# hanover-7320-20-01.net
KiCad netlist of a schematic drawn in EAGLE
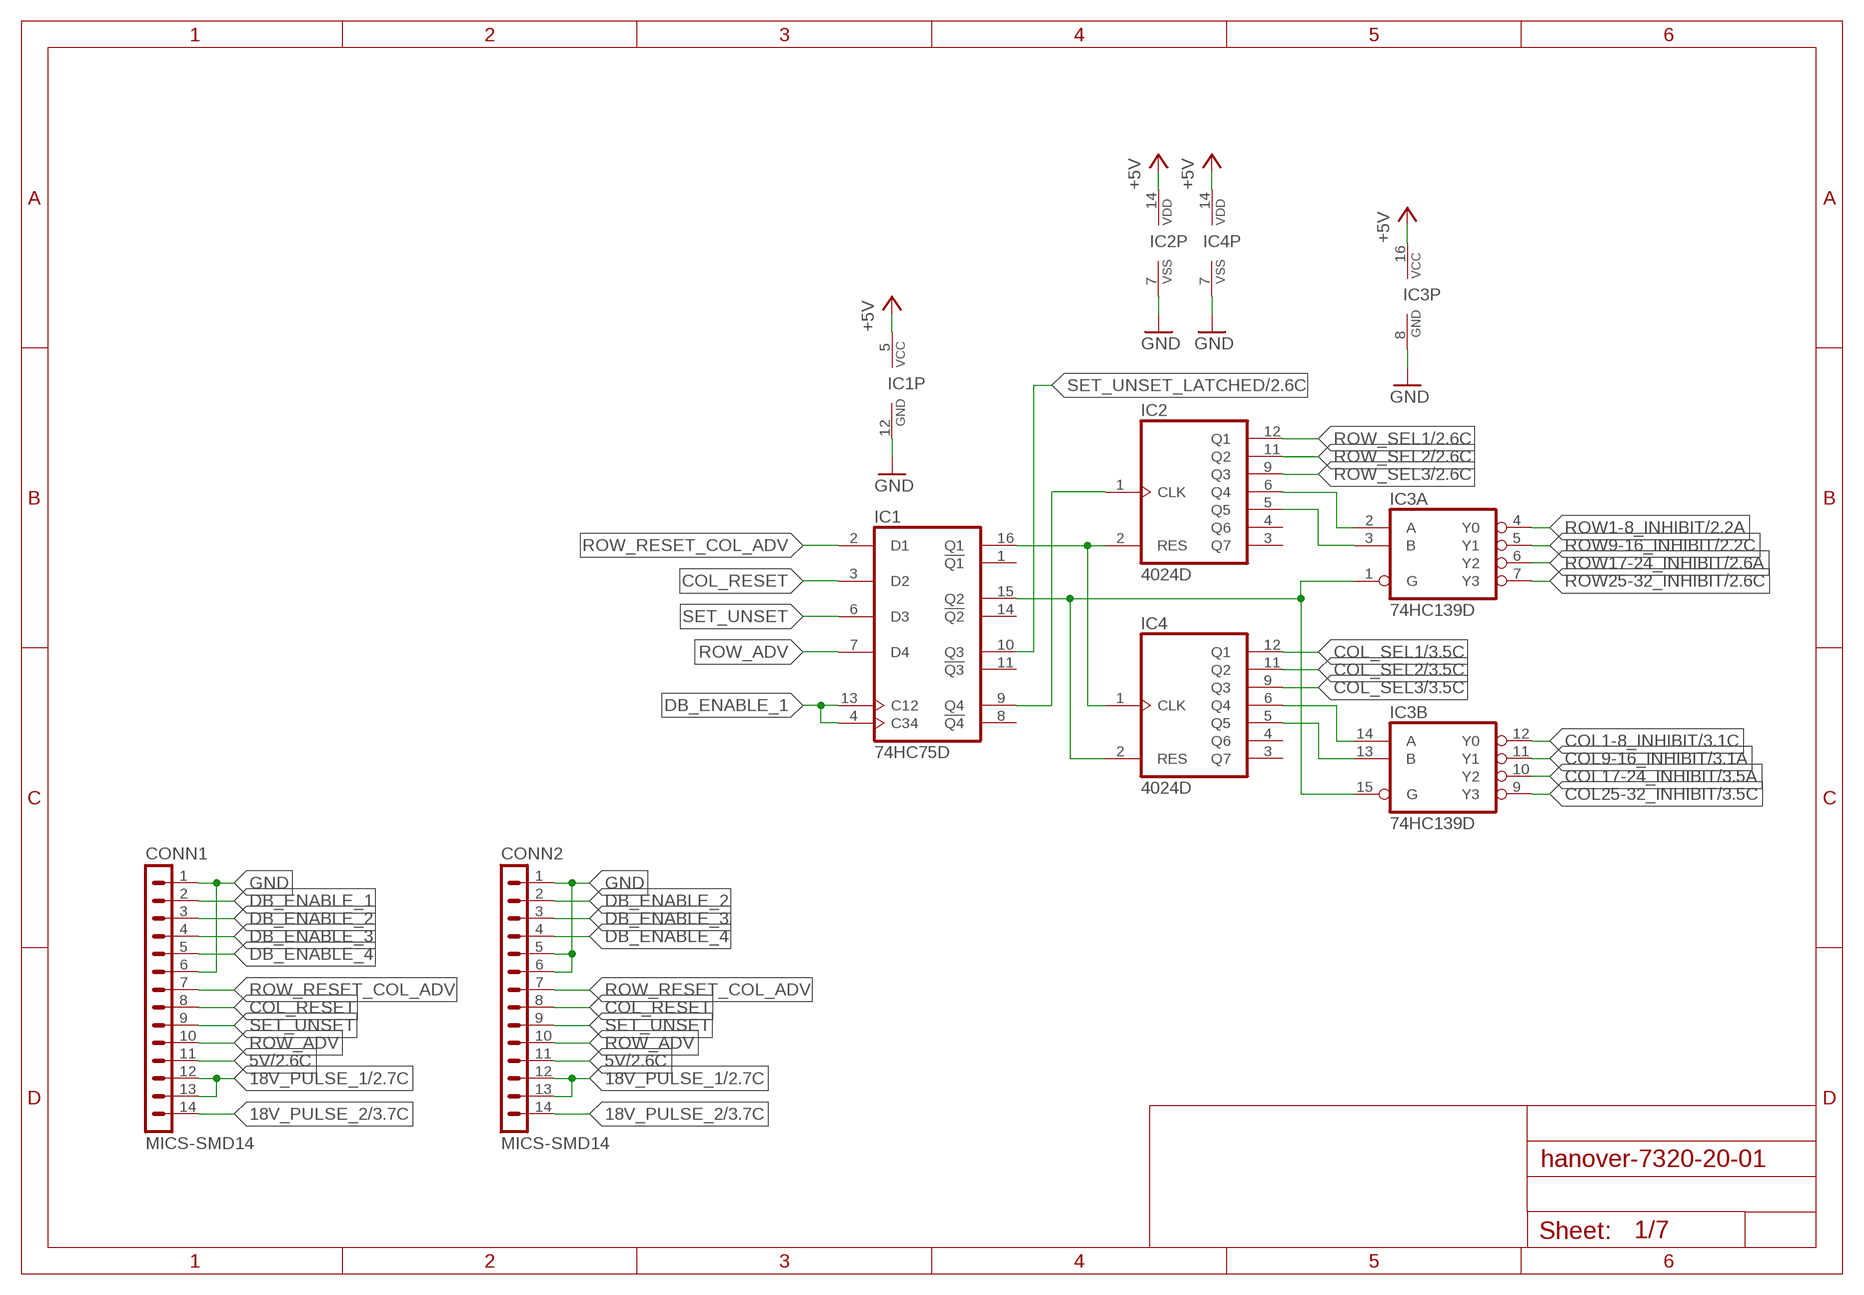
[diagram p0: schematic, sheet 1]
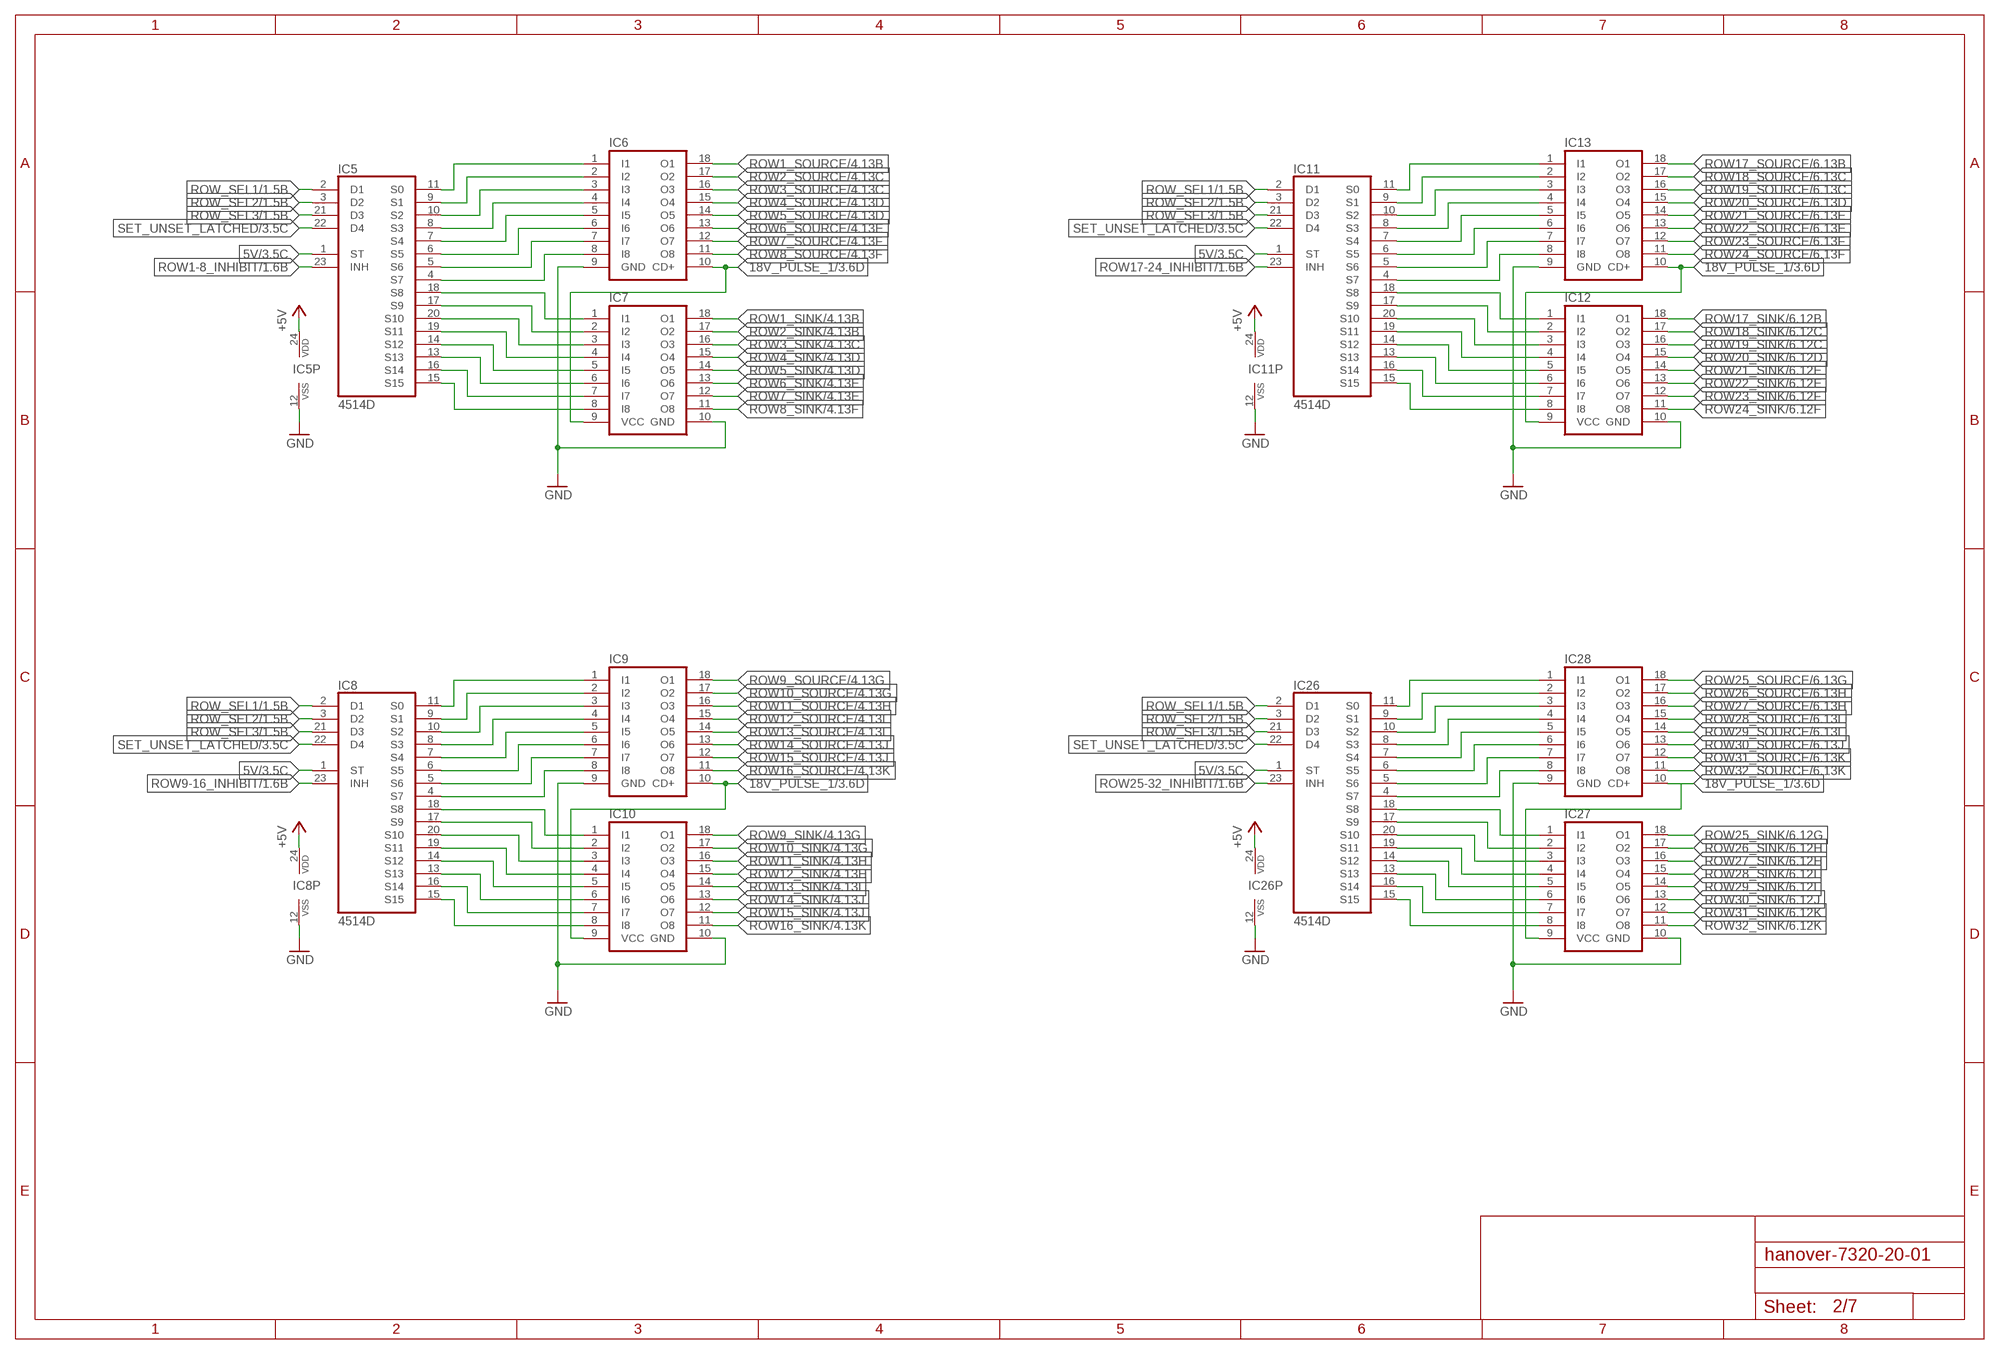
[diagram p1: schematic, sheet 2]
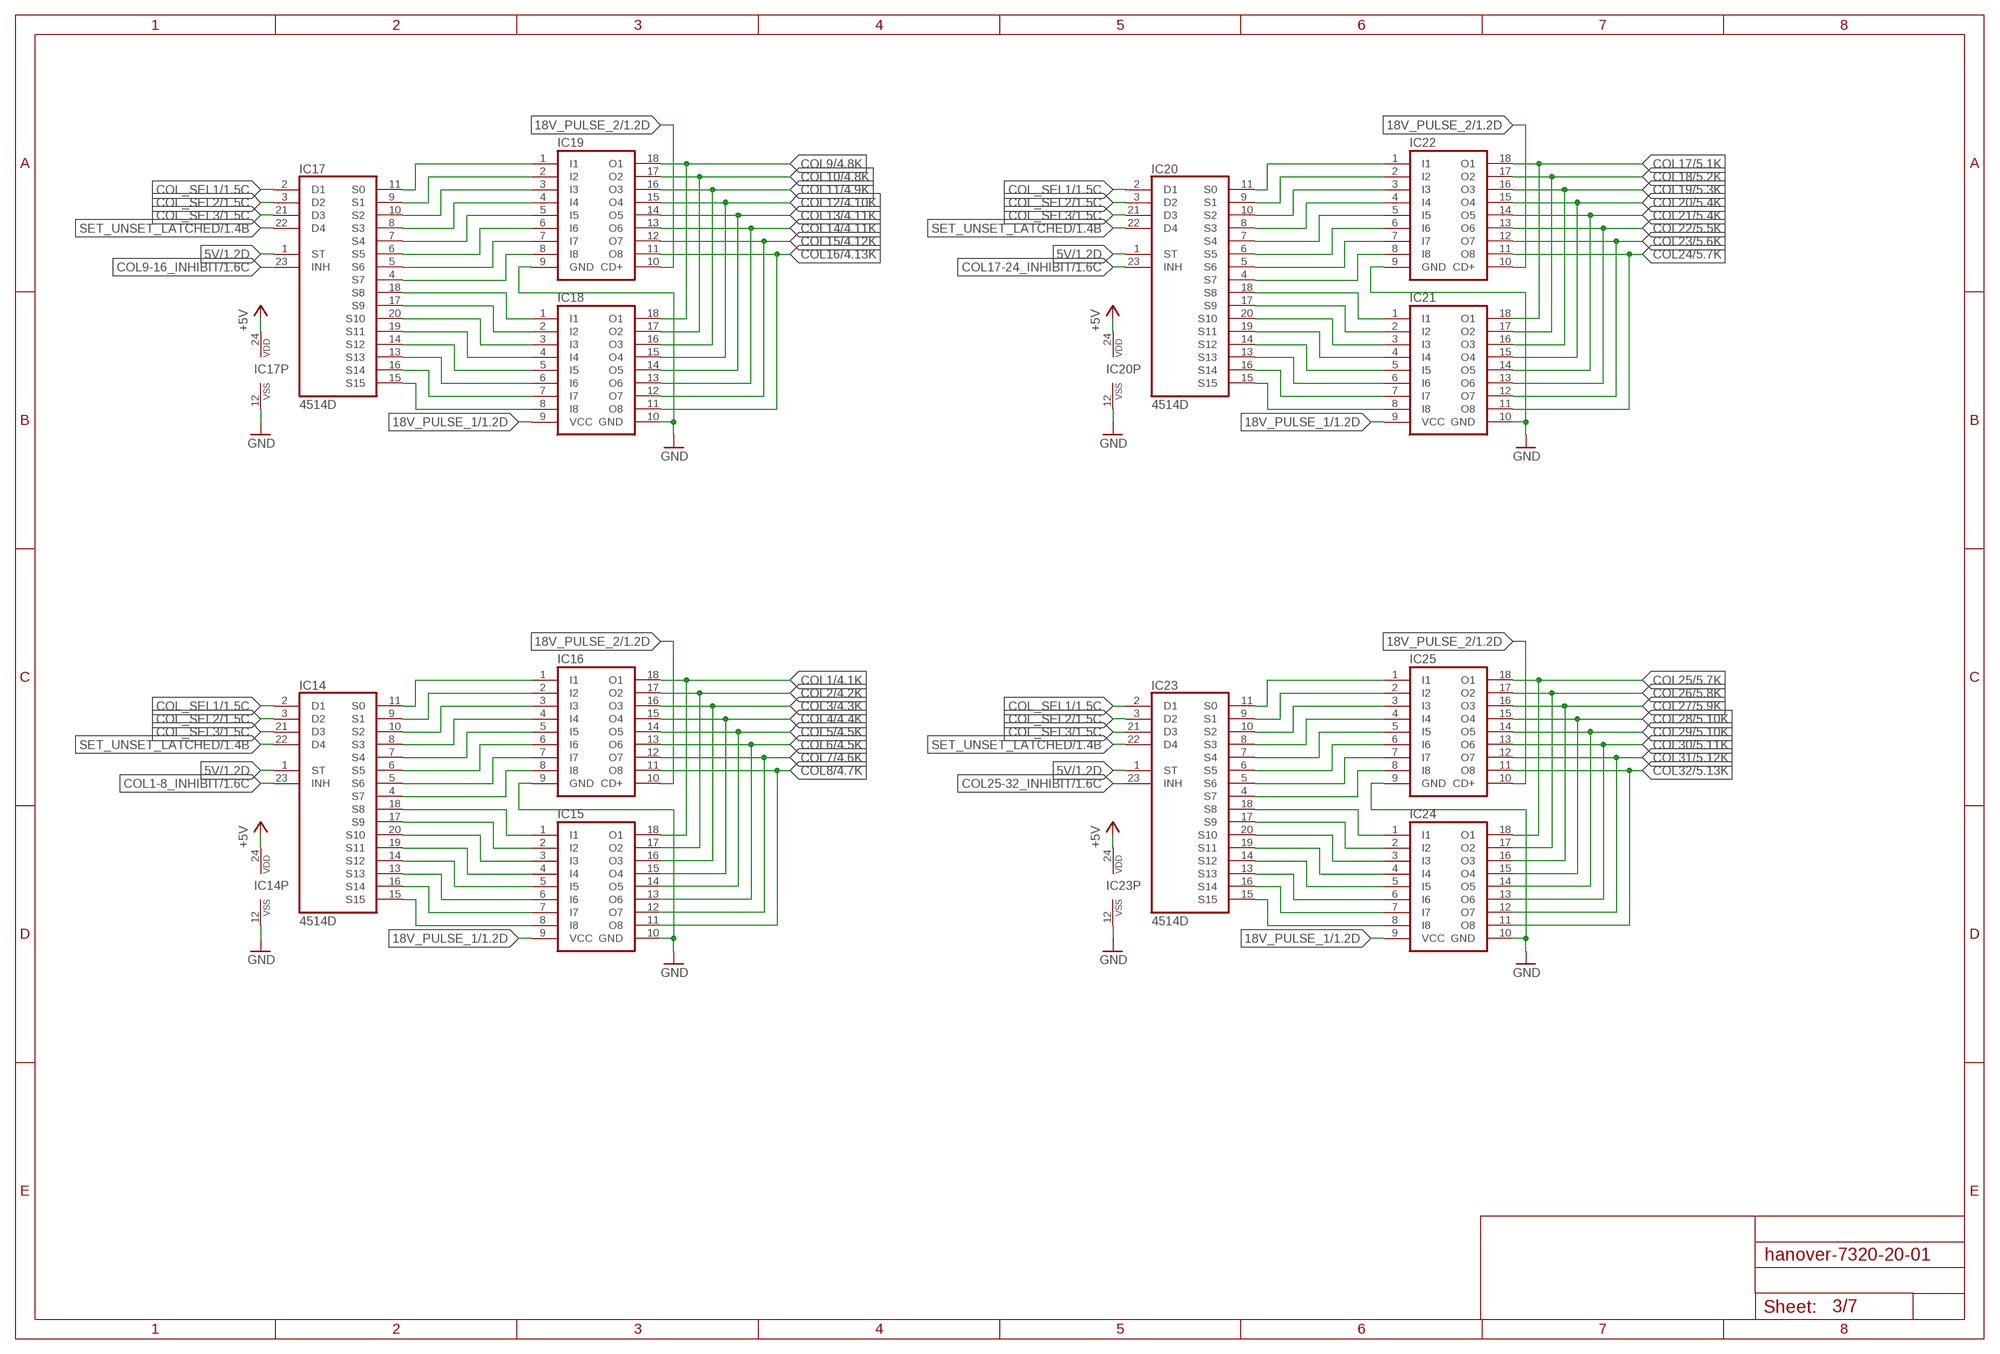
[diagram p2: schematic, sheet 3]
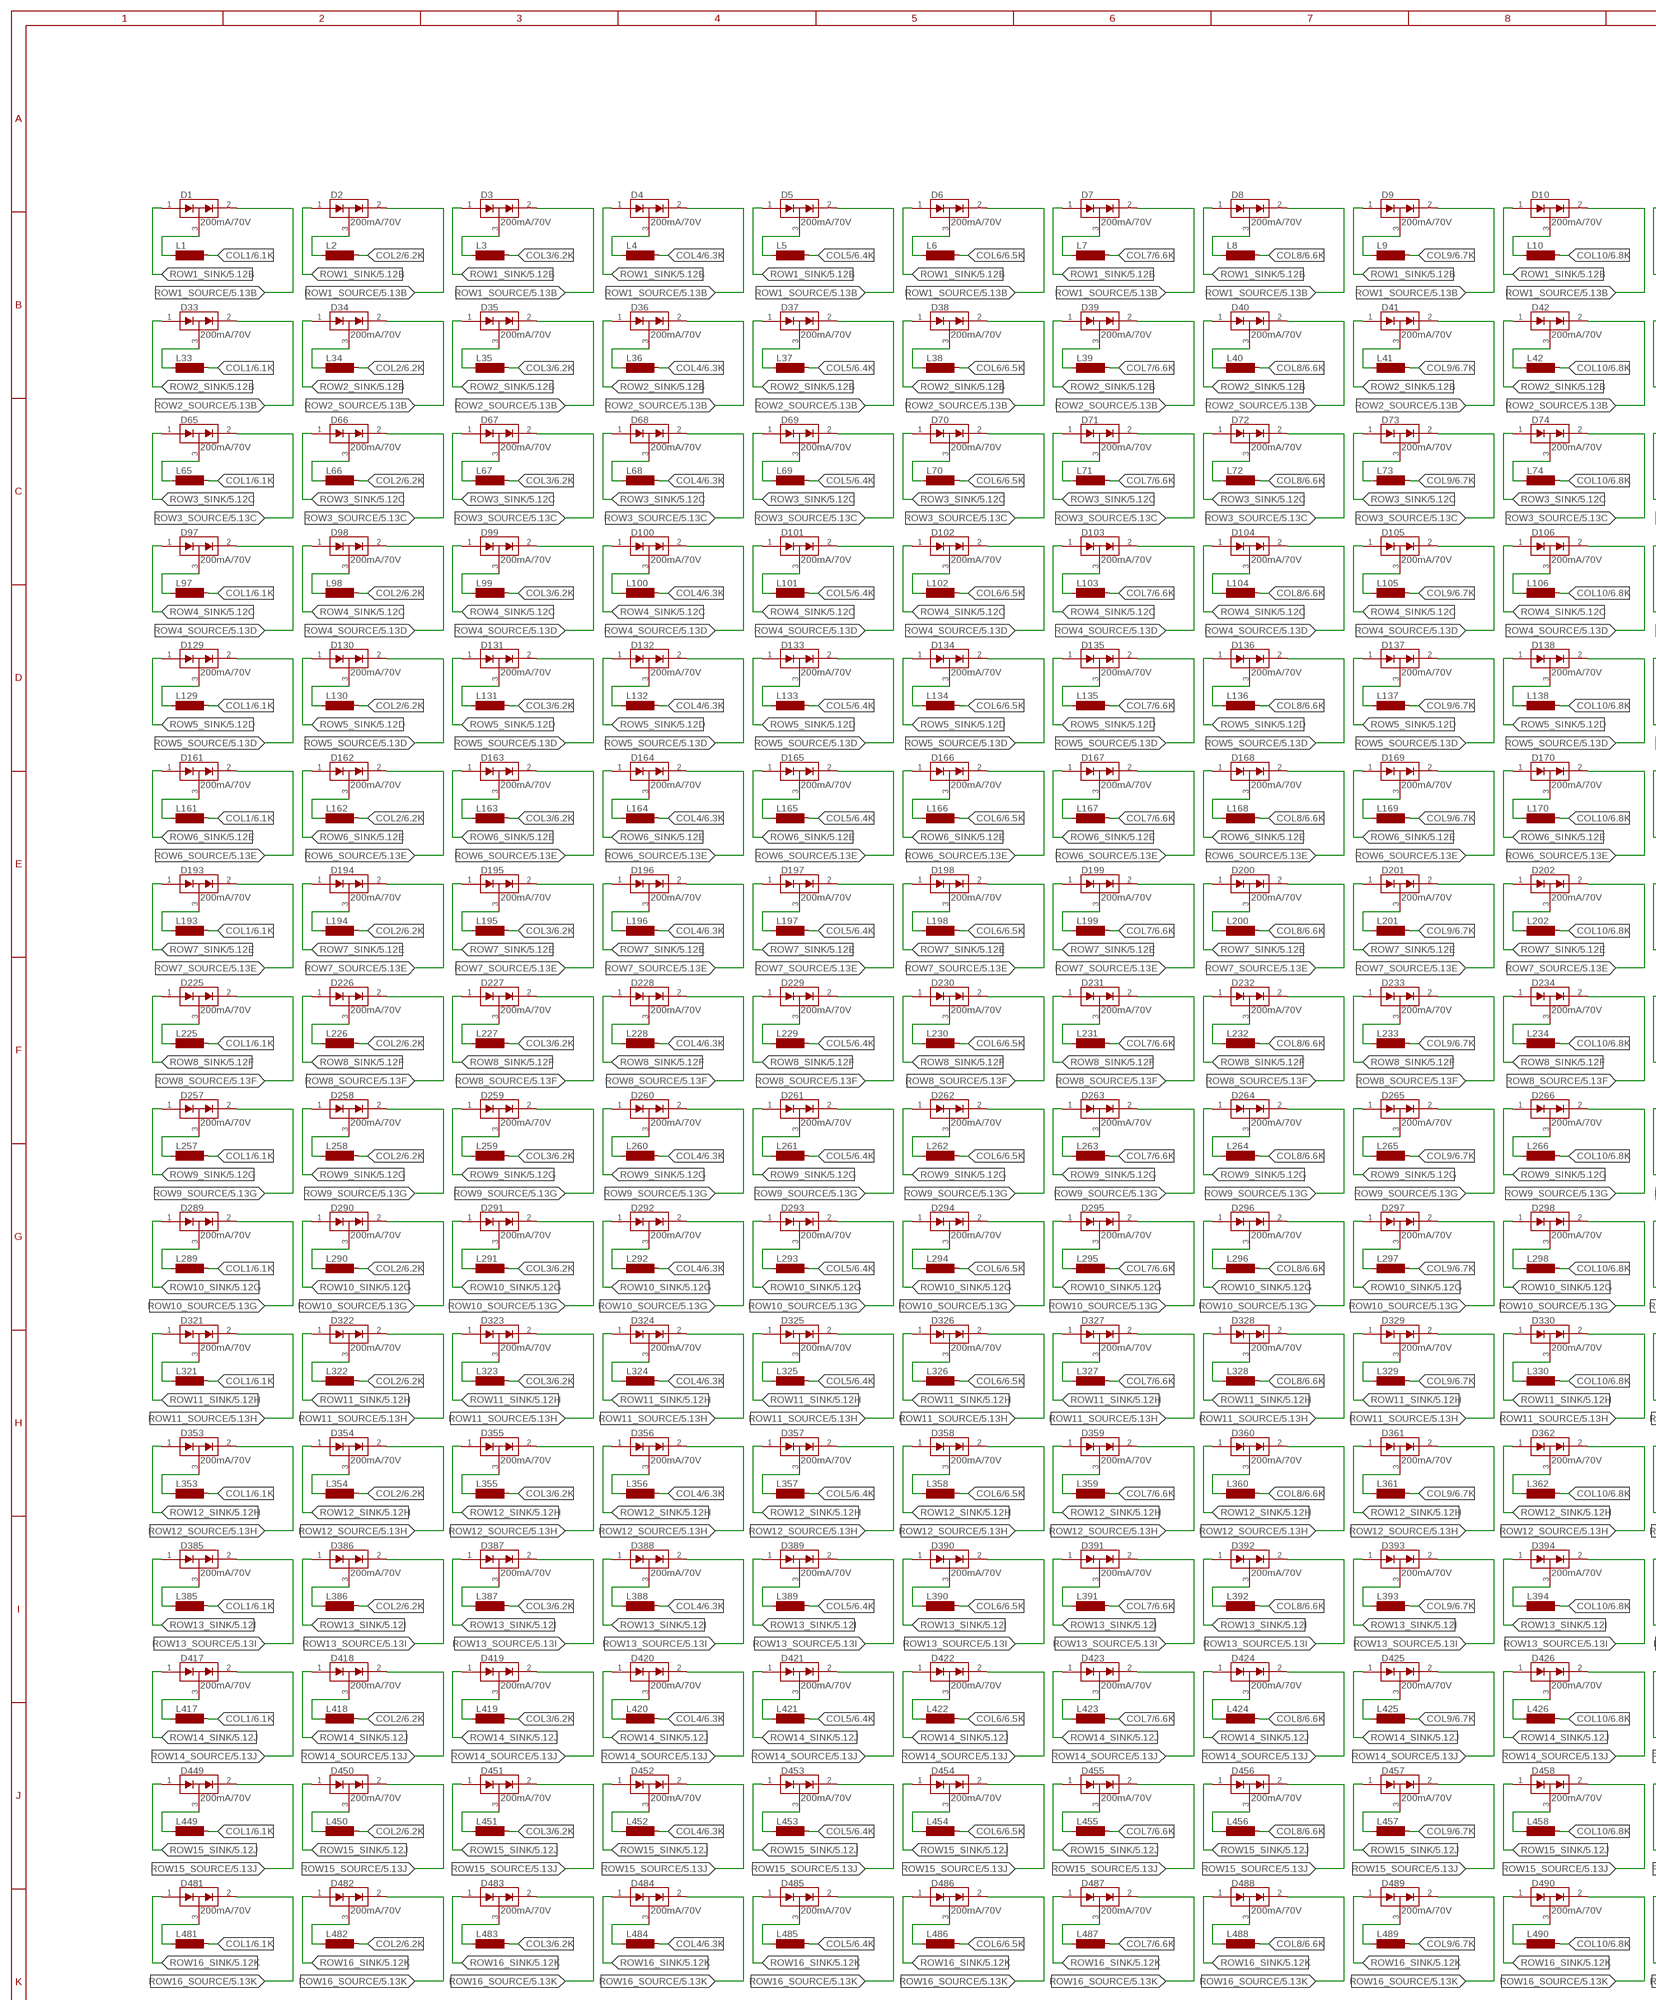
[diagram p3: schematic, sheet 4, part 1 of 3]
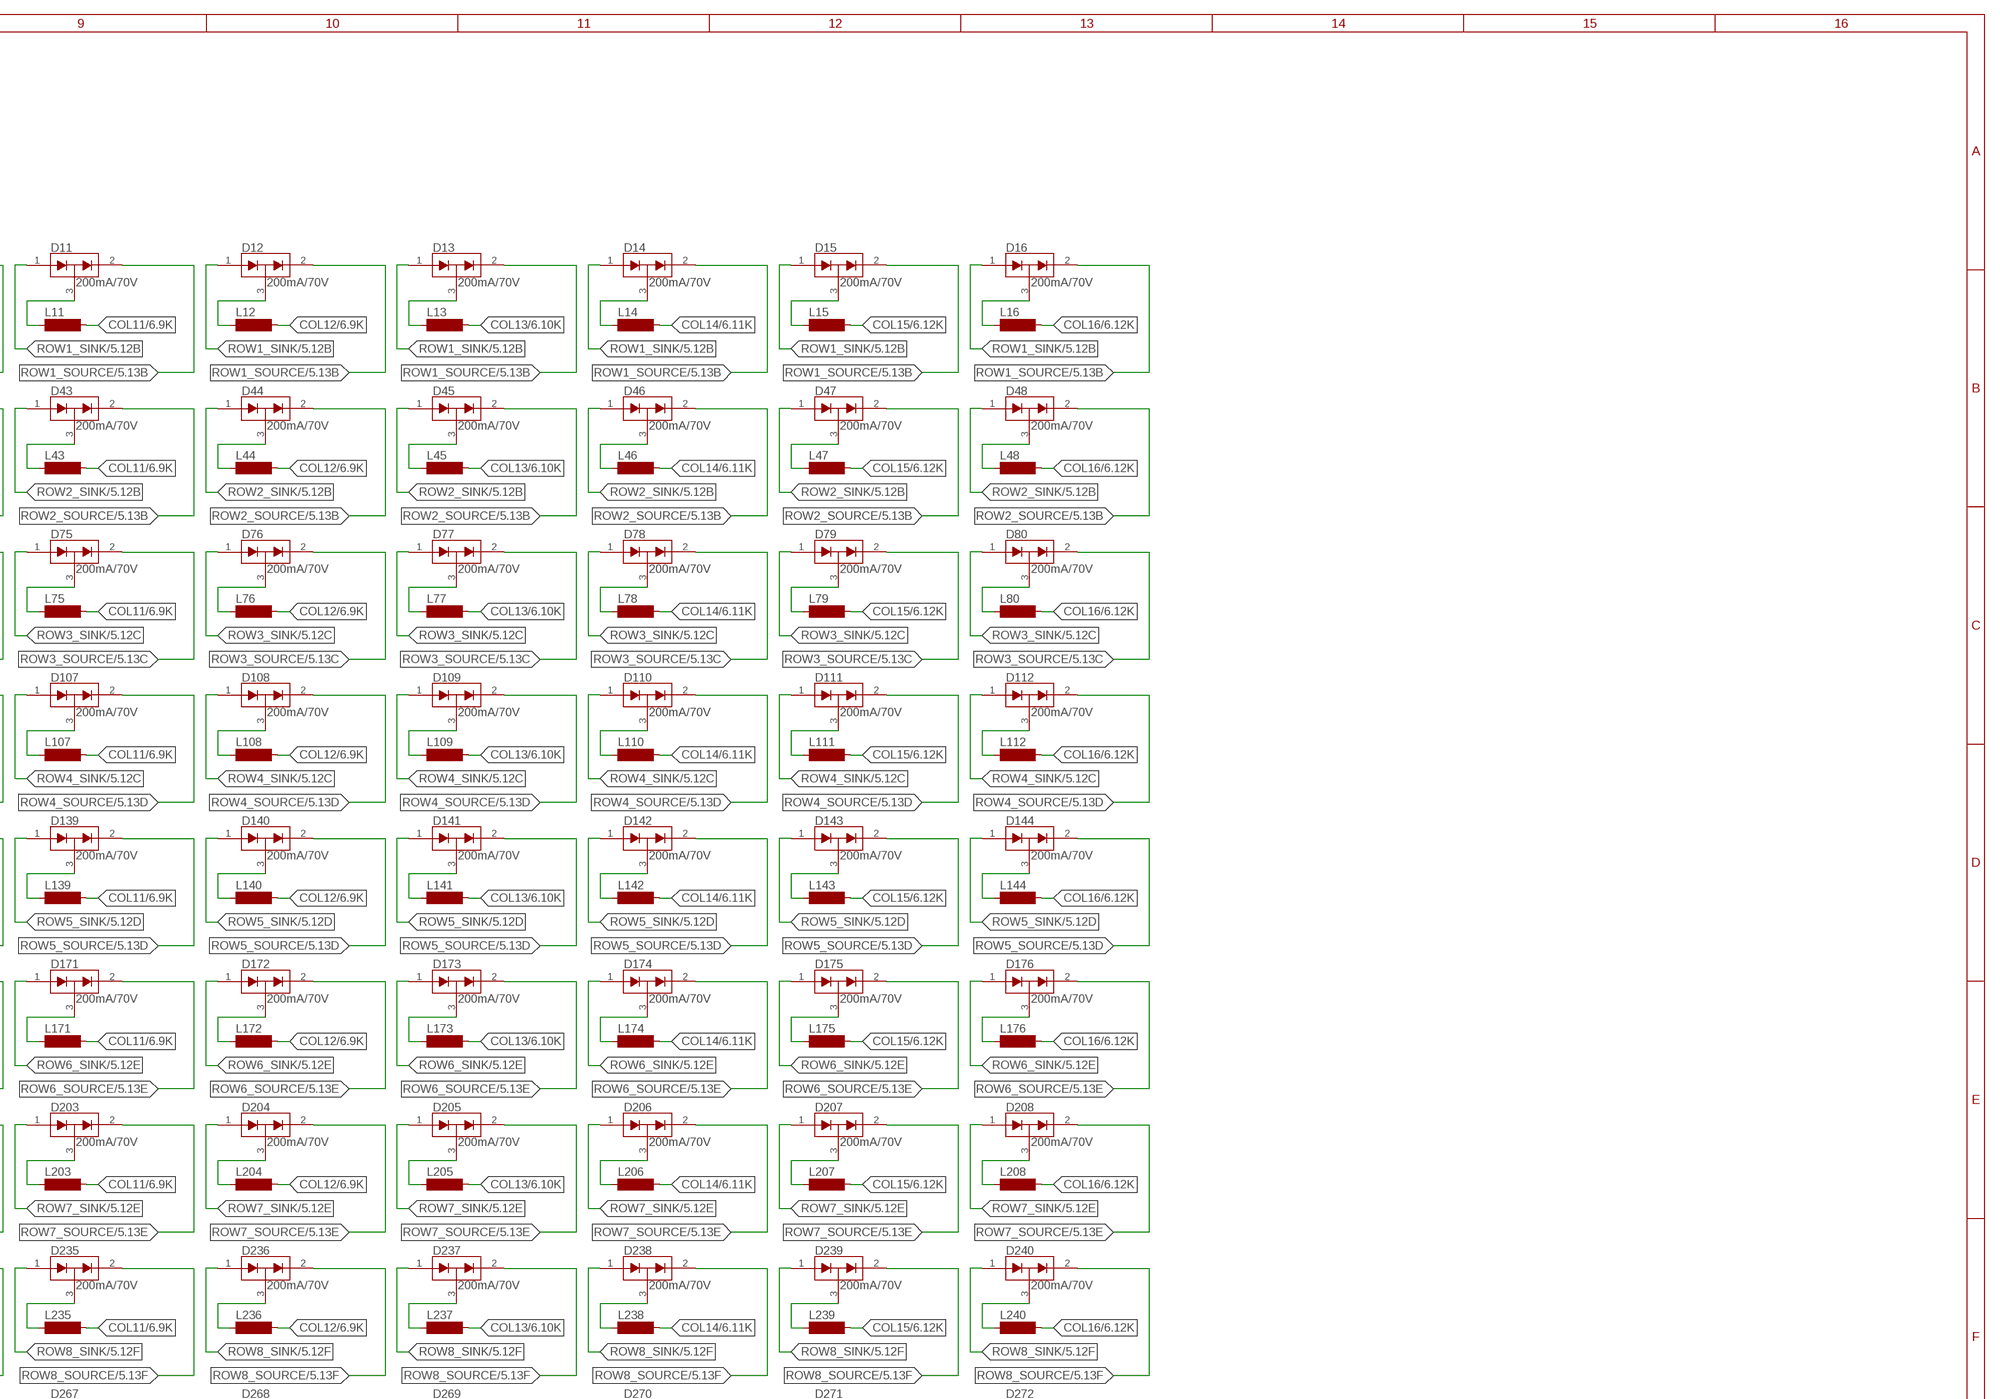
[diagram p4: schematic, sheet 4, part 2 of 3]
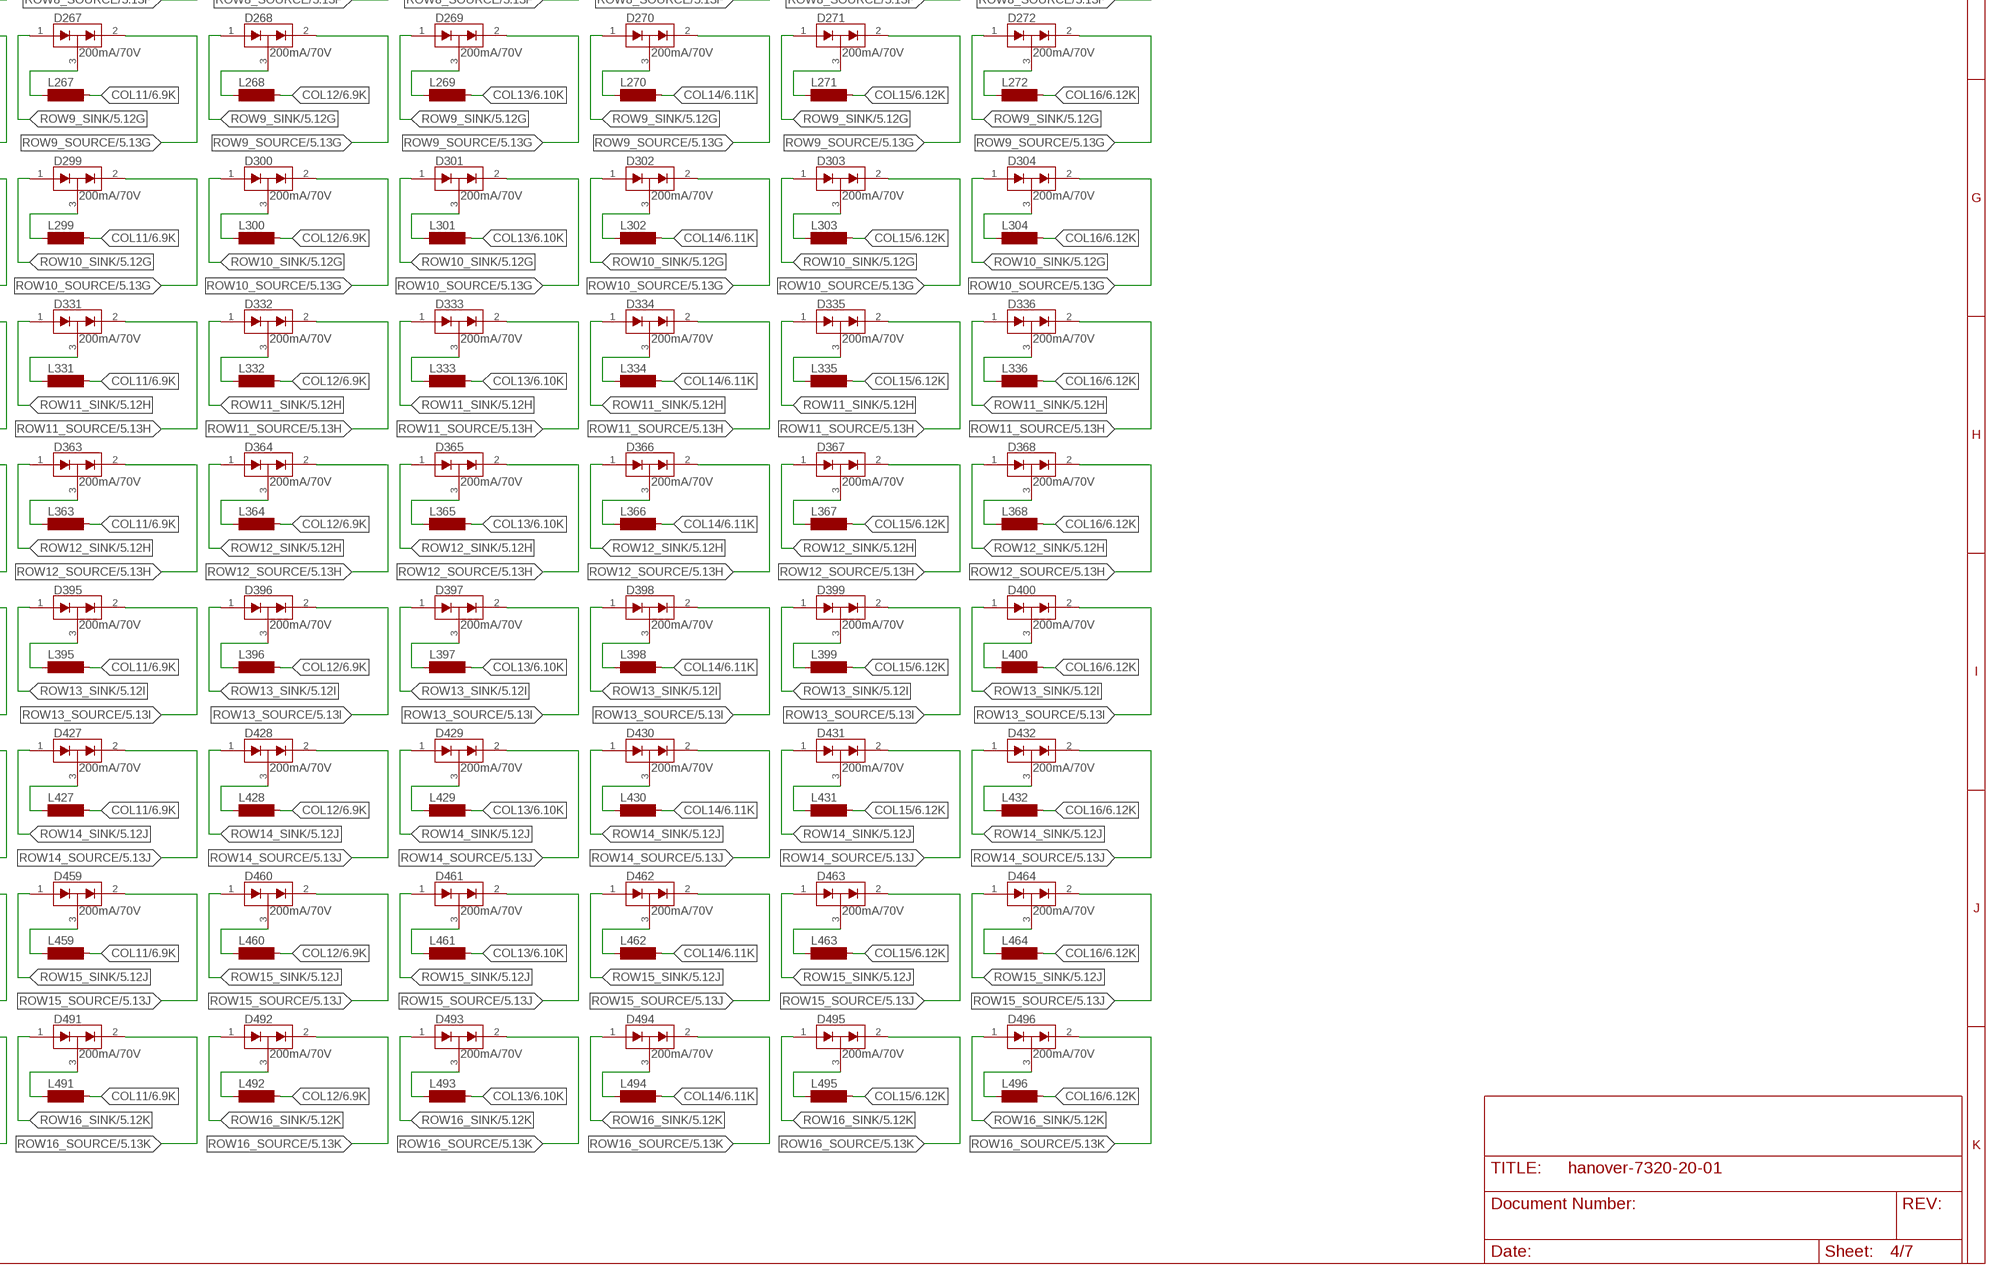
[diagram p5: schematic, sheet 4, part 3 of 3]
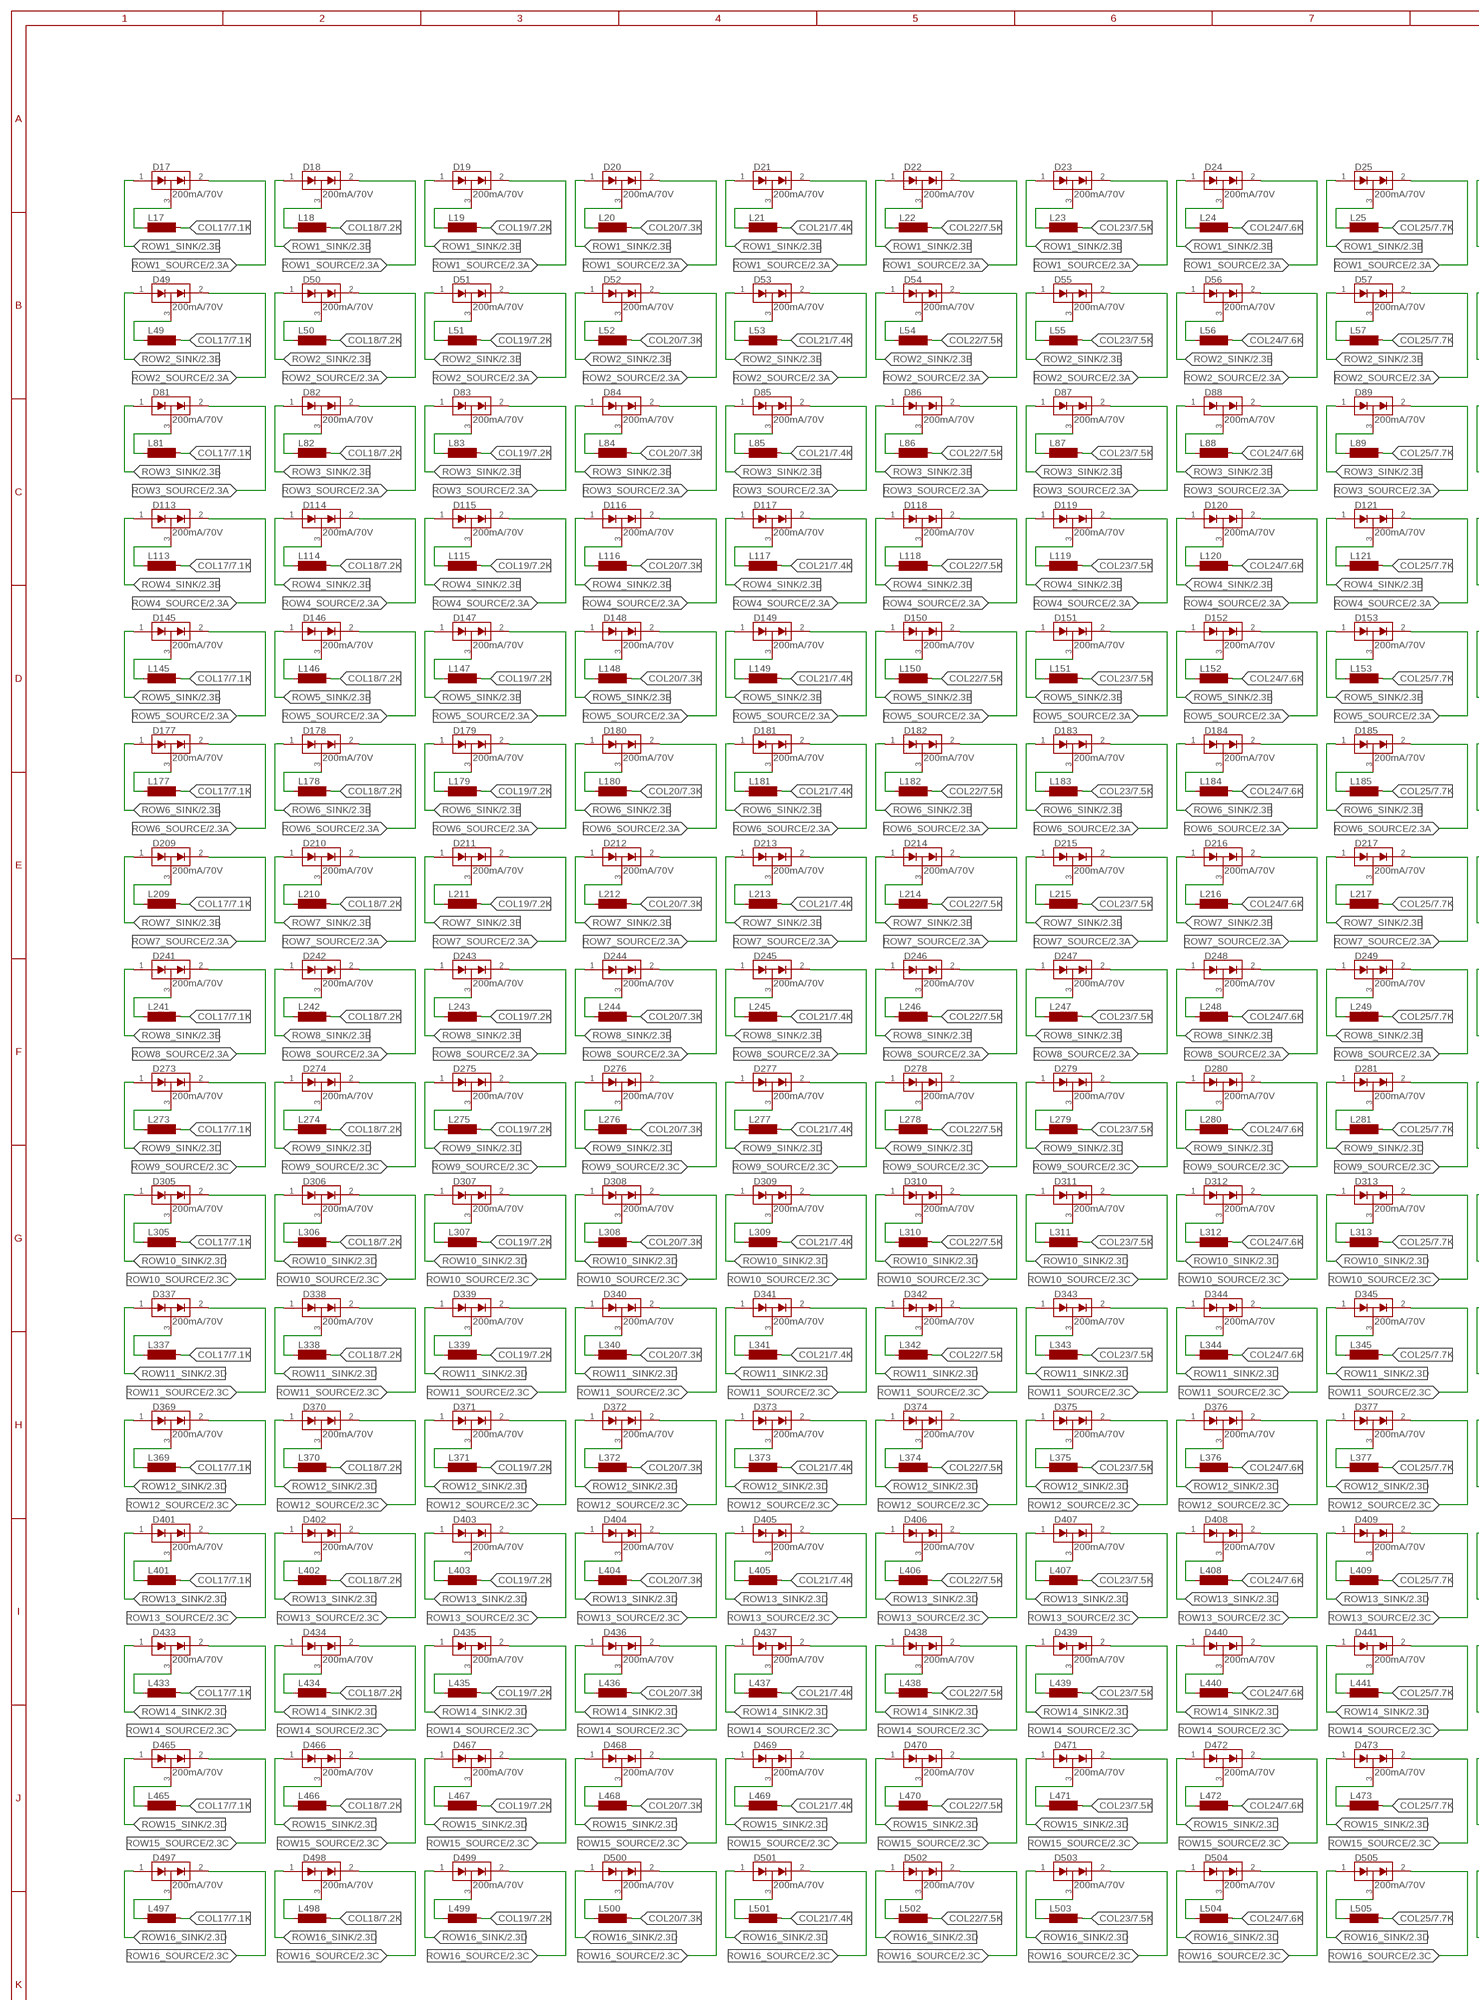
[diagram p6: schematic, sheet 5, part 1 of 3]
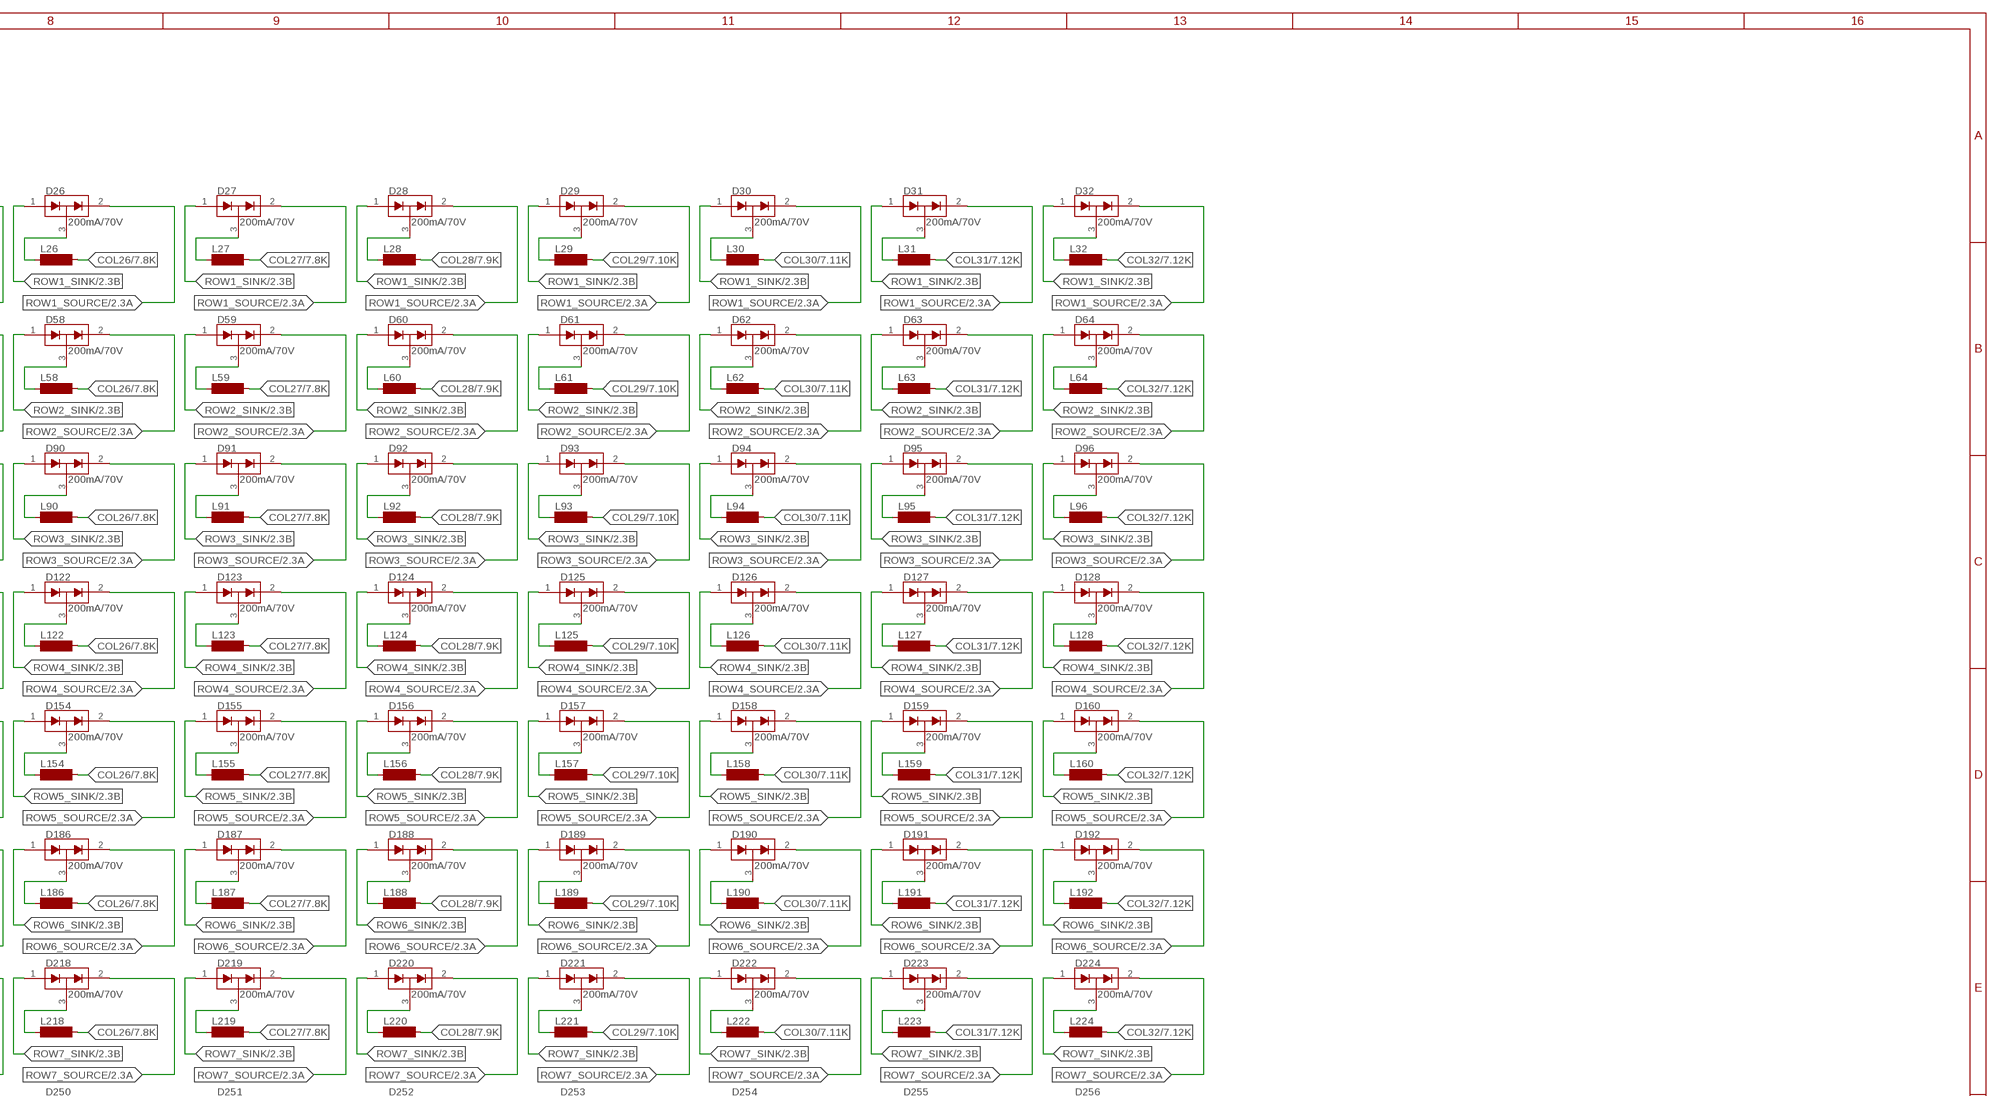
[diagram p7: schematic, sheet 5, part 2 of 3]
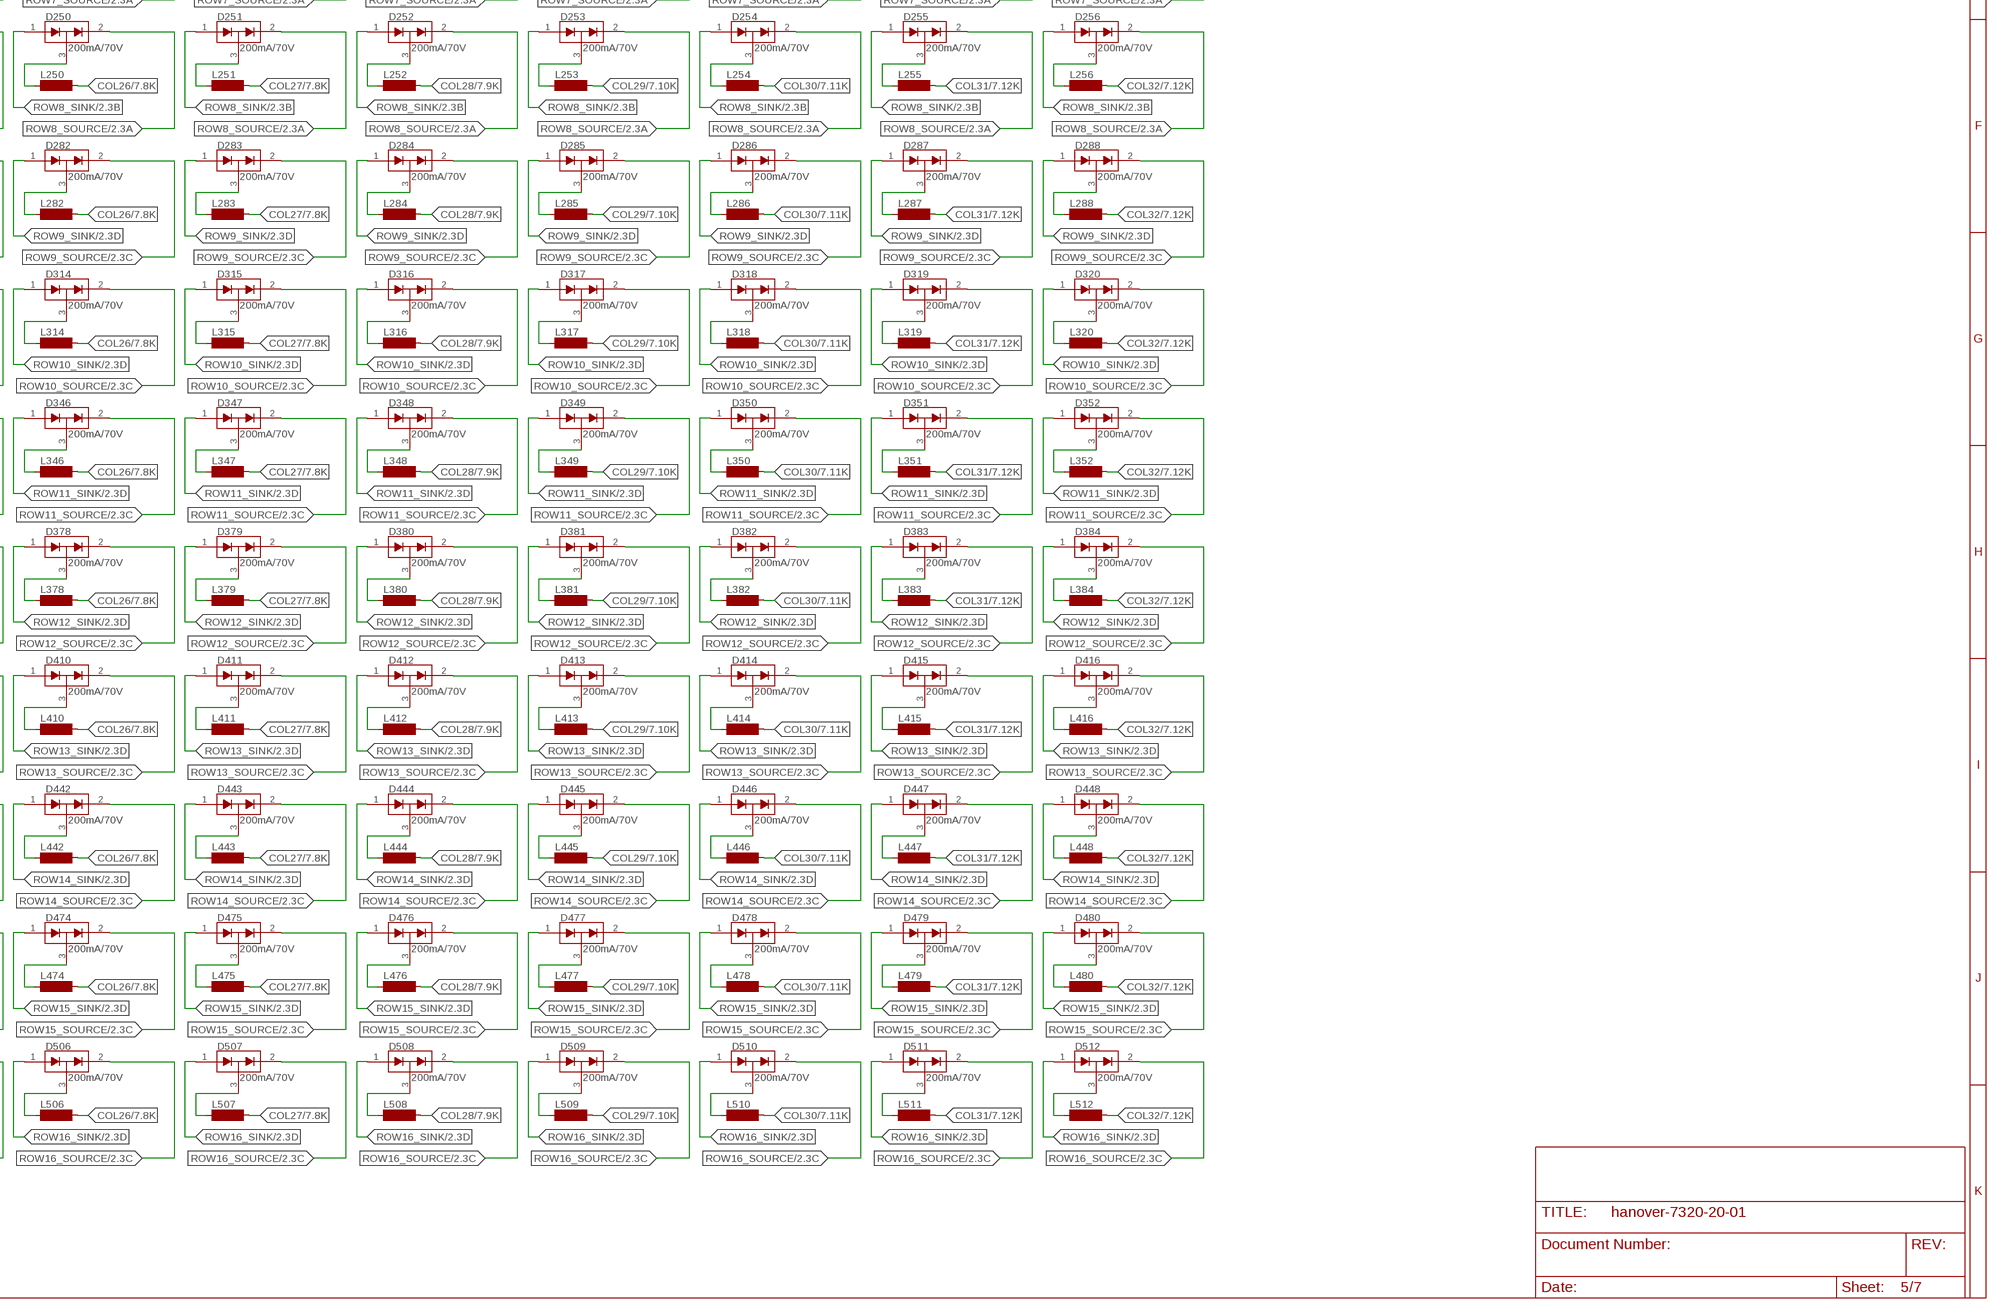
[diagram p8: schematic, sheet 5, part 3 of 3]
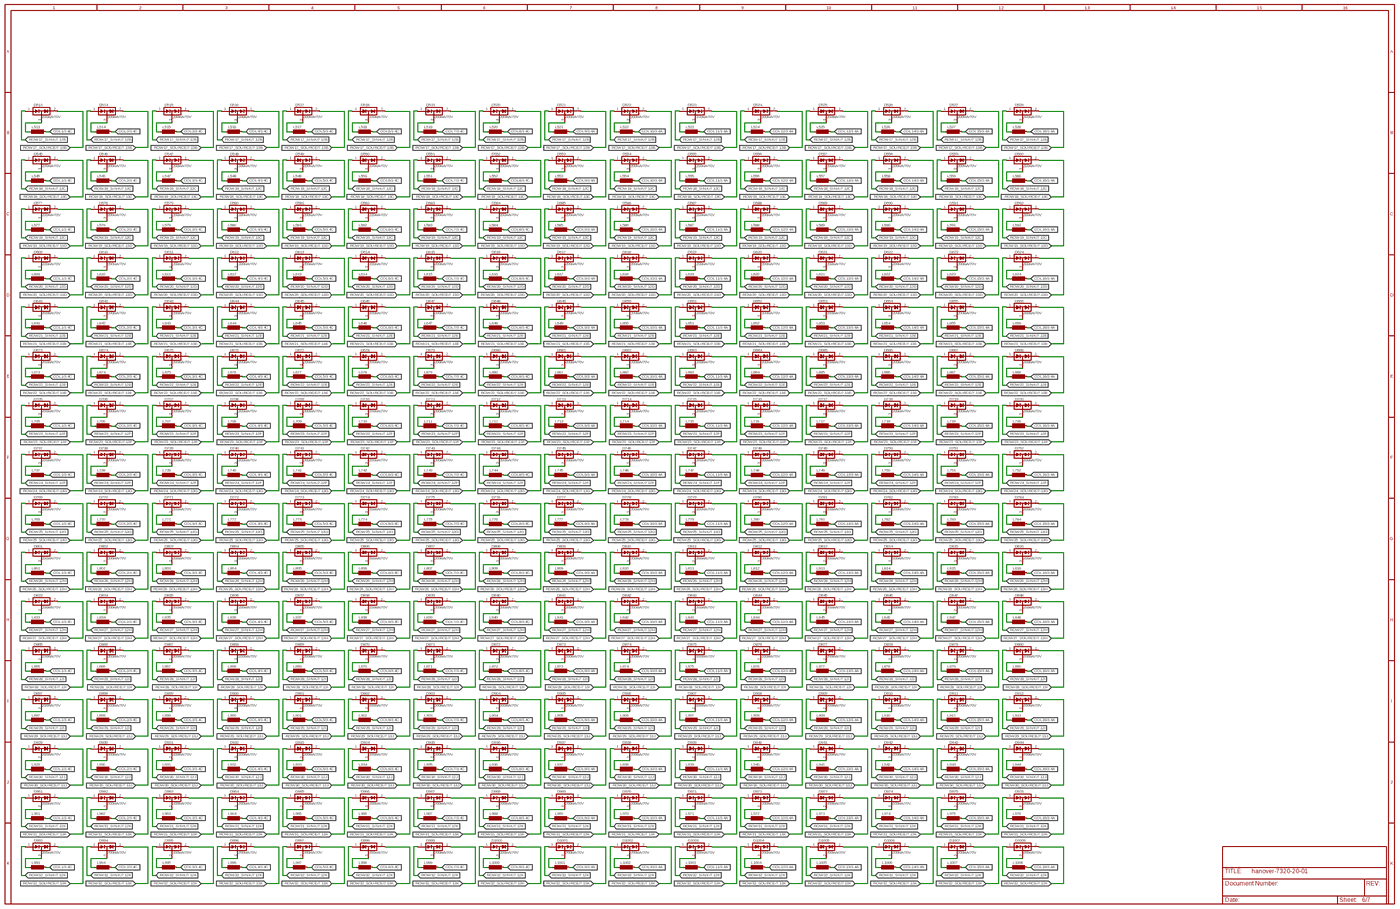
[diagram p9: schematic, sheet 6, overview]
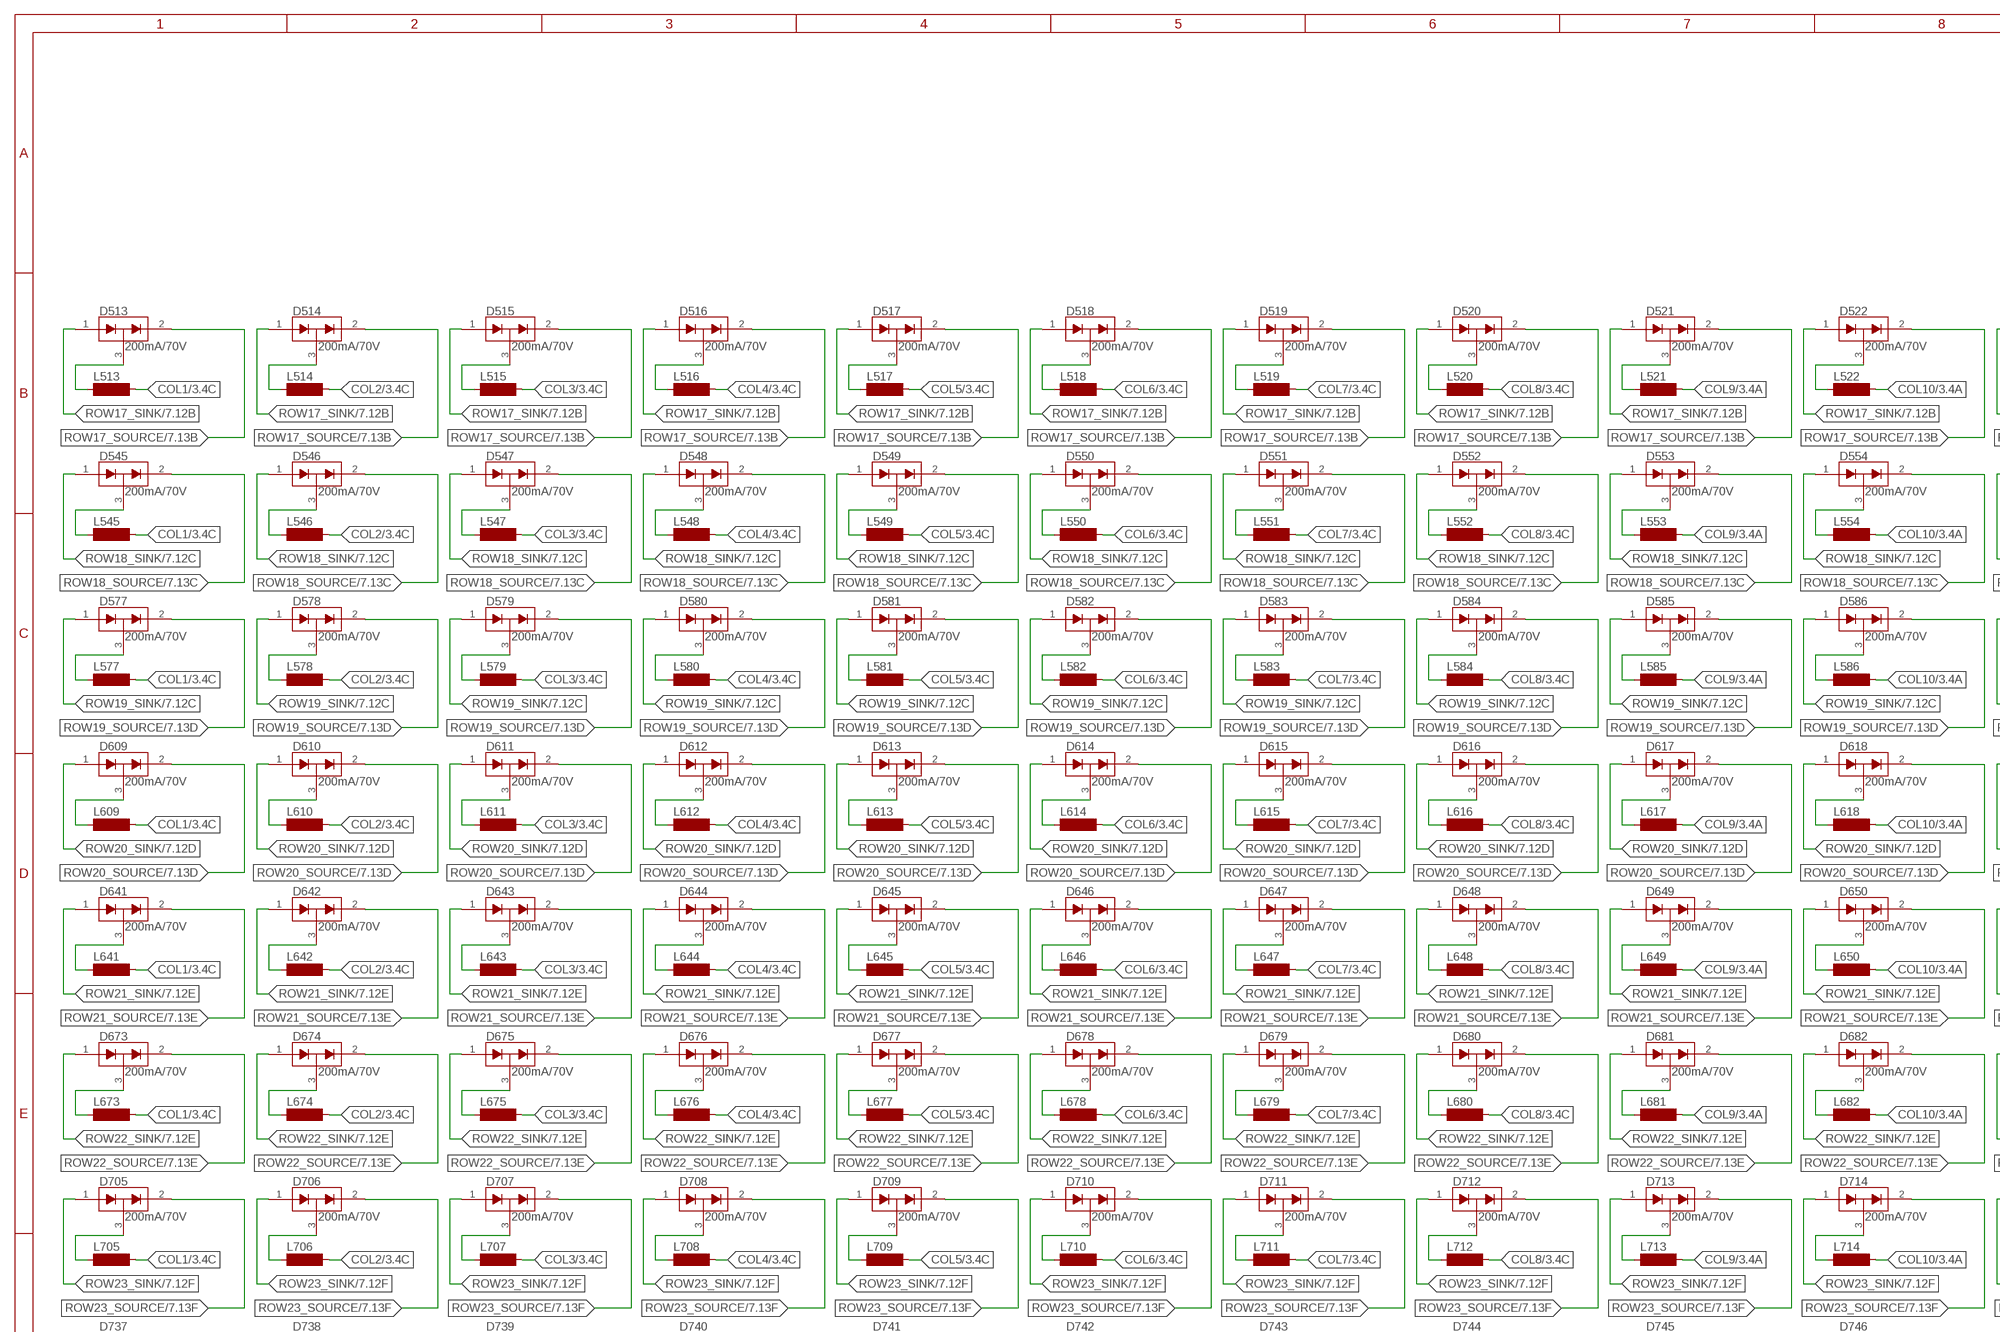
[diagram p10: schematic, sheet 6, part 1 of 4]
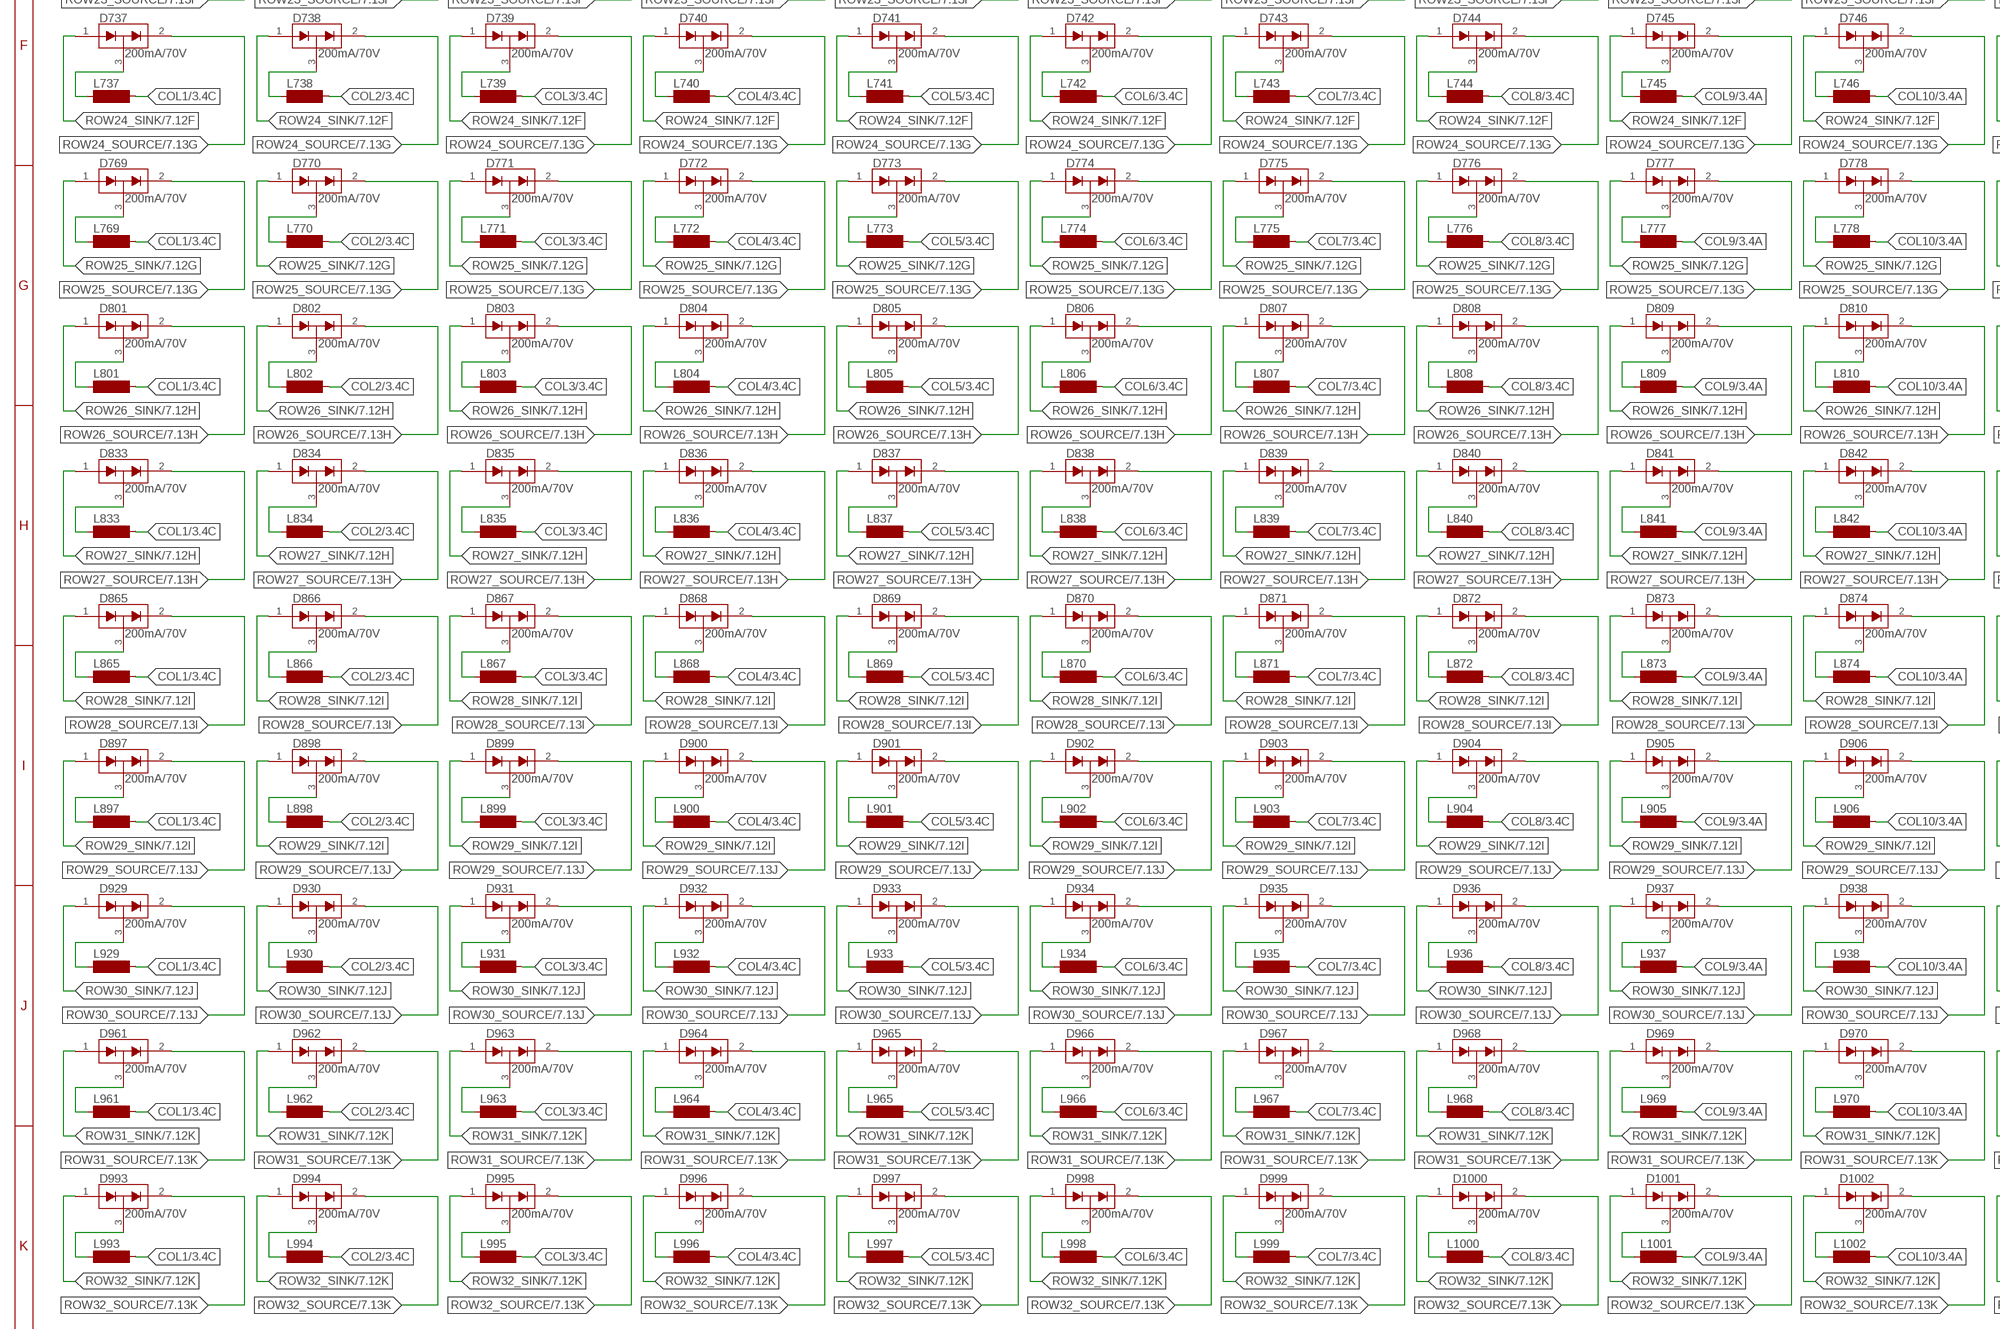
[diagram p11: schematic, sheet 6, part 2 of 4]
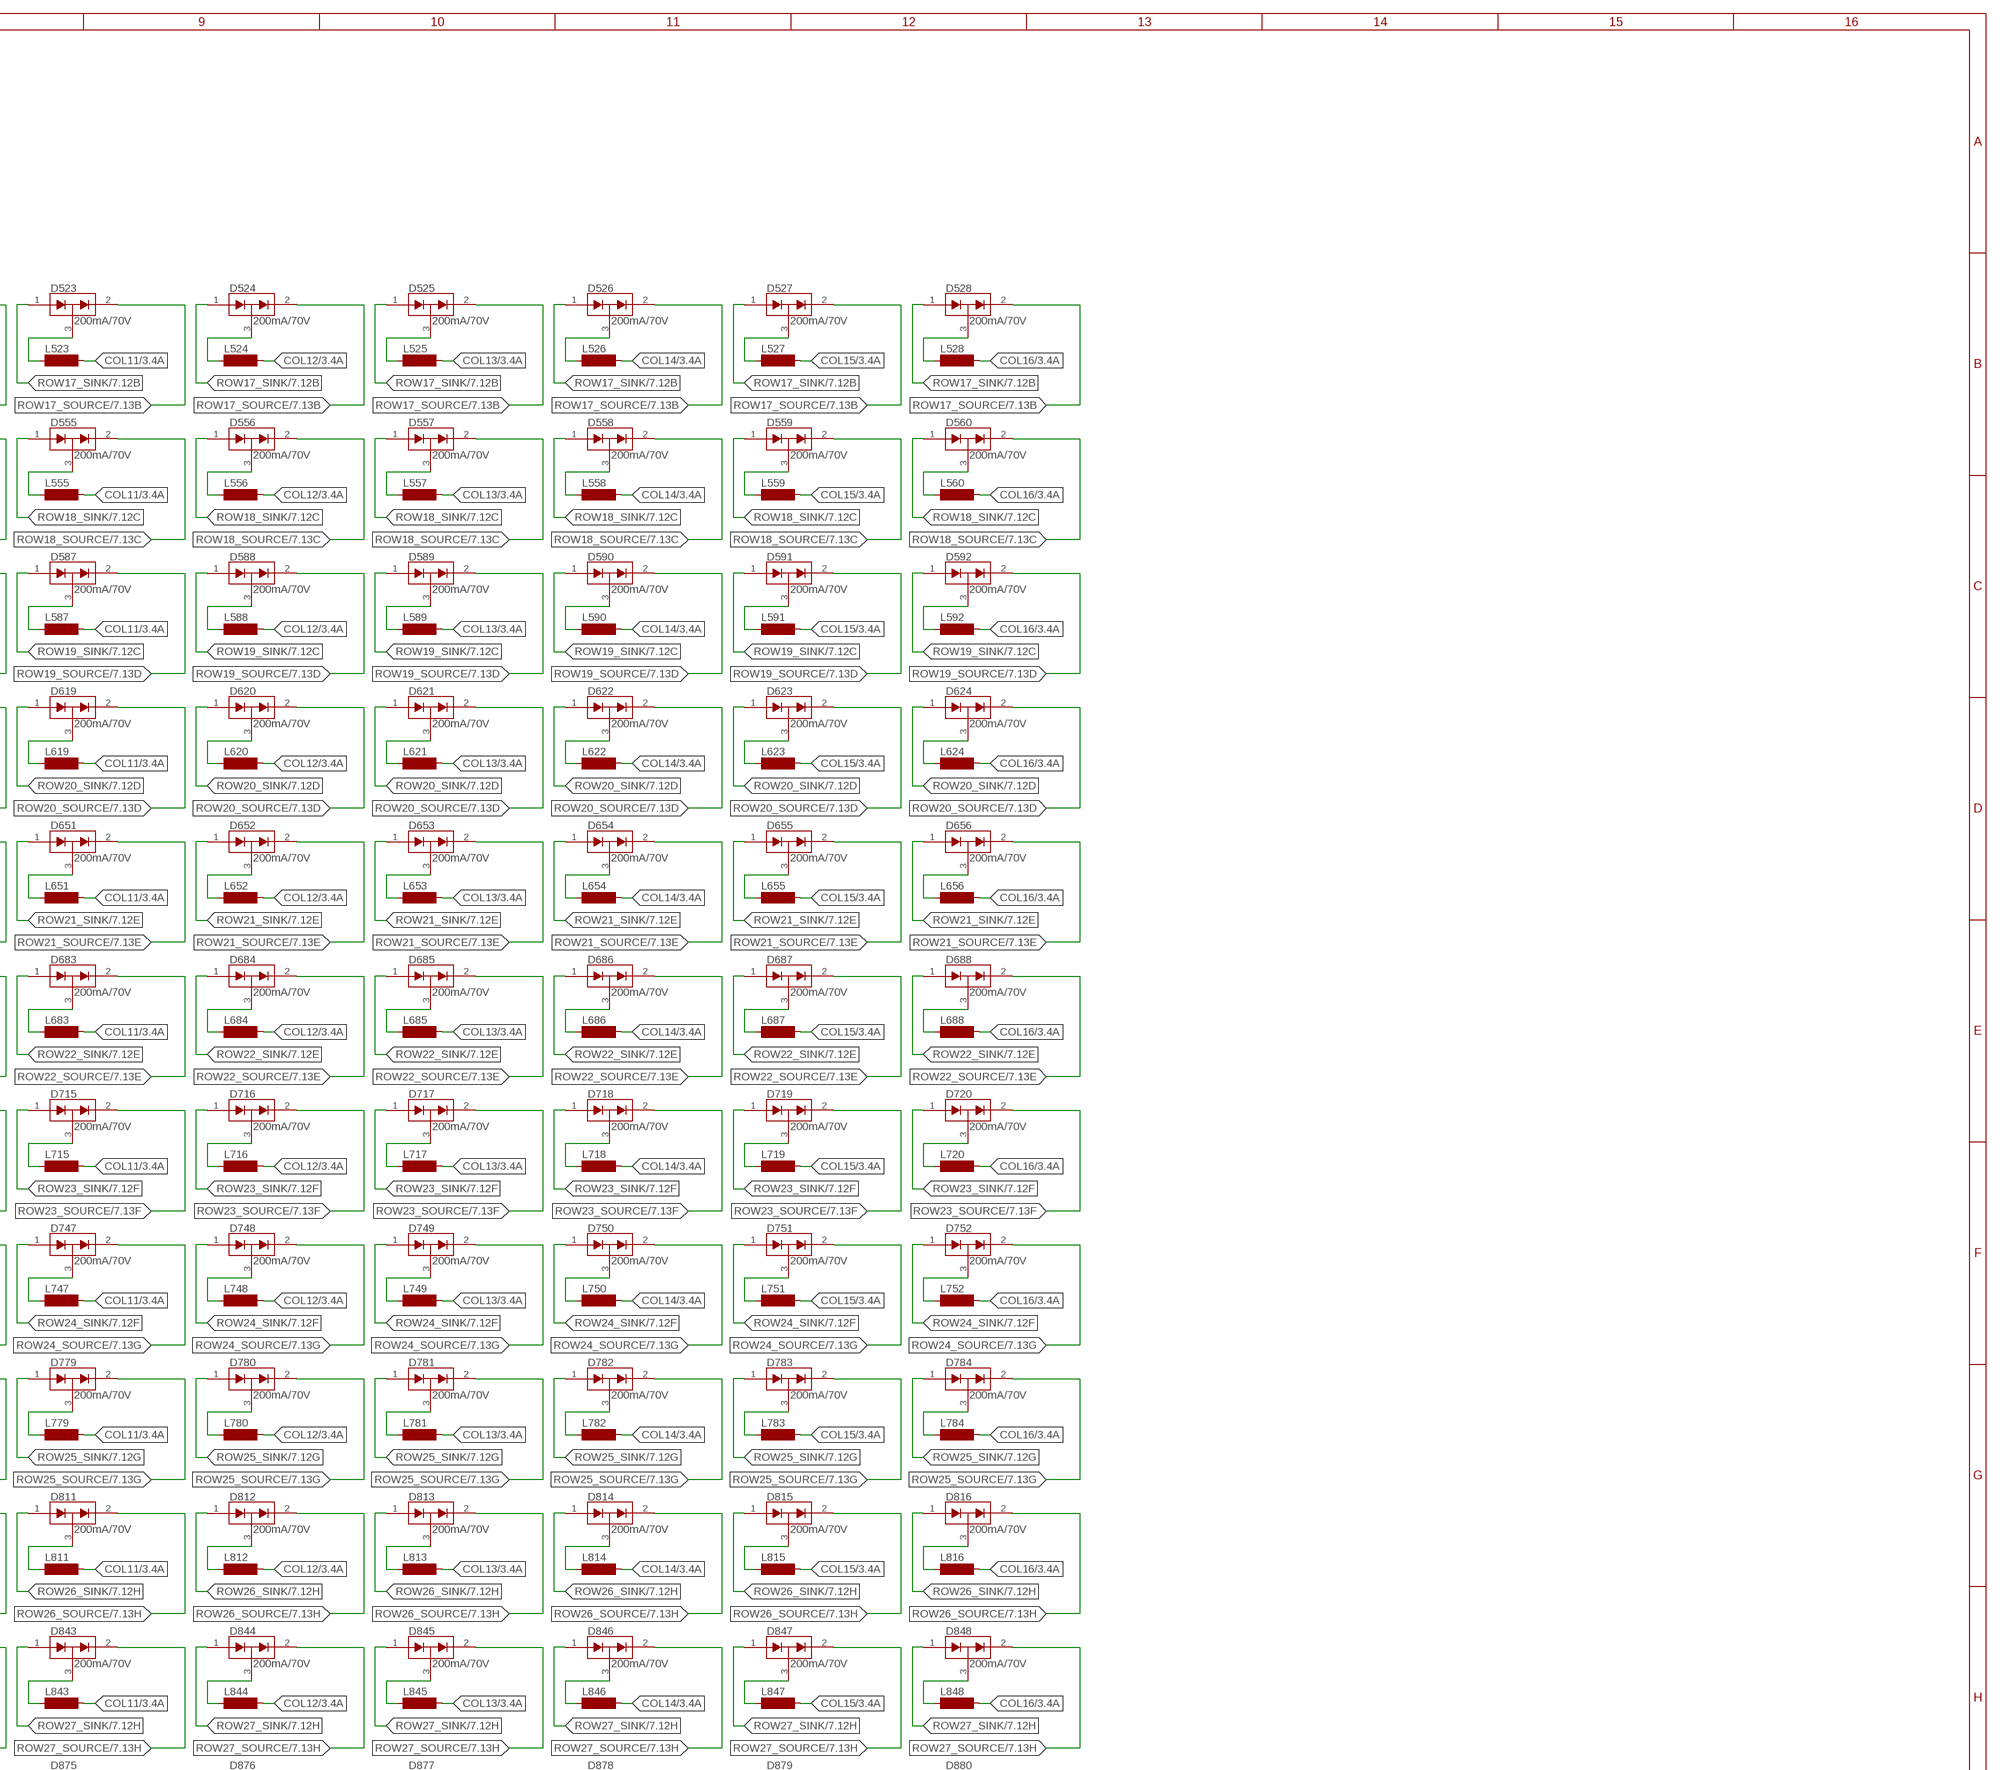
[diagram p12: schematic, sheet 6, part 3 of 4]
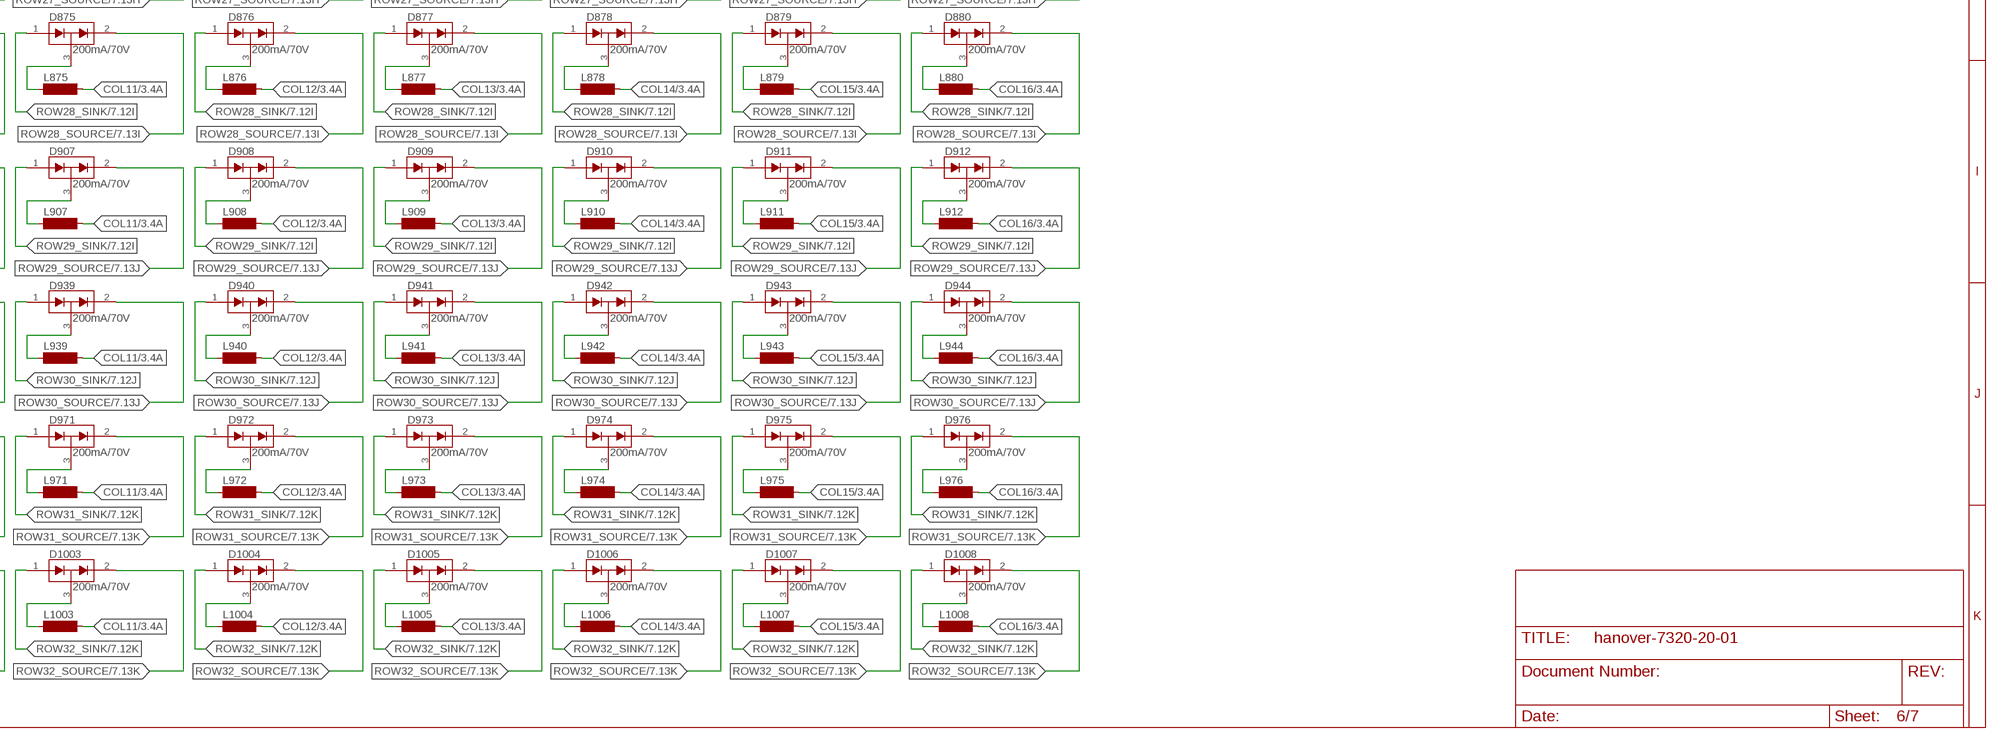
[diagram p13: schematic, sheet 6, part 4 of 4]
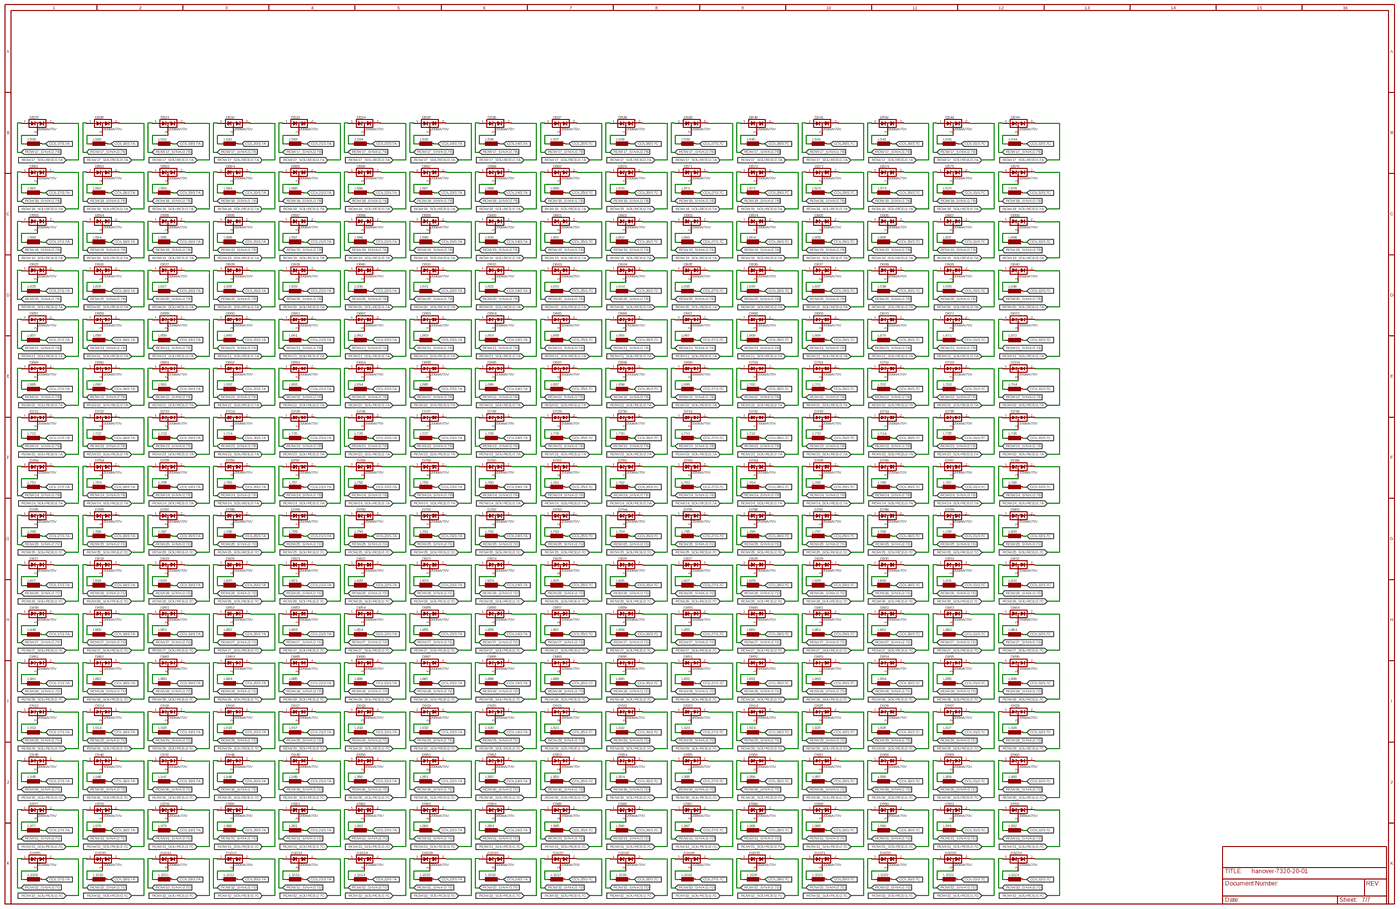
[diagram p14: schematic, sheet 7, overview]
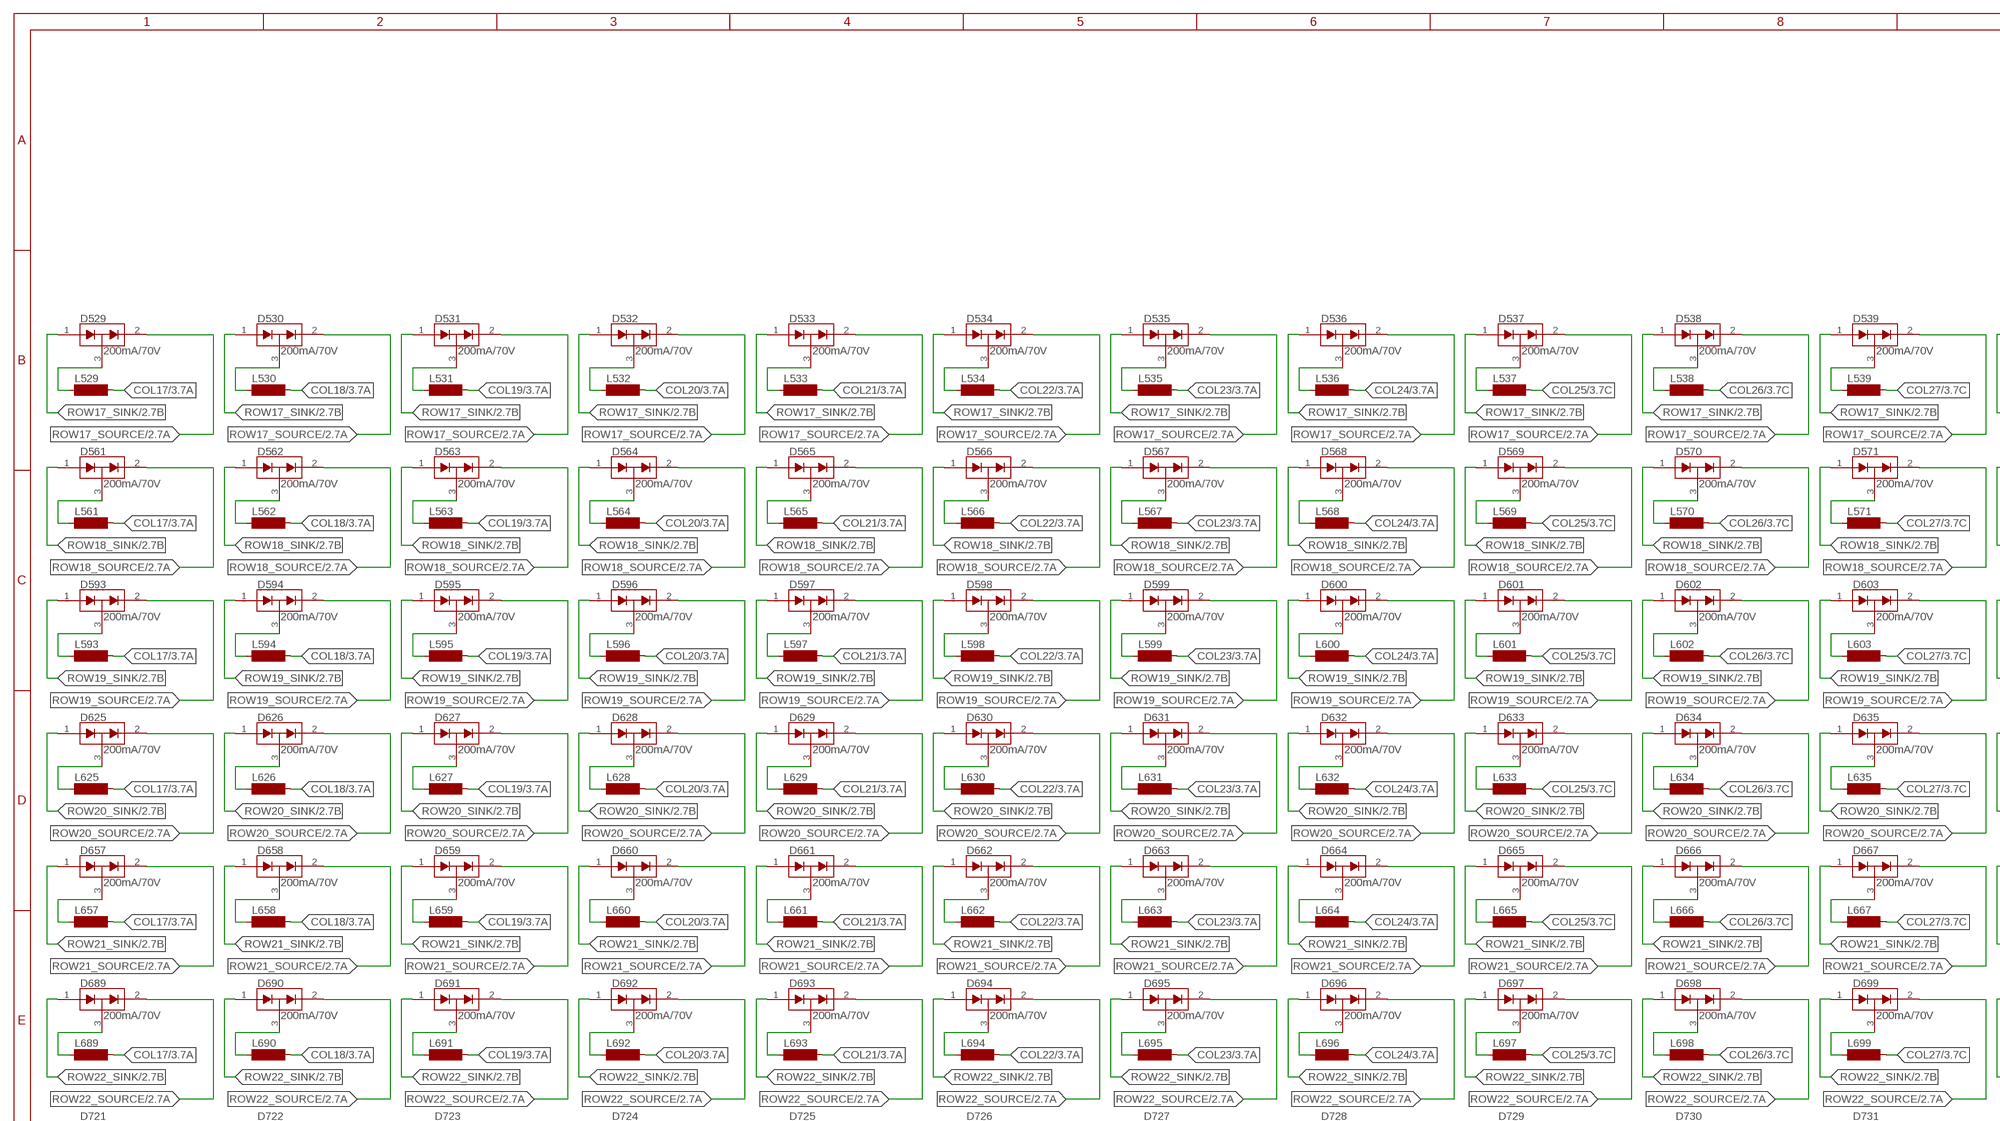
[diagram p15: schematic, sheet 7, part 1 of 4]
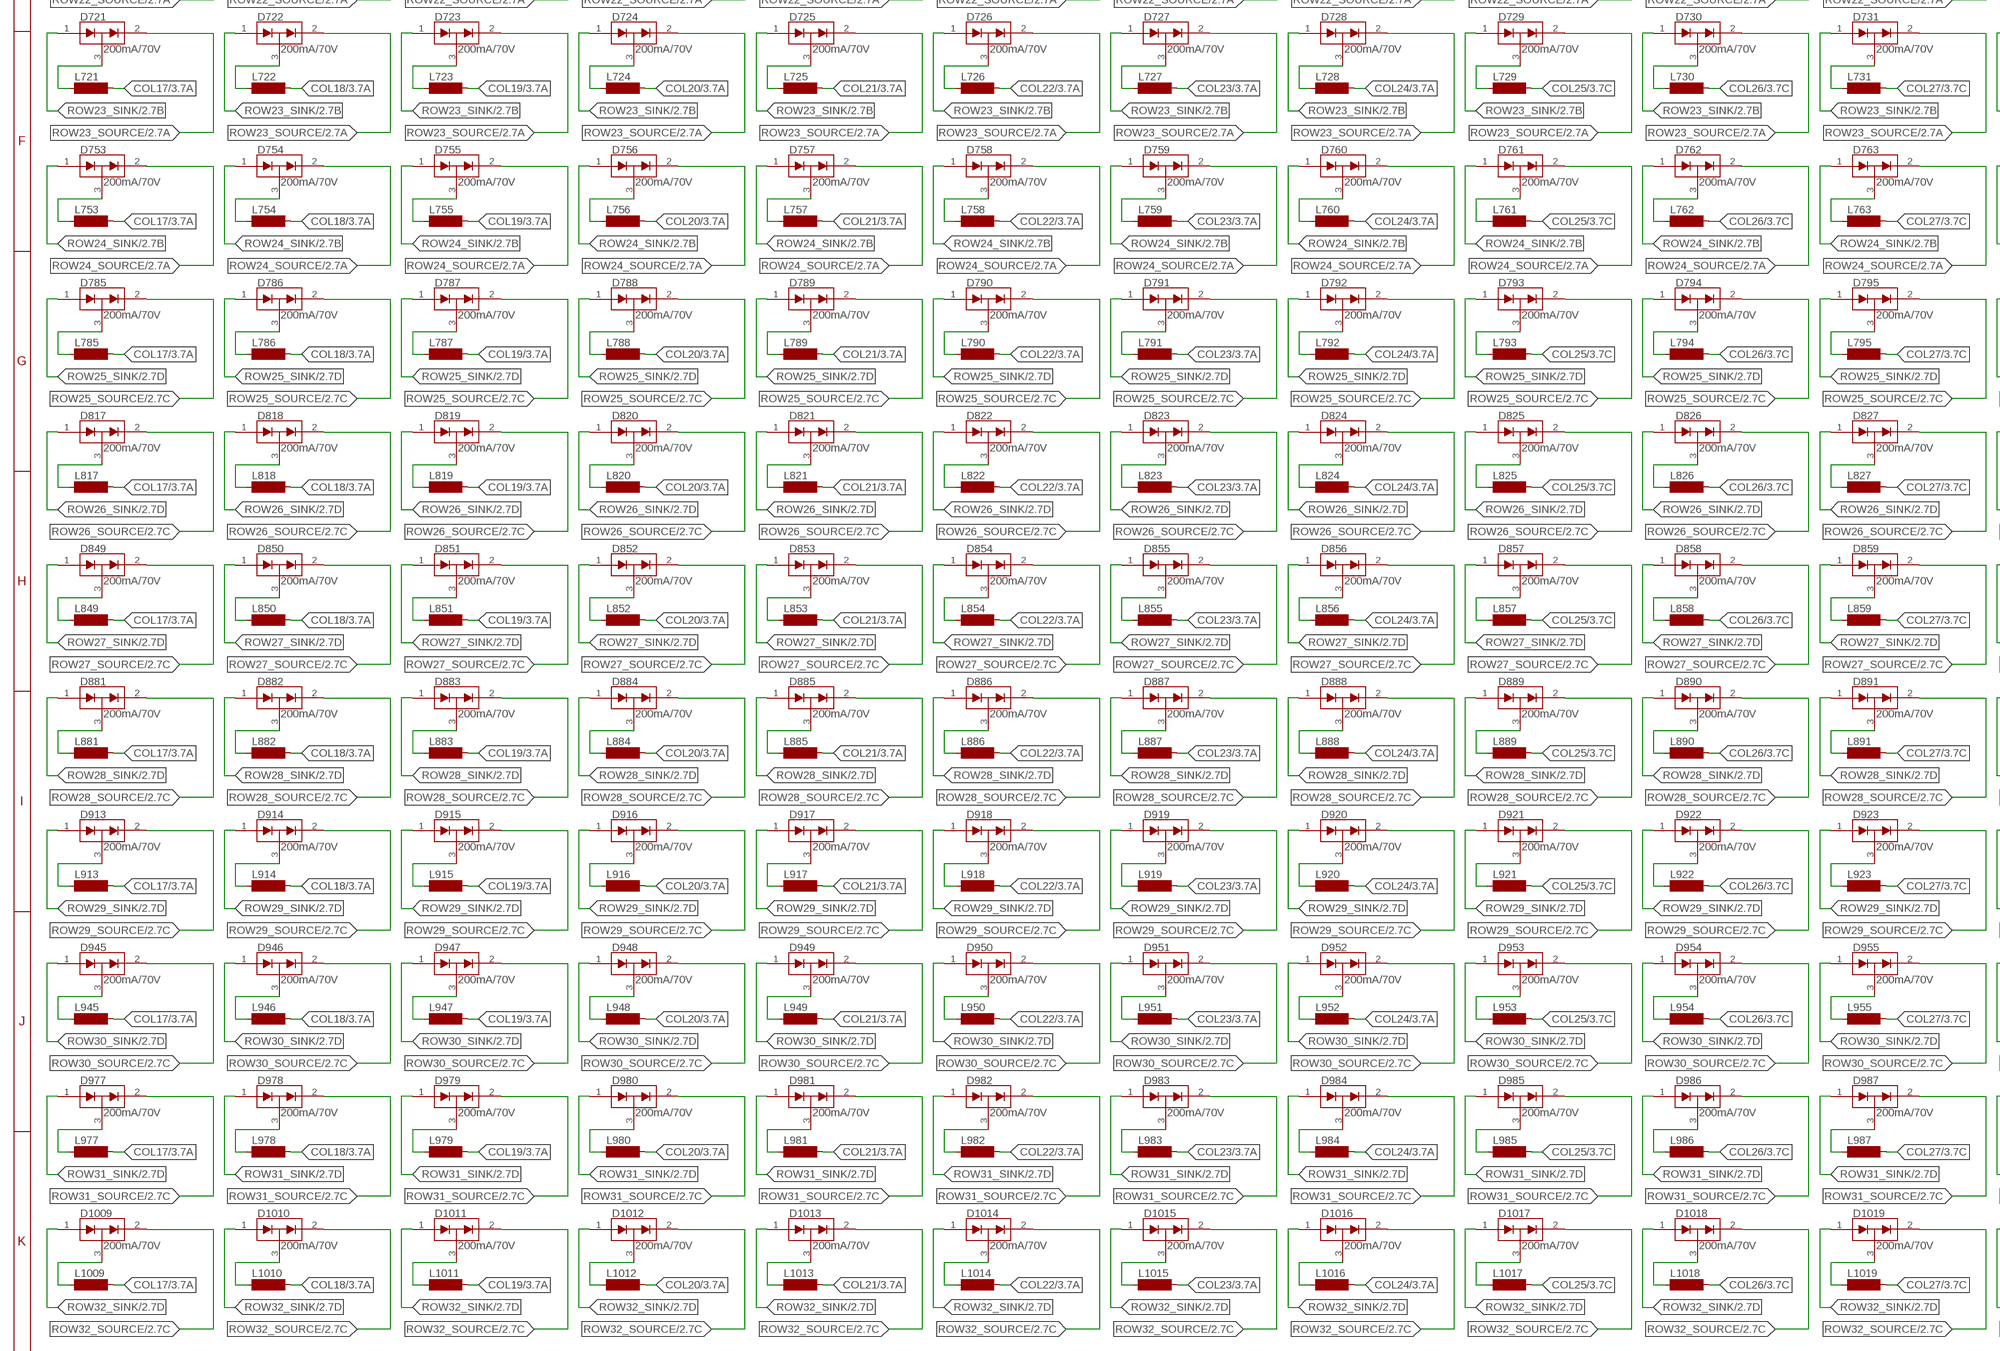
[diagram p16: schematic, sheet 7, part 2 of 4]
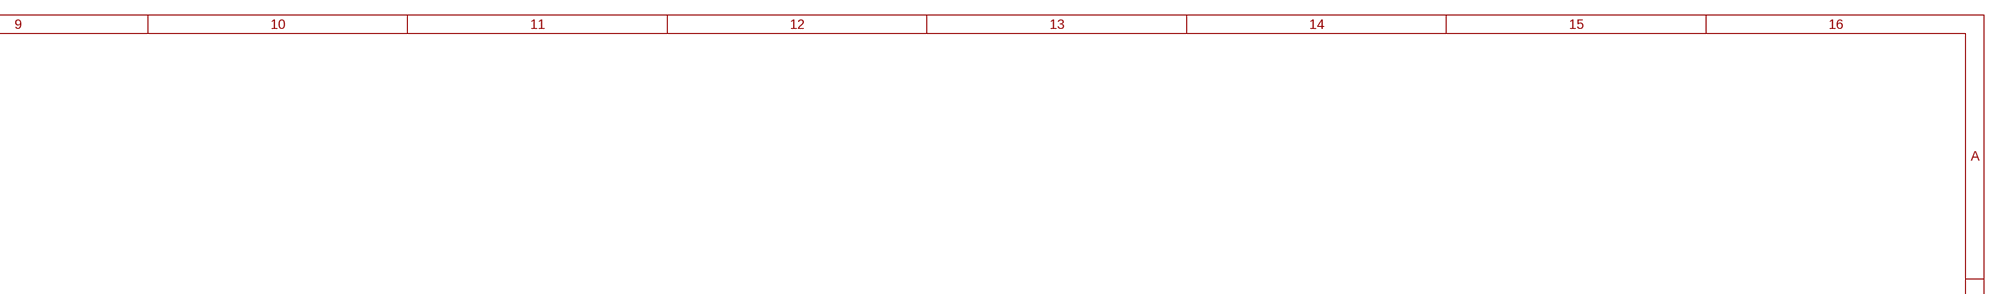
[diagram p17: schematic, sheet 7, part 3 of 4]
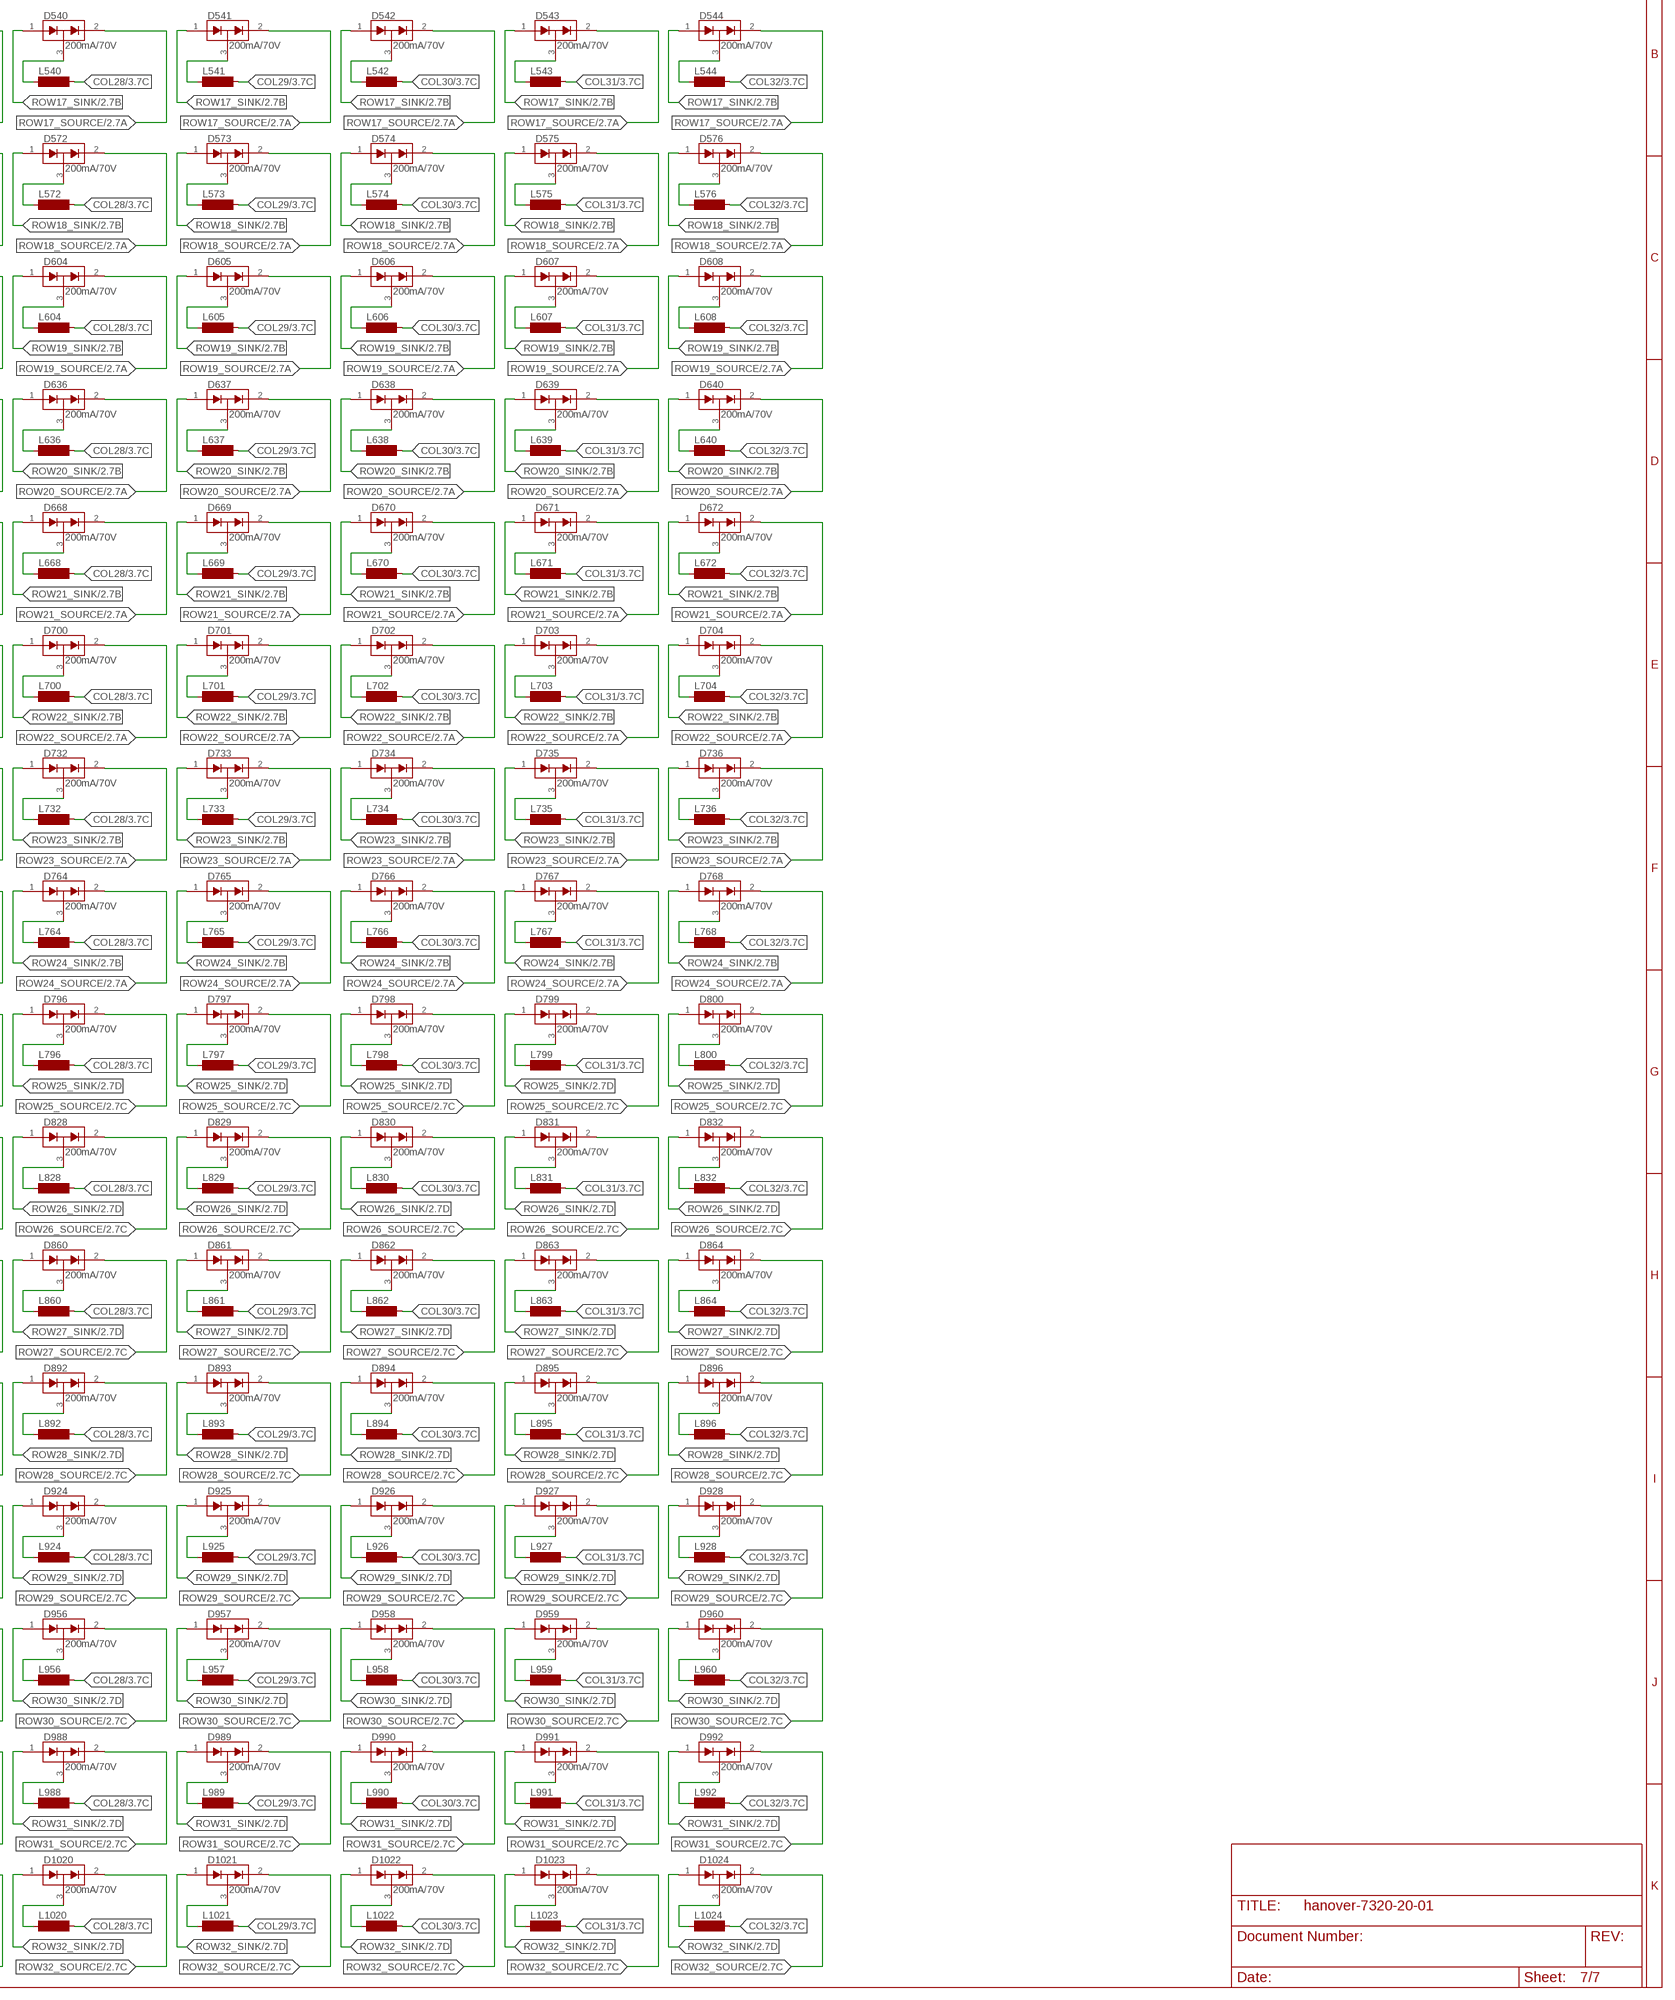
[diagram p18: schematic, sheet 7, part 4 of 4]

(export (version "E")
  (design (tool "Eeschema 10.0.6"))
  (components
    (comp (ref "D1")
      (value "200mA/70V")
      (footprint "eagle-import:SOT23-3")
      (libsource (lib "eagle-import") (part "BAV99"))
    )
    (comp (ref "D2")
      (value "200mA/70V")
      (footprint "eagle-import:SOT23-3")
      (libsource (lib "eagle-import") (part "BAV99"))
    )
    (comp (ref "D3")
      (value "200mA/70V")
      (footprint "eagle-import:SOT23-3")
      (libsource (lib "eagle-import") (part "BAV99"))
    )
    (comp (ref "D4")
      (value "200mA/70V")
      (footprint "eagle-import:SOT23-3")
      (libsource (lib "eagle-import") (part "BAV99"))
    )
    (comp (ref "D5")
      (value "200mA/70V")
      (footprint "eagle-import:SOT23-3")
      (libsource (lib "eagle-import") (part "BAV99"))
    )
    (comp (ref "D6")
      (value "200mA/70V")
      (footprint "eagle-import:SOT23-3")
      (libsource (lib "eagle-import") (part "BAV99"))
    )
    (comp (ref "D7")
      (value "200mA/70V")
      (footprint "eagle-import:SOT23-3")
      (libsource (lib "eagle-import") (part "BAV99"))
    )
    (comp (ref "D8")
      (value "200mA/70V")
      (footprint "eagle-import:SOT23-3")
      (libsource (lib "eagle-import") (part "BAV99"))
    )
    (comp (ref "D9")
      (value "200mA/70V")
      (footprint "eagle-import:SOT23-3")
      (libsource (lib "eagle-import") (part "BAV99"))
    )
    (comp (ref "D10")
      (value "200mA/70V")
      (footprint "eagle-import:SOT23-3")
      (libsource (lib "eagle-import") (part "BAV99"))
    )
    (comp (ref "D11")
      (value "200mA/70V")
      (footprint "eagle-import:SOT23-3")
      (libsource (lib "eagle-import") (part "BAV99"))
    )
    (comp (ref "D12")
      (value "200mA/70V")
      (footprint "eagle-import:SOT23-3")
      (libsource (lib "eagle-import") (part "BAV99"))
    )
    (comp (ref "D13")
      (value "200mA/70V")
      (footprint "eagle-import:SOT23-3")
      (libsource (lib "eagle-import") (part "BAV99"))
    )
    (comp (ref "D14")
      (value "200mA/70V")
      (footprint "eagle-import:SOT23-3")
      (libsource (lib "eagle-import") (part "BAV99"))
    )
    (comp (ref "D15")
      (value "200mA/70V")
      (footprint "eagle-import:SOT23-3")
      (libsource (lib "eagle-import") (part "BAV99"))
    )
    (comp (ref "D16")
      (value "200mA/70V")
      (footprint "eagle-import:SOT23-3")
      (libsource (lib "eagle-import") (part "BAV99"))
    )
    (comp (ref "D33")
      (value "200mA/70V")
      (footprint "eagle-import:SOT23-3")
      (libsource (lib "eagle-import") (part "BAV99"))
    )
    (comp (ref "D34")
      (value "200mA/70V")
      (footprint "eagle-import:SOT23-3")
      (libsource (lib "eagle-import") (part "BAV99"))
    )
    (comp (ref "D35")
      (value "200mA/70V")
      (footprint "eagle-import:SOT23-3")
      (libsource (lib "eagle-import") (part "BAV99"))
    )
    (comp (ref "D36")
      (value "200mA/70V")
      (footprint "eagle-import:SOT23-3")
      (libsource (lib "eagle-import") (part "BAV99"))
    )
    (comp (ref "D37")
      (value "200mA/70V")
      (footprint "eagle-import:SOT23-3")
      (libsource (lib "eagle-import") (part "BAV99"))
    )
    (comp (ref "D38")
      (value "200mA/70V")
      (footprint "eagle-import:SOT23-3")
      (libsource (lib "eagle-import") (part "BAV99"))
    )
    (comp (ref "D39")
      (value "200mA/70V")
      (footprint "eagle-import:SOT23-3")
      (libsource (lib "eagle-import") (part "BAV99"))
    )
    (comp (ref "D40")
      (value "200mA/70V")
      (footprint "eagle-import:SOT23-3")
      (libsource (lib "eagle-import") (part "BAV99"))
    )
    (comp (ref "D41")
      (value "200mA/70V")
      (footprint "eagle-import:SOT23-3")
      (libsource (lib "eagle-import") (part "BAV99"))
    )
    (comp (ref "D42")
      (value "200mA/70V")
      (footprint "eagle-import:SOT23-3")
      (libsource (lib "eagle-import") (part "BAV99"))
    )
    (comp (ref "D43")
      (value "200mA/70V")
      (footprint "eagle-import:SOT23-3")
      (libsource (lib "eagle-import") (part "BAV99"))
    )
    (comp (ref "D44")
      (value "200mA/70V")
      (footprint "eagle-import:SOT23-3")
      (libsource (lib "eagle-import") (part "BAV99"))
    )
    (comp (ref "D45")
      (value "200mA/70V")
      (footprint "eagle-import:SOT23-3")
      (libsource (lib "eagle-import") (part "BAV99"))
    )
    (comp (ref "D46")
      (value "200mA/70V")
      (footprint "eagle-import:SOT23-3")
      (libsource (lib "eagle-import") (part "BAV99"))
    )
    (comp (ref "D47")
      (value "200mA/70V")
      (footprint "eagle-import:SOT23-3")
      (libsource (lib "eagle-import") (part "BAV99"))
    )
    (comp (ref "D48")
      (value "200mA/70V")
      (footprint "eagle-import:SOT23-3")
      (libsource (lib "eagle-import") (part "BAV99"))
    )
    (comp (ref "D65")
      (value "200mA/70V")
      (footprint "eagle-import:SOT23-3")
      (libsource (lib "eagle-import") (part "BAV99"))
    )
    (comp (ref "D66")
      (value "200mA/70V")
      (footprint "eagle-import:SOT23-3")
      (libsource (lib "eagle-import") (part "BAV99"))
    )
    (comp (ref "D67")
      (value "200mA/70V")
      (footprint "eagle-import:SOT23-3")
      (libsource (lib "eagle-import") (part "BAV99"))
    )
    (comp (ref "D68")
      (value "200mA/70V")
      (footprint "eagle-import:SOT23-3")
      (libsource (lib "eagle-import") (part "BAV99"))
    )
    (comp (ref "D69")
      (value "200mA/70V")
      (footprint "eagle-import:SOT23-3")
      (libsource (lib "eagle-import") (part "BAV99"))
    )
    (comp (ref "D70")
      (value "200mA/70V")
      (footprint "eagle-import:SOT23-3")
      (libsource (lib "eagle-import") (part "BAV99"))
    )
    (comp (ref "D71")
      (value "200mA/70V")
      (footprint "eagle-import:SOT23-3")
      (libsource (lib "eagle-import") (part "BAV99"))
    )
    (comp (ref "D72")
      (value "200mA/70V")
      (footprint "eagle-import:SOT23-3")
      (libsource (lib "eagle-import") (part "BAV99"))
    )
    (comp (ref "D73")
      (value "200mA/70V")
      (footprint "eagle-import:SOT23-3")
      (libsource (lib "eagle-import") (part "BAV99"))
    )
    (comp (ref "D74")
      (value "200mA/70V")
      (footprint "eagle-import:SOT23-3")
      (libsource (lib "eagle-import") (part "BAV99"))
    )
    (comp (ref "D75")
      (value "200mA/70V")
      (footprint "eagle-import:SOT23-3")
      (libsource (lib "eagle-import") (part "BAV99"))
    )
    (comp (ref "D76")
      (value "200mA/70V")
      (footprint "eagle-import:SOT23-3")
      (libsource (lib "eagle-import") (part "BAV99"))
    )
    (comp (ref "D77")
      (value "200mA/70V")
      (footprint "eagle-import:SOT23-3")
      (libsource (lib "eagle-import") (part "BAV99"))
    )
    (comp (ref "D78")
      (value "200mA/70V")
      (footprint "eagle-import:SOT23-3")
      (libsource (lib "eagle-import") (part "BAV99"))
    )
    (comp (ref "D79")
      (value "200mA/70V")
      (footprint "eagle-import:SOT23-3")
      (libsource (lib "eagle-import") (part "BAV99"))
    )
    (comp (ref "D80")
      (value "200mA/70V")
      (footprint "eagle-import:SOT23-3")
      (libsource (lib "eagle-import") (part "BAV99"))
    )
    (comp (ref "D97")
      (value "200mA/70V")
      (footprint "eagle-import:SOT23-3")
      (libsource (lib "eagle-import") (part "BAV99"))
    )
    (comp (ref "D98")
      (value "200mA/70V")
      (footprint "eagle-import:SOT23-3")
      (libsource (lib "eagle-import") (part "BAV99"))
    )
    (comp (ref "D99")
      (value "200mA/70V")
      (footprint "eagle-import:SOT23-3")
      (libsource (lib "eagle-import") (part "BAV99"))
    )
    (comp (ref "D100")
      (value "200mA/70V")
      (footprint "eagle-import:SOT23-3")
      (libsource (lib "eagle-import") (part "BAV99"))
    )
    (comp (ref "D101")
      (value "200mA/70V")
      (footprint "eagle-import:SOT23-3")
      (libsource (lib "eagle-import") (part "BAV99"))
    )
    (comp (ref "D102")
      (value "200mA/70V")
      (footprint "eagle-import:SOT23-3")
      (libsource (lib "eagle-import") (part "BAV99"))
    )
    (comp (ref "D103")
      (value "200mA/70V")
      (footprint "eagle-import:SOT23-3")
      (libsource (lib "eagle-import") (part "BAV99"))
    )
    (comp (ref "D104")
      (value "200mA/70V")
      (footprint "eagle-import:SOT23-3")
      (libsource (lib "eagle-import") (part "BAV99"))
    )
    (comp (ref "D105")
      (value "200mA/70V")
      (footprint "eagle-import:SOT23-3")
      (libsource (lib "eagle-import") (part "BAV99"))
    )
    (comp (ref "D106")
      (value "200mA/70V")
      (footprint "eagle-import:SOT23-3")
      (libsource (lib "eagle-import") (part "BAV99"))
    )
    (comp (ref "D107")
      (value "200mA/70V")
      (footprint "eagle-import:SOT23-3")
      (libsource (lib "eagle-import") (part "BAV99"))
    )
    (comp (ref "D108")
      (value "200mA/70V")
      (footprint "eagle-import:SOT23-3")
      (libsource (lib "eagle-import") (part "BAV99"))
    )
    (comp (ref "D109")
      (value "200mA/70V")
      (footprint "eagle-import:SOT23-3")
      (libsource (lib "eagle-import") (part "BAV99"))
    )
    (comp (ref "D110")
      (value "200mA/70V")
      (footprint "eagle-import:SOT23-3")
      (libsource (lib "eagle-import") (part "BAV99"))
    )
    (comp (ref "D111")
      (value "200mA/70V")
      (footprint "eagle-import:SOT23-3")
      (libsource (lib "eagle-import") (part "BAV99"))
    )
    (comp (ref "D112")
      (value "200mA/70V")
      (footprint "eagle-import:SOT23-3")
      (libsource (lib "eagle-import") (part "BAV99"))
    )
    (comp (ref "D129")
      (value "200mA/70V")
      (footprint "eagle-import:SOT23-3")
      (libsource (lib "eagle-import") (part "BAV99"))
    )
    (comp (ref "D130")
      (value "200mA/70V")
      (footprint "eagle-import:SOT23-3")
      (libsource (lib "eagle-import") (part "BAV99"))
    )
    (comp (ref "D131")
      (value "200mA/70V")
      (footprint "eagle-import:SOT23-3")
      (libsource (lib "eagle-import") (part "BAV99"))
    )
    (comp (ref "D132")
      (value "200mA/70V")
      (footprint "eagle-import:SOT23-3")
      (libsource (lib "eagle-import") (part "BAV99"))
    )
    (comp (ref "D133")
      (value "200mA/70V")
      (footprint "eagle-import:SOT23-3")
      (libsource (lib "eagle-import") (part "BAV99"))
    )
    (comp (ref "D134")
      (value "200mA/70V")
      (footprint "eagle-import:SOT23-3")
      (libsource (lib "eagle-import") (part "BAV99"))
    )
    (comp (ref "D135")
      (value "200mA/70V")
      (footprint "eagle-import:SOT23-3")
      (libsource (lib "eagle-import") (part "BAV99"))
    )
    (comp (ref "D136")
      (value "200mA/70V")
      (footprint "eagle-import:SOT23-3")
      (libsource (lib "eagle-import") (part "BAV99"))
    )
    (comp (ref "D137")
      (value "200mA/70V")
      (footprint "eagle-import:SOT23-3")
      (libsource (lib "eagle-import") (part "BAV99"))
    )
    (comp (ref "D138")
      (value "200mA/70V")
      (footprint "eagle-import:SOT23-3")
      (libsource (lib "eagle-import") (part "BAV99"))
    )
    (comp (ref "D139")
      (value "200mA/70V")
      (footprint "eagle-import:SOT23-3")
      (libsource (lib "eagle-import") (part "BAV99"))
    )
    (comp (ref "D140")
      (value "200mA/70V")
      (footprint "eagle-import:SOT23-3")
      (libsource (lib "eagle-import") (part "BAV99"))
    )
    (comp (ref "D141")
      (value "200mA/70V")
      (footprint "eagle-import:SOT23-3")
      (libsource (lib "eagle-import") (part "BAV99"))
    )
    (comp (ref "D142")
      (value "200mA/70V")
      (footprint "eagle-import:SOT23-3")
      (libsource (lib "eagle-import") (part "BAV99"))
    )
    (comp (ref "D143")
      (value "200mA/70V")
      (footprint "eagle-import:SOT23-3")
      (libsource (lib "eagle-import") (part "BAV99"))
    )
    (comp (ref "D144")
      (value "200mA/70V")
      (footprint "eagle-import:SOT23-3")
      (libsource (lib "eagle-import") (part "BAV99"))
    )
    (comp (ref "D161")
      (value "200mA/70V")
      (footprint "eagle-import:SOT23-3")
      (libsource (lib "eagle-import") (part "BAV99"))
    )
    (comp (ref "D162")
      (value "200mA/70V")
      (footprint "eagle-import:SOT23-3")
      (libsource (lib "eagle-import") (part "BAV99"))
    )
    (comp (ref "D163")
      (value "200mA/70V")
      (footprint "eagle-import:SOT23-3")
      (libsource (lib "eagle-import") (part "BAV99"))
    )
    (comp (ref "D164")
      (value "200mA/70V")
      (footprint "eagle-import:SOT23-3")
      (libsource (lib "eagle-import") (part "BAV99"))
    )
    (comp (ref "D165")
      (value "200mA/70V")
      (footprint "eagle-import:SOT23-3")
      (libsource (lib "eagle-import") (part "BAV99"))
    )
    (comp (ref "D166")
      (value "200mA/70V")
      (footprint "eagle-import:SOT23-3")
      (libsource (lib "eagle-import") (part "BAV99"))
    )
    (comp (ref "D167")
      (value "200mA/70V")
      (footprint "eagle-import:SOT23-3")
      (libsource (lib "eagle-import") (part "BAV99"))
    )
    (comp (ref "D168")
      (value "200mA/70V")
      (footprint "eagle-import:SOT23-3")
      (libsource (lib "eagle-import") (part "BAV99"))
    )
    (comp (ref "D169")
      (value "200mA/70V")
      (footprint "eagle-import:SOT23-3")
      (libsource (lib "eagle-import") (part "BAV99"))
    )
    (comp (ref "D170")
      (value "200mA/70V")
      (footprint "eagle-import:SOT23-3")
      (libsource (lib "eagle-import") (part "BAV99"))
    )
    (comp (ref "D171")
      (value "200mA/70V")
      (footprint "eagle-import:SOT23-3")
      (libsource (lib "eagle-import") (part "BAV99"))
    )
    (comp (ref "D172")
      (value "200mA/70V")
      (footprint "eagle-import:SOT23-3")
      (libsource (lib "eagle-import") (part "BAV99"))
    )
    (comp (ref "D173")
      (value "200mA/70V")
      (footprint "eagle-import:SOT23-3")
      (libsource (lib "eagle-import") (part "BAV99"))
    )
    (comp (ref "D174")
      (value "200mA/70V")
      (footprint "eagle-import:SOT23-3")
      (libsource (lib "eagle-import") (part "BAV99"))
    )
    (comp (ref "D175")
      (value "200mA/70V")
      (footprint "eagle-import:SOT23-3")
      (libsource (lib "eagle-import") (part "BAV99"))
    )
    (comp (ref "D176")
      (value "200mA/70V")
      (footprint "eagle-import:SOT23-3")
      (libsource (lib "eagle-import") (part "BAV99"))
    )
    (comp (ref "D193")
      (value "200mA/70V")
      (footprint "eagle-import:SOT23-3")
      (libsource (lib "eagle-import") (part "BAV99"))
    )
    (comp (ref "D194")
      (value "200mA/70V")
      (footprint "eagle-import:SOT23-3")
      (libsource (lib "eagle-import") (part "BAV99"))
    )
    (comp (ref "D195")
      (value "200mA/70V")
      (footprint "eagle-import:SOT23-3")
      (libsource (lib "eagle-import") (part "BAV99"))
    )
    (comp (ref "D196")
      (value "200mA/70V")
      (footprint "eagle-import:SOT23-3")
      (libsource (lib "eagle-import") (part "BAV99"))
    )
    (comp (ref "D197")
      (value "200mA/70V")
      (footprint "eagle-import:SOT23-3")
      (libsource (lib "eagle-import") (part "BAV99"))
    )
    (comp (ref "D198")
      (value "200mA/70V")
      (footprint "eagle-import:SOT23-3")
      (libsource (lib "eagle-import") (part "BAV99"))
    )
    (comp (ref "D199")
      (value "200mA/70V")
      (footprint "eagle-import:SOT23-3")
      (libsource (lib "eagle-import") (part "BAV99"))
    )
    (comp (ref "D200")
      (value "200mA/70V")
      (footprint "eagle-import:SOT23-3")
      (libsource (lib "eagle-import") (part "BAV99"))
    )
    (comp (ref "D201")
      (value "200mA/70V")
      (footprint "eagle-import:SOT23-3")
      (libsource (lib "eagle-import") (part "BAV99"))
    )
    (comp (ref "D202")
      (value "200mA/70V")
      (footprint "eagle-import:SOT23-3")
      (libsource (lib "eagle-import") (part "BAV99"))
    )
    (comp (ref "D203")
      (value "200mA/70V")
      (footprint "eagle-import:SOT23-3")
      (libsource (lib "eagle-import") (part "BAV99"))
    )
    (comp (ref "D204")
      (value "200mA/70V")
      (footprint "eagle-import:SOT23-3")
      (libsource (lib "eagle-import") (part "BAV99"))
    )
    (comp (ref "D205")
      (value "200mA/70V")
      (footprint "eagle-import:SOT23-3")
      (libsource (lib "eagle-import") (part "BAV99"))
    )
    (comp (ref "D206")
      (value "200mA/70V")
      (footprint "eagle-import:SOT23-3")
      (libsource (lib "eagle-import") (part "BAV99"))
    )
    (comp (ref "D207")
      (value "200mA/70V")
      (footprint "eagle-import:SOT23-3")
      (libsource (lib "eagle-import") (part "BAV99"))
    )
    (comp (ref "D208")
      (value "200mA/70V")
      (footprint "eagle-import:SOT23-3")
      (libsource (lib "eagle-import") (part "BAV99"))
    )
    (comp (ref "D225")
      (value "200mA/70V")
      (footprint "eagle-import:SOT23-3")
      (libsource (lib "eagle-import") (part "BAV99"))
    )
    (comp (ref "D226")
      (value "200mA/70V")
      (footprint "eagle-import:SOT23-3")
      (libsource (lib "eagle-import") (part "BAV99"))
    )
    (comp (ref "D227")
      (value "200mA/70V")
      (footprint "eagle-import:SOT23-3")
      (libsource (lib "eagle-import") (part "BAV99"))
    )
    (comp (ref "D228")
      (value "200mA/70V")
      (footprint "eagle-import:SOT23-3")
      (libsource (lib "eagle-import") (part "BAV99"))
    )
    (comp (ref "D229")
      (value "200mA/70V")
      (footprint "eagle-import:SOT23-3")
      (libsource (lib "eagle-import") (part "BAV99"))
    )
    (comp (ref "D230")
      (value "200mA/70V")
      (footprint "eagle-import:SOT23-3")
      (libsource (lib "eagle-import") (part "BAV99"))
    )
    (comp (ref "D231")
      (value "200mA/70V")
      (footprint "eagle-import:SOT23-3")
      (libsource (lib "eagle-import") (part "BAV99"))
    )
    (comp (ref "D232")
      (value "200mA/70V")
      (footprint "eagle-import:SOT23-3")
      (libsource (lib "eagle-import") (part "BAV99"))
    )
    (comp (ref "D233")
      (value "200mA/70V")
      (footprint "eagle-import:SOT23-3")
      (libsource (lib "eagle-import") (part "BAV99"))
    )
    (comp (ref "D234")
      (value "200mA/70V")
      (footprint "eagle-import:SOT23-3")
      (libsource (lib "eagle-import") (part "BAV99"))
    )
    (comp (ref "D235")
      (value "200mA/70V")
      (footprint "eagle-import:SOT23-3")
      (libsource (lib "eagle-import") (part "BAV99"))
    )
    (comp (ref "D236")
      (value "200mA/70V")
      (footprint "eagle-import:SOT23-3")
      (libsource (lib "eagle-import") (part "BAV99"))
    )
    (comp (ref "D237")
      (value "200mA/70V")
      (footprint "eagle-import:SOT23-3")
      (libsource (lib "eagle-import") (part "BAV99"))
    )
    (comp (ref "D238")
      (value "200mA/70V")
      (footprint "eagle-import:SOT23-3")
      (libsource (lib "eagle-import") (part "BAV99"))
    )
    (comp (ref "D239")
      (value "200mA/70V")
      (footprint "eagle-import:SOT23-3")
      (libsource (lib "eagle-import") (part "BAV99"))
    )
    (comp (ref "D240")
      (value "200mA/70V")
      (footprint "eagle-import:SOT23-3")
      (libsource (lib "eagle-import") (part "BAV99"))
    )
    (comp (ref "D257")
      (value "200mA/70V")
      (footprint "eagle-import:SOT23-3")
      (libsource (lib "eagle-import") (part "BAV99"))
    )
    (comp (ref "D258")
      (value "200mA/70V")
      (footprint "eagle-import:SOT23-3")
      (libsource (lib "eagle-import") (part "BAV99"))
    )
    (comp (ref "D259")
      (value "200mA/70V")
      (footprint "eagle-import:SOT23-3")
      (libsource (lib "eagle-import") (part "BAV99"))
    )
    (comp (ref "D260")
      (value "200mA/70V")
      (footprint "eagle-import:SOT23-3")
      (libsource (lib "eagle-import") (part "BAV99"))
    )
    (comp (ref "D261")
      (value "200mA/70V")
      (footprint "eagle-import:SOT23-3")
      (libsource (lib "eagle-import") (part "BAV99"))
    )
    (comp (ref "D262")
      (value "200mA/70V")
      (footprint "eagle-import:SOT23-3")
      (libsource (lib "eagle-import") (part "BAV99"))
    )
    (comp (ref "D263")
      (value "200mA/70V")
      (footprint "eagle-import:SOT23-3")
      (libsource (lib "eagle-import") (part "BAV99"))
    )
    (comp (ref "D264")
      (value "200mA/70V")
      (footprint "eagle-import:SOT23-3")
      (libsource (lib "eagle-import") (part "BAV99"))
    )
    (comp (ref "D265")
      (value "200mA/70V")
      (footprint "eagle-import:SOT23-3")
      (libsource (lib "eagle-import") (part "BAV99"))
    )
    (comp (ref "D266")
      (value "200mA/70V")
      (footprint "eagle-import:SOT23-3")
      (libsource (lib "eagle-import") (part "BAV99"))
    )
    (comp (ref "D267")
      (value "200mA/70V")
      (footprint "eagle-import:SOT23-3")
      (libsource (lib "eagle-import") (part "BAV99"))
    )
    (comp (ref "D268")
      (value "200mA/70V")
      (footprint "eagle-import:SOT23-3")
      (libsource (lib "eagle-import") (part "BAV99"))
    )
    (comp (ref "D269")
      (value "200mA/70V")
      (footprint "eagle-import:SOT23-3")
      (libsource (lib "eagle-import") (part "BAV99"))
    )
    (comp (ref "D270")
      (value "200mA/70V")
      (footprint "eagle-import:SOT23-3")
      (libsource (lib "eagle-import") (part "BAV99"))
    )
    (comp (ref "D271")
      (value "200mA/70V")
      (footprint "eagle-import:SOT23-3")
      (libsource (lib "eagle-import") (part "BAV99"))
    )
    (comp (ref "D272")
      (value "200mA/70V")
      (footprint "eagle-import:SOT23-3")
      (libsource (lib "eagle-import") (part "BAV99"))
    )
    (comp (ref "D289")
      (value "200mA/70V")
      (footprint "eagle-import:SOT23-3")
      (libsource (lib "eagle-import") (part "BAV99"))
    )
    (comp (ref "D290")
      (value "200mA/70V")
      (footprint "eagle-import:SOT23-3")
      (libsource (lib "eagle-import") (part "BAV99"))
    )
    (comp (ref "D291")
      (value "200mA/70V")
      (footprint "eagle-import:SOT23-3")
      (libsource (lib "eagle-import") (part "BAV99"))
    )
    (comp (ref "D292")
      (value "200mA/70V")
      (footprint "eagle-import:SOT23-3")
      (libsource (lib "eagle-import") (part "BAV99"))
    )
    (comp (ref "D293")
      (value "200mA/70V")
      (footprint "eagle-import:SOT23-3")
      (libsource (lib "eagle-import") (part "BAV99"))
    )
    (comp (ref "D294")
      (value "200mA/70V")
      (footprint "eagle-import:SOT23-3")
      (libsource (lib "eagle-import") (part "BAV99"))
    )
    (comp (ref "D295")
      (value "200mA/70V")
      (footprint "eagle-import:SOT23-3")
      (libsource (lib "eagle-import") (part "BAV99"))
    )
    (comp (ref "D296")
      (value "200mA/70V")
      (footprint "eagle-import:SOT23-3")
      (libsource (lib "eagle-import") (part "BAV99"))
    )
    (comp (ref "D297")
      (value "200mA/70V")
      (footprint "eagle-import:SOT23-3")
      (libsource (lib "eagle-import") (part "BAV99"))
    )
    (comp (ref "D298")
      (value "200mA/70V")
      (footprint "eagle-import:SOT23-3")
      (libsource (lib "eagle-import") (part "BAV99"))
    )
    (comp (ref "D299")
      (value "200mA/70V")
      (footprint "eagle-import:SOT23-3")
      (libsource (lib "eagle-import") (part "BAV99"))
    )
    (comp (ref "D300")
      (value "200mA/70V")
      (footprint "eagle-import:SOT23-3")
      (libsource (lib "eagle-import") (part "BAV99"))
    )
    (comp (ref "D301")
      (value "200mA/70V")
      (footprint "eagle-import:SOT23-3")
      (libsource (lib "eagle-import") (part "BAV99"))
    )
    (comp (ref "D302")
      (value "200mA/70V")
      (footprint "eagle-import:SOT23-3")
      (libsource (lib "eagle-import") (part "BAV99"))
    )
    (comp (ref "D303")
      (value "200mA/70V")
      (footprint "eagle-import:SOT23-3")
      (libsource (lib "eagle-import") (part "BAV99"))
    )
    (comp (ref "D304")
      (value "200mA/70V")
      (footprint "eagle-import:SOT23-3")
      (libsource (lib "eagle-import") (part "BAV99"))
    )
    (comp (ref "D321")
      (value "200mA/70V")
      (footprint "eagle-import:SOT23-3")
      (libsource (lib "eagle-import") (part "BAV99"))
    )
    (comp (ref "D322")
      (value "200mA/70V")
      (footprint "eagle-import:SOT23-3")
      (libsource (lib "eagle-import") (part "BAV99"))
    )
    (comp (ref "D323")
      (value "200mA/70V")
      (footprint "eagle-import:SOT23-3")
      (libsource (lib "eagle-import") (part "BAV99"))
    )
    (comp (ref "D324")
      (value "200mA/70V")
      (footprint "eagle-import:SOT23-3")
      (libsource (lib "eagle-import") (part "BAV99"))
    )
    (comp (ref "D325")
      (value "200mA/70V")
      (footprint "eagle-import:SOT23-3")
      (libsource (lib "eagle-import") (part "BAV99"))
    )
    (comp (ref "D326")
      (value "200mA/70V")
      (footprint "eagle-import:SOT23-3")
      (libsource (lib "eagle-import") (part "BAV99"))
    )
    (comp (ref "D327")
      (value "200mA/70V")
      (footprint "eagle-import:SOT23-3")
      (libsource (lib "eagle-import") (part "BAV99"))
    )
    (comp (ref "D328")
      (value "200mA/70V")
      (footprint "eagle-import:SOT23-3")
      (libsource (lib "eagle-import") (part "BAV99"))
    )
    (comp (ref "D329")
      (value "200mA/70V")
      (footprint "eagle-import:SOT23-3")
      (libsource (lib "eagle-import") (part "BAV99"))
    )
    (comp (ref "D330")
      (value "200mA/70V")
      (footprint "eagle-import:SOT23-3")
      (libsource (lib "eagle-import") (part "BAV99"))
    )
    (comp (ref "D331")
      (value "200mA/70V")
      (footprint "eagle-import:SOT23-3")
      (libsource (lib "eagle-import") (part "BAV99"))
    )
    (comp (ref "D332")
      (value "200mA/70V")
      (footprint "eagle-import:SOT23-3")
      (libsource (lib "eagle-import") (part "BAV99"))
    )
    (comp (ref "D333")
      (value "200mA/70V")
      (footprint "eagle-import:SOT23-3")
      (libsource (lib "eagle-import") (part "BAV99"))
    )
    (comp (ref "D334")
      (value "200mA/70V")
      (footprint "eagle-import:SOT23-3")
      (libsource (lib "eagle-import") (part "BAV99"))
    )
    (comp (ref "D335")
      (value "200mA/70V")
      (footprint "eagle-import:SOT23-3")
      (libsource (lib "eagle-import") (part "BAV99"))
    )
    (comp (ref "D336")
      (value "200mA/70V")
      (footprint "eagle-import:SOT23-3")
      (libsource (lib "eagle-import") (part "BAV99"))
    )
    (comp (ref "D353")
      (value "200mA/70V")
      (footprint "eagle-import:SOT23-3")
      (libsource (lib "eagle-import") (part "BAV99"))
    )
    (comp (ref "D354")
      (value "200mA/70V")
      (footprint "eagle-import:SOT23-3")
      (libsource (lib "eagle-import") (part "BAV99"))
    )
    (comp (ref "D355")
      (value "200mA/70V")
      (footprint "eagle-import:SOT23-3")
      (libsource (lib "eagle-import") (part "BAV99"))
    )
    (comp (ref "D356")
      (value "200mA/70V")
      (footprint "eagle-import:SOT23-3")
      (libsource (lib "eagle-import") (part "BAV99"))
    )
    (comp (ref "D357")
      (value "200mA/70V")
      (footprint "eagle-import:SOT23-3")
      (libsource (lib "eagle-import") (part "BAV99"))
    )
    (comp (ref "D358")
      (value "200mA/70V")
      (footprint "eagle-import:SOT23-3")
      (libsource (lib "eagle-import") (part "BAV99"))
    )
    (comp (ref "D359")
      (value "200mA/70V")
      (footprint "eagle-import:SOT23-3")
      (libsource (lib "eagle-import") (part "BAV99"))
    )
    (comp (ref "D360")
      (value "200mA/70V")
      (footprint "eagle-import:SOT23-3")
      (libsource (lib "eagle-import") (part "BAV99"))
    )
    (comp (ref "D361")
      (value "200mA/70V")
      (footprint "eagle-import:SOT23-3")
      (libsource (lib "eagle-import") (part "BAV99"))
    )
    (comp (ref "D362")
      (value "200mA/70V")
      (footprint "eagle-import:SOT23-3")
      (libsource (lib "eagle-import") (part "BAV99"))
    )
    (comp (ref "D363")
      (value "200mA/70V")
      (footprint "eagle-import:SOT23-3")
      (libsource (lib "eagle-import") (part "BAV99"))
    )
    (comp (ref "D364")
      (value "200mA/70V")
      (footprint "eagle-import:SOT23-3")
      (libsource (lib "eagle-import") (part "BAV99"))
    )
    (comp (ref "D365")
      (value "200mA/70V")
      (footprint "eagle-import:SOT23-3")
      (libsource (lib "eagle-import") (part "BAV99"))
    )
    (comp (ref "D366")
      (value "200mA/70V")
      (footprint "eagle-import:SOT23-3")
      (libsource (lib "eagle-import") (part "BAV99"))
    )
    (comp (ref "D367")
      (value "200mA/70V")
      (footprint "eagle-import:SOT23-3")
      (libsource (lib "eagle-import") (part "BAV99"))
    )
    (comp (ref "D368")
      (value "200mA/70V")
      (footprint "eagle-import:SOT23-3")
      (libsource (lib "eagle-import") (part "BAV99"))
    )
    (comp (ref "D385")
      (value "200mA/70V")
      (footprint "eagle-import:SOT23-3")
      (libsource (lib "eagle-import") (part "BAV99"))
    )
    (comp (ref "D386")
      (value "200mA/70V")
      (footprint "eagle-import:SOT23-3")
      (libsource (lib "eagle-import") (part "BAV99"))
    )
    (comp (ref "D387")
      (value "200mA/70V")
      (footprint "eagle-import:SOT23-3")
      (libsource (lib "eagle-import") (part "BAV99"))
    )
    (comp (ref "D388")
      (value "200mA/70V")
      (footprint "eagle-import:SOT23-3")
      (libsource (lib "eagle-import") (part "BAV99"))
    )
    (comp (ref "D389")
      (value "200mA/70V")
      (footprint "eagle-import:SOT23-3")
      (libsource (lib "eagle-import") (part "BAV99"))
    )
    (comp (ref "D390")
      (value "200mA/70V")
      (footprint "eagle-import:SOT23-3")
      (libsource (lib "eagle-import") (part "BAV99"))
    )
    (comp (ref "D391")
      (value "200mA/70V")
      (footprint "eagle-import:SOT23-3")
      (libsource (lib "eagle-import") (part "BAV99"))
    )
    (comp (ref "D392")
      (value "200mA/70V")
      (footprint "eagle-import:SOT23-3")
      (libsource (lib "eagle-import") (part "BAV99"))
    )
    (comp (ref "D393")
      (value "200mA/70V")
      (footprint "eagle-import:SOT23-3")
      (libsource (lib "eagle-import") (part "BAV99"))
    )
    (comp (ref "D394")
      (value "200mA/70V")
      (footprint "eagle-import:SOT23-3")
      (libsource (lib "eagle-import") (part "BAV99"))
    )
    (comp (ref "D395")
      (value "200mA/70V")
      (footprint "eagle-import:SOT23-3")
      (libsource (lib "eagle-import") (part "BAV99"))
    )
    (comp (ref "D396")
      (value "200mA/70V")
      (footprint "eagle-import:SOT23-3")
      (libsource (lib "eagle-import") (part "BAV99"))
    )
    (comp (ref "D397")
      (value "200mA/70V")
      (footprint "eagle-import:SOT23-3")
      (libsource (lib "eagle-import") (part "BAV99"))
    )
    (comp (ref "D398")
      (value "200mA/70V")
      (footprint "eagle-import:SOT23-3")
      (libsource (lib "eagle-import") (part "BAV99"))
    )
    (comp (ref "D399")
      (value "200mA/70V")
      (footprint "eagle-import:SOT23-3")
      (libsource (lib "eagle-import") (part "BAV99"))
    )
    (comp (ref "D400")
      (value "200mA/70V")
      (footprint "eagle-import:SOT23-3")
      (libsource (lib "eagle-import") (part "BAV99"))
    )
    (comp (ref "D417")
      (value "200mA/70V")
      (footprint "eagle-import:SOT23-3")
      (libsource (lib "eagle-import") (part "BAV99"))
    )
    (comp (ref "D418")
      (value "200mA/70V")
      (footprint "eagle-import:SOT23-3")
      (libsource (lib "eagle-import") (part "BAV99"))
    )
    (comp (ref "D419")
      (value "200mA/70V")
      (footprint "eagle-import:SOT23-3")
      (libsource (lib "eagle-import") (part "BAV99"))
    )
    (comp (ref "D420")
      (value "200mA/70V")
      (footprint "eagle-import:SOT23-3")
      (libsource (lib "eagle-import") (part "BAV99"))
    )
    (comp (ref "D421")
      (value "200mA/70V")
      (footprint "eagle-import:SOT23-3")
      (libsource (lib "eagle-import") (part "BAV99"))
    )
    (comp (ref "D422")
      (value "200mA/70V")
      (footprint "eagle-import:SOT23-3")
      (libsource (lib "eagle-import") (part "BAV99"))
    )
    (comp (ref "D423")
      (value "200mA/70V")
      (footprint "eagle-import:SOT23-3")
      (libsource (lib "eagle-import") (part "BAV99"))
    )
    (comp (ref "D424")
      (value "200mA/70V")
      (footprint "eagle-import:SOT23-3")
      (libsource (lib "eagle-import") (part "BAV99"))
    )
    (comp (ref "D425")
      (value "200mA/70V")
      (footprint "eagle-import:SOT23-3")
      (libsource (lib "eagle-import") (part "BAV99"))
    )
    (comp (ref "D426")
      (value "200mA/70V")
      (footprint "eagle-import:SOT23-3")
      (libsource (lib "eagle-import") (part "BAV99"))
    )
    (comp (ref "D427")
      (value "200mA/70V")
      (footprint "eagle-import:SOT23-3")
      (libsource (lib "eagle-import") (part "BAV99"))
    )
    (comp (ref "D428")
      (value "200mA/70V")
      (footprint "eagle-import:SOT23-3")
      (libsource (lib "eagle-import") (part "BAV99"))
    )
    (comp (ref "D429")
      (value "200mA/70V")
      (footprint "eagle-import:SOT23-3")
      (libsource (lib "eagle-import") (part "BAV99"))
    )
    (comp (ref "D430")
      (value "200mA/70V")
      (footprint "eagle-import:SOT23-3")
      (libsource (lib "eagle-import") (part "BAV99"))
    )
    (comp (ref "D431")
      (value "200mA/70V")
      (footprint "eagle-import:SOT23-3")
      (libsource (lib "eagle-import") (part "BAV99"))
    )
    (comp (ref "D432")
      (value "200mA/70V")
      (footprint "eagle-import:SOT23-3")
      (libsource (lib "eagle-import") (part "BAV99"))
    )
    (comp (ref "D449")
      (value "200mA/70V")
      (footprint "eagle-import:SOT23-3")
      (libsource (lib "eagle-import") (part "BAV99"))
    )
    (comp (ref "D450")
      (value "200mA/70V")
      (footprint "eagle-import:SOT23-3")
      (libsource (lib "eagle-import") (part "BAV99"))
    )
    (comp (ref "D451")
      (value "200mA/70V")
      (footprint "eagle-import:SOT23-3")
      (libsource (lib "eagle-import") (part "BAV99"))
    )
    (comp (ref "D452")
      (value "200mA/70V")
      (footprint "eagle-import:SOT23-3")
      (libsource (lib "eagle-import") (part "BAV99"))
    )
    (comp (ref "D453")
      (value "200mA/70V")
      (footprint "eagle-import:SOT23-3")
      (libsource (lib "eagle-import") (part "BAV99"))
    )
    (comp (ref "D454")
      (value "200mA/70V")
      (footprint "eagle-import:SOT23-3")
      (libsource (lib "eagle-import") (part "BAV99"))
    )
    (comp (ref "D455")
      (value "200mA/70V")
      (footprint "eagle-import:SOT23-3")
      (libsource (lib "eagle-import") (part "BAV99"))
    )
    (comp (ref "D456")
      (value "200mA/70V")
      (footprint "eagle-import:SOT23-3")
      (libsource (lib "eagle-import") (part "BAV99"))
    )
    (comp (ref "D457")
      (value "200mA/70V")
      (footprint "eagle-import:SOT23-3")
      (libsource (lib "eagle-import") (part "BAV99"))
    )
    (comp (ref "D458")
      (value "200mA/70V")
      (footprint "eagle-import:SOT23-3")
      (libsource (lib "eagle-import") (part "BAV99"))
    )
    (comp (ref "D459")
      (value "200mA/70V")
      (footprint "eagle-import:SOT23-3")
      (libsource (lib "eagle-import") (part "BAV99"))
    )
    (comp (ref "D460")
      (value "200mA/70V")
      (footprint "eagle-import:SOT23-3")
      (libsource (lib "eagle-import") (part "BAV99"))
    )
    (comp (ref "D461")
      (value "200mA/70V")
      (footprint "eagle-import:SOT23-3")
      (libsource (lib "eagle-import") (part "BAV99"))
    )
    (comp (ref "D462")
      (value "200mA/70V")
      (footprint "eagle-import:SOT23-3")
      (libsource (lib "eagle-import") (part "BAV99"))
    )
    (comp (ref "D463")
      (value "200mA/70V")
      (footprint "eagle-import:SOT23-3")
      (libsource (lib "eagle-import") (part "BAV99"))
    )
    (comp (ref "D464")
      (value "200mA/70V")
      (footprint "eagle-import:SOT23-3")
      (libsource (lib "eagle-import") (part "BAV99"))
    )
    (comp (ref "D481")
      (value "200mA/70V")
      (footprint "eagle-import:SOT23-3")
      (libsource (lib "eagle-import") (part "BAV99"))
    )
    (comp (ref "D482")
      (value "200mA/70V")
      (footprint "eagle-import:SOT23-3")
      (libsource (lib "eagle-import") (part "BAV99"))
    )
    (comp (ref "D483")
      (value "200mA/70V")
      (footprint "eagle-import:SOT23-3")
      (libsource (lib "eagle-import") (part "BAV99"))
    )
    (comp (ref "D484")
      (value "200mA/70V")
      (footprint "eagle-import:SOT23-3")
      (libsource (lib "eagle-import") (part "BAV99"))
    )
    (comp (ref "D485")
      (value "200mA/70V")
      (footprint "eagle-import:SOT23-3")
      (libsource (lib "eagle-import") (part "BAV99"))
    )
    (comp (ref "D486")
      (value "200mA/70V")
      (footprint "eagle-import:SOT23-3")
      (libsource (lib "eagle-import") (part "BAV99"))
    )
    (comp (ref "D487")
      (value "200mA/70V")
      (footprint "eagle-import:SOT23-3")
      (libsource (lib "eagle-import") (part "BAV99"))
    )
    (comp (ref "D488")
      (value "200mA/70V")
      (footprint "eagle-import:SOT23-3")
      (libsource (lib "eagle-import") (part "BAV99"))
    )
    (comp (ref "D489")
      (value "200mA/70V")
      (footprint "eagle-import:SOT23-3")
      (libsource (lib "eagle-import") (part "BAV99"))
    )
    (comp (ref "D490")
      (value "200mA/70V")
      (footprint "eagle-import:SOT23-3")
      (libsource (lib "eagle-import") (part "BAV99"))
    )
    (comp (ref "D491")
      (value "200mA/70V")
      (footprint "eagle-import:SOT23-3")
      (libsource (lib "eagle-import") (part "BAV99"))
    )
    (comp (ref "D492")
      (value "200mA/70V")
      (footprint "eagle-import:SOT23-3")
      (libsource (lib "eagle-import") (part "BAV99"))
    )
    (comp (ref "D493")
      (value "200mA/70V")
      (footprint "eagle-import:SOT23-3")
      (libsource (lib "eagle-import") (part "BAV99"))
    )
    (comp (ref "D494")
      (value "200mA/70V")
      (footprint "eagle-import:SOT23-3")
      (libsource (lib "eagle-import") (part "BAV99"))
    )
    (comp (ref "D495")
      (value "200mA/70V")
      (footprint "eagle-import:SOT23-3")
      (libsource (lib "eagle-import") (part "BAV99"))
    )
    (comp (ref "D496")
      (value "200mA/70V")
      (footprint "eagle-import:SOT23-3")
      (libsource (lib "eagle-import") (part "BAV99"))
    )
    (comp (ref "L1")
      (value "SD8")
      (footprint "eagle-import:SD8")
      (libsource (lib "eagle-import") (part "SD8"))
    )
    (comp (ref "L2")
      (value "SD8")
      (footprint "eagle-import:SD8")
      (libsource (lib "eagle-import") (part "SD8"))
    )
    (comp (ref "L3")
      (value "SD8")
      (footprint "eagle-import:SD8")
      (libsource (lib "eagle-import") (part "SD8"))
    )
    (comp (ref "L4")
      (value "SD8")
      (footprint "eagle-import:SD8")
      (libsource (lib "eagle-import") (part "SD8"))
    )
    (comp (ref "L5")
      (value "SD8")
      (footprint "eagle-import:SD8")
      (libsource (lib "eagle-import") (part "SD8"))
    )
    (comp (ref "L6")
      (value "SD8")
      (footprint "eagle-import:SD8")
      (libsource (lib "eagle-import") (part "SD8"))
    )
    (comp (ref "L7")
      (value "SD8")
      (footprint "eagle-import:SD8")
      (libsource (lib "eagle-import") (part "SD8"))
    )
    (comp (ref "L8")
      (value "SD8")
      (footprint "eagle-import:SD8")
      (libsource (lib "eagle-import") (part "SD8"))
    )
    (comp (ref "L9")
      (value "SD8")
      (footprint "eagle-import:SD8")
      (libsource (lib "eagle-import") (part "SD8"))
    )
    (comp (ref "L10")
      (value "SD8")
      (footprint "eagle-import:SD8")
      (libsource (lib "eagle-import") (part "SD8"))
    )
    (comp (ref "L11")
      (value "SD8")
      (footprint "eagle-import:SD8")
      (libsource (lib "eagle-import") (part "SD8"))
    )
    (comp (ref "L12")
      (value "SD8")
      (footprint "eagle-import:SD8")
      (libsource (lib "eagle-import") (part "SD8"))
    )
    (comp (ref "L13")
      (value "SD8")
      (footprint "eagle-import:SD8")
      (libsource (lib "eagle-import") (part "SD8"))
    )
    (comp (ref "L14")
      (value "SD8")
      (footprint "eagle-import:SD8")
      (libsource (lib "eagle-import") (part "SD8"))
    )
    (comp (ref "L15")
      (value "SD8")
      (footprint "eagle-import:SD8")
      (libsource (lib "eagle-import") (part "SD8"))
    )
    (comp (ref "L16")
      (value "SD8")
      (footprint "eagle-import:SD8")
      (libsource (lib "eagle-import") (part "SD8"))
    )
    (comp (ref "L33")
      (value "SD8")
      (footprint "eagle-import:SD8")
      (libsource (lib "eagle-import") (part "SD8"))
    )
    (comp (ref "L34")
      (value "SD8")
      (footprint "eagle-import:SD8")
      (libsource (lib "eagle-import") (part "SD8"))
    )
    (comp (ref "L35")
      (value "SD8")
      (footprint "eagle-import:SD8")
      (libsource (lib "eagle-import") (part "SD8"))
    )
    (comp (ref "L36")
      (value "SD8")
      (footprint "eagle-import:SD8")
      (libsource (lib "eagle-import") (part "SD8"))
    )
    (comp (ref "L37")
      (value "SD8")
      (footprint "eagle-import:SD8")
      (libsource (lib "eagle-import") (part "SD8"))
    )
    (comp (ref "L38")
      (value "SD8")
      (footprint "eagle-import:SD8")
      (libsource (lib "eagle-import") (part "SD8"))
    )
    (comp (ref "L39")
      (value "SD8")
      (footprint "eagle-import:SD8")
      (libsource (lib "eagle-import") (part "SD8"))
    )
    (comp (ref "L40")
      (value "SD8")
      (footprint "eagle-import:SD8")
      (libsource (lib "eagle-import") (part "SD8"))
    )
    (comp (ref "L41")
      (value "SD8")
      (footprint "eagle-import:SD8")
      (libsource (lib "eagle-import") (part "SD8"))
    )
    (comp (ref "L42")
      (value "SD8")
      (footprint "eagle-import:SD8")
      (libsource (lib "eagle-import") (part "SD8"))
    )
    (comp (ref "L43")
      (value "SD8")
      (footprint "eagle-import:SD8")
      (libsource (lib "eagle-import") (part "SD8"))
    )
    (comp (ref "L44")
      (value "SD8")
      (footprint "eagle-import:SD8")
      (libsource (lib "eagle-import") (part "SD8"))
    )
    (comp (ref "L45")
      (value "SD8")
      (footprint "eagle-import:SD8")
      (libsource (lib "eagle-import") (part "SD8"))
    )
    (comp (ref "L46")
      (value "SD8")
      (footprint "eagle-import:SD8")
      (libsource (lib "eagle-import") (part "SD8"))
    )
    (comp (ref "L47")
      (value "SD8")
      (footprint "eagle-import:SD8")
      (libsource (lib "eagle-import") (part "SD8"))
    )
    (comp (ref "L48")
      (value "SD8")
      (footprint "eagle-import:SD8")
      (libsource (lib "eagle-import") (part "SD8"))
    )
    (comp (ref "L65")
      (value "SD8")
      (footprint "eagle-import:SD8")
      (libsource (lib "eagle-import") (part "SD8"))
    )
    (comp (ref "L66")
      (value "SD8")
      (footprint "eagle-import:SD8")
      (libsource (lib "eagle-import") (part "SD8"))
    )
    (comp (ref "L67")
      (value "SD8")
      (footprint "eagle-import:SD8")
      (libsource (lib "eagle-import") (part "SD8"))
    )
    (comp (ref "L68")
      (value "SD8")
      (footprint "eagle-import:SD8")
      (libsource (lib "eagle-import") (part "SD8"))
    )
    (comp (ref "L69")
      (value "SD8")
      (footprint "eagle-import:SD8")
      (libsource (lib "eagle-import") (part "SD8"))
    )
    (comp (ref "L70")
      (value "SD8")
      (footprint "eagle-import:SD8")
      (libsource (lib "eagle-import") (part "SD8"))
    )
    (comp (ref "L71")
      (value "SD8")
      (footprint "eagle-import:SD8")
      (libsource (lib "eagle-import") (part "SD8"))
    )
    (comp (ref "L72")
      (value "SD8")
      (footprint "eagle-import:SD8")
      (libsource (lib "eagle-import") (part "SD8"))
    )
    (comp (ref "L73")
      (value "SD8")
      (footprint "eagle-import:SD8")
      (libsource (lib "eagle-import") (part "SD8"))
    )
    (comp (ref "L74")
      (value "SD8")
      (footprint "eagle-import:SD8")
      (libsource (lib "eagle-import") (part "SD8"))
    )
    (comp (ref "L75")
      (value "SD8")
      (footprint "eagle-import:SD8")
      (libsource (lib "eagle-import") (part "SD8"))
    )
    (comp (ref "L76")
      (value "SD8")
      (footprint "eagle-import:SD8")
      (libsource (lib "eagle-import") (part "SD8"))
    )
    (comp (ref "L77")
      (value "SD8")
      (footprint "eagle-import:SD8")
      (libsource (lib "eagle-import") (part "SD8"))
    )
    (comp (ref "L78")
      (value "SD8")
      (footprint "eagle-import:SD8")
      (libsource (lib "eagle-import") (part "SD8"))
    )
    (comp (ref "L79")
      (value "SD8")
      (footprint "eagle-import:SD8")
      (libsource (lib "eagle-import") (part "SD8"))
    )
    (comp (ref "L80")
      (value "SD8")
      (footprint "eagle-import:SD8")
      (libsource (lib "eagle-import") (part "SD8"))
    )
    (comp (ref "L97")
      (value "SD8")
      (footprint "eagle-import:SD8")
      (libsource (lib "eagle-import") (part "SD8"))
    )
    (comp (ref "L98")
      (value "SD8")
      (footprint "eagle-import:SD8")
      (libsource (lib "eagle-import") (part "SD8"))
    )
    (comp (ref "L99")
      (value "SD8")
      (footprint "eagle-import:SD8")
      (libsource (lib "eagle-import") (part "SD8"))
    )
    (comp (ref "L100")
      (value "SD8")
      (footprint "eagle-import:SD8")
      (libsource (lib "eagle-import") (part "SD8"))
    )
    (comp (ref "L101")
      (value "SD8")
      (footprint "eagle-import:SD8")
      (libsource (lib "eagle-import") (part "SD8"))
    )
    (comp (ref "L102")
      (value "SD8")
      (footprint "eagle-import:SD8")
      (libsource (lib "eagle-import") (part "SD8"))
    )
    (comp (ref "L103")
      (value "SD8")
      (footprint "eagle-import:SD8")
      (libsource (lib "eagle-import") (part "SD8"))
    )
    (comp (ref "L104")
      (value "SD8")
      (footprint "eagle-import:SD8")
      (libsource (lib "eagle-import") (part "SD8"))
    )
    (comp (ref "L105")
      (value "SD8")
      (footprint "eagle-import:SD8")
      (libsource (lib "eagle-import") (part "SD8"))
    )
    (comp (ref "L106")
      (value "SD8")
      (footprint "eagle-import:SD8")
      (libsource (lib "eagle-import") (part "SD8"))
    )
    (comp (ref "L107")
      (value "SD8")
      (footprint "eagle-import:SD8")
      (libsource (lib "eagle-import") (part "SD8"))
    )
    (comp (ref "L108")
      (value "SD8")
      (footprint "eagle-import:SD8")
      (libsource (lib "eagle-import") (part "SD8"))
    )
    (comp (ref "L109")
      (value "SD8")
      (footprint "eagle-import:SD8")
      (libsource (lib "eagle-import") (part "SD8"))
    )
    (comp (ref "L110")
      (value "SD8")
      (footprint "eagle-import:SD8")
      (libsource (lib "eagle-import") (part "SD8"))
    )
    (comp (ref "L111")
      (value "SD8")
      (footprint "eagle-import:SD8")
      (libsource (lib "eagle-import") (part "SD8"))
    )
    (comp (ref "L112")
      (value "SD8")
      (footprint "eagle-import:SD8")
      (libsource (lib "eagle-import") (part "SD8"))
    )
    (comp (ref "L129")
      (value "SD8")
      (footprint "eagle-import:SD8")
      (libsource (lib "eagle-import") (part "SD8"))
    )
    (comp (ref "L130")
      (value "SD8")
      (footprint "eagle-import:SD8")
      (libsource (lib "eagle-import") (part "SD8"))
    )
    (comp (ref "L131")
      (value "SD8")
      (footprint "eagle-import:SD8")
      (libsource (lib "eagle-import") (part "SD8"))
    )
    (comp (ref "L132")
      (value "SD8")
      (footprint "eagle-import:SD8")
      (libsource (lib "eagle-import") (part "SD8"))
    )
    (comp (ref "L133")
      (value "SD8")
      (footprint "eagle-import:SD8")
      (libsource (lib "eagle-import") (part "SD8"))
    )
    (comp (ref "L134")
      (value "SD8")
      (footprint "eagle-import:SD8")
      (libsource (lib "eagle-import") (part "SD8"))
    )
    (comp (ref "L135")
      (value "SD8")
      (footprint "eagle-import:SD8")
      (libsource (lib "eagle-import") (part "SD8"))
    )
    (comp (ref "L136")
      (value "SD8")
      (footprint "eagle-import:SD8")
      (libsource (lib "eagle-import") (part "SD8"))
    )
    (comp (ref "L137")
      (value "SD8")
      (footprint "eagle-import:SD8")
      (libsource (lib "eagle-import") (part "SD8"))
    )
    (comp (ref "L138")
      (value "SD8")
      (footprint "eagle-import:SD8")
      (libsource (lib "eagle-import") (part "SD8"))
    )
    (comp (ref "L139")
      (value "SD8")
      (footprint "eagle-import:SD8")
      (libsource (lib "eagle-import") (part "SD8"))
    )
    (comp (ref "L140")
      (value "SD8")
      (footprint "eagle-import:SD8")
      (libsource (lib "eagle-import") (part "SD8"))
    )
    (comp (ref "L141")
      (value "SD8")
      (footprint "eagle-import:SD8")
      (libsource (lib "eagle-import") (part "SD8"))
    )
    (comp (ref "L142")
      (value "SD8")
      (footprint "eagle-import:SD8")
      (libsource (lib "eagle-import") (part "SD8"))
    )
    (comp (ref "L143")
      (value "SD8")
      (footprint "eagle-import:SD8")
      (libsource (lib "eagle-import") (part "SD8"))
    )
    (comp (ref "L144")
      (value "SD8")
      (footprint "eagle-import:SD8")
      (libsource (lib "eagle-import") (part "SD8"))
    )
    (comp (ref "L161")
      (value "SD8")
      (footprint "eagle-import:SD8")
      (libsource (lib "eagle-import") (part "SD8"))
    )
    (comp (ref "L162")
      (value "SD8")
      (footprint "eagle-import:SD8")
      (libsource (lib "eagle-import") (part "SD8"))
    )
    (comp (ref "L163")
      (value "SD8")
      (footprint "eagle-import:SD8")
      (libsource (lib "eagle-import") (part "SD8"))
    )
    (comp (ref "L164")
      (value "SD8")
      (footprint "eagle-import:SD8")
      (libsource (lib "eagle-import") (part "SD8"))
    )
    (comp (ref "L165")
      (value "SD8")
      (footprint "eagle-import:SD8")
      (libsource (lib "eagle-import") (part "SD8"))
    )
    (comp (ref "L166")
      (value "SD8")
      (footprint "eagle-import:SD8")
      (libsource (lib "eagle-import") (part "SD8"))
    )
    (comp (ref "L167")
      (value "SD8")
      (footprint "eagle-import:SD8")
      (libsource (lib "eagle-import") (part "SD8"))
    )
    (comp (ref "L168")
      (value "SD8")
      (footprint "eagle-import:SD8")
      (libsource (lib "eagle-import") (part "SD8"))
    )
    (comp (ref "L169")
      (value "SD8")
      (footprint "eagle-import:SD8")
      (libsource (lib "eagle-import") (part "SD8"))
    )
    (comp (ref "L170")
      (value "SD8")
      (footprint "eagle-import:SD8")
      (libsource (lib "eagle-import") (part "SD8"))
    )
    (comp (ref "L171")
      (value "SD8")
      (footprint "eagle-import:SD8")
      (libsource (lib "eagle-import") (part "SD8"))
    )
    (comp (ref "L172")
      (value "SD8")
      (footprint "eagle-import:SD8")
      (libsource (lib "eagle-import") (part "SD8"))
    )
    (comp (ref "L173")
      (value "SD8")
      (footprint "eagle-import:SD8")
      (libsource (lib "eagle-import") (part "SD8"))
    )
    (comp (ref "L174")
      (value "SD8")
      (footprint "eagle-import:SD8")
      (libsource (lib "eagle-import") (part "SD8"))
    )
    (comp (ref "L175")
      (value "SD8")
      (footprint "eagle-import:SD8")
      (libsource (lib "eagle-import") (part "SD8"))
    )
    (comp (ref "L176")
      (value "SD8")
      (footprint "eagle-import:SD8")
      (libsource (lib "eagle-import") (part "SD8"))
    )
    (comp (ref "L193")
      (value "SD8")
      (footprint "eagle-import:SD8")
      (libsource (lib "eagle-import") (part "SD8"))
    )
    (comp (ref "L194")
      (value "SD8")
      (footprint "eagle-import:SD8")
      (libsource (lib "eagle-import") (part "SD8"))
    )
    (comp (ref "L195")
      (value "SD8")
      (footprint "eagle-import:SD8")
      (libsource (lib "eagle-import") (part "SD8"))
    )
    (comp (ref "L196")
      (value "SD8")
      (footprint "eagle-import:SD8")
      (libsource (lib "eagle-import") (part "SD8"))
    )
    (comp (ref "L197")
      (value "SD8")
      (footprint "eagle-import:SD8")
      (libsource (lib "eagle-import") (part "SD8"))
    )
    (comp (ref "L198")
      (value "SD8")
      (footprint "eagle-import:SD8")
      (libsource (lib "eagle-import") (part "SD8"))
    )
    (comp (ref "L199")
      (value "SD8")
      (footprint "eagle-import:SD8")
      (libsource (lib "eagle-import") (part "SD8"))
    )
    (comp (ref "L200")
      (value "SD8")
      (footprint "eagle-import:SD8")
      (libsource (lib "eagle-import") (part "SD8"))
    )
    (comp (ref "L201")
      (value "SD8")
      (footprint "eagle-import:SD8")
      (libsource (lib "eagle-import") (part "SD8"))
    )
    (comp (ref "L202")
      (value "SD8")
      (footprint "eagle-import:SD8")
      (libsource (lib "eagle-import") (part "SD8"))
    )
    (comp (ref "L203")
      (value "SD8")
      (footprint "eagle-import:SD8")
      (libsource (lib "eagle-import") (part "SD8"))
    )
    (comp (ref "L204")
      (value "SD8")
      (footprint "eagle-import:SD8")
      (libsource (lib "eagle-import") (part "SD8"))
    )
    (comp (ref "L205")
      (value "SD8")
      (footprint "eagle-import:SD8")
      (libsource (lib "eagle-import") (part "SD8"))
    )
    (comp (ref "L206")
      (value "SD8")
      (footprint "eagle-import:SD8")
      (libsource (lib "eagle-import") (part "SD8"))
    )
    (comp (ref "L207")
      (value "SD8")
      (footprint "eagle-import:SD8")
      (libsource (lib "eagle-import") (part "SD8"))
    )
    (comp (ref "L208")
      (value "SD8")
      (footprint "eagle-import:SD8")
      (libsource (lib "eagle-import") (part "SD8"))
    )
    (comp (ref "L225")
      (value "SD8")
      (footprint "eagle-import:SD8")
      (libsource (lib "eagle-import") (part "SD8"))
    )
    (comp (ref "L226")
      (value "SD8")
      (footprint "eagle-import:SD8")
      (libsource (lib "eagle-import") (part "SD8"))
    )
    (comp (ref "L227")
      (value "SD8")
      (footprint "eagle-import:SD8")
      (libsource (lib "eagle-import") (part "SD8"))
    )
    (comp (ref "L228")
      (value "SD8")
      (footprint "eagle-import:SD8")
      (libsource (lib "eagle-import") (part "SD8"))
    )
    (comp (ref "L229")
      (value "SD8")
      (footprint "eagle-import:SD8")
      (libsource (lib "eagle-import") (part "SD8"))
    )
    (comp (ref "L230")
      (value "SD8")
      (footprint "eagle-import:SD8")
      (libsource (lib "eagle-import") (part "SD8"))
    )
    (comp (ref "L231")
      (value "SD8")
      (footprint "eagle-import:SD8")
      (libsource (lib "eagle-import") (part "SD8"))
    )
    (comp (ref "L232")
      (value "SD8")
      (footprint "eagle-import:SD8")
      (libsource (lib "eagle-import") (part "SD8"))
    )
    (comp (ref "L233")
      (value "SD8")
      (footprint "eagle-import:SD8")
      (libsource (lib "eagle-import") (part "SD8"))
    )
    (comp (ref "L234")
      (value "SD8")
      (footprint "eagle-import:SD8")
      (libsource (lib "eagle-import") (part "SD8"))
    )
    (comp (ref "L235")
      (value "SD8")
      (footprint "eagle-import:SD8")
      (libsource (lib "eagle-import") (part "SD8"))
    )
    (comp (ref "L236")
      (value "SD8")
      (footprint "eagle-import:SD8")
      (libsource (lib "eagle-import") (part "SD8"))
    )
    (comp (ref "L237")
      (value "SD8")
      (footprint "eagle-import:SD8")
      (libsource (lib "eagle-import") (part "SD8"))
    )
    (comp (ref "L238")
      (value "SD8")
      (footprint "eagle-import:SD8")
      (libsource (lib "eagle-import") (part "SD8"))
    )
    (comp (ref "L239")
      (value "SD8")
      (footprint "eagle-import:SD8")
      (libsource (lib "eagle-import") (part "SD8"))
    )
    (comp (ref "L240")
      (value "SD8")
      (footprint "eagle-import:SD8")
      (libsource (lib "eagle-import") (part "SD8"))
    )
    (comp (ref "L257")
      (value "SD8")
      (footprint "eagle-import:SD8")
      (libsource (lib "eagle-import") (part "SD8"))
    )
    (comp (ref "L258")
      (value "SD8")
      (footprint "eagle-import:SD8")
      (libsource (lib "eagle-import") (part "SD8"))
    )
    (comp (ref "L259")
      (value "SD8")
      (footprint "eagle-import:SD8")
      (libsource (lib "eagle-import") (part "SD8"))
    )
    (comp (ref "L260")
      (value "SD8")
      (footprint "eagle-import:SD8")
      (libsource (lib "eagle-import") (part "SD8"))
    )
    (comp (ref "L261")
      (value "SD8")
      (footprint "eagle-import:SD8")
      (libsource (lib "eagle-import") (part "SD8"))
    )
    (comp (ref "L262")
      (value "SD8")
      (footprint "eagle-import:SD8")
      (libsource (lib "eagle-import") (part "SD8"))
    )
    (comp (ref "L263")
      (value "SD8")
      (footprint "eagle-import:SD8")
      (libsource (lib "eagle-import") (part "SD8"))
    )
    (comp (ref "L264")
      (value "SD8")
      (footprint "eagle-import:SD8")
      (libsource (lib "eagle-import") (part "SD8"))
    )
    (comp (ref "L265")
      (value "SD8")
      (footprint "eagle-import:SD8")
      (libsource (lib "eagle-import") (part "SD8"))
    )
    (comp (ref "L266")
      (value "SD8")
      (footprint "eagle-import:SD8")
      (libsource (lib "eagle-import") (part "SD8"))
    )
    (comp (ref "L267")
      (value "SD8")
      (footprint "eagle-import:SD8")
      (libsource (lib "eagle-import") (part "SD8"))
    )
    (comp (ref "L268")
      (value "SD8")
      (footprint "eagle-import:SD8")
      (libsource (lib "eagle-import") (part "SD8"))
    )
    (comp (ref "L269")
      (value "SD8")
      (footprint "eagle-import:SD8")
      (libsource (lib "eagle-import") (part "SD8"))
    )
    (comp (ref "L270")
      (value "SD8")
      (footprint "eagle-import:SD8")
      (libsource (lib "eagle-import") (part "SD8"))
    )
    (comp (ref "L271")
      (value "SD8")
      (footprint "eagle-import:SD8")
      (libsource (lib "eagle-import") (part "SD8"))
    )
    (comp (ref "L272")
      (value "SD8")
      (footprint "eagle-import:SD8")
      (libsource (lib "eagle-import") (part "SD8"))
    )
    (comp (ref "L289")
      (value "SD8")
      (footprint "eagle-import:SD8")
      (libsource (lib "eagle-import") (part "SD8"))
    )
    (comp (ref "L290")
      (value "SD8")
      (footprint "eagle-import:SD8")
      (libsource (lib "eagle-import") (part "SD8"))
    )
    (comp (ref "L291")
      (value "SD8")
      (footprint "eagle-import:SD8")
      (libsource (lib "eagle-import") (part "SD8"))
    )
    (comp (ref "L292")
      (value "SD8")
      (footprint "eagle-import:SD8")
      (libsource (lib "eagle-import") (part "SD8"))
    )
    (comp (ref "L293")
      (value "SD8")
      (footprint "eagle-import:SD8")
      (libsource (lib "eagle-import") (part "SD8"))
    )
    (comp (ref "L294")
      (value "SD8")
      (footprint "eagle-import:SD8")
      (libsource (lib "eagle-import") (part "SD8"))
    )
    (comp (ref "L295")
      (value "SD8")
      (footprint "eagle-import:SD8")
      (libsource (lib "eagle-import") (part "SD8"))
    )
    (comp (ref "L296")
      (value "SD8")
      (footprint "eagle-import:SD8")
      (libsource (lib "eagle-import") (part "SD8"))
    )
    (comp (ref "L297")
      (value "SD8")
      (footprint "eagle-import:SD8")
      (libsource (lib "eagle-import") (part "SD8"))
    )
    (comp (ref "L298")
      (value "SD8")
      (footprint "eagle-import:SD8")
      (libsource (lib "eagle-import") (part "SD8"))
    )
    (comp (ref "L299")
      (value "SD8")
      (footprint "eagle-import:SD8")
      (libsource (lib "eagle-import") (part "SD8"))
    )
    (comp (ref "L300")
      (value "SD8")
      (footprint "eagle-import:SD8")
      (libsource (lib "eagle-import") (part "SD8"))
    )
    (comp (ref "L301")
      (value "SD8")
      (footprint "eagle-import:SD8")
      (libsource (lib "eagle-import") (part "SD8"))
    )
    (comp (ref "L302")
      (value "SD8")
      (footprint "eagle-import:SD8")
      (libsource (lib "eagle-import") (part "SD8"))
    )
    (comp (ref "L303")
      (value "SD8")
      (footprint "eagle-import:SD8")
      (libsource (lib "eagle-import") (part "SD8"))
    )
    (comp (ref "L304")
      (value "SD8")
      (footprint "eagle-import:SD8")
      (libsource (lib "eagle-import") (part "SD8"))
    )
    (comp (ref "L321")
      (value "SD8")
      (footprint "eagle-import:SD8")
      (libsource (lib "eagle-import") (part "SD8"))
    )
    (comp (ref "L322")
      (value "SD8")
      (footprint "eagle-import:SD8")
      (libsource (lib "eagle-import") (part "SD8"))
    )
    (comp (ref "L323")
      (value "SD8")
      (footprint "eagle-import:SD8")
      (libsource (lib "eagle-import") (part "SD8"))
    )
    (comp (ref "L324")
      (value "SD8")
      (footprint "eagle-import:SD8")
      (libsource (lib "eagle-import") (part "SD8"))
    )
    (comp (ref "L325")
      (value "SD8")
      (footprint "eagle-import:SD8")
      (libsource (lib "eagle-import") (part "SD8"))
    )
    (comp (ref "L326")
      (value "SD8")
      (footprint "eagle-import:SD8")
      (libsource (lib "eagle-import") (part "SD8"))
    )
    (comp (ref "L327")
      (value "SD8")
      (footprint "eagle-import:SD8")
      (libsource (lib "eagle-import") (part "SD8"))
    )
    (comp (ref "L328")
      (value "SD8")
      (footprint "eagle-import:SD8")
      (libsource (lib "eagle-import") (part "SD8"))
    )
    (comp (ref "L329")
      (value "SD8")
      (footprint "eagle-import:SD8")
      (libsource (lib "eagle-import") (part "SD8"))
    )
    (comp (ref "L330")
      (value "SD8")
      (footprint "eagle-import:SD8")
      (libsource (lib "eagle-import") (part "SD8"))
    )
    (comp (ref "L331")
      (value "SD8")
      (footprint "eagle-import:SD8")
      (libsource (lib "eagle-import") (part "SD8"))
    )
    (comp (ref "L332")
      (value "SD8")
      (footprint "eagle-import:SD8")
      (libsource (lib "eagle-import") (part "SD8"))
    )
    (comp (ref "L333")
      (value "SD8")
      (footprint "eagle-import:SD8")
      (libsource (lib "eagle-import") (part "SD8"))
    )
    (comp (ref "L334")
      (value "SD8")
      (footprint "eagle-import:SD8")
      (libsource (lib "eagle-import") (part "SD8"))
    )
    (comp (ref "L335")
      (value "SD8")
      (footprint "eagle-import:SD8")
      (libsource (lib "eagle-import") (part "SD8"))
    )
    (comp (ref "L336")
      (value "SD8")
      (footprint "eagle-import:SD8")
      (libsource (lib "eagle-import") (part "SD8"))
    )
    (comp (ref "L353")
      (value "SD8")
      (footprint "eagle-import:SD8")
      (libsource (lib "eagle-import") (part "SD8"))
    )
    (comp (ref "L354")
      (value "SD8")
      (footprint "eagle-import:SD8")
      (libsource (lib "eagle-import") (part "SD8"))
    )
    (comp (ref "L355")
      (value "SD8")
      (footprint "eagle-import:SD8")
      (libsource (lib "eagle-import") (part "SD8"))
    )
    (comp (ref "L356")
      (value "SD8")
      (footprint "eagle-import:SD8")
      (libsource (lib "eagle-import") (part "SD8"))
    )
    (comp (ref "L357")
      (value "SD8")
      (footprint "eagle-import:SD8")
      (libsource (lib "eagle-import") (part "SD8"))
    )
    (comp (ref "L358")
      (value "SD8")
      (footprint "eagle-import:SD8")
      (libsource (lib "eagle-import") (part "SD8"))
    )
    (comp (ref "L359")
      (value "SD8")
      (footprint "eagle-import:SD8")
      (libsource (lib "eagle-import") (part "SD8"))
    )
    (comp (ref "L360")
      (value "SD8")
      (footprint "eagle-import:SD8")
      (libsource (lib "eagle-import") (part "SD8"))
    )
    (comp (ref "L361")
      (value "SD8")
      (footprint "eagle-import:SD8")
      (libsource (lib "eagle-import") (part "SD8"))
    )
    (comp (ref "L362")
      (value "SD8")
      (footprint "eagle-import:SD8")
      (libsource (lib "eagle-import") (part "SD8"))
    )
    (comp (ref "L363")
      (value "SD8")
      (footprint "eagle-import:SD8")
      (libsource (lib "eagle-import") (part "SD8"))
    )
    (comp (ref "L364")
      (value "SD8")
      (footprint "eagle-import:SD8")
      (libsource (lib "eagle-import") (part "SD8"))
    )
    (comp (ref "L365")
      (value "SD8")
      (footprint "eagle-import:SD8")
      (libsource (lib "eagle-import") (part "SD8"))
    )
    (comp (ref "L366")
      (value "SD8")
      (footprint "eagle-import:SD8")
      (libsource (lib "eagle-import") (part "SD8"))
    )
    (comp (ref "L367")
      (value "SD8")
      (footprint "eagle-import:SD8")
      (libsource (lib "eagle-import") (part "SD8"))
    )
    (comp (ref "L368")
      (value "SD8")
      (footprint "eagle-import:SD8")
      (libsource (lib "eagle-import") (part "SD8"))
    )
    (comp (ref "L385")
      (value "SD8")
      (footprint "eagle-import:SD8")
      (libsource (lib "eagle-import") (part "SD8"))
    )
    (comp (ref "L386")
      (value "SD8")
      (footprint "eagle-import:SD8")
      (libsource (lib "eagle-import") (part "SD8"))
    )
    (comp (ref "L387")
      (value "SD8")
      (footprint "eagle-import:SD8")
      (libsource (lib "eagle-import") (part "SD8"))
    )
    (comp (ref "L388")
      (value "SD8")
      (footprint "eagle-import:SD8")
      (libsource (lib "eagle-import") (part "SD8"))
    )
    (comp (ref "L389")
      (value "SD8")
      (footprint "eagle-import:SD8")
      (libsource (lib "eagle-import") (part "SD8"))
    )
    (comp (ref "L390")
      (value "SD8")
      (footprint "eagle-import:SD8")
      (libsource (lib "eagle-import") (part "SD8"))
    )
    (comp (ref "L391")
      (value "SD8")
      (footprint "eagle-import:SD8")
      (libsource (lib "eagle-import") (part "SD8"))
    )
    (comp (ref "L392")
      (value "SD8")
      (footprint "eagle-import:SD8")
      (libsource (lib "eagle-import") (part "SD8"))
    )
    (comp (ref "L393")
      (value "SD8")
      (footprint "eagle-import:SD8")
      (libsource (lib "eagle-import") (part "SD8"))
    )
    (comp (ref "L394")
      (value "SD8")
      (footprint "eagle-import:SD8")
      (libsource (lib "eagle-import") (part "SD8"))
    )
    (comp (ref "L395")
      (value "SD8")
      (footprint "eagle-import:SD8")
      (libsource (lib "eagle-import") (part "SD8"))
    )
    (comp (ref "L396")
      (value "SD8")
      (footprint "eagle-import:SD8")
      (libsource (lib "eagle-import") (part "SD8"))
    )
    (comp (ref "L397")
      (value "SD8")
      (footprint "eagle-import:SD8")
      (libsource (lib "eagle-import") (part "SD8"))
    )
    (comp (ref "L398")
      (value "SD8")
      (footprint "eagle-import:SD8")
      (libsource (lib "eagle-import") (part "SD8"))
    )
    (comp (ref "L399")
      (value "SD8")
      (footprint "eagle-import:SD8")
      (libsource (lib "eagle-import") (part "SD8"))
    )
    (comp (ref "L400")
      (value "SD8")
      (footprint "eagle-import:SD8")
      (libsource (lib "eagle-import") (part "SD8"))
    )
    (comp (ref "L417")
      (value "SD8")
      (footprint "eagle-import:SD8")
      (libsource (lib "eagle-import") (part "SD8"))
    )
    (comp (ref "L418")
      (value "SD8")
      (footprint "eagle-import:SD8")
      (libsource (lib "eagle-import") (part "SD8"))
    )
    (comp (ref "L419")
      (value "SD8")
      (footprint "eagle-import:SD8")
      (libsource (lib "eagle-import") (part "SD8"))
    )
    (comp (ref "L420")
      (value "SD8")
      (footprint "eagle-import:SD8")
      (libsource (lib "eagle-import") (part "SD8"))
    )
    (comp (ref "L421")
      (value "SD8")
      (footprint "eagle-import:SD8")
      (libsource (lib "eagle-import") (part "SD8"))
    )
    (comp (ref "L422")
      (value "SD8")
      (footprint "eagle-import:SD8")
      (libsource (lib "eagle-import") (part "SD8"))
    )
    (comp (ref "L423")
      (value "SD8")
      (footprint "eagle-import:SD8")
      (libsource (lib "eagle-import") (part "SD8"))
    )
    (comp (ref "L424")
      (value "SD8")
      (footprint "eagle-import:SD8")
      (libsource (lib "eagle-import") (part "SD8"))
    )
    (comp (ref "L425")
      (value "SD8")
      (footprint "eagle-import:SD8")
      (libsource (lib "eagle-import") (part "SD8"))
    )
    (comp (ref "L426")
      (value "SD8")
      (footprint "eagle-import:SD8")
      (libsource (lib "eagle-import") (part "SD8"))
    )
    (comp (ref "L427")
      (value "SD8")
      (footprint "eagle-import:SD8")
      (libsource (lib "eagle-import") (part "SD8"))
    )
    (comp (ref "L428")
      (value "SD8")
      (footprint "eagle-import:SD8")
      (libsource (lib "eagle-import") (part "SD8"))
    )
    (comp (ref "L429")
      (value "SD8")
      (footprint "eagle-import:SD8")
      (libsource (lib "eagle-import") (part "SD8"))
    )
    (comp (ref "L430")
      (value "SD8")
      (footprint "eagle-import:SD8")
      (libsource (lib "eagle-import") (part "SD8"))
    )
    (comp (ref "L431")
      (value "SD8")
      (footprint "eagle-import:SD8")
      (libsource (lib "eagle-import") (part "SD8"))
    )
    (comp (ref "L432")
      (value "SD8")
      (footprint "eagle-import:SD8")
      (libsource (lib "eagle-import") (part "SD8"))
    )
    (comp (ref "L449")
      (value "SD8")
      (footprint "eagle-import:SD8")
      (libsource (lib "eagle-import") (part "SD8"))
    )
    (comp (ref "L450")
      (value "SD8")
      (footprint "eagle-import:SD8")
      (libsource (lib "eagle-import") (part "SD8"))
    )
    (comp (ref "L451")
      (value "SD8")
      (footprint "eagle-import:SD8")
      (libsource (lib "eagle-import") (part "SD8"))
    )
    (comp (ref "L452")
      (value "SD8")
      (footprint "eagle-import:SD8")
      (libsource (lib "eagle-import") (part "SD8"))
    )
    (comp (ref "L453")
      (value "SD8")
      (footprint "eagle-import:SD8")
      (libsource (lib "eagle-import") (part "SD8"))
    )
    (comp (ref "L454")
      (value "SD8")
      (footprint "eagle-import:SD8")
      (libsource (lib "eagle-import") (part "SD8"))
    )
    (comp (ref "L455")
      (value "SD8")
      (footprint "eagle-import:SD8")
      (libsource (lib "eagle-import") (part "SD8"))
    )
    (comp (ref "L456")
      (value "SD8")
      (footprint "eagle-import:SD8")
      (libsource (lib "eagle-import") (part "SD8"))
    )
    (comp (ref "L457")
      (value "SD8")
      (footprint "eagle-import:SD8")
      (libsource (lib "eagle-import") (part "SD8"))
    )
    (comp (ref "L458")
      (value "SD8")
      (footprint "eagle-import:SD8")
      (libsource (lib "eagle-import") (part "SD8"))
    )
    (comp (ref "L459")
      (value "SD8")
      (footprint "eagle-import:SD8")
      (libsource (lib "eagle-import") (part "SD8"))
    )
    (comp (ref "L460")
      (value "SD8")
      (footprint "eagle-import:SD8")
      (libsource (lib "eagle-import") (part "SD8"))
    )
    (comp (ref "L461")
      (value "SD8")
      (footprint "eagle-import:SD8")
      (libsource (lib "eagle-import") (part "SD8"))
    )
    (comp (ref "L462")
      (value "SD8")
      (footprint "eagle-import:SD8")
      (libsource (lib "eagle-import") (part "SD8"))
    )
    (comp (ref "L463")
      (value "SD8")
      (footprint "eagle-import:SD8")
      (libsource (lib "eagle-import") (part "SD8"))
    )
    (comp (ref "L464")
      (value "SD8")
      (footprint "eagle-import:SD8")
      (libsource (lib "eagle-import") (part "SD8"))
    )
    (comp (ref "L481")
      (value "SD8")
      (footprint "eagle-import:SD8")
      (libsource (lib "eagle-import") (part "SD8"))
    )
    (comp (ref "L482")
      (value "SD8")
      (footprint "eagle-import:SD8")
      (libsource (lib "eagle-import") (part "SD8"))
    )
    (comp (ref "L483")
      (value "SD8")
      (footprint "eagle-import:SD8")
      (libsource (lib "eagle-import") (part "SD8"))
    )
    (comp (ref "L484")
      (value "SD8")
      (footprint "eagle-import:SD8")
      (libsource (lib "eagle-import") (part "SD8"))
    )
    (comp (ref "L485")
      (value "SD8")
      (footprint "eagle-import:SD8")
      (libsource (lib "eagle-import") (part "SD8"))
    )
    (comp (ref "L486")
      (value "SD8")
      (footprint "eagle-import:SD8")
      (libsource (lib "eagle-import") (part "SD8"))
    )
    (comp (ref "L487")
      (value "SD8")
      (footprint "eagle-import:SD8")
      (libsource (lib "eagle-import") (part "SD8"))
    )
    (comp (ref "L488")
      (value "SD8")
      (footprint "eagle-import:SD8")
      (libsource (lib "eagle-import") (part "SD8"))
    )
    (comp (ref "L489")
      (value "SD8")
      (footprint "eagle-import:SD8")
      (libsource (lib "eagle-import") (part "SD8"))
    )
    (comp (ref "L490")
      (value "SD8")
      (footprint "eagle-import:SD8")
      (libsource (lib "eagle-import") (part "SD8"))
    )
    (comp (ref "L491")
      (value "SD8")
      (footprint "eagle-import:SD8")
      (libsource (lib "eagle-import") (part "SD8"))
    )
    (comp (ref "L492")
      (value "SD8")
      (footprint "eagle-import:SD8")
      (libsource (lib "eagle-import") (part "SD8"))
    )
    (comp (ref "L493")
      (value "SD8")
      (footprint "eagle-import:SD8")
      (libsource (lib "eagle-import") (part "SD8"))
    )
    (comp (ref "L494")
      (value "SD8")
      (footprint "eagle-import:SD8")
      (libsource (lib "eagle-import") (part "SD8"))
    )
    (comp (ref "L495")
      (value "SD8")
      (footprint "eagle-import:SD8")
      (libsource (lib "eagle-import") (part "SD8"))
    )
    (comp (ref "L496")
      (value "SD8")
      (footprint "eagle-import:SD8")
      (libsource (lib "eagle-import") (part "SD8"))
    )
    (comp (ref "CONN1")
      (value "MICS-SMD14")
      (footprint "eagle-import:MICSMD14")
      (libsource (lib "eagle-import") (part "MICS-SMD14"))
    )
    (comp (ref "CONN2")
      (value "MICS-SMD14")
      (footprint "eagle-import:MICSMD14")
      (libsource (lib "eagle-import") (part "MICS-SMD14"))
    )
    (comp (ref "IC1")
      (value "74HC75D")
      (footprint "eagle-import:SO16")
      (libsource (lib "eagle-import") (part "7475DHC"))
    )
    (comp (ref "IC2")
      (value "4024D")
      (footprint "eagle-import:SO14")
      (libsource (lib "eagle-import") (part "4024D"))
    )
    (comp (ref "IC3")
      (value "74HC139D")
      (footprint "eagle-import:SO16")
      (fields (field (name "SPICEPREFIX") "X"))
      (libsource (lib "eagle-import") (part "74139DHC"))
    )
    (comp (ref "IC4")
      (value "4024D")
      (footprint "eagle-import:SO14")
      (libsource (lib "eagle-import") (part "4024D"))
    )
    (comp (ref "D17")
      (value "200mA/70V")
      (footprint "eagle-import:SOT23-3")
      (libsource (lib "eagle-import") (part "BAV99"))
    )
    (comp (ref "D18")
      (value "200mA/70V")
      (footprint "eagle-import:SOT23-3")
      (libsource (lib "eagle-import") (part "BAV99"))
    )
    (comp (ref "D19")
      (value "200mA/70V")
      (footprint "eagle-import:SOT23-3")
      (libsource (lib "eagle-import") (part "BAV99"))
    )
    (comp (ref "D20")
      (value "200mA/70V")
      (footprint "eagle-import:SOT23-3")
      (libsource (lib "eagle-import") (part "BAV99"))
    )
    (comp (ref "D21")
      (value "200mA/70V")
      (footprint "eagle-import:SOT23-3")
      (libsource (lib "eagle-import") (part "BAV99"))
    )
    (comp (ref "D22")
      (value "200mA/70V")
      (footprint "eagle-import:SOT23-3")
      (libsource (lib "eagle-import") (part "BAV99"))
    )
    (comp (ref "D23")
      (value "200mA/70V")
      (footprint "eagle-import:SOT23-3")
      (libsource (lib "eagle-import") (part "BAV99"))
    )
    (comp (ref "D24")
      (value "200mA/70V")
      (footprint "eagle-import:SOT23-3")
      (libsource (lib "eagle-import") (part "BAV99"))
    )
    (comp (ref "D25")
      (value "200mA/70V")
      (footprint "eagle-import:SOT23-3")
      (libsource (lib "eagle-import") (part "BAV99"))
    )
    (comp (ref "D26")
      (value "200mA/70V")
      (footprint "eagle-import:SOT23-3")
      (libsource (lib "eagle-import") (part "BAV99"))
    )
    (comp (ref "D27")
      (value "200mA/70V")
      (footprint "eagle-import:SOT23-3")
      (libsource (lib "eagle-import") (part "BAV99"))
    )
    (comp (ref "D28")
      (value "200mA/70V")
      (footprint "eagle-import:SOT23-3")
      (libsource (lib "eagle-import") (part "BAV99"))
    )
    (comp (ref "D29")
      (value "200mA/70V")
      (footprint "eagle-import:SOT23-3")
      (libsource (lib "eagle-import") (part "BAV99"))
    )
    (comp (ref "D30")
      (value "200mA/70V")
      (footprint "eagle-import:SOT23-3")
      (libsource (lib "eagle-import") (part "BAV99"))
    )
    (comp (ref "D31")
      (value "200mA/70V")
      (footprint "eagle-import:SOT23-3")
      (libsource (lib "eagle-import") (part "BAV99"))
    )
    (comp (ref "D32")
      (value "200mA/70V")
      (footprint "eagle-import:SOT23-3")
      (libsource (lib "eagle-import") (part "BAV99"))
    )
    (comp (ref "D49")
      (value "200mA/70V")
      (footprint "eagle-import:SOT23-3")
      (libsource (lib "eagle-import") (part "BAV99"))
    )
    (comp (ref "D50")
      (value "200mA/70V")
      (footprint "eagle-import:SOT23-3")
      (libsource (lib "eagle-import") (part "BAV99"))
    )
    (comp (ref "D51")
      (value "200mA/70V")
      (footprint "eagle-import:SOT23-3")
      (libsource (lib "eagle-import") (part "BAV99"))
    )
    (comp (ref "D52")
      (value "200mA/70V")
      (footprint "eagle-import:SOT23-3")
      (libsource (lib "eagle-import") (part "BAV99"))
    )
    (comp (ref "D53")
      (value "200mA/70V")
      (footprint "eagle-import:SOT23-3")
      (libsource (lib "eagle-import") (part "BAV99"))
    )
    (comp (ref "D54")
      (value "200mA/70V")
      (footprint "eagle-import:SOT23-3")
      (libsource (lib "eagle-import") (part "BAV99"))
    )
    (comp (ref "D55")
      (value "200mA/70V")
      (footprint "eagle-import:SOT23-3")
      (libsource (lib "eagle-import") (part "BAV99"))
    )
    (comp (ref "D56")
      (value "200mA/70V")
      (footprint "eagle-import:SOT23-3")
      (libsource (lib "eagle-import") (part "BAV99"))
    )
    (comp (ref "D57")
      (value "200mA/70V")
      (footprint "eagle-import:SOT23-3")
      (libsource (lib "eagle-import") (part "BAV99"))
    )
    (comp (ref "D58")
      (value "200mA/70V")
      (footprint "eagle-import:SOT23-3")
      (libsource (lib "eagle-import") (part "BAV99"))
    )
    (comp (ref "D59")
      (value "200mA/70V")
      (footprint "eagle-import:SOT23-3")
      (libsource (lib "eagle-import") (part "BAV99"))
    )
    (comp (ref "D60")
      (value "200mA/70V")
      (footprint "eagle-import:SOT23-3")
      (libsource (lib "eagle-import") (part "BAV99"))
    )
    (comp (ref "D61")
      (value "200mA/70V")
      (footprint "eagle-import:SOT23-3")
      (libsource (lib "eagle-import") (part "BAV99"))
    )
    (comp (ref "D62")
      (value "200mA/70V")
      (footprint "eagle-import:SOT23-3")
      (libsource (lib "eagle-import") (part "BAV99"))
    )
    (comp (ref "D63")
      (value "200mA/70V")
      (footprint "eagle-import:SOT23-3")
      (libsource (lib "eagle-import") (part "BAV99"))
    )
    (comp (ref "D64")
      (value "200mA/70V")
      (footprint "eagle-import:SOT23-3")
      (libsource (lib "eagle-import") (part "BAV99"))
    )
    (comp (ref "D81")
      (value "200mA/70V")
      (footprint "eagle-import:SOT23-3")
      (libsource (lib "eagle-import") (part "BAV99"))
    )
    (comp (ref "D82")
      (value "200mA/70V")
      (footprint "eagle-import:SOT23-3")
      (libsource (lib "eagle-import") (part "BAV99"))
    )
    (comp (ref "D83")
      (value "200mA/70V")
      (footprint "eagle-import:SOT23-3")
      (libsource (lib "eagle-import") (part "BAV99"))
    )
    (comp (ref "D84")
      (value "200mA/70V")
      (footprint "eagle-import:SOT23-3")
      (libsource (lib "eagle-import") (part "BAV99"))
    )
    (comp (ref "D85")
      (value "200mA/70V")
      (footprint "eagle-import:SOT23-3")
      (libsource (lib "eagle-import") (part "BAV99"))
    )
    (comp (ref "D86")
      (value "200mA/70V")
      (footprint "eagle-import:SOT23-3")
      (libsource (lib "eagle-import") (part "BAV99"))
    )
    (comp (ref "D87")
      (value "200mA/70V")
      (footprint "eagle-import:SOT23-3")
      (libsource (lib "eagle-import") (part "BAV99"))
    )
    (comp (ref "D88")
      (value "200mA/70V")
      (footprint "eagle-import:SOT23-3")
      (libsource (lib "eagle-import") (part "BAV99"))
    )
    (comp (ref "D89")
      (value "200mA/70V")
      (footprint "eagle-import:SOT23-3")
      (libsource (lib "eagle-import") (part "BAV99"))
    )
    (comp (ref "D90")
      (value "200mA/70V")
      (footprint "eagle-import:SOT23-3")
      (libsource (lib "eagle-import") (part "BAV99"))
    )
    (comp (ref "D91")
      (value "200mA/70V")
      (footprint "eagle-import:SOT23-3")
      (libsource (lib "eagle-import") (part "BAV99"))
    )
    (comp (ref "D92")
      (value "200mA/70V")
      (footprint "eagle-import:SOT23-3")
      (libsource (lib "eagle-import") (part "BAV99"))
    )
    (comp (ref "D93")
      (value "200mA/70V")
      (footprint "eagle-import:SOT23-3")
      (libsource (lib "eagle-import") (part "BAV99"))
    )
    (comp (ref "D94")
      (value "200mA/70V")
      (footprint "eagle-import:SOT23-3")
      (libsource (lib "eagle-import") (part "BAV99"))
    )
    (comp (ref "D95")
      (value "200mA/70V")
      (footprint "eagle-import:SOT23-3")
      (libsource (lib "eagle-import") (part "BAV99"))
    )
    (comp (ref "D96")
      (value "200mA/70V")
      (footprint "eagle-import:SOT23-3")
      (libsource (lib "eagle-import") (part "BAV99"))
    )
    (comp (ref "D113")
      (value "200mA/70V")
      (footprint "eagle-import:SOT23-3")
      (libsource (lib "eagle-import") (part "BAV99"))
    )
    (comp (ref "D114")
      (value "200mA/70V")
      (footprint "eagle-import:SOT23-3")
      (libsource (lib "eagle-import") (part "BAV99"))
    )
    (comp (ref "D115")
      (value "200mA/70V")
      (footprint "eagle-import:SOT23-3")
      (libsource (lib "eagle-import") (part "BAV99"))
    )
    (comp (ref "D116")
      (value "200mA/70V")
      (footprint "eagle-import:SOT23-3")
      (libsource (lib "eagle-import") (part "BAV99"))
    )
    (comp (ref "D117")
      (value "200mA/70V")
      (footprint "eagle-import:SOT23-3")
      (libsource (lib "eagle-import") (part "BAV99"))
    )
    (comp (ref "D118")
      (value "200mA/70V")
      (footprint "eagle-import:SOT23-3")
      (libsource (lib "eagle-import") (part "BAV99"))
    )
    (comp (ref "D119")
      (value "200mA/70V")
      (footprint "eagle-import:SOT23-3")
      (libsource (lib "eagle-import") (part "BAV99"))
    )
    (comp (ref "D120")
      (value "200mA/70V")
      (footprint "eagle-import:SOT23-3")
      (libsource (lib "eagle-import") (part "BAV99"))
    )
    (comp (ref "D121")
      (value "200mA/70V")
      (footprint "eagle-import:SOT23-3")
      (libsource (lib "eagle-import") (part "BAV99"))
    )
    (comp (ref "D122")
      (value "200mA/70V")
      (footprint "eagle-import:SOT23-3")
      (libsource (lib "eagle-import") (part "BAV99"))
    )
    (comp (ref "D123")
      (value "200mA/70V")
      (footprint "eagle-import:SOT23-3")
      (libsource (lib "eagle-import") (part "BAV99"))
    )
    (comp (ref "D124")
      (value "200mA/70V")
      (footprint "eagle-import:SOT23-3")
      (libsource (lib "eagle-import") (part "BAV99"))
    )
    (comp (ref "D125")
      (value "200mA/70V")
      (footprint "eagle-import:SOT23-3")
      (libsource (lib "eagle-import") (part "BAV99"))
    )
    (comp (ref "D126")
      (value "200mA/70V")
      (footprint "eagle-import:SOT23-3")
      (libsource (lib "eagle-import") (part "BAV99"))
    )
    (comp (ref "D127")
      (value "200mA/70V")
      (footprint "eagle-import:SOT23-3")
      (libsource (lib "eagle-import") (part "BAV99"))
    )
    (comp (ref "D128")
      (value "200mA/70V")
      (footprint "eagle-import:SOT23-3")
      (libsource (lib "eagle-import") (part "BAV99"))
    )
    (comp (ref "D145")
      (value "200mA/70V")
      (footprint "eagle-import:SOT23-3")
      (libsource (lib "eagle-import") (part "BAV99"))
    )
    (comp (ref "D146")
      (value "200mA/70V")
      (footprint "eagle-import:SOT23-3")
      (libsource (lib "eagle-import") (part "BAV99"))
    )
    (comp (ref "D147")
      (value "200mA/70V")
      (footprint "eagle-import:SOT23-3")
      (libsource (lib "eagle-import") (part "BAV99"))
    )
    (comp (ref "D148")
      (value "200mA/70V")
      (footprint "eagle-import:SOT23-3")
      (libsource (lib "eagle-import") (part "BAV99"))
    )
    (comp (ref "D149")
      (value "200mA/70V")
      (footprint "eagle-import:SOT23-3")
      (libsource (lib "eagle-import") (part "BAV99"))
    )
    (comp (ref "D150")
      (value "200mA/70V")
      (footprint "eagle-import:SOT23-3")
      (libsource (lib "eagle-import") (part "BAV99"))
    )
    (comp (ref "D151")
      (value "200mA/70V")
      (footprint "eagle-import:SOT23-3")
      (libsource (lib "eagle-import") (part "BAV99"))
    )
    (comp (ref "D152")
      (value "200mA/70V")
      (footprint "eagle-import:SOT23-3")
      (libsource (lib "eagle-import") (part "BAV99"))
    )
    (comp (ref "D153")
      (value "200mA/70V")
      (footprint "eagle-import:SOT23-3")
      (libsource (lib "eagle-import") (part "BAV99"))
    )
    (comp (ref "D154")
      (value "200mA/70V")
      (footprint "eagle-import:SOT23-3")
      (libsource (lib "eagle-import") (part "BAV99"))
    )
    (comp (ref "D155")
      (value "200mA/70V")
      (footprint "eagle-import:SOT23-3")
      (libsource (lib "eagle-import") (part "BAV99"))
    )
    (comp (ref "D156")
      (value "200mA/70V")
      (footprint "eagle-import:SOT23-3")
      (libsource (lib "eagle-import") (part "BAV99"))
    )
    (comp (ref "D157")
      (value "200mA/70V")
      (footprint "eagle-import:SOT23-3")
      (libsource (lib "eagle-import") (part "BAV99"))
    )
    (comp (ref "D158")
      (value "200mA/70V")
      (footprint "eagle-import:SOT23-3")
      (libsource (lib "eagle-import") (part "BAV99"))
    )
    (comp (ref "D159")
      (value "200mA/70V")
      (footprint "eagle-import:SOT23-3")
      (libsource (lib "eagle-import") (part "BAV99"))
    )
    (comp (ref "D160")
      (value "200mA/70V")
      (footprint "eagle-import:SOT23-3")
      (libsource (lib "eagle-import") (part "BAV99"))
    )
    (comp (ref "D177")
      (value "200mA/70V")
      (footprint "eagle-import:SOT23-3")
      (libsource (lib "eagle-import") (part "BAV99"))
    )
    (comp (ref "D178")
      (value "200mA/70V")
      (footprint "eagle-import:SOT23-3")
      (libsource (lib "eagle-import") (part "BAV99"))
    )
    (comp (ref "D179")
      (value "200mA/70V")
      (footprint "eagle-import:SOT23-3")
      (libsource (lib "eagle-import") (part "BAV99"))
    )
    (comp (ref "D180")
      (value "200mA/70V")
      (footprint "eagle-import:SOT23-3")
      (libsource (lib "eagle-import") (part "BAV99"))
    )
    (comp (ref "D181")
      (value "200mA/70V")
      (footprint "eagle-import:SOT23-3")
      (libsource (lib "eagle-import") (part "BAV99"))
    )
    (comp (ref "D182")
      (value "200mA/70V")
      (footprint "eagle-import:SOT23-3")
      (libsource (lib "eagle-import") (part "BAV99"))
    )
    (comp (ref "D183")
      (value "200mA/70V")
      (footprint "eagle-import:SOT23-3")
      (libsource (lib "eagle-import") (part "BAV99"))
    )
    (comp (ref "D184")
      (value "200mA/70V")
      (footprint "eagle-import:SOT23-3")
      (libsource (lib "eagle-import") (part "BAV99"))
    )
    (comp (ref "D185")
      (value "200mA/70V")
      (footprint "eagle-import:SOT23-3")
      (libsource (lib "eagle-import") (part "BAV99"))
    )
    (comp (ref "D186")
      (value "200mA/70V")
      (footprint "eagle-import:SOT23-3")
      (libsource (lib "eagle-import") (part "BAV99"))
    )
    (comp (ref "D187")
      (value "200mA/70V")
      (footprint "eagle-import:SOT23-3")
      (libsource (lib "eagle-import") (part "BAV99"))
    )
    (comp (ref "D188")
      (value "200mA/70V")
      (footprint "eagle-import:SOT23-3")
      (libsource (lib "eagle-import") (part "BAV99"))
    )
    (comp (ref "D189")
      (value "200mA/70V")
      (footprint "eagle-import:SOT23-3")
      (libsource (lib "eagle-import") (part "BAV99"))
    )
    (comp (ref "D190")
      (value "200mA/70V")
      (footprint "eagle-import:SOT23-3")
      (libsource (lib "eagle-import") (part "BAV99"))
    )
    (comp (ref "D191")
      (value "200mA/70V")
      (footprint "eagle-import:SOT23-3")
      (libsource (lib "eagle-import") (part "BAV99"))
    )
    (comp (ref "D192")
      (value "200mA/70V")
      (footprint "eagle-import:SOT23-3")
      (libsource (lib "eagle-import") (part "BAV99"))
    )
    (comp (ref "D209")
      (value "200mA/70V")
      (footprint "eagle-import:SOT23-3")
      (libsource (lib "eagle-import") (part "BAV99"))
    )
    (comp (ref "D210")
      (value "200mA/70V")
      (footprint "eagle-import:SOT23-3")
      (libsource (lib "eagle-import") (part "BAV99"))
    )
    (comp (ref "D211")
      (value "200mA/70V")
      (footprint "eagle-import:SOT23-3")
      (libsource (lib "eagle-import") (part "BAV99"))
    )
    (comp (ref "D212")
      (value "200mA/70V")
      (footprint "eagle-import:SOT23-3")
      (libsource (lib "eagle-import") (part "BAV99"))
    )
    (comp (ref "D213")
      (value "200mA/70V")
      (footprint "eagle-import:SOT23-3")
      (libsource (lib "eagle-import") (part "BAV99"))
    )
    (comp (ref "D214")
      (value "200mA/70V")
      (footprint "eagle-import:SOT23-3")
      (libsource (lib "eagle-import") (part "BAV99"))
    )
    (comp (ref "D215")
      (value "200mA/70V")
      (footprint "eagle-import:SOT23-3")
      (libsource (lib "eagle-import") (part "BAV99"))
    )
    (comp (ref "D216")
      (value "200mA/70V")
      (footprint "eagle-import:SOT23-3")
      (libsource (lib "eagle-import") (part "BAV99"))
    )
    (comp (ref "D217")
      (value "200mA/70V")
      (footprint "eagle-import:SOT23-3")
      (libsource (lib "eagle-import") (part "BAV99"))
    )
    (comp (ref "D218")
      (value "200mA/70V")
      (footprint "eagle-import:SOT23-3")
      (libsource (lib "eagle-import") (part "BAV99"))
    )
    (comp (ref "D219")
      (value "200mA/70V")
      (footprint "eagle-import:SOT23-3")
      (libsource (lib "eagle-import") (part "BAV99"))
    )
    (comp (ref "D220")
      (value "200mA/70V")
      (footprint "eagle-import:SOT23-3")
      (libsource (lib "eagle-import") (part "BAV99"))
    )
    (comp (ref "D221")
      (value "200mA/70V")
      (footprint "eagle-import:SOT23-3")
      (libsource (lib "eagle-import") (part "BAV99"))
    )
    (comp (ref "D222")
      (value "200mA/70V")
      (footprint "eagle-import:SOT23-3")
      (libsource (lib "eagle-import") (part "BAV99"))
    )
    (comp (ref "D223")
      (value "200mA/70V")
      (footprint "eagle-import:SOT23-3")
      (libsource (lib "eagle-import") (part "BAV99"))
    )
    (comp (ref "D224")
      (value "200mA/70V")
      (footprint "eagle-import:SOT23-3")
      (libsource (lib "eagle-import") (part "BAV99"))
    )
    (comp (ref "D241")
      (value "200mA/70V")
      (footprint "eagle-import:SOT23-3")
      (libsource (lib "eagle-import") (part "BAV99"))
    )
    (comp (ref "D242")
      (value "200mA/70V")
      (footprint "eagle-import:SOT23-3")
      (libsource (lib "eagle-import") (part "BAV99"))
    )
    (comp (ref "D243")
      (value "200mA/70V")
      (footprint "eagle-import:SOT23-3")
      (libsource (lib "eagle-import") (part "BAV99"))
    )
    (comp (ref "D244")
      (value "200mA/70V")
      (footprint "eagle-import:SOT23-3")
      (libsource (lib "eagle-import") (part "BAV99"))
    )
    (comp (ref "D245")
      (value "200mA/70V")
      (footprint "eagle-import:SOT23-3")
      (libsource (lib "eagle-import") (part "BAV99"))
    )
    (comp (ref "D246")
      (value "200mA/70V")
      (footprint "eagle-import:SOT23-3")
      (libsource (lib "eagle-import") (part "BAV99"))
    )
    (comp (ref "D247")
      (value "200mA/70V")
      (footprint "eagle-import:SOT23-3")
      (libsource (lib "eagle-import") (part "BAV99"))
    )
    (comp (ref "D248")
      (value "200mA/70V")
      (footprint "eagle-import:SOT23-3")
      (libsource (lib "eagle-import") (part "BAV99"))
    )
    (comp (ref "D249")
      (value "200mA/70V")
      (footprint "eagle-import:SOT23-3")
      (libsource (lib "eagle-import") (part "BAV99"))
    )
    (comp (ref "D250")
      (value "200mA/70V")
      (footprint "eagle-import:SOT23-3")
      (libsource (lib "eagle-import") (part "BAV99"))
    )
    (comp (ref "D251")
      (value "200mA/70V")
      (footprint "eagle-import:SOT23-3")
      (libsource (lib "eagle-import") (part "BAV99"))
    )
    (comp (ref "D252")
      (value "200mA/70V")
      (footprint "eagle-import:SOT23-3")
      (libsource (lib "eagle-import") (part "BAV99"))
    )
    (comp (ref "D253")
      (value "200mA/70V")
      (footprint "eagle-import:SOT23-3")
      (libsource (lib "eagle-import") (part "BAV99"))
    )
    (comp (ref "D254")
      (value "200mA/70V")
      (footprint "eagle-import:SOT23-3")
      (libsource (lib "eagle-import") (part "BAV99"))
    )
    (comp (ref "D255")
      (value "200mA/70V")
      (footprint "eagle-import:SOT23-3")
      (libsource (lib "eagle-import") (part "BAV99"))
    )
    (comp (ref "D256")
      (value "200mA/70V")
      (footprint "eagle-import:SOT23-3")
      (libsource (lib "eagle-import") (part "BAV99"))
    )
    (comp (ref "D273")
      (value "200mA/70V")
      (footprint "eagle-import:SOT23-3")
      (libsource (lib "eagle-import") (part "BAV99"))
    )
    (comp (ref "D274")
      (value "200mA/70V")
      (footprint "eagle-import:SOT23-3")
      (libsource (lib "eagle-import") (part "BAV99"))
    )
    (comp (ref "D275")
      (value "200mA/70V")
      (footprint "eagle-import:SOT23-3")
      (libsource (lib "eagle-import") (part "BAV99"))
    )
    (comp (ref "D276")
      (value "200mA/70V")
      (footprint "eagle-import:SOT23-3")
      (libsource (lib "eagle-import") (part "BAV99"))
    )
    (comp (ref "D277")
      (value "200mA/70V")
      (footprint "eagle-import:SOT23-3")
      (libsource (lib "eagle-import") (part "BAV99"))
    )
    (comp (ref "D278")
      (value "200mA/70V")
      (footprint "eagle-import:SOT23-3")
      (libsource (lib "eagle-import") (part "BAV99"))
    )
    (comp (ref "D279")
      (value "200mA/70V")
      (footprint "eagle-import:SOT23-3")
      (libsource (lib "eagle-import") (part "BAV99"))
    )
    (comp (ref "D280")
      (value "200mA/70V")
      (footprint "eagle-import:SOT23-3")
      (libsource (lib "eagle-import") (part "BAV99"))
    )
    (comp (ref "D281")
      (value "200mA/70V")
      (footprint "eagle-import:SOT23-3")
      (libsource (lib "eagle-import") (part "BAV99"))
    )
    (comp (ref "D282")
      (value "200mA/70V")
      (footprint "eagle-import:SOT23-3")
      (libsource (lib "eagle-import") (part "BAV99"))
    )
    (comp (ref "D283")
      (value "200mA/70V")
      (footprint "eagle-import:SOT23-3")
      (libsource (lib "eagle-import") (part "BAV99"))
    )
    (comp (ref "D284")
      (value "200mA/70V")
      (footprint "eagle-import:SOT23-3")
      (libsource (lib "eagle-import") (part "BAV99"))
    )
    (comp (ref "D285")
      (value "200mA/70V")
      (footprint "eagle-import:SOT23-3")
      (libsource (lib "eagle-import") (part "BAV99"))
    )
    (comp (ref "D286")
      (value "200mA/70V")
      (footprint "eagle-import:SOT23-3")
      (libsource (lib "eagle-import") (part "BAV99"))
    )
    (comp (ref "D287")
      (value "200mA/70V")
      (footprint "eagle-import:SOT23-3")
      (libsource (lib "eagle-import") (part "BAV99"))
    )
    (comp (ref "D288")
      (value "200mA/70V")
      (footprint "eagle-import:SOT23-3")
      (libsource (lib "eagle-import") (part "BAV99"))
    )
    (comp (ref "D305")
      (value "200mA/70V")
      (footprint "eagle-import:SOT23-3")
      (libsource (lib "eagle-import") (part "BAV99"))
    )
    (comp (ref "D306")
      (value "200mA/70V")
      (footprint "eagle-import:SOT23-3")
      (libsource (lib "eagle-import") (part "BAV99"))
    )
    (comp (ref "D307")
      (value "200mA/70V")
      (footprint "eagle-import:SOT23-3")
      (libsource (lib "eagle-import") (part "BAV99"))
    )
    (comp (ref "D308")
      (value "200mA/70V")
      (footprint "eagle-import:SOT23-3")
      (libsource (lib "eagle-import") (part "BAV99"))
    )
    (comp (ref "D309")
      (value "200mA/70V")
      (footprint "eagle-import:SOT23-3")
      (libsource (lib "eagle-import") (part "BAV99"))
    )
    (comp (ref "D310")
      (value "200mA/70V")
      (footprint "eagle-import:SOT23-3")
      (libsource (lib "eagle-import") (part "BAV99"))
    )
    (comp (ref "D311")
      (value "200mA/70V")
      (footprint "eagle-import:SOT23-3")
      (libsource (lib "eagle-import") (part "BAV99"))
    )
    (comp (ref "D312")
      (value "200mA/70V")
      (footprint "eagle-import:SOT23-3")
      (libsource (lib "eagle-import") (part "BAV99"))
    )
    (comp (ref "D313")
      (value "200mA/70V")
      (footprint "eagle-import:SOT23-3")
      (libsource (lib "eagle-import") (part "BAV99"))
    )
    (comp (ref "D314")
      (value "200mA/70V")
      (footprint "eagle-import:SOT23-3")
      (libsource (lib "eagle-import") (part "BAV99"))
    )
    (comp (ref "D315")
      (value "200mA/70V")
      (footprint "eagle-import:SOT23-3")
      (libsource (lib "eagle-import") (part "BAV99"))
    )
    (comp (ref "D316")
      (value "200mA/70V")
      (footprint "eagle-import:SOT23-3")
      (libsource (lib "eagle-import") (part "BAV99"))
    )
    (comp (ref "D317")
      (value "200mA/70V")
      (footprint "eagle-import:SOT23-3")
      (libsource (lib "eagle-import") (part "BAV99"))
    )
    (comp (ref "D318")
      (value "200mA/70V")
      (footprint "eagle-import:SOT23-3")
      (libsource (lib "eagle-import") (part "BAV99"))
    )
    (comp (ref "D319")
      (value "200mA/70V")
      (footprint "eagle-import:SOT23-3")
      (libsource (lib "eagle-import") (part "BAV99"))
    )
    (comp (ref "D320")
      (value "200mA/70V")
      (footprint "eagle-import:SOT23-3")
      (libsource (lib "eagle-import") (part "BAV99"))
    )
    (comp (ref "D337")
      (value "200mA/70V")
      (footprint "eagle-import:SOT23-3")
      (libsource (lib "eagle-import") (part "BAV99"))
    )
    (comp (ref "D338")
      (value "200mA/70V")
      (footprint "eagle-import:SOT23-3")
      (libsource (lib "eagle-import") (part "BAV99"))
    )
    (comp (ref "D339")
      (value "200mA/70V")
      (footprint "eagle-import:SOT23-3")
      (libsource (lib "eagle-import") (part "BAV99"))
    )
    (comp (ref "D340")
      (value "200mA/70V")
      (footprint "eagle-import:SOT23-3")
      (libsource (lib "eagle-import") (part "BAV99"))
    )
    (comp (ref "D341")
      (value "200mA/70V")
      (footprint "eagle-import:SOT23-3")
      (libsource (lib "eagle-import") (part "BAV99"))
    )
    (comp (ref "D342")
      (value "200mA/70V")
      (footprint "eagle-import:SOT23-3")
      (libsource (lib "eagle-import") (part "BAV99"))
    )
    (comp (ref "D343")
      (value "200mA/70V")
      (footprint "eagle-import:SOT23-3")
      (libsource (lib "eagle-import") (part "BAV99"))
    )
    (comp (ref "D344")
      (value "200mA/70V")
      (footprint "eagle-import:SOT23-3")
      (libsource (lib "eagle-import") (part "BAV99"))
    )
    (comp (ref "D345")
      (value "200mA/70V")
      (footprint "eagle-import:SOT23-3")
      (libsource (lib "eagle-import") (part "BAV99"))
    )
    (comp (ref "D346")
      (value "200mA/70V")
      (footprint "eagle-import:SOT23-3")
      (libsource (lib "eagle-import") (part "BAV99"))
    )
    (comp (ref "D347")
      (value "200mA/70V")
      (footprint "eagle-import:SOT23-3")
      (libsource (lib "eagle-import") (part "BAV99"))
    )
    (comp (ref "D348")
      (value "200mA/70V")
      (footprint "eagle-import:SOT23-3")
      (libsource (lib "eagle-import") (part "BAV99"))
    )
    (comp (ref "D349")
      (value "200mA/70V")
      (footprint "eagle-import:SOT23-3")
      (libsource (lib "eagle-import") (part "BAV99"))
    )
    (comp (ref "D350")
      (value "200mA/70V")
      (footprint "eagle-import:SOT23-3")
      (libsource (lib "eagle-import") (part "BAV99"))
    )
    (comp (ref "D351")
      (value "200mA/70V")
      (footprint "eagle-import:SOT23-3")
      (libsource (lib "eagle-import") (part "BAV99"))
    )
    (comp (ref "D352")
      (value "200mA/70V")
      (footprint "eagle-import:SOT23-3")
      (libsource (lib "eagle-import") (part "BAV99"))
    )
    (comp (ref "D369")
      (value "200mA/70V")
      (footprint "eagle-import:SOT23-3")
      (libsource (lib "eagle-import") (part "BAV99"))
    )
    (comp (ref "D370")
      (value "200mA/70V")
      (footprint "eagle-import:SOT23-3")
      (libsource (lib "eagle-import") (part "BAV99"))
    )
    (comp (ref "D371")
      (value "200mA/70V")
      (footprint "eagle-import:SOT23-3")
      (libsource (lib "eagle-import") (part "BAV99"))
    )
    (comp (ref "D372")
      (value "200mA/70V")
      (footprint "eagle-import:SOT23-3")
      (libsource (lib "eagle-import") (part "BAV99"))
    )
    (comp (ref "D373")
      (value "200mA/70V")
      (footprint "eagle-import:SOT23-3")
      (libsource (lib "eagle-import") (part "BAV99"))
    )
    (comp (ref "D374")
      (value "200mA/70V")
      (footprint "eagle-import:SOT23-3")
      (libsource (lib "eagle-import") (part "BAV99"))
    )
    (comp (ref "D375")
      (value "200mA/70V")
      (footprint "eagle-import:SOT23-3")
      (libsource (lib "eagle-import") (part "BAV99"))
    )
    (comp (ref "D376")
      (value "200mA/70V")
      (footprint "eagle-import:SOT23-3")
      (libsource (lib "eagle-import") (part "BAV99"))
    )
    (comp (ref "D377")
      (value "200mA/70V")
      (footprint "eagle-import:SOT23-3")
      (libsource (lib "eagle-import") (part "BAV99"))
    )
    (comp (ref "D378")
      (value "200mA/70V")
      (footprint "eagle-import:SOT23-3")
      (libsource (lib "eagle-import") (part "BAV99"))
    )
    (comp (ref "D379")
      (value "200mA/70V")
      (footprint "eagle-import:SOT23-3")
      (libsource (lib "eagle-import") (part "BAV99"))
    )
    (comp (ref "D380")
      (value "200mA/70V")
      (footprint "eagle-import:SOT23-3")
      (libsource (lib "eagle-import") (part "BAV99"))
    )
    (comp (ref "D381")
      (value "200mA/70V")
      (footprint "eagle-import:SOT23-3")
      (libsource (lib "eagle-import") (part "BAV99"))
    )
    (comp (ref "D382")
      (value "200mA/70V")
      (footprint "eagle-import:SOT23-3")
      (libsource (lib "eagle-import") (part "BAV99"))
    )
    (comp (ref "D383")
      (value "200mA/70V")
      (footprint "eagle-import:SOT23-3")
      (libsource (lib "eagle-import") (part "BAV99"))
    )
    (comp (ref "D384")
      (value "200mA/70V")
      (footprint "eagle-import:SOT23-3")
      (libsource (lib "eagle-import") (part "BAV99"))
    )
    (comp (ref "D401")
      (value "200mA/70V")
      (footprint "eagle-import:SOT23-3")
      (libsource (lib "eagle-import") (part "BAV99"))
    )
    (comp (ref "D402")
      (value "200mA/70V")
      (footprint "eagle-import:SOT23-3")
      (libsource (lib "eagle-import") (part "BAV99"))
    )
    (comp (ref "D403")
      (value "200mA/70V")
      (footprint "eagle-import:SOT23-3")
      (libsource (lib "eagle-import") (part "BAV99"))
    )
    (comp (ref "D404")
      (value "200mA/70V")
      (footprint "eagle-import:SOT23-3")
      (libsource (lib "eagle-import") (part "BAV99"))
    )
    (comp (ref "D405")
      (value "200mA/70V")
      (footprint "eagle-import:SOT23-3")
      (libsource (lib "eagle-import") (part "BAV99"))
    )
    (comp (ref "D406")
      (value "200mA/70V")
      (footprint "eagle-import:SOT23-3")
      (libsource (lib "eagle-import") (part "BAV99"))
    )
    (comp (ref "D407")
      (value "200mA/70V")
      (footprint "eagle-import:SOT23-3")
      (libsource (lib "eagle-import") (part "BAV99"))
    )
    (comp (ref "D408")
      (value "200mA/70V")
      (footprint "eagle-import:SOT23-3")
      (libsource (lib "eagle-import") (part "BAV99"))
    )
    (comp (ref "D409")
      (value "200mA/70V")
      (footprint "eagle-import:SOT23-3")
      (libsource (lib "eagle-import") (part "BAV99"))
    )
    (comp (ref "D410")
      (value "200mA/70V")
      (footprint "eagle-import:SOT23-3")
      (libsource (lib "eagle-import") (part "BAV99"))
    )
    (comp (ref "D411")
      (value "200mA/70V")
      (footprint "eagle-import:SOT23-3")
      (libsource (lib "eagle-import") (part "BAV99"))
    )
    (comp (ref "D412")
      (value "200mA/70V")
      (footprint "eagle-import:SOT23-3")
      (libsource (lib "eagle-import") (part "BAV99"))
    )
    (comp (ref "D413")
      (value "200mA/70V")
      (footprint "eagle-import:SOT23-3")
      (libsource (lib "eagle-import") (part "BAV99"))
    )
    (comp (ref "D414")
      (value "200mA/70V")
      (footprint "eagle-import:SOT23-3")
      (libsource (lib "eagle-import") (part "BAV99"))
    )
    (comp (ref "D415")
      (value "200mA/70V")
      (footprint "eagle-import:SOT23-3")
      (libsource (lib "eagle-import") (part "BAV99"))
    )
    (comp (ref "D416")
      (value "200mA/70V")
      (footprint "eagle-import:SOT23-3")
      (libsource (lib "eagle-import") (part "BAV99"))
    )
    (comp (ref "D433")
      (value "200mA/70V")
      (footprint "eagle-import:SOT23-3")
      (libsource (lib "eagle-import") (part "BAV99"))
    )
    (comp (ref "D434")
      (value "200mA/70V")
      (footprint "eagle-import:SOT23-3")
      (libsource (lib "eagle-import") (part "BAV99"))
    )
    (comp (ref "D435")
      (value "200mA/70V")
      (footprint "eagle-import:SOT23-3")
      (libsource (lib "eagle-import") (part "BAV99"))
    )
    (comp (ref "D436")
      (value "200mA/70V")
      (footprint "eagle-import:SOT23-3")
      (libsource (lib "eagle-import") (part "BAV99"))
    )
    (comp (ref "D437")
      (value "200mA/70V")
      (footprint "eagle-import:SOT23-3")
      (libsource (lib "eagle-import") (part "BAV99"))
    )
    (comp (ref "D438")
      (value "200mA/70V")
      (footprint "eagle-import:SOT23-3")
      (libsource (lib "eagle-import") (part "BAV99"))
    )
    (comp (ref "D439")
      (value "200mA/70V")
      (footprint "eagle-import:SOT23-3")
      (libsource (lib "eagle-import") (part "BAV99"))
    )
    (comp (ref "D440")
      (value "200mA/70V")
      (footprint "eagle-import:SOT23-3")
      (libsource (lib "eagle-import") (part "BAV99"))
    )
    (comp (ref "D441")
      (value "200mA/70V")
      (footprint "eagle-import:SOT23-3")
      (libsource (lib "eagle-import") (part "BAV99"))
    )
    (comp (ref "D442")
      (value "200mA/70V")
      (footprint "eagle-import:SOT23-3")
      (libsource (lib "eagle-import") (part "BAV99"))
    )
    (comp (ref "D443")
      (value "200mA/70V")
      (footprint "eagle-import:SOT23-3")
      (libsource (lib "eagle-import") (part "BAV99"))
    )
    (comp (ref "D444")
      (value "200mA/70V")
      (footprint "eagle-import:SOT23-3")
      (libsource (lib "eagle-import") (part "BAV99"))
    )
    (comp (ref "D445")
      (value "200mA/70V")
      (footprint "eagle-import:SOT23-3")
      (libsource (lib "eagle-import") (part "BAV99"))
    )
    (comp (ref "D446")
      (value "200mA/70V")
      (footprint "eagle-import:SOT23-3")
      (libsource (lib "eagle-import") (part "BAV99"))
    )
    (comp (ref "D447")
      (value "200mA/70V")
      (footprint "eagle-import:SOT23-3")
      (libsource (lib "eagle-import") (part "BAV99"))
    )
    (comp (ref "D448")
      (value "200mA/70V")
      (footprint "eagle-import:SOT23-3")
      (libsource (lib "eagle-import") (part "BAV99"))
    )
    (comp (ref "D465")
      (value "200mA/70V")
      (footprint "eagle-import:SOT23-3")
      (libsource (lib "eagle-import") (part "BAV99"))
    )
    (comp (ref "D466")
      (value "200mA/70V")
      (footprint "eagle-import:SOT23-3")
      (libsource (lib "eagle-import") (part "BAV99"))
    )
    (comp (ref "D467")
      (value "200mA/70V")
      (footprint "eagle-import:SOT23-3")
      (libsource (lib "eagle-import") (part "BAV99"))
    )
    (comp (ref "D468")
      (value "200mA/70V")
      (footprint "eagle-import:SOT23-3")
      (libsource (lib "eagle-import") (part "BAV99"))
    )
    (comp (ref "D469")
      (value "200mA/70V")
      (footprint "eagle-import:SOT23-3")
      (libsource (lib "eagle-import") (part "BAV99"))
    )
    (comp (ref "D470")
      (value "200mA/70V")
      (footprint "eagle-import:SOT23-3")
      (libsource (lib "eagle-import") (part "BAV99"))
    )
    (comp (ref "D471")
      (value "200mA/70V")
      (footprint "eagle-import:SOT23-3")
      (libsource (lib "eagle-import") (part "BAV99"))
    )
    (comp (ref "D472")
      (value "200mA/70V")
      (footprint "eagle-import:SOT23-3")
      (libsource (lib "eagle-import") (part "BAV99"))
    )
    (comp (ref "D473")
      (value "200mA/70V")
      (footprint "eagle-import:SOT23-3")
      (libsource (lib "eagle-import") (part "BAV99"))
    )
    (comp (ref "D474")
      (value "200mA/70V")
      (footprint "eagle-import:SOT23-3")
      (libsource (lib "eagle-import") (part "BAV99"))
    )
    (comp (ref "D475")
      (value "200mA/70V")
      (footprint "eagle-import:SOT23-3")
      (libsource (lib "eagle-import") (part "BAV99"))
    )
    (comp (ref "D476")
      (value "200mA/70V")
      (footprint "eagle-import:SOT23-3")
      (libsource (lib "eagle-import") (part "BAV99"))
    )
    (comp (ref "D477")
      (value "200mA/70V")
      (footprint "eagle-import:SOT23-3")
      (libsource (lib "eagle-import") (part "BAV99"))
    )
    (comp (ref "D478")
      (value "200mA/70V")
      (footprint "eagle-import:SOT23-3")
      (libsource (lib "eagle-import") (part "BAV99"))
    )
    (comp (ref "D479")
      (value "200mA/70V")
      (footprint "eagle-import:SOT23-3")
      (libsource (lib "eagle-import") (part "BAV99"))
    )
    (comp (ref "D480")
      (value "200mA/70V")
      (footprint "eagle-import:SOT23-3")
      (libsource (lib "eagle-import") (part "BAV99"))
    )
    (comp (ref "D497")
      (value "200mA/70V")
      (footprint "eagle-import:SOT23-3")
      (libsource (lib "eagle-import") (part "BAV99"))
    )
    (comp (ref "D498")
      (value "200mA/70V")
      (footprint "eagle-import:SOT23-3")
      (libsource (lib "eagle-import") (part "BAV99"))
    )
    (comp (ref "D499")
      (value "200mA/70V")
      (footprint "eagle-import:SOT23-3")
      (libsource (lib "eagle-import") (part "BAV99"))
    )
    (comp (ref "D500")
      (value "200mA/70V")
      (footprint "eagle-import:SOT23-3")
      (libsource (lib "eagle-import") (part "BAV99"))
    )
    (comp (ref "D501")
      (value "200mA/70V")
      (footprint "eagle-import:SOT23-3")
      (libsource (lib "eagle-import") (part "BAV99"))
    )
    (comp (ref "D502")
      (value "200mA/70V")
      (footprint "eagle-import:SOT23-3")
      (libsource (lib "eagle-import") (part "BAV99"))
    )
    (comp (ref "D503")
      (value "200mA/70V")
      (footprint "eagle-import:SOT23-3")
      (libsource (lib "eagle-import") (part "BAV99"))
    )
    (comp (ref "D504")
      (value "200mA/70V")
      (footprint "eagle-import:SOT23-3")
      (libsource (lib "eagle-import") (part "BAV99"))
    )
    (comp (ref "D505")
      (value "200mA/70V")
      (footprint "eagle-import:SOT23-3")
      (libsource (lib "eagle-import") (part "BAV99"))
    )
    (comp (ref "D506")
      (value "200mA/70V")
      (footprint "eagle-import:SOT23-3")
      (libsource (lib "eagle-import") (part "BAV99"))
    )
    (comp (ref "D507")
      (value "200mA/70V")
      (footprint "eagle-import:SOT23-3")
      (libsource (lib "eagle-import") (part "BAV99"))
    )
    (comp (ref "D508")
      (value "200mA/70V")
      (footprint "eagle-import:SOT23-3")
      (libsource (lib "eagle-import") (part "BAV99"))
    )
    (comp (ref "D509")
      (value "200mA/70V")
      (footprint "eagle-import:SOT23-3")
      (libsource (lib "eagle-import") (part "BAV99"))
    )
    (comp (ref "D510")
      (value "200mA/70V")
      (footprint "eagle-import:SOT23-3")
      (libsource (lib "eagle-import") (part "BAV99"))
    )
    (comp (ref "D511")
      (value "200mA/70V")
      (footprint "eagle-import:SOT23-3")
      (libsource (lib "eagle-import") (part "BAV99"))
    )
    (comp (ref "D512")
      (value "200mA/70V")
      (footprint "eagle-import:SOT23-3")
      (libsource (lib "eagle-import") (part "BAV99"))
    )
    (comp (ref "L17")
      (value "SD8")
      (footprint "eagle-import:SD8")
      (libsource (lib "eagle-import") (part "SD8"))
    )
    (comp (ref "L18")
      (value "SD8")
      (footprint "eagle-import:SD8")
      (libsource (lib "eagle-import") (part "SD8"))
    )
    (comp (ref "L19")
      (value "SD8")
      (footprint "eagle-import:SD8")
      (libsource (lib "eagle-import") (part "SD8"))
    )
    (comp (ref "L20")
      (value "SD8")
      (footprint "eagle-import:SD8")
      (libsource (lib "eagle-import") (part "SD8"))
    )
    (comp (ref "L21")
      (value "SD8")
      (footprint "eagle-import:SD8")
      (libsource (lib "eagle-import") (part "SD8"))
    )
    (comp (ref "L22")
      (value "SD8")
      (footprint "eagle-import:SD8")
      (libsource (lib "eagle-import") (part "SD8"))
    )
    (comp (ref "L23")
      (value "SD8")
      (footprint "eagle-import:SD8")
      (libsource (lib "eagle-import") (part "SD8"))
    )
    (comp (ref "L24")
      (value "SD8")
      (footprint "eagle-import:SD8")
      (libsource (lib "eagle-import") (part "SD8"))
    )
    (comp (ref "L25")
      (value "SD8")
      (footprint "eagle-import:SD8")
      (libsource (lib "eagle-import") (part "SD8"))
    )
    (comp (ref "L26")
      (value "SD8")
      (footprint "eagle-import:SD8")
      (libsource (lib "eagle-import") (part "SD8"))
    )
    (comp (ref "L27")
      (value "SD8")
      (footprint "eagle-import:SD8")
      (libsource (lib "eagle-import") (part "SD8"))
    )
    (comp (ref "L28")
      (value "SD8")
      (footprint "eagle-import:SD8")
      (libsource (lib "eagle-import") (part "SD8"))
    )
    (comp (ref "L29")
      (value "SD8")
      (footprint "eagle-import:SD8")
      (libsource (lib "eagle-import") (part "SD8"))
    )
    (comp (ref "L30")
      (value "SD8")
      (footprint "eagle-import:SD8")
      (libsource (lib "eagle-import") (part "SD8"))
    )
    (comp (ref "L31")
      (value "SD8")
      (footprint "eagle-import:SD8")
      (libsource (lib "eagle-import") (part "SD8"))
    )
    (comp (ref "L32")
      (value "SD8")
      (footprint "eagle-import:SD8")
      (libsource (lib "eagle-import") (part "SD8"))
    )
    (comp (ref "L49")
      (value "SD8")
      (footprint "eagle-import:SD8")
      (libsource (lib "eagle-import") (part "SD8"))
    )
    (comp (ref "L50")
      (value "SD8")
      (footprint "eagle-import:SD8")
      (libsource (lib "eagle-import") (part "SD8"))
    )
    (comp (ref "L51")
      (value "SD8")
      (footprint "eagle-import:SD8")
      (libsource (lib "eagle-import") (part "SD8"))
    )
    (comp (ref "L52")
      (value "SD8")
      (footprint "eagle-import:SD8")
      (libsource (lib "eagle-import") (part "SD8"))
    )
    (comp (ref "L53")
      (value "SD8")
      (footprint "eagle-import:SD8")
      (libsource (lib "eagle-import") (part "SD8"))
    )
    (comp (ref "L54")
      (value "SD8")
      (footprint "eagle-import:SD8")
      (libsource (lib "eagle-import") (part "SD8"))
    )
    (comp (ref "L55")
      (value "SD8")
      (footprint "eagle-import:SD8")
      (libsource (lib "eagle-import") (part "SD8"))
    )
    (comp (ref "L56")
      (value "SD8")
      (footprint "eagle-import:SD8")
      (libsource (lib "eagle-import") (part "SD8"))
    )
    (comp (ref "L57")
      (value "SD8")
      (footprint "eagle-import:SD8")
      (libsource (lib "eagle-import") (part "SD8"))
    )
    (comp (ref "L58")
      (value "SD8")
      (footprint "eagle-import:SD8")
      (libsource (lib "eagle-import") (part "SD8"))
    )
    (comp (ref "L59")
      (value "SD8")
      (footprint "eagle-import:SD8")
      (libsource (lib "eagle-import") (part "SD8"))
    )
    (comp (ref "L60")
      (value "SD8")
      (footprint "eagle-import:SD8")
      (libsource (lib "eagle-import") (part "SD8"))
    )
    (comp (ref "L61")
      (value "SD8")
      (footprint "eagle-import:SD8")
      (libsource (lib "eagle-import") (part "SD8"))
    )
    (comp (ref "L62")
      (value "SD8")
      (footprint "eagle-import:SD8")
      (libsource (lib "eagle-import") (part "SD8"))
    )
    (comp (ref "L63")
      (value "SD8")
      (footprint "eagle-import:SD8")
      (libsource (lib "eagle-import") (part "SD8"))
    )
    (comp (ref "L64")
      (value "SD8")
      (footprint "eagle-import:SD8")
      (libsource (lib "eagle-import") (part "SD8"))
    )
    (comp (ref "L81")
      (value "SD8")
      (footprint "eagle-import:SD8")
      (libsource (lib "eagle-import") (part "SD8"))
    )
    (comp (ref "L82")
      (value "SD8")
      (footprint "eagle-import:SD8")
      (libsource (lib "eagle-import") (part "SD8"))
    )
    (comp (ref "L83")
      (value "SD8")
      (footprint "eagle-import:SD8")
      (libsource (lib "eagle-import") (part "SD8"))
    )
    (comp (ref "L84")
      (value "SD8")
      (footprint "eagle-import:SD8")
      (libsource (lib "eagle-import") (part "SD8"))
    )
    (comp (ref "L85")
      (value "SD8")
      (footprint "eagle-import:SD8")
      (libsource (lib "eagle-import") (part "SD8"))
    )
    (comp (ref "L86")
      (value "SD8")
      (footprint "eagle-import:SD8")
      (libsource (lib "eagle-import") (part "SD8"))
    )
    (comp (ref "L87")
      (value "SD8")
      (footprint "eagle-import:SD8")
      (libsource (lib "eagle-import") (part "SD8"))
    )
    (comp (ref "L88")
      (value "SD8")
      (footprint "eagle-import:SD8")
      (libsource (lib "eagle-import") (part "SD8"))
    )
    (comp (ref "L89")
      (value "SD8")
      (footprint "eagle-import:SD8")
      (libsource (lib "eagle-import") (part "SD8"))
    )
    (comp (ref "L90")
      (value "SD8")
      (footprint "eagle-import:SD8")
      (libsource (lib "eagle-import") (part "SD8"))
    )
    (comp (ref "L91")
      (value "SD8")
      (footprint "eagle-import:SD8")
      (libsource (lib "eagle-import") (part "SD8"))
    )
    (comp (ref "L92")
      (value "SD8")
      (footprint "eagle-import:SD8")
      (libsource (lib "eagle-import") (part "SD8"))
    )
    (comp (ref "L93")
      (value "SD8")
      (footprint "eagle-import:SD8")
      (libsource (lib "eagle-import") (part "SD8"))
    )
    (comp (ref "L94")
      (value "SD8")
      (footprint "eagle-import:SD8")
      (libsource (lib "eagle-import") (part "SD8"))
    )
    (comp (ref "L95")
      (value "SD8")
      (footprint "eagle-import:SD8")
      (libsource (lib "eagle-import") (part "SD8"))
    )
    (comp (ref "L96")
      (value "SD8")
      (footprint "eagle-import:SD8")
      (libsource (lib "eagle-import") (part "SD8"))
    )
    (comp (ref "L113")
      (value "SD8")
      (footprint "eagle-import:SD8")
      (libsource (lib "eagle-import") (part "SD8"))
    )
    (comp (ref "L114")
      (value "SD8")
      (footprint "eagle-import:SD8")
      (libsource (lib "eagle-import") (part "SD8"))
    )
    (comp (ref "L115")
      (value "SD8")
      (footprint "eagle-import:SD8")
      (libsource (lib "eagle-import") (part "SD8"))
    )
    (comp (ref "L116")
      (value "SD8")
      (footprint "eagle-import:SD8")
      (libsource (lib "eagle-import") (part "SD8"))
    )
    (comp (ref "L117")
      (value "SD8")
      (footprint "eagle-import:SD8")
      (libsource (lib "eagle-import") (part "SD8"))
    )
    (comp (ref "L118")
      (value "SD8")
      (footprint "eagle-import:SD8")
      (libsource (lib "eagle-import") (part "SD8"))
    )
    (comp (ref "L119")
      (value "SD8")
      (footprint "eagle-import:SD8")
      (libsource (lib "eagle-import") (part "SD8"))
    )
    (comp (ref "L120")
      (value "SD8")
      (footprint "eagle-import:SD8")
      (libsource (lib "eagle-import") (part "SD8"))
    )
    (comp (ref "L121")
      (value "SD8")
      (footprint "eagle-import:SD8")
      (libsource (lib "eagle-import") (part "SD8"))
    )
    (comp (ref "L122")
      (value "SD8")
      (footprint "eagle-import:SD8")
      (libsource (lib "eagle-import") (part "SD8"))
    )
    (comp (ref "L123")
      (value "SD8")
      (footprint "eagle-import:SD8")
      (libsource (lib "eagle-import") (part "SD8"))
    )
    (comp (ref "L124")
      (value "SD8")
      (footprint "eagle-import:SD8")
      (libsource (lib "eagle-import") (part "SD8"))
    )
    (comp (ref "L125")
      (value "SD8")
      (footprint "eagle-import:SD8")
      (libsource (lib "eagle-import") (part "SD8"))
    )
    (comp (ref "L126")
      (value "SD8")
      (footprint "eagle-import:SD8")
      (libsource (lib "eagle-import") (part "SD8"))
    )
    (comp (ref "L127")
      (value "SD8")
      (footprint "eagle-import:SD8")
      (libsource (lib "eagle-import") (part "SD8"))
    )
    (comp (ref "L128")
      (value "SD8")
      (footprint "eagle-import:SD8")
      (libsource (lib "eagle-import") (part "SD8"))
    )
    (comp (ref "L145")
      (value "SD8")
      (footprint "eagle-import:SD8")
      (libsource (lib "eagle-import") (part "SD8"))
    )
    (comp (ref "L146")
      (value "SD8")
      (footprint "eagle-import:SD8")
      (libsource (lib "eagle-import") (part "SD8"))
    )
    (comp (ref "L147")
      (value "SD8")
      (footprint "eagle-import:SD8")
      (libsource (lib "eagle-import") (part "SD8"))
    )
    (comp (ref "L148")
      (value "SD8")
      (footprint "eagle-import:SD8")
      (libsource (lib "eagle-import") (part "SD8"))
    )
    (comp (ref "L149")
      (value "SD8")
      (footprint "eagle-import:SD8")
      (libsource (lib "eagle-import") (part "SD8"))
    )
    (comp (ref "L150")
      (value "SD8")
      (footprint "eagle-import:SD8")
      (libsource (lib "eagle-import") (part "SD8"))
    )
    (comp (ref "L151")
      (value "SD8")
      (footprint "eagle-import:SD8")
      (libsource (lib "eagle-import") (part "SD8"))
    )
    (comp (ref "L152")
      (value "SD8")
      (footprint "eagle-import:SD8")
      (libsource (lib "eagle-import") (part "SD8"))
    )
    (comp (ref "L153")
      (value "SD8")
      (footprint "eagle-import:SD8")
      (libsource (lib "eagle-import") (part "SD8"))
    )
    (comp (ref "L154")
      (value "SD8")
      (footprint "eagle-import:SD8")
      (libsource (lib "eagle-import") (part "SD8"))
    )
    (comp (ref "L155")
      (value "SD8")
      (footprint "eagle-import:SD8")
      (libsource (lib "eagle-import") (part "SD8"))
    )
    (comp (ref "L156")
      (value "SD8")
      (footprint "eagle-import:SD8")
      (libsource (lib "eagle-import") (part "SD8"))
    )
    (comp (ref "L157")
      (value "SD8")
      (footprint "eagle-import:SD8")
      (libsource (lib "eagle-import") (part "SD8"))
    )
    (comp (ref "L158")
      (value "SD8")
      (footprint "eagle-import:SD8")
      (libsource (lib "eagle-import") (part "SD8"))
    )
    (comp (ref "L159")
      (value "SD8")
      (footprint "eagle-import:SD8")
      (libsource (lib "eagle-import") (part "SD8"))
    )
    (comp (ref "L160")
      (value "SD8")
      (footprint "eagle-import:SD8")
      (libsource (lib "eagle-import") (part "SD8"))
    )
    (comp (ref "L177")
      (value "SD8")
      (footprint "eagle-import:SD8")
      (libsource (lib "eagle-import") (part "SD8"))
    )
    (comp (ref "L178")
      (value "SD8")
      (footprint "eagle-import:SD8")
      (libsource (lib "eagle-import") (part "SD8"))
    )
    (comp (ref "L179")
      (value "SD8")
      (footprint "eagle-import:SD8")
      (libsource (lib "eagle-import") (part "SD8"))
    )
    (comp (ref "L180")
      (value "SD8")
      (footprint "eagle-import:SD8")
      (libsource (lib "eagle-import") (part "SD8"))
    )
    (comp (ref "L181")
      (value "SD8")
      (footprint "eagle-import:SD8")
      (libsource (lib "eagle-import") (part "SD8"))
    )
    (comp (ref "L182")
      (value "SD8")
      (footprint "eagle-import:SD8")
      (libsource (lib "eagle-import") (part "SD8"))
    )
    (comp (ref "L183")
      (value "SD8")
      (footprint "eagle-import:SD8")
      (libsource (lib "eagle-import") (part "SD8"))
    )
    (comp (ref "L184")
      (value "SD8")
      (footprint "eagle-import:SD8")
      (libsource (lib "eagle-import") (part "SD8"))
    )
    (comp (ref "L185")
      (value "SD8")
      (footprint "eagle-import:SD8")
      (libsource (lib "eagle-import") (part "SD8"))
    )
    (comp (ref "L186")
      (value "SD8")
      (footprint "eagle-import:SD8")
      (libsource (lib "eagle-import") (part "SD8"))
    )
    (comp (ref "L187")
      (value "SD8")
      (footprint "eagle-import:SD8")
      (libsource (lib "eagle-import") (part "SD8"))
    )
    (comp (ref "L188")
      (value "SD8")
      (footprint "eagle-import:SD8")
      (libsource (lib "eagle-import") (part "SD8"))
    )
    (comp (ref "L189")
      (value "SD8")
      (footprint "eagle-import:SD8")
      (libsource (lib "eagle-import") (part "SD8"))
    )
    (comp (ref "L190")
      (value "SD8")
      (footprint "eagle-import:SD8")
      (libsource (lib "eagle-import") (part "SD8"))
    )
    (comp (ref "L191")
      (value "SD8")
      (footprint "eagle-import:SD8")
      (libsource (lib "eagle-import") (part "SD8"))
    )
    (comp (ref "L192")
      (value "SD8")
      (footprint "eagle-import:SD8")
      (libsource (lib "eagle-import") (part "SD8"))
    )
    (comp (ref "L209")
      (value "SD8")
      (footprint "eagle-import:SD8")
      (libsource (lib "eagle-import") (part "SD8"))
    )
    (comp (ref "L210")
      (value "SD8")
      (footprint "eagle-import:SD8")
      (libsource (lib "eagle-import") (part "SD8"))
    )
    (comp (ref "L211")
      (value "SD8")
      (footprint "eagle-import:SD8")
      (libsource (lib "eagle-import") (part "SD8"))
    )
    (comp (ref "L212")
      (value "SD8")
      (footprint "eagle-import:SD8")
      (libsource (lib "eagle-import") (part "SD8"))
    )
    (comp (ref "L213")
      (value "SD8")
      (footprint "eagle-import:SD8")
      (libsource (lib "eagle-import") (part "SD8"))
    )
    (comp (ref "L214")
      (value "SD8")
      (footprint "eagle-import:SD8")
      (libsource (lib "eagle-import") (part "SD8"))
    )
    (comp (ref "L215")
      (value "SD8")
      (footprint "eagle-import:SD8")
      (libsource (lib "eagle-import") (part "SD8"))
    )
    (comp (ref "L216")
      (value "SD8")
      (footprint "eagle-import:SD8")
      (libsource (lib "eagle-import") (part "SD8"))
    )
    (comp (ref "L217")
      (value "SD8")
      (footprint "eagle-import:SD8")
      (libsource (lib "eagle-import") (part "SD8"))
    )
    (comp (ref "L218")
      (value "SD8")
      (footprint "eagle-import:SD8")
      (libsource (lib "eagle-import") (part "SD8"))
    )
    (comp (ref "L219")
      (value "SD8")
      (footprint "eagle-import:SD8")
      (libsource (lib "eagle-import") (part "SD8"))
    )
    (comp (ref "L220")
      (value "SD8")
      (footprint "eagle-import:SD8")
      (libsource (lib "eagle-import") (part "SD8"))
    )
    (comp (ref "L221")
      (value "SD8")
      (footprint "eagle-import:SD8")
      (libsource (lib "eagle-import") (part "SD8"))
    )
    (comp (ref "L222")
      (value "SD8")
      (footprint "eagle-import:SD8")
      (libsource (lib "eagle-import") (part "SD8"))
    )
    (comp (ref "L223")
      (value "SD8")
      (footprint "eagle-import:SD8")
      (libsource (lib "eagle-import") (part "SD8"))
    )
    (comp (ref "L224")
      (value "SD8")
      (footprint "eagle-import:SD8")
      (libsource (lib "eagle-import") (part "SD8"))
    )
    (comp (ref "L241")
      (value "SD8")
      (footprint "eagle-import:SD8")
      (libsource (lib "eagle-import") (part "SD8"))
    )
    (comp (ref "L242")
      (value "SD8")
      (footprint "eagle-import:SD8")
      (libsource (lib "eagle-import") (part "SD8"))
    )
    (comp (ref "L243")
      (value "SD8")
      (footprint "eagle-import:SD8")
      (libsource (lib "eagle-import") (part "SD8"))
    )
    (comp (ref "L244")
      (value "SD8")
      (footprint "eagle-import:SD8")
      (libsource (lib "eagle-import") (part "SD8"))
    )
    (comp (ref "L245")
      (value "SD8")
      (footprint "eagle-import:SD8")
      (libsource (lib "eagle-import") (part "SD8"))
    )
    (comp (ref "L246")
      (value "SD8")
      (footprint "eagle-import:SD8")
      (libsource (lib "eagle-import") (part "SD8"))
    )
    (comp (ref "L247")
      (value "SD8")
      (footprint "eagle-import:SD8")
      (libsource (lib "eagle-import") (part "SD8"))
    )
    (comp (ref "L248")
      (value "SD8")
      (footprint "eagle-import:SD8")
      (libsource (lib "eagle-import") (part "SD8"))
    )
    (comp (ref "L249")
      (value "SD8")
      (footprint "eagle-import:SD8")
      (libsource (lib "eagle-import") (part "SD8"))
    )
    (comp (ref "L250")
      (value "SD8")
      (footprint "eagle-import:SD8")
      (libsource (lib "eagle-import") (part "SD8"))
    )
    (comp (ref "L251")
      (value "SD8")
      (footprint "eagle-import:SD8")
      (libsource (lib "eagle-import") (part "SD8"))
    )
    (comp (ref "L252")
      (value "SD8")
      (footprint "eagle-import:SD8")
      (libsource (lib "eagle-import") (part "SD8"))
    )
    (comp (ref "L253")
      (value "SD8")
      (footprint "eagle-import:SD8")
      (libsource (lib "eagle-import") (part "SD8"))
    )
    (comp (ref "L254")
      (value "SD8")
      (footprint "eagle-import:SD8")
      (libsource (lib "eagle-import") (part "SD8"))
    )
    (comp (ref "L255")
      (value "SD8")
      (footprint "eagle-import:SD8")
      (libsource (lib "eagle-import") (part "SD8"))
    )
    (comp (ref "L256")
      (value "SD8")
      (footprint "eagle-import:SD8")
      (libsource (lib "eagle-import") (part "SD8"))
    )
    (comp (ref "L273")
      (value "SD8")
      (footprint "eagle-import:SD8")
      (libsource (lib "eagle-import") (part "SD8"))
    )
    (comp (ref "L274")
      (value "SD8")
      (footprint "eagle-import:SD8")
      (libsource (lib "eagle-import") (part "SD8"))
    )
    (comp (ref "L275")
      (value "SD8")
      (footprint "eagle-import:SD8")
      (libsource (lib "eagle-import") (part "SD8"))
    )
    (comp (ref "L276")
      (value "SD8")
      (footprint "eagle-import:SD8")
      (libsource (lib "eagle-import") (part "SD8"))
    )
    (comp (ref "L277")
      (value "SD8")
      (footprint "eagle-import:SD8")
      (libsource (lib "eagle-import") (part "SD8"))
    )
    (comp (ref "L278")
      (value "SD8")
      (footprint "eagle-import:SD8")
      (libsource (lib "eagle-import") (part "SD8"))
    )
    (comp (ref "L279")
      (value "SD8")
      (footprint "eagle-import:SD8")
      (libsource (lib "eagle-import") (part "SD8"))
    )
    (comp (ref "L280")
      (value "SD8")
      (footprint "eagle-import:SD8")
      (libsource (lib "eagle-import") (part "SD8"))
    )
    (comp (ref "L281")
      (value "SD8")
      (footprint "eagle-import:SD8")
      (libsource (lib "eagle-import") (part "SD8"))
    )
    (comp (ref "L282")
      (value "SD8")
      (footprint "eagle-import:SD8")
      (libsource (lib "eagle-import") (part "SD8"))
    )
    (comp (ref "L283")
      (value "SD8")
      (footprint "eagle-import:SD8")
      (libsource (lib "eagle-import") (part "SD8"))
    )
    (comp (ref "L284")
      (value "SD8")
      (footprint "eagle-import:SD8")
      (libsource (lib "eagle-import") (part "SD8"))
    )
    (comp (ref "L285")
      (value "SD8")
      (footprint "eagle-import:SD8")
      (libsource (lib "eagle-import") (part "SD8"))
    )
    (comp (ref "L286")
      (value "SD8")
      (footprint "eagle-import:SD8")
      (libsource (lib "eagle-import") (part "SD8"))
    )
    (comp (ref "L287")
      (value "SD8")
      (footprint "eagle-import:SD8")
      (libsource (lib "eagle-import") (part "SD8"))
    )
    (comp (ref "L288")
      (value "SD8")
      (footprint "eagle-import:SD8")
      (libsource (lib "eagle-import") (part "SD8"))
    )
    (comp (ref "L305")
      (value "SD8")
      (footprint "eagle-import:SD8")
      (libsource (lib "eagle-import") (part "SD8"))
    )
    (comp (ref "L306")
      (value "SD8")
      (footprint "eagle-import:SD8")
      (libsource (lib "eagle-import") (part "SD8"))
    )
    (comp (ref "L307")
      (value "SD8")
      (footprint "eagle-import:SD8")
      (libsource (lib "eagle-import") (part "SD8"))
    )
    (comp (ref "L308")
      (value "SD8")
      (footprint "eagle-import:SD8")
      (libsource (lib "eagle-import") (part "SD8"))
    )
    (comp (ref "L309")
      (value "SD8")
      (footprint "eagle-import:SD8")
      (libsource (lib "eagle-import") (part "SD8"))
    )
    (comp (ref "L310")
      (value "SD8")
      (footprint "eagle-import:SD8")
      (libsource (lib "eagle-import") (part "SD8"))
    )
    (comp (ref "L311")
      (value "SD8")
      (footprint "eagle-import:SD8")
      (libsource (lib "eagle-import") (part "SD8"))
    )
    (comp (ref "L312")
      (value "SD8")
      (footprint "eagle-import:SD8")
      (libsource (lib "eagle-import") (part "SD8"))
    )
    (comp (ref "L313")
      (value "SD8")
      (footprint "eagle-import:SD8")
      (libsource (lib "eagle-import") (part "SD8"))
    )
    (comp (ref "L314")
      (value "SD8")
      (footprint "eagle-import:SD8")
      (libsource (lib "eagle-import") (part "SD8"))
    )
    (comp (ref "L315")
      (value "SD8")
      (footprint "eagle-import:SD8")
      (libsource (lib "eagle-import") (part "SD8"))
    )
    (comp (ref "L316")
      (value "SD8")
      (footprint "eagle-import:SD8")
      (libsource (lib "eagle-import") (part "SD8"))
    )
    (comp (ref "L317")
      (value "SD8")
      (footprint "eagle-import:SD8")
      (libsource (lib "eagle-import") (part "SD8"))
    )
    (comp (ref "L318")
      (value "SD8")
      (footprint "eagle-import:SD8")
      (libsource (lib "eagle-import") (part "SD8"))
    )
    (comp (ref "L319")
      (value "SD8")
      (footprint "eagle-import:SD8")
      (libsource (lib "eagle-import") (part "SD8"))
    )
    (comp (ref "L320")
      (value "SD8")
      (footprint "eagle-import:SD8")
      (libsource (lib "eagle-import") (part "SD8"))
    )
    (comp (ref "L337")
      (value "SD8")
      (footprint "eagle-import:SD8")
      (libsource (lib "eagle-import") (part "SD8"))
    )
    (comp (ref "L338")
      (value "SD8")
      (footprint "eagle-import:SD8")
      (libsource (lib "eagle-import") (part "SD8"))
    )
    (comp (ref "L339")
      (value "SD8")
      (footprint "eagle-import:SD8")
      (libsource (lib "eagle-import") (part "SD8"))
    )
    (comp (ref "L340")
      (value "SD8")
      (footprint "eagle-import:SD8")
      (libsource (lib "eagle-import") (part "SD8"))
    )
    (comp (ref "L341")
      (value "SD8")
      (footprint "eagle-import:SD8")
      (libsource (lib "eagle-import") (part "SD8"))
    )
    (comp (ref "L342")
      (value "SD8")
      (footprint "eagle-import:SD8")
      (libsource (lib "eagle-import") (part "SD8"))
    )
    (comp (ref "L343")
      (value "SD8")
      (footprint "eagle-import:SD8")
      (libsource (lib "eagle-import") (part "SD8"))
    )
    (comp (ref "L344")
      (value "SD8")
      (footprint "eagle-import:SD8")
      (libsource (lib "eagle-import") (part "SD8"))
    )
    (comp (ref "L345")
      (value "SD8")
      (footprint "eagle-import:SD8")
      (libsource (lib "eagle-import") (part "SD8"))
    )
    (comp (ref "L346")
      (value "SD8")
      (footprint "eagle-import:SD8")
      (libsource (lib "eagle-import") (part "SD8"))
    )
    (comp (ref "L347")
      (value "SD8")
      (footprint "eagle-import:SD8")
      (libsource (lib "eagle-import") (part "SD8"))
    )
    (comp (ref "L348")
      (value "SD8")
      (footprint "eagle-import:SD8")
      (libsource (lib "eagle-import") (part "SD8"))
    )
    (comp (ref "L349")
      (value "SD8")
      (footprint "eagle-import:SD8")
      (libsource (lib "eagle-import") (part "SD8"))
    )
    (comp (ref "L350")
      (value "SD8")
      (footprint "eagle-import:SD8")
      (libsource (lib "eagle-import") (part "SD8"))
    )
    (comp (ref "L351")
      (value "SD8")
      (footprint "eagle-import:SD8")
      (libsource (lib "eagle-import") (part "SD8"))
    )
    (comp (ref "L352")
      (value "SD8")
      (footprint "eagle-import:SD8")
      (libsource (lib "eagle-import") (part "SD8"))
    )
    (comp (ref "L369")
      (value "SD8")
      (footprint "eagle-import:SD8")
      (libsource (lib "eagle-import") (part "SD8"))
    )
    (comp (ref "L370")
      (value "SD8")
      (footprint "eagle-import:SD8")
      (libsource (lib "eagle-import") (part "SD8"))
    )
    (comp (ref "L371")
      (value "SD8")
      (footprint "eagle-import:SD8")
      (libsource (lib "eagle-import") (part "SD8"))
    )
    (comp (ref "L372")
      (value "SD8")
      (footprint "eagle-import:SD8")
      (libsource (lib "eagle-import") (part "SD8"))
    )
    (comp (ref "L373")
      (value "SD8")
      (footprint "eagle-import:SD8")
      (libsource (lib "eagle-import") (part "SD8"))
    )
    (comp (ref "L374")
      (value "SD8")
      (footprint "eagle-import:SD8")
      (libsource (lib "eagle-import") (part "SD8"))
    )
    (comp (ref "L375")
      (value "SD8")
      (footprint "eagle-import:SD8")
      (libsource (lib "eagle-import") (part "SD8"))
    )
    (comp (ref "L376")
      (value "SD8")
      (footprint "eagle-import:SD8")
      (libsource (lib "eagle-import") (part "SD8"))
    )
    (comp (ref "L377")
      (value "SD8")
      (footprint "eagle-import:SD8")
      (libsource (lib "eagle-import") (part "SD8"))
    )
    (comp (ref "L378")
      (value "SD8")
      (footprint "eagle-import:SD8")
      (libsource (lib "eagle-import") (part "SD8"))
    )
    (comp (ref "L379")
      (value "SD8")
      (footprint "eagle-import:SD8")
      (libsource (lib "eagle-import") (part "SD8"))
    )
    (comp (ref "L380")
      (value "SD8")
      (footprint "eagle-import:SD8")
      (libsource (lib "eagle-import") (part "SD8"))
    )
    (comp (ref "L381")
      (value "SD8")
      (footprint "eagle-import:SD8")
      (libsource (lib "eagle-import") (part "SD8"))
    )
    (comp (ref "L382")
      (value "SD8")
      (footprint "eagle-import:SD8")
      (libsource (lib "eagle-import") (part "SD8"))
    )
    (comp (ref "L383")
      (value "SD8")
      (footprint "eagle-import:SD8")
      (libsource (lib "eagle-import") (part "SD8"))
    )
    (comp (ref "L384")
      (value "SD8")
      (footprint "eagle-import:SD8")
      (libsource (lib "eagle-import") (part "SD8"))
    )
    (comp (ref "L401")
      (value "SD8")
      (footprint "eagle-import:SD8")
      (libsource (lib "eagle-import") (part "SD8"))
    )
    (comp (ref "L402")
      (value "SD8")
      (footprint "eagle-import:SD8")
      (libsource (lib "eagle-import") (part "SD8"))
    )
    (comp (ref "L403")
      (value "SD8")
      (footprint "eagle-import:SD8")
      (libsource (lib "eagle-import") (part "SD8"))
    )
    (comp (ref "L404")
      (value "SD8")
      (footprint "eagle-import:SD8")
      (libsource (lib "eagle-import") (part "SD8"))
    )
    (comp (ref "L405")
      (value "SD8")
      (footprint "eagle-import:SD8")
      (libsource (lib "eagle-import") (part "SD8"))
    )
    (comp (ref "L406")
      (value "SD8")
      (footprint "eagle-import:SD8")
      (libsource (lib "eagle-import") (part "SD8"))
    )
    (comp (ref "L407")
      (value "SD8")
      (footprint "eagle-import:SD8")
      (libsource (lib "eagle-import") (part "SD8"))
    )
    (comp (ref "L408")
      (value "SD8")
      (footprint "eagle-import:SD8")
      (libsource (lib "eagle-import") (part "SD8"))
    )
    (comp (ref "L409")
      (value "SD8")
      (footprint "eagle-import:SD8")
      (libsource (lib "eagle-import") (part "SD8"))
    )
    (comp (ref "L410")
      (value "SD8")
      (footprint "eagle-import:SD8")
      (libsource (lib "eagle-import") (part "SD8"))
    )
    (comp (ref "L411")
      (value "SD8")
      (footprint "eagle-import:SD8")
      (libsource (lib "eagle-import") (part "SD8"))
    )
    (comp (ref "L412")
      (value "SD8")
      (footprint "eagle-import:SD8")
      (libsource (lib "eagle-import") (part "SD8"))
    )
    (comp (ref "L413")
      (value "SD8")
      (footprint "eagle-import:SD8")
      (libsource (lib "eagle-import") (part "SD8"))
    )
    (comp (ref "L414")
      (value "SD8")
      (footprint "eagle-import:SD8")
      (libsource (lib "eagle-import") (part "SD8"))
    )
    (comp (ref "L415")
      (value "SD8")
      (footprint "eagle-import:SD8")
      (libsource (lib "eagle-import") (part "SD8"))
    )
    (comp (ref "L416")
      (value "SD8")
      (footprint "eagle-import:SD8")
      (libsource (lib "eagle-import") (part "SD8"))
    )
    (comp (ref "L433")
      (value "SD8")
      (footprint "eagle-import:SD8")
      (libsource (lib "eagle-import") (part "SD8"))
    )
    (comp (ref "L434")
      (value "SD8")
      (footprint "eagle-import:SD8")
      (libsource (lib "eagle-import") (part "SD8"))
    )
    (comp (ref "L435")
      (value "SD8")
      (footprint "eagle-import:SD8")
      (libsource (lib "eagle-import") (part "SD8"))
    )
    (comp (ref "L436")
      (value "SD8")
      (footprint "eagle-import:SD8")
      (libsource (lib "eagle-import") (part "SD8"))
    )
    (comp (ref "L437")
      (value "SD8")
      (footprint "eagle-import:SD8")
      (libsource (lib "eagle-import") (part "SD8"))
    )
    (comp (ref "L438")
      (value "SD8")
      (footprint "eagle-import:SD8")
      (libsource (lib "eagle-import") (part "SD8"))
    )
    (comp (ref "L439")
      (value "SD8")
      (footprint "eagle-import:SD8")
      (libsource (lib "eagle-import") (part "SD8"))
    )
    (comp (ref "L440")
      (value "SD8")
      (footprint "eagle-import:SD8")
      (libsource (lib "eagle-import") (part "SD8"))
    )
    (comp (ref "L441")
      (value "SD8")
      (footprint "eagle-import:SD8")
      (libsource (lib "eagle-import") (part "SD8"))
    )
    (comp (ref "L442")
      (value "SD8")
      (footprint "eagle-import:SD8")
      (libsource (lib "eagle-import") (part "SD8"))
    )
    (comp (ref "L443")
      (value "SD8")
      (footprint "eagle-import:SD8")
      (libsource (lib "eagle-import") (part "SD8"))
    )
    (comp (ref "L444")
      (value "SD8")
      (footprint "eagle-import:SD8")
      (libsource (lib "eagle-import") (part "SD8"))
    )
    (comp (ref "L445")
      (value "SD8")
      (footprint "eagle-import:SD8")
      (libsource (lib "eagle-import") (part "SD8"))
    )
    (comp (ref "L446")
      (value "SD8")
      (footprint "eagle-import:SD8")
      (libsource (lib "eagle-import") (part "SD8"))
    )
    (comp (ref "L447")
      (value "SD8")
      (footprint "eagle-import:SD8")
      (libsource (lib "eagle-import") (part "SD8"))
    )
    (comp (ref "L448")
      (value "SD8")
      (footprint "eagle-import:SD8")
      (libsource (lib "eagle-import") (part "SD8"))
    )
    (comp (ref "L465")
      (value "SD8")
      (footprint "eagle-import:SD8")
      (libsource (lib "eagle-import") (part "SD8"))
    )
    (comp (ref "L466")
      (value "SD8")
      (footprint "eagle-import:SD8")
      (libsource (lib "eagle-import") (part "SD8"))
    )
    (comp (ref "L467")
      (value "SD8")
      (footprint "eagle-import:SD8")
      (libsource (lib "eagle-import") (part "SD8"))
    )
    (comp (ref "L468")
      (value "SD8")
      (footprint "eagle-import:SD8")
      (libsource (lib "eagle-import") (part "SD8"))
    )
    (comp (ref "L469")
      (value "SD8")
      (footprint "eagle-import:SD8")
      (libsource (lib "eagle-import") (part "SD8"))
    )
    (comp (ref "L470")
      (value "SD8")
      (footprint "eagle-import:SD8")
      (libsource (lib "eagle-import") (part "SD8"))
    )
    (comp (ref "L471")
      (value "SD8")
      (footprint "eagle-import:SD8")
      (libsource (lib "eagle-import") (part "SD8"))
    )
    (comp (ref "L472")
      (value "SD8")
      (footprint "eagle-import:SD8")
      (libsource (lib "eagle-import") (part "SD8"))
    )
    (comp (ref "L473")
      (value "SD8")
      (footprint "eagle-import:SD8")
      (libsource (lib "eagle-import") (part "SD8"))
    )
    (comp (ref "L474")
      (value "SD8")
      (footprint "eagle-import:SD8")
      (libsource (lib "eagle-import") (part "SD8"))
    )
    (comp (ref "L475")
      (value "SD8")
      (footprint "eagle-import:SD8")
      (libsource (lib "eagle-import") (part "SD8"))
    )
    (comp (ref "L476")
      (value "SD8")
      (footprint "eagle-import:SD8")
      (libsource (lib "eagle-import") (part "SD8"))
    )
    (comp (ref "L477")
      (value "SD8")
      (footprint "eagle-import:SD8")
      (libsource (lib "eagle-import") (part "SD8"))
    )
    (comp (ref "L478")
      (value "SD8")
      (footprint "eagle-import:SD8")
      (libsource (lib "eagle-import") (part "SD8"))
    )
    (comp (ref "L479")
      (value "SD8")
      (footprint "eagle-import:SD8")
      (libsource (lib "eagle-import") (part "SD8"))
    )
    (comp (ref "L480")
      (value "SD8")
      (footprint "eagle-import:SD8")
      (libsource (lib "eagle-import") (part "SD8"))
    )
    (comp (ref "L497")
      (value "SD8")
      (footprint "eagle-import:SD8")
      (libsource (lib "eagle-import") (part "SD8"))
    )
    (comp (ref "L498")
      (value "SD8")
      (footprint "eagle-import:SD8")
      (libsource (lib "eagle-import") (part "SD8"))
    )
    (comp (ref "L499")
      (value "SD8")
      (footprint "eagle-import:SD8")
      (libsource (lib "eagle-import") (part "SD8"))
    )
    (comp (ref "L500")
      (value "SD8")
      (footprint "eagle-import:SD8")
      (libsource (lib "eagle-import") (part "SD8"))
    )
    (comp (ref "L501")
      (value "SD8")
      (footprint "eagle-import:SD8")
      (libsource (lib "eagle-import") (part "SD8"))
    )
    (comp (ref "L502")
      (value "SD8")
      (footprint "eagle-import:SD8")
      (libsource (lib "eagle-import") (part "SD8"))
    )
    (comp (ref "L503")
      (value "SD8")
      (footprint "eagle-import:SD8")
      (libsource (lib "eagle-import") (part "SD8"))
    )
    (comp (ref "L504")
      (value "SD8")
      (footprint "eagle-import:SD8")
      (libsource (lib "eagle-import") (part "SD8"))
    )
    (comp (ref "L505")
      (value "SD8")
      (footprint "eagle-import:SD8")
      (libsource (lib "eagle-import") (part "SD8"))
    )
    (comp (ref "L506")
      (value "SD8")
      (footprint "eagle-import:SD8")
      (libsource (lib "eagle-import") (part "SD8"))
    )
    (comp (ref "L507")
      (value "SD8")
      (footprint "eagle-import:SD8")
      (libsource (lib "eagle-import") (part "SD8"))
    )
    (comp (ref "L508")
      (value "SD8")
      (footprint "eagle-import:SD8")
      (libsource (lib "eagle-import") (part "SD8"))
    )
    (comp (ref "L509")
      (value "SD8")
      (footprint "eagle-import:SD8")
      (libsource (lib "eagle-import") (part "SD8"))
    )
    (comp (ref "L510")
      (value "SD8")
      (footprint "eagle-import:SD8")
      (libsource (lib "eagle-import") (part "SD8"))
    )
    (comp (ref "L511")
      (value "SD8")
      (footprint "eagle-import:SD8")
      (libsource (lib "eagle-import") (part "SD8"))
    )
    (comp (ref "L512")
      (value "SD8")
      (footprint "eagle-import:SD8")
      (libsource (lib "eagle-import") (part "SD8"))
    )
    (comp (ref "D529")
      (value "200mA/70V")
      (footprint "eagle-import:SOT23-3")
      (libsource (lib "eagle-import") (part "BAV99"))
    )
    (comp (ref "D530")
      (value "200mA/70V")
      (footprint "eagle-import:SOT23-3")
      (libsource (lib "eagle-import") (part "BAV99"))
    )
    (comp (ref "D531")
      (value "200mA/70V")
      (footprint "eagle-import:SOT23-3")
      (libsource (lib "eagle-import") (part "BAV99"))
    )
    (comp (ref "D532")
      (value "200mA/70V")
      (footprint "eagle-import:SOT23-3")
      (libsource (lib "eagle-import") (part "BAV99"))
    )
    (comp (ref "D533")
      (value "200mA/70V")
      (footprint "eagle-import:SOT23-3")
      (libsource (lib "eagle-import") (part "BAV99"))
    )
    (comp (ref "D534")
      (value "200mA/70V")
      (footprint "eagle-import:SOT23-3")
      (libsource (lib "eagle-import") (part "BAV99"))
    )
    (comp (ref "D535")
      (value "200mA/70V")
      (footprint "eagle-import:SOT23-3")
      (libsource (lib "eagle-import") (part "BAV99"))
    )
    (comp (ref "D536")
      (value "200mA/70V")
      (footprint "eagle-import:SOT23-3")
      (libsource (lib "eagle-import") (part "BAV99"))
    )
    (comp (ref "D537")
      (value "200mA/70V")
      (footprint "eagle-import:SOT23-3")
      (libsource (lib "eagle-import") (part "BAV99"))
    )
    (comp (ref "D538")
      (value "200mA/70V")
      (footprint "eagle-import:SOT23-3")
      (libsource (lib "eagle-import") (part "BAV99"))
    )
    (comp (ref "D539")
      (value "200mA/70V")
      (footprint "eagle-import:SOT23-3")
      (libsource (lib "eagle-import") (part "BAV99"))
    )
    (comp (ref "D540")
      (value "200mA/70V")
      (footprint "eagle-import:SOT23-3")
      (libsource (lib "eagle-import") (part "BAV99"))
    )
    (comp (ref "D541")
      (value "200mA/70V")
      (footprint "eagle-import:SOT23-3")
      (libsource (lib "eagle-import") (part "BAV99"))
    )
    (comp (ref "D542")
      (value "200mA/70V")
      (footprint "eagle-import:SOT23-3")
      (libsource (lib "eagle-import") (part "BAV99"))
    )
    (comp (ref "D543")
      (value "200mA/70V")
      (footprint "eagle-import:SOT23-3")
      (libsource (lib "eagle-import") (part "BAV99"))
    )
    (comp (ref "D544")
      (value "200mA/70V")
      (footprint "eagle-import:SOT23-3")
      (libsource (lib "eagle-import") (part "BAV99"))
    )
    (comp (ref "D561")
      (value "200mA/70V")
      (footprint "eagle-import:SOT23-3")
      (libsource (lib "eagle-import") (part "BAV99"))
    )
    (comp (ref "D562")
      (value "200mA/70V")
      (footprint "eagle-import:SOT23-3")
      (libsource (lib "eagle-import") (part "BAV99"))
    )
    (comp (ref "D563")
      (value "200mA/70V")
      (footprint "eagle-import:SOT23-3")
      (libsource (lib "eagle-import") (part "BAV99"))
    )
    (comp (ref "D564")
      (value "200mA/70V")
      (footprint "eagle-import:SOT23-3")
      (libsource (lib "eagle-import") (part "BAV99"))
    )
    (comp (ref "D565")
      (value "200mA/70V")
      (footprint "eagle-import:SOT23-3")
      (libsource (lib "eagle-import") (part "BAV99"))
    )
    (comp (ref "D566")
      (value "200mA/70V")
      (footprint "eagle-import:SOT23-3")
      (libsource (lib "eagle-import") (part "BAV99"))
    )
    (comp (ref "D567")
      (value "200mA/70V")
      (footprint "eagle-import:SOT23-3")
      (libsource (lib "eagle-import") (part "BAV99"))
    )
    (comp (ref "D568")
      (value "200mA/70V")
      (footprint "eagle-import:SOT23-3")
      (libsource (lib "eagle-import") (part "BAV99"))
    )
    (comp (ref "D569")
      (value "200mA/70V")
      (footprint "eagle-import:SOT23-3")
      (libsource (lib "eagle-import") (part "BAV99"))
    )
    (comp (ref "D570")
      (value "200mA/70V")
      (footprint "eagle-import:SOT23-3")
      (libsource (lib "eagle-import") (part "BAV99"))
    )
    (comp (ref "D571")
      (value "200mA/70V")
      (footprint "eagle-import:SOT23-3")
      (libsource (lib "eagle-import") (part "BAV99"))
    )
    (comp (ref "D572")
      (value "200mA/70V")
      (footprint "eagle-import:SOT23-3")
      (libsource (lib "eagle-import") (part "BAV99"))
    )
    (comp (ref "D573")
      (value "200mA/70V")
      (footprint "eagle-import:SOT23-3")
      (libsource (lib "eagle-import") (part "BAV99"))
    )
    (comp (ref "D574")
      (value "200mA/70V")
      (footprint "eagle-import:SOT23-3")
      (libsource (lib "eagle-import") (part "BAV99"))
    )
    (comp (ref "D575")
      (value "200mA/70V")
      (footprint "eagle-import:SOT23-3")
      (libsource (lib "eagle-import") (part "BAV99"))
    )
    (comp (ref "D576")
      (value "200mA/70V")
      (footprint "eagle-import:SOT23-3")
      (libsource (lib "eagle-import") (part "BAV99"))
    )
    (comp (ref "D593")
      (value "200mA/70V")
      (footprint "eagle-import:SOT23-3")
      (libsource (lib "eagle-import") (part "BAV99"))
    )
    (comp (ref "D594")
      (value "200mA/70V")
      (footprint "eagle-import:SOT23-3")
      (libsource (lib "eagle-import") (part "BAV99"))
    )
    (comp (ref "D595")
      (value "200mA/70V")
      (footprint "eagle-import:SOT23-3")
      (libsource (lib "eagle-import") (part "BAV99"))
    )
    (comp (ref "D596")
      (value "200mA/70V")
      (footprint "eagle-import:SOT23-3")
      (libsource (lib "eagle-import") (part "BAV99"))
    )
    (comp (ref "D597")
      (value "200mA/70V")
      (footprint "eagle-import:SOT23-3")
      (libsource (lib "eagle-import") (part "BAV99"))
    )
    (comp (ref "D598")
      (value "200mA/70V")
      (footprint "eagle-import:SOT23-3")
      (libsource (lib "eagle-import") (part "BAV99"))
    )
    (comp (ref "D599")
      (value "200mA/70V")
      (footprint "eagle-import:SOT23-3")
      (libsource (lib "eagle-import") (part "BAV99"))
    )
    (comp (ref "D600")
      (value "200mA/70V")
      (footprint "eagle-import:SOT23-3")
      (libsource (lib "eagle-import") (part "BAV99"))
    )
    (comp (ref "D601")
      (value "200mA/70V")
      (footprint "eagle-import:SOT23-3")
      (libsource (lib "eagle-import") (part "BAV99"))
    )
    (comp (ref "D602")
      (value "200mA/70V")
      (footprint "eagle-import:SOT23-3")
      (libsource (lib "eagle-import") (part "BAV99"))
    )
    (comp (ref "D603")
      (value "200mA/70V")
      (footprint "eagle-import:SOT23-3")
      (libsource (lib "eagle-import") (part "BAV99"))
    )
    (comp (ref "D604")
      (value "200mA/70V")
      (footprint "eagle-import:SOT23-3")
      (libsource (lib "eagle-import") (part "BAV99"))
    )
    (comp (ref "D605")
      (value "200mA/70V")
      (footprint "eagle-import:SOT23-3")
      (libsource (lib "eagle-import") (part "BAV99"))
    )
    (comp (ref "D606")
      (value "200mA/70V")
      (footprint "eagle-import:SOT23-3")
      (libsource (lib "eagle-import") (part "BAV99"))
    )
    (comp (ref "D607")
      (value "200mA/70V")
      (footprint "eagle-import:SOT23-3")
      (libsource (lib "eagle-import") (part "BAV99"))
    )
    (comp (ref "D608")
      (value "200mA/70V")
      (footprint "eagle-import:SOT23-3")
      (libsource (lib "eagle-import") (part "BAV99"))
    )
    (comp (ref "D625")
      (value "200mA/70V")
      (footprint "eagle-import:SOT23-3")
      (libsource (lib "eagle-import") (part "BAV99"))
    )
    (comp (ref "D626")
      (value "200mA/70V")
      (footprint "eagle-import:SOT23-3")
      (libsource (lib "eagle-import") (part "BAV99"))
    )
    (comp (ref "D627")
      (value "200mA/70V")
      (footprint "eagle-import:SOT23-3")
      (libsource (lib "eagle-import") (part "BAV99"))
    )
    (comp (ref "D628")
      (value "200mA/70V")
      (footprint "eagle-import:SOT23-3")
      (libsource (lib "eagle-import") (part "BAV99"))
    )
    (comp (ref "D629")
      (value "200mA/70V")
      (footprint "eagle-import:SOT23-3")
      (libsource (lib "eagle-import") (part "BAV99"))
    )
    (comp (ref "D630")
      (value "200mA/70V")
      (footprint "eagle-import:SOT23-3")
      (libsource (lib "eagle-import") (part "BAV99"))
    )
    (comp (ref "D631")
      (value "200mA/70V")
      (footprint "eagle-import:SOT23-3")
      (libsource (lib "eagle-import") (part "BAV99"))
    )
    (comp (ref "D632")
      (value "200mA/70V")
      (footprint "eagle-import:SOT23-3")
      (libsource (lib "eagle-import") (part "BAV99"))
    )
    (comp (ref "D633")
      (value "200mA/70V")
      (footprint "eagle-import:SOT23-3")
      (libsource (lib "eagle-import") (part "BAV99"))
    )
    (comp (ref "D634")
      (value "200mA/70V")
      (footprint "eagle-import:SOT23-3")
      (libsource (lib "eagle-import") (part "BAV99"))
    )
    (comp (ref "D635")
      (value "200mA/70V")
      (footprint "eagle-import:SOT23-3")
      (libsource (lib "eagle-import") (part "BAV99"))
    )
    (comp (ref "D636")
      (value "200mA/70V")
      (footprint "eagle-import:SOT23-3")
      (libsource (lib "eagle-import") (part "BAV99"))
    )
    (comp (ref "D637")
      (value "200mA/70V")
      (footprint "eagle-import:SOT23-3")
      (libsource (lib "eagle-import") (part "BAV99"))
    )
    (comp (ref "D638")
      (value "200mA/70V")
      (footprint "eagle-import:SOT23-3")
      (libsource (lib "eagle-import") (part "BAV99"))
    )
    (comp (ref "D639")
      (value "200mA/70V")
      (footprint "eagle-import:SOT23-3")
      (libsource (lib "eagle-import") (part "BAV99"))
    )
    (comp (ref "D640")
      (value "200mA/70V")
      (footprint "eagle-import:SOT23-3")
      (libsource (lib "eagle-import") (part "BAV99"))
    )
    (comp (ref "D657")
      (value "200mA/70V")
      (footprint "eagle-import:SOT23-3")
      (libsource (lib "eagle-import") (part "BAV99"))
    )
    (comp (ref "D658")
      (value "200mA/70V")
      (footprint "eagle-import:SOT23-3")
      (libsource (lib "eagle-import") (part "BAV99"))
    )
    (comp (ref "D659")
      (value "200mA/70V")
      (footprint "eagle-import:SOT23-3")
      (libsource (lib "eagle-import") (part "BAV99"))
    )
    (comp (ref "D660")
      (value "200mA/70V")
      (footprint "eagle-import:SOT23-3")
      (libsource (lib "eagle-import") (part "BAV99"))
    )
    (comp (ref "D661")
      (value "200mA/70V")
      (footprint "eagle-import:SOT23-3")
      (libsource (lib "eagle-import") (part "BAV99"))
    )
    (comp (ref "D662")
      (value "200mA/70V")
      (footprint "eagle-import:SOT23-3")
      (libsource (lib "eagle-import") (part "BAV99"))
    )
    (comp (ref "D663")
      (value "200mA/70V")
      (footprint "eagle-import:SOT23-3")
      (libsource (lib "eagle-import") (part "BAV99"))
    )
    (comp (ref "D664")
      (value "200mA/70V")
      (footprint "eagle-import:SOT23-3")
      (libsource (lib "eagle-import") (part "BAV99"))
    )
    (comp (ref "D665")
      (value "200mA/70V")
      (footprint "eagle-import:SOT23-3")
      (libsource (lib "eagle-import") (part "BAV99"))
    )
    (comp (ref "D666")
      (value "200mA/70V")
      (footprint "eagle-import:SOT23-3")
      (libsource (lib "eagle-import") (part "BAV99"))
    )
    (comp (ref "D667")
      (value "200mA/70V")
      (footprint "eagle-import:SOT23-3")
      (libsource (lib "eagle-import") (part "BAV99"))
    )
    (comp (ref "D668")
      (value "200mA/70V")
      (footprint "eagle-import:SOT23-3")
      (libsource (lib "eagle-import") (part "BAV99"))
    )
    (comp (ref "D669")
      (value "200mA/70V")
      (footprint "eagle-import:SOT23-3")
      (libsource (lib "eagle-import") (part "BAV99"))
    )
    (comp (ref "D670")
      (value "200mA/70V")
      (footprint "eagle-import:SOT23-3")
      (libsource (lib "eagle-import") (part "BAV99"))
    )
    (comp (ref "D671")
      (value "200mA/70V")
      (footprint "eagle-import:SOT23-3")
      (libsource (lib "eagle-import") (part "BAV99"))
    )
    (comp (ref "D672")
      (value "200mA/70V")
      (footprint "eagle-import:SOT23-3")
      (libsource (lib "eagle-import") (part "BAV99"))
    )
    (comp (ref "D689")
      (value "200mA/70V")
      (footprint "eagle-import:SOT23-3")
      (libsource (lib "eagle-import") (part "BAV99"))
    )
    (comp (ref "D690")
      (value "200mA/70V")
      (footprint "eagle-import:SOT23-3")
      (libsource (lib "eagle-import") (part "BAV99"))
    )
    (comp (ref "D691")
      (value "200mA/70V")
      (footprint "eagle-import:SOT23-3")
      (libsource (lib "eagle-import") (part "BAV99"))
    )
    (comp (ref "D692")
      (value "200mA/70V")
      (footprint "eagle-import:SOT23-3")
      (libsource (lib "eagle-import") (part "BAV99"))
    )
    (comp (ref "D693")
      (value "200mA/70V")
      (footprint "eagle-import:SOT23-3")
      (libsource (lib "eagle-import") (part "BAV99"))
    )
    (comp (ref "D694")
      (value "200mA/70V")
      (footprint "eagle-import:SOT23-3")
      (libsource (lib "eagle-import") (part "BAV99"))
    )
    (comp (ref "D695")
      (value "200mA/70V")
      (footprint "eagle-import:SOT23-3")
      (libsource (lib "eagle-import") (part "BAV99"))
    )
    (comp (ref "D696")
      (value "200mA/70V")
      (footprint "eagle-import:SOT23-3")
      (libsource (lib "eagle-import") (part "BAV99"))
    )
    (comp (ref "D697")
      (value "200mA/70V")
      (footprint "eagle-import:SOT23-3")
      (libsource (lib "eagle-import") (part "BAV99"))
    )
    (comp (ref "D698")
      (value "200mA/70V")
      (footprint "eagle-import:SOT23-3")
      (libsource (lib "eagle-import") (part "BAV99"))
    )
    (comp (ref "D699")
      (value "200mA/70V")
      (footprint "eagle-import:SOT23-3")
      (libsource (lib "eagle-import") (part "BAV99"))
    )
    (comp (ref "D700")
      (value "200mA/70V")
      (footprint "eagle-import:SOT23-3")
      (libsource (lib "eagle-import") (part "BAV99"))
    )
    (comp (ref "D701")
      (value "200mA/70V")
      (footprint "eagle-import:SOT23-3")
      (libsource (lib "eagle-import") (part "BAV99"))
    )
    (comp (ref "D702")
      (value "200mA/70V")
      (footprint "eagle-import:SOT23-3")
      (libsource (lib "eagle-import") (part "BAV99"))
    )
    (comp (ref "D703")
      (value "200mA/70V")
      (footprint "eagle-import:SOT23-3")
      (libsource (lib "eagle-import") (part "BAV99"))
    )
    (comp (ref "D704")
      (value "200mA/70V")
      (footprint "eagle-import:SOT23-3")
      (libsource (lib "eagle-import") (part "BAV99"))
    )
    (comp (ref "D721")
      (value "200mA/70V")
      (footprint "eagle-import:SOT23-3")
      (libsource (lib "eagle-import") (part "BAV99"))
    )
    (comp (ref "D722")
      (value "200mA/70V")
      (footprint "eagle-import:SOT23-3")
      (libsource (lib "eagle-import") (part "BAV99"))
    )
    (comp (ref "D723")
      (value "200mA/70V")
      (footprint "eagle-import:SOT23-3")
      (libsource (lib "eagle-import") (part "BAV99"))
    )
    (comp (ref "D724")
      (value "200mA/70V")
      (footprint "eagle-import:SOT23-3")
      (libsource (lib "eagle-import") (part "BAV99"))
    )
    (comp (ref "D725")
      (value "200mA/70V")
      (footprint "eagle-import:SOT23-3")
      (libsource (lib "eagle-import") (part "BAV99"))
    )
    (comp (ref "D726")
      (value "200mA/70V")
      (footprint "eagle-import:SOT23-3")
      (libsource (lib "eagle-import") (part "BAV99"))
    )
    (comp (ref "D727")
      (value "200mA/70V")
      (footprint "eagle-import:SOT23-3")
      (libsource (lib "eagle-import") (part "BAV99"))
    )
    (comp (ref "D728")
      (value "200mA/70V")
      (footprint "eagle-import:SOT23-3")
      (libsource (lib "eagle-import") (part "BAV99"))
    )
    (comp (ref "D729")
      (value "200mA/70V")
      (footprint "eagle-import:SOT23-3")
      (libsource (lib "eagle-import") (part "BAV99"))
    )
    (comp (ref "D730")
      (value "200mA/70V")
      (footprint "eagle-import:SOT23-3")
      (libsource (lib "eagle-import") (part "BAV99"))
    )
    (comp (ref "D731")
      (value "200mA/70V")
      (footprint "eagle-import:SOT23-3")
      (libsource (lib "eagle-import") (part "BAV99"))
    )
    (comp (ref "D732")
      (value "200mA/70V")
      (footprint "eagle-import:SOT23-3")
      (libsource (lib "eagle-import") (part "BAV99"))
    )
    (comp (ref "D733")
      (value "200mA/70V")
      (footprint "eagle-import:SOT23-3")
      (libsource (lib "eagle-import") (part "BAV99"))
    )
    (comp (ref "D734")
      (value "200mA/70V")
      (footprint "eagle-import:SOT23-3")
      (libsource (lib "eagle-import") (part "BAV99"))
    )
    (comp (ref "D735")
      (value "200mA/70V")
      (footprint "eagle-import:SOT23-3")
      (libsource (lib "eagle-import") (part "BAV99"))
    )
    (comp (ref "D736")
      (value "200mA/70V")
      (footprint "eagle-import:SOT23-3")
      (libsource (lib "eagle-import") (part "BAV99"))
    )
    (comp (ref "D753")
      (value "200mA/70V")
      (footprint "eagle-import:SOT23-3")
      (libsource (lib "eagle-import") (part "BAV99"))
    )
    (comp (ref "D754")
      (value "200mA/70V")
      (footprint "eagle-import:SOT23-3")
      (libsource (lib "eagle-import") (part "BAV99"))
    )
    (comp (ref "D755")
      (value "200mA/70V")
      (footprint "eagle-import:SOT23-3")
      (libsource (lib "eagle-import") (part "BAV99"))
    )
    (comp (ref "D756")
      (value "200mA/70V")
      (footprint "eagle-import:SOT23-3")
      (libsource (lib "eagle-import") (part "BAV99"))
    )
    (comp (ref "D757")
      (value "200mA/70V")
      (footprint "eagle-import:SOT23-3")
      (libsource (lib "eagle-import") (part "BAV99"))
    )
    (comp (ref "D758")
      (value "200mA/70V")
      (footprint "eagle-import:SOT23-3")
      (libsource (lib "eagle-import") (part "BAV99"))
    )
    (comp (ref "D759")
      (value "200mA/70V")
      (footprint "eagle-import:SOT23-3")
      (libsource (lib "eagle-import") (part "BAV99"))
    )
    (comp (ref "D760")
      (value "200mA/70V")
      (footprint "eagle-import:SOT23-3")
      (libsource (lib "eagle-import") (part "BAV99"))
    )
    (comp (ref "D761")
      (value "200mA/70V")
      (footprint "eagle-import:SOT23-3")
      (libsource (lib "eagle-import") (part "BAV99"))
    )
    (comp (ref "D762")
      (value "200mA/70V")
      (footprint "eagle-import:SOT23-3")
      (libsource (lib "eagle-import") (part "BAV99"))
    )
    (comp (ref "D763")
      (value "200mA/70V")
      (footprint "eagle-import:SOT23-3")
      (libsource (lib "eagle-import") (part "BAV99"))
    )
    (comp (ref "D764")
      (value "200mA/70V")
      (footprint "eagle-import:SOT23-3")
      (libsource (lib "eagle-import") (part "BAV99"))
    )
    (comp (ref "D765")
      (value "200mA/70V")
      (footprint "eagle-import:SOT23-3")
      (libsource (lib "eagle-import") (part "BAV99"))
    )
    (comp (ref "D766")
      (value "200mA/70V")
      (footprint "eagle-import:SOT23-3")
      (libsource (lib "eagle-import") (part "BAV99"))
    )
    (comp (ref "D767")
      (value "200mA/70V")
      (footprint "eagle-import:SOT23-3")
      (libsource (lib "eagle-import") (part "BAV99"))
    )
    (comp (ref "D768")
      (value "200mA/70V")
      (footprint "eagle-import:SOT23-3")
      (libsource (lib "eagle-import") (part "BAV99"))
    )
    (comp (ref "D785")
      (value "200mA/70V")
      (footprint "eagle-import:SOT23-3")
      (libsource (lib "eagle-import") (part "BAV99"))
    )
    (comp (ref "D786")
      (value "200mA/70V")
      (footprint "eagle-import:SOT23-3")
      (libsource (lib "eagle-import") (part "BAV99"))
    )
    (comp (ref "D787")
      (value "200mA/70V")
      (footprint "eagle-import:SOT23-3")
      (libsource (lib "eagle-import") (part "BAV99"))
    )
    (comp (ref "D788")
      (value "200mA/70V")
      (footprint "eagle-import:SOT23-3")
      (libsource (lib "eagle-import") (part "BAV99"))
    )
    (comp (ref "D789")
      (value "200mA/70V")
      (footprint "eagle-import:SOT23-3")
      (libsource (lib "eagle-import") (part "BAV99"))
    )
    (comp (ref "D790")
      (value "200mA/70V")
      (footprint "eagle-import:SOT23-3")
      (libsource (lib "eagle-import") (part "BAV99"))
    )
    (comp (ref "D791")
      (value "200mA/70V")
      (footprint "eagle-import:SOT23-3")
      (libsource (lib "eagle-import") (part "BAV99"))
    )
    (comp (ref "D792")
      (value "200mA/70V")
      (footprint "eagle-import:SOT23-3")
      (libsource (lib "eagle-import") (part "BAV99"))
    )
    (comp (ref "D793")
      (value "200mA/70V")
      (footprint "eagle-import:SOT23-3")
      (libsource (lib "eagle-import") (part "BAV99"))
    )
    (comp (ref "D794")
      (value "200mA/70V")
      (footprint "eagle-import:SOT23-3")
      (libsource (lib "eagle-import") (part "BAV99"))
    )
    (comp (ref "D795")
      (value "200mA/70V")
      (footprint "eagle-import:SOT23-3")
      (libsource (lib "eagle-import") (part "BAV99"))
    )
    (comp (ref "D796")
      (value "200mA/70V")
      (footprint "eagle-import:SOT23-3")
      (libsource (lib "eagle-import") (part "BAV99"))
    )
    (comp (ref "D797")
      (value "200mA/70V")
      (footprint "eagle-import:SOT23-3")
      (libsource (lib "eagle-import") (part "BAV99"))
    )
    (comp (ref "D798")
      (value "200mA/70V")
      (footprint "eagle-import:SOT23-3")
      (libsource (lib "eagle-import") (part "BAV99"))
    )
    (comp (ref "D799")
      (value "200mA/70V")
      (footprint "eagle-import:SOT23-3")
      (libsource (lib "eagle-import") (part "BAV99"))
    )
    (comp (ref "D800")
      (value "200mA/70V")
      (footprint "eagle-import:SOT23-3")
      (libsource (lib "eagle-import") (part "BAV99"))
    )
    (comp (ref "D817")
      (value "200mA/70V")
      (footprint "eagle-import:SOT23-3")
      (libsource (lib "eagle-import") (part "BAV99"))
    )
    (comp (ref "D818")
      (value "200mA/70V")
      (footprint "eagle-import:SOT23-3")
      (libsource (lib "eagle-import") (part "BAV99"))
    )
    (comp (ref "D819")
      (value "200mA/70V")
      (footprint "eagle-import:SOT23-3")
      (libsource (lib "eagle-import") (part "BAV99"))
    )
    (comp (ref "D820")
      (value "200mA/70V")
      (footprint "eagle-import:SOT23-3")
      (libsource (lib "eagle-import") (part "BAV99"))
    )
    (comp (ref "D821")
      (value "200mA/70V")
      (footprint "eagle-import:SOT23-3")
      (libsource (lib "eagle-import") (part "BAV99"))
    )
    (comp (ref "D822")
      (value "200mA/70V")
      (footprint "eagle-import:SOT23-3")
      (libsource (lib "eagle-import") (part "BAV99"))
    )
    (comp (ref "D823")
      (value "200mA/70V")
      (footprint "eagle-import:SOT23-3")
      (libsource (lib "eagle-import") (part "BAV99"))
    )
    (comp (ref "D824")
      (value "200mA/70V")
      (footprint "eagle-import:SOT23-3")
      (libsource (lib "eagle-import") (part "BAV99"))
    )
    (comp (ref "D825")
      (value "200mA/70V")
      (footprint "eagle-import:SOT23-3")
      (libsource (lib "eagle-import") (part "BAV99"))
    )
    (comp (ref "D826")
      (value "200mA/70V")
      (footprint "eagle-import:SOT23-3")
      (libsource (lib "eagle-import") (part "BAV99"))
    )
    (comp (ref "D827")
      (value "200mA/70V")
      (footprint "eagle-import:SOT23-3")
      (libsource (lib "eagle-import") (part "BAV99"))
    )
    (comp (ref "D828")
      (value "200mA/70V")
      (footprint "eagle-import:SOT23-3")
      (libsource (lib "eagle-import") (part "BAV99"))
    )
    (comp (ref "D829")
      (value "200mA/70V")
      (footprint "eagle-import:SOT23-3")
      (libsource (lib "eagle-import") (part "BAV99"))
    )
    (comp (ref "D830")
      (value "200mA/70V")
      (footprint "eagle-import:SOT23-3")
      (libsource (lib "eagle-import") (part "BAV99"))
    )
    (comp (ref "D831")
      (value "200mA/70V")
      (footprint "eagle-import:SOT23-3")
      (libsource (lib "eagle-import") (part "BAV99"))
    )
    (comp (ref "D832")
      (value "200mA/70V")
      (footprint "eagle-import:SOT23-3")
      (libsource (lib "eagle-import") (part "BAV99"))
    )
    (comp (ref "D849")
      (value "200mA/70V")
      (footprint "eagle-import:SOT23-3")
      (libsource (lib "eagle-import") (part "BAV99"))
    )
    (comp (ref "D850")
      (value "200mA/70V")
      (footprint "eagle-import:SOT23-3")
      (libsource (lib "eagle-import") (part "BAV99"))
    )
    (comp (ref "D851")
      (value "200mA/70V")
      (footprint "eagle-import:SOT23-3")
      (libsource (lib "eagle-import") (part "BAV99"))
    )
    (comp (ref "D852")
      (value "200mA/70V")
      (footprint "eagle-import:SOT23-3")
      (libsource (lib "eagle-import") (part "BAV99"))
    )
    (comp (ref "D853")
      (value "200mA/70V")
      (footprint "eagle-import:SOT23-3")
      (libsource (lib "eagle-import") (part "BAV99"))
    )
    (comp (ref "D854")
      (value "200mA/70V")
      (footprint "eagle-import:SOT23-3")
      (libsource (lib "eagle-import") (part "BAV99"))
    )
    (comp (ref "D855")
      (value "200mA/70V")
      (footprint "eagle-import:SOT23-3")
      (libsource (lib "eagle-import") (part "BAV99"))
    )
    (comp (ref "D856")
      (value "200mA/70V")
      (footprint "eagle-import:SOT23-3")
      (libsource (lib "eagle-import") (part "BAV99"))
    )
    (comp (ref "D857")
      (value "200mA/70V")
      (footprint "eagle-import:SOT23-3")
      (libsource (lib "eagle-import") (part "BAV99"))
    )
    (comp (ref "D858")
      (value "200mA/70V")
      (footprint "eagle-import:SOT23-3")
      (libsource (lib "eagle-import") (part "BAV99"))
    )
    (comp (ref "D859")
      (value "200mA/70V")
      (footprint "eagle-import:SOT23-3")
      (libsource (lib "eagle-import") (part "BAV99"))
    )
    (comp (ref "D860")
      (value "200mA/70V")
      (footprint "eagle-import:SOT23-3")
      (libsource (lib "eagle-import") (part "BAV99"))
    )
    (comp (ref "D861")
      (value "200mA/70V")
      (footprint "eagle-import:SOT23-3")
      (libsource (lib "eagle-import") (part "BAV99"))
    )
    (comp (ref "D862")
      (value "200mA/70V")
      (footprint "eagle-import:SOT23-3")
      (libsource (lib "eagle-import") (part "BAV99"))
    )
    (comp (ref "D863")
      (value "200mA/70V")
      (footprint "eagle-import:SOT23-3")
      (libsource (lib "eagle-import") (part "BAV99"))
    )
    (comp (ref "D864")
      (value "200mA/70V")
      (footprint "eagle-import:SOT23-3")
      (libsource (lib "eagle-import") (part "BAV99"))
    )
    (comp (ref "D881")
      (value "200mA/70V")
      (footprint "eagle-import:SOT23-3")
      (libsource (lib "eagle-import") (part "BAV99"))
    )
    (comp (ref "D882")
      (value "200mA/70V")
      (footprint "eagle-import:SOT23-3")
      (libsource (lib "eagle-import") (part "BAV99"))
    )
    (comp (ref "D883")
      (value "200mA/70V")
      (footprint "eagle-import:SOT23-3")
      (libsource (lib "eagle-import") (part "BAV99"))
    )
    (comp (ref "D884")
      (value "200mA/70V")
      (footprint "eagle-import:SOT23-3")
      (libsource (lib "eagle-import") (part "BAV99"))
    )
    (comp (ref "D885")
      (value "200mA/70V")
      (footprint "eagle-import:SOT23-3")
      (libsource (lib "eagle-import") (part "BAV99"))
    )
    (comp (ref "D886")
      (value "200mA/70V")
      (footprint "eagle-import:SOT23-3")
      (libsource (lib "eagle-import") (part "BAV99"))
    )
    (comp (ref "D887")
      (value "200mA/70V")
      (footprint "eagle-import:SOT23-3")
      (libsource (lib "eagle-import") (part "BAV99"))
    )
    (comp (ref "D888")
      (value "200mA/70V")
      (footprint "eagle-import:SOT23-3")
      (libsource (lib "eagle-import") (part "BAV99"))
    )
    (comp (ref "D889")
      (value "200mA/70V")
      (footprint "eagle-import:SOT23-3")
      (libsource (lib "eagle-import") (part "BAV99"))
    )
    (comp (ref "D890")
      (value "200mA/70V")
      (footprint "eagle-import:SOT23-3")
      (libsource (lib "eagle-import") (part "BAV99"))
    )
    (comp (ref "D891")
      (value "200mA/70V")
      (footprint "eagle-import:SOT23-3")
      (libsource (lib "eagle-import") (part "BAV99"))
    )
    (comp (ref "D892")
      (value "200mA/70V")
      (footprint "eagle-import:SOT23-3")
      (libsource (lib "eagle-import") (part "BAV99"))
    )
    (comp (ref "D893")
      (value "200mA/70V")
      (footprint "eagle-import:SOT23-3")
      (libsource (lib "eagle-import") (part "BAV99"))
    )
    (comp (ref "D894")
      (value "200mA/70V")
      (footprint "eagle-import:SOT23-3")
      (libsource (lib "eagle-import") (part "BAV99"))
    )
    (comp (ref "D895")
      (value "200mA/70V")
      (footprint "eagle-import:SOT23-3")
      (libsource (lib "eagle-import") (part "BAV99"))
    )
    (comp (ref "D896")
      (value "200mA/70V")
      (footprint "eagle-import:SOT23-3")
      (libsource (lib "eagle-import") (part "BAV99"))
    )
    (comp (ref "D913")
      (value "200mA/70V")
      (footprint "eagle-import:SOT23-3")
      (libsource (lib "eagle-import") (part "BAV99"))
    )
    (comp (ref "D914")
      (value "200mA/70V")
      (footprint "eagle-import:SOT23-3")
      (libsource (lib "eagle-import") (part "BAV99"))
    )
    (comp (ref "D915")
      (value "200mA/70V")
      (footprint "eagle-import:SOT23-3")
      (libsource (lib "eagle-import") (part "BAV99"))
    )
    (comp (ref "D916")
      (value "200mA/70V")
      (footprint "eagle-import:SOT23-3")
      (libsource (lib "eagle-import") (part "BAV99"))
    )
    (comp (ref "D917")
      (value "200mA/70V")
      (footprint "eagle-import:SOT23-3")
      (libsource (lib "eagle-import") (part "BAV99"))
    )
    (comp (ref "D918")
      (value "200mA/70V")
      (footprint "eagle-import:SOT23-3")
      (libsource (lib "eagle-import") (part "BAV99"))
    )
    (comp (ref "D919")
      (value "200mA/70V")
      (footprint "eagle-import:SOT23-3")
      (libsource (lib "eagle-import") (part "BAV99"))
    )
    (comp (ref "D920")
      (value "200mA/70V")
      (footprint "eagle-import:SOT23-3")
      (libsource (lib "eagle-import") (part "BAV99"))
    )
    (comp (ref "D921")
      (value "200mA/70V")
      (footprint "eagle-import:SOT23-3")
      (libsource (lib "eagle-import") (part "BAV99"))
    )
    (comp (ref "D922")
      (value "200mA/70V")
      (footprint "eagle-import:SOT23-3")
      (libsource (lib "eagle-import") (part "BAV99"))
    )
    (comp (ref "D923")
      (value "200mA/70V")
      (footprint "eagle-import:SOT23-3")
      (libsource (lib "eagle-import") (part "BAV99"))
    )
    (comp (ref "D924")
      (value "200mA/70V")
      (footprint "eagle-import:SOT23-3")
      (libsource (lib "eagle-import") (part "BAV99"))
    )
    (comp (ref "D925")
      (value "200mA/70V")
      (footprint "eagle-import:SOT23-3")
      (libsource (lib "eagle-import") (part "BAV99"))
    )
    (comp (ref "D926")
      (value "200mA/70V")
      (footprint "eagle-import:SOT23-3")
      (libsource (lib "eagle-import") (part "BAV99"))
    )
    (comp (ref "D927")
      (value "200mA/70V")
      (footprint "eagle-import:SOT23-3")
      (libsource (lib "eagle-import") (part "BAV99"))
    )
    (comp (ref "D928")
      (value "200mA/70V")
      (footprint "eagle-import:SOT23-3")
      (libsource (lib "eagle-import") (part "BAV99"))
    )
    (comp (ref "D945")
      (value "200mA/70V")
      (footprint "eagle-import:SOT23-3")
      (libsource (lib "eagle-import") (part "BAV99"))
    )
    (comp (ref "D946")
      (value "200mA/70V")
      (footprint "eagle-import:SOT23-3")
      (libsource (lib "eagle-import") (part "BAV99"))
    )
    (comp (ref "D947")
      (value "200mA/70V")
      (footprint "eagle-import:SOT23-3")
      (libsource (lib "eagle-import") (part "BAV99"))
    )
    (comp (ref "D948")
      (value "200mA/70V")
      (footprint "eagle-import:SOT23-3")
      (libsource (lib "eagle-import") (part "BAV99"))
    )
    (comp (ref "D949")
      (value "200mA/70V")
      (footprint "eagle-import:SOT23-3")
      (libsource (lib "eagle-import") (part "BAV99"))
    )
    (comp (ref "D950")
      (value "200mA/70V")
      (footprint "eagle-import:SOT23-3")
      (libsource (lib "eagle-import") (part "BAV99"))
    )
    (comp (ref "D951")
      (value "200mA/70V")
      (footprint "eagle-import:SOT23-3")
      (libsource (lib "eagle-import") (part "BAV99"))
    )
    (comp (ref "D952")
      (value "200mA/70V")
      (footprint "eagle-import:SOT23-3")
      (libsource (lib "eagle-import") (part "BAV99"))
    )
    (comp (ref "D953")
      (value "200mA/70V")
      (footprint "eagle-import:SOT23-3")
      (libsource (lib "eagle-import") (part "BAV99"))
    )
    (comp (ref "D954")
      (value "200mA/70V")
      (footprint "eagle-import:SOT23-3")
      (libsource (lib "eagle-import") (part "BAV99"))
    )
    (comp (ref "D955")
      (value "200mA/70V")
      (footprint "eagle-import:SOT23-3")
      (libsource (lib "eagle-import") (part "BAV99"))
    )
    (comp (ref "D956")
      (value "200mA/70V")
      (footprint "eagle-import:SOT23-3")
      (libsource (lib "eagle-import") (part "BAV99"))
    )
    (comp (ref "D957")
      (value "200mA/70V")
      (footprint "eagle-import:SOT23-3")
      (libsource (lib "eagle-import") (part "BAV99"))
    )
    (comp (ref "D958")
      (value "200mA/70V")
      (footprint "eagle-import:SOT23-3")
      (libsource (lib "eagle-import") (part "BAV99"))
    )
    (comp (ref "D959")
      (value "200mA/70V")
      (footprint "eagle-import:SOT23-3")
      (libsource (lib "eagle-import") (part "BAV99"))
    )
    (comp (ref "D960")
      (value "200mA/70V")
      (footprint "eagle-import:SOT23-3")
      (libsource (lib "eagle-import") (part "BAV99"))
    )
    (comp (ref "D977")
      (value "200mA/70V")
      (footprint "eagle-import:SOT23-3")
      (libsource (lib "eagle-import") (part "BAV99"))
    )
    (comp (ref "D978")
      (value "200mA/70V")
      (footprint "eagle-import:SOT23-3")
      (libsource (lib "eagle-import") (part "BAV99"))
    )
    (comp (ref "D979")
      (value "200mA/70V")
      (footprint "eagle-import:SOT23-3")
      (libsource (lib "eagle-import") (part "BAV99"))
    )
    (comp (ref "D980")
      (value "200mA/70V")
      (footprint "eagle-import:SOT23-3")
      (libsource (lib "eagle-import") (part "BAV99"))
    )
    (comp (ref "D981")
      (value "200mA/70V")
      (footprint "eagle-import:SOT23-3")
      (libsource (lib "eagle-import") (part "BAV99"))
    )
    (comp (ref "D982")
      (value "200mA/70V")
      (footprint "eagle-import:SOT23-3")
      (libsource (lib "eagle-import") (part "BAV99"))
    )
    (comp (ref "D983")
      (value "200mA/70V")
      (footprint "eagle-import:SOT23-3")
      (libsource (lib "eagle-import") (part "BAV99"))
    )
    (comp (ref "D984")
      (value "200mA/70V")
      (footprint "eagle-import:SOT23-3")
      (libsource (lib "eagle-import") (part "BAV99"))
    )
    (comp (ref "D985")
      (value "200mA/70V")
      (footprint "eagle-import:SOT23-3")
      (libsource (lib "eagle-import") (part "BAV99"))
    )
    (comp (ref "D986")
      (value "200mA/70V")
      (footprint "eagle-import:SOT23-3")
      (libsource (lib "eagle-import") (part "BAV99"))
    )
    (comp (ref "D987")
      (value "200mA/70V")
      (footprint "eagle-import:SOT23-3")
      (libsource (lib "eagle-import") (part "BAV99"))
    )
    (comp (ref "D988")
      (value "200mA/70V")
      (footprint "eagle-import:SOT23-3")
      (libsource (lib "eagle-import") (part "BAV99"))
    )
    (comp (ref "D989")
      (value "200mA/70V")
      (footprint "eagle-import:SOT23-3")
      (libsource (lib "eagle-import") (part "BAV99"))
    )
    (comp (ref "D990")
      (value "200mA/70V")
      (footprint "eagle-import:SOT23-3")
      (libsource (lib "eagle-import") (part "BAV99"))
    )
    (comp (ref "D991")
      (value "200mA/70V")
      (footprint "eagle-import:SOT23-3")
      (libsource (lib "eagle-import") (part "BAV99"))
    )
    (comp (ref "D992")
      (value "200mA/70V")
      (footprint "eagle-import:SOT23-3")
      (libsource (lib "eagle-import") (part "BAV99"))
    )
    (comp (ref "D1009")
      (value "200mA/70V")
      (footprint "eagle-import:SOT23-3")
      (libsource (lib "eagle-import") (part "BAV99"))
    )
    (comp (ref "D1010")
      (value "200mA/70V")
      (footprint "eagle-import:SOT23-3")
      (libsource (lib "eagle-import") (part "BAV99"))
    )
    (comp (ref "D1011")
      (value "200mA/70V")
      (footprint "eagle-import:SOT23-3")
      (libsource (lib "eagle-import") (part "BAV99"))
    )
    (comp (ref "D1012")
      (value "200mA/70V")
      (footprint "eagle-import:SOT23-3")
      (libsource (lib "eagle-import") (part "BAV99"))
    )
    (comp (ref "D1013")
      (value "200mA/70V")
      (footprint "eagle-import:SOT23-3")
      (libsource (lib "eagle-import") (part "BAV99"))
    )
    (comp (ref "D1014")
      (value "200mA/70V")
      (footprint "eagle-import:SOT23-3")
      (libsource (lib "eagle-import") (part "BAV99"))
    )
    (comp (ref "D1015")
      (value "200mA/70V")
      (footprint "eagle-import:SOT23-3")
      (libsource (lib "eagle-import") (part "BAV99"))
    )
    (comp (ref "D1016")
      (value "200mA/70V")
      (footprint "eagle-import:SOT23-3")
      (libsource (lib "eagle-import") (part "BAV99"))
    )
    (comp (ref "D1017")
      (value "200mA/70V")
      (footprint "eagle-import:SOT23-3")
      (libsource (lib "eagle-import") (part "BAV99"))
    )
    (comp (ref "D1018")
      (value "200mA/70V")
      (footprint "eagle-import:SOT23-3")
      (libsource (lib "eagle-import") (part "BAV99"))
    )
    (comp (ref "D1019")
      (value "200mA/70V")
      (footprint "eagle-import:SOT23-3")
      (libsource (lib "eagle-import") (part "BAV99"))
    )
    (comp (ref "D1020")
      (value "200mA/70V")
      (footprint "eagle-import:SOT23-3")
      (libsource (lib "eagle-import") (part "BAV99"))
    )
    (comp (ref "D1021")
      (value "200mA/70V")
      (footprint "eagle-import:SOT23-3")
      (libsource (lib "eagle-import") (part "BAV99"))
    )
    (comp (ref "D1022")
      (value "200mA/70V")
      (footprint "eagle-import:SOT23-3")
      (libsource (lib "eagle-import") (part "BAV99"))
    )
    (comp (ref "D1023")
      (value "200mA/70V")
      (footprint "eagle-import:SOT23-3")
      (libsource (lib "eagle-import") (part "BAV99"))
    )
    (comp (ref "D1024")
      (value "200mA/70V")
      (footprint "eagle-import:SOT23-3")
      (libsource (lib "eagle-import") (part "BAV99"))
    )
    (comp (ref "L529")
      (value "SD8")
      (footprint "eagle-import:SD8")
      (libsource (lib "eagle-import") (part "SD8"))
    )
    (comp (ref "L530")
      (value "SD8")
      (footprint "eagle-import:SD8")
      (libsource (lib "eagle-import") (part "SD8"))
    )
    (comp (ref "L531")
      (value "SD8")
      (footprint "eagle-import:SD8")
      (libsource (lib "eagle-import") (part "SD8"))
    )
    (comp (ref "L532")
      (value "SD8")
      (footprint "eagle-import:SD8")
      (libsource (lib "eagle-import") (part "SD8"))
    )
    (comp (ref "L533")
      (value "SD8")
      (footprint "eagle-import:SD8")
      (libsource (lib "eagle-import") (part "SD8"))
    )
    (comp (ref "L534")
      (value "SD8")
      (footprint "eagle-import:SD8")
      (libsource (lib "eagle-import") (part "SD8"))
    )
    (comp (ref "L535")
      (value "SD8")
      (footprint "eagle-import:SD8")
      (libsource (lib "eagle-import") (part "SD8"))
    )
    (comp (ref "L536")
      (value "SD8")
      (footprint "eagle-import:SD8")
      (libsource (lib "eagle-import") (part "SD8"))
    )
    (comp (ref "L537")
      (value "SD8")
      (footprint "eagle-import:SD8")
      (libsource (lib "eagle-import") (part "SD8"))
    )
    (comp (ref "L538")
      (value "SD8")
      (footprint "eagle-import:SD8")
      (libsource (lib "eagle-import") (part "SD8"))
    )
    (comp (ref "L539")
      (value "SD8")
      (footprint "eagle-import:SD8")
      (libsource (lib "eagle-import") (part "SD8"))
    )
    (comp (ref "L540")
      (value "SD8")
      (footprint "eagle-import:SD8")
      (libsource (lib "eagle-import") (part "SD8"))
    )
    (comp (ref "L541")
      (value "SD8")
      (footprint "eagle-import:SD8")
      (libsource (lib "eagle-import") (part "SD8"))
    )
    (comp (ref "L542")
      (value "SD8")
      (footprint "eagle-import:SD8")
      (libsource (lib "eagle-import") (part "SD8"))
    )
    (comp (ref "L543")
      (value "SD8")
      (footprint "eagle-import:SD8")
      (libsource (lib "eagle-import") (part "SD8"))
    )
    (comp (ref "L544")
      (value "SD8")
      (footprint "eagle-import:SD8")
      (libsource (lib "eagle-import") (part "SD8"))
    )
    (comp (ref "L561")
      (value "SD8")
      (footprint "eagle-import:SD8")
      (libsource (lib "eagle-import") (part "SD8"))
    )
    (comp (ref "L562")
      (value "SD8")
      (footprint "eagle-import:SD8")
      (libsource (lib "eagle-import") (part "SD8"))
    )
    (comp (ref "L563")
      (value "SD8")
      (footprint "eagle-import:SD8")
      (libsource (lib "eagle-import") (part "SD8"))
    )
    (comp (ref "L564")
      (value "SD8")
      (footprint "eagle-import:SD8")
      (libsource (lib "eagle-import") (part "SD8"))
    )
    (comp (ref "L565")
      (value "SD8")
      (footprint "eagle-import:SD8")
      (libsource (lib "eagle-import") (part "SD8"))
    )
    (comp (ref "L566")
      (value "SD8")
      (footprint "eagle-import:SD8")
      (libsource (lib "eagle-import") (part "SD8"))
    )
    (comp (ref "L567")
      (value "SD8")
      (footprint "eagle-import:SD8")
      (libsource (lib "eagle-import") (part "SD8"))
    )
    (comp (ref "L568")
      (value "SD8")
      (footprint "eagle-import:SD8")
      (libsource (lib "eagle-import") (part "SD8"))
    )
    (comp (ref "L569")
      (value "SD8")
      (footprint "eagle-import:SD8")
      (libsource (lib "eagle-import") (part "SD8"))
    )
    (comp (ref "L570")
      (value "SD8")
      (footprint "eagle-import:SD8")
      (libsource (lib "eagle-import") (part "SD8"))
    )
    (comp (ref "L571")
      (value "SD8")
      (footprint "eagle-import:SD8")
      (libsource (lib "eagle-import") (part "SD8"))
    )
    (comp (ref "L572")
      (value "SD8")
      (footprint "eagle-import:SD8")
      (libsource (lib "eagle-import") (part "SD8"))
    )
    (comp (ref "L573")
      (value "SD8")
      (footprint "eagle-import:SD8")
      (libsource (lib "eagle-import") (part "SD8"))
    )
    (comp (ref "L574")
      (value "SD8")
      (footprint "eagle-import:SD8")
      (libsource (lib "eagle-import") (part "SD8"))
    )
    (comp (ref "L575")
      (value "SD8")
      (footprint "eagle-import:SD8")
      (libsource (lib "eagle-import") (part "SD8"))
    )
    (comp (ref "L576")
      (value "SD8")
      (footprint "eagle-import:SD8")
      (libsource (lib "eagle-import") (part "SD8"))
    )
    (comp (ref "L593")
      (value "SD8")
      (footprint "eagle-import:SD8")
      (libsource (lib "eagle-import") (part "SD8"))
    )
    (comp (ref "L594")
      (value "SD8")
      (footprint "eagle-import:SD8")
      (libsource (lib "eagle-import") (part "SD8"))
    )
    (comp (ref "L595")
      (value "SD8")
      (footprint "eagle-import:SD8")
      (libsource (lib "eagle-import") (part "SD8"))
    )
    (comp (ref "L596")
      (value "SD8")
      (footprint "eagle-import:SD8")
      (libsource (lib "eagle-import") (part "SD8"))
    )
    (comp (ref "L597")
      (value "SD8")
      (footprint "eagle-import:SD8")
      (libsource (lib "eagle-import") (part "SD8"))
    )
    (comp (ref "L598")
      (value "SD8")
      (footprint "eagle-import:SD8")
      (libsource (lib "eagle-import") (part "SD8"))
    )
    (comp (ref "L599")
      (value "SD8")
      (footprint "eagle-import:SD8")
      (libsource (lib "eagle-import") (part "SD8"))
    )
    (comp (ref "L600")
      (value "SD8")
      (footprint "eagle-import:SD8")
      (libsource (lib "eagle-import") (part "SD8"))
    )
    (comp (ref "L601")
      (value "SD8")
      (footprint "eagle-import:SD8")
      (libsource (lib "eagle-import") (part "SD8"))
    )
    (comp (ref "L602")
      (value "SD8")
      (footprint "eagle-import:SD8")
      (libsource (lib "eagle-import") (part "SD8"))
    )
    (comp (ref "L603")
      (value "SD8")
      (footprint "eagle-import:SD8")
      (libsource (lib "eagle-import") (part "SD8"))
    )
    (comp (ref "L604")
      (value "SD8")
      (footprint "eagle-import:SD8")
      (libsource (lib "eagle-import") (part "SD8"))
    )
    (comp (ref "L605")
      (value "SD8")
      (footprint "eagle-import:SD8")
      (libsource (lib "eagle-import") (part "SD8"))
    )
    (comp (ref "L606")
      (value "SD8")
      (footprint "eagle-import:SD8")
      (libsource (lib "eagle-import") (part "SD8"))
    )
    (comp (ref "L607")
      (value "SD8")
      (footprint "eagle-import:SD8")
      (libsource (lib "eagle-import") (part "SD8"))
    )
    (comp (ref "L608")
      (value "SD8")
      (footprint "eagle-import:SD8")
      (libsource (lib "eagle-import") (part "SD8"))
    )
    (comp (ref "L625")
      (value "SD8")
      (footprint "eagle-import:SD8")
      (libsource (lib "eagle-import") (part "SD8"))
    )
    (comp (ref "L626")
      (value "SD8")
      (footprint "eagle-import:SD8")
      (libsource (lib "eagle-import") (part "SD8"))
    )
    (comp (ref "L627")
      (value "SD8")
      (footprint "eagle-import:SD8")
      (libsource (lib "eagle-import") (part "SD8"))
    )
    (comp (ref "L628")
      (value "SD8")
      (footprint "eagle-import:SD8")
      (libsource (lib "eagle-import") (part "SD8"))
    )
    (comp (ref "L629")
      (value "SD8")
      (footprint "eagle-import:SD8")
      (libsource (lib "eagle-import") (part "SD8"))
    )
    (comp (ref "L630")
      (value "SD8")
      (footprint "eagle-import:SD8")
      (libsource (lib "eagle-import") (part "SD8"))
    )
    (comp (ref "L631")
      (value "SD8")
      (footprint "eagle-import:SD8")
      (libsource (lib "eagle-import") (part "SD8"))
    )
    (comp (ref "L632")
      (value "SD8")
      (footprint "eagle-import:SD8")
      (libsource (lib "eagle-import") (part "SD8"))
    )
    (comp (ref "L633")
      (value "SD8")
      (footprint "eagle-import:SD8")
      (libsource (lib "eagle-import") (part "SD8"))
    )
    (comp (ref "L634")
      (value "SD8")
      (footprint "eagle-import:SD8")
      (libsource (lib "eagle-import") (part "SD8"))
    )
    (comp (ref "L635")
      (value "SD8")
      (footprint "eagle-import:SD8")
      (libsource (lib "eagle-import") (part "SD8"))
    )
    (comp (ref "L636")
      (value "SD8")
      (footprint "eagle-import:SD8")
      (libsource (lib "eagle-import") (part "SD8"))
    )
    (comp (ref "L637")
      (value "SD8")
      (footprint "eagle-import:SD8")
      (libsource (lib "eagle-import") (part "SD8"))
    )
    (comp (ref "L638")
      (value "SD8")
      (footprint "eagle-import:SD8")
      (libsource (lib "eagle-import") (part "SD8"))
    )
    (comp (ref "L639")
      (value "SD8")
      (footprint "eagle-import:SD8")
      (libsource (lib "eagle-import") (part "SD8"))
    )
    (comp (ref "L640")
      (value "SD8")
      (footprint "eagle-import:SD8")
      (libsource (lib "eagle-import") (part "SD8"))
    )
    (comp (ref "L657")
      (value "SD8")
      (footprint "eagle-import:SD8")
      (libsource (lib "eagle-import") (part "SD8"))
    )
    (comp (ref "L658")
      (value "SD8")
      (footprint "eagle-import:SD8")
      (libsource (lib "eagle-import") (part "SD8"))
    )
    (comp (ref "L659")
      (value "SD8")
      (footprint "eagle-import:SD8")
      (libsource (lib "eagle-import") (part "SD8"))
    )
    (comp (ref "L660")
      (value "SD8")
      (footprint "eagle-import:SD8")
      (libsource (lib "eagle-import") (part "SD8"))
    )
    (comp (ref "L661")
      (value "SD8")
      (footprint "eagle-import:SD8")
      (libsource (lib "eagle-import") (part "SD8"))
    )
    (comp (ref "L662")
      (value "SD8")
      (footprint "eagle-import:SD8")
      (libsource (lib "eagle-import") (part "SD8"))
    )
    (comp (ref "L663")
      (value "SD8")
      (footprint "eagle-import:SD8")
      (libsource (lib "eagle-import") (part "SD8"))
    )
    (comp (ref "L664")
      (value "SD8")
      (footprint "eagle-import:SD8")
      (libsource (lib "eagle-import") (part "SD8"))
    )
    (comp (ref "L665")
      (value "SD8")
      (footprint "eagle-import:SD8")
      (libsource (lib "eagle-import") (part "SD8"))
    )
    (comp (ref "L666")
      (value "SD8")
      (footprint "eagle-import:SD8")
      (libsource (lib "eagle-import") (part "SD8"))
    )
    (comp (ref "L667")
      (value "SD8")
      (footprint "eagle-import:SD8")
      (libsource (lib "eagle-import") (part "SD8"))
    )
    (comp (ref "L668")
      (value "SD8")
      (footprint "eagle-import:SD8")
      (libsource (lib "eagle-import") (part "SD8"))
    )
    (comp (ref "L669")
      (value "SD8")
      (footprint "eagle-import:SD8")
      (libsource (lib "eagle-import") (part "SD8"))
    )
    (comp (ref "L670")
      (value "SD8")
      (footprint "eagle-import:SD8")
      (libsource (lib "eagle-import") (part "SD8"))
    )
    (comp (ref "L671")
      (value "SD8")
      (footprint "eagle-import:SD8")
      (libsource (lib "eagle-import") (part "SD8"))
    )
    (comp (ref "L672")
      (value "SD8")
      (footprint "eagle-import:SD8")
      (libsource (lib "eagle-import") (part "SD8"))
    )
    (comp (ref "L689")
      (value "SD8")
      (footprint "eagle-import:SD8")
      (libsource (lib "eagle-import") (part "SD8"))
    )
    (comp (ref "L690")
      (value "SD8")
      (footprint "eagle-import:SD8")
      (libsource (lib "eagle-import") (part "SD8"))
    )
    (comp (ref "L691")
      (value "SD8")
      (footprint "eagle-import:SD8")
      (libsource (lib "eagle-import") (part "SD8"))
    )
    (comp (ref "L692")
      (value "SD8")
      (footprint "eagle-import:SD8")
      (libsource (lib "eagle-import") (part "SD8"))
    )
    (comp (ref "L693")
      (value "SD8")
      (footprint "eagle-import:SD8")
      (libsource (lib "eagle-import") (part "SD8"))
    )
    (comp (ref "L694")
      (value "SD8")
      (footprint "eagle-import:SD8")
      (libsource (lib "eagle-import") (part "SD8"))
    )
    (comp (ref "L695")
      (value "SD8")
      (footprint "eagle-import:SD8")
      (libsource (lib "eagle-import") (part "SD8"))
    )
    (comp (ref "L696")
      (value "SD8")
      (footprint "eagle-import:SD8")
      (libsource (lib "eagle-import") (part "SD8"))
    )
    (comp (ref "L697")
      (value "SD8")
      (footprint "eagle-import:SD8")
      (libsource (lib "eagle-import") (part "SD8"))
    )
    (comp (ref "L698")
      (value "SD8")
      (footprint "eagle-import:SD8")
      (libsource (lib "eagle-import") (part "SD8"))
    )
    (comp (ref "L699")
      (value "SD8")
      (footprint "eagle-import:SD8")
      (libsource (lib "eagle-import") (part "SD8"))
    )
    (comp (ref "L700")
      (value "SD8")
      (footprint "eagle-import:SD8")
      (libsource (lib "eagle-import") (part "SD8"))
    )
    (comp (ref "L701")
      (value "SD8")
      (footprint "eagle-import:SD8")
      (libsource (lib "eagle-import") (part "SD8"))
    )
    (comp (ref "L702")
      (value "SD8")
      (footprint "eagle-import:SD8")
      (libsource (lib "eagle-import") (part "SD8"))
    )
    (comp (ref "L703")
      (value "SD8")
      (footprint "eagle-import:SD8")
      (libsource (lib "eagle-import") (part "SD8"))
    )
    (comp (ref "L704")
      (value "SD8")
      (footprint "eagle-import:SD8")
      (libsource (lib "eagle-import") (part "SD8"))
    )
    (comp (ref "L721")
      (value "SD8")
      (footprint "eagle-import:SD8")
      (libsource (lib "eagle-import") (part "SD8"))
    )
    (comp (ref "L722")
      (value "SD8")
      (footprint "eagle-import:SD8")
      (libsource (lib "eagle-import") (part "SD8"))
    )
    (comp (ref "L723")
      (value "SD8")
      (footprint "eagle-import:SD8")
      (libsource (lib "eagle-import") (part "SD8"))
    )
    (comp (ref "L724")
      (value "SD8")
      (footprint "eagle-import:SD8")
      (libsource (lib "eagle-import") (part "SD8"))
    )
    (comp (ref "L725")
      (value "SD8")
      (footprint "eagle-import:SD8")
      (libsource (lib "eagle-import") (part "SD8"))
    )
    (comp (ref "L726")
      (value "SD8")
      (footprint "eagle-import:SD8")
      (libsource (lib "eagle-import") (part "SD8"))
    )
    (comp (ref "L727")
      (value "SD8")
      (footprint "eagle-import:SD8")
      (libsource (lib "eagle-import") (part "SD8"))
    )
    (comp (ref "L728")
      (value "SD8")
      (footprint "eagle-import:SD8")
      (libsource (lib "eagle-import") (part "SD8"))
    )
    (comp (ref "L729")
      (value "SD8")
      (footprint "eagle-import:SD8")
      (libsource (lib "eagle-import") (part "SD8"))
    )
    (comp (ref "L730")
      (value "SD8")
      (footprint "eagle-import:SD8")
      (libsource (lib "eagle-import") (part "SD8"))
    )
    (comp (ref "L731")
      (value "SD8")
      (footprint "eagle-import:SD8")
      (libsource (lib "eagle-import") (part "SD8"))
    )
    (comp (ref "L732")
      (value "SD8")
      (footprint "eagle-import:SD8")
      (libsource (lib "eagle-import") (part "SD8"))
    )
    (comp (ref "L733")
      (value "SD8")
      (footprint "eagle-import:SD8")
      (libsource (lib "eagle-import") (part "SD8"))
    )
    (comp (ref "L734")
      (value "SD8")
      (footprint "eagle-import:SD8")
      (libsource (lib "eagle-import") (part "SD8"))
    )
    (comp (ref "L735")
      (value "SD8")
      (footprint "eagle-import:SD8")
      (libsource (lib "eagle-import") (part "SD8"))
    )
    (comp (ref "L736")
      (value "SD8")
      (footprint "eagle-import:SD8")
      (libsource (lib "eagle-import") (part "SD8"))
    )
    (comp (ref "L753")
      (value "SD8")
      (footprint "eagle-import:SD8")
      (libsource (lib "eagle-import") (part "SD8"))
    )
    (comp (ref "L754")
      (value "SD8")
      (footprint "eagle-import:SD8")
      (libsource (lib "eagle-import") (part "SD8"))
    )
    (comp (ref "L755")
      (value "SD8")
      (footprint "eagle-import:SD8")
      (libsource (lib "eagle-import") (part "SD8"))
    )
    (comp (ref "L756")
      (value "SD8")
      (footprint "eagle-import:SD8")
      (libsource (lib "eagle-import") (part "SD8"))
    )
    (comp (ref "L757")
      (value "SD8")
      (footprint "eagle-import:SD8")
      (libsource (lib "eagle-import") (part "SD8"))
    )
    (comp (ref "L758")
      (value "SD8")
      (footprint "eagle-import:SD8")
      (libsource (lib "eagle-import") (part "SD8"))
    )
    (comp (ref "L759")
      (value "SD8")
      (footprint "eagle-import:SD8")
      (libsource (lib "eagle-import") (part "SD8"))
    )
    (comp (ref "L760")
      (value "SD8")
      (footprint "eagle-import:SD8")
      (libsource (lib "eagle-import") (part "SD8"))
    )
    (comp (ref "L761")
      (value "SD8")
      (footprint "eagle-import:SD8")
      (libsource (lib "eagle-import") (part "SD8"))
    )
    (comp (ref "L762")
      (value "SD8")
      (footprint "eagle-import:SD8")
      (libsource (lib "eagle-import") (part "SD8"))
    )
    (comp (ref "L763")
      (value "SD8")
      (footprint "eagle-import:SD8")
      (libsource (lib "eagle-import") (part "SD8"))
    )
    (comp (ref "L764")
      (value "SD8")
      (footprint "eagle-import:SD8")
      (libsource (lib "eagle-import") (part "SD8"))
    )
    (comp (ref "L765")
      (value "SD8")
      (footprint "eagle-import:SD8")
      (libsource (lib "eagle-import") (part "SD8"))
    )
    (comp (ref "L766")
      (value "SD8")
      (footprint "eagle-import:SD8")
      (libsource (lib "eagle-import") (part "SD8"))
    )
    (comp (ref "L767")
      (value "SD8")
      (footprint "eagle-import:SD8")
      (libsource (lib "eagle-import") (part "SD8"))
    )
    (comp (ref "L768")
      (value "SD8")
      (footprint "eagle-import:SD8")
      (libsource (lib "eagle-import") (part "SD8"))
    )
    (comp (ref "L785")
      (value "SD8")
      (footprint "eagle-import:SD8")
      (libsource (lib "eagle-import") (part "SD8"))
    )
    (comp (ref "L786")
      (value "SD8")
      (footprint "eagle-import:SD8")
      (libsource (lib "eagle-import") (part "SD8"))
    )
    (comp (ref "L787")
      (value "SD8")
      (footprint "eagle-import:SD8")
      (libsource (lib "eagle-import") (part "SD8"))
    )
    (comp (ref "L788")
      (value "SD8")
      (footprint "eagle-import:SD8")
      (libsource (lib "eagle-import") (part "SD8"))
    )
    (comp (ref "L789")
      (value "SD8")
      (footprint "eagle-import:SD8")
      (libsource (lib "eagle-import") (part "SD8"))
    )
    (comp (ref "L790")
      (value "SD8")
      (footprint "eagle-import:SD8")
      (libsource (lib "eagle-import") (part "SD8"))
    )
    (comp (ref "L791")
      (value "SD8")
      (footprint "eagle-import:SD8")
      (libsource (lib "eagle-import") (part "SD8"))
    )
    (comp (ref "L792")
      (value "SD8")
      (footprint "eagle-import:SD8")
      (libsource (lib "eagle-import") (part "SD8"))
    )
    (comp (ref "L793")
      (value "SD8")
      (footprint "eagle-import:SD8")
      (libsource (lib "eagle-import") (part "SD8"))
    )
    (comp (ref "L794")
      (value "SD8")
      (footprint "eagle-import:SD8")
      (libsource (lib "eagle-import") (part "SD8"))
    )
    (comp (ref "L795")
      (value "SD8")
      (footprint "eagle-import:SD8")
      (libsource (lib "eagle-import") (part "SD8"))
    )
    (comp (ref "L796")
      (value "SD8")
      (footprint "eagle-import:SD8")
      (libsource (lib "eagle-import") (part "SD8"))
    )
    (comp (ref "L797")
      (value "SD8")
      (footprint "eagle-import:SD8")
      (libsource (lib "eagle-import") (part "SD8"))
    )
    (comp (ref "L798")
      (value "SD8")
      (footprint "eagle-import:SD8")
      (libsource (lib "eagle-import") (part "SD8"))
    )
    (comp (ref "L799")
      (value "SD8")
      (footprint "eagle-import:SD8")
      (libsource (lib "eagle-import") (part "SD8"))
    )
    (comp (ref "L800")
      (value "SD8")
      (footprint "eagle-import:SD8")
      (libsource (lib "eagle-import") (part "SD8"))
    )
    (comp (ref "L817")
      (value "SD8")
      (footprint "eagle-import:SD8")
      (libsource (lib "eagle-import") (part "SD8"))
    )
    (comp (ref "L818")
      (value "SD8")
      (footprint "eagle-import:SD8")
      (libsource (lib "eagle-import") (part "SD8"))
    )
    (comp (ref "L819")
      (value "SD8")
      (footprint "eagle-import:SD8")
      (libsource (lib "eagle-import") (part "SD8"))
    )
    (comp (ref "L820")
      (value "SD8")
      (footprint "eagle-import:SD8")
      (libsource (lib "eagle-import") (part "SD8"))
    )
    (comp (ref "L821")
      (value "SD8")
      (footprint "eagle-import:SD8")
      (libsource (lib "eagle-import") (part "SD8"))
    )
    (comp (ref "L822")
      (value "SD8")
      (footprint "eagle-import:SD8")
      (libsource (lib "eagle-import") (part "SD8"))
    )
    (comp (ref "L823")
      (value "SD8")
      (footprint "eagle-import:SD8")
      (libsource (lib "eagle-import") (part "SD8"))
    )
    (comp (ref "L824")
      (value "SD8")
      (footprint "eagle-import:SD8")
      (libsource (lib "eagle-import") (part "SD8"))
    )
    (comp (ref "L825")
      (value "SD8")
      (footprint "eagle-import:SD8")
      (libsource (lib "eagle-import") (part "SD8"))
    )
    (comp (ref "L826")
      (value "SD8")
      (footprint "eagle-import:SD8")
      (libsource (lib "eagle-import") (part "SD8"))
    )
    (comp (ref "L827")
      (value "SD8")
      (footprint "eagle-import:SD8")
      (libsource (lib "eagle-import") (part "SD8"))
    )
    (comp (ref "L828")
      (value "SD8")
      (footprint "eagle-import:SD8")
      (libsource (lib "eagle-import") (part "SD8"))
    )
    (comp (ref "L829")
      (value "SD8")
      (footprint "eagle-import:SD8")
      (libsource (lib "eagle-import") (part "SD8"))
    )
    (comp (ref "L830")
      (value "SD8")
      (footprint "eagle-import:SD8")
      (libsource (lib "eagle-import") (part "SD8"))
    )
    (comp (ref "L831")
      (value "SD8")
      (footprint "eagle-import:SD8")
      (libsource (lib "eagle-import") (part "SD8"))
    )
    (comp (ref "L832")
      (value "SD8")
      (footprint "eagle-import:SD8")
      (libsource (lib "eagle-import") (part "SD8"))
    )
    (comp (ref "L849")
      (value "SD8")
      (footprint "eagle-import:SD8")
      (libsource (lib "eagle-import") (part "SD8"))
    )
    (comp (ref "L850")
      (value "SD8")
      (footprint "eagle-import:SD8")
      (libsource (lib "eagle-import") (part "SD8"))
    )
    (comp (ref "L851")
      (value "SD8")
      (footprint "eagle-import:SD8")
      (libsource (lib "eagle-import") (part "SD8"))
    )
    (comp (ref "L852")
      (value "SD8")
      (footprint "eagle-import:SD8")
      (libsource (lib "eagle-import") (part "SD8"))
    )
    (comp (ref "L853")
      (value "SD8")
      (footprint "eagle-import:SD8")
      (libsource (lib "eagle-import") (part "SD8"))
    )
    (comp (ref "L854")
      (value "SD8")
      (footprint "eagle-import:SD8")
      (libsource (lib "eagle-import") (part "SD8"))
    )
    (comp (ref "L855")
      (value "SD8")
      (footprint "eagle-import:SD8")
      (libsource (lib "eagle-import") (part "SD8"))
    )
    (comp (ref "L856")
      (value "SD8")
      (footprint "eagle-import:SD8")
      (libsource (lib "eagle-import") (part "SD8"))
    )
    (comp (ref "L857")
      (value "SD8")
      (footprint "eagle-import:SD8")
      (libsource (lib "eagle-import") (part "SD8"))
    )
    (comp (ref "L858")
      (value "SD8")
      (footprint "eagle-import:SD8")
      (libsource (lib "eagle-import") (part "SD8"))
    )
    (comp (ref "L859")
      (value "SD8")
      (footprint "eagle-import:SD8")
      (libsource (lib "eagle-import") (part "SD8"))
    )
    (comp (ref "L860")
      (value "SD8")
      (footprint "eagle-import:SD8")
      (libsource (lib "eagle-import") (part "SD8"))
    )
    (comp (ref "L861")
      (value "SD8")
      (footprint "eagle-import:SD8")
      (libsource (lib "eagle-import") (part "SD8"))
    )
    (comp (ref "L862")
      (value "SD8")
      (footprint "eagle-import:SD8")
      (libsource (lib "eagle-import") (part "SD8"))
    )
    (comp (ref "L863")
      (value "SD8")
      (footprint "eagle-import:SD8")
      (libsource (lib "eagle-import") (part "SD8"))
    )
    (comp (ref "L864")
      (value "SD8")
      (footprint "eagle-import:SD8")
      (libsource (lib "eagle-import") (part "SD8"))
    )
    (comp (ref "L881")
      (value "SD8")
      (footprint "eagle-import:SD8")
      (libsource (lib "eagle-import") (part "SD8"))
    )
    (comp (ref "L882")
      (value "SD8")
      (footprint "eagle-import:SD8")
      (libsource (lib "eagle-import") (part "SD8"))
    )
    (comp (ref "L883")
      (value "SD8")
      (footprint "eagle-import:SD8")
      (libsource (lib "eagle-import") (part "SD8"))
    )
    (comp (ref "L884")
      (value "SD8")
      (footprint "eagle-import:SD8")
      (libsource (lib "eagle-import") (part "SD8"))
    )
    (comp (ref "L885")
      (value "SD8")
      (footprint "eagle-import:SD8")
      (libsource (lib "eagle-import") (part "SD8"))
    )
    (comp (ref "L886")
      (value "SD8")
      (footprint "eagle-import:SD8")
      (libsource (lib "eagle-import") (part "SD8"))
    )
    (comp (ref "L887")
      (value "SD8")
      (footprint "eagle-import:SD8")
      (libsource (lib "eagle-import") (part "SD8"))
    )
    (comp (ref "L888")
      (value "SD8")
      (footprint "eagle-import:SD8")
      (libsource (lib "eagle-import") (part "SD8"))
    )
    (comp (ref "L889")
      (value "SD8")
      (footprint "eagle-import:SD8")
      (libsource (lib "eagle-import") (part "SD8"))
    )
    (comp (ref "L890")
      (value "SD8")
      (footprint "eagle-import:SD8")
      (libsource (lib "eagle-import") (part "SD8"))
    )
    (comp (ref "L891")
      (value "SD8")
      (footprint "eagle-import:SD8")
      (libsource (lib "eagle-import") (part "SD8"))
    )
    (comp (ref "L892")
      (value "SD8")
      (footprint "eagle-import:SD8")
      (libsource (lib "eagle-import") (part "SD8"))
    )
    (comp (ref "L893")
      (value "SD8")
      (footprint "eagle-import:SD8")
      (libsource (lib "eagle-import") (part "SD8"))
    )
    (comp (ref "L894")
      (value "SD8")
      (footprint "eagle-import:SD8")
      (libsource (lib "eagle-import") (part "SD8"))
    )
    (comp (ref "L895")
      (value "SD8")
      (footprint "eagle-import:SD8")
      (libsource (lib "eagle-import") (part "SD8"))
    )
    (comp (ref "L896")
      (value "SD8")
      (footprint "eagle-import:SD8")
      (libsource (lib "eagle-import") (part "SD8"))
    )
    (comp (ref "L913")
      (value "SD8")
      (footprint "eagle-import:SD8")
      (libsource (lib "eagle-import") (part "SD8"))
    )
    (comp (ref "L914")
      (value "SD8")
      (footprint "eagle-import:SD8")
      (libsource (lib "eagle-import") (part "SD8"))
    )
    (comp (ref "L915")
      (value "SD8")
      (footprint "eagle-import:SD8")
      (libsource (lib "eagle-import") (part "SD8"))
    )
    (comp (ref "L916")
      (value "SD8")
      (footprint "eagle-import:SD8")
      (libsource (lib "eagle-import") (part "SD8"))
    )
    (comp (ref "L917")
      (value "SD8")
      (footprint "eagle-import:SD8")
      (libsource (lib "eagle-import") (part "SD8"))
    )
    (comp (ref "L918")
      (value "SD8")
      (footprint "eagle-import:SD8")
      (libsource (lib "eagle-import") (part "SD8"))
    )
    (comp (ref "L919")
      (value "SD8")
      (footprint "eagle-import:SD8")
      (libsource (lib "eagle-import") (part "SD8"))
    )
    (comp (ref "L920")
      (value "SD8")
      (footprint "eagle-import:SD8")
      (libsource (lib "eagle-import") (part "SD8"))
    )
    (comp (ref "L921")
      (value "SD8")
      (footprint "eagle-import:SD8")
      (libsource (lib "eagle-import") (part "SD8"))
    )
    (comp (ref "L922")
      (value "SD8")
      (footprint "eagle-import:SD8")
      (libsource (lib "eagle-import") (part "SD8"))
    )
    (comp (ref "L923")
      (value "SD8")
      (footprint "eagle-import:SD8")
      (libsource (lib "eagle-import") (part "SD8"))
    )
    (comp (ref "L924")
      (value "SD8")
      (footprint "eagle-import:SD8")
      (libsource (lib "eagle-import") (part "SD8"))
    )
    (comp (ref "L925")
      (value "SD8")
      (footprint "eagle-import:SD8")
      (libsource (lib "eagle-import") (part "SD8"))
    )
    (comp (ref "L926")
      (value "SD8")
      (footprint "eagle-import:SD8")
      (libsource (lib "eagle-import") (part "SD8"))
    )
    (comp (ref "L927")
      (value "SD8")
      (footprint "eagle-import:SD8")
      (libsource (lib "eagle-import") (part "SD8"))
    )
    (comp (ref "L928")
      (value "SD8")
      (footprint "eagle-import:SD8")
      (libsource (lib "eagle-import") (part "SD8"))
    )
    (comp (ref "L945")
      (value "SD8")
      (footprint "eagle-import:SD8")
      (libsource (lib "eagle-import") (part "SD8"))
    )
    (comp (ref "L946")
      (value "SD8")
      (footprint "eagle-import:SD8")
      (libsource (lib "eagle-import") (part "SD8"))
    )
    (comp (ref "L947")
      (value "SD8")
      (footprint "eagle-import:SD8")
      (libsource (lib "eagle-import") (part "SD8"))
    )
    (comp (ref "L948")
      (value "SD8")
      (footprint "eagle-import:SD8")
      (libsource (lib "eagle-import") (part "SD8"))
    )
    (comp (ref "L949")
      (value "SD8")
      (footprint "eagle-import:SD8")
      (libsource (lib "eagle-import") (part "SD8"))
    )
    (comp (ref "L950")
      (value "SD8")
      (footprint "eagle-import:SD8")
      (libsource (lib "eagle-import") (part "SD8"))
    )
    (comp (ref "L951")
      (value "SD8")
      (footprint "eagle-import:SD8")
      (libsource (lib "eagle-import") (part "SD8"))
    )
    (comp (ref "L952")
      (value "SD8")
      (footprint "eagle-import:SD8")
      (libsource (lib "eagle-import") (part "SD8"))
    )
    (comp (ref "L953")
      (value "SD8")
      (footprint "eagle-import:SD8")
      (libsource (lib "eagle-import") (part "SD8"))
    )
    (comp (ref "L954")
      (value "SD8")
      (footprint "eagle-import:SD8")
      (libsource (lib "eagle-import") (part "SD8"))
    )
    (comp (ref "L955")
      (value "SD8")
      (footprint "eagle-import:SD8")
      (libsource (lib "eagle-import") (part "SD8"))
    )
    (comp (ref "L956")
      (value "SD8")
      (footprint "eagle-import:SD8")
      (libsource (lib "eagle-import") (part "SD8"))
    )
    (comp (ref "L957")
      (value "SD8")
      (footprint "eagle-import:SD8")
      (libsource (lib "eagle-import") (part "SD8"))
    )
    (comp (ref "L958")
      (value "SD8")
      (footprint "eagle-import:SD8")
      (libsource (lib "eagle-import") (part "SD8"))
    )
    (comp (ref "L959")
      (value "SD8")
      (footprint "eagle-import:SD8")
      (libsource (lib "eagle-import") (part "SD8"))
    )
    (comp (ref "L960")
      (value "SD8")
      (footprint "eagle-import:SD8")
      (libsource (lib "eagle-import") (part "SD8"))
    )
    (comp (ref "L977")
      (value "SD8")
      (footprint "eagle-import:SD8")
      (libsource (lib "eagle-import") (part "SD8"))
    )
    (comp (ref "L978")
      (value "SD8")
      (footprint "eagle-import:SD8")
      (libsource (lib "eagle-import") (part "SD8"))
    )
    (comp (ref "L979")
      (value "SD8")
      (footprint "eagle-import:SD8")
      (libsource (lib "eagle-import") (part "SD8"))
    )
    (comp (ref "L980")
      (value "SD8")
      (footprint "eagle-import:SD8")
      (libsource (lib "eagle-import") (part "SD8"))
    )
    (comp (ref "L981")
      (value "SD8")
      (footprint "eagle-import:SD8")
      (libsource (lib "eagle-import") (part "SD8"))
    )
    (comp (ref "L982")
      (value "SD8")
      (footprint "eagle-import:SD8")
      (libsource (lib "eagle-import") (part "SD8"))
    )
    (comp (ref "L983")
      (value "SD8")
      (footprint "eagle-import:SD8")
      (libsource (lib "eagle-import") (part "SD8"))
    )
    (comp (ref "L984")
      (value "SD8")
      (footprint "eagle-import:SD8")
      (libsource (lib "eagle-import") (part "SD8"))
    )
    (comp (ref "L985")
      (value "SD8")
      (footprint "eagle-import:SD8")
      (libsource (lib "eagle-import") (part "SD8"))
    )
    (comp (ref "L986")
      (value "SD8")
      (footprint "eagle-import:SD8")
      (libsource (lib "eagle-import") (part "SD8"))
    )
    (comp (ref "L987")
      (value "SD8")
      (footprint "eagle-import:SD8")
      (libsource (lib "eagle-import") (part "SD8"))
    )
    (comp (ref "L988")
      (value "SD8")
      (footprint "eagle-import:SD8")
      (libsource (lib "eagle-import") (part "SD8"))
    )
    (comp (ref "L989")
      (value "SD8")
      (footprint "eagle-import:SD8")
      (libsource (lib "eagle-import") (part "SD8"))
    )
    (comp (ref "L990")
      (value "SD8")
      (footprint "eagle-import:SD8")
      (libsource (lib "eagle-import") (part "SD8"))
    )
    (comp (ref "L991")
      (value "SD8")
      (footprint "eagle-import:SD8")
      (libsource (lib "eagle-import") (part "SD8"))
    )
    (comp (ref "L992")
      (value "SD8")
      (footprint "eagle-import:SD8")
      (libsource (lib "eagle-import") (part "SD8"))
    )
    (comp (ref "L1009")
      (value "SD8")
      (footprint "eagle-import:SD8")
      (libsource (lib "eagle-import") (part "SD8"))
    )
    (comp (ref "L1010")
      (value "SD8")
      (footprint "eagle-import:SD8")
      (libsource (lib "eagle-import") (part "SD8"))
    )
    (comp (ref "L1011")
      (value "SD8")
      (footprint "eagle-import:SD8")
      (libsource (lib "eagle-import") (part "SD8"))
    )
    (comp (ref "L1012")
      (value "SD8")
      (footprint "eagle-import:SD8")
      (libsource (lib "eagle-import") (part "SD8"))
    )
    (comp (ref "L1013")
      (value "SD8")
      (footprint "eagle-import:SD8")
      (libsource (lib "eagle-import") (part "SD8"))
    )
    (comp (ref "L1014")
      (value "SD8")
      (footprint "eagle-import:SD8")
      (libsource (lib "eagle-import") (part "SD8"))
    )
    (comp (ref "L1015")
      (value "SD8")
      (footprint "eagle-import:SD8")
      (libsource (lib "eagle-import") (part "SD8"))
    )
    (comp (ref "L1016")
      (value "SD8")
      (footprint "eagle-import:SD8")
      (libsource (lib "eagle-import") (part "SD8"))
    )
    (comp (ref "L1017")
      (value "SD8")
      (footprint "eagle-import:SD8")
      (libsource (lib "eagle-import") (part "SD8"))
    )
    (comp (ref "L1018")
      (value "SD8")
      (footprint "eagle-import:SD8")
      (libsource (lib "eagle-import") (part "SD8"))
    )
    (comp (ref "L1019")
      (value "SD8")
      (footprint "eagle-import:SD8")
      (libsource (lib "eagle-import") (part "SD8"))
    )
    (comp (ref "L1020")
      (value "SD8")
      (footprint "eagle-import:SD8")
      (libsource (lib "eagle-import") (part "SD8"))
    )
    (comp (ref "L1021")
      (value "SD8")
      (footprint "eagle-import:SD8")
      (libsource (lib "eagle-import") (part "SD8"))
    )
    (comp (ref "L1022")
      (value "SD8")
      (footprint "eagle-import:SD8")
      (libsource (lib "eagle-import") (part "SD8"))
    )
    (comp (ref "L1023")
      (value "SD8")
      (footprint "eagle-import:SD8")
      (libsource (lib "eagle-import") (part "SD8"))
    )
    (comp (ref "L1024")
      (value "SD8")
      (footprint "eagle-import:SD8")
      (libsource (lib "eagle-import") (part "SD8"))
    )
    (comp (ref "D513")
      (value "200mA/70V")
      (footprint "eagle-import:SOT23-3")
      (libsource (lib "eagle-import") (part "BAV99"))
    )
    (comp (ref "D514")
      (value "200mA/70V")
      (footprint "eagle-import:SOT23-3")
      (libsource (lib "eagle-import") (part "BAV99"))
    )
    (comp (ref "D515")
      (value "200mA/70V")
      (footprint "eagle-import:SOT23-3")
      (libsource (lib "eagle-import") (part "BAV99"))
    )
    (comp (ref "D516")
      (value "200mA/70V")
      (footprint "eagle-import:SOT23-3")
      (libsource (lib "eagle-import") (part "BAV99"))
    )
    (comp (ref "D517")
      (value "200mA/70V")
      (footprint "eagle-import:SOT23-3")
      (libsource (lib "eagle-import") (part "BAV99"))
    )
    (comp (ref "D518")
      (value "200mA/70V")
      (footprint "eagle-import:SOT23-3")
      (libsource (lib "eagle-import") (part "BAV99"))
    )
    (comp (ref "D519")
      (value "200mA/70V")
      (footprint "eagle-import:SOT23-3")
      (libsource (lib "eagle-import") (part "BAV99"))
    )
    (comp (ref "D520")
      (value "200mA/70V")
      (footprint "eagle-import:SOT23-3")
      (libsource (lib "eagle-import") (part "BAV99"))
    )
    (comp (ref "D521")
      (value "200mA/70V")
      (footprint "eagle-import:SOT23-3")
      (libsource (lib "eagle-import") (part "BAV99"))
    )
    (comp (ref "D522")
      (value "200mA/70V")
      (footprint "eagle-import:SOT23-3")
      (libsource (lib "eagle-import") (part "BAV99"))
    )
    (comp (ref "D523")
      (value "200mA/70V")
      (footprint "eagle-import:SOT23-3")
      (libsource (lib "eagle-import") (part "BAV99"))
    )
    (comp (ref "D524")
      (value "200mA/70V")
      (footprint "eagle-import:SOT23-3")
      (libsource (lib "eagle-import") (part "BAV99"))
    )
    (comp (ref "D525")
      (value "200mA/70V")
      (footprint "eagle-import:SOT23-3")
      (libsource (lib "eagle-import") (part "BAV99"))
    )
    (comp (ref "D526")
      (value "200mA/70V")
      (footprint "eagle-import:SOT23-3")
      (libsource (lib "eagle-import") (part "BAV99"))
    )
    (comp (ref "D527")
      (value "200mA/70V")
      (footprint "eagle-import:SOT23-3")
      (libsource (lib "eagle-import") (part "BAV99"))
    )
    (comp (ref "D528")
      (value "200mA/70V")
      (footprint "eagle-import:SOT23-3")
      (libsource (lib "eagle-import") (part "BAV99"))
    )
    (comp (ref "D545")
      (value "200mA/70V")
      (footprint "eagle-import:SOT23-3")
      (libsource (lib "eagle-import") (part "BAV99"))
    )
    (comp (ref "D546")
      (value "200mA/70V")
      (footprint "eagle-import:SOT23-3")
      (libsource (lib "eagle-import") (part "BAV99"))
    )
    (comp (ref "D547")
      (value "200mA/70V")
      (footprint "eagle-import:SOT23-3")
      (libsource (lib "eagle-import") (part "BAV99"))
    )
    (comp (ref "D548")
      (value "200mA/70V")
      (footprint "eagle-import:SOT23-3")
      (libsource (lib "eagle-import") (part "BAV99"))
    )
    (comp (ref "D549")
      (value "200mA/70V")
      (footprint "eagle-import:SOT23-3")
      (libsource (lib "eagle-import") (part "BAV99"))
    )
    (comp (ref "D550")
      (value "200mA/70V")
      (footprint "eagle-import:SOT23-3")
      (libsource (lib "eagle-import") (part "BAV99"))
    )
    (comp (ref "D551")
      (value "200mA/70V")
      (footprint "eagle-import:SOT23-3")
      (libsource (lib "eagle-import") (part "BAV99"))
    )
    (comp (ref "D552")
      (value "200mA/70V")
      (footprint "eagle-import:SOT23-3")
      (libsource (lib "eagle-import") (part "BAV99"))
    )
    (comp (ref "D553")
      (value "200mA/70V")
      (footprint "eagle-import:SOT23-3")
      (libsource (lib "eagle-import") (part "BAV99"))
    )
    (comp (ref "D554")
      (value "200mA/70V")
      (footprint "eagle-import:SOT23-3")
      (libsource (lib "eagle-import") (part "BAV99"))
    )
    (comp (ref "D555")
      (value "200mA/70V")
      (footprint "eagle-import:SOT23-3")
      (libsource (lib "eagle-import") (part "BAV99"))
    )
    (comp (ref "D556")
      (value "200mA/70V")
      (footprint "eagle-import:SOT23-3")
      (libsource (lib "eagle-import") (part "BAV99"))
    )
    (comp (ref "D557")
      (value "200mA/70V")
      (footprint "eagle-import:SOT23-3")
      (libsource (lib "eagle-import") (part "BAV99"))
    )
    (comp (ref "D558")
      (value "200mA/70V")
      (footprint "eagle-import:SOT23-3")
      (libsource (lib "eagle-import") (part "BAV99"))
    )
    (comp (ref "D559")
      (value "200mA/70V")
      (footprint "eagle-import:SOT23-3")
      (libsource (lib "eagle-import") (part "BAV99"))
    )
    (comp (ref "D560")
      (value "200mA/70V")
      (footprint "eagle-import:SOT23-3")
      (libsource (lib "eagle-import") (part "BAV99"))
    )
    (comp (ref "D577")
      (value "200mA/70V")
      (footprint "eagle-import:SOT23-3")
      (libsource (lib "eagle-import") (part "BAV99"))
    )
    (comp (ref "D578")
      (value "200mA/70V")
      (footprint "eagle-import:SOT23-3")
      (libsource (lib "eagle-import") (part "BAV99"))
    )
    (comp (ref "D579")
      (value "200mA/70V")
      (footprint "eagle-import:SOT23-3")
      (libsource (lib "eagle-import") (part "BAV99"))
    )
    (comp (ref "D580")
      (value "200mA/70V")
      (footprint "eagle-import:SOT23-3")
      (libsource (lib "eagle-import") (part "BAV99"))
    )
    (comp (ref "D581")
      (value "200mA/70V")
      (footprint "eagle-import:SOT23-3")
      (libsource (lib "eagle-import") (part "BAV99"))
    )
    (comp (ref "D582")
      (value "200mA/70V")
      (footprint "eagle-import:SOT23-3")
      (libsource (lib "eagle-import") (part "BAV99"))
    )
    (comp (ref "D583")
      (value "200mA/70V")
      (footprint "eagle-import:SOT23-3")
      (libsource (lib "eagle-import") (part "BAV99"))
    )
    (comp (ref "D584")
      (value "200mA/70V")
      (footprint "eagle-import:SOT23-3")
      (libsource (lib "eagle-import") (part "BAV99"))
    )
    (comp (ref "D585")
      (value "200mA/70V")
      (footprint "eagle-import:SOT23-3")
      (libsource (lib "eagle-import") (part "BAV99"))
    )
    (comp (ref "D586")
      (value "200mA/70V")
      (footprint "eagle-import:SOT23-3")
      (libsource (lib "eagle-import") (part "BAV99"))
    )
    (comp (ref "D587")
      (value "200mA/70V")
      (footprint "eagle-import:SOT23-3")
      (libsource (lib "eagle-import") (part "BAV99"))
    )
    (comp (ref "D588")
      (value "200mA/70V")
      (footprint "eagle-import:SOT23-3")
      (libsource (lib "eagle-import") (part "BAV99"))
    )
    (comp (ref "D589")
      (value "200mA/70V")
      (footprint "eagle-import:SOT23-3")
      (libsource (lib "eagle-import") (part "BAV99"))
    )
    (comp (ref "D590")
      (value "200mA/70V")
      (footprint "eagle-import:SOT23-3")
      (libsource (lib "eagle-import") (part "BAV99"))
    )
    (comp (ref "D591")
      (value "200mA/70V")
      (footprint "eagle-import:SOT23-3")
      (libsource (lib "eagle-import") (part "BAV99"))
    )
    (comp (ref "D592")
      (value "200mA/70V")
      (footprint "eagle-import:SOT23-3")
      (libsource (lib "eagle-import") (part "BAV99"))
    )
    (comp (ref "D609")
      (value "200mA/70V")
      (footprint "eagle-import:SOT23-3")
      (libsource (lib "eagle-import") (part "BAV99"))
    )
    (comp (ref "D610")
      (value "200mA/70V")
      (footprint "eagle-import:SOT23-3")
      (libsource (lib "eagle-import") (part "BAV99"))
    )
    (comp (ref "D611")
      (value "200mA/70V")
      (footprint "eagle-import:SOT23-3")
      (libsource (lib "eagle-import") (part "BAV99"))
    )
    (comp (ref "D612")
      (value "200mA/70V")
      (footprint "eagle-import:SOT23-3")
      (libsource (lib "eagle-import") (part "BAV99"))
    )
    (comp (ref "D613")
      (value "200mA/70V")
      (footprint "eagle-import:SOT23-3")
      (libsource (lib "eagle-import") (part "BAV99"))
    )
    (comp (ref "D614")
      (value "200mA/70V")
      (footprint "eagle-import:SOT23-3")
      (libsource (lib "eagle-import") (part "BAV99"))
    )
    (comp (ref "D615")
      (value "200mA/70V")
      (footprint "eagle-import:SOT23-3")
      (libsource (lib "eagle-import") (part "BAV99"))
    )
    (comp (ref "D616")
      (value "200mA/70V")
      (footprint "eagle-import:SOT23-3")
      (libsource (lib "eagle-import") (part "BAV99"))
    )
    (comp (ref "D617")
      (value "200mA/70V")
      (footprint "eagle-import:SOT23-3")
      (libsource (lib "eagle-import") (part "BAV99"))
    )
    (comp (ref "D618")
      (value "200mA/70V")
      (footprint "eagle-import:SOT23-3")
      (libsource (lib "eagle-import") (part "BAV99"))
    )
    (comp (ref "D619")
      (value "200mA/70V")
      (footprint "eagle-import:SOT23-3")
      (libsource (lib "eagle-import") (part "BAV99"))
    )
    (comp (ref "D620")
      (value "200mA/70V")
      (footprint "eagle-import:SOT23-3")
      (libsource (lib "eagle-import") (part "BAV99"))
    )
    (comp (ref "D621")
      (value "200mA/70V")
      (footprint "eagle-import:SOT23-3")
      (libsource (lib "eagle-import") (part "BAV99"))
    )
    (comp (ref "D622")
      (value "200mA/70V")
      (footprint "eagle-import:SOT23-3")
      (libsource (lib "eagle-import") (part "BAV99"))
    )
    (comp (ref "D623")
      (value "200mA/70V")
      (footprint "eagle-import:SOT23-3")
      (libsource (lib "eagle-import") (part "BAV99"))
    )
    (comp (ref "D624")
      (value "200mA/70V")
      (footprint "eagle-import:SOT23-3")
      (libsource (lib "eagle-import") (part "BAV99"))
    )
    (comp (ref "D641")
      (value "200mA/70V")
      (footprint "eagle-import:SOT23-3")
      (libsource (lib "eagle-import") (part "BAV99"))
    )
    (comp (ref "D642")
      (value "200mA/70V")
      (footprint "eagle-import:SOT23-3")
      (libsource (lib "eagle-import") (part "BAV99"))
    )
    (comp (ref "D643")
      (value "200mA/70V")
      (footprint "eagle-import:SOT23-3")
      (libsource (lib "eagle-import") (part "BAV99"))
    )
    (comp (ref "D644")
      (value "200mA/70V")
      (footprint "eagle-import:SOT23-3")
      (libsource (lib "eagle-import") (part "BAV99"))
    )
    (comp (ref "D645")
      (value "200mA/70V")
      (footprint "eagle-import:SOT23-3")
      (libsource (lib "eagle-import") (part "BAV99"))
    )
    (comp (ref "D646")
      (value "200mA/70V")
      (footprint "eagle-import:SOT23-3")
      (libsource (lib "eagle-import") (part "BAV99"))
    )
    (comp (ref "D647")
      (value "200mA/70V")
      (footprint "eagle-import:SOT23-3")
      (libsource (lib "eagle-import") (part "BAV99"))
    )
    (comp (ref "D648")
      (value "200mA/70V")
      (footprint "eagle-import:SOT23-3")
      (libsource (lib "eagle-import") (part "BAV99"))
    )
    (comp (ref "D649")
      (value "200mA/70V")
      (footprint "eagle-import:SOT23-3")
      (libsource (lib "eagle-import") (part "BAV99"))
    )
    (comp (ref "D650")
      (value "200mA/70V")
      (footprint "eagle-import:SOT23-3")
      (libsource (lib "eagle-import") (part "BAV99"))
    )
    (comp (ref "D651")
      (value "200mA/70V")
      (footprint "eagle-import:SOT23-3")
      (libsource (lib "eagle-import") (part "BAV99"))
    )
    (comp (ref "D652")
      (value "200mA/70V")
      (footprint "eagle-import:SOT23-3")
      (libsource (lib "eagle-import") (part "BAV99"))
    )
    (comp (ref "D653")
      (value "200mA/70V")
      (footprint "eagle-import:SOT23-3")
      (libsource (lib "eagle-import") (part "BAV99"))
    )
    (comp (ref "D654")
      (value "200mA/70V")
      (footprint "eagle-import:SOT23-3")
      (libsource (lib "eagle-import") (part "BAV99"))
    )
    (comp (ref "D655")
      (value "200mA/70V")
      (footprint "eagle-import:SOT23-3")
      (libsource (lib "eagle-import") (part "BAV99"))
    )
    (comp (ref "D656")
      (value "200mA/70V")
      (footprint "eagle-import:SOT23-3")
      (libsource (lib "eagle-import") (part "BAV99"))
    )
    (comp (ref "D673")
      (value "200mA/70V")
      (footprint "eagle-import:SOT23-3")
      (libsource (lib "eagle-import") (part "BAV99"))
    )
    (comp (ref "D674")
      (value "200mA/70V")
      (footprint "eagle-import:SOT23-3")
      (libsource (lib "eagle-import") (part "BAV99"))
    )
    (comp (ref "D675")
      (value "200mA/70V")
      (footprint "eagle-import:SOT23-3")
      (libsource (lib "eagle-import") (part "BAV99"))
    )
    (comp (ref "D676")
      (value "200mA/70V")
      (footprint "eagle-import:SOT23-3")
      (libsource (lib "eagle-import") (part "BAV99"))
    )
    (comp (ref "D677")
      (value "200mA/70V")
      (footprint "eagle-import:SOT23-3")
      (libsource (lib "eagle-import") (part "BAV99"))
    )
    (comp (ref "D678")
      (value "200mA/70V")
      (footprint "eagle-import:SOT23-3")
      (libsource (lib "eagle-import") (part "BAV99"))
    )
    (comp (ref "D679")
      (value "200mA/70V")
      (footprint "eagle-import:SOT23-3")
      (libsource (lib "eagle-import") (part "BAV99"))
    )
    (comp (ref "D680")
      (value "200mA/70V")
      (footprint "eagle-import:SOT23-3")
      (libsource (lib "eagle-import") (part "BAV99"))
    )
    (comp (ref "D681")
      (value "200mA/70V")
      (footprint "eagle-import:SOT23-3")
      (libsource (lib "eagle-import") (part "BAV99"))
    )
    (comp (ref "D682")
      (value "200mA/70V")
      (footprint "eagle-import:SOT23-3")
      (libsource (lib "eagle-import") (part "BAV99"))
    )
    (comp (ref "D683")
      (value "200mA/70V")
      (footprint "eagle-import:SOT23-3")
      (libsource (lib "eagle-import") (part "BAV99"))
    )
    (comp (ref "D684")
      (value "200mA/70V")
      (footprint "eagle-import:SOT23-3")
      (libsource (lib "eagle-import") (part "BAV99"))
    )
    (comp (ref "D685")
      (value "200mA/70V")
      (footprint "eagle-import:SOT23-3")
      (libsource (lib "eagle-import") (part "BAV99"))
    )
    (comp (ref "D686")
      (value "200mA/70V")
      (footprint "eagle-import:SOT23-3")
      (libsource (lib "eagle-import") (part "BAV99"))
    )
    (comp (ref "D687")
      (value "200mA/70V")
      (footprint "eagle-import:SOT23-3")
      (libsource (lib "eagle-import") (part "BAV99"))
    )
    (comp (ref "D688")
      (value "200mA/70V")
      (footprint "eagle-import:SOT23-3")
      (libsource (lib "eagle-import") (part "BAV99"))
    )
    (comp (ref "D705")
      (value "200mA/70V")
      (footprint "eagle-import:SOT23-3")
      (libsource (lib "eagle-import") (part "BAV99"))
    )
    (comp (ref "D706")
      (value "200mA/70V")
      (footprint "eagle-import:SOT23-3")
      (libsource (lib "eagle-import") (part "BAV99"))
    )
    (comp (ref "D707")
      (value "200mA/70V")
      (footprint "eagle-import:SOT23-3")
      (libsource (lib "eagle-import") (part "BAV99"))
    )
    (comp (ref "D708")
      (value "200mA/70V")
      (footprint "eagle-import:SOT23-3")
      (libsource (lib "eagle-import") (part "BAV99"))
    )
    (comp (ref "D709")
      (value "200mA/70V")
      (footprint "eagle-import:SOT23-3")
      (libsource (lib "eagle-import") (part "BAV99"))
    )
    (comp (ref "D710")
      (value "200mA/70V")
      (footprint "eagle-import:SOT23-3")
      (libsource (lib "eagle-import") (part "BAV99"))
    )
    (comp (ref "D711")
      (value "200mA/70V")
      (footprint "eagle-import:SOT23-3")
      (libsource (lib "eagle-import") (part "BAV99"))
    )
    (comp (ref "D712")
      (value "200mA/70V")
      (footprint "eagle-import:SOT23-3")
      (libsource (lib "eagle-import") (part "BAV99"))
    )
    (comp (ref "D713")
      (value "200mA/70V")
      (footprint "eagle-import:SOT23-3")
      (libsource (lib "eagle-import") (part "BAV99"))
    )
    (comp (ref "D714")
      (value "200mA/70V")
      (footprint "eagle-import:SOT23-3")
      (libsource (lib "eagle-import") (part "BAV99"))
    )
    (comp (ref "D715")
      (value "200mA/70V")
      (footprint "eagle-import:SOT23-3")
      (libsource (lib "eagle-import") (part "BAV99"))
    )
    (comp (ref "D716")
      (value "200mA/70V")
      (footprint "eagle-import:SOT23-3")
      (libsource (lib "eagle-import") (part "BAV99"))
    )
    (comp (ref "D717")
      (value "200mA/70V")
      (footprint "eagle-import:SOT23-3")
      (libsource (lib "eagle-import") (part "BAV99"))
    )
    (comp (ref "D718")
      (value "200mA/70V")
      (footprint "eagle-import:SOT23-3")
      (libsource (lib "eagle-import") (part "BAV99"))
    )
    (comp (ref "D719")
      (value "200mA/70V")
      (footprint "eagle-import:SOT23-3")
      (libsource (lib "eagle-import") (part "BAV99"))
    )
    (comp (ref "D720")
      (value "200mA/70V")
      (footprint "eagle-import:SOT23-3")
      (libsource (lib "eagle-import") (part "BAV99"))
    )
    (comp (ref "D737")
      (value "200mA/70V")
      (footprint "eagle-import:SOT23-3")
      (libsource (lib "eagle-import") (part "BAV99"))
    )
    (comp (ref "D738")
      (value "200mA/70V")
      (footprint "eagle-import:SOT23-3")
      (libsource (lib "eagle-import") (part "BAV99"))
    )
    (comp (ref "D739")
      (value "200mA/70V")
      (footprint "eagle-import:SOT23-3")
      (libsource (lib "eagle-import") (part "BAV99"))
    )
    (comp (ref "D740")
      (value "200mA/70V")
      (footprint "eagle-import:SOT23-3")
      (libsource (lib "eagle-import") (part "BAV99"))
    )
    (comp (ref "D741")
      (value "200mA/70V")
      (footprint "eagle-import:SOT23-3")
      (libsource (lib "eagle-import") (part "BAV99"))
    )
    (comp (ref "D742")
      (value "200mA/70V")
      (footprint "eagle-import:SOT23-3")
      (libsource (lib "eagle-import") (part "BAV99"))
    )
    (comp (ref "D743")
      (value "200mA/70V")
      (footprint "eagle-import:SOT23-3")
      (libsource (lib "eagle-import") (part "BAV99"))
    )
    (comp (ref "D744")
      (value "200mA/70V")
      (footprint "eagle-import:SOT23-3")
      (libsource (lib "eagle-import") (part "BAV99"))
    )
    (comp (ref "D745")
      (value "200mA/70V")
      (footprint "eagle-import:SOT23-3")
      (libsource (lib "eagle-import") (part "BAV99"))
    )
    (comp (ref "D746")
      (value "200mA/70V")
      (footprint "eagle-import:SOT23-3")
      (libsource (lib "eagle-import") (part "BAV99"))
    )
    (comp (ref "D747")
      (value "200mA/70V")
      (footprint "eagle-import:SOT23-3")
      (libsource (lib "eagle-import") (part "BAV99"))
    )
    (comp (ref "D748")
      (value "200mA/70V")
      (footprint "eagle-import:SOT23-3")
      (libsource (lib "eagle-import") (part "BAV99"))
    )
    (comp (ref "D749")
      (value "200mA/70V")
      (footprint "eagle-import:SOT23-3")
      (libsource (lib "eagle-import") (part "BAV99"))
    )
    (comp (ref "D750")
      (value "200mA/70V")
      (footprint "eagle-import:SOT23-3")
      (libsource (lib "eagle-import") (part "BAV99"))
    )
    (comp (ref "D751")
      (value "200mA/70V")
      (footprint "eagle-import:SOT23-3")
      (libsource (lib "eagle-import") (part "BAV99"))
    )
    (comp (ref "D752")
      (value "200mA/70V")
      (footprint "eagle-import:SOT23-3")
      (libsource (lib "eagle-import") (part "BAV99"))
    )
    (comp (ref "D769")
      (value "200mA/70V")
      (footprint "eagle-import:SOT23-3")
      (libsource (lib "eagle-import") (part "BAV99"))
    )
    (comp (ref "D770")
      (value "200mA/70V")
      (footprint "eagle-import:SOT23-3")
      (libsource (lib "eagle-import") (part "BAV99"))
    )
    (comp (ref "D771")
      (value "200mA/70V")
      (footprint "eagle-import:SOT23-3")
      (libsource (lib "eagle-import") (part "BAV99"))
    )
    (comp (ref "D772")
      (value "200mA/70V")
      (footprint "eagle-import:SOT23-3")
      (libsource (lib "eagle-import") (part "BAV99"))
    )
    (comp (ref "D773")
      (value "200mA/70V")
      (footprint "eagle-import:SOT23-3")
      (libsource (lib "eagle-import") (part "BAV99"))
    )
    (comp (ref "D774")
      (value "200mA/70V")
      (footprint "eagle-import:SOT23-3")
      (libsource (lib "eagle-import") (part "BAV99"))
    )
    (comp (ref "D775")
      (value "200mA/70V")
      (footprint "eagle-import:SOT23-3")
      (libsource (lib "eagle-import") (part "BAV99"))
    )
    (comp (ref "D776")
      (value "200mA/70V")
      (footprint "eagle-import:SOT23-3")
      (libsource (lib "eagle-import") (part "BAV99"))
    )
    (comp (ref "D777")
      (value "200mA/70V")
      (footprint "eagle-import:SOT23-3")
      (libsource (lib "eagle-import") (part "BAV99"))
    )
    (comp (ref "D778")
      (value "200mA/70V")
      (footprint "eagle-import:SOT23-3")
      (libsource (lib "eagle-import") (part "BAV99"))
    )
    (comp (ref "D779")
      (value "200mA/70V")
      (footprint "eagle-import:SOT23-3")
      (libsource (lib "eagle-import") (part "BAV99"))
    )
    (comp (ref "D780")
      (value "200mA/70V")
      (footprint "eagle-import:SOT23-3")
      (libsource (lib "eagle-import") (part "BAV99"))
    )
    (comp (ref "D781")
      (value "200mA/70V")
      (footprint "eagle-import:SOT23-3")
      (libsource (lib "eagle-import") (part "BAV99"))
    )
    (comp (ref "D782")
      (value "200mA/70V")
      (footprint "eagle-import:SOT23-3")
      (libsource (lib "eagle-import") (part "BAV99"))
    )
    (comp (ref "D783")
      (value "200mA/70V")
      (footprint "eagle-import:SOT23-3")
      (libsource (lib "eagle-import") (part "BAV99"))
    )
    (comp (ref "D784")
      (value "200mA/70V")
      (footprint "eagle-import:SOT23-3")
      (libsource (lib "eagle-import") (part "BAV99"))
    )
    (comp (ref "D801")
      (value "200mA/70V")
      (footprint "eagle-import:SOT23-3")
      (libsource (lib "eagle-import") (part "BAV99"))
    )
    (comp (ref "D802")
      (value "200mA/70V")
      (footprint "eagle-import:SOT23-3")
      (libsource (lib "eagle-import") (part "BAV99"))
    )
    (comp (ref "D803")
      (value "200mA/70V")
      (footprint "eagle-import:SOT23-3")
      (libsource (lib "eagle-import") (part "BAV99"))
    )
    (comp (ref "D804")
      (value "200mA/70V")
      (footprint "eagle-import:SOT23-3")
      (libsource (lib "eagle-import") (part "BAV99"))
    )
    (comp (ref "D805")
      (value "200mA/70V")
      (footprint "eagle-import:SOT23-3")
      (libsource (lib "eagle-import") (part "BAV99"))
    )
    (comp (ref "D806")
      (value "200mA/70V")
      (footprint "eagle-import:SOT23-3")
      (libsource (lib "eagle-import") (part "BAV99"))
    )
    (comp (ref "D807")
      (value "200mA/70V")
      (footprint "eagle-import:SOT23-3")
      (libsource (lib "eagle-import") (part "BAV99"))
    )
    (comp (ref "D808")
      (value "200mA/70V")
      (footprint "eagle-import:SOT23-3")
      (libsource (lib "eagle-import") (part "BAV99"))
    )
    (comp (ref "D809")
      (value "200mA/70V")
      (footprint "eagle-import:SOT23-3")
      (libsource (lib "eagle-import") (part "BAV99"))
    )
    (comp (ref "D810")
      (value "200mA/70V")
      (footprint "eagle-import:SOT23-3")
      (libsource (lib "eagle-import") (part "BAV99"))
    )
    (comp (ref "D811")
      (value "200mA/70V")
      (footprint "eagle-import:SOT23-3")
      (libsource (lib "eagle-import") (part "BAV99"))
    )
    (comp (ref "D812")
      (value "200mA/70V")
      (footprint "eagle-import:SOT23-3")
      (libsource (lib "eagle-import") (part "BAV99"))
    )
    (comp (ref "D813")
      (value "200mA/70V")
      (footprint "eagle-import:SOT23-3")
      (libsource (lib "eagle-import") (part "BAV99"))
    )
    (comp (ref "D814")
      (value "200mA/70V")
      (footprint "eagle-import:SOT23-3")
      (libsource (lib "eagle-import") (part "BAV99"))
    )
    (comp (ref "D815")
      (value "200mA/70V")
      (footprint "eagle-import:SOT23-3")
      (libsource (lib "eagle-import") (part "BAV99"))
    )
    (comp (ref "D816")
      (value "200mA/70V")
      (footprint "eagle-import:SOT23-3")
      (libsource (lib "eagle-import") (part "BAV99"))
    )
    (comp (ref "D833")
      (value "200mA/70V")
      (footprint "eagle-import:SOT23-3")
      (libsource (lib "eagle-import") (part "BAV99"))
    )
    (comp (ref "D834")
      (value "200mA/70V")
      (footprint "eagle-import:SOT23-3")
      (libsource (lib "eagle-import") (part "BAV99"))
    )
    (comp (ref "D835")
      (value "200mA/70V")
      (footprint "eagle-import:SOT23-3")
      (libsource (lib "eagle-import") (part "BAV99"))
    )
    (comp (ref "D836")
      (value "200mA/70V")
      (footprint "eagle-import:SOT23-3")
      (libsource (lib "eagle-import") (part "BAV99"))
    )
    (comp (ref "D837")
      (value "200mA/70V")
      (footprint "eagle-import:SOT23-3")
      (libsource (lib "eagle-import") (part "BAV99"))
    )
    (comp (ref "D838")
      (value "200mA/70V")
      (footprint "eagle-import:SOT23-3")
      (libsource (lib "eagle-import") (part "BAV99"))
    )
    (comp (ref "D839")
      (value "200mA/70V")
      (footprint "eagle-import:SOT23-3")
      (libsource (lib "eagle-import") (part "BAV99"))
    )
    (comp (ref "D840")
      (value "200mA/70V")
      (footprint "eagle-import:SOT23-3")
      (libsource (lib "eagle-import") (part "BAV99"))
    )
    (comp (ref "D841")
      (value "200mA/70V")
      (footprint "eagle-import:SOT23-3")
      (libsource (lib "eagle-import") (part "BAV99"))
    )
    (comp (ref "D842")
      (value "200mA/70V")
      (footprint "eagle-import:SOT23-3")
      (libsource (lib "eagle-import") (part "BAV99"))
    )
    (comp (ref "D843")
      (value "200mA/70V")
      (footprint "eagle-import:SOT23-3")
      (libsource (lib "eagle-import") (part "BAV99"))
    )
    (comp (ref "D844")
      (value "200mA/70V")
      (footprint "eagle-import:SOT23-3")
      (libsource (lib "eagle-import") (part "BAV99"))
    )
    (comp (ref "D845")
      (value "200mA/70V")
      (footprint "eagle-import:SOT23-3")
      (libsource (lib "eagle-import") (part "BAV99"))
    )
    (comp (ref "D846")
      (value "200mA/70V")
      (footprint "eagle-import:SOT23-3")
      (libsource (lib "eagle-import") (part "BAV99"))
    )
    (comp (ref "D847")
      (value "200mA/70V")
      (footprint "eagle-import:SOT23-3")
      (libsource (lib "eagle-import") (part "BAV99"))
    )
    (comp (ref "D848")
      (value "200mA/70V")
      (footprint "eagle-import:SOT23-3")
      (libsource (lib "eagle-import") (part "BAV99"))
    )
    (comp (ref "D865")
      (value "200mA/70V")
      (footprint "eagle-import:SOT23-3")
      (libsource (lib "eagle-import") (part "BAV99"))
    )
    (comp (ref "D866")
      (value "200mA/70V")
      (footprint "eagle-import:SOT23-3")
      (libsource (lib "eagle-import") (part "BAV99"))
    )
    (comp (ref "D867")
      (value "200mA/70V")
      (footprint "eagle-import:SOT23-3")
      (libsource (lib "eagle-import") (part "BAV99"))
    )
    (comp (ref "D868")
      (value "200mA/70V")
      (footprint "eagle-import:SOT23-3")
      (libsource (lib "eagle-import") (part "BAV99"))
    )
    (comp (ref "D869")
      (value "200mA/70V")
      (footprint "eagle-import:SOT23-3")
      (libsource (lib "eagle-import") (part "BAV99"))
    )
    (comp (ref "D870")
      (value "200mA/70V")
      (footprint "eagle-import:SOT23-3")
      (libsource (lib "eagle-import") (part "BAV99"))
    )
    (comp (ref "D871")
      (value "200mA/70V")
      (footprint "eagle-import:SOT23-3")
      (libsource (lib "eagle-import") (part "BAV99"))
    )
    (comp (ref "D872")
      (value "200mA/70V")
      (footprint "eagle-import:SOT23-3")
      (libsource (lib "eagle-import") (part "BAV99"))
    )
    (comp (ref "D873")
      (value "200mA/70V")
      (footprint "eagle-import:SOT23-3")
      (libsource (lib "eagle-import") (part "BAV99"))
    )
    (comp (ref "D874")
      (value "200mA/70V")
      (footprint "eagle-import:SOT23-3")
      (libsource (lib "eagle-import") (part "BAV99"))
    )
    (comp (ref "D875")
      (value "200mA/70V")
      (footprint "eagle-import:SOT23-3")
      (libsource (lib "eagle-import") (part "BAV99"))
    )
    (comp (ref "D876")
      (value "200mA/70V")
      (footprint "eagle-import:SOT23-3")
      (libsource (lib "eagle-import") (part "BAV99"))
    )
    (comp (ref "D877")
      (value "200mA/70V")
      (footprint "eagle-import:SOT23-3")
      (libsource (lib "eagle-import") (part "BAV99"))
    )
    (comp (ref "D878")
      (value "200mA/70V")
      (footprint "eagle-import:SOT23-3")
      (libsource (lib "eagle-import") (part "BAV99"))
    )
    (comp (ref "D879")
      (value "200mA/70V")
      (footprint "eagle-import:SOT23-3")
      (libsource (lib "eagle-import") (part "BAV99"))
    )
    (comp (ref "D880")
      (value "200mA/70V")
      (footprint "eagle-import:SOT23-3")
      (libsource (lib "eagle-import") (part "BAV99"))
    )
    (comp (ref "D897")
      (value "200mA/70V")
      (footprint "eagle-import:SOT23-3")
      (libsource (lib "eagle-import") (part "BAV99"))
    )
    (comp (ref "D898")
      (value "200mA/70V")
      (footprint "eagle-import:SOT23-3")
      (libsource (lib "eagle-import") (part "BAV99"))
    )
    (comp (ref "D899")
      (value "200mA/70V")
      (footprint "eagle-import:SOT23-3")
      (libsource (lib "eagle-import") (part "BAV99"))
    )
    (comp (ref "D900")
      (value "200mA/70V")
      (footprint "eagle-import:SOT23-3")
      (libsource (lib "eagle-import") (part "BAV99"))
    )
    (comp (ref "D901")
      (value "200mA/70V")
      (footprint "eagle-import:SOT23-3")
      (libsource (lib "eagle-import") (part "BAV99"))
    )
    (comp (ref "D902")
      (value "200mA/70V")
      (footprint "eagle-import:SOT23-3")
      (libsource (lib "eagle-import") (part "BAV99"))
    )
    (comp (ref "D903")
      (value "200mA/70V")
      (footprint "eagle-import:SOT23-3")
      (libsource (lib "eagle-import") (part "BAV99"))
    )
    (comp (ref "D904")
      (value "200mA/70V")
      (footprint "eagle-import:SOT23-3")
      (libsource (lib "eagle-import") (part "BAV99"))
    )
    (comp (ref "D905")
      (value "200mA/70V")
      (footprint "eagle-import:SOT23-3")
      (libsource (lib "eagle-import") (part "BAV99"))
    )
    (comp (ref "D906")
      (value "200mA/70V")
      (footprint "eagle-import:SOT23-3")
      (libsource (lib "eagle-import") (part "BAV99"))
    )
    (comp (ref "D907")
      (value "200mA/70V")
      (footprint "eagle-import:SOT23-3")
      (libsource (lib "eagle-import") (part "BAV99"))
    )
    (comp (ref "D908")
      (value "200mA/70V")
      (footprint "eagle-import:SOT23-3")
      (libsource (lib "eagle-import") (part "BAV99"))
    )
    (comp (ref "D909")
      (value "200mA/70V")
      (footprint "eagle-import:SOT23-3")
      (libsource (lib "eagle-import") (part "BAV99"))
    )
    (comp (ref "D910")
      (value "200mA/70V")
      (footprint "eagle-import:SOT23-3")
      (libsource (lib "eagle-import") (part "BAV99"))
    )
    (comp (ref "D911")
      (value "200mA/70V")
      (footprint "eagle-import:SOT23-3")
      (libsource (lib "eagle-import") (part "BAV99"))
    )
    (comp (ref "D912")
      (value "200mA/70V")
      (footprint "eagle-import:SOT23-3")
      (libsource (lib "eagle-import") (part "BAV99"))
    )
    (comp (ref "D929")
      (value "200mA/70V")
      (footprint "eagle-import:SOT23-3")
      (libsource (lib "eagle-import") (part "BAV99"))
    )
    (comp (ref "D930")
      (value "200mA/70V")
      (footprint "eagle-import:SOT23-3")
      (libsource (lib "eagle-import") (part "BAV99"))
    )
    (comp (ref "D931")
      (value "200mA/70V")
      (footprint "eagle-import:SOT23-3")
      (libsource (lib "eagle-import") (part "BAV99"))
    )
    (comp (ref "D932")
      (value "200mA/70V")
      (footprint "eagle-import:SOT23-3")
      (libsource (lib "eagle-import") (part "BAV99"))
    )
    (comp (ref "D933")
      (value "200mA/70V")
      (footprint "eagle-import:SOT23-3")
      (libsource (lib "eagle-import") (part "BAV99"))
    )
    (comp (ref "D934")
      (value "200mA/70V")
      (footprint "eagle-import:SOT23-3")
      (libsource (lib "eagle-import") (part "BAV99"))
    )
    (comp (ref "D935")
      (value "200mA/70V")
      (footprint "eagle-import:SOT23-3")
      (libsource (lib "eagle-import") (part "BAV99"))
    )
    (comp (ref "D936")
      (value "200mA/70V")
      (footprint "eagle-import:SOT23-3")
      (libsource (lib "eagle-import") (part "BAV99"))
    )
    (comp (ref "D937")
      (value "200mA/70V")
      (footprint "eagle-import:SOT23-3")
      (libsource (lib "eagle-import") (part "BAV99"))
    )
    (comp (ref "D938")
      (value "200mA/70V")
      (footprint "eagle-import:SOT23-3")
      (libsource (lib "eagle-import") (part "BAV99"))
    )
    (comp (ref "D939")
      (value "200mA/70V")
      (footprint "eagle-import:SOT23-3")
      (libsource (lib "eagle-import") (part "BAV99"))
    )
    (comp (ref "D940")
      (value "200mA/70V")
      (footprint "eagle-import:SOT23-3")
      (libsource (lib "eagle-import") (part "BAV99"))
    )
    (comp (ref "D941")
      (value "200mA/70V")
      (footprint "eagle-import:SOT23-3")
      (libsource (lib "eagle-import") (part "BAV99"))
    )
    (comp (ref "D942")
      (value "200mA/70V")
      (footprint "eagle-import:SOT23-3")
      (libsource (lib "eagle-import") (part "BAV99"))
    )
    (comp (ref "D943")
      (value "200mA/70V")
      (footprint "eagle-import:SOT23-3")
      (libsource (lib "eagle-import") (part "BAV99"))
    )
    (comp (ref "D944")
      (value "200mA/70V")
      (footprint "eagle-import:SOT23-3")
      (libsource (lib "eagle-import") (part "BAV99"))
    )
    (comp (ref "D961")
      (value "200mA/70V")
      (footprint "eagle-import:SOT23-3")
      (libsource (lib "eagle-import") (part "BAV99"))
    )
    (comp (ref "D962")
      (value "200mA/70V")
      (footprint "eagle-import:SOT23-3")
      (libsource (lib "eagle-import") (part "BAV99"))
    )
    (comp (ref "D963")
      (value "200mA/70V")
      (footprint "eagle-import:SOT23-3")
      (libsource (lib "eagle-import") (part "BAV99"))
    )
    (comp (ref "D964")
      (value "200mA/70V")
      (footprint "eagle-import:SOT23-3")
      (libsource (lib "eagle-import") (part "BAV99"))
    )
    (comp (ref "D965")
      (value "200mA/70V")
      (footprint "eagle-import:SOT23-3")
      (libsource (lib "eagle-import") (part "BAV99"))
    )
    (comp (ref "D966")
      (value "200mA/70V")
      (footprint "eagle-import:SOT23-3")
      (libsource (lib "eagle-import") (part "BAV99"))
    )
    (comp (ref "D967")
      (value "200mA/70V")
      (footprint "eagle-import:SOT23-3")
      (libsource (lib "eagle-import") (part "BAV99"))
    )
    (comp (ref "D968")
      (value "200mA/70V")
      (footprint "eagle-import:SOT23-3")
      (libsource (lib "eagle-import") (part "BAV99"))
    )
    (comp (ref "D969")
      (value "200mA/70V")
      (footprint "eagle-import:SOT23-3")
      (libsource (lib "eagle-import") (part "BAV99"))
    )
    (comp (ref "D970")
      (value "200mA/70V")
      (footprint "eagle-import:SOT23-3")
      (libsource (lib "eagle-import") (part "BAV99"))
    )
    (comp (ref "D971")
      (value "200mA/70V")
      (footprint "eagle-import:SOT23-3")
      (libsource (lib "eagle-import") (part "BAV99"))
    )
    (comp (ref "D972")
      (value "200mA/70V")
      (footprint "eagle-import:SOT23-3")
      (libsource (lib "eagle-import") (part "BAV99"))
    )
    (comp (ref "D973")
      (value "200mA/70V")
      (footprint "eagle-import:SOT23-3")
      (libsource (lib "eagle-import") (part "BAV99"))
    )
    (comp (ref "D974")
      (value "200mA/70V")
      (footprint "eagle-import:SOT23-3")
      (libsource (lib "eagle-import") (part "BAV99"))
    )
    (comp (ref "D975")
      (value "200mA/70V")
      (footprint "eagle-import:SOT23-3")
      (libsource (lib "eagle-import") (part "BAV99"))
    )
    (comp (ref "D976")
      (value "200mA/70V")
      (footprint "eagle-import:SOT23-3")
      (libsource (lib "eagle-import") (part "BAV99"))
    )
    (comp (ref "D993")
      (value "200mA/70V")
      (footprint "eagle-import:SOT23-3")
      (libsource (lib "eagle-import") (part "BAV99"))
    )
    (comp (ref "D994")
      (value "200mA/70V")
      (footprint "eagle-import:SOT23-3")
      (libsource (lib "eagle-import") (part "BAV99"))
    )
    (comp (ref "D995")
      (value "200mA/70V")
      (footprint "eagle-import:SOT23-3")
      (libsource (lib "eagle-import") (part "BAV99"))
    )
    (comp (ref "D996")
      (value "200mA/70V")
      (footprint "eagle-import:SOT23-3")
      (libsource (lib "eagle-import") (part "BAV99"))
    )
    (comp (ref "D997")
      (value "200mA/70V")
      (footprint "eagle-import:SOT23-3")
      (libsource (lib "eagle-import") (part "BAV99"))
    )
    (comp (ref "D998")
      (value "200mA/70V")
      (footprint "eagle-import:SOT23-3")
      (libsource (lib "eagle-import") (part "BAV99"))
    )
    (comp (ref "D999")
      (value "200mA/70V")
      (footprint "eagle-import:SOT23-3")
      (libsource (lib "eagle-import") (part "BAV99"))
    )
    (comp (ref "D1000")
      (value "200mA/70V")
      (footprint "eagle-import:SOT23-3")
      (libsource (lib "eagle-import") (part "BAV99"))
    )
    (comp (ref "D1001")
      (value "200mA/70V")
      (footprint "eagle-import:SOT23-3")
      (libsource (lib "eagle-import") (part "BAV99"))
    )
    (comp (ref "D1002")
      (value "200mA/70V")
      (footprint "eagle-import:SOT23-3")
      (libsource (lib "eagle-import") (part "BAV99"))
    )
    (comp (ref "D1003")
      (value "200mA/70V")
      (footprint "eagle-import:SOT23-3")
      (libsource (lib "eagle-import") (part "BAV99"))
    )
    (comp (ref "D1004")
      (value "200mA/70V")
      (footprint "eagle-import:SOT23-3")
      (libsource (lib "eagle-import") (part "BAV99"))
    )
    (comp (ref "D1005")
      (value "200mA/70V")
      (footprint "eagle-import:SOT23-3")
      (libsource (lib "eagle-import") (part "BAV99"))
    )
    (comp (ref "D1006")
      (value "200mA/70V")
      (footprint "eagle-import:SOT23-3")
      (libsource (lib "eagle-import") (part "BAV99"))
    )
    (comp (ref "D1007")
      (value "200mA/70V")
      (footprint "eagle-import:SOT23-3")
      (libsource (lib "eagle-import") (part "BAV99"))
    )
    (comp (ref "D1008")
      (value "200mA/70V")
      (footprint "eagle-import:SOT23-3")
      (libsource (lib "eagle-import") (part "BAV99"))
    )
    (comp (ref "L513")
      (value "SD8")
      (footprint "eagle-import:SD8")
      (libsource (lib "eagle-import") (part "SD8"))
    )
    (comp (ref "L514")
      (value "SD8")
      (footprint "eagle-import:SD8")
      (libsource (lib "eagle-import") (part "SD8"))
    )
    (comp (ref "L515")
      (value "SD8")
      (footprint "eagle-import:SD8")
      (libsource (lib "eagle-import") (part "SD8"))
    )
    (comp (ref "L516")
      (value "SD8")
      (footprint "eagle-import:SD8")
      (libsource (lib "eagle-import") (part "SD8"))
    )
    (comp (ref "L517")
      (value "SD8")
      (footprint "eagle-import:SD8")
      (libsource (lib "eagle-import") (part "SD8"))
    )
    (comp (ref "L518")
      (value "SD8")
      (footprint "eagle-import:SD8")
      (libsource (lib "eagle-import") (part "SD8"))
    )
    (comp (ref "L519")
      (value "SD8")
      (footprint "eagle-import:SD8")
      (libsource (lib "eagle-import") (part "SD8"))
    )
    (comp (ref "L520")
      (value "SD8")
      (footprint "eagle-import:SD8")
      (libsource (lib "eagle-import") (part "SD8"))
    )
    (comp (ref "L521")
      (value "SD8")
      (footprint "eagle-import:SD8")
      (libsource (lib "eagle-import") (part "SD8"))
    )
    (comp (ref "L522")
      (value "SD8")
      (footprint "eagle-import:SD8")
      (libsource (lib "eagle-import") (part "SD8"))
    )
    (comp (ref "L523")
      (value "SD8")
      (footprint "eagle-import:SD8")
      (libsource (lib "eagle-import") (part "SD8"))
    )
    (comp (ref "L524")
      (value "SD8")
      (footprint "eagle-import:SD8")
      (libsource (lib "eagle-import") (part "SD8"))
    )
    (comp (ref "L525")
      (value "SD8")
      (footprint "eagle-import:SD8")
      (libsource (lib "eagle-import") (part "SD8"))
    )
    (comp (ref "L526")
      (value "SD8")
      (footprint "eagle-import:SD8")
      (libsource (lib "eagle-import") (part "SD8"))
    )
    (comp (ref "L527")
      (value "SD8")
      (footprint "eagle-import:SD8")
      (libsource (lib "eagle-import") (part "SD8"))
    )
    (comp (ref "L528")
      (value "SD8")
      (footprint "eagle-import:SD8")
      (libsource (lib "eagle-import") (part "SD8"))
    )
    (comp (ref "L545")
      (value "SD8")
      (footprint "eagle-import:SD8")
      (libsource (lib "eagle-import") (part "SD8"))
    )
    (comp (ref "L546")
      (value "SD8")
      (footprint "eagle-import:SD8")
      (libsource (lib "eagle-import") (part "SD8"))
    )
    (comp (ref "L547")
      (value "SD8")
      (footprint "eagle-import:SD8")
      (libsource (lib "eagle-import") (part "SD8"))
    )
    (comp (ref "L548")
      (value "SD8")
      (footprint "eagle-import:SD8")
      (libsource (lib "eagle-import") (part "SD8"))
    )
    (comp (ref "L549")
      (value "SD8")
      (footprint "eagle-import:SD8")
      (libsource (lib "eagle-import") (part "SD8"))
    )
    (comp (ref "L550")
      (value "SD8")
      (footprint "eagle-import:SD8")
      (libsource (lib "eagle-import") (part "SD8"))
    )
    (comp (ref "L551")
      (value "SD8")
      (footprint "eagle-import:SD8")
      (libsource (lib "eagle-import") (part "SD8"))
    )
    (comp (ref "L552")
      (value "SD8")
      (footprint "eagle-import:SD8")
      (libsource (lib "eagle-import") (part "SD8"))
    )
    (comp (ref "L553")
      (value "SD8")
      (footprint "eagle-import:SD8")
      (libsource (lib "eagle-import") (part "SD8"))
    )
    (comp (ref "L554")
      (value "SD8")
      (footprint "eagle-import:SD8")
      (libsource (lib "eagle-import") (part "SD8"))
    )
    (comp (ref "L555")
      (value "SD8")
      (footprint "eagle-import:SD8")
      (libsource (lib "eagle-import") (part "SD8"))
    )
    (comp (ref "L556")
      (value "SD8")
      (footprint "eagle-import:SD8")
      (libsource (lib "eagle-import") (part "SD8"))
    )
    (comp (ref "L557")
      (value "SD8")
      (footprint "eagle-import:SD8")
      (libsource (lib "eagle-import") (part "SD8"))
    )
    (comp (ref "L558")
      (value "SD8")
      (footprint "eagle-import:SD8")
      (libsource (lib "eagle-import") (part "SD8"))
    )
    (comp (ref "L559")
      (value "SD8")
      (footprint "eagle-import:SD8")
      (libsource (lib "eagle-import") (part "SD8"))
    )
    (comp (ref "L560")
      (value "SD8")
      (footprint "eagle-import:SD8")
      (libsource (lib "eagle-import") (part "SD8"))
    )
    (comp (ref "L577")
      (value "SD8")
      (footprint "eagle-import:SD8")
      (libsource (lib "eagle-import") (part "SD8"))
    )
    (comp (ref "L578")
      (value "SD8")
      (footprint "eagle-import:SD8")
      (libsource (lib "eagle-import") (part "SD8"))
    )
    (comp (ref "L579")
      (value "SD8")
      (footprint "eagle-import:SD8")
      (libsource (lib "eagle-import") (part "SD8"))
    )
    (comp (ref "L580")
      (value "SD8")
      (footprint "eagle-import:SD8")
      (libsource (lib "eagle-import") (part "SD8"))
    )
    (comp (ref "L581")
      (value "SD8")
      (footprint "eagle-import:SD8")
      (libsource (lib "eagle-import") (part "SD8"))
    )
    (comp (ref "L582")
      (value "SD8")
      (footprint "eagle-import:SD8")
      (libsource (lib "eagle-import") (part "SD8"))
    )
    (comp (ref "L583")
      (value "SD8")
      (footprint "eagle-import:SD8")
      (libsource (lib "eagle-import") (part "SD8"))
    )
    (comp (ref "L584")
      (value "SD8")
      (footprint "eagle-import:SD8")
      (libsource (lib "eagle-import") (part "SD8"))
    )
    (comp (ref "L585")
      (value "SD8")
      (footprint "eagle-import:SD8")
      (libsource (lib "eagle-import") (part "SD8"))
    )
    (comp (ref "L586")
      (value "SD8")
      (footprint "eagle-import:SD8")
      (libsource (lib "eagle-import") (part "SD8"))
    )
    (comp (ref "L587")
      (value "SD8")
      (footprint "eagle-import:SD8")
      (libsource (lib "eagle-import") (part "SD8"))
    )
    (comp (ref "L588")
      (value "SD8")
      (footprint "eagle-import:SD8")
      (libsource (lib "eagle-import") (part "SD8"))
    )
    (comp (ref "L589")
      (value "SD8")
      (footprint "eagle-import:SD8")
      (libsource (lib "eagle-import") (part "SD8"))
    )
    (comp (ref "L590")
      (value "SD8")
      (footprint "eagle-import:SD8")
      (libsource (lib "eagle-import") (part "SD8"))
    )
    (comp (ref "L591")
      (value "SD8")
      (footprint "eagle-import:SD8")
      (libsource (lib "eagle-import") (part "SD8"))
    )
    (comp (ref "L592")
      (value "SD8")
      (footprint "eagle-import:SD8")
      (libsource (lib "eagle-import") (part "SD8"))
    )
    (comp (ref "L609")
      (value "SD8")
      (footprint "eagle-import:SD8")
      (libsource (lib "eagle-import") (part "SD8"))
    )
    (comp (ref "L610")
      (value "SD8")
      (footprint "eagle-import:SD8")
      (libsource (lib "eagle-import") (part "SD8"))
    )
    (comp (ref "L611")
      (value "SD8")
      (footprint "eagle-import:SD8")
      (libsource (lib "eagle-import") (part "SD8"))
    )
    (comp (ref "L612")
      (value "SD8")
      (footprint "eagle-import:SD8")
      (libsource (lib "eagle-import") (part "SD8"))
    )
    (comp (ref "L613")
      (value "SD8")
      (footprint "eagle-import:SD8")
      (libsource (lib "eagle-import") (part "SD8"))
    )
    (comp (ref "L614")
      (value "SD8")
      (footprint "eagle-import:SD8")
      (libsource (lib "eagle-import") (part "SD8"))
    )
    (comp (ref "L615")
      (value "SD8")
      (footprint "eagle-import:SD8")
      (libsource (lib "eagle-import") (part "SD8"))
    )
    (comp (ref "L616")
      (value "SD8")
      (footprint "eagle-import:SD8")
      (libsource (lib "eagle-import") (part "SD8"))
    )
    (comp (ref "L617")
      (value "SD8")
      (footprint "eagle-import:SD8")
      (libsource (lib "eagle-import") (part "SD8"))
    )
    (comp (ref "L618")
      (value "SD8")
      (footprint "eagle-import:SD8")
      (libsource (lib "eagle-import") (part "SD8"))
    )
    (comp (ref "L619")
      (value "SD8")
      (footprint "eagle-import:SD8")
      (libsource (lib "eagle-import") (part "SD8"))
    )
    (comp (ref "L620")
      (value "SD8")
      (footprint "eagle-import:SD8")
      (libsource (lib "eagle-import") (part "SD8"))
    )
    (comp (ref "L621")
      (value "SD8")
      (footprint "eagle-import:SD8")
      (libsource (lib "eagle-import") (part "SD8"))
    )
    (comp (ref "L622")
      (value "SD8")
      (footprint "eagle-import:SD8")
      (libsource (lib "eagle-import") (part "SD8"))
    )
    (comp (ref "L623")
      (value "SD8")
      (footprint "eagle-import:SD8")
      (libsource (lib "eagle-import") (part "SD8"))
    )
    (comp (ref "L624")
      (value "SD8")
      (footprint "eagle-import:SD8")
      (libsource (lib "eagle-import") (part "SD8"))
    )
    (comp (ref "L641")
      (value "SD8")
      (footprint "eagle-import:SD8")
      (libsource (lib "eagle-import") (part "SD8"))
    )
    (comp (ref "L642")
      (value "SD8")
      (footprint "eagle-import:SD8")
      (libsource (lib "eagle-import") (part "SD8"))
    )
    (comp (ref "L643")
      (value "SD8")
      (footprint "eagle-import:SD8")
      (libsource (lib "eagle-import") (part "SD8"))
    )
    (comp (ref "L644")
      (value "SD8")
      (footprint "eagle-import:SD8")
      (libsource (lib "eagle-import") (part "SD8"))
    )
    (comp (ref "L645")
      (value "SD8")
      (footprint "eagle-import:SD8")
      (libsource (lib "eagle-import") (part "SD8"))
    )
    (comp (ref "L646")
      (value "SD8")
      (footprint "eagle-import:SD8")
      (libsource (lib "eagle-import") (part "SD8"))
    )
    (comp (ref "L647")
      (value "SD8")
      (footprint "eagle-import:SD8")
      (libsource (lib "eagle-import") (part "SD8"))
    )
    (comp (ref "L648")
      (value "SD8")
      (footprint "eagle-import:SD8")
      (libsource (lib "eagle-import") (part "SD8"))
    )
    (comp (ref "L649")
      (value "SD8")
      (footprint "eagle-import:SD8")
      (libsource (lib "eagle-import") (part "SD8"))
    )
    (comp (ref "L650")
      (value "SD8")
      (footprint "eagle-import:SD8")
      (libsource (lib "eagle-import") (part "SD8"))
    )
    (comp (ref "L651")
      (value "SD8")
      (footprint "eagle-import:SD8")
      (libsource (lib "eagle-import") (part "SD8"))
    )
    (comp (ref "L652")
      (value "SD8")
      (footprint "eagle-import:SD8")
      (libsource (lib "eagle-import") (part "SD8"))
    )
    (comp (ref "L653")
      (value "SD8")
      (footprint "eagle-import:SD8")
      (libsource (lib "eagle-import") (part "SD8"))
    )
    (comp (ref "L654")
      (value "SD8")
      (footprint "eagle-import:SD8")
      (libsource (lib "eagle-import") (part "SD8"))
    )
    (comp (ref "L655")
      (value "SD8")
      (footprint "eagle-import:SD8")
      (libsource (lib "eagle-import") (part "SD8"))
    )
    (comp (ref "L656")
      (value "SD8")
      (footprint "eagle-import:SD8")
      (libsource (lib "eagle-import") (part "SD8"))
    )
    (comp (ref "L673")
      (value "SD8")
      (footprint "eagle-import:SD8")
      (libsource (lib "eagle-import") (part "SD8"))
    )
    (comp (ref "L674")
      (value "SD8")
      (footprint "eagle-import:SD8")
      (libsource (lib "eagle-import") (part "SD8"))
    )
    (comp (ref "L675")
      (value "SD8")
      (footprint "eagle-import:SD8")
      (libsource (lib "eagle-import") (part "SD8"))
    )
    (comp (ref "L676")
      (value "SD8")
      (footprint "eagle-import:SD8")
      (libsource (lib "eagle-import") (part "SD8"))
    )
    (comp (ref "L677")
      (value "SD8")
      (footprint "eagle-import:SD8")
      (libsource (lib "eagle-import") (part "SD8"))
    )
    (comp (ref "L678")
      (value "SD8")
      (footprint "eagle-import:SD8")
      (libsource (lib "eagle-import") (part "SD8"))
    )
    (comp (ref "L679")
      (value "SD8")
      (footprint "eagle-import:SD8")
      (libsource (lib "eagle-import") (part "SD8"))
    )
    (comp (ref "L680")
      (value "SD8")
      (footprint "eagle-import:SD8")
      (libsource (lib "eagle-import") (part "SD8"))
    )
    (comp (ref "L681")
      (value "SD8")
      (footprint "eagle-import:SD8")
      (libsource (lib "eagle-import") (part "SD8"))
    )
    (comp (ref "L682")
      (value "SD8")
      (footprint "eagle-import:SD8")
      (libsource (lib "eagle-import") (part "SD8"))
    )
    (comp (ref "L683")
      (value "SD8")
      (footprint "eagle-import:SD8")
      (libsource (lib "eagle-import") (part "SD8"))
    )
    (comp (ref "L684")
      (value "SD8")
      (footprint "eagle-import:SD8")
      (libsource (lib "eagle-import") (part "SD8"))
    )
    (comp (ref "L685")
      (value "SD8")
      (footprint "eagle-import:SD8")
      (libsource (lib "eagle-import") (part "SD8"))
    )
    (comp (ref "L686")
      (value "SD8")
      (footprint "eagle-import:SD8")
      (libsource (lib "eagle-import") (part "SD8"))
    )
    (comp (ref "L687")
      (value "SD8")
      (footprint "eagle-import:SD8")
      (libsource (lib "eagle-import") (part "SD8"))
    )
    (comp (ref "L688")
      (value "SD8")
      (footprint "eagle-import:SD8")
      (libsource (lib "eagle-import") (part "SD8"))
    )
    (comp (ref "L705")
      (value "SD8")
      (footprint "eagle-import:SD8")
      (libsource (lib "eagle-import") (part "SD8"))
    )
    (comp (ref "L706")
      (value "SD8")
      (footprint "eagle-import:SD8")
      (libsource (lib "eagle-import") (part "SD8"))
    )
    (comp (ref "L707")
      (value "SD8")
      (footprint "eagle-import:SD8")
      (libsource (lib "eagle-import") (part "SD8"))
    )
    (comp (ref "L708")
      (value "SD8")
      (footprint "eagle-import:SD8")
      (libsource (lib "eagle-import") (part "SD8"))
    )
    (comp (ref "L709")
      (value "SD8")
      (footprint "eagle-import:SD8")
      (libsource (lib "eagle-import") (part "SD8"))
    )
    (comp (ref "L710")
      (value "SD8")
      (footprint "eagle-import:SD8")
      (libsource (lib "eagle-import") (part "SD8"))
    )
    (comp (ref "L711")
      (value "SD8")
      (footprint "eagle-import:SD8")
      (libsource (lib "eagle-import") (part "SD8"))
    )
    (comp (ref "L712")
      (value "SD8")
      (footprint "eagle-import:SD8")
      (libsource (lib "eagle-import") (part "SD8"))
    )
    (comp (ref "L713")
      (value "SD8")
      (footprint "eagle-import:SD8")
      (libsource (lib "eagle-import") (part "SD8"))
    )
    (comp (ref "L714")
      (value "SD8")
      (footprint "eagle-import:SD8")
      (libsource (lib "eagle-import") (part "SD8"))
    )
    (comp (ref "L715")
      (value "SD8")
      (footprint "eagle-import:SD8")
      (libsource (lib "eagle-import") (part "SD8"))
    )
    (comp (ref "L716")
      (value "SD8")
      (footprint "eagle-import:SD8")
      (libsource (lib "eagle-import") (part "SD8"))
    )
    (comp (ref "L717")
      (value "SD8")
      (footprint "eagle-import:SD8")
      (libsource (lib "eagle-import") (part "SD8"))
    )
    (comp (ref "L718")
      (value "SD8")
      (footprint "eagle-import:SD8")
      (libsource (lib "eagle-import") (part "SD8"))
    )
    (comp (ref "L719")
      (value "SD8")
      (footprint "eagle-import:SD8")
      (libsource (lib "eagle-import") (part "SD8"))
    )
    (comp (ref "L720")
      (value "SD8")
      (footprint "eagle-import:SD8")
      (libsource (lib "eagle-import") (part "SD8"))
    )
    (comp (ref "L737")
      (value "SD8")
      (footprint "eagle-import:SD8")
      (libsource (lib "eagle-import") (part "SD8"))
    )
    (comp (ref "L738")
      (value "SD8")
      (footprint "eagle-import:SD8")
      (libsource (lib "eagle-import") (part "SD8"))
    )
    (comp (ref "L739")
      (value "SD8")
      (footprint "eagle-import:SD8")
      (libsource (lib "eagle-import") (part "SD8"))
    )
    (comp (ref "L740")
      (value "SD8")
      (footprint "eagle-import:SD8")
      (libsource (lib "eagle-import") (part "SD8"))
    )
    (comp (ref "L741")
      (value "SD8")
      (footprint "eagle-import:SD8")
      (libsource (lib "eagle-import") (part "SD8"))
    )
    (comp (ref "L742")
      (value "SD8")
      (footprint "eagle-import:SD8")
      (libsource (lib "eagle-import") (part "SD8"))
    )
    (comp (ref "L743")
      (value "SD8")
      (footprint "eagle-import:SD8")
      (libsource (lib "eagle-import") (part "SD8"))
    )
    (comp (ref "L744")
      (value "SD8")
      (footprint "eagle-import:SD8")
      (libsource (lib "eagle-import") (part "SD8"))
    )
    (comp (ref "L745")
      (value "SD8")
      (footprint "eagle-import:SD8")
      (libsource (lib "eagle-import") (part "SD8"))
    )
    (comp (ref "L746")
      (value "SD8")
      (footprint "eagle-import:SD8")
      (libsource (lib "eagle-import") (part "SD8"))
    )
    (comp (ref "L747")
      (value "SD8")
      (footprint "eagle-import:SD8")
      (libsource (lib "eagle-import") (part "SD8"))
    )
    (comp (ref "L748")
      (value "SD8")
      (footprint "eagle-import:SD8")
      (libsource (lib "eagle-import") (part "SD8"))
    )
    (comp (ref "L749")
      (value "SD8")
      (footprint "eagle-import:SD8")
      (libsource (lib "eagle-import") (part "SD8"))
    )
    (comp (ref "L750")
      (value "SD8")
      (footprint "eagle-import:SD8")
      (libsource (lib "eagle-import") (part "SD8"))
    )
    (comp (ref "L751")
      (value "SD8")
      (footprint "eagle-import:SD8")
      (libsource (lib "eagle-import") (part "SD8"))
    )
    (comp (ref "L752")
      (value "SD8")
      (footprint "eagle-import:SD8")
      (libsource (lib "eagle-import") (part "SD8"))
    )
    (comp (ref "L769")
      (value "SD8")
      (footprint "eagle-import:SD8")
      (libsource (lib "eagle-import") (part "SD8"))
    )
    (comp (ref "L770")
      (value "SD8")
      (footprint "eagle-import:SD8")
      (libsource (lib "eagle-import") (part "SD8"))
    )
    (comp (ref "L771")
      (value "SD8")
      (footprint "eagle-import:SD8")
      (libsource (lib "eagle-import") (part "SD8"))
    )
    (comp (ref "L772")
      (value "SD8")
      (footprint "eagle-import:SD8")
      (libsource (lib "eagle-import") (part "SD8"))
    )
    (comp (ref "L773")
      (value "SD8")
      (footprint "eagle-import:SD8")
      (libsource (lib "eagle-import") (part "SD8"))
    )
    (comp (ref "L774")
      (value "SD8")
      (footprint "eagle-import:SD8")
      (libsource (lib "eagle-import") (part "SD8"))
    )
    (comp (ref "L775")
      (value "SD8")
      (footprint "eagle-import:SD8")
      (libsource (lib "eagle-import") (part "SD8"))
    )
    (comp (ref "L776")
      (value "SD8")
      (footprint "eagle-import:SD8")
      (libsource (lib "eagle-import") (part "SD8"))
    )
    (comp (ref "L777")
      (value "SD8")
      (footprint "eagle-import:SD8")
      (libsource (lib "eagle-import") (part "SD8"))
    )
    (comp (ref "L778")
      (value "SD8")
      (footprint "eagle-import:SD8")
      (libsource (lib "eagle-import") (part "SD8"))
    )
    (comp (ref "L779")
      (value "SD8")
      (footprint "eagle-import:SD8")
      (libsource (lib "eagle-import") (part "SD8"))
    )
    (comp (ref "L780")
      (value "SD8")
      (footprint "eagle-import:SD8")
      (libsource (lib "eagle-import") (part "SD8"))
    )
    (comp (ref "L781")
      (value "SD8")
      (footprint "eagle-import:SD8")
      (libsource (lib "eagle-import") (part "SD8"))
    )
    (comp (ref "L782")
      (value "SD8")
      (footprint "eagle-import:SD8")
      (libsource (lib "eagle-import") (part "SD8"))
    )
    (comp (ref "L783")
      (value "SD8")
      (footprint "eagle-import:SD8")
      (libsource (lib "eagle-import") (part "SD8"))
    )
    (comp (ref "L784")
      (value "SD8")
      (footprint "eagle-import:SD8")
      (libsource (lib "eagle-import") (part "SD8"))
    )
    (comp (ref "L801")
      (value "SD8")
      (footprint "eagle-import:SD8")
      (libsource (lib "eagle-import") (part "SD8"))
    )
    (comp (ref "L802")
      (value "SD8")
      (footprint "eagle-import:SD8")
      (libsource (lib "eagle-import") (part "SD8"))
    )
    (comp (ref "L803")
      (value "SD8")
      (footprint "eagle-import:SD8")
      (libsource (lib "eagle-import") (part "SD8"))
    )
    (comp (ref "L804")
      (value "SD8")
      (footprint "eagle-import:SD8")
      (libsource (lib "eagle-import") (part "SD8"))
    )
    (comp (ref "L805")
      (value "SD8")
      (footprint "eagle-import:SD8")
      (libsource (lib "eagle-import") (part "SD8"))
    )
    (comp (ref "L806")
      (value "SD8")
      (footprint "eagle-import:SD8")
      (libsource (lib "eagle-import") (part "SD8"))
    )
    (comp (ref "L807")
      (value "SD8")
      (footprint "eagle-import:SD8")
      (libsource (lib "eagle-import") (part "SD8"))
    )
    (comp (ref "L808")
      (value "SD8")
      (footprint "eagle-import:SD8")
      (libsource (lib "eagle-import") (part "SD8"))
    )
    (comp (ref "L809")
      (value "SD8")
      (footprint "eagle-import:SD8")
      (libsource (lib "eagle-import") (part "SD8"))
    )
    (comp (ref "L810")
      (value "SD8")
      (footprint "eagle-import:SD8")
      (libsource (lib "eagle-import") (part "SD8"))
    )
    (comp (ref "L811")
      (value "SD8")
      (footprint "eagle-import:SD8")
      (libsource (lib "eagle-import") (part "SD8"))
    )
    (comp (ref "L812")
      (value "SD8")
      (footprint "eagle-import:SD8")
      (libsource (lib "eagle-import") (part "SD8"))
    )
    (comp (ref "L813")
      (value "SD8")
      (footprint "eagle-import:SD8")
      (libsource (lib "eagle-import") (part "SD8"))
    )
    (comp (ref "L814")
      (value "SD8")
      (footprint "eagle-import:SD8")
      (libsource (lib "eagle-import") (part "SD8"))
    )
    (comp (ref "L815")
      (value "SD8")
      (footprint "eagle-import:SD8")
      (libsource (lib "eagle-import") (part "SD8"))
    )
    (comp (ref "L816")
      (value "SD8")
      (footprint "eagle-import:SD8")
      (libsource (lib "eagle-import") (part "SD8"))
    )
    (comp (ref "L833")
      (value "SD8")
      (footprint "eagle-import:SD8")
      (libsource (lib "eagle-import") (part "SD8"))
    )
    (comp (ref "L834")
      (value "SD8")
      (footprint "eagle-import:SD8")
      (libsource (lib "eagle-import") (part "SD8"))
    )
    (comp (ref "L835")
      (value "SD8")
      (footprint "eagle-import:SD8")
      (libsource (lib "eagle-import") (part "SD8"))
    )
    (comp (ref "L836")
      (value "SD8")
      (footprint "eagle-import:SD8")
      (libsource (lib "eagle-import") (part "SD8"))
    )
    (comp (ref "L837")
      (value "SD8")
      (footprint "eagle-import:SD8")
      (libsource (lib "eagle-import") (part "SD8"))
    )
    (comp (ref "L838")
      (value "SD8")
      (footprint "eagle-import:SD8")
      (libsource (lib "eagle-import") (part "SD8"))
    )
    (comp (ref "L839")
      (value "SD8")
      (footprint "eagle-import:SD8")
      (libsource (lib "eagle-import") (part "SD8"))
    )
    (comp (ref "L840")
      (value "SD8")
      (footprint "eagle-import:SD8")
      (libsource (lib "eagle-import") (part "SD8"))
    )
    (comp (ref "L841")
      (value "SD8")
      (footprint "eagle-import:SD8")
      (libsource (lib "eagle-import") (part "SD8"))
    )
    (comp (ref "L842")
      (value "SD8")
      (footprint "eagle-import:SD8")
      (libsource (lib "eagle-import") (part "SD8"))
    )
    (comp (ref "L843")
      (value "SD8")
      (footprint "eagle-import:SD8")
      (libsource (lib "eagle-import") (part "SD8"))
    )
    (comp (ref "L844")
      (value "SD8")
      (footprint "eagle-import:SD8")
      (libsource (lib "eagle-import") (part "SD8"))
    )
    (comp (ref "L845")
      (value "SD8")
      (footprint "eagle-import:SD8")
      (libsource (lib "eagle-import") (part "SD8"))
    )
    (comp (ref "L846")
      (value "SD8")
      (footprint "eagle-import:SD8")
      (libsource (lib "eagle-import") (part "SD8"))
    )
    (comp (ref "L847")
      (value "SD8")
      (footprint "eagle-import:SD8")
      (libsource (lib "eagle-import") (part "SD8"))
    )
    (comp (ref "L848")
      (value "SD8")
      (footprint "eagle-import:SD8")
      (libsource (lib "eagle-import") (part "SD8"))
    )
    (comp (ref "L865")
      (value "SD8")
      (footprint "eagle-import:SD8")
      (libsource (lib "eagle-import") (part "SD8"))
    )
    (comp (ref "L866")
      (value "SD8")
      (footprint "eagle-import:SD8")
      (libsource (lib "eagle-import") (part "SD8"))
    )
    (comp (ref "L867")
      (value "SD8")
      (footprint "eagle-import:SD8")
      (libsource (lib "eagle-import") (part "SD8"))
    )
    (comp (ref "L868")
      (value "SD8")
      (footprint "eagle-import:SD8")
      (libsource (lib "eagle-import") (part "SD8"))
    )
    (comp (ref "L869")
      (value "SD8")
      (footprint "eagle-import:SD8")
      (libsource (lib "eagle-import") (part "SD8"))
    )
    (comp (ref "L870")
      (value "SD8")
      (footprint "eagle-import:SD8")
      (libsource (lib "eagle-import") (part "SD8"))
    )
    (comp (ref "L871")
      (value "SD8")
      (footprint "eagle-import:SD8")
      (libsource (lib "eagle-import") (part "SD8"))
    )
    (comp (ref "L872")
      (value "SD8")
      (footprint "eagle-import:SD8")
      (libsource (lib "eagle-import") (part "SD8"))
    )
    (comp (ref "L873")
      (value "SD8")
      (footprint "eagle-import:SD8")
      (libsource (lib "eagle-import") (part "SD8"))
    )
    (comp (ref "L874")
      (value "SD8")
      (footprint "eagle-import:SD8")
      (libsource (lib "eagle-import") (part "SD8"))
    )
    (comp (ref "L875")
      (value "SD8")
      (footprint "eagle-import:SD8")
      (libsource (lib "eagle-import") (part "SD8"))
    )
    (comp (ref "L876")
      (value "SD8")
      (footprint "eagle-import:SD8")
      (libsource (lib "eagle-import") (part "SD8"))
    )
    (comp (ref "L877")
      (value "SD8")
      (footprint "eagle-import:SD8")
      (libsource (lib "eagle-import") (part "SD8"))
    )
    (comp (ref "L878")
      (value "SD8")
      (footprint "eagle-import:SD8")
      (libsource (lib "eagle-import") (part "SD8"))
    )
    (comp (ref "L879")
      (value "SD8")
      (footprint "eagle-import:SD8")
      (libsource (lib "eagle-import") (part "SD8"))
    )
    (comp (ref "L880")
      (value "SD8")
      (footprint "eagle-import:SD8")
      (libsource (lib "eagle-import") (part "SD8"))
    )
    (comp (ref "L897")
      (value "SD8")
      (footprint "eagle-import:SD8")
      (libsource (lib "eagle-import") (part "SD8"))
    )
    (comp (ref "L898")
      (value "SD8")
      (footprint "eagle-import:SD8")
      (libsource (lib "eagle-import") (part "SD8"))
    )
    (comp (ref "L899")
      (value "SD8")
      (footprint "eagle-import:SD8")
      (libsource (lib "eagle-import") (part "SD8"))
    )
    (comp (ref "L900")
      (value "SD8")
      (footprint "eagle-import:SD8")
      (libsource (lib "eagle-import") (part "SD8"))
    )
    (comp (ref "L901")
      (value "SD8")
      (footprint "eagle-import:SD8")
      (libsource (lib "eagle-import") (part "SD8"))
    )
    (comp (ref "L902")
      (value "SD8")
      (footprint "eagle-import:SD8")
      (libsource (lib "eagle-import") (part "SD8"))
    )
    (comp (ref "L903")
      (value "SD8")
      (footprint "eagle-import:SD8")
      (libsource (lib "eagle-import") (part "SD8"))
    )
    (comp (ref "L904")
      (value "SD8")
      (footprint "eagle-import:SD8")
      (libsource (lib "eagle-import") (part "SD8"))
    )
    (comp (ref "L905")
      (value "SD8")
      (footprint "eagle-import:SD8")
      (libsource (lib "eagle-import") (part "SD8"))
    )
    (comp (ref "L906")
      (value "SD8")
      (footprint "eagle-import:SD8")
      (libsource (lib "eagle-import") (part "SD8"))
    )
    (comp (ref "L907")
      (value "SD8")
      (footprint "eagle-import:SD8")
      (libsource (lib "eagle-import") (part "SD8"))
    )
    (comp (ref "L908")
      (value "SD8")
      (footprint "eagle-import:SD8")
      (libsource (lib "eagle-import") (part "SD8"))
    )
    (comp (ref "L909")
      (value "SD8")
      (footprint "eagle-import:SD8")
      (libsource (lib "eagle-import") (part "SD8"))
    )
    (comp (ref "L910")
      (value "SD8")
      (footprint "eagle-import:SD8")
      (libsource (lib "eagle-import") (part "SD8"))
    )
    (comp (ref "L911")
      (value "SD8")
      (footprint "eagle-import:SD8")
      (libsource (lib "eagle-import") (part "SD8"))
    )
    (comp (ref "L912")
      (value "SD8")
      (footprint "eagle-import:SD8")
      (libsource (lib "eagle-import") (part "SD8"))
    )
    (comp (ref "L929")
      (value "SD8")
      (footprint "eagle-import:SD8")
      (libsource (lib "eagle-import") (part "SD8"))
    )
    (comp (ref "L930")
      (value "SD8")
      (footprint "eagle-import:SD8")
      (libsource (lib "eagle-import") (part "SD8"))
    )
    (comp (ref "L931")
      (value "SD8")
      (footprint "eagle-import:SD8")
      (libsource (lib "eagle-import") (part "SD8"))
    )
    (comp (ref "L932")
      (value "SD8")
      (footprint "eagle-import:SD8")
      (libsource (lib "eagle-import") (part "SD8"))
    )
    (comp (ref "L933")
      (value "SD8")
      (footprint "eagle-import:SD8")
      (libsource (lib "eagle-import") (part "SD8"))
    )
    (comp (ref "L934")
      (value "SD8")
      (footprint "eagle-import:SD8")
      (libsource (lib "eagle-import") (part "SD8"))
    )
    (comp (ref "L935")
      (value "SD8")
      (footprint "eagle-import:SD8")
      (libsource (lib "eagle-import") (part "SD8"))
    )
    (comp (ref "L936")
      (value "SD8")
      (footprint "eagle-import:SD8")
      (libsource (lib "eagle-import") (part "SD8"))
    )
    (comp (ref "L937")
      (value "SD8")
      (footprint "eagle-import:SD8")
      (libsource (lib "eagle-import") (part "SD8"))
    )
    (comp (ref "L938")
      (value "SD8")
      (footprint "eagle-import:SD8")
      (libsource (lib "eagle-import") (part "SD8"))
    )
    (comp (ref "L939")
      (value "SD8")
      (footprint "eagle-import:SD8")
      (libsource (lib "eagle-import") (part "SD8"))
    )
    (comp (ref "L940")
      (value "SD8")
      (footprint "eagle-import:SD8")
      (libsource (lib "eagle-import") (part "SD8"))
    )
    (comp (ref "L941")
      (value "SD8")
      (footprint "eagle-import:SD8")
      (libsource (lib "eagle-import") (part "SD8"))
    )
    (comp (ref "L942")
      (value "SD8")
      (footprint "eagle-import:SD8")
      (libsource (lib "eagle-import") (part "SD8"))
    )
    (comp (ref "L943")
      (value "SD8")
      (footprint "eagle-import:SD8")
      (libsource (lib "eagle-import") (part "SD8"))
    )
    (comp (ref "L944")
      (value "SD8")
      (footprint "eagle-import:SD8")
      (libsource (lib "eagle-import") (part "SD8"))
    )
    (comp (ref "L961")
      (value "SD8")
      (footprint "eagle-import:SD8")
      (libsource (lib "eagle-import") (part "SD8"))
    )
    (comp (ref "L962")
      (value "SD8")
      (footprint "eagle-import:SD8")
      (libsource (lib "eagle-import") (part "SD8"))
    )
    (comp (ref "L963")
      (value "SD8")
      (footprint "eagle-import:SD8")
      (libsource (lib "eagle-import") (part "SD8"))
    )
    (comp (ref "L964")
      (value "SD8")
      (footprint "eagle-import:SD8")
      (libsource (lib "eagle-import") (part "SD8"))
    )
    (comp (ref "L965")
      (value "SD8")
      (footprint "eagle-import:SD8")
      (libsource (lib "eagle-import") (part "SD8"))
    )
    (comp (ref "L966")
      (value "SD8")
      (footprint "eagle-import:SD8")
      (libsource (lib "eagle-import") (part "SD8"))
    )
    (comp (ref "L967")
      (value "SD8")
      (footprint "eagle-import:SD8")
      (libsource (lib "eagle-import") (part "SD8"))
    )
    (comp (ref "L968")
      (value "SD8")
      (footprint "eagle-import:SD8")
      (libsource (lib "eagle-import") (part "SD8"))
    )
    (comp (ref "L969")
      (value "SD8")
      (footprint "eagle-import:SD8")
      (libsource (lib "eagle-import") (part "SD8"))
    )
    (comp (ref "L970")
      (value "SD8")
      (footprint "eagle-import:SD8")
      (libsource (lib "eagle-import") (part "SD8"))
    )
    (comp (ref "L971")
      (value "SD8")
      (footprint "eagle-import:SD8")
      (libsource (lib "eagle-import") (part "SD8"))
    )
    (comp (ref "L972")
      (value "SD8")
      (footprint "eagle-import:SD8")
      (libsource (lib "eagle-import") (part "SD8"))
    )
    (comp (ref "L973")
      (value "SD8")
      (footprint "eagle-import:SD8")
      (libsource (lib "eagle-import") (part "SD8"))
    )
    (comp (ref "L974")
      (value "SD8")
      (footprint "eagle-import:SD8")
      (libsource (lib "eagle-import") (part "SD8"))
    )
    (comp (ref "L975")
      (value "SD8")
      (footprint "eagle-import:SD8")
      (libsource (lib "eagle-import") (part "SD8"))
    )
    (comp (ref "L976")
      (value "SD8")
      (footprint "eagle-import:SD8")
      (libsource (lib "eagle-import") (part "SD8"))
    )
    (comp (ref "L993")
      (value "SD8")
      (footprint "eagle-import:SD8")
      (libsource (lib "eagle-import") (part "SD8"))
    )
    (comp (ref "L994")
      (value "SD8")
      (footprint "eagle-import:SD8")
      (libsource (lib "eagle-import") (part "SD8"))
    )
    (comp (ref "L995")
      (value "SD8")
      (footprint "eagle-import:SD8")
      (libsource (lib "eagle-import") (part "SD8"))
    )
    (comp (ref "L996")
      (value "SD8")
      (footprint "eagle-import:SD8")
      (libsource (lib "eagle-import") (part "SD8"))
    )
    (comp (ref "L997")
      (value "SD8")
      (footprint "eagle-import:SD8")
      (libsource (lib "eagle-import") (part "SD8"))
    )
    (comp (ref "L998")
      (value "SD8")
      (footprint "eagle-import:SD8")
      (libsource (lib "eagle-import") (part "SD8"))
    )
    (comp (ref "L999")
      (value "SD8")
      (footprint "eagle-import:SD8")
      (libsource (lib "eagle-import") (part "SD8"))
    )
    (comp (ref "L1000")
      (value "SD8")
      (footprint "eagle-import:SD8")
      (libsource (lib "eagle-import") (part "SD8"))
    )
    (comp (ref "L1001")
      (value "SD8")
      (footprint "eagle-import:SD8")
      (libsource (lib "eagle-import") (part "SD8"))
    )
    (comp (ref "L1002")
      (value "SD8")
      (footprint "eagle-import:SD8")
      (libsource (lib "eagle-import") (part "SD8"))
    )
    (comp (ref "L1003")
      (value "SD8")
      (footprint "eagle-import:SD8")
      (libsource (lib "eagle-import") (part "SD8"))
    )
    (comp (ref "L1004")
      (value "SD8")
      (footprint "eagle-import:SD8")
      (libsource (lib "eagle-import") (part "SD8"))
    )
    (comp (ref "L1005")
      (value "SD8")
      (footprint "eagle-import:SD8")
      (libsource (lib "eagle-import") (part "SD8"))
    )
    (comp (ref "L1006")
      (value "SD8")
      (footprint "eagle-import:SD8")
      (libsource (lib "eagle-import") (part "SD8"))
    )
    (comp (ref "L1007")
      (value "SD8")
      (footprint "eagle-import:SD8")
      (libsource (lib "eagle-import") (part "SD8"))
    )
    (comp (ref "L1008")
      (value "SD8")
      (footprint "eagle-import:SD8")
      (libsource (lib "eagle-import") (part "SD8"))
    )
    (comp (ref "IC14")
      (value "4514D")
      (footprint "eagle-import:SO24W")
      (libsource (lib "eagle-import") (part "4514D"))
    )
    (comp (ref "IC15")
      (value "TBD62783AFG")
      (footprint "eagle-import:SOIC127P1030X245-18N")
      (libsource (lib "eagle-import") (part "TBD62783AFG"))
    )
    (comp (ref "IC16")
      (value "TBD62083AFG")
      (footprint "eagle-import:SOIC127P1030X245-18N")
      (libsource (lib "eagle-import") (part "TBD62083AFG"))
    )
    (comp (ref "IC17")
      (value "4514D")
      (footprint "eagle-import:SO24W")
      (libsource (lib "eagle-import") (part "4514D"))
    )
    (comp (ref "IC18")
      (value "TBD62783AFG")
      (footprint "eagle-import:SOIC127P1030X245-18N")
      (libsource (lib "eagle-import") (part "TBD62783AFG"))
    )
    (comp (ref "IC19")
      (value "TBD62083AFG")
      (footprint "eagle-import:SOIC127P1030X245-18N")
      (libsource (lib "eagle-import") (part "TBD62083AFG"))
    )
    (comp (ref "IC20")
      (value "4514D")
      (footprint "eagle-import:SO24W")
      (libsource (lib "eagle-import") (part "4514D"))
    )
    (comp (ref "IC21")
      (value "TBD62783AFG")
      (footprint "eagle-import:SOIC127P1030X245-18N")
      (libsource (lib "eagle-import") (part "TBD62783AFG"))
    )
    (comp (ref "IC22")
      (value "TBD62083AFG")
      (footprint "eagle-import:SOIC127P1030X245-18N")
      (libsource (lib "eagle-import") (part "TBD62083AFG"))
    )
    (comp (ref "IC23")
      (value "4514D")
      (footprint "eagle-import:SO24W")
      (libsource (lib "eagle-import") (part "4514D"))
    )
    (comp (ref "IC24")
      (value "TBD62783AFG")
      (footprint "eagle-import:SOIC127P1030X245-18N")
      (libsource (lib "eagle-import") (part "TBD62783AFG"))
    )
    (comp (ref "IC25")
      (value "TBD62083AFG")
      (footprint "eagle-import:SOIC127P1030X245-18N")
      (libsource (lib "eagle-import") (part "TBD62083AFG"))
    )
    (comp (ref "IC5")
      (value "4514D")
      (footprint "eagle-import:SO24W")
      (libsource (lib "eagle-import") (part "4514D"))
    )
    (comp (ref "IC6")
      (value "TBD62083AFG")
      (footprint "eagle-import:SOIC127P1030X245-18N")
      (libsource (lib "eagle-import") (part "TBD62083AFG"))
    )
    (comp (ref "IC7")
      (value "TBD62783AFG")
      (footprint "eagle-import:SOIC127P1030X245-18N")
      (libsource (lib "eagle-import") (part "TBD62783AFG"))
    )
    (comp (ref "IC8")
      (value "4514D")
      (footprint "eagle-import:SO24W")
      (libsource (lib "eagle-import") (part "4514D"))
    )
    (comp (ref "IC9")
      (value "TBD62083AFG")
      (footprint "eagle-import:SOIC127P1030X245-18N")
      (libsource (lib "eagle-import") (part "TBD62083AFG"))
    )
    (comp (ref "IC10")
      (value "TBD62783AFG")
      (footprint "eagle-import:SOIC127P1030X245-18N")
      (libsource (lib "eagle-import") (part "TBD62783AFG"))
    )
    (comp (ref "IC11")
      (value "4514D")
      (footprint "eagle-import:SO24W")
      (libsource (lib "eagle-import") (part "4514D"))
    )
    (comp (ref "IC12")
      (value "TBD62783AFG")
      (footprint "eagle-import:SOIC127P1030X245-18N")
      (libsource (lib "eagle-import") (part "TBD62783AFG"))
    )
    (comp (ref "IC13")
      (value "TBD62083AFG")
      (footprint "eagle-import:SOIC127P1030X245-18N")
      (libsource (lib "eagle-import") (part "TBD62083AFG"))
    )
    (comp (ref "IC26")
      (value "4514D")
      (footprint "eagle-import:SO24W")
      (libsource (lib "eagle-import") (part "4514D"))
    )
    (comp (ref "IC27")
      (value "TBD62783AFG")
      (footprint "eagle-import:SOIC127P1030X245-18N")
      (libsource (lib "eagle-import") (part "TBD62783AFG"))
    )
    (comp (ref "IC28")
      (value "TBD62083AFG")
      (footprint "eagle-import:SOIC127P1030X245-18N")
      (libsource (lib "eagle-import") (part "TBD62083AFG"))
    )
  )
  (nets
    (net (code "1") (name "+5V") (class "Default")
      (node (ref "IC1") (pin "5") (pinfunction "VCC_5") (pintype "power_in"))
      (node (ref "IC11") (pin "24") (pinfunction "VDD_24") (pintype "power_in"))
      (node (ref "IC14") (pin "24") (pinfunction "VDD_24") (pintype "power_in"))
      (node (ref "IC17") (pin "24") (pinfunction "VDD_24") (pintype "power_in"))
      (node (ref "IC2") (pin "14") (pinfunction "VDD_14") (pintype "power_in"))
      (node (ref "IC20") (pin "24") (pinfunction "VDD_24") (pintype "power_in"))
      (node (ref "IC23") (pin "24") (pinfunction "VDD_24") (pintype "power_in"))
      (node (ref "IC26") (pin "24") (pinfunction "VDD_24") (pintype "power_in"))
      (node (ref "IC3") (pin "16") (pinfunction "VCC_16") (pintype "power_in"))
      (node (ref "IC4") (pin "14") (pinfunction "VDD_14") (pintype "power_in"))
      (node (ref "IC5") (pin "24") (pinfunction "VDD_24") (pintype "power_in"))
      (node (ref "IC8") (pin "24") (pinfunction "VDD_24") (pintype "power_in"))
    )
    (net (code "2") (name "5V") (class "Default")
      (node (ref "CONN1") (pin "11") (pinfunction "11_11") (pintype "passive"))
      (node (ref "CONN2") (pin "11") (pinfunction "11_11") (pintype "passive"))
      (node (ref "IC11") (pin "1") (pinfunction "ST_1") (pintype "input"))
      (node (ref "IC14") (pin "1") (pinfunction "ST_1") (pintype "input"))
      (node (ref "IC17") (pin "1") (pinfunction "ST_1") (pintype "input"))
      (node (ref "IC20") (pin "1") (pinfunction "ST_1") (pintype "input"))
      (node (ref "IC23") (pin "1") (pinfunction "ST_1") (pintype "input"))
      (node (ref "IC26") (pin "1") (pinfunction "ST_1") (pintype "input"))
      (node (ref "IC5") (pin "1") (pinfunction "ST_1") (pintype "input"))
      (node (ref "IC8") (pin "1") (pinfunction "ST_1") (pintype "input"))
    )
    (net (code "3") (name "18V_PULSE_1") (class "Default")
      (node (ref "CONN1") (pin "12") (pinfunction "12_12") (pintype "passive"))
      (node (ref "CONN1") (pin "13") (pinfunction "13_13") (pintype "passive"))
      (node (ref "CONN2") (pin "12") (pinfunction "12_12") (pintype "passive"))
      (node (ref "CONN2") (pin "13") (pinfunction "13_13") (pintype "passive"))
      (node (ref "IC10") (pin "9") (pinfunction "VCC_9") (pintype "power_in"))
      (node (ref "IC12") (pin "9") (pinfunction "VCC_9") (pintype "power_in"))
      (node (ref "IC13") (pin "10") (pinfunction "CD+_10") (pintype "passive"))
      (node (ref "IC15") (pin "9") (pinfunction "VCC_9") (pintype "power_in"))
      (node (ref "IC18") (pin "9") (pinfunction "VCC_9") (pintype "power_in"))
      (node (ref "IC21") (pin "9") (pinfunction "VCC_9") (pintype "power_in"))
      (node (ref "IC24") (pin "9") (pinfunction "VCC_9") (pintype "power_in"))
      (node (ref "IC27") (pin "9") (pinfunction "VCC_9") (pintype "power_in"))
      (node (ref "IC28") (pin "10") (pinfunction "CD+_10") (pintype "passive"))
      (node (ref "IC6") (pin "10") (pinfunction "CD+_10") (pintype "passive"))
      (node (ref "IC7") (pin "9") (pinfunction "VCC_9") (pintype "power_in"))
      (node (ref "IC9") (pin "10") (pinfunction "CD+_10") (pintype "passive"))
    )
    (net (code "4") (name "18V_PULSE_2") (class "Default")
      (node (ref "CONN1") (pin "14") (pinfunction "14_14") (pintype "passive"))
      (node (ref "CONN2") (pin "14") (pinfunction "14_14") (pintype "passive"))
      (node (ref "IC16") (pin "10") (pinfunction "CD+_10") (pintype "passive"))
      (node (ref "IC19") (pin "10") (pinfunction "CD+_10") (pintype "passive"))
      (node (ref "IC22") (pin "10") (pinfunction "CD+_10") (pintype "passive"))
      (node (ref "IC25") (pin "10") (pinfunction "CD+_10") (pintype "passive"))
    )
    (net (code "5") (name "COL1") (class "Default")
      (node (ref "IC15") (pin "18") (pinfunction "O1_18") (pintype "open_collector"))
      (node (ref "IC16") (pin "18") (pinfunction "O1_18") (pintype "open_collector"))
      (node (ref "L1") (pin "2") (pinfunction "2_2") (pintype "passive"))
      (node (ref "L129") (pin "2") (pinfunction "2_2") (pintype "passive"))
      (node (ref "L161") (pin "2") (pinfunction "2_2") (pintype "passive"))
      (node (ref "L193") (pin "2") (pinfunction "2_2") (pintype "passive"))
      (node (ref "L225") (pin "2") (pinfunction "2_2") (pintype "passive"))
      (node (ref "L257") (pin "2") (pinfunction "2_2") (pintype "passive"))
      (node (ref "L289") (pin "2") (pinfunction "2_2") (pintype "passive"))
      (node (ref "L321") (pin "2") (pinfunction "2_2") (pintype "passive"))
      (node (ref "L33") (pin "2") (pinfunction "2_2") (pintype "passive"))
      (node (ref "L353") (pin "2") (pinfunction "2_2") (pintype "passive"))
      (node (ref "L385") (pin "2") (pinfunction "2_2") (pintype "passive"))
      (node (ref "L417") (pin "2") (pinfunction "2_2") (pintype "passive"))
      (node (ref "L449") (pin "2") (pinfunction "2_2") (pintype "passive"))
      (node (ref "L481") (pin "2") (pinfunction "2_2") (pintype "passive"))
      (node (ref "L513") (pin "2") (pinfunction "2_2") (pintype "passive"))
      (node (ref "L545") (pin "2") (pinfunction "2_2") (pintype "passive"))
      (node (ref "L577") (pin "2") (pinfunction "2_2") (pintype "passive"))
      (node (ref "L609") (pin "2") (pinfunction "2_2") (pintype "passive"))
      (node (ref "L641") (pin "2") (pinfunction "2_2") (pintype "passive"))
      (node (ref "L65") (pin "2") (pinfunction "2_2") (pintype "passive"))
      (node (ref "L673") (pin "2") (pinfunction "2_2") (pintype "passive"))
      (node (ref "L705") (pin "2") (pinfunction "2_2") (pintype "passive"))
      (node (ref "L737") (pin "2") (pinfunction "2_2") (pintype "passive"))
      (node (ref "L769") (pin "2") (pinfunction "2_2") (pintype "passive"))
      (node (ref "L801") (pin "2") (pinfunction "2_2") (pintype "passive"))
      (node (ref "L833") (pin "2") (pinfunction "2_2") (pintype "passive"))
      (node (ref "L865") (pin "2") (pinfunction "2_2") (pintype "passive"))
      (node (ref "L897") (pin "2") (pinfunction "2_2") (pintype "passive"))
      (node (ref "L929") (pin "2") (pinfunction "2_2") (pintype "passive"))
      (node (ref "L961") (pin "2") (pinfunction "2_2") (pintype "passive"))
      (node (ref "L97") (pin "2") (pinfunction "2_2") (pintype "passive"))
      (node (ref "L993") (pin "2") (pinfunction "2_2") (pintype "passive"))
    )
    (net (code "6") (name "COL1-8_INHIBIT") (class "Default")
      (node (ref "IC14") (pin "23") (pinfunction "INH_23") (pintype "input"))
      (node (ref "IC3") (pin "12") (pinfunction "Y0_12") (pintype "output"))
    )
    (net (code "7") (name "COL2") (class "Default")
      (node (ref "IC15") (pin "17") (pinfunction "O2_17") (pintype "open_collector"))
      (node (ref "IC16") (pin "17") (pinfunction "O2_17") (pintype "open_collector"))
      (node (ref "L130") (pin "2") (pinfunction "2_2") (pintype "passive"))
      (node (ref "L162") (pin "2") (pinfunction "2_2") (pintype "passive"))
      (node (ref "L194") (pin "2") (pinfunction "2_2") (pintype "passive"))
      (node (ref "L2") (pin "2") (pinfunction "2_2") (pintype "passive"))
      (node (ref "L226") (pin "2") (pinfunction "2_2") (pintype "passive"))
      (node (ref "L258") (pin "2") (pinfunction "2_2") (pintype "passive"))
      (node (ref "L290") (pin "2") (pinfunction "2_2") (pintype "passive"))
      (node (ref "L322") (pin "2") (pinfunction "2_2") (pintype "passive"))
      (node (ref "L34") (pin "2") (pinfunction "2_2") (pintype "passive"))
      (node (ref "L354") (pin "2") (pinfunction "2_2") (pintype "passive"))
      (node (ref "L386") (pin "2") (pinfunction "2_2") (pintype "passive"))
      (node (ref "L418") (pin "2") (pinfunction "2_2") (pintype "passive"))
      (node (ref "L450") (pin "2") (pinfunction "2_2") (pintype "passive"))
      (node (ref "L482") (pin "2") (pinfunction "2_2") (pintype "passive"))
      (node (ref "L514") (pin "2") (pinfunction "2_2") (pintype "passive"))
      (node (ref "L546") (pin "2") (pinfunction "2_2") (pintype "passive"))
      (node (ref "L578") (pin "2") (pinfunction "2_2") (pintype "passive"))
      (node (ref "L610") (pin "2") (pinfunction "2_2") (pintype "passive"))
      (node (ref "L642") (pin "2") (pinfunction "2_2") (pintype "passive"))
      (node (ref "L66") (pin "2") (pinfunction "2_2") (pintype "passive"))
      (node (ref "L674") (pin "2") (pinfunction "2_2") (pintype "passive"))
      (node (ref "L706") (pin "2") (pinfunction "2_2") (pintype "passive"))
      (node (ref "L738") (pin "2") (pinfunction "2_2") (pintype "passive"))
      (node (ref "L770") (pin "2") (pinfunction "2_2") (pintype "passive"))
      (node (ref "L802") (pin "2") (pinfunction "2_2") (pintype "passive"))
      (node (ref "L834") (pin "2") (pinfunction "2_2") (pintype "passive"))
      (node (ref "L866") (pin "2") (pinfunction "2_2") (pintype "passive"))
      (node (ref "L898") (pin "2") (pinfunction "2_2") (pintype "passive"))
      (node (ref "L930") (pin "2") (pinfunction "2_2") (pintype "passive"))
      (node (ref "L962") (pin "2") (pinfunction "2_2") (pintype "passive"))
      (node (ref "L98") (pin "2") (pinfunction "2_2") (pintype "passive"))
      (node (ref "L994") (pin "2") (pinfunction "2_2") (pintype "passive"))
    )
    (net (code "8") (name "COL3") (class "Default")
      (node (ref "IC15") (pin "16") (pinfunction "O3_16") (pintype "open_collector"))
      (node (ref "IC16") (pin "16") (pinfunction "O3_16") (pintype "open_collector"))
      (node (ref "L131") (pin "2") (pinfunction "2_2") (pintype "passive"))
      (node (ref "L163") (pin "2") (pinfunction "2_2") (pintype "passive"))
      (node (ref "L195") (pin "2") (pinfunction "2_2") (pintype "passive"))
      (node (ref "L227") (pin "2") (pinfunction "2_2") (pintype "passive"))
      (node (ref "L259") (pin "2") (pinfunction "2_2") (pintype "passive"))
      (node (ref "L291") (pin "2") (pinfunction "2_2") (pintype "passive"))
      (node (ref "L3") (pin "2") (pinfunction "2_2") (pintype "passive"))
      (node (ref "L323") (pin "2") (pinfunction "2_2") (pintype "passive"))
      (node (ref "L35") (pin "2") (pinfunction "2_2") (pintype "passive"))
      (node (ref "L355") (pin "2") (pinfunction "2_2") (pintype "passive"))
      (node (ref "L387") (pin "2") (pinfunction "2_2") (pintype "passive"))
      (node (ref "L419") (pin "2") (pinfunction "2_2") (pintype "passive"))
      (node (ref "L451") (pin "2") (pinfunction "2_2") (pintype "passive"))
      (node (ref "L483") (pin "2") (pinfunction "2_2") (pintype "passive"))
      (node (ref "L515") (pin "2") (pinfunction "2_2") (pintype "passive"))
      (node (ref "L547") (pin "2") (pinfunction "2_2") (pintype "passive"))
      (node (ref "L579") (pin "2") (pinfunction "2_2") (pintype "passive"))
      (node (ref "L611") (pin "2") (pinfunction "2_2") (pintype "passive"))
      (node (ref "L643") (pin "2") (pinfunction "2_2") (pintype "passive"))
      (node (ref "L67") (pin "2") (pinfunction "2_2") (pintype "passive"))
      (node (ref "L675") (pin "2") (pinfunction "2_2") (pintype "passive"))
      (node (ref "L707") (pin "2") (pinfunction "2_2") (pintype "passive"))
      (node (ref "L739") (pin "2") (pinfunction "2_2") (pintype "passive"))
      (node (ref "L771") (pin "2") (pinfunction "2_2") (pintype "passive"))
      (node (ref "L803") (pin "2") (pinfunction "2_2") (pintype "passive"))
      (node (ref "L835") (pin "2") (pinfunction "2_2") (pintype "passive"))
      (node (ref "L867") (pin "2") (pinfunction "2_2") (pintype "passive"))
      (node (ref "L899") (pin "2") (pinfunction "2_2") (pintype "passive"))
      (node (ref "L931") (pin "2") (pinfunction "2_2") (pintype "passive"))
      (node (ref "L963") (pin "2") (pinfunction "2_2") (pintype "passive"))
      (node (ref "L99") (pin "2") (pinfunction "2_2") (pintype "passive"))
      (node (ref "L995") (pin "2") (pinfunction "2_2") (pintype "passive"))
    )
    (net (code "9") (name "COL4") (class "Default")
      (node (ref "IC15") (pin "15") (pinfunction "O4_15") (pintype "open_collector"))
      (node (ref "IC16") (pin "15") (pinfunction "O4_15") (pintype "open_collector"))
      (node (ref "L100") (pin "2") (pinfunction "2_2") (pintype "passive"))
      (node (ref "L132") (pin "2") (pinfunction "2_2") (pintype "passive"))
      (node (ref "L164") (pin "2") (pinfunction "2_2") (pintype "passive"))
      (node (ref "L196") (pin "2") (pinfunction "2_2") (pintype "passive"))
      (node (ref "L228") (pin "2") (pinfunction "2_2") (pintype "passive"))
      (node (ref "L260") (pin "2") (pinfunction "2_2") (pintype "passive"))
      (node (ref "L292") (pin "2") (pinfunction "2_2") (pintype "passive"))
      (node (ref "L324") (pin "2") (pinfunction "2_2") (pintype "passive"))
      (node (ref "L356") (pin "2") (pinfunction "2_2") (pintype "passive"))
      (node (ref "L36") (pin "2") (pinfunction "2_2") (pintype "passive"))
      (node (ref "L388") (pin "2") (pinfunction "2_2") (pintype "passive"))
      (node (ref "L4") (pin "2") (pinfunction "2_2") (pintype "passive"))
      (node (ref "L420") (pin "2") (pinfunction "2_2") (pintype "passive"))
      (node (ref "L452") (pin "2") (pinfunction "2_2") (pintype "passive"))
      (node (ref "L484") (pin "2") (pinfunction "2_2") (pintype "passive"))
      (node (ref "L516") (pin "2") (pinfunction "2_2") (pintype "passive"))
      (node (ref "L548") (pin "2") (pinfunction "2_2") (pintype "passive"))
      (node (ref "L580") (pin "2") (pinfunction "2_2") (pintype "passive"))
      (node (ref "L612") (pin "2") (pinfunction "2_2") (pintype "passive"))
      (node (ref "L644") (pin "2") (pinfunction "2_2") (pintype "passive"))
      (node (ref "L676") (pin "2") (pinfunction "2_2") (pintype "passive"))
      (node (ref "L68") (pin "2") (pinfunction "2_2") (pintype "passive"))
      (node (ref "L708") (pin "2") (pinfunction "2_2") (pintype "passive"))
      (node (ref "L740") (pin "2") (pinfunction "2_2") (pintype "passive"))
      (node (ref "L772") (pin "2") (pinfunction "2_2") (pintype "passive"))
      (node (ref "L804") (pin "2") (pinfunction "2_2") (pintype "passive"))
      (node (ref "L836") (pin "2") (pinfunction "2_2") (pintype "passive"))
      (node (ref "L868") (pin "2") (pinfunction "2_2") (pintype "passive"))
      (node (ref "L900") (pin "2") (pinfunction "2_2") (pintype "passive"))
      (node (ref "L932") (pin "2") (pinfunction "2_2") (pintype "passive"))
      (node (ref "L964") (pin "2") (pinfunction "2_2") (pintype "passive"))
      (node (ref "L996") (pin "2") (pinfunction "2_2") (pintype "passive"))
    )
    (net (code "10") (name "COL5") (class "Default")
      (node (ref "IC15") (pin "14") (pinfunction "O5_14") (pintype "open_collector"))
      (node (ref "IC16") (pin "14") (pinfunction "O5_14") (pintype "open_collector"))
      (node (ref "L101") (pin "2") (pinfunction "2_2") (pintype "passive"))
      (node (ref "L133") (pin "2") (pinfunction "2_2") (pintype "passive"))
      (node (ref "L165") (pin "2") (pinfunction "2_2") (pintype "passive"))
      (node (ref "L197") (pin "2") (pinfunction "2_2") (pintype "passive"))
      (node (ref "L229") (pin "2") (pinfunction "2_2") (pintype "passive"))
      (node (ref "L261") (pin "2") (pinfunction "2_2") (pintype "passive"))
      (node (ref "L293") (pin "2") (pinfunction "2_2") (pintype "passive"))
      (node (ref "L325") (pin "2") (pinfunction "2_2") (pintype "passive"))
      (node (ref "L357") (pin "2") (pinfunction "2_2") (pintype "passive"))
      (node (ref "L37") (pin "2") (pinfunction "2_2") (pintype "passive"))
      (node (ref "L389") (pin "2") (pinfunction "2_2") (pintype "passive"))
      (node (ref "L421") (pin "2") (pinfunction "2_2") (pintype "passive"))
      (node (ref "L453") (pin "2") (pinfunction "2_2") (pintype "passive"))
      (node (ref "L485") (pin "2") (pinfunction "2_2") (pintype "passive"))
      (node (ref "L5") (pin "2") (pinfunction "2_2") (pintype "passive"))
      (node (ref "L517") (pin "2") (pinfunction "2_2") (pintype "passive"))
      (node (ref "L549") (pin "2") (pinfunction "2_2") (pintype "passive"))
      (node (ref "L581") (pin "2") (pinfunction "2_2") (pintype "passive"))
      (node (ref "L613") (pin "2") (pinfunction "2_2") (pintype "passive"))
      (node (ref "L645") (pin "2") (pinfunction "2_2") (pintype "passive"))
      (node (ref "L677") (pin "2") (pinfunction "2_2") (pintype "passive"))
      (node (ref "L69") (pin "2") (pinfunction "2_2") (pintype "passive"))
      (node (ref "L709") (pin "2") (pinfunction "2_2") (pintype "passive"))
      (node (ref "L741") (pin "2") (pinfunction "2_2") (pintype "passive"))
      (node (ref "L773") (pin "2") (pinfunction "2_2") (pintype "passive"))
      (node (ref "L805") (pin "2") (pinfunction "2_2") (pintype "passive"))
      (node (ref "L837") (pin "2") (pinfunction "2_2") (pintype "passive"))
      (node (ref "L869") (pin "2") (pinfunction "2_2") (pintype "passive"))
      (node (ref "L901") (pin "2") (pinfunction "2_2") (pintype "passive"))
      (node (ref "L933") (pin "2") (pinfunction "2_2") (pintype "passive"))
      (node (ref "L965") (pin "2") (pinfunction "2_2") (pintype "passive"))
      (node (ref "L997") (pin "2") (pinfunction "2_2") (pintype "passive"))
    )
    (net (code "11") (name "COL6") (class "Default")
      (node (ref "IC15") (pin "13") (pinfunction "O6_13") (pintype "open_collector"))
      (node (ref "IC16") (pin "13") (pinfunction "O6_13") (pintype "open_collector"))
      (node (ref "L102") (pin "2") (pinfunction "2_2") (pintype "passive"))
      (node (ref "L134") (pin "2") (pinfunction "2_2") (pintype "passive"))
      (node (ref "L166") (pin "2") (pinfunction "2_2") (pintype "passive"))
      (node (ref "L198") (pin "2") (pinfunction "2_2") (pintype "passive"))
      (node (ref "L230") (pin "2") (pinfunction "2_2") (pintype "passive"))
      (node (ref "L262") (pin "2") (pinfunction "2_2") (pintype "passive"))
      (node (ref "L294") (pin "2") (pinfunction "2_2") (pintype "passive"))
      (node (ref "L326") (pin "2") (pinfunction "2_2") (pintype "passive"))
      (node (ref "L358") (pin "2") (pinfunction "2_2") (pintype "passive"))
      (node (ref "L38") (pin "2") (pinfunction "2_2") (pintype "passive"))
      (node (ref "L390") (pin "2") (pinfunction "2_2") (pintype "passive"))
      (node (ref "L422") (pin "2") (pinfunction "2_2") (pintype "passive"))
      (node (ref "L454") (pin "2") (pinfunction "2_2") (pintype "passive"))
      (node (ref "L486") (pin "2") (pinfunction "2_2") (pintype "passive"))
      (node (ref "L518") (pin "2") (pinfunction "2_2") (pintype "passive"))
      (node (ref "L550") (pin "2") (pinfunction "2_2") (pintype "passive"))
      (node (ref "L582") (pin "2") (pinfunction "2_2") (pintype "passive"))
      (node (ref "L6") (pin "2") (pinfunction "2_2") (pintype "passive"))
      (node (ref "L614") (pin "2") (pinfunction "2_2") (pintype "passive"))
      (node (ref "L646") (pin "2") (pinfunction "2_2") (pintype "passive"))
      (node (ref "L678") (pin "2") (pinfunction "2_2") (pintype "passive"))
      (node (ref "L70") (pin "2") (pinfunction "2_2") (pintype "passive"))
      (node (ref "L710") (pin "2") (pinfunction "2_2") (pintype "passive"))
      (node (ref "L742") (pin "2") (pinfunction "2_2") (pintype "passive"))
      (node (ref "L774") (pin "2") (pinfunction "2_2") (pintype "passive"))
      (node (ref "L806") (pin "2") (pinfunction "2_2") (pintype "passive"))
      (node (ref "L838") (pin "2") (pinfunction "2_2") (pintype "passive"))
      (node (ref "L870") (pin "2") (pinfunction "2_2") (pintype "passive"))
      (node (ref "L902") (pin "2") (pinfunction "2_2") (pintype "passive"))
      (node (ref "L934") (pin "2") (pinfunction "2_2") (pintype "passive"))
      (node (ref "L966") (pin "2") (pinfunction "2_2") (pintype "passive"))
      (node (ref "L998") (pin "2") (pinfunction "2_2") (pintype "passive"))
    )
    (net (code "12") (name "COL7") (class "Default")
      (node (ref "IC15") (pin "12") (pinfunction "O7_12") (pintype "open_collector"))
      (node (ref "IC16") (pin "12") (pinfunction "O7_12") (pintype "open_collector"))
      (node (ref "L103") (pin "2") (pinfunction "2_2") (pintype "passive"))
      (node (ref "L135") (pin "2") (pinfunction "2_2") (pintype "passive"))
      (node (ref "L167") (pin "2") (pinfunction "2_2") (pintype "passive"))
      (node (ref "L199") (pin "2") (pinfunction "2_2") (pintype "passive"))
      (node (ref "L231") (pin "2") (pinfunction "2_2") (pintype "passive"))
      (node (ref "L263") (pin "2") (pinfunction "2_2") (pintype "passive"))
      (node (ref "L295") (pin "2") (pinfunction "2_2") (pintype "passive"))
      (node (ref "L327") (pin "2") (pinfunction "2_2") (pintype "passive"))
      (node (ref "L359") (pin "2") (pinfunction "2_2") (pintype "passive"))
      (node (ref "L39") (pin "2") (pinfunction "2_2") (pintype "passive"))
      (node (ref "L391") (pin "2") (pinfunction "2_2") (pintype "passive"))
      (node (ref "L423") (pin "2") (pinfunction "2_2") (pintype "passive"))
      (node (ref "L455") (pin "2") (pinfunction "2_2") (pintype "passive"))
      (node (ref "L487") (pin "2") (pinfunction "2_2") (pintype "passive"))
      (node (ref "L519") (pin "2") (pinfunction "2_2") (pintype "passive"))
      (node (ref "L551") (pin "2") (pinfunction "2_2") (pintype "passive"))
      (node (ref "L583") (pin "2") (pinfunction "2_2") (pintype "passive"))
      (node (ref "L615") (pin "2") (pinfunction "2_2") (pintype "passive"))
      (node (ref "L647") (pin "2") (pinfunction "2_2") (pintype "passive"))
      (node (ref "L679") (pin "2") (pinfunction "2_2") (pintype "passive"))
      (node (ref "L7") (pin "2") (pinfunction "2_2") (pintype "passive"))
      (node (ref "L71") (pin "2") (pinfunction "2_2") (pintype "passive"))
      (node (ref "L711") (pin "2") (pinfunction "2_2") (pintype "passive"))
      (node (ref "L743") (pin "2") (pinfunction "2_2") (pintype "passive"))
      (node (ref "L775") (pin "2") (pinfunction "2_2") (pintype "passive"))
      (node (ref "L807") (pin "2") (pinfunction "2_2") (pintype "passive"))
      (node (ref "L839") (pin "2") (pinfunction "2_2") (pintype "passive"))
      (node (ref "L871") (pin "2") (pinfunction "2_2") (pintype "passive"))
      (node (ref "L903") (pin "2") (pinfunction "2_2") (pintype "passive"))
      (node (ref "L935") (pin "2") (pinfunction "2_2") (pintype "passive"))
      (node (ref "L967") (pin "2") (pinfunction "2_2") (pintype "passive"))
      (node (ref "L999") (pin "2") (pinfunction "2_2") (pintype "passive"))
    )
    (net (code "13") (name "COL8") (class "Default")
      (node (ref "IC15") (pin "11") (pinfunction "O8_11") (pintype "open_collector"))
      (node (ref "IC16") (pin "11") (pinfunction "O8_11") (pintype "open_collector"))
      (node (ref "L1000") (pin "2") (pinfunction "2_2") (pintype "passive"))
      (node (ref "L104") (pin "2") (pinfunction "2_2") (pintype "passive"))
      (node (ref "L136") (pin "2") (pinfunction "2_2") (pintype "passive"))
      (node (ref "L168") (pin "2") (pinfunction "2_2") (pintype "passive"))
      (node (ref "L200") (pin "2") (pinfunction "2_2") (pintype "passive"))
      (node (ref "L232") (pin "2") (pinfunction "2_2") (pintype "passive"))
      (node (ref "L264") (pin "2") (pinfunction "2_2") (pintype "passive"))
      (node (ref "L296") (pin "2") (pinfunction "2_2") (pintype "passive"))
      (node (ref "L328") (pin "2") (pinfunction "2_2") (pintype "passive"))
      (node (ref "L360") (pin "2") (pinfunction "2_2") (pintype "passive"))
      (node (ref "L392") (pin "2") (pinfunction "2_2") (pintype "passive"))
      (node (ref "L40") (pin "2") (pinfunction "2_2") (pintype "passive"))
      (node (ref "L424") (pin "2") (pinfunction "2_2") (pintype "passive"))
      (node (ref "L456") (pin "2") (pinfunction "2_2") (pintype "passive"))
      (node (ref "L488") (pin "2") (pinfunction "2_2") (pintype "passive"))
      (node (ref "L520") (pin "2") (pinfunction "2_2") (pintype "passive"))
      (node (ref "L552") (pin "2") (pinfunction "2_2") (pintype "passive"))
      (node (ref "L584") (pin "2") (pinfunction "2_2") (pintype "passive"))
      (node (ref "L616") (pin "2") (pinfunction "2_2") (pintype "passive"))
      (node (ref "L648") (pin "2") (pinfunction "2_2") (pintype "passive"))
      (node (ref "L680") (pin "2") (pinfunction "2_2") (pintype "passive"))
      (node (ref "L712") (pin "2") (pinfunction "2_2") (pintype "passive"))
      (node (ref "L72") (pin "2") (pinfunction "2_2") (pintype "passive"))
      (node (ref "L744") (pin "2") (pinfunction "2_2") (pintype "passive"))
      (node (ref "L776") (pin "2") (pinfunction "2_2") (pintype "passive"))
      (node (ref "L8") (pin "2") (pinfunction "2_2") (pintype "passive"))
      (node (ref "L808") (pin "2") (pinfunction "2_2") (pintype "passive"))
      (node (ref "L840") (pin "2") (pinfunction "2_2") (pintype "passive"))
      (node (ref "L872") (pin "2") (pinfunction "2_2") (pintype "passive"))
      (node (ref "L904") (pin "2") (pinfunction "2_2") (pintype "passive"))
      (node (ref "L936") (pin "2") (pinfunction "2_2") (pintype "passive"))
      (node (ref "L968") (pin "2") (pinfunction "2_2") (pintype "passive"))
    )
    (net (code "14") (name "COL9") (class "Default")
      (node (ref "IC18") (pin "18") (pinfunction "O1_18") (pintype "open_collector"))
      (node (ref "IC19") (pin "18") (pinfunction "O1_18") (pintype "open_collector"))
      (node (ref "L1001") (pin "2") (pinfunction "2_2") (pintype "passive"))
      (node (ref "L105") (pin "2") (pinfunction "2_2") (pintype "passive"))
      (node (ref "L137") (pin "2") (pinfunction "2_2") (pintype "passive"))
      (node (ref "L169") (pin "2") (pinfunction "2_2") (pintype "passive"))
      (node (ref "L201") (pin "2") (pinfunction "2_2") (pintype "passive"))
      (node (ref "L233") (pin "2") (pinfunction "2_2") (pintype "passive"))
      (node (ref "L265") (pin "2") (pinfunction "2_2") (pintype "passive"))
      (node (ref "L297") (pin "2") (pinfunction "2_2") (pintype "passive"))
      (node (ref "L329") (pin "2") (pinfunction "2_2") (pintype "passive"))
      (node (ref "L361") (pin "2") (pinfunction "2_2") (pintype "passive"))
      (node (ref "L393") (pin "2") (pinfunction "2_2") (pintype "passive"))
      (node (ref "L41") (pin "2") (pinfunction "2_2") (pintype "passive"))
      (node (ref "L425") (pin "2") (pinfunction "2_2") (pintype "passive"))
      (node (ref "L457") (pin "2") (pinfunction "2_2") (pintype "passive"))
      (node (ref "L489") (pin "2") (pinfunction "2_2") (pintype "passive"))
      (node (ref "L521") (pin "2") (pinfunction "2_2") (pintype "passive"))
      (node (ref "L553") (pin "2") (pinfunction "2_2") (pintype "passive"))
      (node (ref "L585") (pin "2") (pinfunction "2_2") (pintype "passive"))
      (node (ref "L617") (pin "2") (pinfunction "2_2") (pintype "passive"))
      (node (ref "L649") (pin "2") (pinfunction "2_2") (pintype "passive"))
      (node (ref "L681") (pin "2") (pinfunction "2_2") (pintype "passive"))
      (node (ref "L713") (pin "2") (pinfunction "2_2") (pintype "passive"))
      (node (ref "L73") (pin "2") (pinfunction "2_2") (pintype "passive"))
      (node (ref "L745") (pin "2") (pinfunction "2_2") (pintype "passive"))
      (node (ref "L777") (pin "2") (pinfunction "2_2") (pintype "passive"))
      (node (ref "L809") (pin "2") (pinfunction "2_2") (pintype "passive"))
      (node (ref "L841") (pin "2") (pinfunction "2_2") (pintype "passive"))
      (node (ref "L873") (pin "2") (pinfunction "2_2") (pintype "passive"))
      (node (ref "L9") (pin "2") (pinfunction "2_2") (pintype "passive"))
      (node (ref "L905") (pin "2") (pinfunction "2_2") (pintype "passive"))
      (node (ref "L937") (pin "2") (pinfunction "2_2") (pintype "passive"))
      (node (ref "L969") (pin "2") (pinfunction "2_2") (pintype "passive"))
    )
    (net (code "15") (name "COL9-16_INHIBIT") (class "Default")
      (node (ref "IC17") (pin "23") (pinfunction "INH_23") (pintype "input"))
      (node (ref "IC3") (pin "11") (pinfunction "Y1_11") (pintype "output"))
    )
    (net (code "16") (name "COL10") (class "Default")
      (node (ref "IC18") (pin "17") (pinfunction "O2_17") (pintype "open_collector"))
      (node (ref "IC19") (pin "17") (pinfunction "O2_17") (pintype "open_collector"))
      (node (ref "L10") (pin "2") (pinfunction "2_2") (pintype "passive"))
      (node (ref "L1002") (pin "2") (pinfunction "2_2") (pintype "passive"))
      (node (ref "L106") (pin "2") (pinfunction "2_2") (pintype "passive"))
      (node (ref "L138") (pin "2") (pinfunction "2_2") (pintype "passive"))
      (node (ref "L170") (pin "2") (pinfunction "2_2") (pintype "passive"))
      (node (ref "L202") (pin "2") (pinfunction "2_2") (pintype "passive"))
      (node (ref "L234") (pin "2") (pinfunction "2_2") (pintype "passive"))
      (node (ref "L266") (pin "2") (pinfunction "2_2") (pintype "passive"))
      (node (ref "L298") (pin "2") (pinfunction "2_2") (pintype "passive"))
      (node (ref "L330") (pin "2") (pinfunction "2_2") (pintype "passive"))
      (node (ref "L362") (pin "2") (pinfunction "2_2") (pintype "passive"))
      (node (ref "L394") (pin "2") (pinfunction "2_2") (pintype "passive"))
      (node (ref "L42") (pin "2") (pinfunction "2_2") (pintype "passive"))
      (node (ref "L426") (pin "2") (pinfunction "2_2") (pintype "passive"))
      (node (ref "L458") (pin "2") (pinfunction "2_2") (pintype "passive"))
      (node (ref "L490") (pin "2") (pinfunction "2_2") (pintype "passive"))
      (node (ref "L522") (pin "2") (pinfunction "2_2") (pintype "passive"))
      (node (ref "L554") (pin "2") (pinfunction "2_2") (pintype "passive"))
      (node (ref "L586") (pin "2") (pinfunction "2_2") (pintype "passive"))
      (node (ref "L618") (pin "2") (pinfunction "2_2") (pintype "passive"))
      (node (ref "L650") (pin "2") (pinfunction "2_2") (pintype "passive"))
      (node (ref "L682") (pin "2") (pinfunction "2_2") (pintype "passive"))
      (node (ref "L714") (pin "2") (pinfunction "2_2") (pintype "passive"))
      (node (ref "L74") (pin "2") (pinfunction "2_2") (pintype "passive"))
      (node (ref "L746") (pin "2") (pinfunction "2_2") (pintype "passive"))
      (node (ref "L778") (pin "2") (pinfunction "2_2") (pintype "passive"))
      (node (ref "L810") (pin "2") (pinfunction "2_2") (pintype "passive"))
      (node (ref "L842") (pin "2") (pinfunction "2_2") (pintype "passive"))
      (node (ref "L874") (pin "2") (pinfunction "2_2") (pintype "passive"))
      (node (ref "L906") (pin "2") (pinfunction "2_2") (pintype "passive"))
      (node (ref "L938") (pin "2") (pinfunction "2_2") (pintype "passive"))
      (node (ref "L970") (pin "2") (pinfunction "2_2") (pintype "passive"))
    )
    (net (code "17") (name "COL11") (class "Default")
      (node (ref "IC18") (pin "16") (pinfunction "O3_16") (pintype "open_collector"))
      (node (ref "IC19") (pin "16") (pinfunction "O3_16") (pintype "open_collector"))
      (node (ref "L1003") (pin "2") (pinfunction "2_2") (pintype "passive"))
      (node (ref "L107") (pin "2") (pinfunction "2_2") (pintype "passive"))
      (node (ref "L11") (pin "2") (pinfunction "2_2") (pintype "passive"))
      (node (ref "L139") (pin "2") (pinfunction "2_2") (pintype "passive"))
      (node (ref "L171") (pin "2") (pinfunction "2_2") (pintype "passive"))
      (node (ref "L203") (pin "2") (pinfunction "2_2") (pintype "passive"))
      (node (ref "L235") (pin "2") (pinfunction "2_2") (pintype "passive"))
      (node (ref "L267") (pin "2") (pinfunction "2_2") (pintype "passive"))
      (node (ref "L299") (pin "2") (pinfunction "2_2") (pintype "passive"))
      (node (ref "L331") (pin "2") (pinfunction "2_2") (pintype "passive"))
      (node (ref "L363") (pin "2") (pinfunction "2_2") (pintype "passive"))
      (node (ref "L395") (pin "2") (pinfunction "2_2") (pintype "passive"))
      (node (ref "L427") (pin "2") (pinfunction "2_2") (pintype "passive"))
      (node (ref "L43") (pin "2") (pinfunction "2_2") (pintype "passive"))
      (node (ref "L459") (pin "2") (pinfunction "2_2") (pintype "passive"))
      (node (ref "L491") (pin "2") (pinfunction "2_2") (pintype "passive"))
      (node (ref "L523") (pin "2") (pinfunction "2_2") (pintype "passive"))
      (node (ref "L555") (pin "2") (pinfunction "2_2") (pintype "passive"))
      (node (ref "L587") (pin "2") (pinfunction "2_2") (pintype "passive"))
      (node (ref "L619") (pin "2") (pinfunction "2_2") (pintype "passive"))
      (node (ref "L651") (pin "2") (pinfunction "2_2") (pintype "passive"))
      (node (ref "L683") (pin "2") (pinfunction "2_2") (pintype "passive"))
      (node (ref "L715") (pin "2") (pinfunction "2_2") (pintype "passive"))
      (node (ref "L747") (pin "2") (pinfunction "2_2") (pintype "passive"))
      (node (ref "L75") (pin "2") (pinfunction "2_2") (pintype "passive"))
      (node (ref "L779") (pin "2") (pinfunction "2_2") (pintype "passive"))
      (node (ref "L811") (pin "2") (pinfunction "2_2") (pintype "passive"))
      (node (ref "L843") (pin "2") (pinfunction "2_2") (pintype "passive"))
      (node (ref "L875") (pin "2") (pinfunction "2_2") (pintype "passive"))
      (node (ref "L907") (pin "2") (pinfunction "2_2") (pintype "passive"))
      (node (ref "L939") (pin "2") (pinfunction "2_2") (pintype "passive"))
      (node (ref "L971") (pin "2") (pinfunction "2_2") (pintype "passive"))
    )
    (net (code "18") (name "COL12") (class "Default")
      (node (ref "IC18") (pin "15") (pinfunction "O4_15") (pintype "open_collector"))
      (node (ref "IC19") (pin "15") (pinfunction "O4_15") (pintype "open_collector"))
      (node (ref "L1004") (pin "2") (pinfunction "2_2") (pintype "passive"))
      (node (ref "L108") (pin "2") (pinfunction "2_2") (pintype "passive"))
      (node (ref "L12") (pin "2") (pinfunction "2_2") (pintype "passive"))
      (node (ref "L140") (pin "2") (pinfunction "2_2") (pintype "passive"))
      (node (ref "L172") (pin "2") (pinfunction "2_2") (pintype "passive"))
      (node (ref "L204") (pin "2") (pinfunction "2_2") (pintype "passive"))
      (node (ref "L236") (pin "2") (pinfunction "2_2") (pintype "passive"))
      (node (ref "L268") (pin "2") (pinfunction "2_2") (pintype "passive"))
      (node (ref "L300") (pin "2") (pinfunction "2_2") (pintype "passive"))
      (node (ref "L332") (pin "2") (pinfunction "2_2") (pintype "passive"))
      (node (ref "L364") (pin "2") (pinfunction "2_2") (pintype "passive"))
      (node (ref "L396") (pin "2") (pinfunction "2_2") (pintype "passive"))
      (node (ref "L428") (pin "2") (pinfunction "2_2") (pintype "passive"))
      (node (ref "L44") (pin "2") (pinfunction "2_2") (pintype "passive"))
      (node (ref "L460") (pin "2") (pinfunction "2_2") (pintype "passive"))
      (node (ref "L492") (pin "2") (pinfunction "2_2") (pintype "passive"))
      (node (ref "L524") (pin "2") (pinfunction "2_2") (pintype "passive"))
      (node (ref "L556") (pin "2") (pinfunction "2_2") (pintype "passive"))
      (node (ref "L588") (pin "2") (pinfunction "2_2") (pintype "passive"))
      (node (ref "L620") (pin "2") (pinfunction "2_2") (pintype "passive"))
      (node (ref "L652") (pin "2") (pinfunction "2_2") (pintype "passive"))
      (node (ref "L684") (pin "2") (pinfunction "2_2") (pintype "passive"))
      (node (ref "L716") (pin "2") (pinfunction "2_2") (pintype "passive"))
      (node (ref "L748") (pin "2") (pinfunction "2_2") (pintype "passive"))
      (node (ref "L76") (pin "2") (pinfunction "2_2") (pintype "passive"))
      (node (ref "L780") (pin "2") (pinfunction "2_2") (pintype "passive"))
      (node (ref "L812") (pin "2") (pinfunction "2_2") (pintype "passive"))
      (node (ref "L844") (pin "2") (pinfunction "2_2") (pintype "passive"))
      (node (ref "L876") (pin "2") (pinfunction "2_2") (pintype "passive"))
      (node (ref "L908") (pin "2") (pinfunction "2_2") (pintype "passive"))
      (node (ref "L940") (pin "2") (pinfunction "2_2") (pintype "passive"))
      (node (ref "L972") (pin "2") (pinfunction "2_2") (pintype "passive"))
    )
    (net (code "19") (name "COL13") (class "Default")
      (node (ref "IC18") (pin "14") (pinfunction "O5_14") (pintype "open_collector"))
      (node (ref "IC19") (pin "14") (pinfunction "O5_14") (pintype "open_collector"))
      (node (ref "L1005") (pin "2") (pinfunction "2_2") (pintype "passive"))
      (node (ref "L109") (pin "2") (pinfunction "2_2") (pintype "passive"))
      (node (ref "L13") (pin "2") (pinfunction "2_2") (pintype "passive"))
      (node (ref "L141") (pin "2") (pinfunction "2_2") (pintype "passive"))
      (node (ref "L173") (pin "2") (pinfunction "2_2") (pintype "passive"))
      (node (ref "L205") (pin "2") (pinfunction "2_2") (pintype "passive"))
      (node (ref "L237") (pin "2") (pinfunction "2_2") (pintype "passive"))
      (node (ref "L269") (pin "2") (pinfunction "2_2") (pintype "passive"))
      (node (ref "L301") (pin "2") (pinfunction "2_2") (pintype "passive"))
      (node (ref "L333") (pin "2") (pinfunction "2_2") (pintype "passive"))
      (node (ref "L365") (pin "2") (pinfunction "2_2") (pintype "passive"))
      (node (ref "L397") (pin "2") (pinfunction "2_2") (pintype "passive"))
      (node (ref "L429") (pin "2") (pinfunction "2_2") (pintype "passive"))
      (node (ref "L45") (pin "2") (pinfunction "2_2") (pintype "passive"))
      (node (ref "L461") (pin "2") (pinfunction "2_2") (pintype "passive"))
      (node (ref "L493") (pin "2") (pinfunction "2_2") (pintype "passive"))
      (node (ref "L525") (pin "2") (pinfunction "2_2") (pintype "passive"))
      (node (ref "L557") (pin "2") (pinfunction "2_2") (pintype "passive"))
      (node (ref "L589") (pin "2") (pinfunction "2_2") (pintype "passive"))
      (node (ref "L621") (pin "2") (pinfunction "2_2") (pintype "passive"))
      (node (ref "L653") (pin "2") (pinfunction "2_2") (pintype "passive"))
      (node (ref "L685") (pin "2") (pinfunction "2_2") (pintype "passive"))
      (node (ref "L717") (pin "2") (pinfunction "2_2") (pintype "passive"))
      (node (ref "L749") (pin "2") (pinfunction "2_2") (pintype "passive"))
      (node (ref "L77") (pin "2") (pinfunction "2_2") (pintype "passive"))
      (node (ref "L781") (pin "2") (pinfunction "2_2") (pintype "passive"))
      (node (ref "L813") (pin "2") (pinfunction "2_2") (pintype "passive"))
      (node (ref "L845") (pin "2") (pinfunction "2_2") (pintype "passive"))
      (node (ref "L877") (pin "2") (pinfunction "2_2") (pintype "passive"))
      (node (ref "L909") (pin "2") (pinfunction "2_2") (pintype "passive"))
      (node (ref "L941") (pin "2") (pinfunction "2_2") (pintype "passive"))
      (node (ref "L973") (pin "2") (pinfunction "2_2") (pintype "passive"))
    )
    (net (code "20") (name "COL14") (class "Default")
      (node (ref "IC18") (pin "13") (pinfunction "O6_13") (pintype "open_collector"))
      (node (ref "IC19") (pin "13") (pinfunction "O6_13") (pintype "open_collector"))
      (node (ref "L1006") (pin "2") (pinfunction "2_2") (pintype "passive"))
      (node (ref "L110") (pin "2") (pinfunction "2_2") (pintype "passive"))
      (node (ref "L14") (pin "2") (pinfunction "2_2") (pintype "passive"))
      (node (ref "L142") (pin "2") (pinfunction "2_2") (pintype "passive"))
      (node (ref "L174") (pin "2") (pinfunction "2_2") (pintype "passive"))
      (node (ref "L206") (pin "2") (pinfunction "2_2") (pintype "passive"))
      (node (ref "L238") (pin "2") (pinfunction "2_2") (pintype "passive"))
      (node (ref "L270") (pin "2") (pinfunction "2_2") (pintype "passive"))
      (node (ref "L302") (pin "2") (pinfunction "2_2") (pintype "passive"))
      (node (ref "L334") (pin "2") (pinfunction "2_2") (pintype "passive"))
      (node (ref "L366") (pin "2") (pinfunction "2_2") (pintype "passive"))
      (node (ref "L398") (pin "2") (pinfunction "2_2") (pintype "passive"))
      (node (ref "L430") (pin "2") (pinfunction "2_2") (pintype "passive"))
      (node (ref "L46") (pin "2") (pinfunction "2_2") (pintype "passive"))
      (node (ref "L462") (pin "2") (pinfunction "2_2") (pintype "passive"))
      (node (ref "L494") (pin "2") (pinfunction "2_2") (pintype "passive"))
      (node (ref "L526") (pin "2") (pinfunction "2_2") (pintype "passive"))
      (node (ref "L558") (pin "2") (pinfunction "2_2") (pintype "passive"))
      (node (ref "L590") (pin "2") (pinfunction "2_2") (pintype "passive"))
      (node (ref "L622") (pin "2") (pinfunction "2_2") (pintype "passive"))
      (node (ref "L654") (pin "2") (pinfunction "2_2") (pintype "passive"))
      (node (ref "L686") (pin "2") (pinfunction "2_2") (pintype "passive"))
      (node (ref "L718") (pin "2") (pinfunction "2_2") (pintype "passive"))
      (node (ref "L750") (pin "2") (pinfunction "2_2") (pintype "passive"))
      (node (ref "L78") (pin "2") (pinfunction "2_2") (pintype "passive"))
      (node (ref "L782") (pin "2") (pinfunction "2_2") (pintype "passive"))
      (node (ref "L814") (pin "2") (pinfunction "2_2") (pintype "passive"))
      (node (ref "L846") (pin "2") (pinfunction "2_2") (pintype "passive"))
      (node (ref "L878") (pin "2") (pinfunction "2_2") (pintype "passive"))
      (node (ref "L910") (pin "2") (pinfunction "2_2") (pintype "passive"))
      (node (ref "L942") (pin "2") (pinfunction "2_2") (pintype "passive"))
      (node (ref "L974") (pin "2") (pinfunction "2_2") (pintype "passive"))
    )
    (net (code "21") (name "COL15") (class "Default")
      (node (ref "IC18") (pin "12") (pinfunction "O7_12") (pintype "open_collector"))
      (node (ref "IC19") (pin "12") (pinfunction "O7_12") (pintype "open_collector"))
      (node (ref "L1007") (pin "2") (pinfunction "2_2") (pintype "passive"))
      (node (ref "L111") (pin "2") (pinfunction "2_2") (pintype "passive"))
      (node (ref "L143") (pin "2") (pinfunction "2_2") (pintype "passive"))
      (node (ref "L15") (pin "2") (pinfunction "2_2") (pintype "passive"))
      (node (ref "L175") (pin "2") (pinfunction "2_2") (pintype "passive"))
      (node (ref "L207") (pin "2") (pinfunction "2_2") (pintype "passive"))
      (node (ref "L239") (pin "2") (pinfunction "2_2") (pintype "passive"))
      (node (ref "L271") (pin "2") (pinfunction "2_2") (pintype "passive"))
      (node (ref "L303") (pin "2") (pinfunction "2_2") (pintype "passive"))
      (node (ref "L335") (pin "2") (pinfunction "2_2") (pintype "passive"))
      (node (ref "L367") (pin "2") (pinfunction "2_2") (pintype "passive"))
      (node (ref "L399") (pin "2") (pinfunction "2_2") (pintype "passive"))
      (node (ref "L431") (pin "2") (pinfunction "2_2") (pintype "passive"))
      (node (ref "L463") (pin "2") (pinfunction "2_2") (pintype "passive"))
      (node (ref "L47") (pin "2") (pinfunction "2_2") (pintype "passive"))
      (node (ref "L495") (pin "2") (pinfunction "2_2") (pintype "passive"))
      (node (ref "L527") (pin "2") (pinfunction "2_2") (pintype "passive"))
      (node (ref "L559") (pin "2") (pinfunction "2_2") (pintype "passive"))
      (node (ref "L591") (pin "2") (pinfunction "2_2") (pintype "passive"))
      (node (ref "L623") (pin "2") (pinfunction "2_2") (pintype "passive"))
      (node (ref "L655") (pin "2") (pinfunction "2_2") (pintype "passive"))
      (node (ref "L687") (pin "2") (pinfunction "2_2") (pintype "passive"))
      (node (ref "L719") (pin "2") (pinfunction "2_2") (pintype "passive"))
      (node (ref "L751") (pin "2") (pinfunction "2_2") (pintype "passive"))
      (node (ref "L783") (pin "2") (pinfunction "2_2") (pintype "passive"))
      (node (ref "L79") (pin "2") (pinfunction "2_2") (pintype "passive"))
      (node (ref "L815") (pin "2") (pinfunction "2_2") (pintype "passive"))
      (node (ref "L847") (pin "2") (pinfunction "2_2") (pintype "passive"))
      (node (ref "L879") (pin "2") (pinfunction "2_2") (pintype "passive"))
      (node (ref "L911") (pin "2") (pinfunction "2_2") (pintype "passive"))
      (node (ref "L943") (pin "2") (pinfunction "2_2") (pintype "passive"))
      (node (ref "L975") (pin "2") (pinfunction "2_2") (pintype "passive"))
    )
    (net (code "22") (name "COL16") (class "Default")
      (node (ref "IC18") (pin "11") (pinfunction "O8_11") (pintype "open_collector"))
      (node (ref "IC19") (pin "11") (pinfunction "O8_11") (pintype "open_collector"))
      (node (ref "L1008") (pin "2") (pinfunction "2_2") (pintype "passive"))
      (node (ref "L112") (pin "2") (pinfunction "2_2") (pintype "passive"))
      (node (ref "L144") (pin "2") (pinfunction "2_2") (pintype "passive"))
      (node (ref "L16") (pin "2") (pinfunction "2_2") (pintype "passive"))
      (node (ref "L176") (pin "2") (pinfunction "2_2") (pintype "passive"))
      (node (ref "L208") (pin "2") (pinfunction "2_2") (pintype "passive"))
      (node (ref "L240") (pin "2") (pinfunction "2_2") (pintype "passive"))
      (node (ref "L272") (pin "2") (pinfunction "2_2") (pintype "passive"))
      (node (ref "L304") (pin "2") (pinfunction "2_2") (pintype "passive"))
      (node (ref "L336") (pin "2") (pinfunction "2_2") (pintype "passive"))
      (node (ref "L368") (pin "2") (pinfunction "2_2") (pintype "passive"))
      (node (ref "L400") (pin "2") (pinfunction "2_2") (pintype "passive"))
      (node (ref "L432") (pin "2") (pinfunction "2_2") (pintype "passive"))
      (node (ref "L464") (pin "2") (pinfunction "2_2") (pintype "passive"))
      (node (ref "L48") (pin "2") (pinfunction "2_2") (pintype "passive"))
      (node (ref "L496") (pin "2") (pinfunction "2_2") (pintype "passive"))
      (node (ref "L528") (pin "2") (pinfunction "2_2") (pintype "passive"))
      (node (ref "L560") (pin "2") (pinfunction "2_2") (pintype "passive"))
      (node (ref "L592") (pin "2") (pinfunction "2_2") (pintype "passive"))
      (node (ref "L624") (pin "2") (pinfunction "2_2") (pintype "passive"))
      (node (ref "L656") (pin "2") (pinfunction "2_2") (pintype "passive"))
      (node (ref "L688") (pin "2") (pinfunction "2_2") (pintype "passive"))
      (node (ref "L720") (pin "2") (pinfunction "2_2") (pintype "passive"))
      (node (ref "L752") (pin "2") (pinfunction "2_2") (pintype "passive"))
      (node (ref "L784") (pin "2") (pinfunction "2_2") (pintype "passive"))
      (node (ref "L80") (pin "2") (pinfunction "2_2") (pintype "passive"))
      (node (ref "L816") (pin "2") (pinfunction "2_2") (pintype "passive"))
      (node (ref "L848") (pin "2") (pinfunction "2_2") (pintype "passive"))
      (node (ref "L880") (pin "2") (pinfunction "2_2") (pintype "passive"))
      (node (ref "L912") (pin "2") (pinfunction "2_2") (pintype "passive"))
      (node (ref "L944") (pin "2") (pinfunction "2_2") (pintype "passive"))
      (node (ref "L976") (pin "2") (pinfunction "2_2") (pintype "passive"))
    )
    (net (code "23") (name "COL17") (class "Default")
      (node (ref "IC21") (pin "18") (pinfunction "O1_18") (pintype "open_collector"))
      (node (ref "IC22") (pin "18") (pinfunction "O1_18") (pintype "open_collector"))
      (node (ref "L1009") (pin "2") (pinfunction "2_2") (pintype "passive"))
      (node (ref "L113") (pin "2") (pinfunction "2_2") (pintype "passive"))
      (node (ref "L145") (pin "2") (pinfunction "2_2") (pintype "passive"))
      (node (ref "L17") (pin "2") (pinfunction "2_2") (pintype "passive"))
      (node (ref "L177") (pin "2") (pinfunction "2_2") (pintype "passive"))
      (node (ref "L209") (pin "2") (pinfunction "2_2") (pintype "passive"))
      (node (ref "L241") (pin "2") (pinfunction "2_2") (pintype "passive"))
      (node (ref "L273") (pin "2") (pinfunction "2_2") (pintype "passive"))
      (node (ref "L305") (pin "2") (pinfunction "2_2") (pintype "passive"))
      (node (ref "L337") (pin "2") (pinfunction "2_2") (pintype "passive"))
      (node (ref "L369") (pin "2") (pinfunction "2_2") (pintype "passive"))
      (node (ref "L401") (pin "2") (pinfunction "2_2") (pintype "passive"))
      (node (ref "L433") (pin "2") (pinfunction "2_2") (pintype "passive"))
      (node (ref "L465") (pin "2") (pinfunction "2_2") (pintype "passive"))
      (node (ref "L49") (pin "2") (pinfunction "2_2") (pintype "passive"))
      (node (ref "L497") (pin "2") (pinfunction "2_2") (pintype "passive"))
      (node (ref "L529") (pin "2") (pinfunction "2_2") (pintype "passive"))
      (node (ref "L561") (pin "2") (pinfunction "2_2") (pintype "passive"))
      (node (ref "L593") (pin "2") (pinfunction "2_2") (pintype "passive"))
      (node (ref "L625") (pin "2") (pinfunction "2_2") (pintype "passive"))
      (node (ref "L657") (pin "2") (pinfunction "2_2") (pintype "passive"))
      (node (ref "L689") (pin "2") (pinfunction "2_2") (pintype "passive"))
      (node (ref "L721") (pin "2") (pinfunction "2_2") (pintype "passive"))
      (node (ref "L753") (pin "2") (pinfunction "2_2") (pintype "passive"))
      (node (ref "L785") (pin "2") (pinfunction "2_2") (pintype "passive"))
      (node (ref "L81") (pin "2") (pinfunction "2_2") (pintype "passive"))
      (node (ref "L817") (pin "2") (pinfunction "2_2") (pintype "passive"))
      (node (ref "L849") (pin "2") (pinfunction "2_2") (pintype "passive"))
      (node (ref "L881") (pin "2") (pinfunction "2_2") (pintype "passive"))
      (node (ref "L913") (pin "2") (pinfunction "2_2") (pintype "passive"))
      (node (ref "L945") (pin "2") (pinfunction "2_2") (pintype "passive"))
      (node (ref "L977") (pin "2") (pinfunction "2_2") (pintype "passive"))
    )
    (net (code "24") (name "COL17-24_INHIBIT") (class "Default")
      (node (ref "IC20") (pin "23") (pinfunction "INH_23") (pintype "input"))
      (node (ref "IC3") (pin "10") (pinfunction "Y2_10") (pintype "output"))
    )
    (net (code "25") (name "COL18") (class "Default")
      (node (ref "IC21") (pin "17") (pinfunction "O2_17") (pintype "open_collector"))
      (node (ref "IC22") (pin "17") (pinfunction "O2_17") (pintype "open_collector"))
      (node (ref "L1010") (pin "2") (pinfunction "2_2") (pintype "passive"))
      (node (ref "L114") (pin "2") (pinfunction "2_2") (pintype "passive"))
      (node (ref "L146") (pin "2") (pinfunction "2_2") (pintype "passive"))
      (node (ref "L178") (pin "2") (pinfunction "2_2") (pintype "passive"))
      (node (ref "L18") (pin "2") (pinfunction "2_2") (pintype "passive"))
      (node (ref "L210") (pin "2") (pinfunction "2_2") (pintype "passive"))
      (node (ref "L242") (pin "2") (pinfunction "2_2") (pintype "passive"))
      (node (ref "L274") (pin "2") (pinfunction "2_2") (pintype "passive"))
      (node (ref "L306") (pin "2") (pinfunction "2_2") (pintype "passive"))
      (node (ref "L338") (pin "2") (pinfunction "2_2") (pintype "passive"))
      (node (ref "L370") (pin "2") (pinfunction "2_2") (pintype "passive"))
      (node (ref "L402") (pin "2") (pinfunction "2_2") (pintype "passive"))
      (node (ref "L434") (pin "2") (pinfunction "2_2") (pintype "passive"))
      (node (ref "L466") (pin "2") (pinfunction "2_2") (pintype "passive"))
      (node (ref "L498") (pin "2") (pinfunction "2_2") (pintype "passive"))
      (node (ref "L50") (pin "2") (pinfunction "2_2") (pintype "passive"))
      (node (ref "L530") (pin "2") (pinfunction "2_2") (pintype "passive"))
      (node (ref "L562") (pin "2") (pinfunction "2_2") (pintype "passive"))
      (node (ref "L594") (pin "2") (pinfunction "2_2") (pintype "passive"))
      (node (ref "L626") (pin "2") (pinfunction "2_2") (pintype "passive"))
      (node (ref "L658") (pin "2") (pinfunction "2_2") (pintype "passive"))
      (node (ref "L690") (pin "2") (pinfunction "2_2") (pintype "passive"))
      (node (ref "L722") (pin "2") (pinfunction "2_2") (pintype "passive"))
      (node (ref "L754") (pin "2") (pinfunction "2_2") (pintype "passive"))
      (node (ref "L786") (pin "2") (pinfunction "2_2") (pintype "passive"))
      (node (ref "L818") (pin "2") (pinfunction "2_2") (pintype "passive"))
      (node (ref "L82") (pin "2") (pinfunction "2_2") (pintype "passive"))
      (node (ref "L850") (pin "2") (pinfunction "2_2") (pintype "passive"))
      (node (ref "L882") (pin "2") (pinfunction "2_2") (pintype "passive"))
      (node (ref "L914") (pin "2") (pinfunction "2_2") (pintype "passive"))
      (node (ref "L946") (pin "2") (pinfunction "2_2") (pintype "passive"))
      (node (ref "L978") (pin "2") (pinfunction "2_2") (pintype "passive"))
    )
    (net (code "26") (name "COL19") (class "Default")
      (node (ref "IC21") (pin "16") (pinfunction "O3_16") (pintype "open_collector"))
      (node (ref "IC22") (pin "16") (pinfunction "O3_16") (pintype "open_collector"))
      (node (ref "L1011") (pin "2") (pinfunction "2_2") (pintype "passive"))
      (node (ref "L115") (pin "2") (pinfunction "2_2") (pintype "passive"))
      (node (ref "L147") (pin "2") (pinfunction "2_2") (pintype "passive"))
      (node (ref "L179") (pin "2") (pinfunction "2_2") (pintype "passive"))
      (node (ref "L19") (pin "2") (pinfunction "2_2") (pintype "passive"))
      (node (ref "L211") (pin "2") (pinfunction "2_2") (pintype "passive"))
      (node (ref "L243") (pin "2") (pinfunction "2_2") (pintype "passive"))
      (node (ref "L275") (pin "2") (pinfunction "2_2") (pintype "passive"))
      (node (ref "L307") (pin "2") (pinfunction "2_2") (pintype "passive"))
      (node (ref "L339") (pin "2") (pinfunction "2_2") (pintype "passive"))
      (node (ref "L371") (pin "2") (pinfunction "2_2") (pintype "passive"))
      (node (ref "L403") (pin "2") (pinfunction "2_2") (pintype "passive"))
      (node (ref "L435") (pin "2") (pinfunction "2_2") (pintype "passive"))
      (node (ref "L467") (pin "2") (pinfunction "2_2") (pintype "passive"))
      (node (ref "L499") (pin "2") (pinfunction "2_2") (pintype "passive"))
      (node (ref "L51") (pin "2") (pinfunction "2_2") (pintype "passive"))
      (node (ref "L531") (pin "2") (pinfunction "2_2") (pintype "passive"))
      (node (ref "L563") (pin "2") (pinfunction "2_2") (pintype "passive"))
      (node (ref "L595") (pin "2") (pinfunction "2_2") (pintype "passive"))
      (node (ref "L627") (pin "2") (pinfunction "2_2") (pintype "passive"))
      (node (ref "L659") (pin "2") (pinfunction "2_2") (pintype "passive"))
      (node (ref "L691") (pin "2") (pinfunction "2_2") (pintype "passive"))
      (node (ref "L723") (pin "2") (pinfunction "2_2") (pintype "passive"))
      (node (ref "L755") (pin "2") (pinfunction "2_2") (pintype "passive"))
      (node (ref "L787") (pin "2") (pinfunction "2_2") (pintype "passive"))
      (node (ref "L819") (pin "2") (pinfunction "2_2") (pintype "passive"))
      (node (ref "L83") (pin "2") (pinfunction "2_2") (pintype "passive"))
      (node (ref "L851") (pin "2") (pinfunction "2_2") (pintype "passive"))
      (node (ref "L883") (pin "2") (pinfunction "2_2") (pintype "passive"))
      (node (ref "L915") (pin "2") (pinfunction "2_2") (pintype "passive"))
      (node (ref "L947") (pin "2") (pinfunction "2_2") (pintype "passive"))
      (node (ref "L979") (pin "2") (pinfunction "2_2") (pintype "passive"))
    )
    (net (code "27") (name "COL20") (class "Default")
      (node (ref "IC21") (pin "15") (pinfunction "O4_15") (pintype "open_collector"))
      (node (ref "IC22") (pin "15") (pinfunction "O4_15") (pintype "open_collector"))
      (node (ref "L1012") (pin "2") (pinfunction "2_2") (pintype "passive"))
      (node (ref "L116") (pin "2") (pinfunction "2_2") (pintype "passive"))
      (node (ref "L148") (pin "2") (pinfunction "2_2") (pintype "passive"))
      (node (ref "L180") (pin "2") (pinfunction "2_2") (pintype "passive"))
      (node (ref "L20") (pin "2") (pinfunction "2_2") (pintype "passive"))
      (node (ref "L212") (pin "2") (pinfunction "2_2") (pintype "passive"))
      (node (ref "L244") (pin "2") (pinfunction "2_2") (pintype "passive"))
      (node (ref "L276") (pin "2") (pinfunction "2_2") (pintype "passive"))
      (node (ref "L308") (pin "2") (pinfunction "2_2") (pintype "passive"))
      (node (ref "L340") (pin "2") (pinfunction "2_2") (pintype "passive"))
      (node (ref "L372") (pin "2") (pinfunction "2_2") (pintype "passive"))
      (node (ref "L404") (pin "2") (pinfunction "2_2") (pintype "passive"))
      (node (ref "L436") (pin "2") (pinfunction "2_2") (pintype "passive"))
      (node (ref "L468") (pin "2") (pinfunction "2_2") (pintype "passive"))
      (node (ref "L500") (pin "2") (pinfunction "2_2") (pintype "passive"))
      (node (ref "L52") (pin "2") (pinfunction "2_2") (pintype "passive"))
      (node (ref "L532") (pin "2") (pinfunction "2_2") (pintype "passive"))
      (node (ref "L564") (pin "2") (pinfunction "2_2") (pintype "passive"))
      (node (ref "L596") (pin "2") (pinfunction "2_2") (pintype "passive"))
      (node (ref "L628") (pin "2") (pinfunction "2_2") (pintype "passive"))
      (node (ref "L660") (pin "2") (pinfunction "2_2") (pintype "passive"))
      (node (ref "L692") (pin "2") (pinfunction "2_2") (pintype "passive"))
      (node (ref "L724") (pin "2") (pinfunction "2_2") (pintype "passive"))
      (node (ref "L756") (pin "2") (pinfunction "2_2") (pintype "passive"))
      (node (ref "L788") (pin "2") (pinfunction "2_2") (pintype "passive"))
      (node (ref "L820") (pin "2") (pinfunction "2_2") (pintype "passive"))
      (node (ref "L84") (pin "2") (pinfunction "2_2") (pintype "passive"))
      (node (ref "L852") (pin "2") (pinfunction "2_2") (pintype "passive"))
      (node (ref "L884") (pin "2") (pinfunction "2_2") (pintype "passive"))
      (node (ref "L916") (pin "2") (pinfunction "2_2") (pintype "passive"))
      (node (ref "L948") (pin "2") (pinfunction "2_2") (pintype "passive"))
      (node (ref "L980") (pin "2") (pinfunction "2_2") (pintype "passive"))
    )
    (net (code "28") (name "COL21") (class "Default")
      (node (ref "IC21") (pin "14") (pinfunction "O5_14") (pintype "open_collector"))
      (node (ref "IC22") (pin "14") (pinfunction "O5_14") (pintype "open_collector"))
      (node (ref "L1013") (pin "2") (pinfunction "2_2") (pintype "passive"))
      (node (ref "L117") (pin "2") (pinfunction "2_2") (pintype "passive"))
      (node (ref "L149") (pin "2") (pinfunction "2_2") (pintype "passive"))
      (node (ref "L181") (pin "2") (pinfunction "2_2") (pintype "passive"))
      (node (ref "L21") (pin "2") (pinfunction "2_2") (pintype "passive"))
      (node (ref "L213") (pin "2") (pinfunction "2_2") (pintype "passive"))
      (node (ref "L245") (pin "2") (pinfunction "2_2") (pintype "passive"))
      (node (ref "L277") (pin "2") (pinfunction "2_2") (pintype "passive"))
      (node (ref "L309") (pin "2") (pinfunction "2_2") (pintype "passive"))
      (node (ref "L341") (pin "2") (pinfunction "2_2") (pintype "passive"))
      (node (ref "L373") (pin "2") (pinfunction "2_2") (pintype "passive"))
      (node (ref "L405") (pin "2") (pinfunction "2_2") (pintype "passive"))
      (node (ref "L437") (pin "2") (pinfunction "2_2") (pintype "passive"))
      (node (ref "L469") (pin "2") (pinfunction "2_2") (pintype "passive"))
      (node (ref "L501") (pin "2") (pinfunction "2_2") (pintype "passive"))
      (node (ref "L53") (pin "2") (pinfunction "2_2") (pintype "passive"))
      (node (ref "L533") (pin "2") (pinfunction "2_2") (pintype "passive"))
      (node (ref "L565") (pin "2") (pinfunction "2_2") (pintype "passive"))
      (node (ref "L597") (pin "2") (pinfunction "2_2") (pintype "passive"))
      (node (ref "L629") (pin "2") (pinfunction "2_2") (pintype "passive"))
      (node (ref "L661") (pin "2") (pinfunction "2_2") (pintype "passive"))
      (node (ref "L693") (pin "2") (pinfunction "2_2") (pintype "passive"))
      (node (ref "L725") (pin "2") (pinfunction "2_2") (pintype "passive"))
      (node (ref "L757") (pin "2") (pinfunction "2_2") (pintype "passive"))
      (node (ref "L789") (pin "2") (pinfunction "2_2") (pintype "passive"))
      (node (ref "L821") (pin "2") (pinfunction "2_2") (pintype "passive"))
      (node (ref "L85") (pin "2") (pinfunction "2_2") (pintype "passive"))
      (node (ref "L853") (pin "2") (pinfunction "2_2") (pintype "passive"))
      (node (ref "L885") (pin "2") (pinfunction "2_2") (pintype "passive"))
      (node (ref "L917") (pin "2") (pinfunction "2_2") (pintype "passive"))
      (node (ref "L949") (pin "2") (pinfunction "2_2") (pintype "passive"))
      (node (ref "L981") (pin "2") (pinfunction "2_2") (pintype "passive"))
    )
    (net (code "29") (name "COL22") (class "Default")
      (node (ref "IC21") (pin "13") (pinfunction "O6_13") (pintype "open_collector"))
      (node (ref "IC22") (pin "13") (pinfunction "O6_13") (pintype "open_collector"))
      (node (ref "L1014") (pin "2") (pinfunction "2_2") (pintype "passive"))
      (node (ref "L118") (pin "2") (pinfunction "2_2") (pintype "passive"))
      (node (ref "L150") (pin "2") (pinfunction "2_2") (pintype "passive"))
      (node (ref "L182") (pin "2") (pinfunction "2_2") (pintype "passive"))
      (node (ref "L214") (pin "2") (pinfunction "2_2") (pintype "passive"))
      (node (ref "L22") (pin "2") (pinfunction "2_2") (pintype "passive"))
      (node (ref "L246") (pin "2") (pinfunction "2_2") (pintype "passive"))
      (node (ref "L278") (pin "2") (pinfunction "2_2") (pintype "passive"))
      (node (ref "L310") (pin "2") (pinfunction "2_2") (pintype "passive"))
      (node (ref "L342") (pin "2") (pinfunction "2_2") (pintype "passive"))
      (node (ref "L374") (pin "2") (pinfunction "2_2") (pintype "passive"))
      (node (ref "L406") (pin "2") (pinfunction "2_2") (pintype "passive"))
      (node (ref "L438") (pin "2") (pinfunction "2_2") (pintype "passive"))
      (node (ref "L470") (pin "2") (pinfunction "2_2") (pintype "passive"))
      (node (ref "L502") (pin "2") (pinfunction "2_2") (pintype "passive"))
      (node (ref "L534") (pin "2") (pinfunction "2_2") (pintype "passive"))
      (node (ref "L54") (pin "2") (pinfunction "2_2") (pintype "passive"))
      (node (ref "L566") (pin "2") (pinfunction "2_2") (pintype "passive"))
      (node (ref "L598") (pin "2") (pinfunction "2_2") (pintype "passive"))
      (node (ref "L630") (pin "2") (pinfunction "2_2") (pintype "passive"))
      (node (ref "L662") (pin "2") (pinfunction "2_2") (pintype "passive"))
      (node (ref "L694") (pin "2") (pinfunction "2_2") (pintype "passive"))
      (node (ref "L726") (pin "2") (pinfunction "2_2") (pintype "passive"))
      (node (ref "L758") (pin "2") (pinfunction "2_2") (pintype "passive"))
      (node (ref "L790") (pin "2") (pinfunction "2_2") (pintype "passive"))
      (node (ref "L822") (pin "2") (pinfunction "2_2") (pintype "passive"))
      (node (ref "L854") (pin "2") (pinfunction "2_2") (pintype "passive"))
      (node (ref "L86") (pin "2") (pinfunction "2_2") (pintype "passive"))
      (node (ref "L886") (pin "2") (pinfunction "2_2") (pintype "passive"))
      (node (ref "L918") (pin "2") (pinfunction "2_2") (pintype "passive"))
      (node (ref "L950") (pin "2") (pinfunction "2_2") (pintype "passive"))
      (node (ref "L982") (pin "2") (pinfunction "2_2") (pintype "passive"))
    )
    (net (code "30") (name "COL23") (class "Default")
      (node (ref "IC21") (pin "12") (pinfunction "O7_12") (pintype "open_collector"))
      (node (ref "IC22") (pin "12") (pinfunction "O7_12") (pintype "open_collector"))
      (node (ref "L1015") (pin "2") (pinfunction "2_2") (pintype "passive"))
      (node (ref "L119") (pin "2") (pinfunction "2_2") (pintype "passive"))
      (node (ref "L151") (pin "2") (pinfunction "2_2") (pintype "passive"))
      (node (ref "L183") (pin "2") (pinfunction "2_2") (pintype "passive"))
      (node (ref "L215") (pin "2") (pinfunction "2_2") (pintype "passive"))
      (node (ref "L23") (pin "2") (pinfunction "2_2") (pintype "passive"))
      (node (ref "L247") (pin "2") (pinfunction "2_2") (pintype "passive"))
      (node (ref "L279") (pin "2") (pinfunction "2_2") (pintype "passive"))
      (node (ref "L311") (pin "2") (pinfunction "2_2") (pintype "passive"))
      (node (ref "L343") (pin "2") (pinfunction "2_2") (pintype "passive"))
      (node (ref "L375") (pin "2") (pinfunction "2_2") (pintype "passive"))
      (node (ref "L407") (pin "2") (pinfunction "2_2") (pintype "passive"))
      (node (ref "L439") (pin "2") (pinfunction "2_2") (pintype "passive"))
      (node (ref "L471") (pin "2") (pinfunction "2_2") (pintype "passive"))
      (node (ref "L503") (pin "2") (pinfunction "2_2") (pintype "passive"))
      (node (ref "L535") (pin "2") (pinfunction "2_2") (pintype "passive"))
      (node (ref "L55") (pin "2") (pinfunction "2_2") (pintype "passive"))
      (node (ref "L567") (pin "2") (pinfunction "2_2") (pintype "passive"))
      (node (ref "L599") (pin "2") (pinfunction "2_2") (pintype "passive"))
      (node (ref "L631") (pin "2") (pinfunction "2_2") (pintype "passive"))
      (node (ref "L663") (pin "2") (pinfunction "2_2") (pintype "passive"))
      (node (ref "L695") (pin "2") (pinfunction "2_2") (pintype "passive"))
      (node (ref "L727") (pin "2") (pinfunction "2_2") (pintype "passive"))
      (node (ref "L759") (pin "2") (pinfunction "2_2") (pintype "passive"))
      (node (ref "L791") (pin "2") (pinfunction "2_2") (pintype "passive"))
      (node (ref "L823") (pin "2") (pinfunction "2_2") (pintype "passive"))
      (node (ref "L855") (pin "2") (pinfunction "2_2") (pintype "passive"))
      (node (ref "L87") (pin "2") (pinfunction "2_2") (pintype "passive"))
      (node (ref "L887") (pin "2") (pinfunction "2_2") (pintype "passive"))
      (node (ref "L919") (pin "2") (pinfunction "2_2") (pintype "passive"))
      (node (ref "L951") (pin "2") (pinfunction "2_2") (pintype "passive"))
      (node (ref "L983") (pin "2") (pinfunction "2_2") (pintype "passive"))
    )
    (net (code "31") (name "COL24") (class "Default")
      (node (ref "IC21") (pin "11") (pinfunction "O8_11") (pintype "open_collector"))
      (node (ref "IC22") (pin "11") (pinfunction "O8_11") (pintype "open_collector"))
      (node (ref "L1016") (pin "2") (pinfunction "2_2") (pintype "passive"))
      (node (ref "L120") (pin "2") (pinfunction "2_2") (pintype "passive"))
      (node (ref "L152") (pin "2") (pinfunction "2_2") (pintype "passive"))
      (node (ref "L184") (pin "2") (pinfunction "2_2") (pintype "passive"))
      (node (ref "L216") (pin "2") (pinfunction "2_2") (pintype "passive"))
      (node (ref "L24") (pin "2") (pinfunction "2_2") (pintype "passive"))
      (node (ref "L248") (pin "2") (pinfunction "2_2") (pintype "passive"))
      (node (ref "L280") (pin "2") (pinfunction "2_2") (pintype "passive"))
      (node (ref "L312") (pin "2") (pinfunction "2_2") (pintype "passive"))
      (node (ref "L344") (pin "2") (pinfunction "2_2") (pintype "passive"))
      (node (ref "L376") (pin "2") (pinfunction "2_2") (pintype "passive"))
      (node (ref "L408") (pin "2") (pinfunction "2_2") (pintype "passive"))
      (node (ref "L440") (pin "2") (pinfunction "2_2") (pintype "passive"))
      (node (ref "L472") (pin "2") (pinfunction "2_2") (pintype "passive"))
      (node (ref "L504") (pin "2") (pinfunction "2_2") (pintype "passive"))
      (node (ref "L536") (pin "2") (pinfunction "2_2") (pintype "passive"))
      (node (ref "L56") (pin "2") (pinfunction "2_2") (pintype "passive"))
      (node (ref "L568") (pin "2") (pinfunction "2_2") (pintype "passive"))
      (node (ref "L600") (pin "2") (pinfunction "2_2") (pintype "passive"))
      (node (ref "L632") (pin "2") (pinfunction "2_2") (pintype "passive"))
      (node (ref "L664") (pin "2") (pinfunction "2_2") (pintype "passive"))
      (node (ref "L696") (pin "2") (pinfunction "2_2") (pintype "passive"))
      (node (ref "L728") (pin "2") (pinfunction "2_2") (pintype "passive"))
      (node (ref "L760") (pin "2") (pinfunction "2_2") (pintype "passive"))
      (node (ref "L792") (pin "2") (pinfunction "2_2") (pintype "passive"))
      (node (ref "L824") (pin "2") (pinfunction "2_2") (pintype "passive"))
      (node (ref "L856") (pin "2") (pinfunction "2_2") (pintype "passive"))
      (node (ref "L88") (pin "2") (pinfunction "2_2") (pintype "passive"))
      (node (ref "L888") (pin "2") (pinfunction "2_2") (pintype "passive"))
      (node (ref "L920") (pin "2") (pinfunction "2_2") (pintype "passive"))
      (node (ref "L952") (pin "2") (pinfunction "2_2") (pintype "passive"))
      (node (ref "L984") (pin "2") (pinfunction "2_2") (pintype "passive"))
    )
    (net (code "32") (name "COL25") (class "Default")
      (node (ref "IC24") (pin "18") (pinfunction "O1_18") (pintype "open_collector"))
      (node (ref "IC25") (pin "18") (pinfunction "O1_18") (pintype "open_collector"))
      (node (ref "L1017") (pin "2") (pinfunction "2_2") (pintype "passive"))
      (node (ref "L121") (pin "2") (pinfunction "2_2") (pintype "passive"))
      (node (ref "L153") (pin "2") (pinfunction "2_2") (pintype "passive"))
      (node (ref "L185") (pin "2") (pinfunction "2_2") (pintype "passive"))
      (node (ref "L217") (pin "2") (pinfunction "2_2") (pintype "passive"))
      (node (ref "L249") (pin "2") (pinfunction "2_2") (pintype "passive"))
      (node (ref "L25") (pin "2") (pinfunction "2_2") (pintype "passive"))
      (node (ref "L281") (pin "2") (pinfunction "2_2") (pintype "passive"))
      (node (ref "L313") (pin "2") (pinfunction "2_2") (pintype "passive"))
      (node (ref "L345") (pin "2") (pinfunction "2_2") (pintype "passive"))
      (node (ref "L377") (pin "2") (pinfunction "2_2") (pintype "passive"))
      (node (ref "L409") (pin "2") (pinfunction "2_2") (pintype "passive"))
      (node (ref "L441") (pin "2") (pinfunction "2_2") (pintype "passive"))
      (node (ref "L473") (pin "2") (pinfunction "2_2") (pintype "passive"))
      (node (ref "L505") (pin "2") (pinfunction "2_2") (pintype "passive"))
      (node (ref "L537") (pin "2") (pinfunction "2_2") (pintype "passive"))
      (node (ref "L569") (pin "2") (pinfunction "2_2") (pintype "passive"))
      (node (ref "L57") (pin "2") (pinfunction "2_2") (pintype "passive"))
      (node (ref "L601") (pin "2") (pinfunction "2_2") (pintype "passive"))
      (node (ref "L633") (pin "2") (pinfunction "2_2") (pintype "passive"))
      (node (ref "L665") (pin "2") (pinfunction "2_2") (pintype "passive"))
      (node (ref "L697") (pin "2") (pinfunction "2_2") (pintype "passive"))
      (node (ref "L729") (pin "2") (pinfunction "2_2") (pintype "passive"))
      (node (ref "L761") (pin "2") (pinfunction "2_2") (pintype "passive"))
      (node (ref "L793") (pin "2") (pinfunction "2_2") (pintype "passive"))
      (node (ref "L825") (pin "2") (pinfunction "2_2") (pintype "passive"))
      (node (ref "L857") (pin "2") (pinfunction "2_2") (pintype "passive"))
      (node (ref "L889") (pin "2") (pinfunction "2_2") (pintype "passive"))
      (node (ref "L89") (pin "2") (pinfunction "2_2") (pintype "passive"))
      (node (ref "L921") (pin "2") (pinfunction "2_2") (pintype "passive"))
      (node (ref "L953") (pin "2") (pinfunction "2_2") (pintype "passive"))
      (node (ref "L985") (pin "2") (pinfunction "2_2") (pintype "passive"))
    )
    (net (code "33") (name "COL25-32_INHIBIT") (class "Default")
      (node (ref "IC23") (pin "23") (pinfunction "INH_23") (pintype "input"))
      (node (ref "IC3") (pin "9") (pinfunction "Y3_9") (pintype "output"))
    )
    (net (code "34") (name "COL26") (class "Default")
      (node (ref "IC24") (pin "17") (pinfunction "O2_17") (pintype "open_collector"))
      (node (ref "IC25") (pin "17") (pinfunction "O2_17") (pintype "open_collector"))
      (node (ref "L1018") (pin "2") (pinfunction "2_2") (pintype "passive"))
      (node (ref "L122") (pin "2") (pinfunction "2_2") (pintype "passive"))
      (node (ref "L154") (pin "2") (pinfunction "2_2") (pintype "passive"))
      (node (ref "L186") (pin "2") (pinfunction "2_2") (pintype "passive"))
      (node (ref "L218") (pin "2") (pinfunction "2_2") (pintype "passive"))
      (node (ref "L250") (pin "2") (pinfunction "2_2") (pintype "passive"))
      (node (ref "L26") (pin "2") (pinfunction "2_2") (pintype "passive"))
      (node (ref "L282") (pin "2") (pinfunction "2_2") (pintype "passive"))
      (node (ref "L314") (pin "2") (pinfunction "2_2") (pintype "passive"))
      (node (ref "L346") (pin "2") (pinfunction "2_2") (pintype "passive"))
      (node (ref "L378") (pin "2") (pinfunction "2_2") (pintype "passive"))
      (node (ref "L410") (pin "2") (pinfunction "2_2") (pintype "passive"))
      (node (ref "L442") (pin "2") (pinfunction "2_2") (pintype "passive"))
      (node (ref "L474") (pin "2") (pinfunction "2_2") (pintype "passive"))
      (node (ref "L506") (pin "2") (pinfunction "2_2") (pintype "passive"))
      (node (ref "L538") (pin "2") (pinfunction "2_2") (pintype "passive"))
      (node (ref "L570") (pin "2") (pinfunction "2_2") (pintype "passive"))
      (node (ref "L58") (pin "2") (pinfunction "2_2") (pintype "passive"))
      (node (ref "L602") (pin "2") (pinfunction "2_2") (pintype "passive"))
      (node (ref "L634") (pin "2") (pinfunction "2_2") (pintype "passive"))
      (node (ref "L666") (pin "2") (pinfunction "2_2") (pintype "passive"))
      (node (ref "L698") (pin "2") (pinfunction "2_2") (pintype "passive"))
      (node (ref "L730") (pin "2") (pinfunction "2_2") (pintype "passive"))
      (node (ref "L762") (pin "2") (pinfunction "2_2") (pintype "passive"))
      (node (ref "L794") (pin "2") (pinfunction "2_2") (pintype "passive"))
      (node (ref "L826") (pin "2") (pinfunction "2_2") (pintype "passive"))
      (node (ref "L858") (pin "2") (pinfunction "2_2") (pintype "passive"))
      (node (ref "L890") (pin "2") (pinfunction "2_2") (pintype "passive"))
      (node (ref "L90") (pin "2") (pinfunction "2_2") (pintype "passive"))
      (node (ref "L922") (pin "2") (pinfunction "2_2") (pintype "passive"))
      (node (ref "L954") (pin "2") (pinfunction "2_2") (pintype "passive"))
      (node (ref "L986") (pin "2") (pinfunction "2_2") (pintype "passive"))
    )
    (net (code "35") (name "COL27") (class "Default")
      (node (ref "IC24") (pin "16") (pinfunction "O3_16") (pintype "open_collector"))
      (node (ref "IC25") (pin "16") (pinfunction "O3_16") (pintype "open_collector"))
      (node (ref "L1019") (pin "2") (pinfunction "2_2") (pintype "passive"))
      (node (ref "L123") (pin "2") (pinfunction "2_2") (pintype "passive"))
      (node (ref "L155") (pin "2") (pinfunction "2_2") (pintype "passive"))
      (node (ref "L187") (pin "2") (pinfunction "2_2") (pintype "passive"))
      (node (ref "L219") (pin "2") (pinfunction "2_2") (pintype "passive"))
      (node (ref "L251") (pin "2") (pinfunction "2_2") (pintype "passive"))
      (node (ref "L27") (pin "2") (pinfunction "2_2") (pintype "passive"))
      (node (ref "L283") (pin "2") (pinfunction "2_2") (pintype "passive"))
      (node (ref "L315") (pin "2") (pinfunction "2_2") (pintype "passive"))
      (node (ref "L347") (pin "2") (pinfunction "2_2") (pintype "passive"))
      (node (ref "L379") (pin "2") (pinfunction "2_2") (pintype "passive"))
      (node (ref "L411") (pin "2") (pinfunction "2_2") (pintype "passive"))
      (node (ref "L443") (pin "2") (pinfunction "2_2") (pintype "passive"))
      (node (ref "L475") (pin "2") (pinfunction "2_2") (pintype "passive"))
      (node (ref "L507") (pin "2") (pinfunction "2_2") (pintype "passive"))
      (node (ref "L539") (pin "2") (pinfunction "2_2") (pintype "passive"))
      (node (ref "L571") (pin "2") (pinfunction "2_2") (pintype "passive"))
      (node (ref "L59") (pin "2") (pinfunction "2_2") (pintype "passive"))
      (node (ref "L603") (pin "2") (pinfunction "2_2") (pintype "passive"))
      (node (ref "L635") (pin "2") (pinfunction "2_2") (pintype "passive"))
      (node (ref "L667") (pin "2") (pinfunction "2_2") (pintype "passive"))
      (node (ref "L699") (pin "2") (pinfunction "2_2") (pintype "passive"))
      (node (ref "L731") (pin "2") (pinfunction "2_2") (pintype "passive"))
      (node (ref "L763") (pin "2") (pinfunction "2_2") (pintype "passive"))
      (node (ref "L795") (pin "2") (pinfunction "2_2") (pintype "passive"))
      (node (ref "L827") (pin "2") (pinfunction "2_2") (pintype "passive"))
      (node (ref "L859") (pin "2") (pinfunction "2_2") (pintype "passive"))
      (node (ref "L891") (pin "2") (pinfunction "2_2") (pintype "passive"))
      (node (ref "L91") (pin "2") (pinfunction "2_2") (pintype "passive"))
      (node (ref "L923") (pin "2") (pinfunction "2_2") (pintype "passive"))
      (node (ref "L955") (pin "2") (pinfunction "2_2") (pintype "passive"))
      (node (ref "L987") (pin "2") (pinfunction "2_2") (pintype "passive"))
    )
    (net (code "36") (name "COL28") (class "Default")
      (node (ref "IC24") (pin "15") (pinfunction "O4_15") (pintype "open_collector"))
      (node (ref "IC25") (pin "15") (pinfunction "O4_15") (pintype "open_collector"))
      (node (ref "L1020") (pin "2") (pinfunction "2_2") (pintype "passive"))
      (node (ref "L124") (pin "2") (pinfunction "2_2") (pintype "passive"))
      (node (ref "L156") (pin "2") (pinfunction "2_2") (pintype "passive"))
      (node (ref "L188") (pin "2") (pinfunction "2_2") (pintype "passive"))
      (node (ref "L220") (pin "2") (pinfunction "2_2") (pintype "passive"))
      (node (ref "L252") (pin "2") (pinfunction "2_2") (pintype "passive"))
      (node (ref "L28") (pin "2") (pinfunction "2_2") (pintype "passive"))
      (node (ref "L284") (pin "2") (pinfunction "2_2") (pintype "passive"))
      (node (ref "L316") (pin "2") (pinfunction "2_2") (pintype "passive"))
      (node (ref "L348") (pin "2") (pinfunction "2_2") (pintype "passive"))
      (node (ref "L380") (pin "2") (pinfunction "2_2") (pintype "passive"))
      (node (ref "L412") (pin "2") (pinfunction "2_2") (pintype "passive"))
      (node (ref "L444") (pin "2") (pinfunction "2_2") (pintype "passive"))
      (node (ref "L476") (pin "2") (pinfunction "2_2") (pintype "passive"))
      (node (ref "L508") (pin "2") (pinfunction "2_2") (pintype "passive"))
      (node (ref "L540") (pin "2") (pinfunction "2_2") (pintype "passive"))
      (node (ref "L572") (pin "2") (pinfunction "2_2") (pintype "passive"))
      (node (ref "L60") (pin "2") (pinfunction "2_2") (pintype "passive"))
      (node (ref "L604") (pin "2") (pinfunction "2_2") (pintype "passive"))
      (node (ref "L636") (pin "2") (pinfunction "2_2") (pintype "passive"))
      (node (ref "L668") (pin "2") (pinfunction "2_2") (pintype "passive"))
      (node (ref "L700") (pin "2") (pinfunction "2_2") (pintype "passive"))
      (node (ref "L732") (pin "2") (pinfunction "2_2") (pintype "passive"))
      (node (ref "L764") (pin "2") (pinfunction "2_2") (pintype "passive"))
      (node (ref "L796") (pin "2") (pinfunction "2_2") (pintype "passive"))
      (node (ref "L828") (pin "2") (pinfunction "2_2") (pintype "passive"))
      (node (ref "L860") (pin "2") (pinfunction "2_2") (pintype "passive"))
      (node (ref "L892") (pin "2") (pinfunction "2_2") (pintype "passive"))
      (node (ref "L92") (pin "2") (pinfunction "2_2") (pintype "passive"))
      (node (ref "L924") (pin "2") (pinfunction "2_2") (pintype "passive"))
      (node (ref "L956") (pin "2") (pinfunction "2_2") (pintype "passive"))
      (node (ref "L988") (pin "2") (pinfunction "2_2") (pintype "passive"))
    )
    (net (code "37") (name "COL29") (class "Default")
      (node (ref "IC24") (pin "14") (pinfunction "O5_14") (pintype "open_collector"))
      (node (ref "IC25") (pin "14") (pinfunction "O5_14") (pintype "open_collector"))
      (node (ref "L1021") (pin "2") (pinfunction "2_2") (pintype "passive"))
      (node (ref "L125") (pin "2") (pinfunction "2_2") (pintype "passive"))
      (node (ref "L157") (pin "2") (pinfunction "2_2") (pintype "passive"))
      (node (ref "L189") (pin "2") (pinfunction "2_2") (pintype "passive"))
      (node (ref "L221") (pin "2") (pinfunction "2_2") (pintype "passive"))
      (node (ref "L253") (pin "2") (pinfunction "2_2") (pintype "passive"))
      (node (ref "L285") (pin "2") (pinfunction "2_2") (pintype "passive"))
      (node (ref "L29") (pin "2") (pinfunction "2_2") (pintype "passive"))
      (node (ref "L317") (pin "2") (pinfunction "2_2") (pintype "passive"))
      (node (ref "L349") (pin "2") (pinfunction "2_2") (pintype "passive"))
      (node (ref "L381") (pin "2") (pinfunction "2_2") (pintype "passive"))
      (node (ref "L413") (pin "2") (pinfunction "2_2") (pintype "passive"))
      (node (ref "L445") (pin "2") (pinfunction "2_2") (pintype "passive"))
      (node (ref "L477") (pin "2") (pinfunction "2_2") (pintype "passive"))
      (node (ref "L509") (pin "2") (pinfunction "2_2") (pintype "passive"))
      (node (ref "L541") (pin "2") (pinfunction "2_2") (pintype "passive"))
      (node (ref "L573") (pin "2") (pinfunction "2_2") (pintype "passive"))
      (node (ref "L605") (pin "2") (pinfunction "2_2") (pintype "passive"))
      (node (ref "L61") (pin "2") (pinfunction "2_2") (pintype "passive"))
      (node (ref "L637") (pin "2") (pinfunction "2_2") (pintype "passive"))
      (node (ref "L669") (pin "2") (pinfunction "2_2") (pintype "passive"))
      (node (ref "L701") (pin "2") (pinfunction "2_2") (pintype "passive"))
      (node (ref "L733") (pin "2") (pinfunction "2_2") (pintype "passive"))
      (node (ref "L765") (pin "2") (pinfunction "2_2") (pintype "passive"))
      (node (ref "L797") (pin "2") (pinfunction "2_2") (pintype "passive"))
      (node (ref "L829") (pin "2") (pinfunction "2_2") (pintype "passive"))
      (node (ref "L861") (pin "2") (pinfunction "2_2") (pintype "passive"))
      (node (ref "L893") (pin "2") (pinfunction "2_2") (pintype "passive"))
      (node (ref "L925") (pin "2") (pinfunction "2_2") (pintype "passive"))
      (node (ref "L93") (pin "2") (pinfunction "2_2") (pintype "passive"))
      (node (ref "L957") (pin "2") (pinfunction "2_2") (pintype "passive"))
      (node (ref "L989") (pin "2") (pinfunction "2_2") (pintype "passive"))
    )
    (net (code "38") (name "COL30") (class "Default")
      (node (ref "IC24") (pin "13") (pinfunction "O6_13") (pintype "open_collector"))
      (node (ref "IC25") (pin "13") (pinfunction "O6_13") (pintype "open_collector"))
      (node (ref "L1022") (pin "2") (pinfunction "2_2") (pintype "passive"))
      (node (ref "L126") (pin "2") (pinfunction "2_2") (pintype "passive"))
      (node (ref "L158") (pin "2") (pinfunction "2_2") (pintype "passive"))
      (node (ref "L190") (pin "2") (pinfunction "2_2") (pintype "passive"))
      (node (ref "L222") (pin "2") (pinfunction "2_2") (pintype "passive"))
      (node (ref "L254") (pin "2") (pinfunction "2_2") (pintype "passive"))
      (node (ref "L286") (pin "2") (pinfunction "2_2") (pintype "passive"))
      (node (ref "L30") (pin "2") (pinfunction "2_2") (pintype "passive"))
      (node (ref "L318") (pin "2") (pinfunction "2_2") (pintype "passive"))
      (node (ref "L350") (pin "2") (pinfunction "2_2") (pintype "passive"))
      (node (ref "L382") (pin "2") (pinfunction "2_2") (pintype "passive"))
      (node (ref "L414") (pin "2") (pinfunction "2_2") (pintype "passive"))
      (node (ref "L446") (pin "2") (pinfunction "2_2") (pintype "passive"))
      (node (ref "L478") (pin "2") (pinfunction "2_2") (pintype "passive"))
      (node (ref "L510") (pin "2") (pinfunction "2_2") (pintype "passive"))
      (node (ref "L542") (pin "2") (pinfunction "2_2") (pintype "passive"))
      (node (ref "L574") (pin "2") (pinfunction "2_2") (pintype "passive"))
      (node (ref "L606") (pin "2") (pinfunction "2_2") (pintype "passive"))
      (node (ref "L62") (pin "2") (pinfunction "2_2") (pintype "passive"))
      (node (ref "L638") (pin "2") (pinfunction "2_2") (pintype "passive"))
      (node (ref "L670") (pin "2") (pinfunction "2_2") (pintype "passive"))
      (node (ref "L702") (pin "2") (pinfunction "2_2") (pintype "passive"))
      (node (ref "L734") (pin "2") (pinfunction "2_2") (pintype "passive"))
      (node (ref "L766") (pin "2") (pinfunction "2_2") (pintype "passive"))
      (node (ref "L798") (pin "2") (pinfunction "2_2") (pintype "passive"))
      (node (ref "L830") (pin "2") (pinfunction "2_2") (pintype "passive"))
      (node (ref "L862") (pin "2") (pinfunction "2_2") (pintype "passive"))
      (node (ref "L894") (pin "2") (pinfunction "2_2") (pintype "passive"))
      (node (ref "L926") (pin "2") (pinfunction "2_2") (pintype "passive"))
      (node (ref "L94") (pin "2") (pinfunction "2_2") (pintype "passive"))
      (node (ref "L958") (pin "2") (pinfunction "2_2") (pintype "passive"))
      (node (ref "L990") (pin "2") (pinfunction "2_2") (pintype "passive"))
    )
    (net (code "39") (name "COL31") (class "Default")
      (node (ref "IC24") (pin "12") (pinfunction "O7_12") (pintype "open_collector"))
      (node (ref "IC25") (pin "12") (pinfunction "O7_12") (pintype "open_collector"))
      (node (ref "L1023") (pin "2") (pinfunction "2_2") (pintype "passive"))
      (node (ref "L127") (pin "2") (pinfunction "2_2") (pintype "passive"))
      (node (ref "L159") (pin "2") (pinfunction "2_2") (pintype "passive"))
      (node (ref "L191") (pin "2") (pinfunction "2_2") (pintype "passive"))
      (node (ref "L223") (pin "2") (pinfunction "2_2") (pintype "passive"))
      (node (ref "L255") (pin "2") (pinfunction "2_2") (pintype "passive"))
      (node (ref "L287") (pin "2") (pinfunction "2_2") (pintype "passive"))
      (node (ref "L31") (pin "2") (pinfunction "2_2") (pintype "passive"))
      (node (ref "L319") (pin "2") (pinfunction "2_2") (pintype "passive"))
      (node (ref "L351") (pin "2") (pinfunction "2_2") (pintype "passive"))
      (node (ref "L383") (pin "2") (pinfunction "2_2") (pintype "passive"))
      (node (ref "L415") (pin "2") (pinfunction "2_2") (pintype "passive"))
      (node (ref "L447") (pin "2") (pinfunction "2_2") (pintype "passive"))
      (node (ref "L479") (pin "2") (pinfunction "2_2") (pintype "passive"))
      (node (ref "L511") (pin "2") (pinfunction "2_2") (pintype "passive"))
      (node (ref "L543") (pin "2") (pinfunction "2_2") (pintype "passive"))
      (node (ref "L575") (pin "2") (pinfunction "2_2") (pintype "passive"))
      (node (ref "L607") (pin "2") (pinfunction "2_2") (pintype "passive"))
      (node (ref "L63") (pin "2") (pinfunction "2_2") (pintype "passive"))
      (node (ref "L639") (pin "2") (pinfunction "2_2") (pintype "passive"))
      (node (ref "L671") (pin "2") (pinfunction "2_2") (pintype "passive"))
      (node (ref "L703") (pin "2") (pinfunction "2_2") (pintype "passive"))
      (node (ref "L735") (pin "2") (pinfunction "2_2") (pintype "passive"))
      (node (ref "L767") (pin "2") (pinfunction "2_2") (pintype "passive"))
      (node (ref "L799") (pin "2") (pinfunction "2_2") (pintype "passive"))
      (node (ref "L831") (pin "2") (pinfunction "2_2") (pintype "passive"))
      (node (ref "L863") (pin "2") (pinfunction "2_2") (pintype "passive"))
      (node (ref "L895") (pin "2") (pinfunction "2_2") (pintype "passive"))
      (node (ref "L927") (pin "2") (pinfunction "2_2") (pintype "passive"))
      (node (ref "L95") (pin "2") (pinfunction "2_2") (pintype "passive"))
      (node (ref "L959") (pin "2") (pinfunction "2_2") (pintype "passive"))
      (node (ref "L991") (pin "2") (pinfunction "2_2") (pintype "passive"))
    )
    (net (code "40") (name "COL32") (class "Default")
      (node (ref "IC24") (pin "11") (pinfunction "O8_11") (pintype "open_collector"))
      (node (ref "IC25") (pin "11") (pinfunction "O8_11") (pintype "open_collector"))
      (node (ref "L1024") (pin "2") (pinfunction "2_2") (pintype "passive"))
      (node (ref "L128") (pin "2") (pinfunction "2_2") (pintype "passive"))
      (node (ref "L160") (pin "2") (pinfunction "2_2") (pintype "passive"))
      (node (ref "L192") (pin "2") (pinfunction "2_2") (pintype "passive"))
      (node (ref "L224") (pin "2") (pinfunction "2_2") (pintype "passive"))
      (node (ref "L256") (pin "2") (pinfunction "2_2") (pintype "passive"))
      (node (ref "L288") (pin "2") (pinfunction "2_2") (pintype "passive"))
      (node (ref "L32") (pin "2") (pinfunction "2_2") (pintype "passive"))
      (node (ref "L320") (pin "2") (pinfunction "2_2") (pintype "passive"))
      (node (ref "L352") (pin "2") (pinfunction "2_2") (pintype "passive"))
      (node (ref "L384") (pin "2") (pinfunction "2_2") (pintype "passive"))
      (node (ref "L416") (pin "2") (pinfunction "2_2") (pintype "passive"))
      (node (ref "L448") (pin "2") (pinfunction "2_2") (pintype "passive"))
      (node (ref "L480") (pin "2") (pinfunction "2_2") (pintype "passive"))
      (node (ref "L512") (pin "2") (pinfunction "2_2") (pintype "passive"))
      (node (ref "L544") (pin "2") (pinfunction "2_2") (pintype "passive"))
      (node (ref "L576") (pin "2") (pinfunction "2_2") (pintype "passive"))
      (node (ref "L608") (pin "2") (pinfunction "2_2") (pintype "passive"))
      (node (ref "L64") (pin "2") (pinfunction "2_2") (pintype "passive"))
      (node (ref "L640") (pin "2") (pinfunction "2_2") (pintype "passive"))
      (node (ref "L672") (pin "2") (pinfunction "2_2") (pintype "passive"))
      (node (ref "L704") (pin "2") (pinfunction "2_2") (pintype "passive"))
      (node (ref "L736") (pin "2") (pinfunction "2_2") (pintype "passive"))
      (node (ref "L768") (pin "2") (pinfunction "2_2") (pintype "passive"))
      (node (ref "L800") (pin "2") (pinfunction "2_2") (pintype "passive"))
      (node (ref "L832") (pin "2") (pinfunction "2_2") (pintype "passive"))
      (node (ref "L864") (pin "2") (pinfunction "2_2") (pintype "passive"))
      (node (ref "L896") (pin "2") (pinfunction "2_2") (pintype "passive"))
      (node (ref "L928") (pin "2") (pinfunction "2_2") (pintype "passive"))
      (node (ref "L96") (pin "2") (pinfunction "2_2") (pintype "passive"))
      (node (ref "L960") (pin "2") (pinfunction "2_2") (pintype "passive"))
      (node (ref "L992") (pin "2") (pinfunction "2_2") (pintype "passive"))
    )
    (net (code "41") (name "COL_RESET") (class "Default")
      (node (ref "CONN1") (pin "8") (pinfunction "8_8") (pintype "passive"))
      (node (ref "CONN2") (pin "8") (pinfunction "8_8") (pintype "passive"))
      (node (ref "IC1") (pin "3") (pinfunction "D2_3") (pintype "input"))
    )
    (net (code "42") (name "COL_SEL1") (class "Default")
      (node (ref "IC14") (pin "2") (pinfunction "D1_2") (pintype "input"))
      (node (ref "IC17") (pin "2") (pinfunction "D1_2") (pintype "input"))
      (node (ref "IC20") (pin "2") (pinfunction "D1_2") (pintype "input"))
      (node (ref "IC23") (pin "2") (pinfunction "D1_2") (pintype "input"))
      (node (ref "IC4") (pin "12") (pinfunction "Q1_12") (pintype "output"))
    )
    (net (code "43") (name "COL_SEL2") (class "Default")
      (node (ref "IC14") (pin "3") (pinfunction "D2_3") (pintype "input"))
      (node (ref "IC17") (pin "3") (pinfunction "D2_3") (pintype "input"))
      (node (ref "IC20") (pin "3") (pinfunction "D2_3") (pintype "input"))
      (node (ref "IC23") (pin "3") (pinfunction "D2_3") (pintype "input"))
      (node (ref "IC4") (pin "11") (pinfunction "Q2_11") (pintype "output"))
    )
    (net (code "44") (name "COL_SEL3") (class "Default")
      (node (ref "IC14") (pin "21") (pinfunction "D3_21") (pintype "input"))
      (node (ref "IC17") (pin "21") (pinfunction "D3_21") (pintype "input"))
      (node (ref "IC20") (pin "21") (pinfunction "D3_21") (pintype "input"))
      (node (ref "IC23") (pin "21") (pinfunction "D3_21") (pintype "input"))
      (node (ref "IC4") (pin "9") (pinfunction "Q3_9") (pintype "output"))
    )
    (net (code "45") (name "DB_ENABLE_1") (class "Default")
      (node (ref "CONN1") (pin "2") (pinfunction "2_2") (pintype "passive"))
      (node (ref "IC1") (pin "13") (pinfunction "C12_13") (pintype "input"))
      (node (ref "IC1") (pin "4") (pinfunction "C34_4") (pintype "input"))
    )
    (net (code "46") (name "DB_ENABLE_2") (class "Default")
      (node (ref "CONN1") (pin "3") (pinfunction "3_3") (pintype "passive"))
      (node (ref "CONN2") (pin "2") (pinfunction "2_2") (pintype "passive"))
    )
    (net (code "47") (name "DB_ENABLE_3") (class "Default")
      (node (ref "CONN1") (pin "4") (pinfunction "4_4") (pintype "passive"))
      (node (ref "CONN2") (pin "3") (pinfunction "3_3") (pintype "passive"))
    )
    (net (code "48") (name "DB_ENABLE_4") (class "Default")
      (node (ref "CONN1") (pin "5") (pinfunction "5_5") (pintype "passive"))
      (node (ref "CONN2") (pin "4") (pinfunction "4_4") (pintype "passive"))
    )
    (net (code "49") (name "GND") (class "Default")
      (node (ref "CONN1") (pin "1") (pinfunction "1_1") (pintype "passive"))
      (node (ref "CONN1") (pin "6") (pinfunction "6_6") (pintype "passive"))
      (node (ref "CONN2") (pin "1") (pinfunction "1_1") (pintype "passive"))
      (node (ref "CONN2") (pin "5") (pinfunction "5_5") (pintype "passive"))
      (node (ref "CONN2") (pin "6") (pinfunction "6_6") (pintype "passive"))
      (node (ref "IC1") (pin "12") (pinfunction "GND_12") (pintype "power_in"))
      (node (ref "IC10") (pin "10") (pinfunction "GND_10") (pintype "passive"))
      (node (ref "IC11") (pin "12") (pinfunction "VSS_12") (pintype "power_in"))
      (node (ref "IC12") (pin "10") (pinfunction "GND_10") (pintype "passive"))
      (node (ref "IC13") (pin "9") (pinfunction "GND_9") (pintype "power_in"))
      (node (ref "IC14") (pin "12") (pinfunction "VSS_12") (pintype "power_in"))
      (node (ref "IC15") (pin "10") (pinfunction "GND_10") (pintype "passive"))
      (node (ref "IC16") (pin "9") (pinfunction "GND_9") (pintype "power_in"))
      (node (ref "IC17") (pin "12") (pinfunction "VSS_12") (pintype "power_in"))
      (node (ref "IC18") (pin "10") (pinfunction "GND_10") (pintype "passive"))
      (node (ref "IC19") (pin "9") (pinfunction "GND_9") (pintype "power_in"))
      (node (ref "IC2") (pin "7") (pinfunction "VSS_7") (pintype "power_in"))
      (node (ref "IC20") (pin "12") (pinfunction "VSS_12") (pintype "power_in"))
      (node (ref "IC21") (pin "10") (pinfunction "GND_10") (pintype "passive"))
      (node (ref "IC22") (pin "9") (pinfunction "GND_9") (pintype "power_in"))
      (node (ref "IC23") (pin "12") (pinfunction "VSS_12") (pintype "power_in"))
      (node (ref "IC24") (pin "10") (pinfunction "GND_10") (pintype "passive"))
      (node (ref "IC25") (pin "9") (pinfunction "GND_9") (pintype "power_in"))
      (node (ref "IC26") (pin "12") (pinfunction "VSS_12") (pintype "power_in"))
      (node (ref "IC27") (pin "10") (pinfunction "GND_10") (pintype "passive"))
      (node (ref "IC28") (pin "9") (pinfunction "GND_9") (pintype "power_in"))
      (node (ref "IC3") (pin "8") (pinfunction "GND_8") (pintype "power_in"))
      (node (ref "IC4") (pin "7") (pinfunction "VSS_7") (pintype "power_in"))
      (node (ref "IC5") (pin "12") (pinfunction "VSS_12") (pintype "power_in"))
      (node (ref "IC6") (pin "9") (pinfunction "GND_9") (pintype "power_in"))
      (node (ref "IC7") (pin "10") (pinfunction "GND_10") (pintype "passive"))
      (node (ref "IC8") (pin "12") (pinfunction "VSS_12") (pintype "power_in"))
      (node (ref "IC9") (pin "9") (pinfunction "GND_9") (pintype "power_in"))
    )
    (net (code "50") (name "Net-(D1-COM)") (class "Default")
      (node (ref "D1") (pin "3") (pinfunction "COM_3") (pintype "bidirectional"))
      (node (ref "L1") (pin "1") (pinfunction "1_1") (pintype "passive"))
    )
    (net (code "51") (name "Net-(D2-COM)") (class "Default")
      (node (ref "D2") (pin "3") (pinfunction "COM_3") (pintype "bidirectional"))
      (node (ref "L2") (pin "1") (pinfunction "1_1") (pintype "passive"))
    )
    (net (code "52") (name "Net-(D3-COM)") (class "Default")
      (node (ref "D3") (pin "3") (pinfunction "COM_3") (pintype "bidirectional"))
      (node (ref "L3") (pin "1") (pinfunction "1_1") (pintype "passive"))
    )
    (net (code "53") (name "Net-(D4-COM)") (class "Default")
      (node (ref "D4") (pin "3") (pinfunction "COM_3") (pintype "bidirectional"))
      (node (ref "L4") (pin "1") (pinfunction "1_1") (pintype "passive"))
    )
    (net (code "54") (name "Net-(D5-COM)") (class "Default")
      (node (ref "D5") (pin "3") (pinfunction "COM_3") (pintype "bidirectional"))
      (node (ref "L5") (pin "1") (pinfunction "1_1") (pintype "passive"))
    )
    (net (code "55") (name "Net-(D6-COM)") (class "Default")
      (node (ref "D6") (pin "3") (pinfunction "COM_3") (pintype "bidirectional"))
      (node (ref "L6") (pin "1") (pinfunction "1_1") (pintype "passive"))
    )
    (net (code "56") (name "Net-(D7-COM)") (class "Default")
      (node (ref "D7") (pin "3") (pinfunction "COM_3") (pintype "bidirectional"))
      (node (ref "L7") (pin "1") (pinfunction "1_1") (pintype "passive"))
    )
    (net (code "57") (name "Net-(D8-COM)") (class "Default")
      (node (ref "D8") (pin "3") (pinfunction "COM_3") (pintype "bidirectional"))
      (node (ref "L8") (pin "1") (pinfunction "1_1") (pintype "passive"))
    )
    (net (code "58") (name "Net-(D9-COM)") (class "Default")
      (node (ref "D9") (pin "3") (pinfunction "COM_3") (pintype "bidirectional"))
      (node (ref "L9") (pin "1") (pinfunction "1_1") (pintype "passive"))
    )
    (net (code "59") (name "Net-(D10-COM)") (class "Default")
      (node (ref "D10") (pin "3") (pinfunction "COM_3") (pintype "bidirectional"))
      (node (ref "L10") (pin "1") (pinfunction "1_1") (pintype "passive"))
    )
    (net (code "60") (name "Net-(D11-COM)") (class "Default")
      (node (ref "D11") (pin "3") (pinfunction "COM_3") (pintype "bidirectional"))
      (node (ref "L11") (pin "1") (pinfunction "1_1") (pintype "passive"))
    )
    (net (code "61") (name "Net-(D12-COM)") (class "Default")
      (node (ref "D12") (pin "3") (pinfunction "COM_3") (pintype "bidirectional"))
      (node (ref "L12") (pin "1") (pinfunction "1_1") (pintype "passive"))
    )
    (net (code "62") (name "Net-(D13-COM)") (class "Default")
      (node (ref "D13") (pin "3") (pinfunction "COM_3") (pintype "bidirectional"))
      (node (ref "L13") (pin "1") (pinfunction "1_1") (pintype "passive"))
    )
    (net (code "63") (name "Net-(D14-COM)") (class "Default")
      (node (ref "D14") (pin "3") (pinfunction "COM_3") (pintype "bidirectional"))
      (node (ref "L14") (pin "1") (pinfunction "1_1") (pintype "passive"))
    )
    (net (code "64") (name "Net-(D15-COM)") (class "Default")
      (node (ref "D15") (pin "3") (pinfunction "COM_3") (pintype "bidirectional"))
      (node (ref "L15") (pin "1") (pinfunction "1_1") (pintype "passive"))
    )
    (net (code "65") (name "Net-(D16-COM)") (class "Default")
      (node (ref "D16") (pin "3") (pinfunction "COM_3") (pintype "bidirectional"))
      (node (ref "L16") (pin "1") (pinfunction "1_1") (pintype "passive"))
    )
    (net (code "66") (name "Net-(D17-COM)") (class "Default")
      (node (ref "D17") (pin "3") (pinfunction "COM_3") (pintype "bidirectional"))
      (node (ref "L17") (pin "1") (pinfunction "1_1") (pintype "passive"))
    )
    (net (code "67") (name "Net-(D18-COM)") (class "Default")
      (node (ref "D18") (pin "3") (pinfunction "COM_3") (pintype "bidirectional"))
      (node (ref "L18") (pin "1") (pinfunction "1_1") (pintype "passive"))
    )
    (net (code "68") (name "Net-(D19-COM)") (class "Default")
      (node (ref "D19") (pin "3") (pinfunction "COM_3") (pintype "bidirectional"))
      (node (ref "L19") (pin "1") (pinfunction "1_1") (pintype "passive"))
    )
    (net (code "69") (name "Net-(D20-COM)") (class "Default")
      (node (ref "D20") (pin "3") (pinfunction "COM_3") (pintype "bidirectional"))
      (node (ref "L20") (pin "1") (pinfunction "1_1") (pintype "passive"))
    )
    (net (code "70") (name "Net-(D21-COM)") (class "Default")
      (node (ref "D21") (pin "3") (pinfunction "COM_3") (pintype "bidirectional"))
      (node (ref "L21") (pin "1") (pinfunction "1_1") (pintype "passive"))
    )
    (net (code "71") (name "Net-(D22-COM)") (class "Default")
      (node (ref "D22") (pin "3") (pinfunction "COM_3") (pintype "bidirectional"))
      (node (ref "L22") (pin "1") (pinfunction "1_1") (pintype "passive"))
    )
    (net (code "72") (name "Net-(D23-COM)") (class "Default")
      (node (ref "D23") (pin "3") (pinfunction "COM_3") (pintype "bidirectional"))
      (node (ref "L23") (pin "1") (pinfunction "1_1") (pintype "passive"))
    )
    (net (code "73") (name "Net-(D24-COM)") (class "Default")
      (node (ref "D24") (pin "3") (pinfunction "COM_3") (pintype "bidirectional"))
      (node (ref "L24") (pin "1") (pinfunction "1_1") (pintype "passive"))
    )
    (net (code "74") (name "Net-(D25-COM)") (class "Default")
      (node (ref "D25") (pin "3") (pinfunction "COM_3") (pintype "bidirectional"))
      (node (ref "L25") (pin "1") (pinfunction "1_1") (pintype "passive"))
    )
    (net (code "75") (name "Net-(D26-COM)") (class "Default")
      (node (ref "D26") (pin "3") (pinfunction "COM_3") (pintype "bidirectional"))
      (node (ref "L26") (pin "1") (pinfunction "1_1") (pintype "passive"))
    )
    (net (code "76") (name "Net-(D27-COM)") (class "Default")
      (node (ref "D27") (pin "3") (pinfunction "COM_3") (pintype "bidirectional"))
      (node (ref "L27") (pin "1") (pinfunction "1_1") (pintype "passive"))
    )
    (net (code "77") (name "Net-(D28-COM)") (class "Default")
      (node (ref "D28") (pin "3") (pinfunction "COM_3") (pintype "bidirectional"))
      (node (ref "L28") (pin "1") (pinfunction "1_1") (pintype "passive"))
    )
    (net (code "78") (name "Net-(D29-COM)") (class "Default")
      (node (ref "D29") (pin "3") (pinfunction "COM_3") (pintype "bidirectional"))
      (node (ref "L29") (pin "1") (pinfunction "1_1") (pintype "passive"))
    )
    (net (code "79") (name "Net-(D30-COM)") (class "Default")
      (node (ref "D30") (pin "3") (pinfunction "COM_3") (pintype "bidirectional"))
      (node (ref "L30") (pin "1") (pinfunction "1_1") (pintype "passive"))
    )
    (net (code "80") (name "Net-(D31-COM)") (class "Default")
      (node (ref "D31") (pin "3") (pinfunction "COM_3") (pintype "bidirectional"))
      (node (ref "L31") (pin "1") (pinfunction "1_1") (pintype "passive"))
    )
    (net (code "81") (name "Net-(D32-COM)") (class "Default")
      (node (ref "D32") (pin "3") (pinfunction "COM_3") (pintype "bidirectional"))
      (node (ref "L32") (pin "1") (pinfunction "1_1") (pintype "passive"))
    )
    (net (code "82") (name "Net-(D33-COM)") (class "Default")
      (node (ref "D33") (pin "3") (pinfunction "COM_3") (pintype "bidirectional"))
      (node (ref "L33") (pin "1") (pinfunction "1_1") (pintype "passive"))
    )
    (net (code "83") (name "Net-(D34-COM)") (class "Default")
      (node (ref "D34") (pin "3") (pinfunction "COM_3") (pintype "bidirectional"))
      (node (ref "L34") (pin "1") (pinfunction "1_1") (pintype "passive"))
    )
    (net (code "84") (name "Net-(D35-COM)") (class "Default")
      (node (ref "D35") (pin "3") (pinfunction "COM_3") (pintype "bidirectional"))
      (node (ref "L35") (pin "1") (pinfunction "1_1") (pintype "passive"))
    )
    (net (code "85") (name "Net-(D36-COM)") (class "Default")
      (node (ref "D36") (pin "3") (pinfunction "COM_3") (pintype "bidirectional"))
      (node (ref "L36") (pin "1") (pinfunction "1_1") (pintype "passive"))
    )
    (net (code "86") (name "Net-(D37-COM)") (class "Default")
      (node (ref "D37") (pin "3") (pinfunction "COM_3") (pintype "bidirectional"))
      (node (ref "L37") (pin "1") (pinfunction "1_1") (pintype "passive"))
    )
    (net (code "87") (name "Net-(D38-COM)") (class "Default")
      (node (ref "D38") (pin "3") (pinfunction "COM_3") (pintype "bidirectional"))
      (node (ref "L38") (pin "1") (pinfunction "1_1") (pintype "passive"))
    )
    (net (code "88") (name "Net-(D39-COM)") (class "Default")
      (node (ref "D39") (pin "3") (pinfunction "COM_3") (pintype "bidirectional"))
      (node (ref "L39") (pin "1") (pinfunction "1_1") (pintype "passive"))
    )
    (net (code "89") (name "Net-(D40-COM)") (class "Default")
      (node (ref "D40") (pin "3") (pinfunction "COM_3") (pintype "bidirectional"))
      (node (ref "L40") (pin "1") (pinfunction "1_1") (pintype "passive"))
    )
    (net (code "90") (name "Net-(D41-COM)") (class "Default")
      (node (ref "D41") (pin "3") (pinfunction "COM_3") (pintype "bidirectional"))
      (node (ref "L41") (pin "1") (pinfunction "1_1") (pintype "passive"))
    )
    (net (code "91") (name "Net-(D42-COM)") (class "Default")
      (node (ref "D42") (pin "3") (pinfunction "COM_3") (pintype "bidirectional"))
      (node (ref "L42") (pin "1") (pinfunction "1_1") (pintype "passive"))
    )
    (net (code "92") (name "Net-(D43-COM)") (class "Default")
      (node (ref "D43") (pin "3") (pinfunction "COM_3") (pintype "bidirectional"))
      (node (ref "L43") (pin "1") (pinfunction "1_1") (pintype "passive"))
    )
    (net (code "93") (name "Net-(D44-COM)") (class "Default")
      (node (ref "D44") (pin "3") (pinfunction "COM_3") (pintype "bidirectional"))
      (node (ref "L44") (pin "1") (pinfunction "1_1") (pintype "passive"))
    )
    (net (code "94") (name "Net-(D45-COM)") (class "Default")
      (node (ref "D45") (pin "3") (pinfunction "COM_3") (pintype "bidirectional"))
      (node (ref "L45") (pin "1") (pinfunction "1_1") (pintype "passive"))
    )
    (net (code "95") (name "Net-(D46-COM)") (class "Default")
      (node (ref "D46") (pin "3") (pinfunction "COM_3") (pintype "bidirectional"))
      (node (ref "L46") (pin "1") (pinfunction "1_1") (pintype "passive"))
    )
    (net (code "96") (name "Net-(D47-COM)") (class "Default")
      (node (ref "D47") (pin "3") (pinfunction "COM_3") (pintype "bidirectional"))
      (node (ref "L47") (pin "1") (pinfunction "1_1") (pintype "passive"))
    )
    (net (code "97") (name "Net-(D48-COM)") (class "Default")
      (node (ref "D48") (pin "3") (pinfunction "COM_3") (pintype "bidirectional"))
      (node (ref "L48") (pin "1") (pinfunction "1_1") (pintype "passive"))
    )
    (net (code "98") (name "Net-(D49-COM)") (class "Default")
      (node (ref "D49") (pin "3") (pinfunction "COM_3") (pintype "bidirectional"))
      (node (ref "L49") (pin "1") (pinfunction "1_1") (pintype "passive"))
    )
    (net (code "99") (name "Net-(D50-COM)") (class "Default")
      (node (ref "D50") (pin "3") (pinfunction "COM_3") (pintype "bidirectional"))
      (node (ref "L50") (pin "1") (pinfunction "1_1") (pintype "passive"))
    )
    (net (code "100") (name "Net-(D51-COM)") (class "Default")
      (node (ref "D51") (pin "3") (pinfunction "COM_3") (pintype "bidirectional"))
      (node (ref "L51") (pin "1") (pinfunction "1_1") (pintype "passive"))
    )
    (net (code "101") (name "Net-(D52-COM)") (class "Default")
      (node (ref "D52") (pin "3") (pinfunction "COM_3") (pintype "bidirectional"))
      (node (ref "L52") (pin "1") (pinfunction "1_1") (pintype "passive"))
    )
    (net (code "102") (name "Net-(D53-COM)") (class "Default")
      (node (ref "D53") (pin "3") (pinfunction "COM_3") (pintype "bidirectional"))
      (node (ref "L53") (pin "1") (pinfunction "1_1") (pintype "passive"))
    )
    (net (code "103") (name "Net-(D54-COM)") (class "Default")
      (node (ref "D54") (pin "3") (pinfunction "COM_3") (pintype "bidirectional"))
      (node (ref "L54") (pin "1") (pinfunction "1_1") (pintype "passive"))
    )
    (net (code "104") (name "Net-(D55-COM)") (class "Default")
      (node (ref "D55") (pin "3") (pinfunction "COM_3") (pintype "bidirectional"))
      (node (ref "L55") (pin "1") (pinfunction "1_1") (pintype "passive"))
    )
    (net (code "105") (name "Net-(D56-COM)") (class "Default")
      (node (ref "D56") (pin "3") (pinfunction "COM_3") (pintype "bidirectional"))
      (node (ref "L56") (pin "1") (pinfunction "1_1") (pintype "passive"))
    )
    (net (code "106") (name "Net-(D57-COM)") (class "Default")
      (node (ref "D57") (pin "3") (pinfunction "COM_3") (pintype "bidirectional"))
      (node (ref "L57") (pin "1") (pinfunction "1_1") (pintype "passive"))
    )
    (net (code "107") (name "Net-(D58-COM)") (class "Default")
      (node (ref "D58") (pin "3") (pinfunction "COM_3") (pintype "bidirectional"))
      (node (ref "L58") (pin "1") (pinfunction "1_1") (pintype "passive"))
    )
    (net (code "108") (name "Net-(D59-COM)") (class "Default")
      (node (ref "D59") (pin "3") (pinfunction "COM_3") (pintype "bidirectional"))
      (node (ref "L59") (pin "1") (pinfunction "1_1") (pintype "passive"))
    )
    (net (code "109") (name "Net-(D60-COM)") (class "Default")
      (node (ref "D60") (pin "3") (pinfunction "COM_3") (pintype "bidirectional"))
      (node (ref "L60") (pin "1") (pinfunction "1_1") (pintype "passive"))
    )
    (net (code "110") (name "Net-(D61-COM)") (class "Default")
      (node (ref "D61") (pin "3") (pinfunction "COM_3") (pintype "bidirectional"))
      (node (ref "L61") (pin "1") (pinfunction "1_1") (pintype "passive"))
    )
    (net (code "111") (name "Net-(D62-COM)") (class "Default")
      (node (ref "D62") (pin "3") (pinfunction "COM_3") (pintype "bidirectional"))
      (node (ref "L62") (pin "1") (pinfunction "1_1") (pintype "passive"))
    )
    (net (code "112") (name "Net-(D63-COM)") (class "Default")
      (node (ref "D63") (pin "3") (pinfunction "COM_3") (pintype "bidirectional"))
      (node (ref "L63") (pin "1") (pinfunction "1_1") (pintype "passive"))
    )
    (net (code "113") (name "Net-(D64-COM)") (class "Default")
      (node (ref "D64") (pin "3") (pinfunction "COM_3") (pintype "bidirectional"))
      (node (ref "L64") (pin "1") (pinfunction "1_1") (pintype "passive"))
    )
    (net (code "114") (name "Net-(D65-COM)") (class "Default")
      (node (ref "D65") (pin "3") (pinfunction "COM_3") (pintype "bidirectional"))
      (node (ref "L65") (pin "1") (pinfunction "1_1") (pintype "passive"))
    )
    (net (code "115") (name "Net-(D66-COM)") (class "Default")
      (node (ref "D66") (pin "3") (pinfunction "COM_3") (pintype "bidirectional"))
      (node (ref "L66") (pin "1") (pinfunction "1_1") (pintype "passive"))
    )
    (net (code "116") (name "Net-(D67-COM)") (class "Default")
      (node (ref "D67") (pin "3") (pinfunction "COM_3") (pintype "bidirectional"))
      (node (ref "L67") (pin "1") (pinfunction "1_1") (pintype "passive"))
    )
    (net (code "117") (name "Net-(D68-COM)") (class "Default")
      (node (ref "D68") (pin "3") (pinfunction "COM_3") (pintype "bidirectional"))
      (node (ref "L68") (pin "1") (pinfunction "1_1") (pintype "passive"))
    )
    (net (code "118") (name "Net-(D69-COM)") (class "Default")
      (node (ref "D69") (pin "3") (pinfunction "COM_3") (pintype "bidirectional"))
      (node (ref "L69") (pin "1") (pinfunction "1_1") (pintype "passive"))
    )
    (net (code "119") (name "Net-(D70-COM)") (class "Default")
      (node (ref "D70") (pin "3") (pinfunction "COM_3") (pintype "bidirectional"))
      (node (ref "L70") (pin "1") (pinfunction "1_1") (pintype "passive"))
    )
    (net (code "120") (name "Net-(D71-COM)") (class "Default")
      (node (ref "D71") (pin "3") (pinfunction "COM_3") (pintype "bidirectional"))
      (node (ref "L71") (pin "1") (pinfunction "1_1") (pintype "passive"))
    )
    (net (code "121") (name "Net-(D72-COM)") (class "Default")
      (node (ref "D72") (pin "3") (pinfunction "COM_3") (pintype "bidirectional"))
      (node (ref "L72") (pin "1") (pinfunction "1_1") (pintype "passive"))
    )
    (net (code "122") (name "Net-(D73-COM)") (class "Default")
      (node (ref "D73") (pin "3") (pinfunction "COM_3") (pintype "bidirectional"))
      (node (ref "L73") (pin "1") (pinfunction "1_1") (pintype "passive"))
    )
    (net (code "123") (name "Net-(D74-COM)") (class "Default")
      (node (ref "D74") (pin "3") (pinfunction "COM_3") (pintype "bidirectional"))
      (node (ref "L74") (pin "1") (pinfunction "1_1") (pintype "passive"))
    )
    (net (code "124") (name "Net-(D75-COM)") (class "Default")
      (node (ref "D75") (pin "3") (pinfunction "COM_3") (pintype "bidirectional"))
      (node (ref "L75") (pin "1") (pinfunction "1_1") (pintype "passive"))
    )
    (net (code "125") (name "Net-(D76-COM)") (class "Default")
      (node (ref "D76") (pin "3") (pinfunction "COM_3") (pintype "bidirectional"))
      (node (ref "L76") (pin "1") (pinfunction "1_1") (pintype "passive"))
    )
    (net (code "126") (name "Net-(D77-COM)") (class "Default")
      (node (ref "D77") (pin "3") (pinfunction "COM_3") (pintype "bidirectional"))
      (node (ref "L77") (pin "1") (pinfunction "1_1") (pintype "passive"))
    )
    (net (code "127") (name "Net-(D78-COM)") (class "Default")
      (node (ref "D78") (pin "3") (pinfunction "COM_3") (pintype "bidirectional"))
      (node (ref "L78") (pin "1") (pinfunction "1_1") (pintype "passive"))
    )
    (net (code "128") (name "Net-(D79-COM)") (class "Default")
      (node (ref "D79") (pin "3") (pinfunction "COM_3") (pintype "bidirectional"))
      (node (ref "L79") (pin "1") (pinfunction "1_1") (pintype "passive"))
    )
    (net (code "129") (name "Net-(D80-COM)") (class "Default")
      (node (ref "D80") (pin "3") (pinfunction "COM_3") (pintype "bidirectional"))
      (node (ref "L80") (pin "1") (pinfunction "1_1") (pintype "passive"))
    )
    (net (code "130") (name "Net-(D81-COM)") (class "Default")
      (node (ref "D81") (pin "3") (pinfunction "COM_3") (pintype "bidirectional"))
      (node (ref "L81") (pin "1") (pinfunction "1_1") (pintype "passive"))
    )
    (net (code "131") (name "Net-(D82-COM)") (class "Default")
      (node (ref "D82") (pin "3") (pinfunction "COM_3") (pintype "bidirectional"))
      (node (ref "L82") (pin "1") (pinfunction "1_1") (pintype "passive"))
    )
    (net (code "132") (name "Net-(D83-COM)") (class "Default")
      (node (ref "D83") (pin "3") (pinfunction "COM_3") (pintype "bidirectional"))
      (node (ref "L83") (pin "1") (pinfunction "1_1") (pintype "passive"))
    )
    (net (code "133") (name "Net-(D84-COM)") (class "Default")
      (node (ref "D84") (pin "3") (pinfunction "COM_3") (pintype "bidirectional"))
      (node (ref "L84") (pin "1") (pinfunction "1_1") (pintype "passive"))
    )
    (net (code "134") (name "Net-(D85-COM)") (class "Default")
      (node (ref "D85") (pin "3") (pinfunction "COM_3") (pintype "bidirectional"))
      (node (ref "L85") (pin "1") (pinfunction "1_1") (pintype "passive"))
    )
    (net (code "135") (name "Net-(D86-COM)") (class "Default")
      (node (ref "D86") (pin "3") (pinfunction "COM_3") (pintype "bidirectional"))
      (node (ref "L86") (pin "1") (pinfunction "1_1") (pintype "passive"))
    )
    (net (code "136") (name "Net-(D87-COM)") (class "Default")
      (node (ref "D87") (pin "3") (pinfunction "COM_3") (pintype "bidirectional"))
      (node (ref "L87") (pin "1") (pinfunction "1_1") (pintype "passive"))
    )
    (net (code "137") (name "Net-(D88-COM)") (class "Default")
      (node (ref "D88") (pin "3") (pinfunction "COM_3") (pintype "bidirectional"))
      (node (ref "L88") (pin "1") (pinfunction "1_1") (pintype "passive"))
    )
    (net (code "138") (name "Net-(D89-COM)") (class "Default")
      (node (ref "D89") (pin "3") (pinfunction "COM_3") (pintype "bidirectional"))
      (node (ref "L89") (pin "1") (pinfunction "1_1") (pintype "passive"))
    )
    (net (code "139") (name "Net-(D90-COM)") (class "Default")
      (node (ref "D90") (pin "3") (pinfunction "COM_3") (pintype "bidirectional"))
      (node (ref "L90") (pin "1") (pinfunction "1_1") (pintype "passive"))
    )
    (net (code "140") (name "Net-(D91-COM)") (class "Default")
      (node (ref "D91") (pin "3") (pinfunction "COM_3") (pintype "bidirectional"))
      (node (ref "L91") (pin "1") (pinfunction "1_1") (pintype "passive"))
    )
    (net (code "141") (name "Net-(D92-COM)") (class "Default")
      (node (ref "D92") (pin "3") (pinfunction "COM_3") (pintype "bidirectional"))
      (node (ref "L92") (pin "1") (pinfunction "1_1") (pintype "passive"))
    )
    (net (code "142") (name "Net-(D93-COM)") (class "Default")
      (node (ref "D93") (pin "3") (pinfunction "COM_3") (pintype "bidirectional"))
      (node (ref "L93") (pin "1") (pinfunction "1_1") (pintype "passive"))
    )
    (net (code "143") (name "Net-(D94-COM)") (class "Default")
      (node (ref "D94") (pin "3") (pinfunction "COM_3") (pintype "bidirectional"))
      (node (ref "L94") (pin "1") (pinfunction "1_1") (pintype "passive"))
    )
    (net (code "144") (name "Net-(D95-COM)") (class "Default")
      (node (ref "D95") (pin "3") (pinfunction "COM_3") (pintype "bidirectional"))
      (node (ref "L95") (pin "1") (pinfunction "1_1") (pintype "passive"))
    )
    (net (code "145") (name "Net-(D96-COM)") (class "Default")
      (node (ref "D96") (pin "3") (pinfunction "COM_3") (pintype "bidirectional"))
      (node (ref "L96") (pin "1") (pinfunction "1_1") (pintype "passive"))
    )
    (net (code "146") (name "Net-(D97-COM)") (class "Default")
      (node (ref "D97") (pin "3") (pinfunction "COM_3") (pintype "bidirectional"))
      (node (ref "L97") (pin "1") (pinfunction "1_1") (pintype "passive"))
    )
    (net (code "147") (name "Net-(D98-COM)") (class "Default")
      (node (ref "D98") (pin "3") (pinfunction "COM_3") (pintype "bidirectional"))
      (node (ref "L98") (pin "1") (pinfunction "1_1") (pintype "passive"))
    )
    (net (code "148") (name "Net-(D99-COM)") (class "Default")
      (node (ref "D99") (pin "3") (pinfunction "COM_3") (pintype "bidirectional"))
      (node (ref "L99") (pin "1") (pinfunction "1_1") (pintype "passive"))
    )
    (net (code "149") (name "Net-(D100-COM)") (class "Default")
      (node (ref "D100") (pin "3") (pinfunction "COM_3") (pintype "bidirectional"))
      (node (ref "L100") (pin "1") (pinfunction "1_1") (pintype "passive"))
    )
    (net (code "150") (name "Net-(D101-COM)") (class "Default")
      (node (ref "D101") (pin "3") (pinfunction "COM_3") (pintype "bidirectional"))
      (node (ref "L101") (pin "1") (pinfunction "1_1") (pintype "passive"))
    )
    (net (code "151") (name "Net-(D102-COM)") (class "Default")
      (node (ref "D102") (pin "3") (pinfunction "COM_3") (pintype "bidirectional"))
      (node (ref "L102") (pin "1") (pinfunction "1_1") (pintype "passive"))
    )
    (net (code "152") (name "Net-(D103-COM)") (class "Default")
      (node (ref "D103") (pin "3") (pinfunction "COM_3") (pintype "bidirectional"))
      (node (ref "L103") (pin "1") (pinfunction "1_1") (pintype "passive"))
    )
    (net (code "153") (name "Net-(D104-COM)") (class "Default")
      (node (ref "D104") (pin "3") (pinfunction "COM_3") (pintype "bidirectional"))
      (node (ref "L104") (pin "1") (pinfunction "1_1") (pintype "passive"))
    )
    (net (code "154") (name "Net-(D105-COM)") (class "Default")
      (node (ref "D105") (pin "3") (pinfunction "COM_3") (pintype "bidirectional"))
      (node (ref "L105") (pin "1") (pinfunction "1_1") (pintype "passive"))
    )
    (net (code "155") (name "Net-(D106-COM)") (class "Default")
      (node (ref "D106") (pin "3") (pinfunction "COM_3") (pintype "bidirectional"))
      (node (ref "L106") (pin "1") (pinfunction "1_1") (pintype "passive"))
    )
    (net (code "156") (name "Net-(D107-COM)") (class "Default")
      (node (ref "D107") (pin "3") (pinfunction "COM_3") (pintype "bidirectional"))
      (node (ref "L107") (pin "1") (pinfunction "1_1") (pintype "passive"))
    )
    (net (code "157") (name "Net-(D108-COM)") (class "Default")
      (node (ref "D108") (pin "3") (pinfunction "COM_3") (pintype "bidirectional"))
      (node (ref "L108") (pin "1") (pinfunction "1_1") (pintype "passive"))
    )
    (net (code "158") (name "Net-(D109-COM)") (class "Default")
      (node (ref "D109") (pin "3") (pinfunction "COM_3") (pintype "bidirectional"))
      (node (ref "L109") (pin "1") (pinfunction "1_1") (pintype "passive"))
    )
    (net (code "159") (name "Net-(D110-COM)") (class "Default")
      (node (ref "D110") (pin "3") (pinfunction "COM_3") (pintype "bidirectional"))
      (node (ref "L110") (pin "1") (pinfunction "1_1") (pintype "passive"))
    )
    (net (code "160") (name "Net-(D111-COM)") (class "Default")
      (node (ref "D111") (pin "3") (pinfunction "COM_3") (pintype "bidirectional"))
      (node (ref "L111") (pin "1") (pinfunction "1_1") (pintype "passive"))
    )
    (net (code "161") (name "Net-(D112-COM)") (class "Default")
      (node (ref "D112") (pin "3") (pinfunction "COM_3") (pintype "bidirectional"))
      (node (ref "L112") (pin "1") (pinfunction "1_1") (pintype "passive"))
    )
    (net (code "162") (name "Net-(D113-COM)") (class "Default")
      (node (ref "D113") (pin "3") (pinfunction "COM_3") (pintype "bidirectional"))
      (node (ref "L113") (pin "1") (pinfunction "1_1") (pintype "passive"))
    )
    (net (code "163") (name "Net-(D114-COM)") (class "Default")
      (node (ref "D114") (pin "3") (pinfunction "COM_3") (pintype "bidirectional"))
      (node (ref "L114") (pin "1") (pinfunction "1_1") (pintype "passive"))
    )
    (net (code "164") (name "Net-(D115-COM)") (class "Default")
      (node (ref "D115") (pin "3") (pinfunction "COM_3") (pintype "bidirectional"))
      (node (ref "L115") (pin "1") (pinfunction "1_1") (pintype "passive"))
    )
    (net (code "165") (name "Net-(D116-COM)") (class "Default")
      (node (ref "D116") (pin "3") (pinfunction "COM_3") (pintype "bidirectional"))
      (node (ref "L116") (pin "1") (pinfunction "1_1") (pintype "passive"))
    )
    (net (code "166") (name "Net-(D117-COM)") (class "Default")
      (node (ref "D117") (pin "3") (pinfunction "COM_3") (pintype "bidirectional"))
      (node (ref "L117") (pin "1") (pinfunction "1_1") (pintype "passive"))
    )
    (net (code "167") (name "Net-(D118-COM)") (class "Default")
      (node (ref "D118") (pin "3") (pinfunction "COM_3") (pintype "bidirectional"))
      (node (ref "L118") (pin "1") (pinfunction "1_1") (pintype "passive"))
    )
    (net (code "168") (name "Net-(D119-COM)") (class "Default")
      (node (ref "D119") (pin "3") (pinfunction "COM_3") (pintype "bidirectional"))
      (node (ref "L119") (pin "1") (pinfunction "1_1") (pintype "passive"))
    )
    (net (code "169") (name "Net-(D120-COM)") (class "Default")
      (node (ref "D120") (pin "3") (pinfunction "COM_3") (pintype "bidirectional"))
      (node (ref "L120") (pin "1") (pinfunction "1_1") (pintype "passive"))
    )
    (net (code "170") (name "Net-(D121-COM)") (class "Default")
      (node (ref "D121") (pin "3") (pinfunction "COM_3") (pintype "bidirectional"))
      (node (ref "L121") (pin "1") (pinfunction "1_1") (pintype "passive"))
    )
    (net (code "171") (name "Net-(D122-COM)") (class "Default")
      (node (ref "D122") (pin "3") (pinfunction "COM_3") (pintype "bidirectional"))
      (node (ref "L122") (pin "1") (pinfunction "1_1") (pintype "passive"))
    )
    (net (code "172") (name "Net-(D123-COM)") (class "Default")
      (node (ref "D123") (pin "3") (pinfunction "COM_3") (pintype "bidirectional"))
      (node (ref "L123") (pin "1") (pinfunction "1_1") (pintype "passive"))
    )
    (net (code "173") (name "Net-(D124-COM)") (class "Default")
      (node (ref "D124") (pin "3") (pinfunction "COM_3") (pintype "bidirectional"))
      (node (ref "L124") (pin "1") (pinfunction "1_1") (pintype "passive"))
    )
    (net (code "174") (name "Net-(D125-COM)") (class "Default")
      (node (ref "D125") (pin "3") (pinfunction "COM_3") (pintype "bidirectional"))
      (node (ref "L125") (pin "1") (pinfunction "1_1") (pintype "passive"))
    )
    (net (code "175") (name "Net-(D126-COM)") (class "Default")
      (node (ref "D126") (pin "3") (pinfunction "COM_3") (pintype "bidirectional"))
      (node (ref "L126") (pin "1") (pinfunction "1_1") (pintype "passive"))
    )
    (net (code "176") (name "Net-(D127-COM)") (class "Default")
      (node (ref "D127") (pin "3") (pinfunction "COM_3") (pintype "bidirectional"))
      (node (ref "L127") (pin "1") (pinfunction "1_1") (pintype "passive"))
    )
    (net (code "177") (name "Net-(D128-COM)") (class "Default")
      (node (ref "D128") (pin "3") (pinfunction "COM_3") (pintype "bidirectional"))
      (node (ref "L128") (pin "1") (pinfunction "1_1") (pintype "passive"))
    )
    (net (code "178") (name "Net-(D129-COM)") (class "Default")
      (node (ref "D129") (pin "3") (pinfunction "COM_3") (pintype "bidirectional"))
      (node (ref "L129") (pin "1") (pinfunction "1_1") (pintype "passive"))
    )
    (net (code "179") (name "Net-(D130-COM)") (class "Default")
      (node (ref "D130") (pin "3") (pinfunction "COM_3") (pintype "bidirectional"))
      (node (ref "L130") (pin "1") (pinfunction "1_1") (pintype "passive"))
    )
    (net (code "180") (name "Net-(D131-COM)") (class "Default")
      (node (ref "D131") (pin "3") (pinfunction "COM_3") (pintype "bidirectional"))
      (node (ref "L131") (pin "1") (pinfunction "1_1") (pintype "passive"))
    )
    (net (code "181") (name "Net-(D132-COM)") (class "Default")
      (node (ref "D132") (pin "3") (pinfunction "COM_3") (pintype "bidirectional"))
      (node (ref "L132") (pin "1") (pinfunction "1_1") (pintype "passive"))
    )
    (net (code "182") (name "Net-(D133-COM)") (class "Default")
      (node (ref "D133") (pin "3") (pinfunction "COM_3") (pintype "bidirectional"))
      (node (ref "L133") (pin "1") (pinfunction "1_1") (pintype "passive"))
    )
    (net (code "183") (name "Net-(D134-COM)") (class "Default")
      (node (ref "D134") (pin "3") (pinfunction "COM_3") (pintype "bidirectional"))
      (node (ref "L134") (pin "1") (pinfunction "1_1") (pintype "passive"))
    )
    (net (code "184") (name "Net-(D135-COM)") (class "Default")
      (node (ref "D135") (pin "3") (pinfunction "COM_3") (pintype "bidirectional"))
      (node (ref "L135") (pin "1") (pinfunction "1_1") (pintype "passive"))
    )
    (net (code "185") (name "Net-(D136-COM)") (class "Default")
      (node (ref "D136") (pin "3") (pinfunction "COM_3") (pintype "bidirectional"))
      (node (ref "L136") (pin "1") (pinfunction "1_1") (pintype "passive"))
    )
    (net (code "186") (name "Net-(D137-COM)") (class "Default")
      (node (ref "D137") (pin "3") (pinfunction "COM_3") (pintype "bidirectional"))
      (node (ref "L137") (pin "1") (pinfunction "1_1") (pintype "passive"))
    )
    (net (code "187") (name "Net-(D138-COM)") (class "Default")
      (node (ref "D138") (pin "3") (pinfunction "COM_3") (pintype "bidirectional"))
      (node (ref "L138") (pin "1") (pinfunction "1_1") (pintype "passive"))
    )
    (net (code "188") (name "Net-(D139-COM)") (class "Default")
      (node (ref "D139") (pin "3") (pinfunction "COM_3") (pintype "bidirectional"))
      (node (ref "L139") (pin "1") (pinfunction "1_1") (pintype "passive"))
    )
    (net (code "189") (name "Net-(D140-COM)") (class "Default")
      (node (ref "D140") (pin "3") (pinfunction "COM_3") (pintype "bidirectional"))
      (node (ref "L140") (pin "1") (pinfunction "1_1") (pintype "passive"))
    )
    (net (code "190") (name "Net-(D141-COM)") (class "Default")
      (node (ref "D141") (pin "3") (pinfunction "COM_3") (pintype "bidirectional"))
      (node (ref "L141") (pin "1") (pinfunction "1_1") (pintype "passive"))
    )
    (net (code "191") (name "Net-(D142-COM)") (class "Default")
      (node (ref "D142") (pin "3") (pinfunction "COM_3") (pintype "bidirectional"))
      (node (ref "L142") (pin "1") (pinfunction "1_1") (pintype "passive"))
    )
    (net (code "192") (name "Net-(D143-COM)") (class "Default")
      (node (ref "D143") (pin "3") (pinfunction "COM_3") (pintype "bidirectional"))
      (node (ref "L143") (pin "1") (pinfunction "1_1") (pintype "passive"))
    )
    (net (code "193") (name "Net-(D144-COM)") (class "Default")
      (node (ref "D144") (pin "3") (pinfunction "COM_3") (pintype "bidirectional"))
      (node (ref "L144") (pin "1") (pinfunction "1_1") (pintype "passive"))
    )
    (net (code "194") (name "Net-(D145-COM)") (class "Default")
      (node (ref "D145") (pin "3") (pinfunction "COM_3") (pintype "bidirectional"))
      (node (ref "L145") (pin "1") (pinfunction "1_1") (pintype "passive"))
    )
    (net (code "195") (name "Net-(D146-COM)") (class "Default")
      (node (ref "D146") (pin "3") (pinfunction "COM_3") (pintype "bidirectional"))
      (node (ref "L146") (pin "1") (pinfunction "1_1") (pintype "passive"))
    )
    (net (code "196") (name "Net-(D147-COM)") (class "Default")
      (node (ref "D147") (pin "3") (pinfunction "COM_3") (pintype "bidirectional"))
      (node (ref "L147") (pin "1") (pinfunction "1_1") (pintype "passive"))
    )
    (net (code "197") (name "Net-(D148-COM)") (class "Default")
      (node (ref "D148") (pin "3") (pinfunction "COM_3") (pintype "bidirectional"))
      (node (ref "L148") (pin "1") (pinfunction "1_1") (pintype "passive"))
    )
    (net (code "198") (name "Net-(D149-COM)") (class "Default")
      (node (ref "D149") (pin "3") (pinfunction "COM_3") (pintype "bidirectional"))
      (node (ref "L149") (pin "1") (pinfunction "1_1") (pintype "passive"))
    )
    (net (code "199") (name "Net-(D150-COM)") (class "Default")
      (node (ref "D150") (pin "3") (pinfunction "COM_3") (pintype "bidirectional"))
      (node (ref "L150") (pin "1") (pinfunction "1_1") (pintype "passive"))
    )
    (net (code "200") (name "Net-(D151-COM)") (class "Default")
      (node (ref "D151") (pin "3") (pinfunction "COM_3") (pintype "bidirectional"))
      (node (ref "L151") (pin "1") (pinfunction "1_1") (pintype "passive"))
    )
    (net (code "201") (name "Net-(D152-COM)") (class "Default")
      (node (ref "D152") (pin "3") (pinfunction "COM_3") (pintype "bidirectional"))
      (node (ref "L152") (pin "1") (pinfunction "1_1") (pintype "passive"))
    )
    (net (code "202") (name "Net-(D153-COM)") (class "Default")
      (node (ref "D153") (pin "3") (pinfunction "COM_3") (pintype "bidirectional"))
      (node (ref "L153") (pin "1") (pinfunction "1_1") (pintype "passive"))
    )
    (net (code "203") (name "Net-(D154-COM)") (class "Default")
      (node (ref "D154") (pin "3") (pinfunction "COM_3") (pintype "bidirectional"))
      (node (ref "L154") (pin "1") (pinfunction "1_1") (pintype "passive"))
    )
    (net (code "204") (name "Net-(D155-COM)") (class "Default")
      (node (ref "D155") (pin "3") (pinfunction "COM_3") (pintype "bidirectional"))
      (node (ref "L155") (pin "1") (pinfunction "1_1") (pintype "passive"))
    )
    (net (code "205") (name "Net-(D156-COM)") (class "Default")
      (node (ref "D156") (pin "3") (pinfunction "COM_3") (pintype "bidirectional"))
      (node (ref "L156") (pin "1") (pinfunction "1_1") (pintype "passive"))
    )
    (net (code "206") (name "Net-(D157-COM)") (class "Default")
      (node (ref "D157") (pin "3") (pinfunction "COM_3") (pintype "bidirectional"))
      (node (ref "L157") (pin "1") (pinfunction "1_1") (pintype "passive"))
    )
    (net (code "207") (name "Net-(D158-COM)") (class "Default")
      (node (ref "D158") (pin "3") (pinfunction "COM_3") (pintype "bidirectional"))
      (node (ref "L158") (pin "1") (pinfunction "1_1") (pintype "passive"))
    )
    (net (code "208") (name "Net-(D159-COM)") (class "Default")
      (node (ref "D159") (pin "3") (pinfunction "COM_3") (pintype "bidirectional"))
      (node (ref "L159") (pin "1") (pinfunction "1_1") (pintype "passive"))
    )
    (net (code "209") (name "Net-(D160-COM)") (class "Default")
      (node (ref "D160") (pin "3") (pinfunction "COM_3") (pintype "bidirectional"))
      (node (ref "L160") (pin "1") (pinfunction "1_1") (pintype "passive"))
    )
    (net (code "210") (name "Net-(D161-COM)") (class "Default")
      (node (ref "D161") (pin "3") (pinfunction "COM_3") (pintype "bidirectional"))
      (node (ref "L161") (pin "1") (pinfunction "1_1") (pintype "passive"))
    )
    (net (code "211") (name "Net-(D162-COM)") (class "Default")
      (node (ref "D162") (pin "3") (pinfunction "COM_3") (pintype "bidirectional"))
      (node (ref "L162") (pin "1") (pinfunction "1_1") (pintype "passive"))
    )
    (net (code "212") (name "Net-(D163-COM)") (class "Default")
      (node (ref "D163") (pin "3") (pinfunction "COM_3") (pintype "bidirectional"))
      (node (ref "L163") (pin "1") (pinfunction "1_1") (pintype "passive"))
    )
    (net (code "213") (name "Net-(D164-COM)") (class "Default")
      (node (ref "D164") (pin "3") (pinfunction "COM_3") (pintype "bidirectional"))
      (node (ref "L164") (pin "1") (pinfunction "1_1") (pintype "passive"))
    )
    (net (code "214") (name "Net-(D165-COM)") (class "Default")
      (node (ref "D165") (pin "3") (pinfunction "COM_3") (pintype "bidirectional"))
      (node (ref "L165") (pin "1") (pinfunction "1_1") (pintype "passive"))
    )
    (net (code "215") (name "Net-(D166-COM)") (class "Default")
      (node (ref "D166") (pin "3") (pinfunction "COM_3") (pintype "bidirectional"))
      (node (ref "L166") (pin "1") (pinfunction "1_1") (pintype "passive"))
    )
    (net (code "216") (name "Net-(D167-COM)") (class "Default")
      (node (ref "D167") (pin "3") (pinfunction "COM_3") (pintype "bidirectional"))
      (node (ref "L167") (pin "1") (pinfunction "1_1") (pintype "passive"))
    )
    (net (code "217") (name "Net-(D168-COM)") (class "Default")
      (node (ref "D168") (pin "3") (pinfunction "COM_3") (pintype "bidirectional"))
      (node (ref "L168") (pin "1") (pinfunction "1_1") (pintype "passive"))
    )
    (net (code "218") (name "Net-(D169-COM)") (class "Default")
      (node (ref "D169") (pin "3") (pinfunction "COM_3") (pintype "bidirectional"))
      (node (ref "L169") (pin "1") (pinfunction "1_1") (pintype "passive"))
    )
    (net (code "219") (name "Net-(D170-COM)") (class "Default")
      (node (ref "D170") (pin "3") (pinfunction "COM_3") (pintype "bidirectional"))
      (node (ref "L170") (pin "1") (pinfunction "1_1") (pintype "passive"))
    )
    (net (code "220") (name "Net-(D171-COM)") (class "Default")
      (node (ref "D171") (pin "3") (pinfunction "COM_3") (pintype "bidirectional"))
      (node (ref "L171") (pin "1") (pinfunction "1_1") (pintype "passive"))
    )
    (net (code "221") (name "Net-(D172-COM)") (class "Default")
      (node (ref "D172") (pin "3") (pinfunction "COM_3") (pintype "bidirectional"))
      (node (ref "L172") (pin "1") (pinfunction "1_1") (pintype "passive"))
    )
    (net (code "222") (name "Net-(D173-COM)") (class "Default")
      (node (ref "D173") (pin "3") (pinfunction "COM_3") (pintype "bidirectional"))
      (node (ref "L173") (pin "1") (pinfunction "1_1") (pintype "passive"))
    )
    (net (code "223") (name "Net-(D174-COM)") (class "Default")
      (node (ref "D174") (pin "3") (pinfunction "COM_3") (pintype "bidirectional"))
      (node (ref "L174") (pin "1") (pinfunction "1_1") (pintype "passive"))
    )
    (net (code "224") (name "Net-(D175-COM)") (class "Default")
      (node (ref "D175") (pin "3") (pinfunction "COM_3") (pintype "bidirectional"))
      (node (ref "L175") (pin "1") (pinfunction "1_1") (pintype "passive"))
    )
    (net (code "225") (name "Net-(D176-COM)") (class "Default")
      (node (ref "D176") (pin "3") (pinfunction "COM_3") (pintype "bidirectional"))
      (node (ref "L176") (pin "1") (pinfunction "1_1") (pintype "passive"))
    )
    (net (code "226") (name "Net-(D177-COM)") (class "Default")
      (node (ref "D177") (pin "3") (pinfunction "COM_3") (pintype "bidirectional"))
      (node (ref "L177") (pin "1") (pinfunction "1_1") (pintype "passive"))
    )
    (net (code "227") (name "Net-(D178-COM)") (class "Default")
      (node (ref "D178") (pin "3") (pinfunction "COM_3") (pintype "bidirectional"))
      (node (ref "L178") (pin "1") (pinfunction "1_1") (pintype "passive"))
    )
    (net (code "228") (name "Net-(D179-COM)") (class "Default")
      (node (ref "D179") (pin "3") (pinfunction "COM_3") (pintype "bidirectional"))
      (node (ref "L179") (pin "1") (pinfunction "1_1") (pintype "passive"))
    )
    (net (code "229") (name "Net-(D180-COM)") (class "Default")
      (node (ref "D180") (pin "3") (pinfunction "COM_3") (pintype "bidirectional"))
      (node (ref "L180") (pin "1") (pinfunction "1_1") (pintype "passive"))
    )
    (net (code "230") (name "Net-(D181-COM)") (class "Default")
      (node (ref "D181") (pin "3") (pinfunction "COM_3") (pintype "bidirectional"))
      (node (ref "L181") (pin "1") (pinfunction "1_1") (pintype "passive"))
    )
    (net (code "231") (name "Net-(D182-COM)") (class "Default")
      (node (ref "D182") (pin "3") (pinfunction "COM_3") (pintype "bidirectional"))
      (node (ref "L182") (pin "1") (pinfunction "1_1") (pintype "passive"))
    )
    (net (code "232") (name "Net-(D183-COM)") (class "Default")
      (node (ref "D183") (pin "3") (pinfunction "COM_3") (pintype "bidirectional"))
      (node (ref "L183") (pin "1") (pinfunction "1_1") (pintype "passive"))
    )
    (net (code "233") (name "Net-(D184-COM)") (class "Default")
      (node (ref "D184") (pin "3") (pinfunction "COM_3") (pintype "bidirectional"))
      (node (ref "L184") (pin "1") (pinfunction "1_1") (pintype "passive"))
    )
    (net (code "234") (name "Net-(D185-COM)") (class "Default")
      (node (ref "D185") (pin "3") (pinfunction "COM_3") (pintype "bidirectional"))
      (node (ref "L185") (pin "1") (pinfunction "1_1") (pintype "passive"))
    )
    (net (code "235") (name "Net-(D186-COM)") (class "Default")
      (node (ref "D186") (pin "3") (pinfunction "COM_3") (pintype "bidirectional"))
      (node (ref "L186") (pin "1") (pinfunction "1_1") (pintype "passive"))
    )
    (net (code "236") (name "Net-(D187-COM)") (class "Default")
      (node (ref "D187") (pin "3") (pinfunction "COM_3") (pintype "bidirectional"))
      (node (ref "L187") (pin "1") (pinfunction "1_1") (pintype "passive"))
    )
    (net (code "237") (name "Net-(D188-COM)") (class "Default")
      (node (ref "D188") (pin "3") (pinfunction "COM_3") (pintype "bidirectional"))
      (node (ref "L188") (pin "1") (pinfunction "1_1") (pintype "passive"))
    )
    (net (code "238") (name "Net-(D189-COM)") (class "Default")
      (node (ref "D189") (pin "3") (pinfunction "COM_3") (pintype "bidirectional"))
      (node (ref "L189") (pin "1") (pinfunction "1_1") (pintype "passive"))
    )
    (net (code "239") (name "Net-(D190-COM)") (class "Default")
      (node (ref "D190") (pin "3") (pinfunction "COM_3") (pintype "bidirectional"))
      (node (ref "L190") (pin "1") (pinfunction "1_1") (pintype "passive"))
    )
    (net (code "240") (name "Net-(D191-COM)") (class "Default")
      (node (ref "D191") (pin "3") (pinfunction "COM_3") (pintype "bidirectional"))
      (node (ref "L191") (pin "1") (pinfunction "1_1") (pintype "passive"))
    )
    (net (code "241") (name "Net-(D192-COM)") (class "Default")
      (node (ref "D192") (pin "3") (pinfunction "COM_3") (pintype "bidirectional"))
      (node (ref "L192") (pin "1") (pinfunction "1_1") (pintype "passive"))
    )
    (net (code "242") (name "Net-(D193-COM)") (class "Default")
      (node (ref "D193") (pin "3") (pinfunction "COM_3") (pintype "bidirectional"))
      (node (ref "L193") (pin "1") (pinfunction "1_1") (pintype "passive"))
    )
    (net (code "243") (name "Net-(D194-COM)") (class "Default")
      (node (ref "D194") (pin "3") (pinfunction "COM_3") (pintype "bidirectional"))
      (node (ref "L194") (pin "1") (pinfunction "1_1") (pintype "passive"))
    )
    (net (code "244") (name "Net-(D195-COM)") (class "Default")
      (node (ref "D195") (pin "3") (pinfunction "COM_3") (pintype "bidirectional"))
      (node (ref "L195") (pin "1") (pinfunction "1_1") (pintype "passive"))
    )
    (net (code "245") (name "Net-(D196-COM)") (class "Default")
      (node (ref "D196") (pin "3") (pinfunction "COM_3") (pintype "bidirectional"))
      (node (ref "L196") (pin "1") (pinfunction "1_1") (pintype "passive"))
    )
    (net (code "246") (name "Net-(D197-COM)") (class "Default")
      (node (ref "D197") (pin "3") (pinfunction "COM_3") (pintype "bidirectional"))
      (node (ref "L197") (pin "1") (pinfunction "1_1") (pintype "passive"))
    )
    (net (code "247") (name "Net-(D198-COM)") (class "Default")
      (node (ref "D198") (pin "3") (pinfunction "COM_3") (pintype "bidirectional"))
      (node (ref "L198") (pin "1") (pinfunction "1_1") (pintype "passive"))
    )
    (net (code "248") (name "Net-(D199-COM)") (class "Default")
      (node (ref "D199") (pin "3") (pinfunction "COM_3") (pintype "bidirectional"))
      (node (ref "L199") (pin "1") (pinfunction "1_1") (pintype "passive"))
    )
    (net (code "249") (name "Net-(D200-COM)") (class "Default")
      (node (ref "D200") (pin "3") (pinfunction "COM_3") (pintype "bidirectional"))
      (node (ref "L200") (pin "1") (pinfunction "1_1") (pintype "passive"))
    )
    (net (code "250") (name "Net-(D201-COM)") (class "Default")
      (node (ref "D201") (pin "3") (pinfunction "COM_3") (pintype "bidirectional"))
      (node (ref "L201") (pin "1") (pinfunction "1_1") (pintype "passive"))
    )
    (net (code "251") (name "Net-(D202-COM)") (class "Default")
      (node (ref "D202") (pin "3") (pinfunction "COM_3") (pintype "bidirectional"))
      (node (ref "L202") (pin "1") (pinfunction "1_1") (pintype "passive"))
    )
    (net (code "252") (name "Net-(D203-COM)") (class "Default")
      (node (ref "D203") (pin "3") (pinfunction "COM_3") (pintype "bidirectional"))
      (node (ref "L203") (pin "1") (pinfunction "1_1") (pintype "passive"))
    )
    (net (code "253") (name "Net-(D204-COM)") (class "Default")
      (node (ref "D204") (pin "3") (pinfunction "COM_3") (pintype "bidirectional"))
      (node (ref "L204") (pin "1") (pinfunction "1_1") (pintype "passive"))
    )
    (net (code "254") (name "Net-(D205-COM)") (class "Default")
      (node (ref "D205") (pin "3") (pinfunction "COM_3") (pintype "bidirectional"))
      (node (ref "L205") (pin "1") (pinfunction "1_1") (pintype "passive"))
    )
    (net (code "255") (name "Net-(D206-COM)") (class "Default")
      (node (ref "D206") (pin "3") (pinfunction "COM_3") (pintype "bidirectional"))
      (node (ref "L206") (pin "1") (pinfunction "1_1") (pintype "passive"))
    )
    (net (code "256") (name "Net-(D207-COM)") (class "Default")
      (node (ref "D207") (pin "3") (pinfunction "COM_3") (pintype "bidirectional"))
      (node (ref "L207") (pin "1") (pinfunction "1_1") (pintype "passive"))
    )
    (net (code "257") (name "Net-(D208-COM)") (class "Default")
      (node (ref "D208") (pin "3") (pinfunction "COM_3") (pintype "bidirectional"))
      (node (ref "L208") (pin "1") (pinfunction "1_1") (pintype "passive"))
    )
    (net (code "258") (name "Net-(D209-COM)") (class "Default")
      (node (ref "D209") (pin "3") (pinfunction "COM_3") (pintype "bidirectional"))
      (node (ref "L209") (pin "1") (pinfunction "1_1") (pintype "passive"))
    )
    (net (code "259") (name "Net-(D210-COM)") (class "Default")
      (node (ref "D210") (pin "3") (pinfunction "COM_3") (pintype "bidirectional"))
      (node (ref "L210") (pin "1") (pinfunction "1_1") (pintype "passive"))
    )
    (net (code "260") (name "Net-(D211-COM)") (class "Default")
      (node (ref "D211") (pin "3") (pinfunction "COM_3") (pintype "bidirectional"))
      (node (ref "L211") (pin "1") (pinfunction "1_1") (pintype "passive"))
    )
    (net (code "261") (name "Net-(D212-COM)") (class "Default")
      (node (ref "D212") (pin "3") (pinfunction "COM_3") (pintype "bidirectional"))
      (node (ref "L212") (pin "1") (pinfunction "1_1") (pintype "passive"))
    )
    (net (code "262") (name "Net-(D213-COM)") (class "Default")
      (node (ref "D213") (pin "3") (pinfunction "COM_3") (pintype "bidirectional"))
      (node (ref "L213") (pin "1") (pinfunction "1_1") (pintype "passive"))
    )
    (net (code "263") (name "Net-(D214-COM)") (class "Default")
      (node (ref "D214") (pin "3") (pinfunction "COM_3") (pintype "bidirectional"))
      (node (ref "L214") (pin "1") (pinfunction "1_1") (pintype "passive"))
    )
    (net (code "264") (name "Net-(D215-COM)") (class "Default")
      (node (ref "D215") (pin "3") (pinfunction "COM_3") (pintype "bidirectional"))
      (node (ref "L215") (pin "1") (pinfunction "1_1") (pintype "passive"))
    )
    (net (code "265") (name "Net-(D216-COM)") (class "Default")
      (node (ref "D216") (pin "3") (pinfunction "COM_3") (pintype "bidirectional"))
      (node (ref "L216") (pin "1") (pinfunction "1_1") (pintype "passive"))
    )
    (net (code "266") (name "Net-(D217-COM)") (class "Default")
      (node (ref "D217") (pin "3") (pinfunction "COM_3") (pintype "bidirectional"))
      (node (ref "L217") (pin "1") (pinfunction "1_1") (pintype "passive"))
    )
    (net (code "267") (name "Net-(D218-COM)") (class "Default")
      (node (ref "D218") (pin "3") (pinfunction "COM_3") (pintype "bidirectional"))
      (node (ref "L218") (pin "1") (pinfunction "1_1") (pintype "passive"))
    )
    (net (code "268") (name "Net-(D219-COM)") (class "Default")
      (node (ref "D219") (pin "3") (pinfunction "COM_3") (pintype "bidirectional"))
      (node (ref "L219") (pin "1") (pinfunction "1_1") (pintype "passive"))
    )
    (net (code "269") (name "Net-(D220-COM)") (class "Default")
      (node (ref "D220") (pin "3") (pinfunction "COM_3") (pintype "bidirectional"))
      (node (ref "L220") (pin "1") (pinfunction "1_1") (pintype "passive"))
    )
    (net (code "270") (name "Net-(D221-COM)") (class "Default")
      (node (ref "D221") (pin "3") (pinfunction "COM_3") (pintype "bidirectional"))
      (node (ref "L221") (pin "1") (pinfunction "1_1") (pintype "passive"))
    )
    (net (code "271") (name "Net-(D222-COM)") (class "Default")
      (node (ref "D222") (pin "3") (pinfunction "COM_3") (pintype "bidirectional"))
      (node (ref "L222") (pin "1") (pinfunction "1_1") (pintype "passive"))
    )
    (net (code "272") (name "Net-(D223-COM)") (class "Default")
      (node (ref "D223") (pin "3") (pinfunction "COM_3") (pintype "bidirectional"))
      (node (ref "L223") (pin "1") (pinfunction "1_1") (pintype "passive"))
    )
    (net (code "273") (name "Net-(D224-COM)") (class "Default")
      (node (ref "D224") (pin "3") (pinfunction "COM_3") (pintype "bidirectional"))
      (node (ref "L224") (pin "1") (pinfunction "1_1") (pintype "passive"))
    )
    (net (code "274") (name "Net-(D225-COM)") (class "Default")
      (node (ref "D225") (pin "3") (pinfunction "COM_3") (pintype "bidirectional"))
      (node (ref "L225") (pin "1") (pinfunction "1_1") (pintype "passive"))
    )
    (net (code "275") (name "Net-(D226-COM)") (class "Default")
      (node (ref "D226") (pin "3") (pinfunction "COM_3") (pintype "bidirectional"))
      (node (ref "L226") (pin "1") (pinfunction "1_1") (pintype "passive"))
    )
    (net (code "276") (name "Net-(D227-COM)") (class "Default")
      (node (ref "D227") (pin "3") (pinfunction "COM_3") (pintype "bidirectional"))
      (node (ref "L227") (pin "1") (pinfunction "1_1") (pintype "passive"))
    )
    (net (code "277") (name "Net-(D228-COM)") (class "Default")
      (node (ref "D228") (pin "3") (pinfunction "COM_3") (pintype "bidirectional"))
      (node (ref "L228") (pin "1") (pinfunction "1_1") (pintype "passive"))
    )
    (net (code "278") (name "Net-(D229-COM)") (class "Default")
      (node (ref "D229") (pin "3") (pinfunction "COM_3") (pintype "bidirectional"))
      (node (ref "L229") (pin "1") (pinfunction "1_1") (pintype "passive"))
    )
    (net (code "279") (name "Net-(D230-COM)") (class "Default")
      (node (ref "D230") (pin "3") (pinfunction "COM_3") (pintype "bidirectional"))
      (node (ref "L230") (pin "1") (pinfunction "1_1") (pintype "passive"))
    )
    (net (code "280") (name "Net-(D231-COM)") (class "Default")
      (node (ref "D231") (pin "3") (pinfunction "COM_3") (pintype "bidirectional"))
      (node (ref "L231") (pin "1") (pinfunction "1_1") (pintype "passive"))
    )
    (net (code "281") (name "Net-(D232-COM)") (class "Default")
      (node (ref "D232") (pin "3") (pinfunction "COM_3") (pintype "bidirectional"))
      (node (ref "L232") (pin "1") (pinfunction "1_1") (pintype "passive"))
    )
    (net (code "282") (name "Net-(D233-COM)") (class "Default")
      (node (ref "D233") (pin "3") (pinfunction "COM_3") (pintype "bidirectional"))
      (node (ref "L233") (pin "1") (pinfunction "1_1") (pintype "passive"))
    )
    (net (code "283") (name "Net-(D234-COM)") (class "Default")
      (node (ref "D234") (pin "3") (pinfunction "COM_3") (pintype "bidirectional"))
      (node (ref "L234") (pin "1") (pinfunction "1_1") (pintype "passive"))
    )
    (net (code "284") (name "Net-(D235-COM)") (class "Default")
      (node (ref "D235") (pin "3") (pinfunction "COM_3") (pintype "bidirectional"))
      (node (ref "L235") (pin "1") (pinfunction "1_1") (pintype "passive"))
    )
    (net (code "285") (name "Net-(D236-COM)") (class "Default")
      (node (ref "D236") (pin "3") (pinfunction "COM_3") (pintype "bidirectional"))
      (node (ref "L236") (pin "1") (pinfunction "1_1") (pintype "passive"))
    )
    (net (code "286") (name "Net-(D237-COM)") (class "Default")
      (node (ref "D237") (pin "3") (pinfunction "COM_3") (pintype "bidirectional"))
      (node (ref "L237") (pin "1") (pinfunction "1_1") (pintype "passive"))
    )
    (net (code "287") (name "Net-(D238-COM)") (class "Default")
      (node (ref "D238") (pin "3") (pinfunction "COM_3") (pintype "bidirectional"))
      (node (ref "L238") (pin "1") (pinfunction "1_1") (pintype "passive"))
    )
    (net (code "288") (name "Net-(D239-COM)") (class "Default")
      (node (ref "D239") (pin "3") (pinfunction "COM_3") (pintype "bidirectional"))
      (node (ref "L239") (pin "1") (pinfunction "1_1") (pintype "passive"))
    )
    (net (code "289") (name "Net-(D240-COM)") (class "Default")
      (node (ref "D240") (pin "3") (pinfunction "COM_3") (pintype "bidirectional"))
      (node (ref "L240") (pin "1") (pinfunction "1_1") (pintype "passive"))
    )
    (net (code "290") (name "Net-(D241-COM)") (class "Default")
      (node (ref "D241") (pin "3") (pinfunction "COM_3") (pintype "bidirectional"))
      (node (ref "L241") (pin "1") (pinfunction "1_1") (pintype "passive"))
    )
    (net (code "291") (name "Net-(D242-COM)") (class "Default")
      (node (ref "D242") (pin "3") (pinfunction "COM_3") (pintype "bidirectional"))
      (node (ref "L242") (pin "1") (pinfunction "1_1") (pintype "passive"))
    )
    (net (code "292") (name "Net-(D243-COM)") (class "Default")
      (node (ref "D243") (pin "3") (pinfunction "COM_3") (pintype "bidirectional"))
      (node (ref "L243") (pin "1") (pinfunction "1_1") (pintype "passive"))
    )
    (net (code "293") (name "Net-(D244-COM)") (class "Default")
      (node (ref "D244") (pin "3") (pinfunction "COM_3") (pintype "bidirectional"))
      (node (ref "L244") (pin "1") (pinfunction "1_1") (pintype "passive"))
    )
    (net (code "294") (name "Net-(D245-COM)") (class "Default")
      (node (ref "D245") (pin "3") (pinfunction "COM_3") (pintype "bidirectional"))
      (node (ref "L245") (pin "1") (pinfunction "1_1") (pintype "passive"))
    )
    (net (code "295") (name "Net-(D246-COM)") (class "Default")
      (node (ref "D246") (pin "3") (pinfunction "COM_3") (pintype "bidirectional"))
      (node (ref "L246") (pin "1") (pinfunction "1_1") (pintype "passive"))
    )
    (net (code "296") (name "Net-(D247-COM)") (class "Default")
      (node (ref "D247") (pin "3") (pinfunction "COM_3") (pintype "bidirectional"))
      (node (ref "L247") (pin "1") (pinfunction "1_1") (pintype "passive"))
    )
    (net (code "297") (name "Net-(D248-COM)") (class "Default")
      (node (ref "D248") (pin "3") (pinfunction "COM_3") (pintype "bidirectional"))
      (node (ref "L248") (pin "1") (pinfunction "1_1") (pintype "passive"))
    )
    (net (code "298") (name "Net-(D249-COM)") (class "Default")
      (node (ref "D249") (pin "3") (pinfunction "COM_3") (pintype "bidirectional"))
      (node (ref "L249") (pin "1") (pinfunction "1_1") (pintype "passive"))
    )
    (net (code "299") (name "Net-(D250-COM)") (class "Default")
      (node (ref "D250") (pin "3") (pinfunction "COM_3") (pintype "bidirectional"))
      (node (ref "L250") (pin "1") (pinfunction "1_1") (pintype "passive"))
    )
    (net (code "300") (name "Net-(D251-COM)") (class "Default")
      (node (ref "D251") (pin "3") (pinfunction "COM_3") (pintype "bidirectional"))
      (node (ref "L251") (pin "1") (pinfunction "1_1") (pintype "passive"))
    )
    (net (code "301") (name "Net-(D252-COM)") (class "Default")
      (node (ref "D252") (pin "3") (pinfunction "COM_3") (pintype "bidirectional"))
      (node (ref "L252") (pin "1") (pinfunction "1_1") (pintype "passive"))
    )
    (net (code "302") (name "Net-(D253-COM)") (class "Default")
      (node (ref "D253") (pin "3") (pinfunction "COM_3") (pintype "bidirectional"))
      (node (ref "L253") (pin "1") (pinfunction "1_1") (pintype "passive"))
    )
    (net (code "303") (name "Net-(D254-COM)") (class "Default")
      (node (ref "D254") (pin "3") (pinfunction "COM_3") (pintype "bidirectional"))
      (node (ref "L254") (pin "1") (pinfunction "1_1") (pintype "passive"))
    )
    (net (code "304") (name "Net-(D255-COM)") (class "Default")
      (node (ref "D255") (pin "3") (pinfunction "COM_3") (pintype "bidirectional"))
      (node (ref "L255") (pin "1") (pinfunction "1_1") (pintype "passive"))
    )
    (net (code "305") (name "Net-(D256-COM)") (class "Default")
      (node (ref "D256") (pin "3") (pinfunction "COM_3") (pintype "bidirectional"))
      (node (ref "L256") (pin "1") (pinfunction "1_1") (pintype "passive"))
    )
    (net (code "306") (name "Net-(D257-COM)") (class "Default")
      (node (ref "D257") (pin "3") (pinfunction "COM_3") (pintype "bidirectional"))
      (node (ref "L257") (pin "1") (pinfunction "1_1") (pintype "passive"))
    )
    (net (code "307") (name "Net-(D258-COM)") (class "Default")
      (node (ref "D258") (pin "3") (pinfunction "COM_3") (pintype "bidirectional"))
      (node (ref "L258") (pin "1") (pinfunction "1_1") (pintype "passive"))
    )
    (net (code "308") (name "Net-(D259-COM)") (class "Default")
      (node (ref "D259") (pin "3") (pinfunction "COM_3") (pintype "bidirectional"))
      (node (ref "L259") (pin "1") (pinfunction "1_1") (pintype "passive"))
    )
    (net (code "309") (name "Net-(D260-COM)") (class "Default")
      (node (ref "D260") (pin "3") (pinfunction "COM_3") (pintype "bidirectional"))
      (node (ref "L260") (pin "1") (pinfunction "1_1") (pintype "passive"))
    )
    (net (code "310") (name "Net-(D261-COM)") (class "Default")
      (node (ref "D261") (pin "3") (pinfunction "COM_3") (pintype "bidirectional"))
      (node (ref "L261") (pin "1") (pinfunction "1_1") (pintype "passive"))
    )
    (net (code "311") (name "Net-(D262-COM)") (class "Default")
      (node (ref "D262") (pin "3") (pinfunction "COM_3") (pintype "bidirectional"))
      (node (ref "L262") (pin "1") (pinfunction "1_1") (pintype "passive"))
    )
    (net (code "312") (name "Net-(D263-COM)") (class "Default")
      (node (ref "D263") (pin "3") (pinfunction "COM_3") (pintype "bidirectional"))
      (node (ref "L263") (pin "1") (pinfunction "1_1") (pintype "passive"))
    )
    (net (code "313") (name "Net-(D264-COM)") (class "Default")
      (node (ref "D264") (pin "3") (pinfunction "COM_3") (pintype "bidirectional"))
      (node (ref "L264") (pin "1") (pinfunction "1_1") (pintype "passive"))
    )
    (net (code "314") (name "Net-(D265-COM)") (class "Default")
      (node (ref "D265") (pin "3") (pinfunction "COM_3") (pintype "bidirectional"))
      (node (ref "L265") (pin "1") (pinfunction "1_1") (pintype "passive"))
    )
    (net (code "315") (name "Net-(D266-COM)") (class "Default")
      (node (ref "D266") (pin "3") (pinfunction "COM_3") (pintype "bidirectional"))
      (node (ref "L266") (pin "1") (pinfunction "1_1") (pintype "passive"))
    )
    (net (code "316") (name "Net-(D267-COM)") (class "Default")
      (node (ref "D267") (pin "3") (pinfunction "COM_3") (pintype "bidirectional"))
      (node (ref "L267") (pin "1") (pinfunction "1_1") (pintype "passive"))
    )
    (net (code "317") (name "Net-(D268-COM)") (class "Default")
      (node (ref "D268") (pin "3") (pinfunction "COM_3") (pintype "bidirectional"))
      (node (ref "L268") (pin "1") (pinfunction "1_1") (pintype "passive"))
    )
    (net (code "318") (name "Net-(D269-COM)") (class "Default")
      (node (ref "D269") (pin "3") (pinfunction "COM_3") (pintype "bidirectional"))
      (node (ref "L269") (pin "1") (pinfunction "1_1") (pintype "passive"))
    )
    (net (code "319") (name "Net-(D270-COM)") (class "Default")
      (node (ref "D270") (pin "3") (pinfunction "COM_3") (pintype "bidirectional"))
      (node (ref "L270") (pin "1") (pinfunction "1_1") (pintype "passive"))
    )
    (net (code "320") (name "Net-(D271-COM)") (class "Default")
      (node (ref "D271") (pin "3") (pinfunction "COM_3") (pintype "bidirectional"))
      (node (ref "L271") (pin "1") (pinfunction "1_1") (pintype "passive"))
    )
    (net (code "321") (name "Net-(D272-COM)") (class "Default")
      (node (ref "D272") (pin "3") (pinfunction "COM_3") (pintype "bidirectional"))
      (node (ref "L272") (pin "1") (pinfunction "1_1") (pintype "passive"))
    )
    (net (code "322") (name "Net-(D273-COM)") (class "Default")
      (node (ref "D273") (pin "3") (pinfunction "COM_3") (pintype "bidirectional"))
      (node (ref "L273") (pin "1") (pinfunction "1_1") (pintype "passive"))
    )
    (net (code "323") (name "Net-(D274-COM)") (class "Default")
      (node (ref "D274") (pin "3") (pinfunction "COM_3") (pintype "bidirectional"))
      (node (ref "L274") (pin "1") (pinfunction "1_1") (pintype "passive"))
    )
    (net (code "324") (name "Net-(D275-COM)") (class "Default")
      (node (ref "D275") (pin "3") (pinfunction "COM_3") (pintype "bidirectional"))
      (node (ref "L275") (pin "1") (pinfunction "1_1") (pintype "passive"))
    )
    (net (code "325") (name "Net-(D276-COM)") (class "Default")
      (node (ref "D276") (pin "3") (pinfunction "COM_3") (pintype "bidirectional"))
      (node (ref "L276") (pin "1") (pinfunction "1_1") (pintype "passive"))
    )
    (net (code "326") (name "Net-(D277-COM)") (class "Default")
      (node (ref "D277") (pin "3") (pinfunction "COM_3") (pintype "bidirectional"))
      (node (ref "L277") (pin "1") (pinfunction "1_1") (pintype "passive"))
    )
    (net (code "327") (name "Net-(D278-COM)") (class "Default")
      (node (ref "D278") (pin "3") (pinfunction "COM_3") (pintype "bidirectional"))
      (node (ref "L278") (pin "1") (pinfunction "1_1") (pintype "passive"))
    )
    (net (code "328") (name "Net-(D279-COM)") (class "Default")
      (node (ref "D279") (pin "3") (pinfunction "COM_3") (pintype "bidirectional"))
      (node (ref "L279") (pin "1") (pinfunction "1_1") (pintype "passive"))
    )
    (net (code "329") (name "Net-(D280-COM)") (class "Default")
      (node (ref "D280") (pin "3") (pinfunction "COM_3") (pintype "bidirectional"))
      (node (ref "L280") (pin "1") (pinfunction "1_1") (pintype "passive"))
    )
    (net (code "330") (name "Net-(D281-COM)") (class "Default")
      (node (ref "D281") (pin "3") (pinfunction "COM_3") (pintype "bidirectional"))
      (node (ref "L281") (pin "1") (pinfunction "1_1") (pintype "passive"))
    )
    (net (code "331") (name "Net-(D282-COM)") (class "Default")
      (node (ref "D282") (pin "3") (pinfunction "COM_3") (pintype "bidirectional"))
      (node (ref "L282") (pin "1") (pinfunction "1_1") (pintype "passive"))
    )
    (net (code "332") (name "Net-(D283-COM)") (class "Default")
      (node (ref "D283") (pin "3") (pinfunction "COM_3") (pintype "bidirectional"))
      (node (ref "L283") (pin "1") (pinfunction "1_1") (pintype "passive"))
    )
    (net (code "333") (name "Net-(D284-COM)") (class "Default")
      (node (ref "D284") (pin "3") (pinfunction "COM_3") (pintype "bidirectional"))
      (node (ref "L284") (pin "1") (pinfunction "1_1") (pintype "passive"))
    )
    (net (code "334") (name "Net-(D285-COM)") (class "Default")
      (node (ref "D285") (pin "3") (pinfunction "COM_3") (pintype "bidirectional"))
      (node (ref "L285") (pin "1") (pinfunction "1_1") (pintype "passive"))
    )
    (net (code "335") (name "Net-(D286-COM)") (class "Default")
      (node (ref "D286") (pin "3") (pinfunction "COM_3") (pintype "bidirectional"))
      (node (ref "L286") (pin "1") (pinfunction "1_1") (pintype "passive"))
    )
    (net (code "336") (name "Net-(D287-COM)") (class "Default")
      (node (ref "D287") (pin "3") (pinfunction "COM_3") (pintype "bidirectional"))
      (node (ref "L287") (pin "1") (pinfunction "1_1") (pintype "passive"))
    )
    (net (code "337") (name "Net-(D288-COM)") (class "Default")
      (node (ref "D288") (pin "3") (pinfunction "COM_3") (pintype "bidirectional"))
      (node (ref "L288") (pin "1") (pinfunction "1_1") (pintype "passive"))
    )
    (net (code "338") (name "Net-(D289-COM)") (class "Default")
      (node (ref "D289") (pin "3") (pinfunction "COM_3") (pintype "bidirectional"))
      (node (ref "L289") (pin "1") (pinfunction "1_1") (pintype "passive"))
    )
    (net (code "339") (name "Net-(D290-COM)") (class "Default")
      (node (ref "D290") (pin "3") (pinfunction "COM_3") (pintype "bidirectional"))
      (node (ref "L290") (pin "1") (pinfunction "1_1") (pintype "passive"))
    )
    (net (code "340") (name "Net-(D291-COM)") (class "Default")
      (node (ref "D291") (pin "3") (pinfunction "COM_3") (pintype "bidirectional"))
      (node (ref "L291") (pin "1") (pinfunction "1_1") (pintype "passive"))
    )
    (net (code "341") (name "Net-(D292-COM)") (class "Default")
      (node (ref "D292") (pin "3") (pinfunction "COM_3") (pintype "bidirectional"))
      (node (ref "L292") (pin "1") (pinfunction "1_1") (pintype "passive"))
    )
    (net (code "342") (name "Net-(D293-COM)") (class "Default")
      (node (ref "D293") (pin "3") (pinfunction "COM_3") (pintype "bidirectional"))
      (node (ref "L293") (pin "1") (pinfunction "1_1") (pintype "passive"))
    )
    (net (code "343") (name "Net-(D294-COM)") (class "Default")
      (node (ref "D294") (pin "3") (pinfunction "COM_3") (pintype "bidirectional"))
      (node (ref "L294") (pin "1") (pinfunction "1_1") (pintype "passive"))
    )
    (net (code "344") (name "Net-(D295-COM)") (class "Default")
      (node (ref "D295") (pin "3") (pinfunction "COM_3") (pintype "bidirectional"))
      (node (ref "L295") (pin "1") (pinfunction "1_1") (pintype "passive"))
    )
    (net (code "345") (name "Net-(D296-COM)") (class "Default")
      (node (ref "D296") (pin "3") (pinfunction "COM_3") (pintype "bidirectional"))
      (node (ref "L296") (pin "1") (pinfunction "1_1") (pintype "passive"))
    )
    (net (code "346") (name "Net-(D297-COM)") (class "Default")
      (node (ref "D297") (pin "3") (pinfunction "COM_3") (pintype "bidirectional"))
      (node (ref "L297") (pin "1") (pinfunction "1_1") (pintype "passive"))
    )
    (net (code "347") (name "Net-(D298-COM)") (class "Default")
      (node (ref "D298") (pin "3") (pinfunction "COM_3") (pintype "bidirectional"))
      (node (ref "L298") (pin "1") (pinfunction "1_1") (pintype "passive"))
    )
    (net (code "348") (name "Net-(D299-COM)") (class "Default")
      (node (ref "D299") (pin "3") (pinfunction "COM_3") (pintype "bidirectional"))
      (node (ref "L299") (pin "1") (pinfunction "1_1") (pintype "passive"))
    )
    (net (code "349") (name "Net-(D300-COM)") (class "Default")
      (node (ref "D300") (pin "3") (pinfunction "COM_3") (pintype "bidirectional"))
      (node (ref "L300") (pin "1") (pinfunction "1_1") (pintype "passive"))
    )
    (net (code "350") (name "Net-(D301-COM)") (class "Default")
      (node (ref "D301") (pin "3") (pinfunction "COM_3") (pintype "bidirectional"))
      (node (ref "L301") (pin "1") (pinfunction "1_1") (pintype "passive"))
    )
    (net (code "351") (name "Net-(D302-COM)") (class "Default")
      (node (ref "D302") (pin "3") (pinfunction "COM_3") (pintype "bidirectional"))
      (node (ref "L302") (pin "1") (pinfunction "1_1") (pintype "passive"))
    )
    (net (code "352") (name "Net-(D303-COM)") (class "Default")
      (node (ref "D303") (pin "3") (pinfunction "COM_3") (pintype "bidirectional"))
      (node (ref "L303") (pin "1") (pinfunction "1_1") (pintype "passive"))
    )
    (net (code "353") (name "Net-(D304-COM)") (class "Default")
      (node (ref "D304") (pin "3") (pinfunction "COM_3") (pintype "bidirectional"))
      (node (ref "L304") (pin "1") (pinfunction "1_1") (pintype "passive"))
    )
    (net (code "354") (name "Net-(D305-COM)") (class "Default")
      (node (ref "D305") (pin "3") (pinfunction "COM_3") (pintype "bidirectional"))
      (node (ref "L305") (pin "1") (pinfunction "1_1") (pintype "passive"))
    )
    (net (code "355") (name "Net-(D306-COM)") (class "Default")
      (node (ref "D306") (pin "3") (pinfunction "COM_3") (pintype "bidirectional"))
      (node (ref "L306") (pin "1") (pinfunction "1_1") (pintype "passive"))
    )
    (net (code "356") (name "Net-(D307-COM)") (class "Default")
      (node (ref "D307") (pin "3") (pinfunction "COM_3") (pintype "bidirectional"))
      (node (ref "L307") (pin "1") (pinfunction "1_1") (pintype "passive"))
    )
    (net (code "357") (name "Net-(D308-COM)") (class "Default")
      (node (ref "D308") (pin "3") (pinfunction "COM_3") (pintype "bidirectional"))
      (node (ref "L308") (pin "1") (pinfunction "1_1") (pintype "passive"))
    )
    (net (code "358") (name "Net-(D309-COM)") (class "Default")
      (node (ref "D309") (pin "3") (pinfunction "COM_3") (pintype "bidirectional"))
      (node (ref "L309") (pin "1") (pinfunction "1_1") (pintype "passive"))
    )
    (net (code "359") (name "Net-(D310-COM)") (class "Default")
      (node (ref "D310") (pin "3") (pinfunction "COM_3") (pintype "bidirectional"))
      (node (ref "L310") (pin "1") (pinfunction "1_1") (pintype "passive"))
    )
    (net (code "360") (name "Net-(D311-COM)") (class "Default")
      (node (ref "D311") (pin "3") (pinfunction "COM_3") (pintype "bidirectional"))
      (node (ref "L311") (pin "1") (pinfunction "1_1") (pintype "passive"))
    )
    (net (code "361") (name "Net-(D312-COM)") (class "Default")
      (node (ref "D312") (pin "3") (pinfunction "COM_3") (pintype "bidirectional"))
      (node (ref "L312") (pin "1") (pinfunction "1_1") (pintype "passive"))
    )
    (net (code "362") (name "Net-(D313-COM)") (class "Default")
      (node (ref "D313") (pin "3") (pinfunction "COM_3") (pintype "bidirectional"))
      (node (ref "L313") (pin "1") (pinfunction "1_1") (pintype "passive"))
    )
    (net (code "363") (name "Net-(D314-COM)") (class "Default")
      (node (ref "D314") (pin "3") (pinfunction "COM_3") (pintype "bidirectional"))
      (node (ref "L314") (pin "1") (pinfunction "1_1") (pintype "passive"))
    )
    (net (code "364") (name "Net-(D315-COM)") (class "Default")
      (node (ref "D315") (pin "3") (pinfunction "COM_3") (pintype "bidirectional"))
      (node (ref "L315") (pin "1") (pinfunction "1_1") (pintype "passive"))
    )
    (net (code "365") (name "Net-(D316-COM)") (class "Default")
      (node (ref "D316") (pin "3") (pinfunction "COM_3") (pintype "bidirectional"))
      (node (ref "L316") (pin "1") (pinfunction "1_1") (pintype "passive"))
    )
    (net (code "366") (name "Net-(D317-COM)") (class "Default")
      (node (ref "D317") (pin "3") (pinfunction "COM_3") (pintype "bidirectional"))
      (node (ref "L317") (pin "1") (pinfunction "1_1") (pintype "passive"))
    )
    (net (code "367") (name "Net-(D318-COM)") (class "Default")
      (node (ref "D318") (pin "3") (pinfunction "COM_3") (pintype "bidirectional"))
      (node (ref "L318") (pin "1") (pinfunction "1_1") (pintype "passive"))
    )
    (net (code "368") (name "Net-(D319-COM)") (class "Default")
      (node (ref "D319") (pin "3") (pinfunction "COM_3") (pintype "bidirectional"))
      (node (ref "L319") (pin "1") (pinfunction "1_1") (pintype "passive"))
    )
    (net (code "369") (name "Net-(D320-COM)") (class "Default")
      (node (ref "D320") (pin "3") (pinfunction "COM_3") (pintype "bidirectional"))
      (node (ref "L320") (pin "1") (pinfunction "1_1") (pintype "passive"))
    )
    (net (code "370") (name "Net-(D321-COM)") (class "Default")
      (node (ref "D321") (pin "3") (pinfunction "COM_3") (pintype "bidirectional"))
      (node (ref "L321") (pin "1") (pinfunction "1_1") (pintype "passive"))
    )
    (net (code "371") (name "Net-(D322-COM)") (class "Default")
      (node (ref "D322") (pin "3") (pinfunction "COM_3") (pintype "bidirectional"))
      (node (ref "L322") (pin "1") (pinfunction "1_1") (pintype "passive"))
    )
    (net (code "372") (name "Net-(D323-COM)") (class "Default")
      (node (ref "D323") (pin "3") (pinfunction "COM_3") (pintype "bidirectional"))
      (node (ref "L323") (pin "1") (pinfunction "1_1") (pintype "passive"))
    )
    (net (code "373") (name "Net-(D324-COM)") (class "Default")
      (node (ref "D324") (pin "3") (pinfunction "COM_3") (pintype "bidirectional"))
      (node (ref "L324") (pin "1") (pinfunction "1_1") (pintype "passive"))
    )
    (net (code "374") (name "Net-(D325-COM)") (class "Default")
      (node (ref "D325") (pin "3") (pinfunction "COM_3") (pintype "bidirectional"))
      (node (ref "L325") (pin "1") (pinfunction "1_1") (pintype "passive"))
    )
    (net (code "375") (name "Net-(D326-COM)") (class "Default")
      (node (ref "D326") (pin "3") (pinfunction "COM_3") (pintype "bidirectional"))
      (node (ref "L326") (pin "1") (pinfunction "1_1") (pintype "passive"))
    )
    (net (code "376") (name "Net-(D327-COM)") (class "Default")
      (node (ref "D327") (pin "3") (pinfunction "COM_3") (pintype "bidirectional"))
      (node (ref "L327") (pin "1") (pinfunction "1_1") (pintype "passive"))
    )
    (net (code "377") (name "Net-(D328-COM)") (class "Default")
      (node (ref "D328") (pin "3") (pinfunction "COM_3") (pintype "bidirectional"))
      (node (ref "L328") (pin "1") (pinfunction "1_1") (pintype "passive"))
    )
    (net (code "378") (name "Net-(D329-COM)") (class "Default")
      (node (ref "D329") (pin "3") (pinfunction "COM_3") (pintype "bidirectional"))
      (node (ref "L329") (pin "1") (pinfunction "1_1") (pintype "passive"))
    )
    (net (code "379") (name "Net-(D330-COM)") (class "Default")
      (node (ref "D330") (pin "3") (pinfunction "COM_3") (pintype "bidirectional"))
      (node (ref "L330") (pin "1") (pinfunction "1_1") (pintype "passive"))
    )
    (net (code "380") (name "Net-(D331-COM)") (class "Default")
      (node (ref "D331") (pin "3") (pinfunction "COM_3") (pintype "bidirectional"))
      (node (ref "L331") (pin "1") (pinfunction "1_1") (pintype "passive"))
    )
    (net (code "381") (name "Net-(D332-COM)") (class "Default")
      (node (ref "D332") (pin "3") (pinfunction "COM_3") (pintype "bidirectional"))
      (node (ref "L332") (pin "1") (pinfunction "1_1") (pintype "passive"))
    )
    (net (code "382") (name "Net-(D333-COM)") (class "Default")
      (node (ref "D333") (pin "3") (pinfunction "COM_3") (pintype "bidirectional"))
      (node (ref "L333") (pin "1") (pinfunction "1_1") (pintype "passive"))
    )
    (net (code "383") (name "Net-(D334-COM)") (class "Default")
      (node (ref "D334") (pin "3") (pinfunction "COM_3") (pintype "bidirectional"))
      (node (ref "L334") (pin "1") (pinfunction "1_1") (pintype "passive"))
    )
    (net (code "384") (name "Net-(D335-COM)") (class "Default")
      (node (ref "D335") (pin "3") (pinfunction "COM_3") (pintype "bidirectional"))
      (node (ref "L335") (pin "1") (pinfunction "1_1") (pintype "passive"))
    )
    (net (code "385") (name "Net-(D336-COM)") (class "Default")
      (node (ref "D336") (pin "3") (pinfunction "COM_3") (pintype "bidirectional"))
      (node (ref "L336") (pin "1") (pinfunction "1_1") (pintype "passive"))
    )
    (net (code "386") (name "Net-(D337-COM)") (class "Default")
      (node (ref "D337") (pin "3") (pinfunction "COM_3") (pintype "bidirectional"))
      (node (ref "L337") (pin "1") (pinfunction "1_1") (pintype "passive"))
    )
    (net (code "387") (name "Net-(D338-COM)") (class "Default")
      (node (ref "D338") (pin "3") (pinfunction "COM_3") (pintype "bidirectional"))
      (node (ref "L338") (pin "1") (pinfunction "1_1") (pintype "passive"))
    )
    (net (code "388") (name "Net-(D339-COM)") (class "Default")
      (node (ref "D339") (pin "3") (pinfunction "COM_3") (pintype "bidirectional"))
      (node (ref "L339") (pin "1") (pinfunction "1_1") (pintype "passive"))
    )
    (net (code "389") (name "Net-(D340-COM)") (class "Default")
      (node (ref "D340") (pin "3") (pinfunction "COM_3") (pintype "bidirectional"))
      (node (ref "L340") (pin "1") (pinfunction "1_1") (pintype "passive"))
    )
    (net (code "390") (name "Net-(D341-COM)") (class "Default")
      (node (ref "D341") (pin "3") (pinfunction "COM_3") (pintype "bidirectional"))
      (node (ref "L341") (pin "1") (pinfunction "1_1") (pintype "passive"))
    )
    (net (code "391") (name "Net-(D342-COM)") (class "Default")
      (node (ref "D342") (pin "3") (pinfunction "COM_3") (pintype "bidirectional"))
      (node (ref "L342") (pin "1") (pinfunction "1_1") (pintype "passive"))
    )
    (net (code "392") (name "Net-(D343-COM)") (class "Default")
      (node (ref "D343") (pin "3") (pinfunction "COM_3") (pintype "bidirectional"))
      (node (ref "L343") (pin "1") (pinfunction "1_1") (pintype "passive"))
    )
    (net (code "393") (name "Net-(D344-COM)") (class "Default")
      (node (ref "D344") (pin "3") (pinfunction "COM_3") (pintype "bidirectional"))
      (node (ref "L344") (pin "1") (pinfunction "1_1") (pintype "passive"))
    )
    (net (code "394") (name "Net-(D345-COM)") (class "Default")
      (node (ref "D345") (pin "3") (pinfunction "COM_3") (pintype "bidirectional"))
      (node (ref "L345") (pin "1") (pinfunction "1_1") (pintype "passive"))
    )
    (net (code "395") (name "Net-(D346-COM)") (class "Default")
      (node (ref "D346") (pin "3") (pinfunction "COM_3") (pintype "bidirectional"))
      (node (ref "L346") (pin "1") (pinfunction "1_1") (pintype "passive"))
    )
    (net (code "396") (name "Net-(D347-COM)") (class "Default")
      (node (ref "D347") (pin "3") (pinfunction "COM_3") (pintype "bidirectional"))
      (node (ref "L347") (pin "1") (pinfunction "1_1") (pintype "passive"))
    )
    (net (code "397") (name "Net-(D348-COM)") (class "Default")
      (node (ref "D348") (pin "3") (pinfunction "COM_3") (pintype "bidirectional"))
      (node (ref "L348") (pin "1") (pinfunction "1_1") (pintype "passive"))
    )
    (net (code "398") (name "Net-(D349-COM)") (class "Default")
      (node (ref "D349") (pin "3") (pinfunction "COM_3") (pintype "bidirectional"))
      (node (ref "L349") (pin "1") (pinfunction "1_1") (pintype "passive"))
    )
    (net (code "399") (name "Net-(D350-COM)") (class "Default")
      (node (ref "D350") (pin "3") (pinfunction "COM_3") (pintype "bidirectional"))
      (node (ref "L350") (pin "1") (pinfunction "1_1") (pintype "passive"))
    )
    (net (code "400") (name "Net-(D351-COM)") (class "Default")
      (node (ref "D351") (pin "3") (pinfunction "COM_3") (pintype "bidirectional"))
      (node (ref "L351") (pin "1") (pinfunction "1_1") (pintype "passive"))
    )
    (net (code "401") (name "Net-(D352-COM)") (class "Default")
      (node (ref "D352") (pin "3") (pinfunction "COM_3") (pintype "bidirectional"))
      (node (ref "L352") (pin "1") (pinfunction "1_1") (pintype "passive"))
    )
    (net (code "402") (name "Net-(D353-COM)") (class "Default")
      (node (ref "D353") (pin "3") (pinfunction "COM_3") (pintype "bidirectional"))
      (node (ref "L353") (pin "1") (pinfunction "1_1") (pintype "passive"))
    )
    (net (code "403") (name "Net-(D354-COM)") (class "Default")
      (node (ref "D354") (pin "3") (pinfunction "COM_3") (pintype "bidirectional"))
      (node (ref "L354") (pin "1") (pinfunction "1_1") (pintype "passive"))
    )
    (net (code "404") (name "Net-(D355-COM)") (class "Default")
      (node (ref "D355") (pin "3") (pinfunction "COM_3") (pintype "bidirectional"))
      (node (ref "L355") (pin "1") (pinfunction "1_1") (pintype "passive"))
    )
    (net (code "405") (name "Net-(D356-COM)") (class "Default")
      (node (ref "D356") (pin "3") (pinfunction "COM_3") (pintype "bidirectional"))
      (node (ref "L356") (pin "1") (pinfunction "1_1") (pintype "passive"))
    )
    (net (code "406") (name "Net-(D357-COM)") (class "Default")
      (node (ref "D357") (pin "3") (pinfunction "COM_3") (pintype "bidirectional"))
      (node (ref "L357") (pin "1") (pinfunction "1_1") (pintype "passive"))
    )
    (net (code "407") (name "Net-(D358-COM)") (class "Default")
      (node (ref "D358") (pin "3") (pinfunction "COM_3") (pintype "bidirectional"))
      (node (ref "L358") (pin "1") (pinfunction "1_1") (pintype "passive"))
    )
    (net (code "408") (name "Net-(D359-COM)") (class "Default")
      (node (ref "D359") (pin "3") (pinfunction "COM_3") (pintype "bidirectional"))
      (node (ref "L359") (pin "1") (pinfunction "1_1") (pintype "passive"))
    )
    (net (code "409") (name "Net-(D360-COM)") (class "Default")
      (node (ref "D360") (pin "3") (pinfunction "COM_3") (pintype "bidirectional"))
      (node (ref "L360") (pin "1") (pinfunction "1_1") (pintype "passive"))
    )
    (net (code "410") (name "Net-(D361-COM)") (class "Default")
      (node (ref "D361") (pin "3") (pinfunction "COM_3") (pintype "bidirectional"))
      (node (ref "L361") (pin "1") (pinfunction "1_1") (pintype "passive"))
    )
    (net (code "411") (name "Net-(D362-COM)") (class "Default")
      (node (ref "D362") (pin "3") (pinfunction "COM_3") (pintype "bidirectional"))
      (node (ref "L362") (pin "1") (pinfunction "1_1") (pintype "passive"))
    )
    (net (code "412") (name "Net-(D363-COM)") (class "Default")
      (node (ref "D363") (pin "3") (pinfunction "COM_3") (pintype "bidirectional"))
      (node (ref "L363") (pin "1") (pinfunction "1_1") (pintype "passive"))
    )
    (net (code "413") (name "Net-(D364-COM)") (class "Default")
      (node (ref "D364") (pin "3") (pinfunction "COM_3") (pintype "bidirectional"))
      (node (ref "L364") (pin "1") (pinfunction "1_1") (pintype "passive"))
    )
    (net (code "414") (name "Net-(D365-COM)") (class "Default")
      (node (ref "D365") (pin "3") (pinfunction "COM_3") (pintype "bidirectional"))
      (node (ref "L365") (pin "1") (pinfunction "1_1") (pintype "passive"))
    )
    (net (code "415") (name "Net-(D366-COM)") (class "Default")
      (node (ref "D366") (pin "3") (pinfunction "COM_3") (pintype "bidirectional"))
      (node (ref "L366") (pin "1") (pinfunction "1_1") (pintype "passive"))
    )
    (net (code "416") (name "Net-(D367-COM)") (class "Default")
      (node (ref "D367") (pin "3") (pinfunction "COM_3") (pintype "bidirectional"))
      (node (ref "L367") (pin "1") (pinfunction "1_1") (pintype "passive"))
    )
    (net (code "417") (name "Net-(D368-COM)") (class "Default")
      (node (ref "D368") (pin "3") (pinfunction "COM_3") (pintype "bidirectional"))
      (node (ref "L368") (pin "1") (pinfunction "1_1") (pintype "passive"))
    )
    (net (code "418") (name "Net-(D369-COM)") (class "Default")
      (node (ref "D369") (pin "3") (pinfunction "COM_3") (pintype "bidirectional"))
      (node (ref "L369") (pin "1") (pinfunction "1_1") (pintype "passive"))
    )
    (net (code "419") (name "Net-(D370-COM)") (class "Default")
      (node (ref "D370") (pin "3") (pinfunction "COM_3") (pintype "bidirectional"))
      (node (ref "L370") (pin "1") (pinfunction "1_1") (pintype "passive"))
    )
    (net (code "420") (name "Net-(D371-COM)") (class "Default")
      (node (ref "D371") (pin "3") (pinfunction "COM_3") (pintype "bidirectional"))
      (node (ref "L371") (pin "1") (pinfunction "1_1") (pintype "passive"))
    )
    (net (code "421") (name "Net-(D372-COM)") (class "Default")
      (node (ref "D372") (pin "3") (pinfunction "COM_3") (pintype "bidirectional"))
      (node (ref "L372") (pin "1") (pinfunction "1_1") (pintype "passive"))
    )
    (net (code "422") (name "Net-(D373-COM)") (class "Default")
      (node (ref "D373") (pin "3") (pinfunction "COM_3") (pintype "bidirectional"))
      (node (ref "L373") (pin "1") (pinfunction "1_1") (pintype "passive"))
    )
    (net (code "423") (name "Net-(D374-COM)") (class "Default")
      (node (ref "D374") (pin "3") (pinfunction "COM_3") (pintype "bidirectional"))
      (node (ref "L374") (pin "1") (pinfunction "1_1") (pintype "passive"))
    )
    (net (code "424") (name "Net-(D375-COM)") (class "Default")
      (node (ref "D375") (pin "3") (pinfunction "COM_3") (pintype "bidirectional"))
      (node (ref "L375") (pin "1") (pinfunction "1_1") (pintype "passive"))
    )
    (net (code "425") (name "Net-(D376-COM)") (class "Default")
      (node (ref "D376") (pin "3") (pinfunction "COM_3") (pintype "bidirectional"))
      (node (ref "L376") (pin "1") (pinfunction "1_1") (pintype "passive"))
    )
    (net (code "426") (name "Net-(D377-COM)") (class "Default")
      (node (ref "D377") (pin "3") (pinfunction "COM_3") (pintype "bidirectional"))
      (node (ref "L377") (pin "1") (pinfunction "1_1") (pintype "passive"))
    )
    (net (code "427") (name "Net-(D378-COM)") (class "Default")
      (node (ref "D378") (pin "3") (pinfunction "COM_3") (pintype "bidirectional"))
      (node (ref "L378") (pin "1") (pinfunction "1_1") (pintype "passive"))
    )
    (net (code "428") (name "Net-(D379-COM)") (class "Default")
      (node (ref "D379") (pin "3") (pinfunction "COM_3") (pintype "bidirectional"))
      (node (ref "L379") (pin "1") (pinfunction "1_1") (pintype "passive"))
    )
    (net (code "429") (name "Net-(D380-COM)") (class "Default")
      (node (ref "D380") (pin "3") (pinfunction "COM_3") (pintype "bidirectional"))
      (node (ref "L380") (pin "1") (pinfunction "1_1") (pintype "passive"))
    )
    (net (code "430") (name "Net-(D381-COM)") (class "Default")
      (node (ref "D381") (pin "3") (pinfunction "COM_3") (pintype "bidirectional"))
      (node (ref "L381") (pin "1") (pinfunction "1_1") (pintype "passive"))
    )
    (net (code "431") (name "Net-(D382-COM)") (class "Default")
      (node (ref "D382") (pin "3") (pinfunction "COM_3") (pintype "bidirectional"))
      (node (ref "L382") (pin "1") (pinfunction "1_1") (pintype "passive"))
    )
    (net (code "432") (name "Net-(D383-COM)") (class "Default")
      (node (ref "D383") (pin "3") (pinfunction "COM_3") (pintype "bidirectional"))
      (node (ref "L383") (pin "1") (pinfunction "1_1") (pintype "passive"))
    )
    (net (code "433") (name "Net-(D384-COM)") (class "Default")
      (node (ref "D384") (pin "3") (pinfunction "COM_3") (pintype "bidirectional"))
      (node (ref "L384") (pin "1") (pinfunction "1_1") (pintype "passive"))
    )
    (net (code "434") (name "Net-(D385-COM)") (class "Default")
      (node (ref "D385") (pin "3") (pinfunction "COM_3") (pintype "bidirectional"))
      (node (ref "L385") (pin "1") (pinfunction "1_1") (pintype "passive"))
    )
    (net (code "435") (name "Net-(D386-COM)") (class "Default")
      (node (ref "D386") (pin "3") (pinfunction "COM_3") (pintype "bidirectional"))
      (node (ref "L386") (pin "1") (pinfunction "1_1") (pintype "passive"))
    )
    (net (code "436") (name "Net-(D387-COM)") (class "Default")
      (node (ref "D387") (pin "3") (pinfunction "COM_3") (pintype "bidirectional"))
      (node (ref "L387") (pin "1") (pinfunction "1_1") (pintype "passive"))
    )
    (net (code "437") (name "Net-(D388-COM)") (class "Default")
      (node (ref "D388") (pin "3") (pinfunction "COM_3") (pintype "bidirectional"))
      (node (ref "L388") (pin "1") (pinfunction "1_1") (pintype "passive"))
    )
    (net (code "438") (name "Net-(D389-COM)") (class "Default")
      (node (ref "D389") (pin "3") (pinfunction "COM_3") (pintype "bidirectional"))
      (node (ref "L389") (pin "1") (pinfunction "1_1") (pintype "passive"))
    )
    (net (code "439") (name "Net-(D390-COM)") (class "Default")
      (node (ref "D390") (pin "3") (pinfunction "COM_3") (pintype "bidirectional"))
      (node (ref "L390") (pin "1") (pinfunction "1_1") (pintype "passive"))
    )
    (net (code "440") (name "Net-(D391-COM)") (class "Default")
      (node (ref "D391") (pin "3") (pinfunction "COM_3") (pintype "bidirectional"))
      (node (ref "L391") (pin "1") (pinfunction "1_1") (pintype "passive"))
    )
    (net (code "441") (name "Net-(D392-COM)") (class "Default")
      (node (ref "D392") (pin "3") (pinfunction "COM_3") (pintype "bidirectional"))
      (node (ref "L392") (pin "1") (pinfunction "1_1") (pintype "passive"))
    )
    (net (code "442") (name "Net-(D393-COM)") (class "Default")
      (node (ref "D393") (pin "3") (pinfunction "COM_3") (pintype "bidirectional"))
      (node (ref "L393") (pin "1") (pinfunction "1_1") (pintype "passive"))
    )
    (net (code "443") (name "Net-(D394-COM)") (class "Default")
      (node (ref "D394") (pin "3") (pinfunction "COM_3") (pintype "bidirectional"))
      (node (ref "L394") (pin "1") (pinfunction "1_1") (pintype "passive"))
    )
    (net (code "444") (name "Net-(D395-COM)") (class "Default")
      (node (ref "D395") (pin "3") (pinfunction "COM_3") (pintype "bidirectional"))
      (node (ref "L395") (pin "1") (pinfunction "1_1") (pintype "passive"))
    )
    (net (code "445") (name "Net-(D396-COM)") (class "Default")
      (node (ref "D396") (pin "3") (pinfunction "COM_3") (pintype "bidirectional"))
      (node (ref "L396") (pin "1") (pinfunction "1_1") (pintype "passive"))
    )
    (net (code "446") (name "Net-(D397-COM)") (class "Default")
      (node (ref "D397") (pin "3") (pinfunction "COM_3") (pintype "bidirectional"))
      (node (ref "L397") (pin "1") (pinfunction "1_1") (pintype "passive"))
    )
    (net (code "447") (name "Net-(D398-COM)") (class "Default")
      (node (ref "D398") (pin "3") (pinfunction "COM_3") (pintype "bidirectional"))
      (node (ref "L398") (pin "1") (pinfunction "1_1") (pintype "passive"))
    )
    (net (code "448") (name "Net-(D399-COM)") (class "Default")
      (node (ref "D399") (pin "3") (pinfunction "COM_3") (pintype "bidirectional"))
      (node (ref "L399") (pin "1") (pinfunction "1_1") (pintype "passive"))
    )
    (net (code "449") (name "Net-(D400-COM)") (class "Default")
      (node (ref "D400") (pin "3") (pinfunction "COM_3") (pintype "bidirectional"))
      (node (ref "L400") (pin "1") (pinfunction "1_1") (pintype "passive"))
    )
    (net (code "450") (name "Net-(D401-COM)") (class "Default")
      (node (ref "D401") (pin "3") (pinfunction "COM_3") (pintype "bidirectional"))
      (node (ref "L401") (pin "1") (pinfunction "1_1") (pintype "passive"))
    )
    (net (code "451") (name "Net-(D402-COM)") (class "Default")
      (node (ref "D402") (pin "3") (pinfunction "COM_3") (pintype "bidirectional"))
      (node (ref "L402") (pin "1") (pinfunction "1_1") (pintype "passive"))
    )
    (net (code "452") (name "Net-(D403-COM)") (class "Default")
      (node (ref "D403") (pin "3") (pinfunction "COM_3") (pintype "bidirectional"))
      (node (ref "L403") (pin "1") (pinfunction "1_1") (pintype "passive"))
    )
    (net (code "453") (name "Net-(D404-COM)") (class "Default")
      (node (ref "D404") (pin "3") (pinfunction "COM_3") (pintype "bidirectional"))
      (node (ref "L404") (pin "1") (pinfunction "1_1") (pintype "passive"))
    )
    (net (code "454") (name "Net-(D405-COM)") (class "Default")
      (node (ref "D405") (pin "3") (pinfunction "COM_3") (pintype "bidirectional"))
      (node (ref "L405") (pin "1") (pinfunction "1_1") (pintype "passive"))
    )
    (net (code "455") (name "Net-(D406-COM)") (class "Default")
      (node (ref "D406") (pin "3") (pinfunction "COM_3") (pintype "bidirectional"))
      (node (ref "L406") (pin "1") (pinfunction "1_1") (pintype "passive"))
    )
    (net (code "456") (name "Net-(D407-COM)") (class "Default")
      (node (ref "D407") (pin "3") (pinfunction "COM_3") (pintype "bidirectional"))
      (node (ref "L407") (pin "1") (pinfunction "1_1") (pintype "passive"))
    )
    (net (code "457") (name "Net-(D408-COM)") (class "Default")
      (node (ref "D408") (pin "3") (pinfunction "COM_3") (pintype "bidirectional"))
      (node (ref "L408") (pin "1") (pinfunction "1_1") (pintype "passive"))
    )
    (net (code "458") (name "Net-(D409-COM)") (class "Default")
      (node (ref "D409") (pin "3") (pinfunction "COM_3") (pintype "bidirectional"))
      (node (ref "L409") (pin "1") (pinfunction "1_1") (pintype "passive"))
    )
    (net (code "459") (name "Net-(D410-COM)") (class "Default")
      (node (ref "D410") (pin "3") (pinfunction "COM_3") (pintype "bidirectional"))
      (node (ref "L410") (pin "1") (pinfunction "1_1") (pintype "passive"))
    )
    (net (code "460") (name "Net-(D411-COM)") (class "Default")
      (node (ref "D411") (pin "3") (pinfunction "COM_3") (pintype "bidirectional"))
      (node (ref "L411") (pin "1") (pinfunction "1_1") (pintype "passive"))
    )
    (net (code "461") (name "Net-(D412-COM)") (class "Default")
      (node (ref "D412") (pin "3") (pinfunction "COM_3") (pintype "bidirectional"))
      (node (ref "L412") (pin "1") (pinfunction "1_1") (pintype "passive"))
    )
    (net (code "462") (name "Net-(D413-COM)") (class "Default")
      (node (ref "D413") (pin "3") (pinfunction "COM_3") (pintype "bidirectional"))
      (node (ref "L413") (pin "1") (pinfunction "1_1") (pintype "passive"))
    )
    (net (code "463") (name "Net-(D414-COM)") (class "Default")
      (node (ref "D414") (pin "3") (pinfunction "COM_3") (pintype "bidirectional"))
      (node (ref "L414") (pin "1") (pinfunction "1_1") (pintype "passive"))
    )
    (net (code "464") (name "Net-(D415-COM)") (class "Default")
      (node (ref "D415") (pin "3") (pinfunction "COM_3") (pintype "bidirectional"))
      (node (ref "L415") (pin "1") (pinfunction "1_1") (pintype "passive"))
    )
    (net (code "465") (name "Net-(D416-COM)") (class "Default")
      (node (ref "D416") (pin "3") (pinfunction "COM_3") (pintype "bidirectional"))
      (node (ref "L416") (pin "1") (pinfunction "1_1") (pintype "passive"))
    )
    (net (code "466") (name "Net-(D417-COM)") (class "Default")
      (node (ref "D417") (pin "3") (pinfunction "COM_3") (pintype "bidirectional"))
      (node (ref "L417") (pin "1") (pinfunction "1_1") (pintype "passive"))
    )
    (net (code "467") (name "Net-(D418-COM)") (class "Default")
      (node (ref "D418") (pin "3") (pinfunction "COM_3") (pintype "bidirectional"))
      (node (ref "L418") (pin "1") (pinfunction "1_1") (pintype "passive"))
    )
    (net (code "468") (name "Net-(D419-COM)") (class "Default")
      (node (ref "D419") (pin "3") (pinfunction "COM_3") (pintype "bidirectional"))
      (node (ref "L419") (pin "1") (pinfunction "1_1") (pintype "passive"))
    )
    (net (code "469") (name "Net-(D420-COM)") (class "Default")
      (node (ref "D420") (pin "3") (pinfunction "COM_3") (pintype "bidirectional"))
      (node (ref "L420") (pin "1") (pinfunction "1_1") (pintype "passive"))
    )
    (net (code "470") (name "Net-(D421-COM)") (class "Default")
      (node (ref "D421") (pin "3") (pinfunction "COM_3") (pintype "bidirectional"))
      (node (ref "L421") (pin "1") (pinfunction "1_1") (pintype "passive"))
    )
    (net (code "471") (name "Net-(D422-COM)") (class "Default")
      (node (ref "D422") (pin "3") (pinfunction "COM_3") (pintype "bidirectional"))
      (node (ref "L422") (pin "1") (pinfunction "1_1") (pintype "passive"))
    )
    (net (code "472") (name "Net-(D423-COM)") (class "Default")
      (node (ref "D423") (pin "3") (pinfunction "COM_3") (pintype "bidirectional"))
      (node (ref "L423") (pin "1") (pinfunction "1_1") (pintype "passive"))
    )
    (net (code "473") (name "Net-(D424-COM)") (class "Default")
      (node (ref "D424") (pin "3") (pinfunction "COM_3") (pintype "bidirectional"))
      (node (ref "L424") (pin "1") (pinfunction "1_1") (pintype "passive"))
    )
    (net (code "474") (name "Net-(D425-COM)") (class "Default")
      (node (ref "D425") (pin "3") (pinfunction "COM_3") (pintype "bidirectional"))
      (node (ref "L425") (pin "1") (pinfunction "1_1") (pintype "passive"))
    )
    (net (code "475") (name "Net-(D426-COM)") (class "Default")
      (node (ref "D426") (pin "3") (pinfunction "COM_3") (pintype "bidirectional"))
      (node (ref "L426") (pin "1") (pinfunction "1_1") (pintype "passive"))
    )
    (net (code "476") (name "Net-(D427-COM)") (class "Default")
      (node (ref "D427") (pin "3") (pinfunction "COM_3") (pintype "bidirectional"))
      (node (ref "L427") (pin "1") (pinfunction "1_1") (pintype "passive"))
    )
    (net (code "477") (name "Net-(D428-COM)") (class "Default")
      (node (ref "D428") (pin "3") (pinfunction "COM_3") (pintype "bidirectional"))
      (node (ref "L428") (pin "1") (pinfunction "1_1") (pintype "passive"))
    )
    (net (code "478") (name "Net-(D429-COM)") (class "Default")
      (node (ref "D429") (pin "3") (pinfunction "COM_3") (pintype "bidirectional"))
      (node (ref "L429") (pin "1") (pinfunction "1_1") (pintype "passive"))
    )
    (net (code "479") (name "Net-(D430-COM)") (class "Default")
      (node (ref "D430") (pin "3") (pinfunction "COM_3") (pintype "bidirectional"))
      (node (ref "L430") (pin "1") (pinfunction "1_1") (pintype "passive"))
    )
    (net (code "480") (name "Net-(D431-COM)") (class "Default")
      (node (ref "D431") (pin "3") (pinfunction "COM_3") (pintype "bidirectional"))
      (node (ref "L431") (pin "1") (pinfunction "1_1") (pintype "passive"))
    )
    (net (code "481") (name "Net-(D432-COM)") (class "Default")
      (node (ref "D432") (pin "3") (pinfunction "COM_3") (pintype "bidirectional"))
      (node (ref "L432") (pin "1") (pinfunction "1_1") (pintype "passive"))
    )
    (net (code "482") (name "Net-(D433-COM)") (class "Default")
      (node (ref "D433") (pin "3") (pinfunction "COM_3") (pintype "bidirectional"))
      (node (ref "L433") (pin "1") (pinfunction "1_1") (pintype "passive"))
    )
    (net (code "483") (name "Net-(D434-COM)") (class "Default")
      (node (ref "D434") (pin "3") (pinfunction "COM_3") (pintype "bidirectional"))
      (node (ref "L434") (pin "1") (pinfunction "1_1") (pintype "passive"))
    )
    (net (code "484") (name "Net-(D435-COM)") (class "Default")
      (node (ref "D435") (pin "3") (pinfunction "COM_3") (pintype "bidirectional"))
      (node (ref "L435") (pin "1") (pinfunction "1_1") (pintype "passive"))
    )
    (net (code "485") (name "Net-(D436-COM)") (class "Default")
      (node (ref "D436") (pin "3") (pinfunction "COM_3") (pintype "bidirectional"))
      (node (ref "L436") (pin "1") (pinfunction "1_1") (pintype "passive"))
    )
    (net (code "486") (name "Net-(D437-COM)") (class "Default")
      (node (ref "D437") (pin "3") (pinfunction "COM_3") (pintype "bidirectional"))
      (node (ref "L437") (pin "1") (pinfunction "1_1") (pintype "passive"))
    )
    (net (code "487") (name "Net-(D438-COM)") (class "Default")
      (node (ref "D438") (pin "3") (pinfunction "COM_3") (pintype "bidirectional"))
      (node (ref "L438") (pin "1") (pinfunction "1_1") (pintype "passive"))
    )
    (net (code "488") (name "Net-(D439-COM)") (class "Default")
      (node (ref "D439") (pin "3") (pinfunction "COM_3") (pintype "bidirectional"))
      (node (ref "L439") (pin "1") (pinfunction "1_1") (pintype "passive"))
    )
    (net (code "489") (name "Net-(D440-COM)") (class "Default")
      (node (ref "D440") (pin "3") (pinfunction "COM_3") (pintype "bidirectional"))
      (node (ref "L440") (pin "1") (pinfunction "1_1") (pintype "passive"))
    )
    (net (code "490") (name "Net-(D441-COM)") (class "Default")
      (node (ref "D441") (pin "3") (pinfunction "COM_3") (pintype "bidirectional"))
      (node (ref "L441") (pin "1") (pinfunction "1_1") (pintype "passive"))
    )
    (net (code "491") (name "Net-(D442-COM)") (class "Default")
      (node (ref "D442") (pin "3") (pinfunction "COM_3") (pintype "bidirectional"))
      (node (ref "L442") (pin "1") (pinfunction "1_1") (pintype "passive"))
    )
    (net (code "492") (name "Net-(D443-COM)") (class "Default")
      (node (ref "D443") (pin "3") (pinfunction "COM_3") (pintype "bidirectional"))
      (node (ref "L443") (pin "1") (pinfunction "1_1") (pintype "passive"))
    )
    (net (code "493") (name "Net-(D444-COM)") (class "Default")
      (node (ref "D444") (pin "3") (pinfunction "COM_3") (pintype "bidirectional"))
      (node (ref "L444") (pin "1") (pinfunction "1_1") (pintype "passive"))
    )
    (net (code "494") (name "Net-(D445-COM)") (class "Default")
      (node (ref "D445") (pin "3") (pinfunction "COM_3") (pintype "bidirectional"))
      (node (ref "L445") (pin "1") (pinfunction "1_1") (pintype "passive"))
    )
    (net (code "495") (name "Net-(D446-COM)") (class "Default")
      (node (ref "D446") (pin "3") (pinfunction "COM_3") (pintype "bidirectional"))
      (node (ref "L446") (pin "1") (pinfunction "1_1") (pintype "passive"))
    )
    (net (code "496") (name "Net-(D447-COM)") (class "Default")
      (node (ref "D447") (pin "3") (pinfunction "COM_3") (pintype "bidirectional"))
      (node (ref "L447") (pin "1") (pinfunction "1_1") (pintype "passive"))
    )
    (net (code "497") (name "Net-(D448-COM)") (class "Default")
      (node (ref "D448") (pin "3") (pinfunction "COM_3") (pintype "bidirectional"))
      (node (ref "L448") (pin "1") (pinfunction "1_1") (pintype "passive"))
    )
    (net (code "498") (name "Net-(D449-COM)") (class "Default")
      (node (ref "D449") (pin "3") (pinfunction "COM_3") (pintype "bidirectional"))
      (node (ref "L449") (pin "1") (pinfunction "1_1") (pintype "passive"))
    )
    (net (code "499") (name "Net-(D450-COM)") (class "Default")
      (node (ref "D450") (pin "3") (pinfunction "COM_3") (pintype "bidirectional"))
      (node (ref "L450") (pin "1") (pinfunction "1_1") (pintype "passive"))
    )
    (net (code "500") (name "Net-(D451-COM)") (class "Default")
      (node (ref "D451") (pin "3") (pinfunction "COM_3") (pintype "bidirectional"))
      (node (ref "L451") (pin "1") (pinfunction "1_1") (pintype "passive"))
    )
    (net (code "501") (name "Net-(D452-COM)") (class "Default")
      (node (ref "D452") (pin "3") (pinfunction "COM_3") (pintype "bidirectional"))
      (node (ref "L452") (pin "1") (pinfunction "1_1") (pintype "passive"))
    )
    (net (code "502") (name "Net-(D453-COM)") (class "Default")
      (node (ref "D453") (pin "3") (pinfunction "COM_3") (pintype "bidirectional"))
      (node (ref "L453") (pin "1") (pinfunction "1_1") (pintype "passive"))
    )
    (net (code "503") (name "Net-(D454-COM)") (class "Default")
      (node (ref "D454") (pin "3") (pinfunction "COM_3") (pintype "bidirectional"))
      (node (ref "L454") (pin "1") (pinfunction "1_1") (pintype "passive"))
    )
    (net (code "504") (name "Net-(D455-COM)") (class "Default")
      (node (ref "D455") (pin "3") (pinfunction "COM_3") (pintype "bidirectional"))
      (node (ref "L455") (pin "1") (pinfunction "1_1") (pintype "passive"))
    )
    (net (code "505") (name "Net-(D456-COM)") (class "Default")
      (node (ref "D456") (pin "3") (pinfunction "COM_3") (pintype "bidirectional"))
      (node (ref "L456") (pin "1") (pinfunction "1_1") (pintype "passive"))
    )
    (net (code "506") (name "Net-(D457-COM)") (class "Default")
      (node (ref "D457") (pin "3") (pinfunction "COM_3") (pintype "bidirectional"))
      (node (ref "L457") (pin "1") (pinfunction "1_1") (pintype "passive"))
    )
    (net (code "507") (name "Net-(D458-COM)") (class "Default")
      (node (ref "D458") (pin "3") (pinfunction "COM_3") (pintype "bidirectional"))
      (node (ref "L458") (pin "1") (pinfunction "1_1") (pintype "passive"))
    )
    (net (code "508") (name "Net-(D459-COM)") (class "Default")
      (node (ref "D459") (pin "3") (pinfunction "COM_3") (pintype "bidirectional"))
      (node (ref "L459") (pin "1") (pinfunction "1_1") (pintype "passive"))
    )
    (net (code "509") (name "Net-(D460-COM)") (class "Default")
      (node (ref "D460") (pin "3") (pinfunction "COM_3") (pintype "bidirectional"))
      (node (ref "L460") (pin "1") (pinfunction "1_1") (pintype "passive"))
    )
    (net (code "510") (name "Net-(D461-COM)") (class "Default")
      (node (ref "D461") (pin "3") (pinfunction "COM_3") (pintype "bidirectional"))
      (node (ref "L461") (pin "1") (pinfunction "1_1") (pintype "passive"))
    )
    (net (code "511") (name "Net-(D462-COM)") (class "Default")
      (node (ref "D462") (pin "3") (pinfunction "COM_3") (pintype "bidirectional"))
      (node (ref "L462") (pin "1") (pinfunction "1_1") (pintype "passive"))
    )
    (net (code "512") (name "Net-(D463-COM)") (class "Default")
      (node (ref "D463") (pin "3") (pinfunction "COM_3") (pintype "bidirectional"))
      (node (ref "L463") (pin "1") (pinfunction "1_1") (pintype "passive"))
    )
    (net (code "513") (name "Net-(D464-COM)") (class "Default")
      (node (ref "D464") (pin "3") (pinfunction "COM_3") (pintype "bidirectional"))
      (node (ref "L464") (pin "1") (pinfunction "1_1") (pintype "passive"))
    )
    (net (code "514") (name "Net-(D465-COM)") (class "Default")
      (node (ref "D465") (pin "3") (pinfunction "COM_3") (pintype "bidirectional"))
      (node (ref "L465") (pin "1") (pinfunction "1_1") (pintype "passive"))
    )
    (net (code "515") (name "Net-(D466-COM)") (class "Default")
      (node (ref "D466") (pin "3") (pinfunction "COM_3") (pintype "bidirectional"))
      (node (ref "L466") (pin "1") (pinfunction "1_1") (pintype "passive"))
    )
    (net (code "516") (name "Net-(D467-COM)") (class "Default")
      (node (ref "D467") (pin "3") (pinfunction "COM_3") (pintype "bidirectional"))
      (node (ref "L467") (pin "1") (pinfunction "1_1") (pintype "passive"))
    )
    (net (code "517") (name "Net-(D468-COM)") (class "Default")
      (node (ref "D468") (pin "3") (pinfunction "COM_3") (pintype "bidirectional"))
      (node (ref "L468") (pin "1") (pinfunction "1_1") (pintype "passive"))
    )
    (net (code "518") (name "Net-(D469-COM)") (class "Default")
      (node (ref "D469") (pin "3") (pinfunction "COM_3") (pintype "bidirectional"))
      (node (ref "L469") (pin "1") (pinfunction "1_1") (pintype "passive"))
    )
    (net (code "519") (name "Net-(D470-COM)") (class "Default")
      (node (ref "D470") (pin "3") (pinfunction "COM_3") (pintype "bidirectional"))
      (node (ref "L470") (pin "1") (pinfunction "1_1") (pintype "passive"))
    )
    (net (code "520") (name "Net-(D471-COM)") (class "Default")
      (node (ref "D471") (pin "3") (pinfunction "COM_3") (pintype "bidirectional"))
      (node (ref "L471") (pin "1") (pinfunction "1_1") (pintype "passive"))
    )
    (net (code "521") (name "Net-(D472-COM)") (class "Default")
      (node (ref "D472") (pin "3") (pinfunction "COM_3") (pintype "bidirectional"))
      (node (ref "L472") (pin "1") (pinfunction "1_1") (pintype "passive"))
    )
    (net (code "522") (name "Net-(D473-COM)") (class "Default")
      (node (ref "D473") (pin "3") (pinfunction "COM_3") (pintype "bidirectional"))
      (node (ref "L473") (pin "1") (pinfunction "1_1") (pintype "passive"))
    )
    (net (code "523") (name "Net-(D474-COM)") (class "Default")
      (node (ref "D474") (pin "3") (pinfunction "COM_3") (pintype "bidirectional"))
      (node (ref "L474") (pin "1") (pinfunction "1_1") (pintype "passive"))
    )
    (net (code "524") (name "Net-(D475-COM)") (class "Default")
      (node (ref "D475") (pin "3") (pinfunction "COM_3") (pintype "bidirectional"))
      (node (ref "L475") (pin "1") (pinfunction "1_1") (pintype "passive"))
    )
    (net (code "525") (name "Net-(D476-COM)") (class "Default")
      (node (ref "D476") (pin "3") (pinfunction "COM_3") (pintype "bidirectional"))
      (node (ref "L476") (pin "1") (pinfunction "1_1") (pintype "passive"))
    )
    (net (code "526") (name "Net-(D477-COM)") (class "Default")
      (node (ref "D477") (pin "3") (pinfunction "COM_3") (pintype "bidirectional"))
      (node (ref "L477") (pin "1") (pinfunction "1_1") (pintype "passive"))
    )
    (net (code "527") (name "Net-(D478-COM)") (class "Default")
      (node (ref "D478") (pin "3") (pinfunction "COM_3") (pintype "bidirectional"))
      (node (ref "L478") (pin "1") (pinfunction "1_1") (pintype "passive"))
    )
    (net (code "528") (name "Net-(D479-COM)") (class "Default")
      (node (ref "D479") (pin "3") (pinfunction "COM_3") (pintype "bidirectional"))
      (node (ref "L479") (pin "1") (pinfunction "1_1") (pintype "passive"))
    )
    (net (code "529") (name "Net-(D480-COM)") (class "Default")
      (node (ref "D480") (pin "3") (pinfunction "COM_3") (pintype "bidirectional"))
      (node (ref "L480") (pin "1") (pinfunction "1_1") (pintype "passive"))
    )
    (net (code "530") (name "Net-(D481-COM)") (class "Default")
      (node (ref "D481") (pin "3") (pinfunction "COM_3") (pintype "bidirectional"))
      (node (ref "L481") (pin "1") (pinfunction "1_1") (pintype "passive"))
    )
    (net (code "531") (name "Net-(D482-COM)") (class "Default")
      (node (ref "D482") (pin "3") (pinfunction "COM_3") (pintype "bidirectional"))
      (node (ref "L482") (pin "1") (pinfunction "1_1") (pintype "passive"))
    )
    (net (code "532") (name "Net-(D483-COM)") (class "Default")
      (node (ref "D483") (pin "3") (pinfunction "COM_3") (pintype "bidirectional"))
      (node (ref "L483") (pin "1") (pinfunction "1_1") (pintype "passive"))
    )
    (net (code "533") (name "Net-(D484-COM)") (class "Default")
      (node (ref "D484") (pin "3") (pinfunction "COM_3") (pintype "bidirectional"))
      (node (ref "L484") (pin "1") (pinfunction "1_1") (pintype "passive"))
    )
    (net (code "534") (name "Net-(D485-COM)") (class "Default")
      (node (ref "D485") (pin "3") (pinfunction "COM_3") (pintype "bidirectional"))
      (node (ref "L485") (pin "1") (pinfunction "1_1") (pintype "passive"))
    )
    (net (code "535") (name "Net-(D486-COM)") (class "Default")
      (node (ref "D486") (pin "3") (pinfunction "COM_3") (pintype "bidirectional"))
      (node (ref "L486") (pin "1") (pinfunction "1_1") (pintype "passive"))
    )
    (net (code "536") (name "Net-(D487-COM)") (class "Default")
      (node (ref "D487") (pin "3") (pinfunction "COM_3") (pintype "bidirectional"))
      (node (ref "L487") (pin "1") (pinfunction "1_1") (pintype "passive"))
    )
    (net (code "537") (name "Net-(D488-COM)") (class "Default")
      (node (ref "D488") (pin "3") (pinfunction "COM_3") (pintype "bidirectional"))
      (node (ref "L488") (pin "1") (pinfunction "1_1") (pintype "passive"))
    )
    (net (code "538") (name "Net-(D489-COM)") (class "Default")
      (node (ref "D489") (pin "3") (pinfunction "COM_3") (pintype "bidirectional"))
      (node (ref "L489") (pin "1") (pinfunction "1_1") (pintype "passive"))
    )
    (net (code "539") (name "Net-(D490-COM)") (class "Default")
      (node (ref "D490") (pin "3") (pinfunction "COM_3") (pintype "bidirectional"))
      (node (ref "L490") (pin "1") (pinfunction "1_1") (pintype "passive"))
    )
    (net (code "540") (name "Net-(D491-COM)") (class "Default")
      (node (ref "D491") (pin "3") (pinfunction "COM_3") (pintype "bidirectional"))
      (node (ref "L491") (pin "1") (pinfunction "1_1") (pintype "passive"))
    )
    (net (code "541") (name "Net-(D492-COM)") (class "Default")
      (node (ref "D492") (pin "3") (pinfunction "COM_3") (pintype "bidirectional"))
      (node (ref "L492") (pin "1") (pinfunction "1_1") (pintype "passive"))
    )
    (net (code "542") (name "Net-(D493-COM)") (class "Default")
      (node (ref "D493") (pin "3") (pinfunction "COM_3") (pintype "bidirectional"))
      (node (ref "L493") (pin "1") (pinfunction "1_1") (pintype "passive"))
    )
    (net (code "543") (name "Net-(D494-COM)") (class "Default")
      (node (ref "D494") (pin "3") (pinfunction "COM_3") (pintype "bidirectional"))
      (node (ref "L494") (pin "1") (pinfunction "1_1") (pintype "passive"))
    )
    (net (code "544") (name "Net-(D495-COM)") (class "Default")
      (node (ref "D495") (pin "3") (pinfunction "COM_3") (pintype "bidirectional"))
      (node (ref "L495") (pin "1") (pinfunction "1_1") (pintype "passive"))
    )
    (net (code "545") (name "Net-(D496-COM)") (class "Default")
      (node (ref "D496") (pin "3") (pinfunction "COM_3") (pintype "bidirectional"))
      (node (ref "L496") (pin "1") (pinfunction "1_1") (pintype "passive"))
    )
    (net (code "546") (name "Net-(D497-COM)") (class "Default")
      (node (ref "D497") (pin "3") (pinfunction "COM_3") (pintype "bidirectional"))
      (node (ref "L497") (pin "1") (pinfunction "1_1") (pintype "passive"))
    )
    (net (code "547") (name "Net-(D498-COM)") (class "Default")
      (node (ref "D498") (pin "3") (pinfunction "COM_3") (pintype "bidirectional"))
      (node (ref "L498") (pin "1") (pinfunction "1_1") (pintype "passive"))
    )
    (net (code "548") (name "Net-(D499-COM)") (class "Default")
      (node (ref "D499") (pin "3") (pinfunction "COM_3") (pintype "bidirectional"))
      (node (ref "L499") (pin "1") (pinfunction "1_1") (pintype "passive"))
    )
    (net (code "549") (name "Net-(D500-COM)") (class "Default")
      (node (ref "D500") (pin "3") (pinfunction "COM_3") (pintype "bidirectional"))
      (node (ref "L500") (pin "1") (pinfunction "1_1") (pintype "passive"))
    )
    (net (code "550") (name "Net-(D501-COM)") (class "Default")
      (node (ref "D501") (pin "3") (pinfunction "COM_3") (pintype "bidirectional"))
      (node (ref "L501") (pin "1") (pinfunction "1_1") (pintype "passive"))
    )
    (net (code "551") (name "Net-(D502-COM)") (class "Default")
      (node (ref "D502") (pin "3") (pinfunction "COM_3") (pintype "bidirectional"))
      (node (ref "L502") (pin "1") (pinfunction "1_1") (pintype "passive"))
    )
    (net (code "552") (name "Net-(D503-COM)") (class "Default")
      (node (ref "D503") (pin "3") (pinfunction "COM_3") (pintype "bidirectional"))
      (node (ref "L503") (pin "1") (pinfunction "1_1") (pintype "passive"))
    )
    (net (code "553") (name "Net-(D504-COM)") (class "Default")
      (node (ref "D504") (pin "3") (pinfunction "COM_3") (pintype "bidirectional"))
      (node (ref "L504") (pin "1") (pinfunction "1_1") (pintype "passive"))
    )
    (net (code "554") (name "Net-(D505-COM)") (class "Default")
      (node (ref "D505") (pin "3") (pinfunction "COM_3") (pintype "bidirectional"))
      (node (ref "L505") (pin "1") (pinfunction "1_1") (pintype "passive"))
    )
    (net (code "555") (name "Net-(D506-COM)") (class "Default")
      (node (ref "D506") (pin "3") (pinfunction "COM_3") (pintype "bidirectional"))
      (node (ref "L506") (pin "1") (pinfunction "1_1") (pintype "passive"))
    )
    (net (code "556") (name "Net-(D507-COM)") (class "Default")
      (node (ref "D507") (pin "3") (pinfunction "COM_3") (pintype "bidirectional"))
      (node (ref "L507") (pin "1") (pinfunction "1_1") (pintype "passive"))
    )
    (net (code "557") (name "Net-(D508-COM)") (class "Default")
      (node (ref "D508") (pin "3") (pinfunction "COM_3") (pintype "bidirectional"))
      (node (ref "L508") (pin "1") (pinfunction "1_1") (pintype "passive"))
    )
    (net (code "558") (name "Net-(D509-COM)") (class "Default")
      (node (ref "D509") (pin "3") (pinfunction "COM_3") (pintype "bidirectional"))
      (node (ref "L509") (pin "1") (pinfunction "1_1") (pintype "passive"))
    )
    (net (code "559") (name "Net-(D510-COM)") (class "Default")
      (node (ref "D510") (pin "3") (pinfunction "COM_3") (pintype "bidirectional"))
      (node (ref "L510") (pin "1") (pinfunction "1_1") (pintype "passive"))
    )
    (net (code "560") (name "Net-(D511-COM)") (class "Default")
      (node (ref "D511") (pin "3") (pinfunction "COM_3") (pintype "bidirectional"))
      (node (ref "L511") (pin "1") (pinfunction "1_1") (pintype "passive"))
    )
    (net (code "561") (name "Net-(D512-COM)") (class "Default")
      (node (ref "D512") (pin "3") (pinfunction "COM_3") (pintype "bidirectional"))
      (node (ref "L512") (pin "1") (pinfunction "1_1") (pintype "passive"))
    )
    (net (code "562") (name "Net-(D513-COM)") (class "Default")
      (node (ref "D513") (pin "3") (pinfunction "COM_3") (pintype "bidirectional"))
      (node (ref "L513") (pin "1") (pinfunction "1_1") (pintype "passive"))
    )
    (net (code "563") (name "Net-(D514-COM)") (class "Default")
      (node (ref "D514") (pin "3") (pinfunction "COM_3") (pintype "bidirectional"))
      (node (ref "L514") (pin "1") (pinfunction "1_1") (pintype "passive"))
    )
    (net (code "564") (name "Net-(D515-COM)") (class "Default")
      (node (ref "D515") (pin "3") (pinfunction "COM_3") (pintype "bidirectional"))
      (node (ref "L515") (pin "1") (pinfunction "1_1") (pintype "passive"))
    )
    (net (code "565") (name "Net-(D516-COM)") (class "Default")
      (node (ref "D516") (pin "3") (pinfunction "COM_3") (pintype "bidirectional"))
      (node (ref "L516") (pin "1") (pinfunction "1_1") (pintype "passive"))
    )
    (net (code "566") (name "Net-(D517-COM)") (class "Default")
      (node (ref "D517") (pin "3") (pinfunction "COM_3") (pintype "bidirectional"))
      (node (ref "L517") (pin "1") (pinfunction "1_1") (pintype "passive"))
    )
    (net (code "567") (name "Net-(D518-COM)") (class "Default")
      (node (ref "D518") (pin "3") (pinfunction "COM_3") (pintype "bidirectional"))
      (node (ref "L518") (pin "1") (pinfunction "1_1") (pintype "passive"))
    )
    (net (code "568") (name "Net-(D519-COM)") (class "Default")
      (node (ref "D519") (pin "3") (pinfunction "COM_3") (pintype "bidirectional"))
      (node (ref "L519") (pin "1") (pinfunction "1_1") (pintype "passive"))
    )
    (net (code "569") (name "Net-(D520-COM)") (class "Default")
      (node (ref "D520") (pin "3") (pinfunction "COM_3") (pintype "bidirectional"))
      (node (ref "L520") (pin "1") (pinfunction "1_1") (pintype "passive"))
    )
    (net (code "570") (name "Net-(D521-COM)") (class "Default")
      (node (ref "D521") (pin "3") (pinfunction "COM_3") (pintype "bidirectional"))
      (node (ref "L521") (pin "1") (pinfunction "1_1") (pintype "passive"))
    )
    (net (code "571") (name "Net-(D522-COM)") (class "Default")
      (node (ref "D522") (pin "3") (pinfunction "COM_3") (pintype "bidirectional"))
      (node (ref "L522") (pin "1") (pinfunction "1_1") (pintype "passive"))
    )
    (net (code "572") (name "Net-(D523-COM)") (class "Default")
      (node (ref "D523") (pin "3") (pinfunction "COM_3") (pintype "bidirectional"))
      (node (ref "L523") (pin "1") (pinfunction "1_1") (pintype "passive"))
    )
    (net (code "573") (name "Net-(D524-COM)") (class "Default")
      (node (ref "D524") (pin "3") (pinfunction "COM_3") (pintype "bidirectional"))
      (node (ref "L524") (pin "1") (pinfunction "1_1") (pintype "passive"))
    )
    (net (code "574") (name "Net-(D525-COM)") (class "Default")
      (node (ref "D525") (pin "3") (pinfunction "COM_3") (pintype "bidirectional"))
      (node (ref "L525") (pin "1") (pinfunction "1_1") (pintype "passive"))
    )
    (net (code "575") (name "Net-(D526-COM)") (class "Default")
      (node (ref "D526") (pin "3") (pinfunction "COM_3") (pintype "bidirectional"))
      (node (ref "L526") (pin "1") (pinfunction "1_1") (pintype "passive"))
    )
    (net (code "576") (name "Net-(D527-COM)") (class "Default")
      (node (ref "D527") (pin "3") (pinfunction "COM_3") (pintype "bidirectional"))
      (node (ref "L527") (pin "1") (pinfunction "1_1") (pintype "passive"))
    )
    (net (code "577") (name "Net-(D528-COM)") (class "Default")
      (node (ref "D528") (pin "3") (pinfunction "COM_3") (pintype "bidirectional"))
      (node (ref "L528") (pin "1") (pinfunction "1_1") (pintype "passive"))
    )
    (net (code "578") (name "Net-(D529-COM)") (class "Default")
      (node (ref "D529") (pin "3") (pinfunction "COM_3") (pintype "bidirectional"))
      (node (ref "L529") (pin "1") (pinfunction "1_1") (pintype "passive"))
    )
    (net (code "579") (name "Net-(D530-COM)") (class "Default")
      (node (ref "D530") (pin "3") (pinfunction "COM_3") (pintype "bidirectional"))
      (node (ref "L530") (pin "1") (pinfunction "1_1") (pintype "passive"))
    )
    (net (code "580") (name "Net-(D531-COM)") (class "Default")
      (node (ref "D531") (pin "3") (pinfunction "COM_3") (pintype "bidirectional"))
      (node (ref "L531") (pin "1") (pinfunction "1_1") (pintype "passive"))
    )
    (net (code "581") (name "Net-(D532-COM)") (class "Default")
      (node (ref "D532") (pin "3") (pinfunction "COM_3") (pintype "bidirectional"))
      (node (ref "L532") (pin "1") (pinfunction "1_1") (pintype "passive"))
    )
    (net (code "582") (name "Net-(D533-COM)") (class "Default")
      (node (ref "D533") (pin "3") (pinfunction "COM_3") (pintype "bidirectional"))
      (node (ref "L533") (pin "1") (pinfunction "1_1") (pintype "passive"))
    )
    (net (code "583") (name "Net-(D534-COM)") (class "Default")
      (node (ref "D534") (pin "3") (pinfunction "COM_3") (pintype "bidirectional"))
      (node (ref "L534") (pin "1") (pinfunction "1_1") (pintype "passive"))
    )
    (net (code "584") (name "Net-(D535-COM)") (class "Default")
      (node (ref "D535") (pin "3") (pinfunction "COM_3") (pintype "bidirectional"))
      (node (ref "L535") (pin "1") (pinfunction "1_1") (pintype "passive"))
    )
    (net (code "585") (name "Net-(D536-COM)") (class "Default")
      (node (ref "D536") (pin "3") (pinfunction "COM_3") (pintype "bidirectional"))
      (node (ref "L536") (pin "1") (pinfunction "1_1") (pintype "passive"))
    )
    (net (code "586") (name "Net-(D537-COM)") (class "Default")
      (node (ref "D537") (pin "3") (pinfunction "COM_3") (pintype "bidirectional"))
      (node (ref "L537") (pin "1") (pinfunction "1_1") (pintype "passive"))
    )
    (net (code "587") (name "Net-(D538-COM)") (class "Default")
      (node (ref "D538") (pin "3") (pinfunction "COM_3") (pintype "bidirectional"))
      (node (ref "L538") (pin "1") (pinfunction "1_1") (pintype "passive"))
    )
    (net (code "588") (name "Net-(D539-COM)") (class "Default")
      (node (ref "D539") (pin "3") (pinfunction "COM_3") (pintype "bidirectional"))
      (node (ref "L539") (pin "1") (pinfunction "1_1") (pintype "passive"))
    )
    (net (code "589") (name "Net-(D540-COM)") (class "Default")
      (node (ref "D540") (pin "3") (pinfunction "COM_3") (pintype "bidirectional"))
      (node (ref "L540") (pin "1") (pinfunction "1_1") (pintype "passive"))
    )
    (net (code "590") (name "Net-(D541-COM)") (class "Default")
      (node (ref "D541") (pin "3") (pinfunction "COM_3") (pintype "bidirectional"))
      (node (ref "L541") (pin "1") (pinfunction "1_1") (pintype "passive"))
    )
    (net (code "591") (name "Net-(D542-COM)") (class "Default")
      (node (ref "D542") (pin "3") (pinfunction "COM_3") (pintype "bidirectional"))
      (node (ref "L542") (pin "1") (pinfunction "1_1") (pintype "passive"))
    )
    (net (code "592") (name "Net-(D543-COM)") (class "Default")
      (node (ref "D543") (pin "3") (pinfunction "COM_3") (pintype "bidirectional"))
      (node (ref "L543") (pin "1") (pinfunction "1_1") (pintype "passive"))
    )
    (net (code "593") (name "Net-(D544-COM)") (class "Default")
      (node (ref "D544") (pin "3") (pinfunction "COM_3") (pintype "bidirectional"))
      (node (ref "L544") (pin "1") (pinfunction "1_1") (pintype "passive"))
    )
    (net (code "594") (name "Net-(D545-COM)") (class "Default")
      (node (ref "D545") (pin "3") (pinfunction "COM_3") (pintype "bidirectional"))
      (node (ref "L545") (pin "1") (pinfunction "1_1") (pintype "passive"))
    )
    (net (code "595") (name "Net-(D546-COM)") (class "Default")
      (node (ref "D546") (pin "3") (pinfunction "COM_3") (pintype "bidirectional"))
      (node (ref "L546") (pin "1") (pinfunction "1_1") (pintype "passive"))
    )
    (net (code "596") (name "Net-(D547-COM)") (class "Default")
      (node (ref "D547") (pin "3") (pinfunction "COM_3") (pintype "bidirectional"))
      (node (ref "L547") (pin "1") (pinfunction "1_1") (pintype "passive"))
    )
    (net (code "597") (name "Net-(D548-COM)") (class "Default")
      (node (ref "D548") (pin "3") (pinfunction "COM_3") (pintype "bidirectional"))
      (node (ref "L548") (pin "1") (pinfunction "1_1") (pintype "passive"))
    )
    (net (code "598") (name "Net-(D549-COM)") (class "Default")
      (node (ref "D549") (pin "3") (pinfunction "COM_3") (pintype "bidirectional"))
      (node (ref "L549") (pin "1") (pinfunction "1_1") (pintype "passive"))
    )
    (net (code "599") (name "Net-(D550-COM)") (class "Default")
      (node (ref "D550") (pin "3") (pinfunction "COM_3") (pintype "bidirectional"))
      (node (ref "L550") (pin "1") (pinfunction "1_1") (pintype "passive"))
    )
    (net (code "600") (name "Net-(D551-COM)") (class "Default")
      (node (ref "D551") (pin "3") (pinfunction "COM_3") (pintype "bidirectional"))
      (node (ref "L551") (pin "1") (pinfunction "1_1") (pintype "passive"))
    )
    (net (code "601") (name "Net-(D552-COM)") (class "Default")
      (node (ref "D552") (pin "3") (pinfunction "COM_3") (pintype "bidirectional"))
      (node (ref "L552") (pin "1") (pinfunction "1_1") (pintype "passive"))
    )
    (net (code "602") (name "Net-(D553-COM)") (class "Default")
      (node (ref "D553") (pin "3") (pinfunction "COM_3") (pintype "bidirectional"))
      (node (ref "L553") (pin "1") (pinfunction "1_1") (pintype "passive"))
    )
    (net (code "603") (name "Net-(D554-COM)") (class "Default")
      (node (ref "D554") (pin "3") (pinfunction "COM_3") (pintype "bidirectional"))
      (node (ref "L554") (pin "1") (pinfunction "1_1") (pintype "passive"))
    )
    (net (code "604") (name "Net-(D555-COM)") (class "Default")
      (node (ref "D555") (pin "3") (pinfunction "COM_3") (pintype "bidirectional"))
      (node (ref "L555") (pin "1") (pinfunction "1_1") (pintype "passive"))
    )
    (net (code "605") (name "Net-(D556-COM)") (class "Default")
      (node (ref "D556") (pin "3") (pinfunction "COM_3") (pintype "bidirectional"))
      (node (ref "L556") (pin "1") (pinfunction "1_1") (pintype "passive"))
    )
    (net (code "606") (name "Net-(D557-COM)") (class "Default")
      (node (ref "D557") (pin "3") (pinfunction "COM_3") (pintype "bidirectional"))
      (node (ref "L557") (pin "1") (pinfunction "1_1") (pintype "passive"))
    )
    (net (code "607") (name "Net-(D558-COM)") (class "Default")
      (node (ref "D558") (pin "3") (pinfunction "COM_3") (pintype "bidirectional"))
      (node (ref "L558") (pin "1") (pinfunction "1_1") (pintype "passive"))
    )
    (net (code "608") (name "Net-(D559-COM)") (class "Default")
      (node (ref "D559") (pin "3") (pinfunction "COM_3") (pintype "bidirectional"))
      (node (ref "L559") (pin "1") (pinfunction "1_1") (pintype "passive"))
    )
    (net (code "609") (name "Net-(D560-COM)") (class "Default")
      (node (ref "D560") (pin "3") (pinfunction "COM_3") (pintype "bidirectional"))
      (node (ref "L560") (pin "1") (pinfunction "1_1") (pintype "passive"))
    )
    (net (code "610") (name "Net-(D561-COM)") (class "Default")
      (node (ref "D561") (pin "3") (pinfunction "COM_3") (pintype "bidirectional"))
      (node (ref "L561") (pin "1") (pinfunction "1_1") (pintype "passive"))
    )
    (net (code "611") (name "Net-(D562-COM)") (class "Default")
      (node (ref "D562") (pin "3") (pinfunction "COM_3") (pintype "bidirectional"))
      (node (ref "L562") (pin "1") (pinfunction "1_1") (pintype "passive"))
    )
    (net (code "612") (name "Net-(D563-COM)") (class "Default")
      (node (ref "D563") (pin "3") (pinfunction "COM_3") (pintype "bidirectional"))
      (node (ref "L563") (pin "1") (pinfunction "1_1") (pintype "passive"))
    )
    (net (code "613") (name "Net-(D564-COM)") (class "Default")
      (node (ref "D564") (pin "3") (pinfunction "COM_3") (pintype "bidirectional"))
      (node (ref "L564") (pin "1") (pinfunction "1_1") (pintype "passive"))
    )
    (net (code "614") (name "Net-(D565-COM)") (class "Default")
      (node (ref "D565") (pin "3") (pinfunction "COM_3") (pintype "bidirectional"))
      (node (ref "L565") (pin "1") (pinfunction "1_1") (pintype "passive"))
    )
    (net (code "615") (name "Net-(D566-COM)") (class "Default")
      (node (ref "D566") (pin "3") (pinfunction "COM_3") (pintype "bidirectional"))
      (node (ref "L566") (pin "1") (pinfunction "1_1") (pintype "passive"))
    )
    (net (code "616") (name "Net-(D567-COM)") (class "Default")
      (node (ref "D567") (pin "3") (pinfunction "COM_3") (pintype "bidirectional"))
      (node (ref "L567") (pin "1") (pinfunction "1_1") (pintype "passive"))
    )
    (net (code "617") (name "Net-(D568-COM)") (class "Default")
      (node (ref "D568") (pin "3") (pinfunction "COM_3") (pintype "bidirectional"))
      (node (ref "L568") (pin "1") (pinfunction "1_1") (pintype "passive"))
    )
    (net (code "618") (name "Net-(D569-COM)") (class "Default")
      (node (ref "D569") (pin "3") (pinfunction "COM_3") (pintype "bidirectional"))
      (node (ref "L569") (pin "1") (pinfunction "1_1") (pintype "passive"))
    )
    (net (code "619") (name "Net-(D570-COM)") (class "Default")
      (node (ref "D570") (pin "3") (pinfunction "COM_3") (pintype "bidirectional"))
      (node (ref "L570") (pin "1") (pinfunction "1_1") (pintype "passive"))
    )
    (net (code "620") (name "Net-(D571-COM)") (class "Default")
      (node (ref "D571") (pin "3") (pinfunction "COM_3") (pintype "bidirectional"))
      (node (ref "L571") (pin "1") (pinfunction "1_1") (pintype "passive"))
    )
    (net (code "621") (name "Net-(D572-COM)") (class "Default")
      (node (ref "D572") (pin "3") (pinfunction "COM_3") (pintype "bidirectional"))
      (node (ref "L572") (pin "1") (pinfunction "1_1") (pintype "passive"))
    )
    (net (code "622") (name "Net-(D573-COM)") (class "Default")
      (node (ref "D573") (pin "3") (pinfunction "COM_3") (pintype "bidirectional"))
      (node (ref "L573") (pin "1") (pinfunction "1_1") (pintype "passive"))
    )
    (net (code "623") (name "Net-(D574-COM)") (class "Default")
      (node (ref "D574") (pin "3") (pinfunction "COM_3") (pintype "bidirectional"))
      (node (ref "L574") (pin "1") (pinfunction "1_1") (pintype "passive"))
    )
    (net (code "624") (name "Net-(D575-COM)") (class "Default")
      (node (ref "D575") (pin "3") (pinfunction "COM_3") (pintype "bidirectional"))
      (node (ref "L575") (pin "1") (pinfunction "1_1") (pintype "passive"))
    )
    (net (code "625") (name "Net-(D576-COM)") (class "Default")
      (node (ref "D576") (pin "3") (pinfunction "COM_3") (pintype "bidirectional"))
      (node (ref "L576") (pin "1") (pinfunction "1_1") (pintype "passive"))
    )
    (net (code "626") (name "Net-(D577-COM)") (class "Default")
      (node (ref "D577") (pin "3") (pinfunction "COM_3") (pintype "bidirectional"))
      (node (ref "L577") (pin "1") (pinfunction "1_1") (pintype "passive"))
    )
    (net (code "627") (name "Net-(D578-COM)") (class "Default")
      (node (ref "D578") (pin "3") (pinfunction "COM_3") (pintype "bidirectional"))
      (node (ref "L578") (pin "1") (pinfunction "1_1") (pintype "passive"))
    )
    (net (code "628") (name "Net-(D579-COM)") (class "Default")
      (node (ref "D579") (pin "3") (pinfunction "COM_3") (pintype "bidirectional"))
      (node (ref "L579") (pin "1") (pinfunction "1_1") (pintype "passive"))
    )
    (net (code "629") (name "Net-(D580-COM)") (class "Default")
      (node (ref "D580") (pin "3") (pinfunction "COM_3") (pintype "bidirectional"))
      (node (ref "L580") (pin "1") (pinfunction "1_1") (pintype "passive"))
    )
    (net (code "630") (name "Net-(D581-COM)") (class "Default")
      (node (ref "D581") (pin "3") (pinfunction "COM_3") (pintype "bidirectional"))
      (node (ref "L581") (pin "1") (pinfunction "1_1") (pintype "passive"))
    )
    (net (code "631") (name "Net-(D582-COM)") (class "Default")
      (node (ref "D582") (pin "3") (pinfunction "COM_3") (pintype "bidirectional"))
      (node (ref "L582") (pin "1") (pinfunction "1_1") (pintype "passive"))
    )
    (net (code "632") (name "Net-(D583-COM)") (class "Default")
      (node (ref "D583") (pin "3") (pinfunction "COM_3") (pintype "bidirectional"))
      (node (ref "L583") (pin "1") (pinfunction "1_1") (pintype "passive"))
    )
    (net (code "633") (name "Net-(D584-COM)") (class "Default")
      (node (ref "D584") (pin "3") (pinfunction "COM_3") (pintype "bidirectional"))
      (node (ref "L584") (pin "1") (pinfunction "1_1") (pintype "passive"))
    )
    (net (code "634") (name "Net-(D585-COM)") (class "Default")
      (node (ref "D585") (pin "3") (pinfunction "COM_3") (pintype "bidirectional"))
      (node (ref "L585") (pin "1") (pinfunction "1_1") (pintype "passive"))
    )
    (net (code "635") (name "Net-(D586-COM)") (class "Default")
      (node (ref "D586") (pin "3") (pinfunction "COM_3") (pintype "bidirectional"))
      (node (ref "L586") (pin "1") (pinfunction "1_1") (pintype "passive"))
    )
    (net (code "636") (name "Net-(D587-COM)") (class "Default")
      (node (ref "D587") (pin "3") (pinfunction "COM_3") (pintype "bidirectional"))
      (node (ref "L587") (pin "1") (pinfunction "1_1") (pintype "passive"))
    )
    (net (code "637") (name "Net-(D588-COM)") (class "Default")
      (node (ref "D588") (pin "3") (pinfunction "COM_3") (pintype "bidirectional"))
      (node (ref "L588") (pin "1") (pinfunction "1_1") (pintype "passive"))
    )
    (net (code "638") (name "Net-(D589-COM)") (class "Default")
      (node (ref "D589") (pin "3") (pinfunction "COM_3") (pintype "bidirectional"))
      (node (ref "L589") (pin "1") (pinfunction "1_1") (pintype "passive"))
    )
    (net (code "639") (name "Net-(D590-COM)") (class "Default")
      (node (ref "D590") (pin "3") (pinfunction "COM_3") (pintype "bidirectional"))
      (node (ref "L590") (pin "1") (pinfunction "1_1") (pintype "passive"))
    )
    (net (code "640") (name "Net-(D591-COM)") (class "Default")
      (node (ref "D591") (pin "3") (pinfunction "COM_3") (pintype "bidirectional"))
      (node (ref "L591") (pin "1") (pinfunction "1_1") (pintype "passive"))
    )
    (net (code "641") (name "Net-(D592-COM)") (class "Default")
      (node (ref "D592") (pin "3") (pinfunction "COM_3") (pintype "bidirectional"))
      (node (ref "L592") (pin "1") (pinfunction "1_1") (pintype "passive"))
    )
    (net (code "642") (name "Net-(D593-COM)") (class "Default")
      (node (ref "D593") (pin "3") (pinfunction "COM_3") (pintype "bidirectional"))
      (node (ref "L593") (pin "1") (pinfunction "1_1") (pintype "passive"))
    )
    (net (code "643") (name "Net-(D594-COM)") (class "Default")
      (node (ref "D594") (pin "3") (pinfunction "COM_3") (pintype "bidirectional"))
      (node (ref "L594") (pin "1") (pinfunction "1_1") (pintype "passive"))
    )
    (net (code "644") (name "Net-(D595-COM)") (class "Default")
      (node (ref "D595") (pin "3") (pinfunction "COM_3") (pintype "bidirectional"))
      (node (ref "L595") (pin "1") (pinfunction "1_1") (pintype "passive"))
    )
    (net (code "645") (name "Net-(D596-COM)") (class "Default")
      (node (ref "D596") (pin "3") (pinfunction "COM_3") (pintype "bidirectional"))
      (node (ref "L596") (pin "1") (pinfunction "1_1") (pintype "passive"))
    )
    (net (code "646") (name "Net-(D597-COM)") (class "Default")
      (node (ref "D597") (pin "3") (pinfunction "COM_3") (pintype "bidirectional"))
      (node (ref "L597") (pin "1") (pinfunction "1_1") (pintype "passive"))
    )
    (net (code "647") (name "Net-(D598-COM)") (class "Default")
      (node (ref "D598") (pin "3") (pinfunction "COM_3") (pintype "bidirectional"))
      (node (ref "L598") (pin "1") (pinfunction "1_1") (pintype "passive"))
    )
    (net (code "648") (name "Net-(D599-COM)") (class "Default")
      (node (ref "D599") (pin "3") (pinfunction "COM_3") (pintype "bidirectional"))
      (node (ref "L599") (pin "1") (pinfunction "1_1") (pintype "passive"))
    )
    (net (code "649") (name "Net-(D600-COM)") (class "Default")
      (node (ref "D600") (pin "3") (pinfunction "COM_3") (pintype "bidirectional"))
      (node (ref "L600") (pin "1") (pinfunction "1_1") (pintype "passive"))
    )
    (net (code "650") (name "Net-(D601-COM)") (class "Default")
      (node (ref "D601") (pin "3") (pinfunction "COM_3") (pintype "bidirectional"))
      (node (ref "L601") (pin "1") (pinfunction "1_1") (pintype "passive"))
    )
    (net (code "651") (name "Net-(D602-COM)") (class "Default")
      (node (ref "D602") (pin "3") (pinfunction "COM_3") (pintype "bidirectional"))
      (node (ref "L602") (pin "1") (pinfunction "1_1") (pintype "passive"))
    )
    (net (code "652") (name "Net-(D603-COM)") (class "Default")
      (node (ref "D603") (pin "3") (pinfunction "COM_3") (pintype "bidirectional"))
      (node (ref "L603") (pin "1") (pinfunction "1_1") (pintype "passive"))
    )
    (net (code "653") (name "Net-(D604-COM)") (class "Default")
      (node (ref "D604") (pin "3") (pinfunction "COM_3") (pintype "bidirectional"))
      (node (ref "L604") (pin "1") (pinfunction "1_1") (pintype "passive"))
    )
    (net (code "654") (name "Net-(D605-COM)") (class "Default")
      (node (ref "D605") (pin "3") (pinfunction "COM_3") (pintype "bidirectional"))
      (node (ref "L605") (pin "1") (pinfunction "1_1") (pintype "passive"))
    )
    (net (code "655") (name "Net-(D606-COM)") (class "Default")
      (node (ref "D606") (pin "3") (pinfunction "COM_3") (pintype "bidirectional"))
      (node (ref "L606") (pin "1") (pinfunction "1_1") (pintype "passive"))
    )
    (net (code "656") (name "Net-(D607-COM)") (class "Default")
      (node (ref "D607") (pin "3") (pinfunction "COM_3") (pintype "bidirectional"))
      (node (ref "L607") (pin "1") (pinfunction "1_1") (pintype "passive"))
    )
    (net (code "657") (name "Net-(D608-COM)") (class "Default")
      (node (ref "D608") (pin "3") (pinfunction "COM_3") (pintype "bidirectional"))
      (node (ref "L608") (pin "1") (pinfunction "1_1") (pintype "passive"))
    )
    (net (code "658") (name "Net-(D609-COM)") (class "Default")
      (node (ref "D609") (pin "3") (pinfunction "COM_3") (pintype "bidirectional"))
      (node (ref "L609") (pin "1") (pinfunction "1_1") (pintype "passive"))
    )
    (net (code "659") (name "Net-(D610-COM)") (class "Default")
      (node (ref "D610") (pin "3") (pinfunction "COM_3") (pintype "bidirectional"))
      (node (ref "L610") (pin "1") (pinfunction "1_1") (pintype "passive"))
    )
    (net (code "660") (name "Net-(D611-COM)") (class "Default")
      (node (ref "D611") (pin "3") (pinfunction "COM_3") (pintype "bidirectional"))
      (node (ref "L611") (pin "1") (pinfunction "1_1") (pintype "passive"))
    )
    (net (code "661") (name "Net-(D612-COM)") (class "Default")
      (node (ref "D612") (pin "3") (pinfunction "COM_3") (pintype "bidirectional"))
      (node (ref "L612") (pin "1") (pinfunction "1_1") (pintype "passive"))
    )
    (net (code "662") (name "Net-(D613-COM)") (class "Default")
      (node (ref "D613") (pin "3") (pinfunction "COM_3") (pintype "bidirectional"))
      (node (ref "L613") (pin "1") (pinfunction "1_1") (pintype "passive"))
    )
    (net (code "663") (name "Net-(D614-COM)") (class "Default")
      (node (ref "D614") (pin "3") (pinfunction "COM_3") (pintype "bidirectional"))
      (node (ref "L614") (pin "1") (pinfunction "1_1") (pintype "passive"))
    )
    (net (code "664") (name "Net-(D615-COM)") (class "Default")
      (node (ref "D615") (pin "3") (pinfunction "COM_3") (pintype "bidirectional"))
      (node (ref "L615") (pin "1") (pinfunction "1_1") (pintype "passive"))
    )
    (net (code "665") (name "Net-(D616-COM)") (class "Default")
      (node (ref "D616") (pin "3") (pinfunction "COM_3") (pintype "bidirectional"))
      (node (ref "L616") (pin "1") (pinfunction "1_1") (pintype "passive"))
    )
    (net (code "666") (name "Net-(D617-COM)") (class "Default")
      (node (ref "D617") (pin "3") (pinfunction "COM_3") (pintype "bidirectional"))
      (node (ref "L617") (pin "1") (pinfunction "1_1") (pintype "passive"))
    )
    (net (code "667") (name "Net-(D618-COM)") (class "Default")
      (node (ref "D618") (pin "3") (pinfunction "COM_3") (pintype "bidirectional"))
      (node (ref "L618") (pin "1") (pinfunction "1_1") (pintype "passive"))
    )
    (net (code "668") (name "Net-(D619-COM)") (class "Default")
      (node (ref "D619") (pin "3") (pinfunction "COM_3") (pintype "bidirectional"))
      (node (ref "L619") (pin "1") (pinfunction "1_1") (pintype "passive"))
    )
    (net (code "669") (name "Net-(D620-COM)") (class "Default")
      (node (ref "D620") (pin "3") (pinfunction "COM_3") (pintype "bidirectional"))
      (node (ref "L620") (pin "1") (pinfunction "1_1") (pintype "passive"))
    )
    (net (code "670") (name "Net-(D621-COM)") (class "Default")
      (node (ref "D621") (pin "3") (pinfunction "COM_3") (pintype "bidirectional"))
      (node (ref "L621") (pin "1") (pinfunction "1_1") (pintype "passive"))
    )
    (net (code "671") (name "Net-(D622-COM)") (class "Default")
      (node (ref "D622") (pin "3") (pinfunction "COM_3") (pintype "bidirectional"))
      (node (ref "L622") (pin "1") (pinfunction "1_1") (pintype "passive"))
    )
    (net (code "672") (name "Net-(D623-COM)") (class "Default")
      (node (ref "D623") (pin "3") (pinfunction "COM_3") (pintype "bidirectional"))
      (node (ref "L623") (pin "1") (pinfunction "1_1") (pintype "passive"))
    )
    (net (code "673") (name "Net-(D624-COM)") (class "Default")
      (node (ref "D624") (pin "3") (pinfunction "COM_3") (pintype "bidirectional"))
      (node (ref "L624") (pin "1") (pinfunction "1_1") (pintype "passive"))
    )
    (net (code "674") (name "Net-(D625-COM)") (class "Default")
      (node (ref "D625") (pin "3") (pinfunction "COM_3") (pintype "bidirectional"))
      (node (ref "L625") (pin "1") (pinfunction "1_1") (pintype "passive"))
    )
    (net (code "675") (name "Net-(D626-COM)") (class "Default")
      (node (ref "D626") (pin "3") (pinfunction "COM_3") (pintype "bidirectional"))
      (node (ref "L626") (pin "1") (pinfunction "1_1") (pintype "passive"))
    )
    (net (code "676") (name "Net-(D627-COM)") (class "Default")
      (node (ref "D627") (pin "3") (pinfunction "COM_3") (pintype "bidirectional"))
      (node (ref "L627") (pin "1") (pinfunction "1_1") (pintype "passive"))
    )
    (net (code "677") (name "Net-(D628-COM)") (class "Default")
      (node (ref "D628") (pin "3") (pinfunction "COM_3") (pintype "bidirectional"))
      (node (ref "L628") (pin "1") (pinfunction "1_1") (pintype "passive"))
    )
    (net (code "678") (name "Net-(D629-COM)") (class "Default")
      (node (ref "D629") (pin "3") (pinfunction "COM_3") (pintype "bidirectional"))
      (node (ref "L629") (pin "1") (pinfunction "1_1") (pintype "passive"))
    )
    (net (code "679") (name "Net-(D630-COM)") (class "Default")
      (node (ref "D630") (pin "3") (pinfunction "COM_3") (pintype "bidirectional"))
      (node (ref "L630") (pin "1") (pinfunction "1_1") (pintype "passive"))
    )
    (net (code "680") (name "Net-(D631-COM)") (class "Default")
      (node (ref "D631") (pin "3") (pinfunction "COM_3") (pintype "bidirectional"))
      (node (ref "L631") (pin "1") (pinfunction "1_1") (pintype "passive"))
    )
    (net (code "681") (name "Net-(D632-COM)") (class "Default")
      (node (ref "D632") (pin "3") (pinfunction "COM_3") (pintype "bidirectional"))
      (node (ref "L632") (pin "1") (pinfunction "1_1") (pintype "passive"))
    )
    (net (code "682") (name "Net-(D633-COM)") (class "Default")
      (node (ref "D633") (pin "3") (pinfunction "COM_3") (pintype "bidirectional"))
      (node (ref "L633") (pin "1") (pinfunction "1_1") (pintype "passive"))
    )
    (net (code "683") (name "Net-(D634-COM)") (class "Default")
      (node (ref "D634") (pin "3") (pinfunction "COM_3") (pintype "bidirectional"))
      (node (ref "L634") (pin "1") (pinfunction "1_1") (pintype "passive"))
    )
    (net (code "684") (name "Net-(D635-COM)") (class "Default")
      (node (ref "D635") (pin "3") (pinfunction "COM_3") (pintype "bidirectional"))
      (node (ref "L635") (pin "1") (pinfunction "1_1") (pintype "passive"))
    )
    (net (code "685") (name "Net-(D636-COM)") (class "Default")
      (node (ref "D636") (pin "3") (pinfunction "COM_3") (pintype "bidirectional"))
      (node (ref "L636") (pin "1") (pinfunction "1_1") (pintype "passive"))
    )
    (net (code "686") (name "Net-(D637-COM)") (class "Default")
      (node (ref "D637") (pin "3") (pinfunction "COM_3") (pintype "bidirectional"))
      (node (ref "L637") (pin "1") (pinfunction "1_1") (pintype "passive"))
    )
    (net (code "687") (name "Net-(D638-COM)") (class "Default")
      (node (ref "D638") (pin "3") (pinfunction "COM_3") (pintype "bidirectional"))
      (node (ref "L638") (pin "1") (pinfunction "1_1") (pintype "passive"))
    )
    (net (code "688") (name "Net-(D639-COM)") (class "Default")
      (node (ref "D639") (pin "3") (pinfunction "COM_3") (pintype "bidirectional"))
      (node (ref "L639") (pin "1") (pinfunction "1_1") (pintype "passive"))
    )
    (net (code "689") (name "Net-(D640-COM)") (class "Default")
      (node (ref "D640") (pin "3") (pinfunction "COM_3") (pintype "bidirectional"))
      (node (ref "L640") (pin "1") (pinfunction "1_1") (pintype "passive"))
    )
    (net (code "690") (name "Net-(D641-COM)") (class "Default")
      (node (ref "D641") (pin "3") (pinfunction "COM_3") (pintype "bidirectional"))
      (node (ref "L641") (pin "1") (pinfunction "1_1") (pintype "passive"))
    )
    (net (code "691") (name "Net-(D642-COM)") (class "Default")
      (node (ref "D642") (pin "3") (pinfunction "COM_3") (pintype "bidirectional"))
      (node (ref "L642") (pin "1") (pinfunction "1_1") (pintype "passive"))
    )
    (net (code "692") (name "Net-(D643-COM)") (class "Default")
      (node (ref "D643") (pin "3") (pinfunction "COM_3") (pintype "bidirectional"))
      (node (ref "L643") (pin "1") (pinfunction "1_1") (pintype "passive"))
    )
    (net (code "693") (name "Net-(D644-COM)") (class "Default")
      (node (ref "D644") (pin "3") (pinfunction "COM_3") (pintype "bidirectional"))
      (node (ref "L644") (pin "1") (pinfunction "1_1") (pintype "passive"))
    )
    (net (code "694") (name "Net-(D645-COM)") (class "Default")
      (node (ref "D645") (pin "3") (pinfunction "COM_3") (pintype "bidirectional"))
      (node (ref "L645") (pin "1") (pinfunction "1_1") (pintype "passive"))
    )
    (net (code "695") (name "Net-(D646-COM)") (class "Default")
      (node (ref "D646") (pin "3") (pinfunction "COM_3") (pintype "bidirectional"))
      (node (ref "L646") (pin "1") (pinfunction "1_1") (pintype "passive"))
    )
    (net (code "696") (name "Net-(D647-COM)") (class "Default")
      (node (ref "D647") (pin "3") (pinfunction "COM_3") (pintype "bidirectional"))
      (node (ref "L647") (pin "1") (pinfunction "1_1") (pintype "passive"))
    )
    (net (code "697") (name "Net-(D648-COM)") (class "Default")
      (node (ref "D648") (pin "3") (pinfunction "COM_3") (pintype "bidirectional"))
      (node (ref "L648") (pin "1") (pinfunction "1_1") (pintype "passive"))
    )
    (net (code "698") (name "Net-(D649-COM)") (class "Default")
      (node (ref "D649") (pin "3") (pinfunction "COM_3") (pintype "bidirectional"))
      (node (ref "L649") (pin "1") (pinfunction "1_1") (pintype "passive"))
    )
    (net (code "699") (name "Net-(D650-COM)") (class "Default")
      (node (ref "D650") (pin "3") (pinfunction "COM_3") (pintype "bidirectional"))
      (node (ref "L650") (pin "1") (pinfunction "1_1") (pintype "passive"))
    )
    (net (code "700") (name "Net-(D651-COM)") (class "Default")
      (node (ref "D651") (pin "3") (pinfunction "COM_3") (pintype "bidirectional"))
      (node (ref "L651") (pin "1") (pinfunction "1_1") (pintype "passive"))
    )
    (net (code "701") (name "Net-(D652-COM)") (class "Default")
      (node (ref "D652") (pin "3") (pinfunction "COM_3") (pintype "bidirectional"))
      (node (ref "L652") (pin "1") (pinfunction "1_1") (pintype "passive"))
    )
    (net (code "702") (name "Net-(D653-COM)") (class "Default")
      (node (ref "D653") (pin "3") (pinfunction "COM_3") (pintype "bidirectional"))
      (node (ref "L653") (pin "1") (pinfunction "1_1") (pintype "passive"))
    )
    (net (code "703") (name "Net-(D654-COM)") (class "Default")
      (node (ref "D654") (pin "3") (pinfunction "COM_3") (pintype "bidirectional"))
      (node (ref "L654") (pin "1") (pinfunction "1_1") (pintype "passive"))
    )
    (net (code "704") (name "Net-(D655-COM)") (class "Default")
      (node (ref "D655") (pin "3") (pinfunction "COM_3") (pintype "bidirectional"))
      (node (ref "L655") (pin "1") (pinfunction "1_1") (pintype "passive"))
    )
    (net (code "705") (name "Net-(D656-COM)") (class "Default")
      (node (ref "D656") (pin "3") (pinfunction "COM_3") (pintype "bidirectional"))
      (node (ref "L656") (pin "1") (pinfunction "1_1") (pintype "passive"))
    )
    (net (code "706") (name "Net-(D657-COM)") (class "Default")
      (node (ref "D657") (pin "3") (pinfunction "COM_3") (pintype "bidirectional"))
      (node (ref "L657") (pin "1") (pinfunction "1_1") (pintype "passive"))
    )
    (net (code "707") (name "Net-(D658-COM)") (class "Default")
      (node (ref "D658") (pin "3") (pinfunction "COM_3") (pintype "bidirectional"))
      (node (ref "L658") (pin "1") (pinfunction "1_1") (pintype "passive"))
    )
    (net (code "708") (name "Net-(D659-COM)") (class "Default")
      (node (ref "D659") (pin "3") (pinfunction "COM_3") (pintype "bidirectional"))
      (node (ref "L659") (pin "1") (pinfunction "1_1") (pintype "passive"))
    )
    (net (code "709") (name "Net-(D660-COM)") (class "Default")
      (node (ref "D660") (pin "3") (pinfunction "COM_3") (pintype "bidirectional"))
      (node (ref "L660") (pin "1") (pinfunction "1_1") (pintype "passive"))
    )
    (net (code "710") (name "Net-(D661-COM)") (class "Default")
      (node (ref "D661") (pin "3") (pinfunction "COM_3") (pintype "bidirectional"))
      (node (ref "L661") (pin "1") (pinfunction "1_1") (pintype "passive"))
    )
    (net (code "711") (name "Net-(D662-COM)") (class "Default")
      (node (ref "D662") (pin "3") (pinfunction "COM_3") (pintype "bidirectional"))
      (node (ref "L662") (pin "1") (pinfunction "1_1") (pintype "passive"))
    )
    (net (code "712") (name "Net-(D663-COM)") (class "Default")
      (node (ref "D663") (pin "3") (pinfunction "COM_3") (pintype "bidirectional"))
      (node (ref "L663") (pin "1") (pinfunction "1_1") (pintype "passive"))
    )
    (net (code "713") (name "Net-(D664-COM)") (class "Default")
      (node (ref "D664") (pin "3") (pinfunction "COM_3") (pintype "bidirectional"))
      (node (ref "L664") (pin "1") (pinfunction "1_1") (pintype "passive"))
    )
    (net (code "714") (name "Net-(D665-COM)") (class "Default")
      (node (ref "D665") (pin "3") (pinfunction "COM_3") (pintype "bidirectional"))
      (node (ref "L665") (pin "1") (pinfunction "1_1") (pintype "passive"))
    )
    (net (code "715") (name "Net-(D666-COM)") (class "Default")
      (node (ref "D666") (pin "3") (pinfunction "COM_3") (pintype "bidirectional"))
      (node (ref "L666") (pin "1") (pinfunction "1_1") (pintype "passive"))
    )
    (net (code "716") (name "Net-(D667-COM)") (class "Default")
      (node (ref "D667") (pin "3") (pinfunction "COM_3") (pintype "bidirectional"))
      (node (ref "L667") (pin "1") (pinfunction "1_1") (pintype "passive"))
    )
    (net (code "717") (name "Net-(D668-COM)") (class "Default")
      (node (ref "D668") (pin "3") (pinfunction "COM_3") (pintype "bidirectional"))
      (node (ref "L668") (pin "1") (pinfunction "1_1") (pintype "passive"))
    )
    (net (code "718") (name "Net-(D669-COM)") (class "Default")
      (node (ref "D669") (pin "3") (pinfunction "COM_3") (pintype "bidirectional"))
      (node (ref "L669") (pin "1") (pinfunction "1_1") (pintype "passive"))
    )
    (net (code "719") (name "Net-(D670-COM)") (class "Default")
      (node (ref "D670") (pin "3") (pinfunction "COM_3") (pintype "bidirectional"))
      (node (ref "L670") (pin "1") (pinfunction "1_1") (pintype "passive"))
    )
    (net (code "720") (name "Net-(D671-COM)") (class "Default")
      (node (ref "D671") (pin "3") (pinfunction "COM_3") (pintype "bidirectional"))
      (node (ref "L671") (pin "1") (pinfunction "1_1") (pintype "passive"))
    )
    (net (code "721") (name "Net-(D672-COM)") (class "Default")
      (node (ref "D672") (pin "3") (pinfunction "COM_3") (pintype "bidirectional"))
      (node (ref "L672") (pin "1") (pinfunction "1_1") (pintype "passive"))
    )
    (net (code "722") (name "Net-(D673-COM)") (class "Default")
      (node (ref "D673") (pin "3") (pinfunction "COM_3") (pintype "bidirectional"))
      (node (ref "L673") (pin "1") (pinfunction "1_1") (pintype "passive"))
    )
    (net (code "723") (name "Net-(D674-COM)") (class "Default")
      (node (ref "D674") (pin "3") (pinfunction "COM_3") (pintype "bidirectional"))
      (node (ref "L674") (pin "1") (pinfunction "1_1") (pintype "passive"))
    )
    (net (code "724") (name "Net-(D675-COM)") (class "Default")
      (node (ref "D675") (pin "3") (pinfunction "COM_3") (pintype "bidirectional"))
      (node (ref "L675") (pin "1") (pinfunction "1_1") (pintype "passive"))
    )
    (net (code "725") (name "Net-(D676-COM)") (class "Default")
      (node (ref "D676") (pin "3") (pinfunction "COM_3") (pintype "bidirectional"))
      (node (ref "L676") (pin "1") (pinfunction "1_1") (pintype "passive"))
    )
    (net (code "726") (name "Net-(D677-COM)") (class "Default")
      (node (ref "D677") (pin "3") (pinfunction "COM_3") (pintype "bidirectional"))
      (node (ref "L677") (pin "1") (pinfunction "1_1") (pintype "passive"))
    )
    (net (code "727") (name "Net-(D678-COM)") (class "Default")
      (node (ref "D678") (pin "3") (pinfunction "COM_3") (pintype "bidirectional"))
      (node (ref "L678") (pin "1") (pinfunction "1_1") (pintype "passive"))
    )
    (net (code "728") (name "Net-(D679-COM)") (class "Default")
      (node (ref "D679") (pin "3") (pinfunction "COM_3") (pintype "bidirectional"))
      (node (ref "L679") (pin "1") (pinfunction "1_1") (pintype "passive"))
    )
    (net (code "729") (name "Net-(D680-COM)") (class "Default")
      (node (ref "D680") (pin "3") (pinfunction "COM_3") (pintype "bidirectional"))
      (node (ref "L680") (pin "1") (pinfunction "1_1") (pintype "passive"))
    )
    (net (code "730") (name "Net-(D681-COM)") (class "Default")
      (node (ref "D681") (pin "3") (pinfunction "COM_3") (pintype "bidirectional"))
      (node (ref "L681") (pin "1") (pinfunction "1_1") (pintype "passive"))
    )
    (net (code "731") (name "Net-(D682-COM)") (class "Default")
      (node (ref "D682") (pin "3") (pinfunction "COM_3") (pintype "bidirectional"))
      (node (ref "L682") (pin "1") (pinfunction "1_1") (pintype "passive"))
    )
    (net (code "732") (name "Net-(D683-COM)") (class "Default")
      (node (ref "D683") (pin "3") (pinfunction "COM_3") (pintype "bidirectional"))
      (node (ref "L683") (pin "1") (pinfunction "1_1") (pintype "passive"))
    )
    (net (code "733") (name "Net-(D684-COM)") (class "Default")
      (node (ref "D684") (pin "3") (pinfunction "COM_3") (pintype "bidirectional"))
      (node (ref "L684") (pin "1") (pinfunction "1_1") (pintype "passive"))
    )
    (net (code "734") (name "Net-(D685-COM)") (class "Default")
      (node (ref "D685") (pin "3") (pinfunction "COM_3") (pintype "bidirectional"))
      (node (ref "L685") (pin "1") (pinfunction "1_1") (pintype "passive"))
    )
    (net (code "735") (name "Net-(D686-COM)") (class "Default")
      (node (ref "D686") (pin "3") (pinfunction "COM_3") (pintype "bidirectional"))
      (node (ref "L686") (pin "1") (pinfunction "1_1") (pintype "passive"))
    )
    (net (code "736") (name "Net-(D687-COM)") (class "Default")
      (node (ref "D687") (pin "3") (pinfunction "COM_3") (pintype "bidirectional"))
      (node (ref "L687") (pin "1") (pinfunction "1_1") (pintype "passive"))
    )
    (net (code "737") (name "Net-(D688-COM)") (class "Default")
      (node (ref "D688") (pin "3") (pinfunction "COM_3") (pintype "bidirectional"))
      (node (ref "L688") (pin "1") (pinfunction "1_1") (pintype "passive"))
    )
    (net (code "738") (name "Net-(D689-COM)") (class "Default")
      (node (ref "D689") (pin "3") (pinfunction "COM_3") (pintype "bidirectional"))
      (node (ref "L689") (pin "1") (pinfunction "1_1") (pintype "passive"))
    )
    (net (code "739") (name "Net-(D690-COM)") (class "Default")
      (node (ref "D690") (pin "3") (pinfunction "COM_3") (pintype "bidirectional"))
      (node (ref "L690") (pin "1") (pinfunction "1_1") (pintype "passive"))
    )
    (net (code "740") (name "Net-(D691-COM)") (class "Default")
      (node (ref "D691") (pin "3") (pinfunction "COM_3") (pintype "bidirectional"))
      (node (ref "L691") (pin "1") (pinfunction "1_1") (pintype "passive"))
    )
    (net (code "741") (name "Net-(D692-COM)") (class "Default")
      (node (ref "D692") (pin "3") (pinfunction "COM_3") (pintype "bidirectional"))
      (node (ref "L692") (pin "1") (pinfunction "1_1") (pintype "passive"))
    )
    (net (code "742") (name "Net-(D693-COM)") (class "Default")
      (node (ref "D693") (pin "3") (pinfunction "COM_3") (pintype "bidirectional"))
      (node (ref "L693") (pin "1") (pinfunction "1_1") (pintype "passive"))
    )
    (net (code "743") (name "Net-(D694-COM)") (class "Default")
      (node (ref "D694") (pin "3") (pinfunction "COM_3") (pintype "bidirectional"))
      (node (ref "L694") (pin "1") (pinfunction "1_1") (pintype "passive"))
    )
    (net (code "744") (name "Net-(D695-COM)") (class "Default")
      (node (ref "D695") (pin "3") (pinfunction "COM_3") (pintype "bidirectional"))
      (node (ref "L695") (pin "1") (pinfunction "1_1") (pintype "passive"))
    )
    (net (code "745") (name "Net-(D696-COM)") (class "Default")
      (node (ref "D696") (pin "3") (pinfunction "COM_3") (pintype "bidirectional"))
      (node (ref "L696") (pin "1") (pinfunction "1_1") (pintype "passive"))
    )
    (net (code "746") (name "Net-(D697-COM)") (class "Default")
      (node (ref "D697") (pin "3") (pinfunction "COM_3") (pintype "bidirectional"))
      (node (ref "L697") (pin "1") (pinfunction "1_1") (pintype "passive"))
    )
    (net (code "747") (name "Net-(D698-COM)") (class "Default")
      (node (ref "D698") (pin "3") (pinfunction "COM_3") (pintype "bidirectional"))
      (node (ref "L698") (pin "1") (pinfunction "1_1") (pintype "passive"))
    )
    (net (code "748") (name "Net-(D699-COM)") (class "Default")
      (node (ref "D699") (pin "3") (pinfunction "COM_3") (pintype "bidirectional"))
      (node (ref "L699") (pin "1") (pinfunction "1_1") (pintype "passive"))
    )
    (net (code "749") (name "Net-(D700-COM)") (class "Default")
      (node (ref "D700") (pin "3") (pinfunction "COM_3") (pintype "bidirectional"))
      (node (ref "L700") (pin "1") (pinfunction "1_1") (pintype "passive"))
    )
    (net (code "750") (name "Net-(D701-COM)") (class "Default")
      (node (ref "D701") (pin "3") (pinfunction "COM_3") (pintype "bidirectional"))
      (node (ref "L701") (pin "1") (pinfunction "1_1") (pintype "passive"))
    )
    (net (code "751") (name "Net-(D702-COM)") (class "Default")
      (node (ref "D702") (pin "3") (pinfunction "COM_3") (pintype "bidirectional"))
      (node (ref "L702") (pin "1") (pinfunction "1_1") (pintype "passive"))
    )
    (net (code "752") (name "Net-(D703-COM)") (class "Default")
      (node (ref "D703") (pin "3") (pinfunction "COM_3") (pintype "bidirectional"))
      (node (ref "L703") (pin "1") (pinfunction "1_1") (pintype "passive"))
    )
    (net (code "753") (name "Net-(D704-COM)") (class "Default")
      (node (ref "D704") (pin "3") (pinfunction "COM_3") (pintype "bidirectional"))
      (node (ref "L704") (pin "1") (pinfunction "1_1") (pintype "passive"))
    )
    (net (code "754") (name "Net-(D705-COM)") (class "Default")
      (node (ref "D705") (pin "3") (pinfunction "COM_3") (pintype "bidirectional"))
      (node (ref "L705") (pin "1") (pinfunction "1_1") (pintype "passive"))
    )
    (net (code "755") (name "Net-(D706-COM)") (class "Default")
      (node (ref "D706") (pin "3") (pinfunction "COM_3") (pintype "bidirectional"))
      (node (ref "L706") (pin "1") (pinfunction "1_1") (pintype "passive"))
    )
    (net (code "756") (name "Net-(D707-COM)") (class "Default")
      (node (ref "D707") (pin "3") (pinfunction "COM_3") (pintype "bidirectional"))
      (node (ref "L707") (pin "1") (pinfunction "1_1") (pintype "passive"))
    )
    (net (code "757") (name "Net-(D708-COM)") (class "Default")
      (node (ref "D708") (pin "3") (pinfunction "COM_3") (pintype "bidirectional"))
      (node (ref "L708") (pin "1") (pinfunction "1_1") (pintype "passive"))
    )
    (net (code "758") (name "Net-(D709-COM)") (class "Default")
      (node (ref "D709") (pin "3") (pinfunction "COM_3") (pintype "bidirectional"))
      (node (ref "L709") (pin "1") (pinfunction "1_1") (pintype "passive"))
    )
    (net (code "759") (name "Net-(D710-COM)") (class "Default")
      (node (ref "D710") (pin "3") (pinfunction "COM_3") (pintype "bidirectional"))
      (node (ref "L710") (pin "1") (pinfunction "1_1") (pintype "passive"))
    )
    (net (code "760") (name "Net-(D711-COM)") (class "Default")
      (node (ref "D711") (pin "3") (pinfunction "COM_3") (pintype "bidirectional"))
      (node (ref "L711") (pin "1") (pinfunction "1_1") (pintype "passive"))
    )
    (net (code "761") (name "Net-(D712-COM)") (class "Default")
      (node (ref "D712") (pin "3") (pinfunction "COM_3") (pintype "bidirectional"))
      (node (ref "L712") (pin "1") (pinfunction "1_1") (pintype "passive"))
    )
    (net (code "762") (name "Net-(D713-COM)") (class "Default")
      (node (ref "D713") (pin "3") (pinfunction "COM_3") (pintype "bidirectional"))
      (node (ref "L713") (pin "1") (pinfunction "1_1") (pintype "passive"))
    )
    (net (code "763") (name "Net-(D714-COM)") (class "Default")
      (node (ref "D714") (pin "3") (pinfunction "COM_3") (pintype "bidirectional"))
      (node (ref "L714") (pin "1") (pinfunction "1_1") (pintype "passive"))
    )
    (net (code "764") (name "Net-(D715-COM)") (class "Default")
      (node (ref "D715") (pin "3") (pinfunction "COM_3") (pintype "bidirectional"))
      (node (ref "L715") (pin "1") (pinfunction "1_1") (pintype "passive"))
    )
    (net (code "765") (name "Net-(D716-COM)") (class "Default")
      (node (ref "D716") (pin "3") (pinfunction "COM_3") (pintype "bidirectional"))
      (node (ref "L716") (pin "1") (pinfunction "1_1") (pintype "passive"))
    )
    (net (code "766") (name "Net-(D717-COM)") (class "Default")
      (node (ref "D717") (pin "3") (pinfunction "COM_3") (pintype "bidirectional"))
      (node (ref "L717") (pin "1") (pinfunction "1_1") (pintype "passive"))
    )
    (net (code "767") (name "Net-(D718-COM)") (class "Default")
      (node (ref "D718") (pin "3") (pinfunction "COM_3") (pintype "bidirectional"))
      (node (ref "L718") (pin "1") (pinfunction "1_1") (pintype "passive"))
    )
    (net (code "768") (name "Net-(D719-COM)") (class "Default")
      (node (ref "D719") (pin "3") (pinfunction "COM_3") (pintype "bidirectional"))
      (node (ref "L719") (pin "1") (pinfunction "1_1") (pintype "passive"))
    )
    (net (code "769") (name "Net-(D720-COM)") (class "Default")
      (node (ref "D720") (pin "3") (pinfunction "COM_3") (pintype "bidirectional"))
      (node (ref "L720") (pin "1") (pinfunction "1_1") (pintype "passive"))
    )
    (net (code "770") (name "Net-(D721-COM)") (class "Default")
      (node (ref "D721") (pin "3") (pinfunction "COM_3") (pintype "bidirectional"))
      (node (ref "L721") (pin "1") (pinfunction "1_1") (pintype "passive"))
    )
    (net (code "771") (name "Net-(D722-COM)") (class "Default")
      (node (ref "D722") (pin "3") (pinfunction "COM_3") (pintype "bidirectional"))
      (node (ref "L722") (pin "1") (pinfunction "1_1") (pintype "passive"))
    )
    (net (code "772") (name "Net-(D723-COM)") (class "Default")
      (node (ref "D723") (pin "3") (pinfunction "COM_3") (pintype "bidirectional"))
      (node (ref "L723") (pin "1") (pinfunction "1_1") (pintype "passive"))
    )
    (net (code "773") (name "Net-(D724-COM)") (class "Default")
      (node (ref "D724") (pin "3") (pinfunction "COM_3") (pintype "bidirectional"))
      (node (ref "L724") (pin "1") (pinfunction "1_1") (pintype "passive"))
    )
    (net (code "774") (name "Net-(D725-COM)") (class "Default")
      (node (ref "D725") (pin "3") (pinfunction "COM_3") (pintype "bidirectional"))
      (node (ref "L725") (pin "1") (pinfunction "1_1") (pintype "passive"))
    )
    (net (code "775") (name "Net-(D726-COM)") (class "Default")
      (node (ref "D726") (pin "3") (pinfunction "COM_3") (pintype "bidirectional"))
      (node (ref "L726") (pin "1") (pinfunction "1_1") (pintype "passive"))
    )
    (net (code "776") (name "Net-(D727-COM)") (class "Default")
      (node (ref "D727") (pin "3") (pinfunction "COM_3") (pintype "bidirectional"))
      (node (ref "L727") (pin "1") (pinfunction "1_1") (pintype "passive"))
    )
    (net (code "777") (name "Net-(D728-COM)") (class "Default")
      (node (ref "D728") (pin "3") (pinfunction "COM_3") (pintype "bidirectional"))
      (node (ref "L728") (pin "1") (pinfunction "1_1") (pintype "passive"))
    )
    (net (code "778") (name "Net-(D729-COM)") (class "Default")
      (node (ref "D729") (pin "3") (pinfunction "COM_3") (pintype "bidirectional"))
      (node (ref "L729") (pin "1") (pinfunction "1_1") (pintype "passive"))
    )
    (net (code "779") (name "Net-(D730-COM)") (class "Default")
      (node (ref "D730") (pin "3") (pinfunction "COM_3") (pintype "bidirectional"))
      (node (ref "L730") (pin "1") (pinfunction "1_1") (pintype "passive"))
    )
    (net (code "780") (name "Net-(D731-COM)") (class "Default")
      (node (ref "D731") (pin "3") (pinfunction "COM_3") (pintype "bidirectional"))
      (node (ref "L731") (pin "1") (pinfunction "1_1") (pintype "passive"))
    )
    (net (code "781") (name "Net-(D732-COM)") (class "Default")
      (node (ref "D732") (pin "3") (pinfunction "COM_3") (pintype "bidirectional"))
      (node (ref "L732") (pin "1") (pinfunction "1_1") (pintype "passive"))
    )
    (net (code "782") (name "Net-(D733-COM)") (class "Default")
      (node (ref "D733") (pin "3") (pinfunction "COM_3") (pintype "bidirectional"))
      (node (ref "L733") (pin "1") (pinfunction "1_1") (pintype "passive"))
    )
    (net (code "783") (name "Net-(D734-COM)") (class "Default")
      (node (ref "D734") (pin "3") (pinfunction "COM_3") (pintype "bidirectional"))
      (node (ref "L734") (pin "1") (pinfunction "1_1") (pintype "passive"))
    )
    (net (code "784") (name "Net-(D735-COM)") (class "Default")
      (node (ref "D735") (pin "3") (pinfunction "COM_3") (pintype "bidirectional"))
      (node (ref "L735") (pin "1") (pinfunction "1_1") (pintype "passive"))
    )
    (net (code "785") (name "Net-(D736-COM)") (class "Default")
      (node (ref "D736") (pin "3") (pinfunction "COM_3") (pintype "bidirectional"))
      (node (ref "L736") (pin "1") (pinfunction "1_1") (pintype "passive"))
    )
    (net (code "786") (name "Net-(D737-COM)") (class "Default")
      (node (ref "D737") (pin "3") (pinfunction "COM_3") (pintype "bidirectional"))
      (node (ref "L737") (pin "1") (pinfunction "1_1") (pintype "passive"))
    )
    (net (code "787") (name "Net-(D738-COM)") (class "Default")
      (node (ref "D738") (pin "3") (pinfunction "COM_3") (pintype "bidirectional"))
      (node (ref "L738") (pin "1") (pinfunction "1_1") (pintype "passive"))
    )
    (net (code "788") (name "Net-(D739-COM)") (class "Default")
      (node (ref "D739") (pin "3") (pinfunction "COM_3") (pintype "bidirectional"))
      (node (ref "L739") (pin "1") (pinfunction "1_1") (pintype "passive"))
    )
    (net (code "789") (name "Net-(D740-COM)") (class "Default")
      (node (ref "D740") (pin "3") (pinfunction "COM_3") (pintype "bidirectional"))
      (node (ref "L740") (pin "1") (pinfunction "1_1") (pintype "passive"))
    )
    (net (code "790") (name "Net-(D741-COM)") (class "Default")
      (node (ref "D741") (pin "3") (pinfunction "COM_3") (pintype "bidirectional"))
      (node (ref "L741") (pin "1") (pinfunction "1_1") (pintype "passive"))
    )
    (net (code "791") (name "Net-(D742-COM)") (class "Default")
      (node (ref "D742") (pin "3") (pinfunction "COM_3") (pintype "bidirectional"))
      (node (ref "L742") (pin "1") (pinfunction "1_1") (pintype "passive"))
    )
    (net (code "792") (name "Net-(D743-COM)") (class "Default")
      (node (ref "D743") (pin "3") (pinfunction "COM_3") (pintype "bidirectional"))
      (node (ref "L743") (pin "1") (pinfunction "1_1") (pintype "passive"))
    )
    (net (code "793") (name "Net-(D744-COM)") (class "Default")
      (node (ref "D744") (pin "3") (pinfunction "COM_3") (pintype "bidirectional"))
      (node (ref "L744") (pin "1") (pinfunction "1_1") (pintype "passive"))
    )
    (net (code "794") (name "Net-(D745-COM)") (class "Default")
      (node (ref "D745") (pin "3") (pinfunction "COM_3") (pintype "bidirectional"))
      (node (ref "L745") (pin "1") (pinfunction "1_1") (pintype "passive"))
    )
    (net (code "795") (name "Net-(D746-COM)") (class "Default")
      (node (ref "D746") (pin "3") (pinfunction "COM_3") (pintype "bidirectional"))
      (node (ref "L746") (pin "1") (pinfunction "1_1") (pintype "passive"))
    )
    (net (code "796") (name "Net-(D747-COM)") (class "Default")
      (node (ref "D747") (pin "3") (pinfunction "COM_3") (pintype "bidirectional"))
      (node (ref "L747") (pin "1") (pinfunction "1_1") (pintype "passive"))
    )
    (net (code "797") (name "Net-(D748-COM)") (class "Default")
      (node (ref "D748") (pin "3") (pinfunction "COM_3") (pintype "bidirectional"))
      (node (ref "L748") (pin "1") (pinfunction "1_1") (pintype "passive"))
    )
    (net (code "798") (name "Net-(D749-COM)") (class "Default")
      (node (ref "D749") (pin "3") (pinfunction "COM_3") (pintype "bidirectional"))
      (node (ref "L749") (pin "1") (pinfunction "1_1") (pintype "passive"))
    )
    (net (code "799") (name "Net-(D750-COM)") (class "Default")
      (node (ref "D750") (pin "3") (pinfunction "COM_3") (pintype "bidirectional"))
      (node (ref "L750") (pin "1") (pinfunction "1_1") (pintype "passive"))
    )
    (net (code "800") (name "Net-(D751-COM)") (class "Default")
      (node (ref "D751") (pin "3") (pinfunction "COM_3") (pintype "bidirectional"))
      (node (ref "L751") (pin "1") (pinfunction "1_1") (pintype "passive"))
    )
    (net (code "801") (name "Net-(D752-COM)") (class "Default")
      (node (ref "D752") (pin "3") (pinfunction "COM_3") (pintype "bidirectional"))
      (node (ref "L752") (pin "1") (pinfunction "1_1") (pintype "passive"))
    )
    (net (code "802") (name "Net-(D753-COM)") (class "Default")
      (node (ref "D753") (pin "3") (pinfunction "COM_3") (pintype "bidirectional"))
      (node (ref "L753") (pin "1") (pinfunction "1_1") (pintype "passive"))
    )
    (net (code "803") (name "Net-(D754-COM)") (class "Default")
      (node (ref "D754") (pin "3") (pinfunction "COM_3") (pintype "bidirectional"))
      (node (ref "L754") (pin "1") (pinfunction "1_1") (pintype "passive"))
    )
    (net (code "804") (name "Net-(D755-COM)") (class "Default")
      (node (ref "D755") (pin "3") (pinfunction "COM_3") (pintype "bidirectional"))
      (node (ref "L755") (pin "1") (pinfunction "1_1") (pintype "passive"))
    )
    (net (code "805") (name "Net-(D756-COM)") (class "Default")
      (node (ref "D756") (pin "3") (pinfunction "COM_3") (pintype "bidirectional"))
      (node (ref "L756") (pin "1") (pinfunction "1_1") (pintype "passive"))
    )
    (net (code "806") (name "Net-(D757-COM)") (class "Default")
      (node (ref "D757") (pin "3") (pinfunction "COM_3") (pintype "bidirectional"))
      (node (ref "L757") (pin "1") (pinfunction "1_1") (pintype "passive"))
    )
    (net (code "807") (name "Net-(D758-COM)") (class "Default")
      (node (ref "D758") (pin "3") (pinfunction "COM_3") (pintype "bidirectional"))
      (node (ref "L758") (pin "1") (pinfunction "1_1") (pintype "passive"))
    )
    (net (code "808") (name "Net-(D759-COM)") (class "Default")
      (node (ref "D759") (pin "3") (pinfunction "COM_3") (pintype "bidirectional"))
      (node (ref "L759") (pin "1") (pinfunction "1_1") (pintype "passive"))
    )
    (net (code "809") (name "Net-(D760-COM)") (class "Default")
      (node (ref "D760") (pin "3") (pinfunction "COM_3") (pintype "bidirectional"))
      (node (ref "L760") (pin "1") (pinfunction "1_1") (pintype "passive"))
    )
    (net (code "810") (name "Net-(D761-COM)") (class "Default")
      (node (ref "D761") (pin "3") (pinfunction "COM_3") (pintype "bidirectional"))
      (node (ref "L761") (pin "1") (pinfunction "1_1") (pintype "passive"))
    )
    (net (code "811") (name "Net-(D762-COM)") (class "Default")
      (node (ref "D762") (pin "3") (pinfunction "COM_3") (pintype "bidirectional"))
      (node (ref "L762") (pin "1") (pinfunction "1_1") (pintype "passive"))
    )
    (net (code "812") (name "Net-(D763-COM)") (class "Default")
      (node (ref "D763") (pin "3") (pinfunction "COM_3") (pintype "bidirectional"))
      (node (ref "L763") (pin "1") (pinfunction "1_1") (pintype "passive"))
    )
    (net (code "813") (name "Net-(D764-COM)") (class "Default")
      (node (ref "D764") (pin "3") (pinfunction "COM_3") (pintype "bidirectional"))
      (node (ref "L764") (pin "1") (pinfunction "1_1") (pintype "passive"))
    )
    (net (code "814") (name "Net-(D765-COM)") (class "Default")
      (node (ref "D765") (pin "3") (pinfunction "COM_3") (pintype "bidirectional"))
      (node (ref "L765") (pin "1") (pinfunction "1_1") (pintype "passive"))
    )
    (net (code "815") (name "Net-(D766-COM)") (class "Default")
      (node (ref "D766") (pin "3") (pinfunction "COM_3") (pintype "bidirectional"))
      (node (ref "L766") (pin "1") (pinfunction "1_1") (pintype "passive"))
    )
    (net (code "816") (name "Net-(D767-COM)") (class "Default")
      (node (ref "D767") (pin "3") (pinfunction "COM_3") (pintype "bidirectional"))
      (node (ref "L767") (pin "1") (pinfunction "1_1") (pintype "passive"))
    )
    (net (code "817") (name "Net-(D768-COM)") (class "Default")
      (node (ref "D768") (pin "3") (pinfunction "COM_3") (pintype "bidirectional"))
      (node (ref "L768") (pin "1") (pinfunction "1_1") (pintype "passive"))
    )
    (net (code "818") (name "Net-(D769-COM)") (class "Default")
      (node (ref "D769") (pin "3") (pinfunction "COM_3") (pintype "bidirectional"))
      (node (ref "L769") (pin "1") (pinfunction "1_1") (pintype "passive"))
    )
    (net (code "819") (name "Net-(D770-COM)") (class "Default")
      (node (ref "D770") (pin "3") (pinfunction "COM_3") (pintype "bidirectional"))
      (node (ref "L770") (pin "1") (pinfunction "1_1") (pintype "passive"))
    )
    (net (code "820") (name "Net-(D771-COM)") (class "Default")
      (node (ref "D771") (pin "3") (pinfunction "COM_3") (pintype "bidirectional"))
      (node (ref "L771") (pin "1") (pinfunction "1_1") (pintype "passive"))
    )
    (net (code "821") (name "Net-(D772-COM)") (class "Default")
      (node (ref "D772") (pin "3") (pinfunction "COM_3") (pintype "bidirectional"))
      (node (ref "L772") (pin "1") (pinfunction "1_1") (pintype "passive"))
    )
    (net (code "822") (name "Net-(D773-COM)") (class "Default")
      (node (ref "D773") (pin "3") (pinfunction "COM_3") (pintype "bidirectional"))
      (node (ref "L773") (pin "1") (pinfunction "1_1") (pintype "passive"))
    )
    (net (code "823") (name "Net-(D774-COM)") (class "Default")
      (node (ref "D774") (pin "3") (pinfunction "COM_3") (pintype "bidirectional"))
      (node (ref "L774") (pin "1") (pinfunction "1_1") (pintype "passive"))
    )
    (net (code "824") (name "Net-(D775-COM)") (class "Default")
      (node (ref "D775") (pin "3") (pinfunction "COM_3") (pintype "bidirectional"))
      (node (ref "L775") (pin "1") (pinfunction "1_1") (pintype "passive"))
    )
    (net (code "825") (name "Net-(D776-COM)") (class "Default")
      (node (ref "D776") (pin "3") (pinfunction "COM_3") (pintype "bidirectional"))
      (node (ref "L776") (pin "1") (pinfunction "1_1") (pintype "passive"))
    )
    (net (code "826") (name "Net-(D777-COM)") (class "Default")
      (node (ref "D777") (pin "3") (pinfunction "COM_3") (pintype "bidirectional"))
      (node (ref "L777") (pin "1") (pinfunction "1_1") (pintype "passive"))
    )
    (net (code "827") (name "Net-(D778-COM)") (class "Default")
      (node (ref "D778") (pin "3") (pinfunction "COM_3") (pintype "bidirectional"))
      (node (ref "L778") (pin "1") (pinfunction "1_1") (pintype "passive"))
    )
    (net (code "828") (name "Net-(D779-COM)") (class "Default")
      (node (ref "D779") (pin "3") (pinfunction "COM_3") (pintype "bidirectional"))
      (node (ref "L779") (pin "1") (pinfunction "1_1") (pintype "passive"))
    )
    (net (code "829") (name "Net-(D780-COM)") (class "Default")
      (node (ref "D780") (pin "3") (pinfunction "COM_3") (pintype "bidirectional"))
      (node (ref "L780") (pin "1") (pinfunction "1_1") (pintype "passive"))
    )
    (net (code "830") (name "Net-(D781-COM)") (class "Default")
      (node (ref "D781") (pin "3") (pinfunction "COM_3") (pintype "bidirectional"))
      (node (ref "L781") (pin "1") (pinfunction "1_1") (pintype "passive"))
    )
    (net (code "831") (name "Net-(D782-COM)") (class "Default")
      (node (ref "D782") (pin "3") (pinfunction "COM_3") (pintype "bidirectional"))
      (node (ref "L782") (pin "1") (pinfunction "1_1") (pintype "passive"))
    )
    (net (code "832") (name "Net-(D783-COM)") (class "Default")
      (node (ref "D783") (pin "3") (pinfunction "COM_3") (pintype "bidirectional"))
      (node (ref "L783") (pin "1") (pinfunction "1_1") (pintype "passive"))
    )
    (net (code "833") (name "Net-(D784-COM)") (class "Default")
      (node (ref "D784") (pin "3") (pinfunction "COM_3") (pintype "bidirectional"))
      (node (ref "L784") (pin "1") (pinfunction "1_1") (pintype "passive"))
    )
    (net (code "834") (name "Net-(D785-COM)") (class "Default")
      (node (ref "D785") (pin "3") (pinfunction "COM_3") (pintype "bidirectional"))
      (node (ref "L785") (pin "1") (pinfunction "1_1") (pintype "passive"))
    )
    (net (code "835") (name "Net-(D786-COM)") (class "Default")
      (node (ref "D786") (pin "3") (pinfunction "COM_3") (pintype "bidirectional"))
      (node (ref "L786") (pin "1") (pinfunction "1_1") (pintype "passive"))
    )
    (net (code "836") (name "Net-(D787-COM)") (class "Default")
      (node (ref "D787") (pin "3") (pinfunction "COM_3") (pintype "bidirectional"))
      (node (ref "L787") (pin "1") (pinfunction "1_1") (pintype "passive"))
    )
    (net (code "837") (name "Net-(D788-COM)") (class "Default")
      (node (ref "D788") (pin "3") (pinfunction "COM_3") (pintype "bidirectional"))
      (node (ref "L788") (pin "1") (pinfunction "1_1") (pintype "passive"))
    )
    (net (code "838") (name "Net-(D789-COM)") (class "Default")
      (node (ref "D789") (pin "3") (pinfunction "COM_3") (pintype "bidirectional"))
      (node (ref "L789") (pin "1") (pinfunction "1_1") (pintype "passive"))
    )
    (net (code "839") (name "Net-(D790-COM)") (class "Default")
      (node (ref "D790") (pin "3") (pinfunction "COM_3") (pintype "bidirectional"))
      (node (ref "L790") (pin "1") (pinfunction "1_1") (pintype "passive"))
    )
    (net (code "840") (name "Net-(D791-COM)") (class "Default")
      (node (ref "D791") (pin "3") (pinfunction "COM_3") (pintype "bidirectional"))
      (node (ref "L791") (pin "1") (pinfunction "1_1") (pintype "passive"))
    )
    (net (code "841") (name "Net-(D792-COM)") (class "Default")
      (node (ref "D792") (pin "3") (pinfunction "COM_3") (pintype "bidirectional"))
      (node (ref "L792") (pin "1") (pinfunction "1_1") (pintype "passive"))
    )
    (net (code "842") (name "Net-(D793-COM)") (class "Default")
      (node (ref "D793") (pin "3") (pinfunction "COM_3") (pintype "bidirectional"))
      (node (ref "L793") (pin "1") (pinfunction "1_1") (pintype "passive"))
    )
    (net (code "843") (name "Net-(D794-COM)") (class "Default")
      (node (ref "D794") (pin "3") (pinfunction "COM_3") (pintype "bidirectional"))
      (node (ref "L794") (pin "1") (pinfunction "1_1") (pintype "passive"))
    )
    (net (code "844") (name "Net-(D795-COM)") (class "Default")
      (node (ref "D795") (pin "3") (pinfunction "COM_3") (pintype "bidirectional"))
      (node (ref "L795") (pin "1") (pinfunction "1_1") (pintype "passive"))
    )
    (net (code "845") (name "Net-(D796-COM)") (class "Default")
      (node (ref "D796") (pin "3") (pinfunction "COM_3") (pintype "bidirectional"))
      (node (ref "L796") (pin "1") (pinfunction "1_1") (pintype "passive"))
    )
    (net (code "846") (name "Net-(D797-COM)") (class "Default")
      (node (ref "D797") (pin "3") (pinfunction "COM_3") (pintype "bidirectional"))
      (node (ref "L797") (pin "1") (pinfunction "1_1") (pintype "passive"))
    )
    (net (code "847") (name "Net-(D798-COM)") (class "Default")
      (node (ref "D798") (pin "3") (pinfunction "COM_3") (pintype "bidirectional"))
      (node (ref "L798") (pin "1") (pinfunction "1_1") (pintype "passive"))
    )
    (net (code "848") (name "Net-(D799-COM)") (class "Default")
      (node (ref "D799") (pin "3") (pinfunction "COM_3") (pintype "bidirectional"))
      (node (ref "L799") (pin "1") (pinfunction "1_1") (pintype "passive"))
    )
    (net (code "849") (name "Net-(D800-COM)") (class "Default")
      (node (ref "D800") (pin "3") (pinfunction "COM_3") (pintype "bidirectional"))
      (node (ref "L800") (pin "1") (pinfunction "1_1") (pintype "passive"))
    )
    (net (code "850") (name "Net-(D801-COM)") (class "Default")
      (node (ref "D801") (pin "3") (pinfunction "COM_3") (pintype "bidirectional"))
      (node (ref "L801") (pin "1") (pinfunction "1_1") (pintype "passive"))
    )
    (net (code "851") (name "Net-(D802-COM)") (class "Default")
      (node (ref "D802") (pin "3") (pinfunction "COM_3") (pintype "bidirectional"))
      (node (ref "L802") (pin "1") (pinfunction "1_1") (pintype "passive"))
    )
    (net (code "852") (name "Net-(D803-COM)") (class "Default")
      (node (ref "D803") (pin "3") (pinfunction "COM_3") (pintype "bidirectional"))
      (node (ref "L803") (pin "1") (pinfunction "1_1") (pintype "passive"))
    )
    (net (code "853") (name "Net-(D804-COM)") (class "Default")
      (node (ref "D804") (pin "3") (pinfunction "COM_3") (pintype "bidirectional"))
      (node (ref "L804") (pin "1") (pinfunction "1_1") (pintype "passive"))
    )
    (net (code "854") (name "Net-(D805-COM)") (class "Default")
      (node (ref "D805") (pin "3") (pinfunction "COM_3") (pintype "bidirectional"))
      (node (ref "L805") (pin "1") (pinfunction "1_1") (pintype "passive"))
    )
    (net (code "855") (name "Net-(D806-COM)") (class "Default")
      (node (ref "D806") (pin "3") (pinfunction "COM_3") (pintype "bidirectional"))
      (node (ref "L806") (pin "1") (pinfunction "1_1") (pintype "passive"))
    )
    (net (code "856") (name "Net-(D807-COM)") (class "Default")
      (node (ref "D807") (pin "3") (pinfunction "COM_3") (pintype "bidirectional"))
      (node (ref "L807") (pin "1") (pinfunction "1_1") (pintype "passive"))
    )
    (net (code "857") (name "Net-(D808-COM)") (class "Default")
      (node (ref "D808") (pin "3") (pinfunction "COM_3") (pintype "bidirectional"))
      (node (ref "L808") (pin "1") (pinfunction "1_1") (pintype "passive"))
    )
    (net (code "858") (name "Net-(D809-COM)") (class "Default")
      (node (ref "D809") (pin "3") (pinfunction "COM_3") (pintype "bidirectional"))
      (node (ref "L809") (pin "1") (pinfunction "1_1") (pintype "passive"))
    )
    (net (code "859") (name "Net-(D810-COM)") (class "Default")
      (node (ref "D810") (pin "3") (pinfunction "COM_3") (pintype "bidirectional"))
      (node (ref "L810") (pin "1") (pinfunction "1_1") (pintype "passive"))
    )
    (net (code "860") (name "Net-(D811-COM)") (class "Default")
      (node (ref "D811") (pin "3") (pinfunction "COM_3") (pintype "bidirectional"))
      (node (ref "L811") (pin "1") (pinfunction "1_1") (pintype "passive"))
    )
    (net (code "861") (name "Net-(D812-COM)") (class "Default")
      (node (ref "D812") (pin "3") (pinfunction "COM_3") (pintype "bidirectional"))
      (node (ref "L812") (pin "1") (pinfunction "1_1") (pintype "passive"))
    )
    (net (code "862") (name "Net-(D813-COM)") (class "Default")
      (node (ref "D813") (pin "3") (pinfunction "COM_3") (pintype "bidirectional"))
      (node (ref "L813") (pin "1") (pinfunction "1_1") (pintype "passive"))
    )
    (net (code "863") (name "Net-(D814-COM)") (class "Default")
      (node (ref "D814") (pin "3") (pinfunction "COM_3") (pintype "bidirectional"))
      (node (ref "L814") (pin "1") (pinfunction "1_1") (pintype "passive"))
    )
    (net (code "864") (name "Net-(D815-COM)") (class "Default")
      (node (ref "D815") (pin "3") (pinfunction "COM_3") (pintype "bidirectional"))
      (node (ref "L815") (pin "1") (pinfunction "1_1") (pintype "passive"))
    )
    (net (code "865") (name "Net-(D816-COM)") (class "Default")
      (node (ref "D816") (pin "3") (pinfunction "COM_3") (pintype "bidirectional"))
      (node (ref "L816") (pin "1") (pinfunction "1_1") (pintype "passive"))
    )
    (net (code "866") (name "Net-(D817-COM)") (class "Default")
      (node (ref "D817") (pin "3") (pinfunction "COM_3") (pintype "bidirectional"))
      (node (ref "L817") (pin "1") (pinfunction "1_1") (pintype "passive"))
    )
    (net (code "867") (name "Net-(D818-COM)") (class "Default")
      (node (ref "D818") (pin "3") (pinfunction "COM_3") (pintype "bidirectional"))
      (node (ref "L818") (pin "1") (pinfunction "1_1") (pintype "passive"))
    )
    (net (code "868") (name "Net-(D819-COM)") (class "Default")
      (node (ref "D819") (pin "3") (pinfunction "COM_3") (pintype "bidirectional"))
      (node (ref "L819") (pin "1") (pinfunction "1_1") (pintype "passive"))
    )
    (net (code "869") (name "Net-(D820-COM)") (class "Default")
      (node (ref "D820") (pin "3") (pinfunction "COM_3") (pintype "bidirectional"))
      (node (ref "L820") (pin "1") (pinfunction "1_1") (pintype "passive"))
    )
    (net (code "870") (name "Net-(D821-COM)") (class "Default")
      (node (ref "D821") (pin "3") (pinfunction "COM_3") (pintype "bidirectional"))
      (node (ref "L821") (pin "1") (pinfunction "1_1") (pintype "passive"))
    )
    (net (code "871") (name "Net-(D822-COM)") (class "Default")
      (node (ref "D822") (pin "3") (pinfunction "COM_3") (pintype "bidirectional"))
      (node (ref "L822") (pin "1") (pinfunction "1_1") (pintype "passive"))
    )
    (net (code "872") (name "Net-(D823-COM)") (class "Default")
      (node (ref "D823") (pin "3") (pinfunction "COM_3") (pintype "bidirectional"))
      (node (ref "L823") (pin "1") (pinfunction "1_1") (pintype "passive"))
    )
    (net (code "873") (name "Net-(D824-COM)") (class "Default")
      (node (ref "D824") (pin "3") (pinfunction "COM_3") (pintype "bidirectional"))
      (node (ref "L824") (pin "1") (pinfunction "1_1") (pintype "passive"))
    )
    (net (code "874") (name "Net-(D825-COM)") (class "Default")
      (node (ref "D825") (pin "3") (pinfunction "COM_3") (pintype "bidirectional"))
      (node (ref "L825") (pin "1") (pinfunction "1_1") (pintype "passive"))
    )
    (net (code "875") (name "Net-(D826-COM)") (class "Default")
      (node (ref "D826") (pin "3") (pinfunction "COM_3") (pintype "bidirectional"))
      (node (ref "L826") (pin "1") (pinfunction "1_1") (pintype "passive"))
    )
    (net (code "876") (name "Net-(D827-COM)") (class "Default")
      (node (ref "D827") (pin "3") (pinfunction "COM_3") (pintype "bidirectional"))
      (node (ref "L827") (pin "1") (pinfunction "1_1") (pintype "passive"))
    )
    (net (code "877") (name "Net-(D828-COM)") (class "Default")
      (node (ref "D828") (pin "3") (pinfunction "COM_3") (pintype "bidirectional"))
      (node (ref "L828") (pin "1") (pinfunction "1_1") (pintype "passive"))
    )
    (net (code "878") (name "Net-(D829-COM)") (class "Default")
      (node (ref "D829") (pin "3") (pinfunction "COM_3") (pintype "bidirectional"))
      (node (ref "L829") (pin "1") (pinfunction "1_1") (pintype "passive"))
    )
    (net (code "879") (name "Net-(D830-COM)") (class "Default")
      (node (ref "D830") (pin "3") (pinfunction "COM_3") (pintype "bidirectional"))
      (node (ref "L830") (pin "1") (pinfunction "1_1") (pintype "passive"))
    )
    (net (code "880") (name "Net-(D831-COM)") (class "Default")
      (node (ref "D831") (pin "3") (pinfunction "COM_3") (pintype "bidirectional"))
      (node (ref "L831") (pin "1") (pinfunction "1_1") (pintype "passive"))
    )
    (net (code "881") (name "Net-(D832-COM)") (class "Default")
      (node (ref "D832") (pin "3") (pinfunction "COM_3") (pintype "bidirectional"))
      (node (ref "L832") (pin "1") (pinfunction "1_1") (pintype "passive"))
    )
    (net (code "882") (name "Net-(D833-COM)") (class "Default")
      (node (ref "D833") (pin "3") (pinfunction "COM_3") (pintype "bidirectional"))
      (node (ref "L833") (pin "1") (pinfunction "1_1") (pintype "passive"))
    )
    (net (code "883") (name "Net-(D834-COM)") (class "Default")
      (node (ref "D834") (pin "3") (pinfunction "COM_3") (pintype "bidirectional"))
      (node (ref "L834") (pin "1") (pinfunction "1_1") (pintype "passive"))
    )
    (net (code "884") (name "Net-(D835-COM)") (class "Default")
      (node (ref "D835") (pin "3") (pinfunction "COM_3") (pintype "bidirectional"))
      (node (ref "L835") (pin "1") (pinfunction "1_1") (pintype "passive"))
    )
    (net (code "885") (name "Net-(D836-COM)") (class "Default")
      (node (ref "D836") (pin "3") (pinfunction "COM_3") (pintype "bidirectional"))
      (node (ref "L836") (pin "1") (pinfunction "1_1") (pintype "passive"))
    )
    (net (code "886") (name "Net-(D837-COM)") (class "Default")
      (node (ref "D837") (pin "3") (pinfunction "COM_3") (pintype "bidirectional"))
      (node (ref "L837") (pin "1") (pinfunction "1_1") (pintype "passive"))
    )
    (net (code "887") (name "Net-(D838-COM)") (class "Default")
      (node (ref "D838") (pin "3") (pinfunction "COM_3") (pintype "bidirectional"))
      (node (ref "L838") (pin "1") (pinfunction "1_1") (pintype "passive"))
    )
    (net (code "888") (name "Net-(D839-COM)") (class "Default")
      (node (ref "D839") (pin "3") (pinfunction "COM_3") (pintype "bidirectional"))
      (node (ref "L839") (pin "1") (pinfunction "1_1") (pintype "passive"))
    )
    (net (code "889") (name "Net-(D840-COM)") (class "Default")
      (node (ref "D840") (pin "3") (pinfunction "COM_3") (pintype "bidirectional"))
      (node (ref "L840") (pin "1") (pinfunction "1_1") (pintype "passive"))
    )
    (net (code "890") (name "Net-(D841-COM)") (class "Default")
      (node (ref "D841") (pin "3") (pinfunction "COM_3") (pintype "bidirectional"))
      (node (ref "L841") (pin "1") (pinfunction "1_1") (pintype "passive"))
    )
    (net (code "891") (name "Net-(D842-COM)") (class "Default")
      (node (ref "D842") (pin "3") (pinfunction "COM_3") (pintype "bidirectional"))
      (node (ref "L842") (pin "1") (pinfunction "1_1") (pintype "passive"))
    )
    (net (code "892") (name "Net-(D843-COM)") (class "Default")
      (node (ref "D843") (pin "3") (pinfunction "COM_3") (pintype "bidirectional"))
      (node (ref "L843") (pin "1") (pinfunction "1_1") (pintype "passive"))
    )
    (net (code "893") (name "Net-(D844-COM)") (class "Default")
      (node (ref "D844") (pin "3") (pinfunction "COM_3") (pintype "bidirectional"))
      (node (ref "L844") (pin "1") (pinfunction "1_1") (pintype "passive"))
    )
    (net (code "894") (name "Net-(D845-COM)") (class "Default")
      (node (ref "D845") (pin "3") (pinfunction "COM_3") (pintype "bidirectional"))
      (node (ref "L845") (pin "1") (pinfunction "1_1") (pintype "passive"))
    )
    (net (code "895") (name "Net-(D846-COM)") (class "Default")
      (node (ref "D846") (pin "3") (pinfunction "COM_3") (pintype "bidirectional"))
      (node (ref "L846") (pin "1") (pinfunction "1_1") (pintype "passive"))
    )
    (net (code "896") (name "Net-(D847-COM)") (class "Default")
      (node (ref "D847") (pin "3") (pinfunction "COM_3") (pintype "bidirectional"))
      (node (ref "L847") (pin "1") (pinfunction "1_1") (pintype "passive"))
    )
    (net (code "897") (name "Net-(D848-COM)") (class "Default")
      (node (ref "D848") (pin "3") (pinfunction "COM_3") (pintype "bidirectional"))
      (node (ref "L848") (pin "1") (pinfunction "1_1") (pintype "passive"))
    )
    (net (code "898") (name "Net-(D849-COM)") (class "Default")
      (node (ref "D849") (pin "3") (pinfunction "COM_3") (pintype "bidirectional"))
      (node (ref "L849") (pin "1") (pinfunction "1_1") (pintype "passive"))
    )
    (net (code "899") (name "Net-(D850-COM)") (class "Default")
      (node (ref "D850") (pin "3") (pinfunction "COM_3") (pintype "bidirectional"))
      (node (ref "L850") (pin "1") (pinfunction "1_1") (pintype "passive"))
    )
    (net (code "900") (name "Net-(D851-COM)") (class "Default")
      (node (ref "D851") (pin "3") (pinfunction "COM_3") (pintype "bidirectional"))
      (node (ref "L851") (pin "1") (pinfunction "1_1") (pintype "passive"))
    )
    (net (code "901") (name "Net-(D852-COM)") (class "Default")
      (node (ref "D852") (pin "3") (pinfunction "COM_3") (pintype "bidirectional"))
      (node (ref "L852") (pin "1") (pinfunction "1_1") (pintype "passive"))
    )
    (net (code "902") (name "Net-(D853-COM)") (class "Default")
      (node (ref "D853") (pin "3") (pinfunction "COM_3") (pintype "bidirectional"))
      (node (ref "L853") (pin "1") (pinfunction "1_1") (pintype "passive"))
    )
    (net (code "903") (name "Net-(D854-COM)") (class "Default")
      (node (ref "D854") (pin "3") (pinfunction "COM_3") (pintype "bidirectional"))
      (node (ref "L854") (pin "1") (pinfunction "1_1") (pintype "passive"))
    )
    (net (code "904") (name "Net-(D855-COM)") (class "Default")
      (node (ref "D855") (pin "3") (pinfunction "COM_3") (pintype "bidirectional"))
      (node (ref "L855") (pin "1") (pinfunction "1_1") (pintype "passive"))
    )
    (net (code "905") (name "Net-(D856-COM)") (class "Default")
      (node (ref "D856") (pin "3") (pinfunction "COM_3") (pintype "bidirectional"))
      (node (ref "L856") (pin "1") (pinfunction "1_1") (pintype "passive"))
    )
    (net (code "906") (name "Net-(D857-COM)") (class "Default")
      (node (ref "D857") (pin "3") (pinfunction "COM_3") (pintype "bidirectional"))
      (node (ref "L857") (pin "1") (pinfunction "1_1") (pintype "passive"))
    )
    (net (code "907") (name "Net-(D858-COM)") (class "Default")
      (node (ref "D858") (pin "3") (pinfunction "COM_3") (pintype "bidirectional"))
      (node (ref "L858") (pin "1") (pinfunction "1_1") (pintype "passive"))
    )
    (net (code "908") (name "Net-(D859-COM)") (class "Default")
      (node (ref "D859") (pin "3") (pinfunction "COM_3") (pintype "bidirectional"))
      (node (ref "L859") (pin "1") (pinfunction "1_1") (pintype "passive"))
    )
    (net (code "909") (name "Net-(D860-COM)") (class "Default")
      (node (ref "D860") (pin "3") (pinfunction "COM_3") (pintype "bidirectional"))
      (node (ref "L860") (pin "1") (pinfunction "1_1") (pintype "passive"))
    )
    (net (code "910") (name "Net-(D861-COM)") (class "Default")
      (node (ref "D861") (pin "3") (pinfunction "COM_3") (pintype "bidirectional"))
      (node (ref "L861") (pin "1") (pinfunction "1_1") (pintype "passive"))
    )
    (net (code "911") (name "Net-(D862-COM)") (class "Default")
      (node (ref "D862") (pin "3") (pinfunction "COM_3") (pintype "bidirectional"))
      (node (ref "L862") (pin "1") (pinfunction "1_1") (pintype "passive"))
    )
    (net (code "912") (name "Net-(D863-COM)") (class "Default")
      (node (ref "D863") (pin "3") (pinfunction "COM_3") (pintype "bidirectional"))
      (node (ref "L863") (pin "1") (pinfunction "1_1") (pintype "passive"))
    )
    (net (code "913") (name "Net-(D864-COM)") (class "Default")
      (node (ref "D864") (pin "3") (pinfunction "COM_3") (pintype "bidirectional"))
      (node (ref "L864") (pin "1") (pinfunction "1_1") (pintype "passive"))
    )
    (net (code "914") (name "Net-(D865-COM)") (class "Default")
      (node (ref "D865") (pin "3") (pinfunction "COM_3") (pintype "bidirectional"))
      (node (ref "L865") (pin "1") (pinfunction "1_1") (pintype "passive"))
    )
    (net (code "915") (name "Net-(D866-COM)") (class "Default")
      (node (ref "D866") (pin "3") (pinfunction "COM_3") (pintype "bidirectional"))
      (node (ref "L866") (pin "1") (pinfunction "1_1") (pintype "passive"))
    )
    (net (code "916") (name "Net-(D867-COM)") (class "Default")
      (node (ref "D867") (pin "3") (pinfunction "COM_3") (pintype "bidirectional"))
      (node (ref "L867") (pin "1") (pinfunction "1_1") (pintype "passive"))
    )
    (net (code "917") (name "Net-(D868-COM)") (class "Default")
      (node (ref "D868") (pin "3") (pinfunction "COM_3") (pintype "bidirectional"))
      (node (ref "L868") (pin "1") (pinfunction "1_1") (pintype "passive"))
    )
    (net (code "918") (name "Net-(D869-COM)") (class "Default")
      (node (ref "D869") (pin "3") (pinfunction "COM_3") (pintype "bidirectional"))
      (node (ref "L869") (pin "1") (pinfunction "1_1") (pintype "passive"))
    )
    (net (code "919") (name "Net-(D870-COM)") (class "Default")
      (node (ref "D870") (pin "3") (pinfunction "COM_3") (pintype "bidirectional"))
      (node (ref "L870") (pin "1") (pinfunction "1_1") (pintype "passive"))
    )
    (net (code "920") (name "Net-(D871-COM)") (class "Default")
      (node (ref "D871") (pin "3") (pinfunction "COM_3") (pintype "bidirectional"))
      (node (ref "L871") (pin "1") (pinfunction "1_1") (pintype "passive"))
    )
    (net (code "921") (name "Net-(D872-COM)") (class "Default")
      (node (ref "D872") (pin "3") (pinfunction "COM_3") (pintype "bidirectional"))
      (node (ref "L872") (pin "1") (pinfunction "1_1") (pintype "passive"))
    )
    (net (code "922") (name "Net-(D873-COM)") (class "Default")
      (node (ref "D873") (pin "3") (pinfunction "COM_3") (pintype "bidirectional"))
      (node (ref "L873") (pin "1") (pinfunction "1_1") (pintype "passive"))
    )
    (net (code "923") (name "Net-(D874-COM)") (class "Default")
      (node (ref "D874") (pin "3") (pinfunction "COM_3") (pintype "bidirectional"))
      (node (ref "L874") (pin "1") (pinfunction "1_1") (pintype "passive"))
    )
    (net (code "924") (name "Net-(D875-COM)") (class "Default")
      (node (ref "D875") (pin "3") (pinfunction "COM_3") (pintype "bidirectional"))
      (node (ref "L875") (pin "1") (pinfunction "1_1") (pintype "passive"))
    )
    (net (code "925") (name "Net-(D876-COM)") (class "Default")
      (node (ref "D876") (pin "3") (pinfunction "COM_3") (pintype "bidirectional"))
      (node (ref "L876") (pin "1") (pinfunction "1_1") (pintype "passive"))
    )
    (net (code "926") (name "Net-(D877-COM)") (class "Default")
      (node (ref "D877") (pin "3") (pinfunction "COM_3") (pintype "bidirectional"))
      (node (ref "L877") (pin "1") (pinfunction "1_1") (pintype "passive"))
    )
    (net (code "927") (name "Net-(D878-COM)") (class "Default")
      (node (ref "D878") (pin "3") (pinfunction "COM_3") (pintype "bidirectional"))
      (node (ref "L878") (pin "1") (pinfunction "1_1") (pintype "passive"))
    )
    (net (code "928") (name "Net-(D879-COM)") (class "Default")
      (node (ref "D879") (pin "3") (pinfunction "COM_3") (pintype "bidirectional"))
      (node (ref "L879") (pin "1") (pinfunction "1_1") (pintype "passive"))
    )
    (net (code "929") (name "Net-(D880-COM)") (class "Default")
      (node (ref "D880") (pin "3") (pinfunction "COM_3") (pintype "bidirectional"))
      (node (ref "L880") (pin "1") (pinfunction "1_1") (pintype "passive"))
    )
    (net (code "930") (name "Net-(D881-COM)") (class "Default")
      (node (ref "D881") (pin "3") (pinfunction "COM_3") (pintype "bidirectional"))
      (node (ref "L881") (pin "1") (pinfunction "1_1") (pintype "passive"))
    )
    (net (code "931") (name "Net-(D882-COM)") (class "Default")
      (node (ref "D882") (pin "3") (pinfunction "COM_3") (pintype "bidirectional"))
      (node (ref "L882") (pin "1") (pinfunction "1_1") (pintype "passive"))
    )
    (net (code "932") (name "Net-(D883-COM)") (class "Default")
      (node (ref "D883") (pin "3") (pinfunction "COM_3") (pintype "bidirectional"))
      (node (ref "L883") (pin "1") (pinfunction "1_1") (pintype "passive"))
    )
    (net (code "933") (name "Net-(D884-COM)") (class "Default")
      (node (ref "D884") (pin "3") (pinfunction "COM_3") (pintype "bidirectional"))
      (node (ref "L884") (pin "1") (pinfunction "1_1") (pintype "passive"))
    )
    (net (code "934") (name "Net-(D885-COM)") (class "Default")
      (node (ref "D885") (pin "3") (pinfunction "COM_3") (pintype "bidirectional"))
      (node (ref "L885") (pin "1") (pinfunction "1_1") (pintype "passive"))
    )
    (net (code "935") (name "Net-(D886-COM)") (class "Default")
      (node (ref "D886") (pin "3") (pinfunction "COM_3") (pintype "bidirectional"))
      (node (ref "L886") (pin "1") (pinfunction "1_1") (pintype "passive"))
    )
    (net (code "936") (name "Net-(D887-COM)") (class "Default")
      (node (ref "D887") (pin "3") (pinfunction "COM_3") (pintype "bidirectional"))
      (node (ref "L887") (pin "1") (pinfunction "1_1") (pintype "passive"))
    )
    (net (code "937") (name "Net-(D888-COM)") (class "Default")
      (node (ref "D888") (pin "3") (pinfunction "COM_3") (pintype "bidirectional"))
      (node (ref "L888") (pin "1") (pinfunction "1_1") (pintype "passive"))
    )
    (net (code "938") (name "Net-(D889-COM)") (class "Default")
      (node (ref "D889") (pin "3") (pinfunction "COM_3") (pintype "bidirectional"))
      (node (ref "L889") (pin "1") (pinfunction "1_1") (pintype "passive"))
    )
    (net (code "939") (name "Net-(D890-COM)") (class "Default")
      (node (ref "D890") (pin "3") (pinfunction "COM_3") (pintype "bidirectional"))
      (node (ref "L890") (pin "1") (pinfunction "1_1") (pintype "passive"))
    )
    (net (code "940") (name "Net-(D891-COM)") (class "Default")
      (node (ref "D891") (pin "3") (pinfunction "COM_3") (pintype "bidirectional"))
      (node (ref "L891") (pin "1") (pinfunction "1_1") (pintype "passive"))
    )
    (net (code "941") (name "Net-(D892-COM)") (class "Default")
      (node (ref "D892") (pin "3") (pinfunction "COM_3") (pintype "bidirectional"))
      (node (ref "L892") (pin "1") (pinfunction "1_1") (pintype "passive"))
    )
    (net (code "942") (name "Net-(D893-COM)") (class "Default")
      (node (ref "D893") (pin "3") (pinfunction "COM_3") (pintype "bidirectional"))
      (node (ref "L893") (pin "1") (pinfunction "1_1") (pintype "passive"))
    )
    (net (code "943") (name "Net-(D894-COM)") (class "Default")
      (node (ref "D894") (pin "3") (pinfunction "COM_3") (pintype "bidirectional"))
      (node (ref "L894") (pin "1") (pinfunction "1_1") (pintype "passive"))
    )
    (net (code "944") (name "Net-(D895-COM)") (class "Default")
      (node (ref "D895") (pin "3") (pinfunction "COM_3") (pintype "bidirectional"))
      (node (ref "L895") (pin "1") (pinfunction "1_1") (pintype "passive"))
    )
    (net (code "945") (name "Net-(D896-COM)") (class "Default")
      (node (ref "D896") (pin "3") (pinfunction "COM_3") (pintype "bidirectional"))
      (node (ref "L896") (pin "1") (pinfunction "1_1") (pintype "passive"))
    )
    (net (code "946") (name "Net-(D897-COM)") (class "Default")
      (node (ref "D897") (pin "3") (pinfunction "COM_3") (pintype "bidirectional"))
      (node (ref "L897") (pin "1") (pinfunction "1_1") (pintype "passive"))
    )
    (net (code "947") (name "Net-(D898-COM)") (class "Default")
      (node (ref "D898") (pin "3") (pinfunction "COM_3") (pintype "bidirectional"))
      (node (ref "L898") (pin "1") (pinfunction "1_1") (pintype "passive"))
    )
    (net (code "948") (name "Net-(D899-COM)") (class "Default")
      (node (ref "D899") (pin "3") (pinfunction "COM_3") (pintype "bidirectional"))
      (node (ref "L899") (pin "1") (pinfunction "1_1") (pintype "passive"))
    )
    (net (code "949") (name "Net-(D900-COM)") (class "Default")
      (node (ref "D900") (pin "3") (pinfunction "COM_3") (pintype "bidirectional"))
      (node (ref "L900") (pin "1") (pinfunction "1_1") (pintype "passive"))
    )
    (net (code "950") (name "Net-(D901-COM)") (class "Default")
      (node (ref "D901") (pin "3") (pinfunction "COM_3") (pintype "bidirectional"))
      (node (ref "L901") (pin "1") (pinfunction "1_1") (pintype "passive"))
    )
    (net (code "951") (name "Net-(D902-COM)") (class "Default")
      (node (ref "D902") (pin "3") (pinfunction "COM_3") (pintype "bidirectional"))
      (node (ref "L902") (pin "1") (pinfunction "1_1") (pintype "passive"))
    )
    (net (code "952") (name "Net-(D903-COM)") (class "Default")
      (node (ref "D903") (pin "3") (pinfunction "COM_3") (pintype "bidirectional"))
      (node (ref "L903") (pin "1") (pinfunction "1_1") (pintype "passive"))
    )
    (net (code "953") (name "Net-(D904-COM)") (class "Default")
      (node (ref "D904") (pin "3") (pinfunction "COM_3") (pintype "bidirectional"))
      (node (ref "L904") (pin "1") (pinfunction "1_1") (pintype "passive"))
    )
    (net (code "954") (name "Net-(D905-COM)") (class "Default")
      (node (ref "D905") (pin "3") (pinfunction "COM_3") (pintype "bidirectional"))
      (node (ref "L905") (pin "1") (pinfunction "1_1") (pintype "passive"))
    )
    (net (code "955") (name "Net-(D906-COM)") (class "Default")
      (node (ref "D906") (pin "3") (pinfunction "COM_3") (pintype "bidirectional"))
      (node (ref "L906") (pin "1") (pinfunction "1_1") (pintype "passive"))
    )
    (net (code "956") (name "Net-(D907-COM)") (class "Default")
      (node (ref "D907") (pin "3") (pinfunction "COM_3") (pintype "bidirectional"))
      (node (ref "L907") (pin "1") (pinfunction "1_1") (pintype "passive"))
    )
    (net (code "957") (name "Net-(D908-COM)") (class "Default")
      (node (ref "D908") (pin "3") (pinfunction "COM_3") (pintype "bidirectional"))
      (node (ref "L908") (pin "1") (pinfunction "1_1") (pintype "passive"))
    )
    (net (code "958") (name "Net-(D909-COM)") (class "Default")
      (node (ref "D909") (pin "3") (pinfunction "COM_3") (pintype "bidirectional"))
      (node (ref "L909") (pin "1") (pinfunction "1_1") (pintype "passive"))
    )
    (net (code "959") (name "Net-(D910-COM)") (class "Default")
      (node (ref "D910") (pin "3") (pinfunction "COM_3") (pintype "bidirectional"))
      (node (ref "L910") (pin "1") (pinfunction "1_1") (pintype "passive"))
    )
    (net (code "960") (name "Net-(D911-COM)") (class "Default")
      (node (ref "D911") (pin "3") (pinfunction "COM_3") (pintype "bidirectional"))
      (node (ref "L911") (pin "1") (pinfunction "1_1") (pintype "passive"))
    )
    (net (code "961") (name "Net-(D912-COM)") (class "Default")
      (node (ref "D912") (pin "3") (pinfunction "COM_3") (pintype "bidirectional"))
      (node (ref "L912") (pin "1") (pinfunction "1_1") (pintype "passive"))
    )
    (net (code "962") (name "Net-(D913-COM)") (class "Default")
      (node (ref "D913") (pin "3") (pinfunction "COM_3") (pintype "bidirectional"))
      (node (ref "L913") (pin "1") (pinfunction "1_1") (pintype "passive"))
    )
    (net (code "963") (name "Net-(D914-COM)") (class "Default")
      (node (ref "D914") (pin "3") (pinfunction "COM_3") (pintype "bidirectional"))
      (node (ref "L914") (pin "1") (pinfunction "1_1") (pintype "passive"))
    )
    (net (code "964") (name "Net-(D915-COM)") (class "Default")
      (node (ref "D915") (pin "3") (pinfunction "COM_3") (pintype "bidirectional"))
      (node (ref "L915") (pin "1") (pinfunction "1_1") (pintype "passive"))
    )
    (net (code "965") (name "Net-(D916-COM)") (class "Default")
      (node (ref "D916") (pin "3") (pinfunction "COM_3") (pintype "bidirectional"))
      (node (ref "L916") (pin "1") (pinfunction "1_1") (pintype "passive"))
    )
    (net (code "966") (name "Net-(D917-COM)") (class "Default")
      (node (ref "D917") (pin "3") (pinfunction "COM_3") (pintype "bidirectional"))
      (node (ref "L917") (pin "1") (pinfunction "1_1") (pintype "passive"))
    )
    (net (code "967") (name "Net-(D918-COM)") (class "Default")
      (node (ref "D918") (pin "3") (pinfunction "COM_3") (pintype "bidirectional"))
      (node (ref "L918") (pin "1") (pinfunction "1_1") (pintype "passive"))
    )
    (net (code "968") (name "Net-(D919-COM)") (class "Default")
      (node (ref "D919") (pin "3") (pinfunction "COM_3") (pintype "bidirectional"))
      (node (ref "L919") (pin "1") (pinfunction "1_1") (pintype "passive"))
    )
    (net (code "969") (name "Net-(D920-COM)") (class "Default")
      (node (ref "D920") (pin "3") (pinfunction "COM_3") (pintype "bidirectional"))
      (node (ref "L920") (pin "1") (pinfunction "1_1") (pintype "passive"))
    )
    (net (code "970") (name "Net-(D921-COM)") (class "Default")
      (node (ref "D921") (pin "3") (pinfunction "COM_3") (pintype "bidirectional"))
      (node (ref "L921") (pin "1") (pinfunction "1_1") (pintype "passive"))
    )
    (net (code "971") (name "Net-(D922-COM)") (class "Default")
      (node (ref "D922") (pin "3") (pinfunction "COM_3") (pintype "bidirectional"))
      (node (ref "L922") (pin "1") (pinfunction "1_1") (pintype "passive"))
    )
    (net (code "972") (name "Net-(D923-COM)") (class "Default")
      (node (ref "D923") (pin "3") (pinfunction "COM_3") (pintype "bidirectional"))
      (node (ref "L923") (pin "1") (pinfunction "1_1") (pintype "passive"))
    )
    (net (code "973") (name "Net-(D924-COM)") (class "Default")
      (node (ref "D924") (pin "3") (pinfunction "COM_3") (pintype "bidirectional"))
      (node (ref "L924") (pin "1") (pinfunction "1_1") (pintype "passive"))
    )
    (net (code "974") (name "Net-(D925-COM)") (class "Default")
      (node (ref "D925") (pin "3") (pinfunction "COM_3") (pintype "bidirectional"))
      (node (ref "L925") (pin "1") (pinfunction "1_1") (pintype "passive"))
    )
    (net (code "975") (name "Net-(D926-COM)") (class "Default")
      (node (ref "D926") (pin "3") (pinfunction "COM_3") (pintype "bidirectional"))
      (node (ref "L926") (pin "1") (pinfunction "1_1") (pintype "passive"))
    )
    (net (code "976") (name "Net-(D927-COM)") (class "Default")
      (node (ref "D927") (pin "3") (pinfunction "COM_3") (pintype "bidirectional"))
      (node (ref "L927") (pin "1") (pinfunction "1_1") (pintype "passive"))
    )
    (net (code "977") (name "Net-(D928-COM)") (class "Default")
      (node (ref "D928") (pin "3") (pinfunction "COM_3") (pintype "bidirectional"))
      (node (ref "L928") (pin "1") (pinfunction "1_1") (pintype "passive"))
    )
    (net (code "978") (name "Net-(D929-COM)") (class "Default")
      (node (ref "D929") (pin "3") (pinfunction "COM_3") (pintype "bidirectional"))
      (node (ref "L929") (pin "1") (pinfunction "1_1") (pintype "passive"))
    )
    (net (code "979") (name "Net-(D930-COM)") (class "Default")
      (node (ref "D930") (pin "3") (pinfunction "COM_3") (pintype "bidirectional"))
      (node (ref "L930") (pin "1") (pinfunction "1_1") (pintype "passive"))
    )
    (net (code "980") (name "Net-(D931-COM)") (class "Default")
      (node (ref "D931") (pin "3") (pinfunction "COM_3") (pintype "bidirectional"))
      (node (ref "L931") (pin "1") (pinfunction "1_1") (pintype "passive"))
    )
    (net (code "981") (name "Net-(D932-COM)") (class "Default")
      (node (ref "D932") (pin "3") (pinfunction "COM_3") (pintype "bidirectional"))
      (node (ref "L932") (pin "1") (pinfunction "1_1") (pintype "passive"))
    )
    (net (code "982") (name "Net-(D933-COM)") (class "Default")
      (node (ref "D933") (pin "3") (pinfunction "COM_3") (pintype "bidirectional"))
      (node (ref "L933") (pin "1") (pinfunction "1_1") (pintype "passive"))
    )
    (net (code "983") (name "Net-(D934-COM)") (class "Default")
      (node (ref "D934") (pin "3") (pinfunction "COM_3") (pintype "bidirectional"))
      (node (ref "L934") (pin "1") (pinfunction "1_1") (pintype "passive"))
    )
    (net (code "984") (name "Net-(D935-COM)") (class "Default")
      (node (ref "D935") (pin "3") (pinfunction "COM_3") (pintype "bidirectional"))
      (node (ref "L935") (pin "1") (pinfunction "1_1") (pintype "passive"))
    )
    (net (code "985") (name "Net-(D936-COM)") (class "Default")
      (node (ref "D936") (pin "3") (pinfunction "COM_3") (pintype "bidirectional"))
      (node (ref "L936") (pin "1") (pinfunction "1_1") (pintype "passive"))
    )
    (net (code "986") (name "Net-(D937-COM)") (class "Default")
      (node (ref "D937") (pin "3") (pinfunction "COM_3") (pintype "bidirectional"))
      (node (ref "L937") (pin "1") (pinfunction "1_1") (pintype "passive"))
    )
    (net (code "987") (name "Net-(D938-COM)") (class "Default")
      (node (ref "D938") (pin "3") (pinfunction "COM_3") (pintype "bidirectional"))
      (node (ref "L938") (pin "1") (pinfunction "1_1") (pintype "passive"))
    )
    (net (code "988") (name "Net-(D939-COM)") (class "Default")
      (node (ref "D939") (pin "3") (pinfunction "COM_3") (pintype "bidirectional"))
      (node (ref "L939") (pin "1") (pinfunction "1_1") (pintype "passive"))
    )
    (net (code "989") (name "Net-(D940-COM)") (class "Default")
      (node (ref "D940") (pin "3") (pinfunction "COM_3") (pintype "bidirectional"))
      (node (ref "L940") (pin "1") (pinfunction "1_1") (pintype "passive"))
    )
    (net (code "990") (name "Net-(D941-COM)") (class "Default")
      (node (ref "D941") (pin "3") (pinfunction "COM_3") (pintype "bidirectional"))
      (node (ref "L941") (pin "1") (pinfunction "1_1") (pintype "passive"))
    )
    (net (code "991") (name "Net-(D942-COM)") (class "Default")
      (node (ref "D942") (pin "3") (pinfunction "COM_3") (pintype "bidirectional"))
      (node (ref "L942") (pin "1") (pinfunction "1_1") (pintype "passive"))
    )
    (net (code "992") (name "Net-(D943-COM)") (class "Default")
      (node (ref "D943") (pin "3") (pinfunction "COM_3") (pintype "bidirectional"))
      (node (ref "L943") (pin "1") (pinfunction "1_1") (pintype "passive"))
    )
    (net (code "993") (name "Net-(D944-COM)") (class "Default")
      (node (ref "D944") (pin "3") (pinfunction "COM_3") (pintype "bidirectional"))
      (node (ref "L944") (pin "1") (pinfunction "1_1") (pintype "passive"))
    )
    (net (code "994") (name "Net-(D945-COM)") (class "Default")
      (node (ref "D945") (pin "3") (pinfunction "COM_3") (pintype "bidirectional"))
      (node (ref "L945") (pin "1") (pinfunction "1_1") (pintype "passive"))
    )
    (net (code "995") (name "Net-(D946-COM)") (class "Default")
      (node (ref "D946") (pin "3") (pinfunction "COM_3") (pintype "bidirectional"))
      (node (ref "L946") (pin "1") (pinfunction "1_1") (pintype "passive"))
    )
    (net (code "996") (name "Net-(D947-COM)") (class "Default")
      (node (ref "D947") (pin "3") (pinfunction "COM_3") (pintype "bidirectional"))
      (node (ref "L947") (pin "1") (pinfunction "1_1") (pintype "passive"))
    )
    (net (code "997") (name "Net-(D948-COM)") (class "Default")
      (node (ref "D948") (pin "3") (pinfunction "COM_3") (pintype "bidirectional"))
      (node (ref "L948") (pin "1") (pinfunction "1_1") (pintype "passive"))
    )
    (net (code "998") (name "Net-(D949-COM)") (class "Default")
      (node (ref "D949") (pin "3") (pinfunction "COM_3") (pintype "bidirectional"))
      (node (ref "L949") (pin "1") (pinfunction "1_1") (pintype "passive"))
    )
    (net (code "999") (name "Net-(D950-COM)") (class "Default")
      (node (ref "D950") (pin "3") (pinfunction "COM_3") (pintype "bidirectional"))
      (node (ref "L950") (pin "1") (pinfunction "1_1") (pintype "passive"))
    )
    (net (code "1000") (name "Net-(D951-COM)") (class "Default")
      (node (ref "D951") (pin "3") (pinfunction "COM_3") (pintype "bidirectional"))
      (node (ref "L951") (pin "1") (pinfunction "1_1") (pintype "passive"))
    )
    (net (code "1001") (name "Net-(D952-COM)") (class "Default")
      (node (ref "D952") (pin "3") (pinfunction "COM_3") (pintype "bidirectional"))
      (node (ref "L952") (pin "1") (pinfunction "1_1") (pintype "passive"))
    )
    (net (code "1002") (name "Net-(D953-COM)") (class "Default")
      (node (ref "D953") (pin "3") (pinfunction "COM_3") (pintype "bidirectional"))
      (node (ref "L953") (pin "1") (pinfunction "1_1") (pintype "passive"))
    )
    (net (code "1003") (name "Net-(D954-COM)") (class "Default")
      (node (ref "D954") (pin "3") (pinfunction "COM_3") (pintype "bidirectional"))
      (node (ref "L954") (pin "1") (pinfunction "1_1") (pintype "passive"))
    )
    (net (code "1004") (name "Net-(D955-COM)") (class "Default")
      (node (ref "D955") (pin "3") (pinfunction "COM_3") (pintype "bidirectional"))
      (node (ref "L955") (pin "1") (pinfunction "1_1") (pintype "passive"))
    )
    (net (code "1005") (name "Net-(D956-COM)") (class "Default")
      (node (ref "D956") (pin "3") (pinfunction "COM_3") (pintype "bidirectional"))
      (node (ref "L956") (pin "1") (pinfunction "1_1") (pintype "passive"))
    )
    (net (code "1006") (name "Net-(D957-COM)") (class "Default")
      (node (ref "D957") (pin "3") (pinfunction "COM_3") (pintype "bidirectional"))
      (node (ref "L957") (pin "1") (pinfunction "1_1") (pintype "passive"))
    )
    (net (code "1007") (name "Net-(D958-COM)") (class "Default")
      (node (ref "D958") (pin "3") (pinfunction "COM_3") (pintype "bidirectional"))
      (node (ref "L958") (pin "1") (pinfunction "1_1") (pintype "passive"))
    )
    (net (code "1008") (name "Net-(D959-COM)") (class "Default")
      (node (ref "D959") (pin "3") (pinfunction "COM_3") (pintype "bidirectional"))
      (node (ref "L959") (pin "1") (pinfunction "1_1") (pintype "passive"))
    )
    (net (code "1009") (name "Net-(D960-COM)") (class "Default")
      (node (ref "D960") (pin "3") (pinfunction "COM_3") (pintype "bidirectional"))
      (node (ref "L960") (pin "1") (pinfunction "1_1") (pintype "passive"))
    )
    (net (code "1010") (name "Net-(D961-COM)") (class "Default")
      (node (ref "D961") (pin "3") (pinfunction "COM_3") (pintype "bidirectional"))
      (node (ref "L961") (pin "1") (pinfunction "1_1") (pintype "passive"))
    )
    (net (code "1011") (name "Net-(D962-COM)") (class "Default")
      (node (ref "D962") (pin "3") (pinfunction "COM_3") (pintype "bidirectional"))
      (node (ref "L962") (pin "1") (pinfunction "1_1") (pintype "passive"))
    )
    (net (code "1012") (name "Net-(D963-COM)") (class "Default")
      (node (ref "D963") (pin "3") (pinfunction "COM_3") (pintype "bidirectional"))
      (node (ref "L963") (pin "1") (pinfunction "1_1") (pintype "passive"))
    )
    (net (code "1013") (name "Net-(D964-COM)") (class "Default")
      (node (ref "D964") (pin "3") (pinfunction "COM_3") (pintype "bidirectional"))
      (node (ref "L964") (pin "1") (pinfunction "1_1") (pintype "passive"))
    )
    (net (code "1014") (name "Net-(D965-COM)") (class "Default")
      (node (ref "D965") (pin "3") (pinfunction "COM_3") (pintype "bidirectional"))
      (node (ref "L965") (pin "1") (pinfunction "1_1") (pintype "passive"))
    )
    (net (code "1015") (name "Net-(D966-COM)") (class "Default")
      (node (ref "D966") (pin "3") (pinfunction "COM_3") (pintype "bidirectional"))
      (node (ref "L966") (pin "1") (pinfunction "1_1") (pintype "passive"))
    )
    (net (code "1016") (name "Net-(D967-COM)") (class "Default")
      (node (ref "D967") (pin "3") (pinfunction "COM_3") (pintype "bidirectional"))
      (node (ref "L967") (pin "1") (pinfunction "1_1") (pintype "passive"))
    )
    (net (code "1017") (name "Net-(D968-COM)") (class "Default")
      (node (ref "D968") (pin "3") (pinfunction "COM_3") (pintype "bidirectional"))
      (node (ref "L968") (pin "1") (pinfunction "1_1") (pintype "passive"))
    )
    (net (code "1018") (name "Net-(D969-COM)") (class "Default")
      (node (ref "D969") (pin "3") (pinfunction "COM_3") (pintype "bidirectional"))
      (node (ref "L969") (pin "1") (pinfunction "1_1") (pintype "passive"))
    )
    (net (code "1019") (name "Net-(D970-COM)") (class "Default")
      (node (ref "D970") (pin "3") (pinfunction "COM_3") (pintype "bidirectional"))
      (node (ref "L970") (pin "1") (pinfunction "1_1") (pintype "passive"))
    )
    (net (code "1020") (name "Net-(D971-COM)") (class "Default")
      (node (ref "D971") (pin "3") (pinfunction "COM_3") (pintype "bidirectional"))
      (node (ref "L971") (pin "1") (pinfunction "1_1") (pintype "passive"))
    )
    (net (code "1021") (name "Net-(D972-COM)") (class "Default")
      (node (ref "D972") (pin "3") (pinfunction "COM_3") (pintype "bidirectional"))
      (node (ref "L972") (pin "1") (pinfunction "1_1") (pintype "passive"))
    )
    (net (code "1022") (name "Net-(D973-COM)") (class "Default")
      (node (ref "D973") (pin "3") (pinfunction "COM_3") (pintype "bidirectional"))
      (node (ref "L973") (pin "1") (pinfunction "1_1") (pintype "passive"))
    )
    (net (code "1023") (name "Net-(D974-COM)") (class "Default")
      (node (ref "D974") (pin "3") (pinfunction "COM_3") (pintype "bidirectional"))
      (node (ref "L974") (pin "1") (pinfunction "1_1") (pintype "passive"))
    )
    (net (code "1024") (name "Net-(D975-COM)") (class "Default")
      (node (ref "D975") (pin "3") (pinfunction "COM_3") (pintype "bidirectional"))
      (node (ref "L975") (pin "1") (pinfunction "1_1") (pintype "passive"))
    )
    (net (code "1025") (name "Net-(D976-COM)") (class "Default")
      (node (ref "D976") (pin "3") (pinfunction "COM_3") (pintype "bidirectional"))
      (node (ref "L976") (pin "1") (pinfunction "1_1") (pintype "passive"))
    )
    (net (code "1026") (name "Net-(D977-COM)") (class "Default")
      (node (ref "D977") (pin "3") (pinfunction "COM_3") (pintype "bidirectional"))
      (node (ref "L977") (pin "1") (pinfunction "1_1") (pintype "passive"))
    )
    (net (code "1027") (name "Net-(D978-COM)") (class "Default")
      (node (ref "D978") (pin "3") (pinfunction "COM_3") (pintype "bidirectional"))
      (node (ref "L978") (pin "1") (pinfunction "1_1") (pintype "passive"))
    )
    (net (code "1028") (name "Net-(D979-COM)") (class "Default")
      (node (ref "D979") (pin "3") (pinfunction "COM_3") (pintype "bidirectional"))
      (node (ref "L979") (pin "1") (pinfunction "1_1") (pintype "passive"))
    )
    (net (code "1029") (name "Net-(D980-COM)") (class "Default")
      (node (ref "D980") (pin "3") (pinfunction "COM_3") (pintype "bidirectional"))
      (node (ref "L980") (pin "1") (pinfunction "1_1") (pintype "passive"))
    )
    (net (code "1030") (name "Net-(D981-COM)") (class "Default")
      (node (ref "D981") (pin "3") (pinfunction "COM_3") (pintype "bidirectional"))
      (node (ref "L981") (pin "1") (pinfunction "1_1") (pintype "passive"))
    )
    (net (code "1031") (name "Net-(D982-COM)") (class "Default")
      (node (ref "D982") (pin "3") (pinfunction "COM_3") (pintype "bidirectional"))
      (node (ref "L982") (pin "1") (pinfunction "1_1") (pintype "passive"))
    )
    (net (code "1032") (name "Net-(D983-COM)") (class "Default")
      (node (ref "D983") (pin "3") (pinfunction "COM_3") (pintype "bidirectional"))
      (node (ref "L983") (pin "1") (pinfunction "1_1") (pintype "passive"))
    )
    (net (code "1033") (name "Net-(D984-COM)") (class "Default")
      (node (ref "D984") (pin "3") (pinfunction "COM_3") (pintype "bidirectional"))
      (node (ref "L984") (pin "1") (pinfunction "1_1") (pintype "passive"))
    )
    (net (code "1034") (name "Net-(D985-COM)") (class "Default")
      (node (ref "D985") (pin "3") (pinfunction "COM_3") (pintype "bidirectional"))
      (node (ref "L985") (pin "1") (pinfunction "1_1") (pintype "passive"))
    )
    (net (code "1035") (name "Net-(D986-COM)") (class "Default")
      (node (ref "D986") (pin "3") (pinfunction "COM_3") (pintype "bidirectional"))
      (node (ref "L986") (pin "1") (pinfunction "1_1") (pintype "passive"))
    )
    (net (code "1036") (name "Net-(D987-COM)") (class "Default")
      (node (ref "D987") (pin "3") (pinfunction "COM_3") (pintype "bidirectional"))
      (node (ref "L987") (pin "1") (pinfunction "1_1") (pintype "passive"))
    )
    (net (code "1037") (name "Net-(D988-COM)") (class "Default")
      (node (ref "D988") (pin "3") (pinfunction "COM_3") (pintype "bidirectional"))
      (node (ref "L988") (pin "1") (pinfunction "1_1") (pintype "passive"))
    )
    (net (code "1038") (name "Net-(D989-COM)") (class "Default")
      (node (ref "D989") (pin "3") (pinfunction "COM_3") (pintype "bidirectional"))
      (node (ref "L989") (pin "1") (pinfunction "1_1") (pintype "passive"))
    )
    (net (code "1039") (name "Net-(D990-COM)") (class "Default")
      (node (ref "D990") (pin "3") (pinfunction "COM_3") (pintype "bidirectional"))
      (node (ref "L990") (pin "1") (pinfunction "1_1") (pintype "passive"))
    )
    (net (code "1040") (name "Net-(D991-COM)") (class "Default")
      (node (ref "D991") (pin "3") (pinfunction "COM_3") (pintype "bidirectional"))
      (node (ref "L991") (pin "1") (pinfunction "1_1") (pintype "passive"))
    )
    (net (code "1041") (name "Net-(D992-COM)") (class "Default")
      (node (ref "D992") (pin "3") (pinfunction "COM_3") (pintype "bidirectional"))
      (node (ref "L992") (pin "1") (pinfunction "1_1") (pintype "passive"))
    )
    (net (code "1042") (name "Net-(D993-COM)") (class "Default")
      (node (ref "D993") (pin "3") (pinfunction "COM_3") (pintype "bidirectional"))
      (node (ref "L993") (pin "1") (pinfunction "1_1") (pintype "passive"))
    )
    (net (code "1043") (name "Net-(D994-COM)") (class "Default")
      (node (ref "D994") (pin "3") (pinfunction "COM_3") (pintype "bidirectional"))
      (node (ref "L994") (pin "1") (pinfunction "1_1") (pintype "passive"))
    )
    (net (code "1044") (name "Net-(D995-COM)") (class "Default")
      (node (ref "D995") (pin "3") (pinfunction "COM_3") (pintype "bidirectional"))
      (node (ref "L995") (pin "1") (pinfunction "1_1") (pintype "passive"))
    )
    (net (code "1045") (name "Net-(D996-COM)") (class "Default")
      (node (ref "D996") (pin "3") (pinfunction "COM_3") (pintype "bidirectional"))
      (node (ref "L996") (pin "1") (pinfunction "1_1") (pintype "passive"))
    )
    (net (code "1046") (name "Net-(D997-COM)") (class "Default")
      (node (ref "D997") (pin "3") (pinfunction "COM_3") (pintype "bidirectional"))
      (node (ref "L997") (pin "1") (pinfunction "1_1") (pintype "passive"))
    )
    (net (code "1047") (name "Net-(D998-COM)") (class "Default")
      (node (ref "D998") (pin "3") (pinfunction "COM_3") (pintype "bidirectional"))
      (node (ref "L998") (pin "1") (pinfunction "1_1") (pintype "passive"))
    )
    (net (code "1048") (name "Net-(D999-COM)") (class "Default")
      (node (ref "D999") (pin "3") (pinfunction "COM_3") (pintype "bidirectional"))
      (node (ref "L999") (pin "1") (pinfunction "1_1") (pintype "passive"))
    )
    (net (code "1049") (name "Net-(D1000-COM)") (class "Default")
      (node (ref "D1000") (pin "3") (pinfunction "COM_3") (pintype "bidirectional"))
      (node (ref "L1000") (pin "1") (pinfunction "1_1") (pintype "passive"))
    )
    (net (code "1050") (name "Net-(D1001-COM)") (class "Default")
      (node (ref "D1001") (pin "3") (pinfunction "COM_3") (pintype "bidirectional"))
      (node (ref "L1001") (pin "1") (pinfunction "1_1") (pintype "passive"))
    )
    (net (code "1051") (name "Net-(D1002-COM)") (class "Default")
      (node (ref "D1002") (pin "3") (pinfunction "COM_3") (pintype "bidirectional"))
      (node (ref "L1002") (pin "1") (pinfunction "1_1") (pintype "passive"))
    )
    (net (code "1052") (name "Net-(D1003-COM)") (class "Default")
      (node (ref "D1003") (pin "3") (pinfunction "COM_3") (pintype "bidirectional"))
      (node (ref "L1003") (pin "1") (pinfunction "1_1") (pintype "passive"))
    )
    (net (code "1053") (name "Net-(D1004-COM)") (class "Default")
      (node (ref "D1004") (pin "3") (pinfunction "COM_3") (pintype "bidirectional"))
      (node (ref "L1004") (pin "1") (pinfunction "1_1") (pintype "passive"))
    )
    (net (code "1054") (name "Net-(D1005-COM)") (class "Default")
      (node (ref "D1005") (pin "3") (pinfunction "COM_3") (pintype "bidirectional"))
      (node (ref "L1005") (pin "1") (pinfunction "1_1") (pintype "passive"))
    )
    (net (code "1055") (name "Net-(D1006-COM)") (class "Default")
      (node (ref "D1006") (pin "3") (pinfunction "COM_3") (pintype "bidirectional"))
      (node (ref "L1006") (pin "1") (pinfunction "1_1") (pintype "passive"))
    )
    (net (code "1056") (name "Net-(D1007-COM)") (class "Default")
      (node (ref "D1007") (pin "3") (pinfunction "COM_3") (pintype "bidirectional"))
      (node (ref "L1007") (pin "1") (pinfunction "1_1") (pintype "passive"))
    )
    (net (code "1057") (name "Net-(D1008-COM)") (class "Default")
      (node (ref "D1008") (pin "3") (pinfunction "COM_3") (pintype "bidirectional"))
      (node (ref "L1008") (pin "1") (pinfunction "1_1") (pintype "passive"))
    )
    (net (code "1058") (name "Net-(D1009-COM)") (class "Default")
      (node (ref "D1009") (pin "3") (pinfunction "COM_3") (pintype "bidirectional"))
      (node (ref "L1009") (pin "1") (pinfunction "1_1") (pintype "passive"))
    )
    (net (code "1059") (name "Net-(D1010-COM)") (class "Default")
      (node (ref "D1010") (pin "3") (pinfunction "COM_3") (pintype "bidirectional"))
      (node (ref "L1010") (pin "1") (pinfunction "1_1") (pintype "passive"))
    )
    (net (code "1060") (name "Net-(D1011-COM)") (class "Default")
      (node (ref "D1011") (pin "3") (pinfunction "COM_3") (pintype "bidirectional"))
      (node (ref "L1011") (pin "1") (pinfunction "1_1") (pintype "passive"))
    )
    (net (code "1061") (name "Net-(D1012-COM)") (class "Default")
      (node (ref "D1012") (pin "3") (pinfunction "COM_3") (pintype "bidirectional"))
      (node (ref "L1012") (pin "1") (pinfunction "1_1") (pintype "passive"))
    )
    (net (code "1062") (name "Net-(D1013-COM)") (class "Default")
      (node (ref "D1013") (pin "3") (pinfunction "COM_3") (pintype "bidirectional"))
      (node (ref "L1013") (pin "1") (pinfunction "1_1") (pintype "passive"))
    )
    (net (code "1063") (name "Net-(D1014-COM)") (class "Default")
      (node (ref "D1014") (pin "3") (pinfunction "COM_3") (pintype "bidirectional"))
      (node (ref "L1014") (pin "1") (pinfunction "1_1") (pintype "passive"))
    )
    (net (code "1064") (name "Net-(D1015-COM)") (class "Default")
      (node (ref "D1015") (pin "3") (pinfunction "COM_3") (pintype "bidirectional"))
      (node (ref "L1015") (pin "1") (pinfunction "1_1") (pintype "passive"))
    )
    (net (code "1065") (name "Net-(D1016-COM)") (class "Default")
      (node (ref "D1016") (pin "3") (pinfunction "COM_3") (pintype "bidirectional"))
      (node (ref "L1016") (pin "1") (pinfunction "1_1") (pintype "passive"))
    )
    (net (code "1066") (name "Net-(D1017-COM)") (class "Default")
      (node (ref "D1017") (pin "3") (pinfunction "COM_3") (pintype "bidirectional"))
      (node (ref "L1017") (pin "1") (pinfunction "1_1") (pintype "passive"))
    )
    (net (code "1067") (name "Net-(D1018-COM)") (class "Default")
      (node (ref "D1018") (pin "3") (pinfunction "COM_3") (pintype "bidirectional"))
      (node (ref "L1018") (pin "1") (pinfunction "1_1") (pintype "passive"))
    )
    (net (code "1068") (name "Net-(D1019-COM)") (class "Default")
      (node (ref "D1019") (pin "3") (pinfunction "COM_3") (pintype "bidirectional"))
      (node (ref "L1019") (pin "1") (pinfunction "1_1") (pintype "passive"))
    )
    (net (code "1069") (name "Net-(D1020-COM)") (class "Default")
      (node (ref "D1020") (pin "3") (pinfunction "COM_3") (pintype "bidirectional"))
      (node (ref "L1020") (pin "1") (pinfunction "1_1") (pintype "passive"))
    )
    (net (code "1070") (name "Net-(D1021-COM)") (class "Default")
      (node (ref "D1021") (pin "3") (pinfunction "COM_3") (pintype "bidirectional"))
      (node (ref "L1021") (pin "1") (pinfunction "1_1") (pintype "passive"))
    )
    (net (code "1071") (name "Net-(D1022-COM)") (class "Default")
      (node (ref "D1022") (pin "3") (pinfunction "COM_3") (pintype "bidirectional"))
      (node (ref "L1022") (pin "1") (pinfunction "1_1") (pintype "passive"))
    )
    (net (code "1072") (name "Net-(D1023-COM)") (class "Default")
      (node (ref "D1023") (pin "3") (pinfunction "COM_3") (pintype "bidirectional"))
      (node (ref "L1023") (pin "1") (pinfunction "1_1") (pintype "passive"))
    )
    (net (code "1073") (name "Net-(D1024-COM)") (class "Default")
      (node (ref "D1024") (pin "3") (pinfunction "COM_3") (pintype "bidirectional"))
      (node (ref "L1024") (pin "1") (pinfunction "1_1") (pintype "passive"))
    )
    (net (code "1074") (name "Net-(IC1A-Q1)") (class "Default")
      (node (ref "IC1") (pin "16") (pinfunction "Q1_16") (pintype "output"))
      (node (ref "IC2") (pin "2") (pinfunction "RES_2") (pintype "input"))
      (node (ref "IC4") (pin "1") (pinfunction "CLK_1") (pintype "input"))
    )
    (net (code "1075") (name "Net-(IC1A-Q2)") (class "Default")
      (node (ref "IC1") (pin "15") (pinfunction "Q2_15") (pintype "output"))
      (node (ref "IC3") (pin "1") (pinfunction "G_1") (pintype "input"))
      (node (ref "IC3") (pin "15") (pinfunction "G_15") (pintype "input"))
      (node (ref "IC4") (pin "2") (pinfunction "RES_2") (pintype "input"))
    )
    (net (code "1076") (name "Net-(IC1A-Q4)") (class "Default")
      (node (ref "IC1") (pin "9") (pinfunction "Q4_9") (pintype "output"))
      (node (ref "IC2") (pin "1") (pinfunction "CLK_1") (pintype "input"))
    )
    (net (code "1077") (name "Net-(IC2A-Q4)") (class "Default")
      (node (ref "IC2") (pin "6") (pinfunction "Q4_6") (pintype "output"))
      (node (ref "IC3") (pin "2") (pinfunction "A_2") (pintype "input"))
    )
    (net (code "1078") (name "Net-(IC2A-Q5)") (class "Default")
      (node (ref "IC2") (pin "5") (pinfunction "Q5_5") (pintype "output"))
      (node (ref "IC3") (pin "3") (pinfunction "B_3") (pintype "input"))
    )
    (net (code "1079") (name "Net-(IC3B-A)") (class "Default")
      (node (ref "IC3") (pin "14") (pinfunction "A_14") (pintype "input"))
      (node (ref "IC4") (pin "6") (pinfunction "Q4_6") (pintype "output"))
    )
    (net (code "1080") (name "Net-(IC3B-B)") (class "Default")
      (node (ref "IC3") (pin "13") (pinfunction "B_13") (pintype "input"))
      (node (ref "IC4") (pin "5") (pinfunction "Q5_5") (pintype "output"))
    )
    (net (code "1081") (name "Net-(IC5A-S0)") (class "Default")
      (node (ref "IC5") (pin "11") (pinfunction "S0_11") (pintype "output"))
      (node (ref "IC6") (pin "1") (pinfunction "I1_1") (pintype "input"))
    )
    (net (code "1082") (name "Net-(IC5A-S1)") (class "Default")
      (node (ref "IC5") (pin "9") (pinfunction "S1_9") (pintype "output"))
      (node (ref "IC6") (pin "2") (pinfunction "I2_2") (pintype "input"))
    )
    (net (code "1083") (name "Net-(IC5A-S2)") (class "Default")
      (node (ref "IC5") (pin "10") (pinfunction "S2_10") (pintype "output"))
      (node (ref "IC6") (pin "3") (pinfunction "I3_3") (pintype "input"))
    )
    (net (code "1084") (name "Net-(IC5A-S3)") (class "Default")
      (node (ref "IC5") (pin "8") (pinfunction "S3_8") (pintype "output"))
      (node (ref "IC6") (pin "4") (pinfunction "I4_4") (pintype "input"))
    )
    (net (code "1085") (name "Net-(IC5A-S4)") (class "Default")
      (node (ref "IC5") (pin "7") (pinfunction "S4_7") (pintype "output"))
      (node (ref "IC6") (pin "5") (pinfunction "I5_5") (pintype "input"))
    )
    (net (code "1086") (name "Net-(IC5A-S5)") (class "Default")
      (node (ref "IC5") (pin "6") (pinfunction "S5_6") (pintype "output"))
      (node (ref "IC6") (pin "6") (pinfunction "I6_6") (pintype "input"))
    )
    (net (code "1087") (name "Net-(IC5A-S6)") (class "Default")
      (node (ref "IC5") (pin "5") (pinfunction "S6_5") (pintype "output"))
      (node (ref "IC6") (pin "7") (pinfunction "I7_7") (pintype "input"))
    )
    (net (code "1088") (name "Net-(IC5A-S7)") (class "Default")
      (node (ref "IC5") (pin "4") (pinfunction "S7_4") (pintype "output"))
      (node (ref "IC6") (pin "8") (pinfunction "I8_8") (pintype "input"))
    )
    (net (code "1089") (name "Net-(IC5A-S8)") (class "Default")
      (node (ref "IC5") (pin "18") (pinfunction "S8_18") (pintype "output"))
      (node (ref "IC7") (pin "1") (pinfunction "I1_1") (pintype "input"))
    )
    (net (code "1090") (name "Net-(IC5A-S9)") (class "Default")
      (node (ref "IC5") (pin "17") (pinfunction "S9_17") (pintype "output"))
      (node (ref "IC7") (pin "2") (pinfunction "I2_2") (pintype "input"))
    )
    (net (code "1091") (name "Net-(IC5A-S10)") (class "Default")
      (node (ref "IC5") (pin "20") (pinfunction "S10_20") (pintype "output"))
      (node (ref "IC7") (pin "3") (pinfunction "I3_3") (pintype "input"))
    )
    (net (code "1092") (name "Net-(IC5A-S11)") (class "Default")
      (node (ref "IC5") (pin "19") (pinfunction "S11_19") (pintype "output"))
      (node (ref "IC7") (pin "4") (pinfunction "I4_4") (pintype "input"))
    )
    (net (code "1093") (name "Net-(IC5A-S12)") (class "Default")
      (node (ref "IC5") (pin "14") (pinfunction "S12_14") (pintype "output"))
      (node (ref "IC7") (pin "5") (pinfunction "I5_5") (pintype "input"))
    )
    (net (code "1094") (name "Net-(IC5A-S13)") (class "Default")
      (node (ref "IC5") (pin "13") (pinfunction "S13_13") (pintype "output"))
      (node (ref "IC7") (pin "6") (pinfunction "I6_6") (pintype "input"))
    )
    (net (code "1095") (name "Net-(IC5A-S14)") (class "Default")
      (node (ref "IC5") (pin "16") (pinfunction "S14_16") (pintype "output"))
      (node (ref "IC7") (pin "7") (pinfunction "I7_7") (pintype "input"))
    )
    (net (code "1096") (name "Net-(IC5A-S15)") (class "Default")
      (node (ref "IC5") (pin "15") (pinfunction "S15_15") (pintype "output"))
      (node (ref "IC7") (pin "8") (pinfunction "I8_8") (pintype "input"))
    )
    (net (code "1097") (name "Net-(IC8A-S0)") (class "Default")
      (node (ref "IC8") (pin "11") (pinfunction "S0_11") (pintype "output"))
      (node (ref "IC9") (pin "1") (pinfunction "I1_1") (pintype "input"))
    )
    (net (code "1098") (name "Net-(IC8A-S1)") (class "Default")
      (node (ref "IC8") (pin "9") (pinfunction "S1_9") (pintype "output"))
      (node (ref "IC9") (pin "2") (pinfunction "I2_2") (pintype "input"))
    )
    (net (code "1099") (name "Net-(IC8A-S2)") (class "Default")
      (node (ref "IC8") (pin "10") (pinfunction "S2_10") (pintype "output"))
      (node (ref "IC9") (pin "3") (pinfunction "I3_3") (pintype "input"))
    )
    (net (code "1100") (name "Net-(IC8A-S3)") (class "Default")
      (node (ref "IC8") (pin "8") (pinfunction "S3_8") (pintype "output"))
      (node (ref "IC9") (pin "4") (pinfunction "I4_4") (pintype "input"))
    )
    (net (code "1101") (name "Net-(IC8A-S4)") (class "Default")
      (node (ref "IC8") (pin "7") (pinfunction "S4_7") (pintype "output"))
      (node (ref "IC9") (pin "5") (pinfunction "I5_5") (pintype "input"))
    )
    (net (code "1102") (name "Net-(IC8A-S5)") (class "Default")
      (node (ref "IC8") (pin "6") (pinfunction "S5_6") (pintype "output"))
      (node (ref "IC9") (pin "6") (pinfunction "I6_6") (pintype "input"))
    )
    (net (code "1103") (name "Net-(IC8A-S6)") (class "Default")
      (node (ref "IC8") (pin "5") (pinfunction "S6_5") (pintype "output"))
      (node (ref "IC9") (pin "7") (pinfunction "I7_7") (pintype "input"))
    )
    (net (code "1104") (name "Net-(IC8A-S7)") (class "Default")
      (node (ref "IC8") (pin "4") (pinfunction "S7_4") (pintype "output"))
      (node (ref "IC9") (pin "8") (pinfunction "I8_8") (pintype "input"))
    )
    (net (code "1105") (name "Net-(IC10-I1)") (class "Default")
      (node (ref "IC10") (pin "1") (pinfunction "I1_1") (pintype "input"))
      (node (ref "IC8") (pin "18") (pinfunction "S8_18") (pintype "output"))
    )
    (net (code "1106") (name "Net-(IC10-I2)") (class "Default")
      (node (ref "IC10") (pin "2") (pinfunction "I2_2") (pintype "input"))
      (node (ref "IC8") (pin "17") (pinfunction "S9_17") (pintype "output"))
    )
    (net (code "1107") (name "Net-(IC10-I3)") (class "Default")
      (node (ref "IC10") (pin "3") (pinfunction "I3_3") (pintype "input"))
      (node (ref "IC8") (pin "20") (pinfunction "S10_20") (pintype "output"))
    )
    (net (code "1108") (name "Net-(IC10-I4)") (class "Default")
      (node (ref "IC10") (pin "4") (pinfunction "I4_4") (pintype "input"))
      (node (ref "IC8") (pin "19") (pinfunction "S11_19") (pintype "output"))
    )
    (net (code "1109") (name "Net-(IC10-I5)") (class "Default")
      (node (ref "IC10") (pin "5") (pinfunction "I5_5") (pintype "input"))
      (node (ref "IC8") (pin "14") (pinfunction "S12_14") (pintype "output"))
    )
    (net (code "1110") (name "Net-(IC10-I6)") (class "Default")
      (node (ref "IC10") (pin "6") (pinfunction "I6_6") (pintype "input"))
      (node (ref "IC8") (pin "13") (pinfunction "S13_13") (pintype "output"))
    )
    (net (code "1111") (name "Net-(IC10-I7)") (class "Default")
      (node (ref "IC10") (pin "7") (pinfunction "I7_7") (pintype "input"))
      (node (ref "IC8") (pin "16") (pinfunction "S14_16") (pintype "output"))
    )
    (net (code "1112") (name "Net-(IC10-I8)") (class "Default")
      (node (ref "IC10") (pin "8") (pinfunction "I8_8") (pintype "input"))
      (node (ref "IC8") (pin "15") (pinfunction "S15_15") (pintype "output"))
    )
    (net (code "1113") (name "Net-(IC11A-S0)") (class "Default")
      (node (ref "IC11") (pin "11") (pinfunction "S0_11") (pintype "output"))
      (node (ref "IC13") (pin "1") (pinfunction "I1_1") (pintype "input"))
    )
    (net (code "1114") (name "Net-(IC11A-S1)") (class "Default")
      (node (ref "IC11") (pin "9") (pinfunction "S1_9") (pintype "output"))
      (node (ref "IC13") (pin "2") (pinfunction "I2_2") (pintype "input"))
    )
    (net (code "1115") (name "Net-(IC11A-S2)") (class "Default")
      (node (ref "IC11") (pin "10") (pinfunction "S2_10") (pintype "output"))
      (node (ref "IC13") (pin "3") (pinfunction "I3_3") (pintype "input"))
    )
    (net (code "1116") (name "Net-(IC11A-S3)") (class "Default")
      (node (ref "IC11") (pin "8") (pinfunction "S3_8") (pintype "output"))
      (node (ref "IC13") (pin "4") (pinfunction "I4_4") (pintype "input"))
    )
    (net (code "1117") (name "Net-(IC11A-S4)") (class "Default")
      (node (ref "IC11") (pin "7") (pinfunction "S4_7") (pintype "output"))
      (node (ref "IC13") (pin "5") (pinfunction "I5_5") (pintype "input"))
    )
    (net (code "1118") (name "Net-(IC11A-S5)") (class "Default")
      (node (ref "IC11") (pin "6") (pinfunction "S5_6") (pintype "output"))
      (node (ref "IC13") (pin "6") (pinfunction "I6_6") (pintype "input"))
    )
    (net (code "1119") (name "Net-(IC11A-S6)") (class "Default")
      (node (ref "IC11") (pin "5") (pinfunction "S6_5") (pintype "output"))
      (node (ref "IC13") (pin "7") (pinfunction "I7_7") (pintype "input"))
    )
    (net (code "1120") (name "Net-(IC11A-S7)") (class "Default")
      (node (ref "IC11") (pin "4") (pinfunction "S7_4") (pintype "output"))
      (node (ref "IC13") (pin "8") (pinfunction "I8_8") (pintype "input"))
    )
    (net (code "1121") (name "Net-(IC11A-S8)") (class "Default")
      (node (ref "IC11") (pin "18") (pinfunction "S8_18") (pintype "output"))
      (node (ref "IC12") (pin "1") (pinfunction "I1_1") (pintype "input"))
    )
    (net (code "1122") (name "Net-(IC11A-S9)") (class "Default")
      (node (ref "IC11") (pin "17") (pinfunction "S9_17") (pintype "output"))
      (node (ref "IC12") (pin "2") (pinfunction "I2_2") (pintype "input"))
    )
    (net (code "1123") (name "Net-(IC11A-S10)") (class "Default")
      (node (ref "IC11") (pin "20") (pinfunction "S10_20") (pintype "output"))
      (node (ref "IC12") (pin "3") (pinfunction "I3_3") (pintype "input"))
    )
    (net (code "1124") (name "Net-(IC11A-S11)") (class "Default")
      (node (ref "IC11") (pin "19") (pinfunction "S11_19") (pintype "output"))
      (node (ref "IC12") (pin "4") (pinfunction "I4_4") (pintype "input"))
    )
    (net (code "1125") (name "Net-(IC11A-S12)") (class "Default")
      (node (ref "IC11") (pin "14") (pinfunction "S12_14") (pintype "output"))
      (node (ref "IC12") (pin "5") (pinfunction "I5_5") (pintype "input"))
    )
    (net (code "1126") (name "Net-(IC11A-S13)") (class "Default")
      (node (ref "IC11") (pin "13") (pinfunction "S13_13") (pintype "output"))
      (node (ref "IC12") (pin "6") (pinfunction "I6_6") (pintype "input"))
    )
    (net (code "1127") (name "Net-(IC11A-S14)") (class "Default")
      (node (ref "IC11") (pin "16") (pinfunction "S14_16") (pintype "output"))
      (node (ref "IC12") (pin "7") (pinfunction "I7_7") (pintype "input"))
    )
    (net (code "1128") (name "Net-(IC11A-S15)") (class "Default")
      (node (ref "IC11") (pin "15") (pinfunction "S15_15") (pintype "output"))
      (node (ref "IC12") (pin "8") (pinfunction "I8_8") (pintype "input"))
    )
    (net (code "1129") (name "Net-(IC14A-S0)") (class "Default")
      (node (ref "IC14") (pin "11") (pinfunction "S0_11") (pintype "output"))
      (node (ref "IC16") (pin "1") (pinfunction "I1_1") (pintype "input"))
    )
    (net (code "1130") (name "Net-(IC14A-S1)") (class "Default")
      (node (ref "IC14") (pin "9") (pinfunction "S1_9") (pintype "output"))
      (node (ref "IC16") (pin "2") (pinfunction "I2_2") (pintype "input"))
    )
    (net (code "1131") (name "Net-(IC14A-S2)") (class "Default")
      (node (ref "IC14") (pin "10") (pinfunction "S2_10") (pintype "output"))
      (node (ref "IC16") (pin "3") (pinfunction "I3_3") (pintype "input"))
    )
    (net (code "1132") (name "Net-(IC14A-S3)") (class "Default")
      (node (ref "IC14") (pin "8") (pinfunction "S3_8") (pintype "output"))
      (node (ref "IC16") (pin "4") (pinfunction "I4_4") (pintype "input"))
    )
    (net (code "1133") (name "Net-(IC14A-S4)") (class "Default")
      (node (ref "IC14") (pin "7") (pinfunction "S4_7") (pintype "output"))
      (node (ref "IC16") (pin "5") (pinfunction "I5_5") (pintype "input"))
    )
    (net (code "1134") (name "Net-(IC14A-S5)") (class "Default")
      (node (ref "IC14") (pin "6") (pinfunction "S5_6") (pintype "output"))
      (node (ref "IC16") (pin "6") (pinfunction "I6_6") (pintype "input"))
    )
    (net (code "1135") (name "Net-(IC14A-S6)") (class "Default")
      (node (ref "IC14") (pin "5") (pinfunction "S6_5") (pintype "output"))
      (node (ref "IC16") (pin "7") (pinfunction "I7_7") (pintype "input"))
    )
    (net (code "1136") (name "Net-(IC14A-S7)") (class "Default")
      (node (ref "IC14") (pin "4") (pinfunction "S7_4") (pintype "output"))
      (node (ref "IC16") (pin "8") (pinfunction "I8_8") (pintype "input"))
    )
    (net (code "1137") (name "Net-(IC14A-S8)") (class "Default")
      (node (ref "IC14") (pin "18") (pinfunction "S8_18") (pintype "output"))
      (node (ref "IC15") (pin "1") (pinfunction "I1_1") (pintype "input"))
    )
    (net (code "1138") (name "Net-(IC14A-S9)") (class "Default")
      (node (ref "IC14") (pin "17") (pinfunction "S9_17") (pintype "output"))
      (node (ref "IC15") (pin "2") (pinfunction "I2_2") (pintype "input"))
    )
    (net (code "1139") (name "Net-(IC14A-S10)") (class "Default")
      (node (ref "IC14") (pin "20") (pinfunction "S10_20") (pintype "output"))
      (node (ref "IC15") (pin "3") (pinfunction "I3_3") (pintype "input"))
    )
    (net (code "1140") (name "Net-(IC14A-S11)") (class "Default")
      (node (ref "IC14") (pin "19") (pinfunction "S11_19") (pintype "output"))
      (node (ref "IC15") (pin "4") (pinfunction "I4_4") (pintype "input"))
    )
    (net (code "1141") (name "Net-(IC14A-S12)") (class "Default")
      (node (ref "IC14") (pin "14") (pinfunction "S12_14") (pintype "output"))
      (node (ref "IC15") (pin "5") (pinfunction "I5_5") (pintype "input"))
    )
    (net (code "1142") (name "Net-(IC14A-S13)") (class "Default")
      (node (ref "IC14") (pin "13") (pinfunction "S13_13") (pintype "output"))
      (node (ref "IC15") (pin "6") (pinfunction "I6_6") (pintype "input"))
    )
    (net (code "1143") (name "Net-(IC14A-S14)") (class "Default")
      (node (ref "IC14") (pin "16") (pinfunction "S14_16") (pintype "output"))
      (node (ref "IC15") (pin "7") (pinfunction "I7_7") (pintype "input"))
    )
    (net (code "1144") (name "Net-(IC14A-S15)") (class "Default")
      (node (ref "IC14") (pin "15") (pinfunction "S15_15") (pintype "output"))
      (node (ref "IC15") (pin "8") (pinfunction "I8_8") (pintype "input"))
    )
    (net (code "1145") (name "Net-(IC17A-S0)") (class "Default")
      (node (ref "IC17") (pin "11") (pinfunction "S0_11") (pintype "output"))
      (node (ref "IC19") (pin "1") (pinfunction "I1_1") (pintype "input"))
    )
    (net (code "1146") (name "Net-(IC17A-S1)") (class "Default")
      (node (ref "IC17") (pin "9") (pinfunction "S1_9") (pintype "output"))
      (node (ref "IC19") (pin "2") (pinfunction "I2_2") (pintype "input"))
    )
    (net (code "1147") (name "Net-(IC17A-S2)") (class "Default")
      (node (ref "IC17") (pin "10") (pinfunction "S2_10") (pintype "output"))
      (node (ref "IC19") (pin "3") (pinfunction "I3_3") (pintype "input"))
    )
    (net (code "1148") (name "Net-(IC17A-S3)") (class "Default")
      (node (ref "IC17") (pin "8") (pinfunction "S3_8") (pintype "output"))
      (node (ref "IC19") (pin "4") (pinfunction "I4_4") (pintype "input"))
    )
    (net (code "1149") (name "Net-(IC17A-S4)") (class "Default")
      (node (ref "IC17") (pin "7") (pinfunction "S4_7") (pintype "output"))
      (node (ref "IC19") (pin "5") (pinfunction "I5_5") (pintype "input"))
    )
    (net (code "1150") (name "Net-(IC17A-S5)") (class "Default")
      (node (ref "IC17") (pin "6") (pinfunction "S5_6") (pintype "output"))
      (node (ref "IC19") (pin "6") (pinfunction "I6_6") (pintype "input"))
    )
    (net (code "1151") (name "Net-(IC17A-S6)") (class "Default")
      (node (ref "IC17") (pin "5") (pinfunction "S6_5") (pintype "output"))
      (node (ref "IC19") (pin "7") (pinfunction "I7_7") (pintype "input"))
    )
    (net (code "1152") (name "Net-(IC17A-S7)") (class "Default")
      (node (ref "IC17") (pin "4") (pinfunction "S7_4") (pintype "output"))
      (node (ref "IC19") (pin "8") (pinfunction "I8_8") (pintype "input"))
    )
    (net (code "1153") (name "Net-(IC17A-S8)") (class "Default")
      (node (ref "IC17") (pin "18") (pinfunction "S8_18") (pintype "output"))
      (node (ref "IC18") (pin "1") (pinfunction "I1_1") (pintype "input"))
    )
    (net (code "1154") (name "Net-(IC17A-S9)") (class "Default")
      (node (ref "IC17") (pin "17") (pinfunction "S9_17") (pintype "output"))
      (node (ref "IC18") (pin "2") (pinfunction "I2_2") (pintype "input"))
    )
    (net (code "1155") (name "Net-(IC17A-S10)") (class "Default")
      (node (ref "IC17") (pin "20") (pinfunction "S10_20") (pintype "output"))
      (node (ref "IC18") (pin "3") (pinfunction "I3_3") (pintype "input"))
    )
    (net (code "1156") (name "Net-(IC17A-S11)") (class "Default")
      (node (ref "IC17") (pin "19") (pinfunction "S11_19") (pintype "output"))
      (node (ref "IC18") (pin "4") (pinfunction "I4_4") (pintype "input"))
    )
    (net (code "1157") (name "Net-(IC17A-S12)") (class "Default")
      (node (ref "IC17") (pin "14") (pinfunction "S12_14") (pintype "output"))
      (node (ref "IC18") (pin "5") (pinfunction "I5_5") (pintype "input"))
    )
    (net (code "1158") (name "Net-(IC17A-S13)") (class "Default")
      (node (ref "IC17") (pin "13") (pinfunction "S13_13") (pintype "output"))
      (node (ref "IC18") (pin "6") (pinfunction "I6_6") (pintype "input"))
    )
    (net (code "1159") (name "Net-(IC17A-S14)") (class "Default")
      (node (ref "IC17") (pin "16") (pinfunction "S14_16") (pintype "output"))
      (node (ref "IC18") (pin "7") (pinfunction "I7_7") (pintype "input"))
    )
    (net (code "1160") (name "Net-(IC17A-S15)") (class "Default")
      (node (ref "IC17") (pin "15") (pinfunction "S15_15") (pintype "output"))
      (node (ref "IC18") (pin "8") (pinfunction "I8_8") (pintype "input"))
    )
    (net (code "1161") (name "Net-(IC20A-S0)") (class "Default")
      (node (ref "IC20") (pin "11") (pinfunction "S0_11") (pintype "output"))
      (node (ref "IC22") (pin "1") (pinfunction "I1_1") (pintype "input"))
    )
    (net (code "1162") (name "Net-(IC20A-S1)") (class "Default")
      (node (ref "IC20") (pin "9") (pinfunction "S1_9") (pintype "output"))
      (node (ref "IC22") (pin "2") (pinfunction "I2_2") (pintype "input"))
    )
    (net (code "1163") (name "Net-(IC20A-S2)") (class "Default")
      (node (ref "IC20") (pin "10") (pinfunction "S2_10") (pintype "output"))
      (node (ref "IC22") (pin "3") (pinfunction "I3_3") (pintype "input"))
    )
    (net (code "1164") (name "Net-(IC20A-S3)") (class "Default")
      (node (ref "IC20") (pin "8") (pinfunction "S3_8") (pintype "output"))
      (node (ref "IC22") (pin "4") (pinfunction "I4_4") (pintype "input"))
    )
    (net (code "1165") (name "Net-(IC20A-S4)") (class "Default")
      (node (ref "IC20") (pin "7") (pinfunction "S4_7") (pintype "output"))
      (node (ref "IC22") (pin "5") (pinfunction "I5_5") (pintype "input"))
    )
    (net (code "1166") (name "Net-(IC20A-S5)") (class "Default")
      (node (ref "IC20") (pin "6") (pinfunction "S5_6") (pintype "output"))
      (node (ref "IC22") (pin "6") (pinfunction "I6_6") (pintype "input"))
    )
    (net (code "1167") (name "Net-(IC20A-S6)") (class "Default")
      (node (ref "IC20") (pin "5") (pinfunction "S6_5") (pintype "output"))
      (node (ref "IC22") (pin "7") (pinfunction "I7_7") (pintype "input"))
    )
    (net (code "1168") (name "Net-(IC20A-S7)") (class "Default")
      (node (ref "IC20") (pin "4") (pinfunction "S7_4") (pintype "output"))
      (node (ref "IC22") (pin "8") (pinfunction "I8_8") (pintype "input"))
    )
    (net (code "1169") (name "Net-(IC20A-S8)") (class "Default")
      (node (ref "IC20") (pin "18") (pinfunction "S8_18") (pintype "output"))
      (node (ref "IC21") (pin "1") (pinfunction "I1_1") (pintype "input"))
    )
    (net (code "1170") (name "Net-(IC20A-S9)") (class "Default")
      (node (ref "IC20") (pin "17") (pinfunction "S9_17") (pintype "output"))
      (node (ref "IC21") (pin "2") (pinfunction "I2_2") (pintype "input"))
    )
    (net (code "1171") (name "Net-(IC20A-S10)") (class "Default")
      (node (ref "IC20") (pin "20") (pinfunction "S10_20") (pintype "output"))
      (node (ref "IC21") (pin "3") (pinfunction "I3_3") (pintype "input"))
    )
    (net (code "1172") (name "Net-(IC20A-S11)") (class "Default")
      (node (ref "IC20") (pin "19") (pinfunction "S11_19") (pintype "output"))
      (node (ref "IC21") (pin "4") (pinfunction "I4_4") (pintype "input"))
    )
    (net (code "1173") (name "Net-(IC20A-S12)") (class "Default")
      (node (ref "IC20") (pin "14") (pinfunction "S12_14") (pintype "output"))
      (node (ref "IC21") (pin "5") (pinfunction "I5_5") (pintype "input"))
    )
    (net (code "1174") (name "Net-(IC20A-S13)") (class "Default")
      (node (ref "IC20") (pin "13") (pinfunction "S13_13") (pintype "output"))
      (node (ref "IC21") (pin "6") (pinfunction "I6_6") (pintype "input"))
    )
    (net (code "1175") (name "Net-(IC20A-S14)") (class "Default")
      (node (ref "IC20") (pin "16") (pinfunction "S14_16") (pintype "output"))
      (node (ref "IC21") (pin "7") (pinfunction "I7_7") (pintype "input"))
    )
    (net (code "1176") (name "Net-(IC20A-S15)") (class "Default")
      (node (ref "IC20") (pin "15") (pinfunction "S15_15") (pintype "output"))
      (node (ref "IC21") (pin "8") (pinfunction "I8_8") (pintype "input"))
    )
    (net (code "1177") (name "Net-(IC23A-S0)") (class "Default")
      (node (ref "IC23") (pin "11") (pinfunction "S0_11") (pintype "output"))
      (node (ref "IC25") (pin "1") (pinfunction "I1_1") (pintype "input"))
    )
    (net (code "1178") (name "Net-(IC23A-S1)") (class "Default")
      (node (ref "IC23") (pin "9") (pinfunction "S1_9") (pintype "output"))
      (node (ref "IC25") (pin "2") (pinfunction "I2_2") (pintype "input"))
    )
    (net (code "1179") (name "Net-(IC23A-S2)") (class "Default")
      (node (ref "IC23") (pin "10") (pinfunction "S2_10") (pintype "output"))
      (node (ref "IC25") (pin "3") (pinfunction "I3_3") (pintype "input"))
    )
    (net (code "1180") (name "Net-(IC23A-S3)") (class "Default")
      (node (ref "IC23") (pin "8") (pinfunction "S3_8") (pintype "output"))
      (node (ref "IC25") (pin "4") (pinfunction "I4_4") (pintype "input"))
    )
    (net (code "1181") (name "Net-(IC23A-S4)") (class "Default")
      (node (ref "IC23") (pin "7") (pinfunction "S4_7") (pintype "output"))
      (node (ref "IC25") (pin "5") (pinfunction "I5_5") (pintype "input"))
    )
    (net (code "1182") (name "Net-(IC23A-S5)") (class "Default")
      (node (ref "IC23") (pin "6") (pinfunction "S5_6") (pintype "output"))
      (node (ref "IC25") (pin "6") (pinfunction "I6_6") (pintype "input"))
    )
    (net (code "1183") (name "Net-(IC23A-S6)") (class "Default")
      (node (ref "IC23") (pin "5") (pinfunction "S6_5") (pintype "output"))
      (node (ref "IC25") (pin "7") (pinfunction "I7_7") (pintype "input"))
    )
    (net (code "1184") (name "Net-(IC23A-S7)") (class "Default")
      (node (ref "IC23") (pin "4") (pinfunction "S7_4") (pintype "output"))
      (node (ref "IC25") (pin "8") (pinfunction "I8_8") (pintype "input"))
    )
    (net (code "1185") (name "Net-(IC23A-S8)") (class "Default")
      (node (ref "IC23") (pin "18") (pinfunction "S8_18") (pintype "output"))
      (node (ref "IC24") (pin "1") (pinfunction "I1_1") (pintype "input"))
    )
    (net (code "1186") (name "Net-(IC23A-S9)") (class "Default")
      (node (ref "IC23") (pin "17") (pinfunction "S9_17") (pintype "output"))
      (node (ref "IC24") (pin "2") (pinfunction "I2_2") (pintype "input"))
    )
    (net (code "1187") (name "Net-(IC23A-S10)") (class "Default")
      (node (ref "IC23") (pin "20") (pinfunction "S10_20") (pintype "output"))
      (node (ref "IC24") (pin "3") (pinfunction "I3_3") (pintype "input"))
    )
    (net (code "1188") (name "Net-(IC23A-S11)") (class "Default")
      (node (ref "IC23") (pin "19") (pinfunction "S11_19") (pintype "output"))
      (node (ref "IC24") (pin "4") (pinfunction "I4_4") (pintype "input"))
    )
    (net (code "1189") (name "Net-(IC23A-S12)") (class "Default")
      (node (ref "IC23") (pin "14") (pinfunction "S12_14") (pintype "output"))
      (node (ref "IC24") (pin "5") (pinfunction "I5_5") (pintype "input"))
    )
    (net (code "1190") (name "Net-(IC23A-S13)") (class "Default")
      (node (ref "IC23") (pin "13") (pinfunction "S13_13") (pintype "output"))
      (node (ref "IC24") (pin "6") (pinfunction "I6_6") (pintype "input"))
    )
    (net (code "1191") (name "Net-(IC23A-S14)") (class "Default")
      (node (ref "IC23") (pin "16") (pinfunction "S14_16") (pintype "output"))
      (node (ref "IC24") (pin "7") (pinfunction "I7_7") (pintype "input"))
    )
    (net (code "1192") (name "Net-(IC23A-S15)") (class "Default")
      (node (ref "IC23") (pin "15") (pinfunction "S15_15") (pintype "output"))
      (node (ref "IC24") (pin "8") (pinfunction "I8_8") (pintype "input"))
    )
    (net (code "1193") (name "Net-(IC26A-S0)") (class "Default")
      (node (ref "IC26") (pin "11") (pinfunction "S0_11") (pintype "output"))
      (node (ref "IC28") (pin "1") (pinfunction "I1_1") (pintype "input"))
    )
    (net (code "1194") (name "Net-(IC26A-S1)") (class "Default")
      (node (ref "IC26") (pin "9") (pinfunction "S1_9") (pintype "output"))
      (node (ref "IC28") (pin "2") (pinfunction "I2_2") (pintype "input"))
    )
    (net (code "1195") (name "Net-(IC26A-S2)") (class "Default")
      (node (ref "IC26") (pin "10") (pinfunction "S2_10") (pintype "output"))
      (node (ref "IC28") (pin "3") (pinfunction "I3_3") (pintype "input"))
    )
    (net (code "1196") (name "Net-(IC26A-S3)") (class "Default")
      (node (ref "IC26") (pin "8") (pinfunction "S3_8") (pintype "output"))
      (node (ref "IC28") (pin "4") (pinfunction "I4_4") (pintype "input"))
    )
    (net (code "1197") (name "Net-(IC26A-S4)") (class "Default")
      (node (ref "IC26") (pin "7") (pinfunction "S4_7") (pintype "output"))
      (node (ref "IC28") (pin "5") (pinfunction "I5_5") (pintype "input"))
    )
    (net (code "1198") (name "Net-(IC26A-S5)") (class "Default")
      (node (ref "IC26") (pin "6") (pinfunction "S5_6") (pintype "output"))
      (node (ref "IC28") (pin "6") (pinfunction "I6_6") (pintype "input"))
    )
    (net (code "1199") (name "Net-(IC26A-S6)") (class "Default")
      (node (ref "IC26") (pin "5") (pinfunction "S6_5") (pintype "output"))
      (node (ref "IC28") (pin "7") (pinfunction "I7_7") (pintype "input"))
    )
    (net (code "1200") (name "Net-(IC26A-S7)") (class "Default")
      (node (ref "IC26") (pin "4") (pinfunction "S7_4") (pintype "output"))
      (node (ref "IC28") (pin "8") (pinfunction "I8_8") (pintype "input"))
    )
    (net (code "1201") (name "Net-(IC26A-S8)") (class "Default")
      (node (ref "IC26") (pin "18") (pinfunction "S8_18") (pintype "output"))
      (node (ref "IC27") (pin "1") (pinfunction "I1_1") (pintype "input"))
    )
    (net (code "1202") (name "Net-(IC26A-S9)") (class "Default")
      (node (ref "IC26") (pin "17") (pinfunction "S9_17") (pintype "output"))
      (node (ref "IC27") (pin "2") (pinfunction "I2_2") (pintype "input"))
    )
    (net (code "1203") (name "Net-(IC26A-S10)") (class "Default")
      (node (ref "IC26") (pin "20") (pinfunction "S10_20") (pintype "output"))
      (node (ref "IC27") (pin "3") (pinfunction "I3_3") (pintype "input"))
    )
    (net (code "1204") (name "Net-(IC26A-S11)") (class "Default")
      (node (ref "IC26") (pin "19") (pinfunction "S11_19") (pintype "output"))
      (node (ref "IC27") (pin "4") (pinfunction "I4_4") (pintype "input"))
    )
    (net (code "1205") (name "Net-(IC26A-S12)") (class "Default")
      (node (ref "IC26") (pin "14") (pinfunction "S12_14") (pintype "output"))
      (node (ref "IC27") (pin "5") (pinfunction "I5_5") (pintype "input"))
    )
    (net (code "1206") (name "Net-(IC26A-S13)") (class "Default")
      (node (ref "IC26") (pin "13") (pinfunction "S13_13") (pintype "output"))
      (node (ref "IC27") (pin "6") (pinfunction "I6_6") (pintype "input"))
    )
    (net (code "1207") (name "Net-(IC26A-S14)") (class "Default")
      (node (ref "IC26") (pin "16") (pinfunction "S14_16") (pintype "output"))
      (node (ref "IC27") (pin "7") (pinfunction "I7_7") (pintype "input"))
    )
    (net (code "1208") (name "Net-(IC26A-S15)") (class "Default")
      (node (ref "IC26") (pin "15") (pinfunction "S15_15") (pintype "output"))
      (node (ref "IC27") (pin "8") (pinfunction "I8_8") (pintype "input"))
    )
    (net (code "1209") (name "ROW1-8_INHIBIT") (class "Default")
      (node (ref "IC3") (pin "4") (pinfunction "Y0_4") (pintype "output"))
      (node (ref "IC5") (pin "23") (pinfunction "INH_23") (pintype "input"))
    )
    (net (code "1210") (name "ROW1_SINK") (class "Default")
      (node (ref "D1") (pin "1") (pinfunction "A1_1") (pintype "bidirectional"))
      (node (ref "D10") (pin "1") (pinfunction "A1_1") (pintype "bidirectional"))
      (node (ref "D11") (pin "1") (pinfunction "A1_1") (pintype "bidirectional"))
      (node (ref "D12") (pin "1") (pinfunction "A1_1") (pintype "bidirectional"))
      (node (ref "D13") (pin "1") (pinfunction "A1_1") (pintype "bidirectional"))
      (node (ref "D14") (pin "1") (pinfunction "A1_1") (pintype "bidirectional"))
      (node (ref "D15") (pin "1") (pinfunction "A1_1") (pintype "bidirectional"))
      (node (ref "D16") (pin "1") (pinfunction "A1_1") (pintype "bidirectional"))
      (node (ref "D17") (pin "1") (pinfunction "A1_1") (pintype "bidirectional"))
      (node (ref "D18") (pin "1") (pinfunction "A1_1") (pintype "bidirectional"))
      (node (ref "D19") (pin "1") (pinfunction "A1_1") (pintype "bidirectional"))
      (node (ref "D2") (pin "1") (pinfunction "A1_1") (pintype "bidirectional"))
      (node (ref "D20") (pin "1") (pinfunction "A1_1") (pintype "bidirectional"))
      (node (ref "D21") (pin "1") (pinfunction "A1_1") (pintype "bidirectional"))
      (node (ref "D22") (pin "1") (pinfunction "A1_1") (pintype "bidirectional"))
      (node (ref "D23") (pin "1") (pinfunction "A1_1") (pintype "bidirectional"))
      (node (ref "D24") (pin "1") (pinfunction "A1_1") (pintype "bidirectional"))
      (node (ref "D25") (pin "1") (pinfunction "A1_1") (pintype "bidirectional"))
      (node (ref "D26") (pin "1") (pinfunction "A1_1") (pintype "bidirectional"))
      (node (ref "D27") (pin "1") (pinfunction "A1_1") (pintype "bidirectional"))
      (node (ref "D28") (pin "1") (pinfunction "A1_1") (pintype "bidirectional"))
      (node (ref "D29") (pin "1") (pinfunction "A1_1") (pintype "bidirectional"))
      (node (ref "D3") (pin "1") (pinfunction "A1_1") (pintype "bidirectional"))
      (node (ref "D30") (pin "1") (pinfunction "A1_1") (pintype "bidirectional"))
      (node (ref "D31") (pin "1") (pinfunction "A1_1") (pintype "bidirectional"))
      (node (ref "D32") (pin "1") (pinfunction "A1_1") (pintype "bidirectional"))
      (node (ref "D4") (pin "1") (pinfunction "A1_1") (pintype "bidirectional"))
      (node (ref "D5") (pin "1") (pinfunction "A1_1") (pintype "bidirectional"))
      (node (ref "D6") (pin "1") (pinfunction "A1_1") (pintype "bidirectional"))
      (node (ref "D7") (pin "1") (pinfunction "A1_1") (pintype "bidirectional"))
      (node (ref "D8") (pin "1") (pinfunction "A1_1") (pintype "bidirectional"))
      (node (ref "D9") (pin "1") (pinfunction "A1_1") (pintype "bidirectional"))
      (node (ref "IC7") (pin "18") (pinfunction "O1_18") (pintype "open_collector"))
    )
    (net (code "1211") (name "ROW1_SOURCE") (class "Default")
      (node (ref "D1") (pin "2") (pinfunction "C2_2") (pintype "bidirectional"))
      (node (ref "D10") (pin "2") (pinfunction "C2_2") (pintype "bidirectional"))
      (node (ref "D11") (pin "2") (pinfunction "C2_2") (pintype "bidirectional"))
      (node (ref "D12") (pin "2") (pinfunction "C2_2") (pintype "bidirectional"))
      (node (ref "D13") (pin "2") (pinfunction "C2_2") (pintype "bidirectional"))
      (node (ref "D14") (pin "2") (pinfunction "C2_2") (pintype "bidirectional"))
      (node (ref "D15") (pin "2") (pinfunction "C2_2") (pintype "bidirectional"))
      (node (ref "D16") (pin "2") (pinfunction "C2_2") (pintype "bidirectional"))
      (node (ref "D17") (pin "2") (pinfunction "C2_2") (pintype "bidirectional"))
      (node (ref "D18") (pin "2") (pinfunction "C2_2") (pintype "bidirectional"))
      (node (ref "D19") (pin "2") (pinfunction "C2_2") (pintype "bidirectional"))
      (node (ref "D2") (pin "2") (pinfunction "C2_2") (pintype "bidirectional"))
      (node (ref "D20") (pin "2") (pinfunction "C2_2") (pintype "bidirectional"))
      (node (ref "D21") (pin "2") (pinfunction "C2_2") (pintype "bidirectional"))
      (node (ref "D22") (pin "2") (pinfunction "C2_2") (pintype "bidirectional"))
      (node (ref "D23") (pin "2") (pinfunction "C2_2") (pintype "bidirectional"))
      (node (ref "D24") (pin "2") (pinfunction "C2_2") (pintype "bidirectional"))
      (node (ref "D25") (pin "2") (pinfunction "C2_2") (pintype "bidirectional"))
      (node (ref "D26") (pin "2") (pinfunction "C2_2") (pintype "bidirectional"))
      (node (ref "D27") (pin "2") (pinfunction "C2_2") (pintype "bidirectional"))
      (node (ref "D28") (pin "2") (pinfunction "C2_2") (pintype "bidirectional"))
      (node (ref "D29") (pin "2") (pinfunction "C2_2") (pintype "bidirectional"))
      (node (ref "D3") (pin "2") (pinfunction "C2_2") (pintype "bidirectional"))
      (node (ref "D30") (pin "2") (pinfunction "C2_2") (pintype "bidirectional"))
      (node (ref "D31") (pin "2") (pinfunction "C2_2") (pintype "bidirectional"))
      (node (ref "D32") (pin "2") (pinfunction "C2_2") (pintype "bidirectional"))
      (node (ref "D4") (pin "2") (pinfunction "C2_2") (pintype "bidirectional"))
      (node (ref "D5") (pin "2") (pinfunction "C2_2") (pintype "bidirectional"))
      (node (ref "D6") (pin "2") (pinfunction "C2_2") (pintype "bidirectional"))
      (node (ref "D7") (pin "2") (pinfunction "C2_2") (pintype "bidirectional"))
      (node (ref "D8") (pin "2") (pinfunction "C2_2") (pintype "bidirectional"))
      (node (ref "D9") (pin "2") (pinfunction "C2_2") (pintype "bidirectional"))
      (node (ref "IC6") (pin "18") (pinfunction "O1_18") (pintype "open_collector"))
    )
    (net (code "1212") (name "ROW2_SINK") (class "Default")
      (node (ref "D33") (pin "1") (pinfunction "A1_1") (pintype "bidirectional"))
      (node (ref "D34") (pin "1") (pinfunction "A1_1") (pintype "bidirectional"))
      (node (ref "D35") (pin "1") (pinfunction "A1_1") (pintype "bidirectional"))
      (node (ref "D36") (pin "1") (pinfunction "A1_1") (pintype "bidirectional"))
      (node (ref "D37") (pin "1") (pinfunction "A1_1") (pintype "bidirectional"))
      (node (ref "D38") (pin "1") (pinfunction "A1_1") (pintype "bidirectional"))
      (node (ref "D39") (pin "1") (pinfunction "A1_1") (pintype "bidirectional"))
      (node (ref "D40") (pin "1") (pinfunction "A1_1") (pintype "bidirectional"))
      (node (ref "D41") (pin "1") (pinfunction "A1_1") (pintype "bidirectional"))
      (node (ref "D42") (pin "1") (pinfunction "A1_1") (pintype "bidirectional"))
      (node (ref "D43") (pin "1") (pinfunction "A1_1") (pintype "bidirectional"))
      (node (ref "D44") (pin "1") (pinfunction "A1_1") (pintype "bidirectional"))
      (node (ref "D45") (pin "1") (pinfunction "A1_1") (pintype "bidirectional"))
      (node (ref "D46") (pin "1") (pinfunction "A1_1") (pintype "bidirectional"))
      (node (ref "D47") (pin "1") (pinfunction "A1_1") (pintype "bidirectional"))
      (node (ref "D48") (pin "1") (pinfunction "A1_1") (pintype "bidirectional"))
      (node (ref "D49") (pin "1") (pinfunction "A1_1") (pintype "bidirectional"))
      (node (ref "D50") (pin "1") (pinfunction "A1_1") (pintype "bidirectional"))
      (node (ref "D51") (pin "1") (pinfunction "A1_1") (pintype "bidirectional"))
      (node (ref "D52") (pin "1") (pinfunction "A1_1") (pintype "bidirectional"))
      (node (ref "D53") (pin "1") (pinfunction "A1_1") (pintype "bidirectional"))
      (node (ref "D54") (pin "1") (pinfunction "A1_1") (pintype "bidirectional"))
      (node (ref "D55") (pin "1") (pinfunction "A1_1") (pintype "bidirectional"))
      (node (ref "D56") (pin "1") (pinfunction "A1_1") (pintype "bidirectional"))
      (node (ref "D57") (pin "1") (pinfunction "A1_1") (pintype "bidirectional"))
      (node (ref "D58") (pin "1") (pinfunction "A1_1") (pintype "bidirectional"))
      (node (ref "D59") (pin "1") (pinfunction "A1_1") (pintype "bidirectional"))
      (node (ref "D60") (pin "1") (pinfunction "A1_1") (pintype "bidirectional"))
      (node (ref "D61") (pin "1") (pinfunction "A1_1") (pintype "bidirectional"))
      (node (ref "D62") (pin "1") (pinfunction "A1_1") (pintype "bidirectional"))
      (node (ref "D63") (pin "1") (pinfunction "A1_1") (pintype "bidirectional"))
      (node (ref "D64") (pin "1") (pinfunction "A1_1") (pintype "bidirectional"))
      (node (ref "IC7") (pin "17") (pinfunction "O2_17") (pintype "open_collector"))
    )
    (net (code "1213") (name "ROW2_SOURCE") (class "Default")
      (node (ref "D33") (pin "2") (pinfunction "C2_2") (pintype "bidirectional"))
      (node (ref "D34") (pin "2") (pinfunction "C2_2") (pintype "bidirectional"))
      (node (ref "D35") (pin "2") (pinfunction "C2_2") (pintype "bidirectional"))
      (node (ref "D36") (pin "2") (pinfunction "C2_2") (pintype "bidirectional"))
      (node (ref "D37") (pin "2") (pinfunction "C2_2") (pintype "bidirectional"))
      (node (ref "D38") (pin "2") (pinfunction "C2_2") (pintype "bidirectional"))
      (node (ref "D39") (pin "2") (pinfunction "C2_2") (pintype "bidirectional"))
      (node (ref "D40") (pin "2") (pinfunction "C2_2") (pintype "bidirectional"))
      (node (ref "D41") (pin "2") (pinfunction "C2_2") (pintype "bidirectional"))
      (node (ref "D42") (pin "2") (pinfunction "C2_2") (pintype "bidirectional"))
      (node (ref "D43") (pin "2") (pinfunction "C2_2") (pintype "bidirectional"))
      (node (ref "D44") (pin "2") (pinfunction "C2_2") (pintype "bidirectional"))
      (node (ref "D45") (pin "2") (pinfunction "C2_2") (pintype "bidirectional"))
      (node (ref "D46") (pin "2") (pinfunction "C2_2") (pintype "bidirectional"))
      (node (ref "D47") (pin "2") (pinfunction "C2_2") (pintype "bidirectional"))
      (node (ref "D48") (pin "2") (pinfunction "C2_2") (pintype "bidirectional"))
      (node (ref "D49") (pin "2") (pinfunction "C2_2") (pintype "bidirectional"))
      (node (ref "D50") (pin "2") (pinfunction "C2_2") (pintype "bidirectional"))
      (node (ref "D51") (pin "2") (pinfunction "C2_2") (pintype "bidirectional"))
      (node (ref "D52") (pin "2") (pinfunction "C2_2") (pintype "bidirectional"))
      (node (ref "D53") (pin "2") (pinfunction "C2_2") (pintype "bidirectional"))
      (node (ref "D54") (pin "2") (pinfunction "C2_2") (pintype "bidirectional"))
      (node (ref "D55") (pin "2") (pinfunction "C2_2") (pintype "bidirectional"))
      (node (ref "D56") (pin "2") (pinfunction "C2_2") (pintype "bidirectional"))
      (node (ref "D57") (pin "2") (pinfunction "C2_2") (pintype "bidirectional"))
      (node (ref "D58") (pin "2") (pinfunction "C2_2") (pintype "bidirectional"))
      (node (ref "D59") (pin "2") (pinfunction "C2_2") (pintype "bidirectional"))
      (node (ref "D60") (pin "2") (pinfunction "C2_2") (pintype "bidirectional"))
      (node (ref "D61") (pin "2") (pinfunction "C2_2") (pintype "bidirectional"))
      (node (ref "D62") (pin "2") (pinfunction "C2_2") (pintype "bidirectional"))
      (node (ref "D63") (pin "2") (pinfunction "C2_2") (pintype "bidirectional"))
      (node (ref "D64") (pin "2") (pinfunction "C2_2") (pintype "bidirectional"))
      (node (ref "IC6") (pin "17") (pinfunction "O2_17") (pintype "open_collector"))
    )
    (net (code "1214") (name "ROW3_SINK") (class "Default")
      (node (ref "D65") (pin "1") (pinfunction "A1_1") (pintype "bidirectional"))
      (node (ref "D66") (pin "1") (pinfunction "A1_1") (pintype "bidirectional"))
      (node (ref "D67") (pin "1") (pinfunction "A1_1") (pintype "bidirectional"))
      (node (ref "D68") (pin "1") (pinfunction "A1_1") (pintype "bidirectional"))
      (node (ref "D69") (pin "1") (pinfunction "A1_1") (pintype "bidirectional"))
      (node (ref "D70") (pin "1") (pinfunction "A1_1") (pintype "bidirectional"))
      (node (ref "D71") (pin "1") (pinfunction "A1_1") (pintype "bidirectional"))
      (node (ref "D72") (pin "1") (pinfunction "A1_1") (pintype "bidirectional"))
      (node (ref "D73") (pin "1") (pinfunction "A1_1") (pintype "bidirectional"))
      (node (ref "D74") (pin "1") (pinfunction "A1_1") (pintype "bidirectional"))
      (node (ref "D75") (pin "1") (pinfunction "A1_1") (pintype "bidirectional"))
      (node (ref "D76") (pin "1") (pinfunction "A1_1") (pintype "bidirectional"))
      (node (ref "D77") (pin "1") (pinfunction "A1_1") (pintype "bidirectional"))
      (node (ref "D78") (pin "1") (pinfunction "A1_1") (pintype "bidirectional"))
      (node (ref "D79") (pin "1") (pinfunction "A1_1") (pintype "bidirectional"))
      (node (ref "D80") (pin "1") (pinfunction "A1_1") (pintype "bidirectional"))
      (node (ref "D81") (pin "1") (pinfunction "A1_1") (pintype "bidirectional"))
      (node (ref "D82") (pin "1") (pinfunction "A1_1") (pintype "bidirectional"))
      (node (ref "D83") (pin "1") (pinfunction "A1_1") (pintype "bidirectional"))
      (node (ref "D84") (pin "1") (pinfunction "A1_1") (pintype "bidirectional"))
      (node (ref "D85") (pin "1") (pinfunction "A1_1") (pintype "bidirectional"))
      (node (ref "D86") (pin "1") (pinfunction "A1_1") (pintype "bidirectional"))
      (node (ref "D87") (pin "1") (pinfunction "A1_1") (pintype "bidirectional"))
      (node (ref "D88") (pin "1") (pinfunction "A1_1") (pintype "bidirectional"))
      (node (ref "D89") (pin "1") (pinfunction "A1_1") (pintype "bidirectional"))
      (node (ref "D90") (pin "1") (pinfunction "A1_1") (pintype "bidirectional"))
      (node (ref "D91") (pin "1") (pinfunction "A1_1") (pintype "bidirectional"))
      (node (ref "D92") (pin "1") (pinfunction "A1_1") (pintype "bidirectional"))
      (node (ref "D93") (pin "1") (pinfunction "A1_1") (pintype "bidirectional"))
      (node (ref "D94") (pin "1") (pinfunction "A1_1") (pintype "bidirectional"))
      (node (ref "D95") (pin "1") (pinfunction "A1_1") (pintype "bidirectional"))
      (node (ref "D96") (pin "1") (pinfunction "A1_1") (pintype "bidirectional"))
      (node (ref "IC7") (pin "16") (pinfunction "O3_16") (pintype "open_collector"))
    )
    (net (code "1215") (name "ROW3_SOURCE") (class "Default")
      (node (ref "D65") (pin "2") (pinfunction "C2_2") (pintype "bidirectional"))
      (node (ref "D66") (pin "2") (pinfunction "C2_2") (pintype "bidirectional"))
      (node (ref "D67") (pin "2") (pinfunction "C2_2") (pintype "bidirectional"))
      (node (ref "D68") (pin "2") (pinfunction "C2_2") (pintype "bidirectional"))
      (node (ref "D69") (pin "2") (pinfunction "C2_2") (pintype "bidirectional"))
      (node (ref "D70") (pin "2") (pinfunction "C2_2") (pintype "bidirectional"))
      (node (ref "D71") (pin "2") (pinfunction "C2_2") (pintype "bidirectional"))
      (node (ref "D72") (pin "2") (pinfunction "C2_2") (pintype "bidirectional"))
      (node (ref "D73") (pin "2") (pinfunction "C2_2") (pintype "bidirectional"))
      (node (ref "D74") (pin "2") (pinfunction "C2_2") (pintype "bidirectional"))
      (node (ref "D75") (pin "2") (pinfunction "C2_2") (pintype "bidirectional"))
      (node (ref "D76") (pin "2") (pinfunction "C2_2") (pintype "bidirectional"))
      (node (ref "D77") (pin "2") (pinfunction "C2_2") (pintype "bidirectional"))
      (node (ref "D78") (pin "2") (pinfunction "C2_2") (pintype "bidirectional"))
      (node (ref "D79") (pin "2") (pinfunction "C2_2") (pintype "bidirectional"))
      (node (ref "D80") (pin "2") (pinfunction "C2_2") (pintype "bidirectional"))
      (node (ref "D81") (pin "2") (pinfunction "C2_2") (pintype "bidirectional"))
      (node (ref "D82") (pin "2") (pinfunction "C2_2") (pintype "bidirectional"))
      (node (ref "D83") (pin "2") (pinfunction "C2_2") (pintype "bidirectional"))
      (node (ref "D84") (pin "2") (pinfunction "C2_2") (pintype "bidirectional"))
      (node (ref "D85") (pin "2") (pinfunction "C2_2") (pintype "bidirectional"))
      (node (ref "D86") (pin "2") (pinfunction "C2_2") (pintype "bidirectional"))
      (node (ref "D87") (pin "2") (pinfunction "C2_2") (pintype "bidirectional"))
      (node (ref "D88") (pin "2") (pinfunction "C2_2") (pintype "bidirectional"))
      (node (ref "D89") (pin "2") (pinfunction "C2_2") (pintype "bidirectional"))
      (node (ref "D90") (pin "2") (pinfunction "C2_2") (pintype "bidirectional"))
      (node (ref "D91") (pin "2") (pinfunction "C2_2") (pintype "bidirectional"))
      (node (ref "D92") (pin "2") (pinfunction "C2_2") (pintype "bidirectional"))
      (node (ref "D93") (pin "2") (pinfunction "C2_2") (pintype "bidirectional"))
      (node (ref "D94") (pin "2") (pinfunction "C2_2") (pintype "bidirectional"))
      (node (ref "D95") (pin "2") (pinfunction "C2_2") (pintype "bidirectional"))
      (node (ref "D96") (pin "2") (pinfunction "C2_2") (pintype "bidirectional"))
      (node (ref "IC6") (pin "16") (pinfunction "O3_16") (pintype "open_collector"))
    )
    (net (code "1216") (name "ROW4_SINK") (class "Default")
      (node (ref "D100") (pin "1") (pinfunction "A1_1") (pintype "bidirectional"))
      (node (ref "D101") (pin "1") (pinfunction "A1_1") (pintype "bidirectional"))
      (node (ref "D102") (pin "1") (pinfunction "A1_1") (pintype "bidirectional"))
      (node (ref "D103") (pin "1") (pinfunction "A1_1") (pintype "bidirectional"))
      (node (ref "D104") (pin "1") (pinfunction "A1_1") (pintype "bidirectional"))
      (node (ref "D105") (pin "1") (pinfunction "A1_1") (pintype "bidirectional"))
      (node (ref "D106") (pin "1") (pinfunction "A1_1") (pintype "bidirectional"))
      (node (ref "D107") (pin "1") (pinfunction "A1_1") (pintype "bidirectional"))
      (node (ref "D108") (pin "1") (pinfunction "A1_1") (pintype "bidirectional"))
      (node (ref "D109") (pin "1") (pinfunction "A1_1") (pintype "bidirectional"))
      (node (ref "D110") (pin "1") (pinfunction "A1_1") (pintype "bidirectional"))
      (node (ref "D111") (pin "1") (pinfunction "A1_1") (pintype "bidirectional"))
      (node (ref "D112") (pin "1") (pinfunction "A1_1") (pintype "bidirectional"))
      (node (ref "D113") (pin "1") (pinfunction "A1_1") (pintype "bidirectional"))
      (node (ref "D114") (pin "1") (pinfunction "A1_1") (pintype "bidirectional"))
      (node (ref "D115") (pin "1") (pinfunction "A1_1") (pintype "bidirectional"))
      (node (ref "D116") (pin "1") (pinfunction "A1_1") (pintype "bidirectional"))
      (node (ref "D117") (pin "1") (pinfunction "A1_1") (pintype "bidirectional"))
      (node (ref "D118") (pin "1") (pinfunction "A1_1") (pintype "bidirectional"))
      (node (ref "D119") (pin "1") (pinfunction "A1_1") (pintype "bidirectional"))
      (node (ref "D120") (pin "1") (pinfunction "A1_1") (pintype "bidirectional"))
      (node (ref "D121") (pin "1") (pinfunction "A1_1") (pintype "bidirectional"))
      (node (ref "D122") (pin "1") (pinfunction "A1_1") (pintype "bidirectional"))
      (node (ref "D123") (pin "1") (pinfunction "A1_1") (pintype "bidirectional"))
      (node (ref "D124") (pin "1") (pinfunction "A1_1") (pintype "bidirectional"))
      (node (ref "D125") (pin "1") (pinfunction "A1_1") (pintype "bidirectional"))
      (node (ref "D126") (pin "1") (pinfunction "A1_1") (pintype "bidirectional"))
      (node (ref "D127") (pin "1") (pinfunction "A1_1") (pintype "bidirectional"))
      (node (ref "D128") (pin "1") (pinfunction "A1_1") (pintype "bidirectional"))
      (node (ref "D97") (pin "1") (pinfunction "A1_1") (pintype "bidirectional"))
      (node (ref "D98") (pin "1") (pinfunction "A1_1") (pintype "bidirectional"))
      (node (ref "D99") (pin "1") (pinfunction "A1_1") (pintype "bidirectional"))
      (node (ref "IC7") (pin "15") (pinfunction "O4_15") (pintype "open_collector"))
    )
    (net (code "1217") (name "ROW4_SOURCE") (class "Default")
      (node (ref "D100") (pin "2") (pinfunction "C2_2") (pintype "bidirectional"))
      (node (ref "D101") (pin "2") (pinfunction "C2_2") (pintype "bidirectional"))
      (node (ref "D102") (pin "2") (pinfunction "C2_2") (pintype "bidirectional"))
      (node (ref "D103") (pin "2") (pinfunction "C2_2") (pintype "bidirectional"))
      (node (ref "D104") (pin "2") (pinfunction "C2_2") (pintype "bidirectional"))
      (node (ref "D105") (pin "2") (pinfunction "C2_2") (pintype "bidirectional"))
      (node (ref "D106") (pin "2") (pinfunction "C2_2") (pintype "bidirectional"))
      (node (ref "D107") (pin "2") (pinfunction "C2_2") (pintype "bidirectional"))
      (node (ref "D108") (pin "2") (pinfunction "C2_2") (pintype "bidirectional"))
      (node (ref "D109") (pin "2") (pinfunction "C2_2") (pintype "bidirectional"))
      (node (ref "D110") (pin "2") (pinfunction "C2_2") (pintype "bidirectional"))
      (node (ref "D111") (pin "2") (pinfunction "C2_2") (pintype "bidirectional"))
      (node (ref "D112") (pin "2") (pinfunction "C2_2") (pintype "bidirectional"))
      (node (ref "D113") (pin "2") (pinfunction "C2_2") (pintype "bidirectional"))
      (node (ref "D114") (pin "2") (pinfunction "C2_2") (pintype "bidirectional"))
      (node (ref "D115") (pin "2") (pinfunction "C2_2") (pintype "bidirectional"))
      (node (ref "D116") (pin "2") (pinfunction "C2_2") (pintype "bidirectional"))
      (node (ref "D117") (pin "2") (pinfunction "C2_2") (pintype "bidirectional"))
      (node (ref "D118") (pin "2") (pinfunction "C2_2") (pintype "bidirectional"))
      (node (ref "D119") (pin "2") (pinfunction "C2_2") (pintype "bidirectional"))
      (node (ref "D120") (pin "2") (pinfunction "C2_2") (pintype "bidirectional"))
      (node (ref "D121") (pin "2") (pinfunction "C2_2") (pintype "bidirectional"))
      (node (ref "D122") (pin "2") (pinfunction "C2_2") (pintype "bidirectional"))
      (node (ref "D123") (pin "2") (pinfunction "C2_2") (pintype "bidirectional"))
      (node (ref "D124") (pin "2") (pinfunction "C2_2") (pintype "bidirectional"))
      (node (ref "D125") (pin "2") (pinfunction "C2_2") (pintype "bidirectional"))
      (node (ref "D126") (pin "2") (pinfunction "C2_2") (pintype "bidirectional"))
      (node (ref "D127") (pin "2") (pinfunction "C2_2") (pintype "bidirectional"))
      (node (ref "D128") (pin "2") (pinfunction "C2_2") (pintype "bidirectional"))
      (node (ref "D97") (pin "2") (pinfunction "C2_2") (pintype "bidirectional"))
      (node (ref "D98") (pin "2") (pinfunction "C2_2") (pintype "bidirectional"))
      (node (ref "D99") (pin "2") (pinfunction "C2_2") (pintype "bidirectional"))
      (node (ref "IC6") (pin "15") (pinfunction "O4_15") (pintype "open_collector"))
    )
    (net (code "1218") (name "ROW5_SINK") (class "Default")
      (node (ref "D129") (pin "1") (pinfunction "A1_1") (pintype "bidirectional"))
      (node (ref "D130") (pin "1") (pinfunction "A1_1") (pintype "bidirectional"))
      (node (ref "D131") (pin "1") (pinfunction "A1_1") (pintype "bidirectional"))
      (node (ref "D132") (pin "1") (pinfunction "A1_1") (pintype "bidirectional"))
      (node (ref "D133") (pin "1") (pinfunction "A1_1") (pintype "bidirectional"))
      (node (ref "D134") (pin "1") (pinfunction "A1_1") (pintype "bidirectional"))
      (node (ref "D135") (pin "1") (pinfunction "A1_1") (pintype "bidirectional"))
      (node (ref "D136") (pin "1") (pinfunction "A1_1") (pintype "bidirectional"))
      (node (ref "D137") (pin "1") (pinfunction "A1_1") (pintype "bidirectional"))
      (node (ref "D138") (pin "1") (pinfunction "A1_1") (pintype "bidirectional"))
      (node (ref "D139") (pin "1") (pinfunction "A1_1") (pintype "bidirectional"))
      (node (ref "D140") (pin "1") (pinfunction "A1_1") (pintype "bidirectional"))
      (node (ref "D141") (pin "1") (pinfunction "A1_1") (pintype "bidirectional"))
      (node (ref "D142") (pin "1") (pinfunction "A1_1") (pintype "bidirectional"))
      (node (ref "D143") (pin "1") (pinfunction "A1_1") (pintype "bidirectional"))
      (node (ref "D144") (pin "1") (pinfunction "A1_1") (pintype "bidirectional"))
      (node (ref "D145") (pin "1") (pinfunction "A1_1") (pintype "bidirectional"))
      (node (ref "D146") (pin "1") (pinfunction "A1_1") (pintype "bidirectional"))
      (node (ref "D147") (pin "1") (pinfunction "A1_1") (pintype "bidirectional"))
      (node (ref "D148") (pin "1") (pinfunction "A1_1") (pintype "bidirectional"))
      (node (ref "D149") (pin "1") (pinfunction "A1_1") (pintype "bidirectional"))
      (node (ref "D150") (pin "1") (pinfunction "A1_1") (pintype "bidirectional"))
      (node (ref "D151") (pin "1") (pinfunction "A1_1") (pintype "bidirectional"))
      (node (ref "D152") (pin "1") (pinfunction "A1_1") (pintype "bidirectional"))
      (node (ref "D153") (pin "1") (pinfunction "A1_1") (pintype "bidirectional"))
      (node (ref "D154") (pin "1") (pinfunction "A1_1") (pintype "bidirectional"))
      (node (ref "D155") (pin "1") (pinfunction "A1_1") (pintype "bidirectional"))
      (node (ref "D156") (pin "1") (pinfunction "A1_1") (pintype "bidirectional"))
      (node (ref "D157") (pin "1") (pinfunction "A1_1") (pintype "bidirectional"))
      (node (ref "D158") (pin "1") (pinfunction "A1_1") (pintype "bidirectional"))
      (node (ref "D159") (pin "1") (pinfunction "A1_1") (pintype "bidirectional"))
      (node (ref "D160") (pin "1") (pinfunction "A1_1") (pintype "bidirectional"))
      (node (ref "IC7") (pin "14") (pinfunction "O5_14") (pintype "open_collector"))
    )
    (net (code "1219") (name "ROW5_SOURCE") (class "Default")
      (node (ref "D129") (pin "2") (pinfunction "C2_2") (pintype "bidirectional"))
      (node (ref "D130") (pin "2") (pinfunction "C2_2") (pintype "bidirectional"))
      (node (ref "D131") (pin "2") (pinfunction "C2_2") (pintype "bidirectional"))
      (node (ref "D132") (pin "2") (pinfunction "C2_2") (pintype "bidirectional"))
      (node (ref "D133") (pin "2") (pinfunction "C2_2") (pintype "bidirectional"))
      (node (ref "D134") (pin "2") (pinfunction "C2_2") (pintype "bidirectional"))
      (node (ref "D135") (pin "2") (pinfunction "C2_2") (pintype "bidirectional"))
      (node (ref "D136") (pin "2") (pinfunction "C2_2") (pintype "bidirectional"))
      (node (ref "D137") (pin "2") (pinfunction "C2_2") (pintype "bidirectional"))
      (node (ref "D138") (pin "2") (pinfunction "C2_2") (pintype "bidirectional"))
      (node (ref "D139") (pin "2") (pinfunction "C2_2") (pintype "bidirectional"))
      (node (ref "D140") (pin "2") (pinfunction "C2_2") (pintype "bidirectional"))
      (node (ref "D141") (pin "2") (pinfunction "C2_2") (pintype "bidirectional"))
      (node (ref "D142") (pin "2") (pinfunction "C2_2") (pintype "bidirectional"))
      (node (ref "D143") (pin "2") (pinfunction "C2_2") (pintype "bidirectional"))
      (node (ref "D144") (pin "2") (pinfunction "C2_2") (pintype "bidirectional"))
      (node (ref "D145") (pin "2") (pinfunction "C2_2") (pintype "bidirectional"))
      (node (ref "D146") (pin "2") (pinfunction "C2_2") (pintype "bidirectional"))
      (node (ref "D147") (pin "2") (pinfunction "C2_2") (pintype "bidirectional"))
      (node (ref "D148") (pin "2") (pinfunction "C2_2") (pintype "bidirectional"))
      (node (ref "D149") (pin "2") (pinfunction "C2_2") (pintype "bidirectional"))
      (node (ref "D150") (pin "2") (pinfunction "C2_2") (pintype "bidirectional"))
      (node (ref "D151") (pin "2") (pinfunction "C2_2") (pintype "bidirectional"))
      (node (ref "D152") (pin "2") (pinfunction "C2_2") (pintype "bidirectional"))
      (node (ref "D153") (pin "2") (pinfunction "C2_2") (pintype "bidirectional"))
      (node (ref "D154") (pin "2") (pinfunction "C2_2") (pintype "bidirectional"))
      (node (ref "D155") (pin "2") (pinfunction "C2_2") (pintype "bidirectional"))
      (node (ref "D156") (pin "2") (pinfunction "C2_2") (pintype "bidirectional"))
      (node (ref "D157") (pin "2") (pinfunction "C2_2") (pintype "bidirectional"))
      (node (ref "D158") (pin "2") (pinfunction "C2_2") (pintype "bidirectional"))
      (node (ref "D159") (pin "2") (pinfunction "C2_2") (pintype "bidirectional"))
      (node (ref "D160") (pin "2") (pinfunction "C2_2") (pintype "bidirectional"))
      (node (ref "IC6") (pin "14") (pinfunction "O5_14") (pintype "open_collector"))
    )
    (net (code "1220") (name "ROW6_SINK") (class "Default")
      (node (ref "D161") (pin "1") (pinfunction "A1_1") (pintype "bidirectional"))
      (node (ref "D162") (pin "1") (pinfunction "A1_1") (pintype "bidirectional"))
      (node (ref "D163") (pin "1") (pinfunction "A1_1") (pintype "bidirectional"))
      (node (ref "D164") (pin "1") (pinfunction "A1_1") (pintype "bidirectional"))
      (node (ref "D165") (pin "1") (pinfunction "A1_1") (pintype "bidirectional"))
      (node (ref "D166") (pin "1") (pinfunction "A1_1") (pintype "bidirectional"))
      (node (ref "D167") (pin "1") (pinfunction "A1_1") (pintype "bidirectional"))
      (node (ref "D168") (pin "1") (pinfunction "A1_1") (pintype "bidirectional"))
      (node (ref "D169") (pin "1") (pinfunction "A1_1") (pintype "bidirectional"))
      (node (ref "D170") (pin "1") (pinfunction "A1_1") (pintype "bidirectional"))
      (node (ref "D171") (pin "1") (pinfunction "A1_1") (pintype "bidirectional"))
      (node (ref "D172") (pin "1") (pinfunction "A1_1") (pintype "bidirectional"))
      (node (ref "D173") (pin "1") (pinfunction "A1_1") (pintype "bidirectional"))
      (node (ref "D174") (pin "1") (pinfunction "A1_1") (pintype "bidirectional"))
      (node (ref "D175") (pin "1") (pinfunction "A1_1") (pintype "bidirectional"))
      (node (ref "D176") (pin "1") (pinfunction "A1_1") (pintype "bidirectional"))
      (node (ref "D177") (pin "1") (pinfunction "A1_1") (pintype "bidirectional"))
      (node (ref "D178") (pin "1") (pinfunction "A1_1") (pintype "bidirectional"))
      (node (ref "D179") (pin "1") (pinfunction "A1_1") (pintype "bidirectional"))
      (node (ref "D180") (pin "1") (pinfunction "A1_1") (pintype "bidirectional"))
      (node (ref "D181") (pin "1") (pinfunction "A1_1") (pintype "bidirectional"))
      (node (ref "D182") (pin "1") (pinfunction "A1_1") (pintype "bidirectional"))
      (node (ref "D183") (pin "1") (pinfunction "A1_1") (pintype "bidirectional"))
      (node (ref "D184") (pin "1") (pinfunction "A1_1") (pintype "bidirectional"))
      (node (ref "D185") (pin "1") (pinfunction "A1_1") (pintype "bidirectional"))
      (node (ref "D186") (pin "1") (pinfunction "A1_1") (pintype "bidirectional"))
      (node (ref "D187") (pin "1") (pinfunction "A1_1") (pintype "bidirectional"))
      (node (ref "D188") (pin "1") (pinfunction "A1_1") (pintype "bidirectional"))
      (node (ref "D189") (pin "1") (pinfunction "A1_1") (pintype "bidirectional"))
      (node (ref "D190") (pin "1") (pinfunction "A1_1") (pintype "bidirectional"))
      (node (ref "D191") (pin "1") (pinfunction "A1_1") (pintype "bidirectional"))
      (node (ref "D192") (pin "1") (pinfunction "A1_1") (pintype "bidirectional"))
      (node (ref "IC7") (pin "13") (pinfunction "O6_13") (pintype "open_collector"))
    )
    (net (code "1221") (name "ROW6_SOURCE") (class "Default")
      (node (ref "D161") (pin "2") (pinfunction "C2_2") (pintype "bidirectional"))
      (node (ref "D162") (pin "2") (pinfunction "C2_2") (pintype "bidirectional"))
      (node (ref "D163") (pin "2") (pinfunction "C2_2") (pintype "bidirectional"))
      (node (ref "D164") (pin "2") (pinfunction "C2_2") (pintype "bidirectional"))
      (node (ref "D165") (pin "2") (pinfunction "C2_2") (pintype "bidirectional"))
      (node (ref "D166") (pin "2") (pinfunction "C2_2") (pintype "bidirectional"))
      (node (ref "D167") (pin "2") (pinfunction "C2_2") (pintype "bidirectional"))
      (node (ref "D168") (pin "2") (pinfunction "C2_2") (pintype "bidirectional"))
      (node (ref "D169") (pin "2") (pinfunction "C2_2") (pintype "bidirectional"))
      (node (ref "D170") (pin "2") (pinfunction "C2_2") (pintype "bidirectional"))
      (node (ref "D171") (pin "2") (pinfunction "C2_2") (pintype "bidirectional"))
      (node (ref "D172") (pin "2") (pinfunction "C2_2") (pintype "bidirectional"))
      (node (ref "D173") (pin "2") (pinfunction "C2_2") (pintype "bidirectional"))
      (node (ref "D174") (pin "2") (pinfunction "C2_2") (pintype "bidirectional"))
      (node (ref "D175") (pin "2") (pinfunction "C2_2") (pintype "bidirectional"))
      (node (ref "D176") (pin "2") (pinfunction "C2_2") (pintype "bidirectional"))
      (node (ref "D177") (pin "2") (pinfunction "C2_2") (pintype "bidirectional"))
      (node (ref "D178") (pin "2") (pinfunction "C2_2") (pintype "bidirectional"))
      (node (ref "D179") (pin "2") (pinfunction "C2_2") (pintype "bidirectional"))
      (node (ref "D180") (pin "2") (pinfunction "C2_2") (pintype "bidirectional"))
      (node (ref "D181") (pin "2") (pinfunction "C2_2") (pintype "bidirectional"))
      (node (ref "D182") (pin "2") (pinfunction "C2_2") (pintype "bidirectional"))
      (node (ref "D183") (pin "2") (pinfunction "C2_2") (pintype "bidirectional"))
      (node (ref "D184") (pin "2") (pinfunction "C2_2") (pintype "bidirectional"))
      (node (ref "D185") (pin "2") (pinfunction "C2_2") (pintype "bidirectional"))
      (node (ref "D186") (pin "2") (pinfunction "C2_2") (pintype "bidirectional"))
      (node (ref "D187") (pin "2") (pinfunction "C2_2") (pintype "bidirectional"))
      (node (ref "D188") (pin "2") (pinfunction "C2_2") (pintype "bidirectional"))
      (node (ref "D189") (pin "2") (pinfunction "C2_2") (pintype "bidirectional"))
      (node (ref "D190") (pin "2") (pinfunction "C2_2") (pintype "bidirectional"))
      (node (ref "D191") (pin "2") (pinfunction "C2_2") (pintype "bidirectional"))
      (node (ref "D192") (pin "2") (pinfunction "C2_2") (pintype "bidirectional"))
      (node (ref "IC6") (pin "13") (pinfunction "O6_13") (pintype "open_collector"))
    )
    (net (code "1222") (name "ROW7_SINK") (class "Default")
      (node (ref "D193") (pin "1") (pinfunction "A1_1") (pintype "bidirectional"))
      (node (ref "D194") (pin "1") (pinfunction "A1_1") (pintype "bidirectional"))
      (node (ref "D195") (pin "1") (pinfunction "A1_1") (pintype "bidirectional"))
      (node (ref "D196") (pin "1") (pinfunction "A1_1") (pintype "bidirectional"))
      (node (ref "D197") (pin "1") (pinfunction "A1_1") (pintype "bidirectional"))
      (node (ref "D198") (pin "1") (pinfunction "A1_1") (pintype "bidirectional"))
      (node (ref "D199") (pin "1") (pinfunction "A1_1") (pintype "bidirectional"))
      (node (ref "D200") (pin "1") (pinfunction "A1_1") (pintype "bidirectional"))
      (node (ref "D201") (pin "1") (pinfunction "A1_1") (pintype "bidirectional"))
      (node (ref "D202") (pin "1") (pinfunction "A1_1") (pintype "bidirectional"))
      (node (ref "D203") (pin "1") (pinfunction "A1_1") (pintype "bidirectional"))
      (node (ref "D204") (pin "1") (pinfunction "A1_1") (pintype "bidirectional"))
      (node (ref "D205") (pin "1") (pinfunction "A1_1") (pintype "bidirectional"))
      (node (ref "D206") (pin "1") (pinfunction "A1_1") (pintype "bidirectional"))
      (node (ref "D207") (pin "1") (pinfunction "A1_1") (pintype "bidirectional"))
      (node (ref "D208") (pin "1") (pinfunction "A1_1") (pintype "bidirectional"))
      (node (ref "D209") (pin "1") (pinfunction "A1_1") (pintype "bidirectional"))
      (node (ref "D210") (pin "1") (pinfunction "A1_1") (pintype "bidirectional"))
      (node (ref "D211") (pin "1") (pinfunction "A1_1") (pintype "bidirectional"))
      (node (ref "D212") (pin "1") (pinfunction "A1_1") (pintype "bidirectional"))
      (node (ref "D213") (pin "1") (pinfunction "A1_1") (pintype "bidirectional"))
      (node (ref "D214") (pin "1") (pinfunction "A1_1") (pintype "bidirectional"))
      (node (ref "D215") (pin "1") (pinfunction "A1_1") (pintype "bidirectional"))
      (node (ref "D216") (pin "1") (pinfunction "A1_1") (pintype "bidirectional"))
      (node (ref "D217") (pin "1") (pinfunction "A1_1") (pintype "bidirectional"))
      (node (ref "D218") (pin "1") (pinfunction "A1_1") (pintype "bidirectional"))
      (node (ref "D219") (pin "1") (pinfunction "A1_1") (pintype "bidirectional"))
      (node (ref "D220") (pin "1") (pinfunction "A1_1") (pintype "bidirectional"))
      (node (ref "D221") (pin "1") (pinfunction "A1_1") (pintype "bidirectional"))
      (node (ref "D222") (pin "1") (pinfunction "A1_1") (pintype "bidirectional"))
      (node (ref "D223") (pin "1") (pinfunction "A1_1") (pintype "bidirectional"))
      (node (ref "D224") (pin "1") (pinfunction "A1_1") (pintype "bidirectional"))
      (node (ref "IC7") (pin "12") (pinfunction "O7_12") (pintype "open_collector"))
    )
    (net (code "1223") (name "ROW7_SOURCE") (class "Default")
      (node (ref "D193") (pin "2") (pinfunction "C2_2") (pintype "bidirectional"))
      (node (ref "D194") (pin "2") (pinfunction "C2_2") (pintype "bidirectional"))
      (node (ref "D195") (pin "2") (pinfunction "C2_2") (pintype "bidirectional"))
      (node (ref "D196") (pin "2") (pinfunction "C2_2") (pintype "bidirectional"))
      (node (ref "D197") (pin "2") (pinfunction "C2_2") (pintype "bidirectional"))
      (node (ref "D198") (pin "2") (pinfunction "C2_2") (pintype "bidirectional"))
      (node (ref "D199") (pin "2") (pinfunction "C2_2") (pintype "bidirectional"))
      (node (ref "D200") (pin "2") (pinfunction "C2_2") (pintype "bidirectional"))
      (node (ref "D201") (pin "2") (pinfunction "C2_2") (pintype "bidirectional"))
      (node (ref "D202") (pin "2") (pinfunction "C2_2") (pintype "bidirectional"))
      (node (ref "D203") (pin "2") (pinfunction "C2_2") (pintype "bidirectional"))
      (node (ref "D204") (pin "2") (pinfunction "C2_2") (pintype "bidirectional"))
      (node (ref "D205") (pin "2") (pinfunction "C2_2") (pintype "bidirectional"))
      (node (ref "D206") (pin "2") (pinfunction "C2_2") (pintype "bidirectional"))
      (node (ref "D207") (pin "2") (pinfunction "C2_2") (pintype "bidirectional"))
      (node (ref "D208") (pin "2") (pinfunction "C2_2") (pintype "bidirectional"))
      (node (ref "D209") (pin "2") (pinfunction "C2_2") (pintype "bidirectional"))
      (node (ref "D210") (pin "2") (pinfunction "C2_2") (pintype "bidirectional"))
      (node (ref "D211") (pin "2") (pinfunction "C2_2") (pintype "bidirectional"))
      (node (ref "D212") (pin "2") (pinfunction "C2_2") (pintype "bidirectional"))
      (node (ref "D213") (pin "2") (pinfunction "C2_2") (pintype "bidirectional"))
      (node (ref "D214") (pin "2") (pinfunction "C2_2") (pintype "bidirectional"))
      (node (ref "D215") (pin "2") (pinfunction "C2_2") (pintype "bidirectional"))
      (node (ref "D216") (pin "2") (pinfunction "C2_2") (pintype "bidirectional"))
      (node (ref "D217") (pin "2") (pinfunction "C2_2") (pintype "bidirectional"))
      (node (ref "D218") (pin "2") (pinfunction "C2_2") (pintype "bidirectional"))
      (node (ref "D219") (pin "2") (pinfunction "C2_2") (pintype "bidirectional"))
      (node (ref "D220") (pin "2") (pinfunction "C2_2") (pintype "bidirectional"))
      (node (ref "D221") (pin "2") (pinfunction "C2_2") (pintype "bidirectional"))
      (node (ref "D222") (pin "2") (pinfunction "C2_2") (pintype "bidirectional"))
      (node (ref "D223") (pin "2") (pinfunction "C2_2") (pintype "bidirectional"))
      (node (ref "D224") (pin "2") (pinfunction "C2_2") (pintype "bidirectional"))
      (node (ref "IC6") (pin "12") (pinfunction "O7_12") (pintype "open_collector"))
    )
    (net (code "1224") (name "ROW8_SINK") (class "Default")
      (node (ref "D225") (pin "1") (pinfunction "A1_1") (pintype "bidirectional"))
      (node (ref "D226") (pin "1") (pinfunction "A1_1") (pintype "bidirectional"))
      (node (ref "D227") (pin "1") (pinfunction "A1_1") (pintype "bidirectional"))
      (node (ref "D228") (pin "1") (pinfunction "A1_1") (pintype "bidirectional"))
      (node (ref "D229") (pin "1") (pinfunction "A1_1") (pintype "bidirectional"))
      (node (ref "D230") (pin "1") (pinfunction "A1_1") (pintype "bidirectional"))
      (node (ref "D231") (pin "1") (pinfunction "A1_1") (pintype "bidirectional"))
      (node (ref "D232") (pin "1") (pinfunction "A1_1") (pintype "bidirectional"))
      (node (ref "D233") (pin "1") (pinfunction "A1_1") (pintype "bidirectional"))
      (node (ref "D234") (pin "1") (pinfunction "A1_1") (pintype "bidirectional"))
      (node (ref "D235") (pin "1") (pinfunction "A1_1") (pintype "bidirectional"))
      (node (ref "D236") (pin "1") (pinfunction "A1_1") (pintype "bidirectional"))
      (node (ref "D237") (pin "1") (pinfunction "A1_1") (pintype "bidirectional"))
      (node (ref "D238") (pin "1") (pinfunction "A1_1") (pintype "bidirectional"))
      (node (ref "D239") (pin "1") (pinfunction "A1_1") (pintype "bidirectional"))
      (node (ref "D240") (pin "1") (pinfunction "A1_1") (pintype "bidirectional"))
      (node (ref "D241") (pin "1") (pinfunction "A1_1") (pintype "bidirectional"))
      (node (ref "D242") (pin "1") (pinfunction "A1_1") (pintype "bidirectional"))
      (node (ref "D243") (pin "1") (pinfunction "A1_1") (pintype "bidirectional"))
      (node (ref "D244") (pin "1") (pinfunction "A1_1") (pintype "bidirectional"))
      (node (ref "D245") (pin "1") (pinfunction "A1_1") (pintype "bidirectional"))
      (node (ref "D246") (pin "1") (pinfunction "A1_1") (pintype "bidirectional"))
      (node (ref "D247") (pin "1") (pinfunction "A1_1") (pintype "bidirectional"))
      (node (ref "D248") (pin "1") (pinfunction "A1_1") (pintype "bidirectional"))
      (node (ref "D249") (pin "1") (pinfunction "A1_1") (pintype "bidirectional"))
      (node (ref "D250") (pin "1") (pinfunction "A1_1") (pintype "bidirectional"))
      (node (ref "D251") (pin "1") (pinfunction "A1_1") (pintype "bidirectional"))
      (node (ref "D252") (pin "1") (pinfunction "A1_1") (pintype "bidirectional"))
      (node (ref "D253") (pin "1") (pinfunction "A1_1") (pintype "bidirectional"))
      (node (ref "D254") (pin "1") (pinfunction "A1_1") (pintype "bidirectional"))
      (node (ref "D255") (pin "1") (pinfunction "A1_1") (pintype "bidirectional"))
      (node (ref "D256") (pin "1") (pinfunction "A1_1") (pintype "bidirectional"))
      (node (ref "IC7") (pin "11") (pinfunction "O8_11") (pintype "open_collector"))
    )
    (net (code "1225") (name "ROW8_SOURCE") (class "Default")
      (node (ref "D225") (pin "2") (pinfunction "C2_2") (pintype "bidirectional"))
      (node (ref "D226") (pin "2") (pinfunction "C2_2") (pintype "bidirectional"))
      (node (ref "D227") (pin "2") (pinfunction "C2_2") (pintype "bidirectional"))
      (node (ref "D228") (pin "2") (pinfunction "C2_2") (pintype "bidirectional"))
      (node (ref "D229") (pin "2") (pinfunction "C2_2") (pintype "bidirectional"))
      (node (ref "D230") (pin "2") (pinfunction "C2_2") (pintype "bidirectional"))
      (node (ref "D231") (pin "2") (pinfunction "C2_2") (pintype "bidirectional"))
      (node (ref "D232") (pin "2") (pinfunction "C2_2") (pintype "bidirectional"))
      (node (ref "D233") (pin "2") (pinfunction "C2_2") (pintype "bidirectional"))
      (node (ref "D234") (pin "2") (pinfunction "C2_2") (pintype "bidirectional"))
      (node (ref "D235") (pin "2") (pinfunction "C2_2") (pintype "bidirectional"))
      (node (ref "D236") (pin "2") (pinfunction "C2_2") (pintype "bidirectional"))
      (node (ref "D237") (pin "2") (pinfunction "C2_2") (pintype "bidirectional"))
      (node (ref "D238") (pin "2") (pinfunction "C2_2") (pintype "bidirectional"))
      (node (ref "D239") (pin "2") (pinfunction "C2_2") (pintype "bidirectional"))
      (node (ref "D240") (pin "2") (pinfunction "C2_2") (pintype "bidirectional"))
      (node (ref "D241") (pin "2") (pinfunction "C2_2") (pintype "bidirectional"))
      (node (ref "D242") (pin "2") (pinfunction "C2_2") (pintype "bidirectional"))
      (node (ref "D243") (pin "2") (pinfunction "C2_2") (pintype "bidirectional"))
      (node (ref "D244") (pin "2") (pinfunction "C2_2") (pintype "bidirectional"))
      (node (ref "D245") (pin "2") (pinfunction "C2_2") (pintype "bidirectional"))
      (node (ref "D246") (pin "2") (pinfunction "C2_2") (pintype "bidirectional"))
      (node (ref "D247") (pin "2") (pinfunction "C2_2") (pintype "bidirectional"))
      (node (ref "D248") (pin "2") (pinfunction "C2_2") (pintype "bidirectional"))
      (node (ref "D249") (pin "2") (pinfunction "C2_2") (pintype "bidirectional"))
      (node (ref "D250") (pin "2") (pinfunction "C2_2") (pintype "bidirectional"))
      (node (ref "D251") (pin "2") (pinfunction "C2_2") (pintype "bidirectional"))
      (node (ref "D252") (pin "2") (pinfunction "C2_2") (pintype "bidirectional"))
      (node (ref "D253") (pin "2") (pinfunction "C2_2") (pintype "bidirectional"))
      (node (ref "D254") (pin "2") (pinfunction "C2_2") (pintype "bidirectional"))
      (node (ref "D255") (pin "2") (pinfunction "C2_2") (pintype "bidirectional"))
      (node (ref "D256") (pin "2") (pinfunction "C2_2") (pintype "bidirectional"))
      (node (ref "IC6") (pin "11") (pinfunction "O8_11") (pintype "open_collector"))
    )
    (net (code "1226") (name "ROW9-16_INHIBIT") (class "Default")
      (node (ref "IC3") (pin "5") (pinfunction "Y1_5") (pintype "output"))
      (node (ref "IC8") (pin "23") (pinfunction "INH_23") (pintype "input"))
    )
    (net (code "1227") (name "ROW9_SINK") (class "Default")
      (node (ref "D257") (pin "1") (pinfunction "A1_1") (pintype "bidirectional"))
      (node (ref "D258") (pin "1") (pinfunction "A1_1") (pintype "bidirectional"))
      (node (ref "D259") (pin "1") (pinfunction "A1_1") (pintype "bidirectional"))
      (node (ref "D260") (pin "1") (pinfunction "A1_1") (pintype "bidirectional"))
      (node (ref "D261") (pin "1") (pinfunction "A1_1") (pintype "bidirectional"))
      (node (ref "D262") (pin "1") (pinfunction "A1_1") (pintype "bidirectional"))
      (node (ref "D263") (pin "1") (pinfunction "A1_1") (pintype "bidirectional"))
      (node (ref "D264") (pin "1") (pinfunction "A1_1") (pintype "bidirectional"))
      (node (ref "D265") (pin "1") (pinfunction "A1_1") (pintype "bidirectional"))
      (node (ref "D266") (pin "1") (pinfunction "A1_1") (pintype "bidirectional"))
      (node (ref "D267") (pin "1") (pinfunction "A1_1") (pintype "bidirectional"))
      (node (ref "D268") (pin "1") (pinfunction "A1_1") (pintype "bidirectional"))
      (node (ref "D269") (pin "1") (pinfunction "A1_1") (pintype "bidirectional"))
      (node (ref "D270") (pin "1") (pinfunction "A1_1") (pintype "bidirectional"))
      (node (ref "D271") (pin "1") (pinfunction "A1_1") (pintype "bidirectional"))
      (node (ref "D272") (pin "1") (pinfunction "A1_1") (pintype "bidirectional"))
      (node (ref "D273") (pin "1") (pinfunction "A1_1") (pintype "bidirectional"))
      (node (ref "D274") (pin "1") (pinfunction "A1_1") (pintype "bidirectional"))
      (node (ref "D275") (pin "1") (pinfunction "A1_1") (pintype "bidirectional"))
      (node (ref "D276") (pin "1") (pinfunction "A1_1") (pintype "bidirectional"))
      (node (ref "D277") (pin "1") (pinfunction "A1_1") (pintype "bidirectional"))
      (node (ref "D278") (pin "1") (pinfunction "A1_1") (pintype "bidirectional"))
      (node (ref "D279") (pin "1") (pinfunction "A1_1") (pintype "bidirectional"))
      (node (ref "D280") (pin "1") (pinfunction "A1_1") (pintype "bidirectional"))
      (node (ref "D281") (pin "1") (pinfunction "A1_1") (pintype "bidirectional"))
      (node (ref "D282") (pin "1") (pinfunction "A1_1") (pintype "bidirectional"))
      (node (ref "D283") (pin "1") (pinfunction "A1_1") (pintype "bidirectional"))
      (node (ref "D284") (pin "1") (pinfunction "A1_1") (pintype "bidirectional"))
      (node (ref "D285") (pin "1") (pinfunction "A1_1") (pintype "bidirectional"))
      (node (ref "D286") (pin "1") (pinfunction "A1_1") (pintype "bidirectional"))
      (node (ref "D287") (pin "1") (pinfunction "A1_1") (pintype "bidirectional"))
      (node (ref "D288") (pin "1") (pinfunction "A1_1") (pintype "bidirectional"))
      (node (ref "IC10") (pin "18") (pinfunction "O1_18") (pintype "open_collector"))
    )
    (net (code "1228") (name "ROW9_SOURCE") (class "Default")
      (node (ref "D257") (pin "2") (pinfunction "C2_2") (pintype "bidirectional"))
      (node (ref "D258") (pin "2") (pinfunction "C2_2") (pintype "bidirectional"))
      (node (ref "D259") (pin "2") (pinfunction "C2_2") (pintype "bidirectional"))
      (node (ref "D260") (pin "2") (pinfunction "C2_2") (pintype "bidirectional"))
      (node (ref "D261") (pin "2") (pinfunction "C2_2") (pintype "bidirectional"))
      (node (ref "D262") (pin "2") (pinfunction "C2_2") (pintype "bidirectional"))
      (node (ref "D263") (pin "2") (pinfunction "C2_2") (pintype "bidirectional"))
      (node (ref "D264") (pin "2") (pinfunction "C2_2") (pintype "bidirectional"))
      (node (ref "D265") (pin "2") (pinfunction "C2_2") (pintype "bidirectional"))
      (node (ref "D266") (pin "2") (pinfunction "C2_2") (pintype "bidirectional"))
      (node (ref "D267") (pin "2") (pinfunction "C2_2") (pintype "bidirectional"))
      (node (ref "D268") (pin "2") (pinfunction "C2_2") (pintype "bidirectional"))
      (node (ref "D269") (pin "2") (pinfunction "C2_2") (pintype "bidirectional"))
      (node (ref "D270") (pin "2") (pinfunction "C2_2") (pintype "bidirectional"))
      (node (ref "D271") (pin "2") (pinfunction "C2_2") (pintype "bidirectional"))
      (node (ref "D272") (pin "2") (pinfunction "C2_2") (pintype "bidirectional"))
      (node (ref "D273") (pin "2") (pinfunction "C2_2") (pintype "bidirectional"))
      (node (ref "D274") (pin "2") (pinfunction "C2_2") (pintype "bidirectional"))
      (node (ref "D275") (pin "2") (pinfunction "C2_2") (pintype "bidirectional"))
      (node (ref "D276") (pin "2") (pinfunction "C2_2") (pintype "bidirectional"))
      (node (ref "D277") (pin "2") (pinfunction "C2_2") (pintype "bidirectional"))
      (node (ref "D278") (pin "2") (pinfunction "C2_2") (pintype "bidirectional"))
      (node (ref "D279") (pin "2") (pinfunction "C2_2") (pintype "bidirectional"))
      (node (ref "D280") (pin "2") (pinfunction "C2_2") (pintype "bidirectional"))
      (node (ref "D281") (pin "2") (pinfunction "C2_2") (pintype "bidirectional"))
      (node (ref "D282") (pin "2") (pinfunction "C2_2") (pintype "bidirectional"))
      (node (ref "D283") (pin "2") (pinfunction "C2_2") (pintype "bidirectional"))
      (node (ref "D284") (pin "2") (pinfunction "C2_2") (pintype "bidirectional"))
      (node (ref "D285") (pin "2") (pinfunction "C2_2") (pintype "bidirectional"))
      (node (ref "D286") (pin "2") (pinfunction "C2_2") (pintype "bidirectional"))
      (node (ref "D287") (pin "2") (pinfunction "C2_2") (pintype "bidirectional"))
      (node (ref "D288") (pin "2") (pinfunction "C2_2") (pintype "bidirectional"))
      (node (ref "IC9") (pin "18") (pinfunction "O1_18") (pintype "open_collector"))
    )
    (net (code "1229") (name "ROW10_SINK") (class "Default")
      (node (ref "D289") (pin "1") (pinfunction "A1_1") (pintype "bidirectional"))
      (node (ref "D290") (pin "1") (pinfunction "A1_1") (pintype "bidirectional"))
      (node (ref "D291") (pin "1") (pinfunction "A1_1") (pintype "bidirectional"))
      (node (ref "D292") (pin "1") (pinfunction "A1_1") (pintype "bidirectional"))
      (node (ref "D293") (pin "1") (pinfunction "A1_1") (pintype "bidirectional"))
      (node (ref "D294") (pin "1") (pinfunction "A1_1") (pintype "bidirectional"))
      (node (ref "D295") (pin "1") (pinfunction "A1_1") (pintype "bidirectional"))
      (node (ref "D296") (pin "1") (pinfunction "A1_1") (pintype "bidirectional"))
      (node (ref "D297") (pin "1") (pinfunction "A1_1") (pintype "bidirectional"))
      (node (ref "D298") (pin "1") (pinfunction "A1_1") (pintype "bidirectional"))
      (node (ref "D299") (pin "1") (pinfunction "A1_1") (pintype "bidirectional"))
      (node (ref "D300") (pin "1") (pinfunction "A1_1") (pintype "bidirectional"))
      (node (ref "D301") (pin "1") (pinfunction "A1_1") (pintype "bidirectional"))
      (node (ref "D302") (pin "1") (pinfunction "A1_1") (pintype "bidirectional"))
      (node (ref "D303") (pin "1") (pinfunction "A1_1") (pintype "bidirectional"))
      (node (ref "D304") (pin "1") (pinfunction "A1_1") (pintype "bidirectional"))
      (node (ref "D305") (pin "1") (pinfunction "A1_1") (pintype "bidirectional"))
      (node (ref "D306") (pin "1") (pinfunction "A1_1") (pintype "bidirectional"))
      (node (ref "D307") (pin "1") (pinfunction "A1_1") (pintype "bidirectional"))
      (node (ref "D308") (pin "1") (pinfunction "A1_1") (pintype "bidirectional"))
      (node (ref "D309") (pin "1") (pinfunction "A1_1") (pintype "bidirectional"))
      (node (ref "D310") (pin "1") (pinfunction "A1_1") (pintype "bidirectional"))
      (node (ref "D311") (pin "1") (pinfunction "A1_1") (pintype "bidirectional"))
      (node (ref "D312") (pin "1") (pinfunction "A1_1") (pintype "bidirectional"))
      (node (ref "D313") (pin "1") (pinfunction "A1_1") (pintype "bidirectional"))
      (node (ref "D314") (pin "1") (pinfunction "A1_1") (pintype "bidirectional"))
      (node (ref "D315") (pin "1") (pinfunction "A1_1") (pintype "bidirectional"))
      (node (ref "D316") (pin "1") (pinfunction "A1_1") (pintype "bidirectional"))
      (node (ref "D317") (pin "1") (pinfunction "A1_1") (pintype "bidirectional"))
      (node (ref "D318") (pin "1") (pinfunction "A1_1") (pintype "bidirectional"))
      (node (ref "D319") (pin "1") (pinfunction "A1_1") (pintype "bidirectional"))
      (node (ref "D320") (pin "1") (pinfunction "A1_1") (pintype "bidirectional"))
      (node (ref "IC10") (pin "17") (pinfunction "O2_17") (pintype "open_collector"))
    )
    (net (code "1230") (name "ROW10_SOURCE") (class "Default")
      (node (ref "D289") (pin "2") (pinfunction "C2_2") (pintype "bidirectional"))
      (node (ref "D290") (pin "2") (pinfunction "C2_2") (pintype "bidirectional"))
      (node (ref "D291") (pin "2") (pinfunction "C2_2") (pintype "bidirectional"))
      (node (ref "D292") (pin "2") (pinfunction "C2_2") (pintype "bidirectional"))
      (node (ref "D293") (pin "2") (pinfunction "C2_2") (pintype "bidirectional"))
      (node (ref "D294") (pin "2") (pinfunction "C2_2") (pintype "bidirectional"))
      (node (ref "D295") (pin "2") (pinfunction "C2_2") (pintype "bidirectional"))
      (node (ref "D296") (pin "2") (pinfunction "C2_2") (pintype "bidirectional"))
      (node (ref "D297") (pin "2") (pinfunction "C2_2") (pintype "bidirectional"))
      (node (ref "D298") (pin "2") (pinfunction "C2_2") (pintype "bidirectional"))
      (node (ref "D299") (pin "2") (pinfunction "C2_2") (pintype "bidirectional"))
      (node (ref "D300") (pin "2") (pinfunction "C2_2") (pintype "bidirectional"))
      (node (ref "D301") (pin "2") (pinfunction "C2_2") (pintype "bidirectional"))
      (node (ref "D302") (pin "2") (pinfunction "C2_2") (pintype "bidirectional"))
      (node (ref "D303") (pin "2") (pinfunction "C2_2") (pintype "bidirectional"))
      (node (ref "D304") (pin "2") (pinfunction "C2_2") (pintype "bidirectional"))
      (node (ref "D305") (pin "2") (pinfunction "C2_2") (pintype "bidirectional"))
      (node (ref "D306") (pin "2") (pinfunction "C2_2") (pintype "bidirectional"))
      (node (ref "D307") (pin "2") (pinfunction "C2_2") (pintype "bidirectional"))
      (node (ref "D308") (pin "2") (pinfunction "C2_2") (pintype "bidirectional"))
      (node (ref "D309") (pin "2") (pinfunction "C2_2") (pintype "bidirectional"))
      (node (ref "D310") (pin "2") (pinfunction "C2_2") (pintype "bidirectional"))
      (node (ref "D311") (pin "2") (pinfunction "C2_2") (pintype "bidirectional"))
      (node (ref "D312") (pin "2") (pinfunction "C2_2") (pintype "bidirectional"))
      (node (ref "D313") (pin "2") (pinfunction "C2_2") (pintype "bidirectional"))
      (node (ref "D314") (pin "2") (pinfunction "C2_2") (pintype "bidirectional"))
      (node (ref "D315") (pin "2") (pinfunction "C2_2") (pintype "bidirectional"))
      (node (ref "D316") (pin "2") (pinfunction "C2_2") (pintype "bidirectional"))
      (node (ref "D317") (pin "2") (pinfunction "C2_2") (pintype "bidirectional"))
      (node (ref "D318") (pin "2") (pinfunction "C2_2") (pintype "bidirectional"))
      (node (ref "D319") (pin "2") (pinfunction "C2_2") (pintype "bidirectional"))
      (node (ref "D320") (pin "2") (pinfunction "C2_2") (pintype "bidirectional"))
      (node (ref "IC9") (pin "17") (pinfunction "O2_17") (pintype "open_collector"))
    )
    (net (code "1231") (name "ROW11_SINK") (class "Default")
      (node (ref "D321") (pin "1") (pinfunction "A1_1") (pintype "bidirectional"))
      (node (ref "D322") (pin "1") (pinfunction "A1_1") (pintype "bidirectional"))
      (node (ref "D323") (pin "1") (pinfunction "A1_1") (pintype "bidirectional"))
      (node (ref "D324") (pin "1") (pinfunction "A1_1") (pintype "bidirectional"))
      (node (ref "D325") (pin "1") (pinfunction "A1_1") (pintype "bidirectional"))
      (node (ref "D326") (pin "1") (pinfunction "A1_1") (pintype "bidirectional"))
      (node (ref "D327") (pin "1") (pinfunction "A1_1") (pintype "bidirectional"))
      (node (ref "D328") (pin "1") (pinfunction "A1_1") (pintype "bidirectional"))
      (node (ref "D329") (pin "1") (pinfunction "A1_1") (pintype "bidirectional"))
      (node (ref "D330") (pin "1") (pinfunction "A1_1") (pintype "bidirectional"))
      (node (ref "D331") (pin "1") (pinfunction "A1_1") (pintype "bidirectional"))
      (node (ref "D332") (pin "1") (pinfunction "A1_1") (pintype "bidirectional"))
      (node (ref "D333") (pin "1") (pinfunction "A1_1") (pintype "bidirectional"))
      (node (ref "D334") (pin "1") (pinfunction "A1_1") (pintype "bidirectional"))
      (node (ref "D335") (pin "1") (pinfunction "A1_1") (pintype "bidirectional"))
      (node (ref "D336") (pin "1") (pinfunction "A1_1") (pintype "bidirectional"))
      (node (ref "D337") (pin "1") (pinfunction "A1_1") (pintype "bidirectional"))
      (node (ref "D338") (pin "1") (pinfunction "A1_1") (pintype "bidirectional"))
      (node (ref "D339") (pin "1") (pinfunction "A1_1") (pintype "bidirectional"))
      (node (ref "D340") (pin "1") (pinfunction "A1_1") (pintype "bidirectional"))
      (node (ref "D341") (pin "1") (pinfunction "A1_1") (pintype "bidirectional"))
      (node (ref "D342") (pin "1") (pinfunction "A1_1") (pintype "bidirectional"))
      (node (ref "D343") (pin "1") (pinfunction "A1_1") (pintype "bidirectional"))
      (node (ref "D344") (pin "1") (pinfunction "A1_1") (pintype "bidirectional"))
      (node (ref "D345") (pin "1") (pinfunction "A1_1") (pintype "bidirectional"))
      (node (ref "D346") (pin "1") (pinfunction "A1_1") (pintype "bidirectional"))
      (node (ref "D347") (pin "1") (pinfunction "A1_1") (pintype "bidirectional"))
      (node (ref "D348") (pin "1") (pinfunction "A1_1") (pintype "bidirectional"))
      (node (ref "D349") (pin "1") (pinfunction "A1_1") (pintype "bidirectional"))
      (node (ref "D350") (pin "1") (pinfunction "A1_1") (pintype "bidirectional"))
      (node (ref "D351") (pin "1") (pinfunction "A1_1") (pintype "bidirectional"))
      (node (ref "D352") (pin "1") (pinfunction "A1_1") (pintype "bidirectional"))
      (node (ref "IC10") (pin "16") (pinfunction "O3_16") (pintype "open_collector"))
    )
    (net (code "1232") (name "ROW11_SOURCE") (class "Default")
      (node (ref "D321") (pin "2") (pinfunction "C2_2") (pintype "bidirectional"))
      (node (ref "D322") (pin "2") (pinfunction "C2_2") (pintype "bidirectional"))
      (node (ref "D323") (pin "2") (pinfunction "C2_2") (pintype "bidirectional"))
      (node (ref "D324") (pin "2") (pinfunction "C2_2") (pintype "bidirectional"))
      (node (ref "D325") (pin "2") (pinfunction "C2_2") (pintype "bidirectional"))
      (node (ref "D326") (pin "2") (pinfunction "C2_2") (pintype "bidirectional"))
      (node (ref "D327") (pin "2") (pinfunction "C2_2") (pintype "bidirectional"))
      (node (ref "D328") (pin "2") (pinfunction "C2_2") (pintype "bidirectional"))
      (node (ref "D329") (pin "2") (pinfunction "C2_2") (pintype "bidirectional"))
      (node (ref "D330") (pin "2") (pinfunction "C2_2") (pintype "bidirectional"))
      (node (ref "D331") (pin "2") (pinfunction "C2_2") (pintype "bidirectional"))
      (node (ref "D332") (pin "2") (pinfunction "C2_2") (pintype "bidirectional"))
      (node (ref "D333") (pin "2") (pinfunction "C2_2") (pintype "bidirectional"))
      (node (ref "D334") (pin "2") (pinfunction "C2_2") (pintype "bidirectional"))
      (node (ref "D335") (pin "2") (pinfunction "C2_2") (pintype "bidirectional"))
      (node (ref "D336") (pin "2") (pinfunction "C2_2") (pintype "bidirectional"))
      (node (ref "D337") (pin "2") (pinfunction "C2_2") (pintype "bidirectional"))
      (node (ref "D338") (pin "2") (pinfunction "C2_2") (pintype "bidirectional"))
      (node (ref "D339") (pin "2") (pinfunction "C2_2") (pintype "bidirectional"))
      (node (ref "D340") (pin "2") (pinfunction "C2_2") (pintype "bidirectional"))
      (node (ref "D341") (pin "2") (pinfunction "C2_2") (pintype "bidirectional"))
      (node (ref "D342") (pin "2") (pinfunction "C2_2") (pintype "bidirectional"))
      (node (ref "D343") (pin "2") (pinfunction "C2_2") (pintype "bidirectional"))
      (node (ref "D344") (pin "2") (pinfunction "C2_2") (pintype "bidirectional"))
      (node (ref "D345") (pin "2") (pinfunction "C2_2") (pintype "bidirectional"))
      (node (ref "D346") (pin "2") (pinfunction "C2_2") (pintype "bidirectional"))
      (node (ref "D347") (pin "2") (pinfunction "C2_2") (pintype "bidirectional"))
      (node (ref "D348") (pin "2") (pinfunction "C2_2") (pintype "bidirectional"))
      (node (ref "D349") (pin "2") (pinfunction "C2_2") (pintype "bidirectional"))
      (node (ref "D350") (pin "2") (pinfunction "C2_2") (pintype "bidirectional"))
      (node (ref "D351") (pin "2") (pinfunction "C2_2") (pintype "bidirectional"))
      (node (ref "D352") (pin "2") (pinfunction "C2_2") (pintype "bidirectional"))
      (node (ref "IC9") (pin "16") (pinfunction "O3_16") (pintype "open_collector"))
    )
    (net (code "1233") (name "ROW12_SINK") (class "Default")
      (node (ref "D353") (pin "1") (pinfunction "A1_1") (pintype "bidirectional"))
      (node (ref "D354") (pin "1") (pinfunction "A1_1") (pintype "bidirectional"))
      (node (ref "D355") (pin "1") (pinfunction "A1_1") (pintype "bidirectional"))
      (node (ref "D356") (pin "1") (pinfunction "A1_1") (pintype "bidirectional"))
      (node (ref "D357") (pin "1") (pinfunction "A1_1") (pintype "bidirectional"))
      (node (ref "D358") (pin "1") (pinfunction "A1_1") (pintype "bidirectional"))
      (node (ref "D359") (pin "1") (pinfunction "A1_1") (pintype "bidirectional"))
      (node (ref "D360") (pin "1") (pinfunction "A1_1") (pintype "bidirectional"))
      (node (ref "D361") (pin "1") (pinfunction "A1_1") (pintype "bidirectional"))
      (node (ref "D362") (pin "1") (pinfunction "A1_1") (pintype "bidirectional"))
      (node (ref "D363") (pin "1") (pinfunction "A1_1") (pintype "bidirectional"))
      (node (ref "D364") (pin "1") (pinfunction "A1_1") (pintype "bidirectional"))
      (node (ref "D365") (pin "1") (pinfunction "A1_1") (pintype "bidirectional"))
      (node (ref "D366") (pin "1") (pinfunction "A1_1") (pintype "bidirectional"))
      (node (ref "D367") (pin "1") (pinfunction "A1_1") (pintype "bidirectional"))
      (node (ref "D368") (pin "1") (pinfunction "A1_1") (pintype "bidirectional"))
      (node (ref "D369") (pin "1") (pinfunction "A1_1") (pintype "bidirectional"))
      (node (ref "D370") (pin "1") (pinfunction "A1_1") (pintype "bidirectional"))
      (node (ref "D371") (pin "1") (pinfunction "A1_1") (pintype "bidirectional"))
      (node (ref "D372") (pin "1") (pinfunction "A1_1") (pintype "bidirectional"))
      (node (ref "D373") (pin "1") (pinfunction "A1_1") (pintype "bidirectional"))
      (node (ref "D374") (pin "1") (pinfunction "A1_1") (pintype "bidirectional"))
      (node (ref "D375") (pin "1") (pinfunction "A1_1") (pintype "bidirectional"))
      (node (ref "D376") (pin "1") (pinfunction "A1_1") (pintype "bidirectional"))
      (node (ref "D377") (pin "1") (pinfunction "A1_1") (pintype "bidirectional"))
      (node (ref "D378") (pin "1") (pinfunction "A1_1") (pintype "bidirectional"))
      (node (ref "D379") (pin "1") (pinfunction "A1_1") (pintype "bidirectional"))
      (node (ref "D380") (pin "1") (pinfunction "A1_1") (pintype "bidirectional"))
      (node (ref "D381") (pin "1") (pinfunction "A1_1") (pintype "bidirectional"))
      (node (ref "D382") (pin "1") (pinfunction "A1_1") (pintype "bidirectional"))
      (node (ref "D383") (pin "1") (pinfunction "A1_1") (pintype "bidirectional"))
      (node (ref "D384") (pin "1") (pinfunction "A1_1") (pintype "bidirectional"))
      (node (ref "IC10") (pin "15") (pinfunction "O4_15") (pintype "open_collector"))
    )
    (net (code "1234") (name "ROW12_SOURCE") (class "Default")
      (node (ref "D353") (pin "2") (pinfunction "C2_2") (pintype "bidirectional"))
      (node (ref "D354") (pin "2") (pinfunction "C2_2") (pintype "bidirectional"))
      (node (ref "D355") (pin "2") (pinfunction "C2_2") (pintype "bidirectional"))
      (node (ref "D356") (pin "2") (pinfunction "C2_2") (pintype "bidirectional"))
      (node (ref "D357") (pin "2") (pinfunction "C2_2") (pintype "bidirectional"))
      (node (ref "D358") (pin "2") (pinfunction "C2_2") (pintype "bidirectional"))
      (node (ref "D359") (pin "2") (pinfunction "C2_2") (pintype "bidirectional"))
      (node (ref "D360") (pin "2") (pinfunction "C2_2") (pintype "bidirectional"))
      (node (ref "D361") (pin "2") (pinfunction "C2_2") (pintype "bidirectional"))
      (node (ref "D362") (pin "2") (pinfunction "C2_2") (pintype "bidirectional"))
      (node (ref "D363") (pin "2") (pinfunction "C2_2") (pintype "bidirectional"))
      (node (ref "D364") (pin "2") (pinfunction "C2_2") (pintype "bidirectional"))
      (node (ref "D365") (pin "2") (pinfunction "C2_2") (pintype "bidirectional"))
      (node (ref "D366") (pin "2") (pinfunction "C2_2") (pintype "bidirectional"))
      (node (ref "D367") (pin "2") (pinfunction "C2_2") (pintype "bidirectional"))
      (node (ref "D368") (pin "2") (pinfunction "C2_2") (pintype "bidirectional"))
      (node (ref "D369") (pin "2") (pinfunction "C2_2") (pintype "bidirectional"))
      (node (ref "D370") (pin "2") (pinfunction "C2_2") (pintype "bidirectional"))
      (node (ref "D371") (pin "2") (pinfunction "C2_2") (pintype "bidirectional"))
      (node (ref "D372") (pin "2") (pinfunction "C2_2") (pintype "bidirectional"))
      (node (ref "D373") (pin "2") (pinfunction "C2_2") (pintype "bidirectional"))
      (node (ref "D374") (pin "2") (pinfunction "C2_2") (pintype "bidirectional"))
      (node (ref "D375") (pin "2") (pinfunction "C2_2") (pintype "bidirectional"))
      (node (ref "D376") (pin "2") (pinfunction "C2_2") (pintype "bidirectional"))
      (node (ref "D377") (pin "2") (pinfunction "C2_2") (pintype "bidirectional"))
      (node (ref "D378") (pin "2") (pinfunction "C2_2") (pintype "bidirectional"))
      (node (ref "D379") (pin "2") (pinfunction "C2_2") (pintype "bidirectional"))
      (node (ref "D380") (pin "2") (pinfunction "C2_2") (pintype "bidirectional"))
      (node (ref "D381") (pin "2") (pinfunction "C2_2") (pintype "bidirectional"))
      (node (ref "D382") (pin "2") (pinfunction "C2_2") (pintype "bidirectional"))
      (node (ref "D383") (pin "2") (pinfunction "C2_2") (pintype "bidirectional"))
      (node (ref "D384") (pin "2") (pinfunction "C2_2") (pintype "bidirectional"))
      (node (ref "IC9") (pin "15") (pinfunction "O4_15") (pintype "open_collector"))
    )
    (net (code "1235") (name "ROW13_SINK") (class "Default")
      (node (ref "D385") (pin "1") (pinfunction "A1_1") (pintype "bidirectional"))
      (node (ref "D386") (pin "1") (pinfunction "A1_1") (pintype "bidirectional"))
      (node (ref "D387") (pin "1") (pinfunction "A1_1") (pintype "bidirectional"))
      (node (ref "D388") (pin "1") (pinfunction "A1_1") (pintype "bidirectional"))
      (node (ref "D389") (pin "1") (pinfunction "A1_1") (pintype "bidirectional"))
      (node (ref "D390") (pin "1") (pinfunction "A1_1") (pintype "bidirectional"))
      (node (ref "D391") (pin "1") (pinfunction "A1_1") (pintype "bidirectional"))
      (node (ref "D392") (pin "1") (pinfunction "A1_1") (pintype "bidirectional"))
      (node (ref "D393") (pin "1") (pinfunction "A1_1") (pintype "bidirectional"))
      (node (ref "D394") (pin "1") (pinfunction "A1_1") (pintype "bidirectional"))
      (node (ref "D395") (pin "1") (pinfunction "A1_1") (pintype "bidirectional"))
      (node (ref "D396") (pin "1") (pinfunction "A1_1") (pintype "bidirectional"))
      (node (ref "D397") (pin "1") (pinfunction "A1_1") (pintype "bidirectional"))
      (node (ref "D398") (pin "1") (pinfunction "A1_1") (pintype "bidirectional"))
      (node (ref "D399") (pin "1") (pinfunction "A1_1") (pintype "bidirectional"))
      (node (ref "D400") (pin "1") (pinfunction "A1_1") (pintype "bidirectional"))
      (node (ref "D401") (pin "1") (pinfunction "A1_1") (pintype "bidirectional"))
      (node (ref "D402") (pin "1") (pinfunction "A1_1") (pintype "bidirectional"))
      (node (ref "D403") (pin "1") (pinfunction "A1_1") (pintype "bidirectional"))
      (node (ref "D404") (pin "1") (pinfunction "A1_1") (pintype "bidirectional"))
      (node (ref "D405") (pin "1") (pinfunction "A1_1") (pintype "bidirectional"))
      (node (ref "D406") (pin "1") (pinfunction "A1_1") (pintype "bidirectional"))
      (node (ref "D407") (pin "1") (pinfunction "A1_1") (pintype "bidirectional"))
      (node (ref "D408") (pin "1") (pinfunction "A1_1") (pintype "bidirectional"))
      (node (ref "D409") (pin "1") (pinfunction "A1_1") (pintype "bidirectional"))
      (node (ref "D410") (pin "1") (pinfunction "A1_1") (pintype "bidirectional"))
      (node (ref "D411") (pin "1") (pinfunction "A1_1") (pintype "bidirectional"))
      (node (ref "D412") (pin "1") (pinfunction "A1_1") (pintype "bidirectional"))
      (node (ref "D413") (pin "1") (pinfunction "A1_1") (pintype "bidirectional"))
      (node (ref "D414") (pin "1") (pinfunction "A1_1") (pintype "bidirectional"))
      (node (ref "D415") (pin "1") (pinfunction "A1_1") (pintype "bidirectional"))
      (node (ref "D416") (pin "1") (pinfunction "A1_1") (pintype "bidirectional"))
      (node (ref "IC10") (pin "14") (pinfunction "O5_14") (pintype "open_collector"))
    )
    (net (code "1236") (name "ROW13_SOURCE") (class "Default")
      (node (ref "D385") (pin "2") (pinfunction "C2_2") (pintype "bidirectional"))
      (node (ref "D386") (pin "2") (pinfunction "C2_2") (pintype "bidirectional"))
      (node (ref "D387") (pin "2") (pinfunction "C2_2") (pintype "bidirectional"))
      (node (ref "D388") (pin "2") (pinfunction "C2_2") (pintype "bidirectional"))
      (node (ref "D389") (pin "2") (pinfunction "C2_2") (pintype "bidirectional"))
      (node (ref "D390") (pin "2") (pinfunction "C2_2") (pintype "bidirectional"))
      (node (ref "D391") (pin "2") (pinfunction "C2_2") (pintype "bidirectional"))
      (node (ref "D392") (pin "2") (pinfunction "C2_2") (pintype "bidirectional"))
      (node (ref "D393") (pin "2") (pinfunction "C2_2") (pintype "bidirectional"))
      (node (ref "D394") (pin "2") (pinfunction "C2_2") (pintype "bidirectional"))
      (node (ref "D395") (pin "2") (pinfunction "C2_2") (pintype "bidirectional"))
      (node (ref "D396") (pin "2") (pinfunction "C2_2") (pintype "bidirectional"))
      (node (ref "D397") (pin "2") (pinfunction "C2_2") (pintype "bidirectional"))
      (node (ref "D398") (pin "2") (pinfunction "C2_2") (pintype "bidirectional"))
      (node (ref "D399") (pin "2") (pinfunction "C2_2") (pintype "bidirectional"))
      (node (ref "D400") (pin "2") (pinfunction "C2_2") (pintype "bidirectional"))
      (node (ref "D401") (pin "2") (pinfunction "C2_2") (pintype "bidirectional"))
      (node (ref "D402") (pin "2") (pinfunction "C2_2") (pintype "bidirectional"))
      (node (ref "D403") (pin "2") (pinfunction "C2_2") (pintype "bidirectional"))
      (node (ref "D404") (pin "2") (pinfunction "C2_2") (pintype "bidirectional"))
      (node (ref "D405") (pin "2") (pinfunction "C2_2") (pintype "bidirectional"))
      (node (ref "D406") (pin "2") (pinfunction "C2_2") (pintype "bidirectional"))
      (node (ref "D407") (pin "2") (pinfunction "C2_2") (pintype "bidirectional"))
      (node (ref "D408") (pin "2") (pinfunction "C2_2") (pintype "bidirectional"))
      (node (ref "D409") (pin "2") (pinfunction "C2_2") (pintype "bidirectional"))
      (node (ref "D410") (pin "2") (pinfunction "C2_2") (pintype "bidirectional"))
      (node (ref "D411") (pin "2") (pinfunction "C2_2") (pintype "bidirectional"))
      (node (ref "D412") (pin "2") (pinfunction "C2_2") (pintype "bidirectional"))
      (node (ref "D413") (pin "2") (pinfunction "C2_2") (pintype "bidirectional"))
      (node (ref "D414") (pin "2") (pinfunction "C2_2") (pintype "bidirectional"))
      (node (ref "D415") (pin "2") (pinfunction "C2_2") (pintype "bidirectional"))
      (node (ref "D416") (pin "2") (pinfunction "C2_2") (pintype "bidirectional"))
      (node (ref "IC9") (pin "14") (pinfunction "O5_14") (pintype "open_collector"))
    )
    (net (code "1237") (name "ROW14_SINK") (class "Default")
      (node (ref "D417") (pin "1") (pinfunction "A1_1") (pintype "bidirectional"))
      (node (ref "D418") (pin "1") (pinfunction "A1_1") (pintype "bidirectional"))
      (node (ref "D419") (pin "1") (pinfunction "A1_1") (pintype "bidirectional"))
      (node (ref "D420") (pin "1") (pinfunction "A1_1") (pintype "bidirectional"))
      (node (ref "D421") (pin "1") (pinfunction "A1_1") (pintype "bidirectional"))
      (node (ref "D422") (pin "1") (pinfunction "A1_1") (pintype "bidirectional"))
      (node (ref "D423") (pin "1") (pinfunction "A1_1") (pintype "bidirectional"))
      (node (ref "D424") (pin "1") (pinfunction "A1_1") (pintype "bidirectional"))
      (node (ref "D425") (pin "1") (pinfunction "A1_1") (pintype "bidirectional"))
      (node (ref "D426") (pin "1") (pinfunction "A1_1") (pintype "bidirectional"))
      (node (ref "D427") (pin "1") (pinfunction "A1_1") (pintype "bidirectional"))
      (node (ref "D428") (pin "1") (pinfunction "A1_1") (pintype "bidirectional"))
      (node (ref "D429") (pin "1") (pinfunction "A1_1") (pintype "bidirectional"))
      (node (ref "D430") (pin "1") (pinfunction "A1_1") (pintype "bidirectional"))
      (node (ref "D431") (pin "1") (pinfunction "A1_1") (pintype "bidirectional"))
      (node (ref "D432") (pin "1") (pinfunction "A1_1") (pintype "bidirectional"))
      (node (ref "D433") (pin "1") (pinfunction "A1_1") (pintype "bidirectional"))
      (node (ref "D434") (pin "1") (pinfunction "A1_1") (pintype "bidirectional"))
      (node (ref "D435") (pin "1") (pinfunction "A1_1") (pintype "bidirectional"))
      (node (ref "D436") (pin "1") (pinfunction "A1_1") (pintype "bidirectional"))
      (node (ref "D437") (pin "1") (pinfunction "A1_1") (pintype "bidirectional"))
      (node (ref "D438") (pin "1") (pinfunction "A1_1") (pintype "bidirectional"))
      (node (ref "D439") (pin "1") (pinfunction "A1_1") (pintype "bidirectional"))
      (node (ref "D440") (pin "1") (pinfunction "A1_1") (pintype "bidirectional"))
      (node (ref "D441") (pin "1") (pinfunction "A1_1") (pintype "bidirectional"))
      (node (ref "D442") (pin "1") (pinfunction "A1_1") (pintype "bidirectional"))
      (node (ref "D443") (pin "1") (pinfunction "A1_1") (pintype "bidirectional"))
      (node (ref "D444") (pin "1") (pinfunction "A1_1") (pintype "bidirectional"))
      (node (ref "D445") (pin "1") (pinfunction "A1_1") (pintype "bidirectional"))
      (node (ref "D446") (pin "1") (pinfunction "A1_1") (pintype "bidirectional"))
      (node (ref "D447") (pin "1") (pinfunction "A1_1") (pintype "bidirectional"))
      (node (ref "D448") (pin "1") (pinfunction "A1_1") (pintype "bidirectional"))
      (node (ref "IC10") (pin "13") (pinfunction "O6_13") (pintype "open_collector"))
    )
    (net (code "1238") (name "ROW14_SOURCE") (class "Default")
      (node (ref "D417") (pin "2") (pinfunction "C2_2") (pintype "bidirectional"))
      (node (ref "D418") (pin "2") (pinfunction "C2_2") (pintype "bidirectional"))
      (node (ref "D419") (pin "2") (pinfunction "C2_2") (pintype "bidirectional"))
      (node (ref "D420") (pin "2") (pinfunction "C2_2") (pintype "bidirectional"))
      (node (ref "D421") (pin "2") (pinfunction "C2_2") (pintype "bidirectional"))
      (node (ref "D422") (pin "2") (pinfunction "C2_2") (pintype "bidirectional"))
      (node (ref "D423") (pin "2") (pinfunction "C2_2") (pintype "bidirectional"))
      (node (ref "D424") (pin "2") (pinfunction "C2_2") (pintype "bidirectional"))
      (node (ref "D425") (pin "2") (pinfunction "C2_2") (pintype "bidirectional"))
      (node (ref "D426") (pin "2") (pinfunction "C2_2") (pintype "bidirectional"))
      (node (ref "D427") (pin "2") (pinfunction "C2_2") (pintype "bidirectional"))
      (node (ref "D428") (pin "2") (pinfunction "C2_2") (pintype "bidirectional"))
      (node (ref "D429") (pin "2") (pinfunction "C2_2") (pintype "bidirectional"))
      (node (ref "D430") (pin "2") (pinfunction "C2_2") (pintype "bidirectional"))
      (node (ref "D431") (pin "2") (pinfunction "C2_2") (pintype "bidirectional"))
      (node (ref "D432") (pin "2") (pinfunction "C2_2") (pintype "bidirectional"))
      (node (ref "D433") (pin "2") (pinfunction "C2_2") (pintype "bidirectional"))
      (node (ref "D434") (pin "2") (pinfunction "C2_2") (pintype "bidirectional"))
      (node (ref "D435") (pin "2") (pinfunction "C2_2") (pintype "bidirectional"))
      (node (ref "D436") (pin "2") (pinfunction "C2_2") (pintype "bidirectional"))
      (node (ref "D437") (pin "2") (pinfunction "C2_2") (pintype "bidirectional"))
      (node (ref "D438") (pin "2") (pinfunction "C2_2") (pintype "bidirectional"))
      (node (ref "D439") (pin "2") (pinfunction "C2_2") (pintype "bidirectional"))
      (node (ref "D440") (pin "2") (pinfunction "C2_2") (pintype "bidirectional"))
      (node (ref "D441") (pin "2") (pinfunction "C2_2") (pintype "bidirectional"))
      (node (ref "D442") (pin "2") (pinfunction "C2_2") (pintype "bidirectional"))
      (node (ref "D443") (pin "2") (pinfunction "C2_2") (pintype "bidirectional"))
      (node (ref "D444") (pin "2") (pinfunction "C2_2") (pintype "bidirectional"))
      (node (ref "D445") (pin "2") (pinfunction "C2_2") (pintype "bidirectional"))
      (node (ref "D446") (pin "2") (pinfunction "C2_2") (pintype "bidirectional"))
      (node (ref "D447") (pin "2") (pinfunction "C2_2") (pintype "bidirectional"))
      (node (ref "D448") (pin "2") (pinfunction "C2_2") (pintype "bidirectional"))
      (node (ref "IC9") (pin "13") (pinfunction "O6_13") (pintype "open_collector"))
    )
    (net (code "1239") (name "ROW15_SINK") (class "Default")
      (node (ref "D449") (pin "1") (pinfunction "A1_1") (pintype "bidirectional"))
      (node (ref "D450") (pin "1") (pinfunction "A1_1") (pintype "bidirectional"))
      (node (ref "D451") (pin "1") (pinfunction "A1_1") (pintype "bidirectional"))
      (node (ref "D452") (pin "1") (pinfunction "A1_1") (pintype "bidirectional"))
      (node (ref "D453") (pin "1") (pinfunction "A1_1") (pintype "bidirectional"))
      (node (ref "D454") (pin "1") (pinfunction "A1_1") (pintype "bidirectional"))
      (node (ref "D455") (pin "1") (pinfunction "A1_1") (pintype "bidirectional"))
      (node (ref "D456") (pin "1") (pinfunction "A1_1") (pintype "bidirectional"))
      (node (ref "D457") (pin "1") (pinfunction "A1_1") (pintype "bidirectional"))
      (node (ref "D458") (pin "1") (pinfunction "A1_1") (pintype "bidirectional"))
      (node (ref "D459") (pin "1") (pinfunction "A1_1") (pintype "bidirectional"))
      (node (ref "D460") (pin "1") (pinfunction "A1_1") (pintype "bidirectional"))
      (node (ref "D461") (pin "1") (pinfunction "A1_1") (pintype "bidirectional"))
      (node (ref "D462") (pin "1") (pinfunction "A1_1") (pintype "bidirectional"))
      (node (ref "D463") (pin "1") (pinfunction "A1_1") (pintype "bidirectional"))
      (node (ref "D464") (pin "1") (pinfunction "A1_1") (pintype "bidirectional"))
      (node (ref "D465") (pin "1") (pinfunction "A1_1") (pintype "bidirectional"))
      (node (ref "D466") (pin "1") (pinfunction "A1_1") (pintype "bidirectional"))
      (node (ref "D467") (pin "1") (pinfunction "A1_1") (pintype "bidirectional"))
      (node (ref "D468") (pin "1") (pinfunction "A1_1") (pintype "bidirectional"))
      (node (ref "D469") (pin "1") (pinfunction "A1_1") (pintype "bidirectional"))
      (node (ref "D470") (pin "1") (pinfunction "A1_1") (pintype "bidirectional"))
      (node (ref "D471") (pin "1") (pinfunction "A1_1") (pintype "bidirectional"))
      (node (ref "D472") (pin "1") (pinfunction "A1_1") (pintype "bidirectional"))
      (node (ref "D473") (pin "1") (pinfunction "A1_1") (pintype "bidirectional"))
      (node (ref "D474") (pin "1") (pinfunction "A1_1") (pintype "bidirectional"))
      (node (ref "D475") (pin "1") (pinfunction "A1_1") (pintype "bidirectional"))
      (node (ref "D476") (pin "1") (pinfunction "A1_1") (pintype "bidirectional"))
      (node (ref "D477") (pin "1") (pinfunction "A1_1") (pintype "bidirectional"))
      (node (ref "D478") (pin "1") (pinfunction "A1_1") (pintype "bidirectional"))
      (node (ref "D479") (pin "1") (pinfunction "A1_1") (pintype "bidirectional"))
      (node (ref "D480") (pin "1") (pinfunction "A1_1") (pintype "bidirectional"))
      (node (ref "IC10") (pin "12") (pinfunction "O7_12") (pintype "open_collector"))
    )
    (net (code "1240") (name "ROW15_SOURCE") (class "Default")
      (node (ref "D449") (pin "2") (pinfunction "C2_2") (pintype "bidirectional"))
      (node (ref "D450") (pin "2") (pinfunction "C2_2") (pintype "bidirectional"))
      (node (ref "D451") (pin "2") (pinfunction "C2_2") (pintype "bidirectional"))
      (node (ref "D452") (pin "2") (pinfunction "C2_2") (pintype "bidirectional"))
      (node (ref "D453") (pin "2") (pinfunction "C2_2") (pintype "bidirectional"))
      (node (ref "D454") (pin "2") (pinfunction "C2_2") (pintype "bidirectional"))
      (node (ref "D455") (pin "2") (pinfunction "C2_2") (pintype "bidirectional"))
      (node (ref "D456") (pin "2") (pinfunction "C2_2") (pintype "bidirectional"))
      (node (ref "D457") (pin "2") (pinfunction "C2_2") (pintype "bidirectional"))
      (node (ref "D458") (pin "2") (pinfunction "C2_2") (pintype "bidirectional"))
      (node (ref "D459") (pin "2") (pinfunction "C2_2") (pintype "bidirectional"))
      (node (ref "D460") (pin "2") (pinfunction "C2_2") (pintype "bidirectional"))
      (node (ref "D461") (pin "2") (pinfunction "C2_2") (pintype "bidirectional"))
      (node (ref "D462") (pin "2") (pinfunction "C2_2") (pintype "bidirectional"))
      (node (ref "D463") (pin "2") (pinfunction "C2_2") (pintype "bidirectional"))
      (node (ref "D464") (pin "2") (pinfunction "C2_2") (pintype "bidirectional"))
      (node (ref "D465") (pin "2") (pinfunction "C2_2") (pintype "bidirectional"))
      (node (ref "D466") (pin "2") (pinfunction "C2_2") (pintype "bidirectional"))
      (node (ref "D467") (pin "2") (pinfunction "C2_2") (pintype "bidirectional"))
      (node (ref "D468") (pin "2") (pinfunction "C2_2") (pintype "bidirectional"))
      (node (ref "D469") (pin "2") (pinfunction "C2_2") (pintype "bidirectional"))
      (node (ref "D470") (pin "2") (pinfunction "C2_2") (pintype "bidirectional"))
      (node (ref "D471") (pin "2") (pinfunction "C2_2") (pintype "bidirectional"))
      (node (ref "D472") (pin "2") (pinfunction "C2_2") (pintype "bidirectional"))
      (node (ref "D473") (pin "2") (pinfunction "C2_2") (pintype "bidirectional"))
      (node (ref "D474") (pin "2") (pinfunction "C2_2") (pintype "bidirectional"))
      (node (ref "D475") (pin "2") (pinfunction "C2_2") (pintype "bidirectional"))
      (node (ref "D476") (pin "2") (pinfunction "C2_2") (pintype "bidirectional"))
      (node (ref "D477") (pin "2") (pinfunction "C2_2") (pintype "bidirectional"))
      (node (ref "D478") (pin "2") (pinfunction "C2_2") (pintype "bidirectional"))
      (node (ref "D479") (pin "2") (pinfunction "C2_2") (pintype "bidirectional"))
      (node (ref "D480") (pin "2") (pinfunction "C2_2") (pintype "bidirectional"))
      (node (ref "IC9") (pin "12") (pinfunction "O7_12") (pintype "open_collector"))
    )
    (net (code "1241") (name "ROW16_SINK") (class "Default")
      (node (ref "D481") (pin "1") (pinfunction "A1_1") (pintype "bidirectional"))
      (node (ref "D482") (pin "1") (pinfunction "A1_1") (pintype "bidirectional"))
      (node (ref "D483") (pin "1") (pinfunction "A1_1") (pintype "bidirectional"))
      (node (ref "D484") (pin "1") (pinfunction "A1_1") (pintype "bidirectional"))
      (node (ref "D485") (pin "1") (pinfunction "A1_1") (pintype "bidirectional"))
      (node (ref "D486") (pin "1") (pinfunction "A1_1") (pintype "bidirectional"))
      (node (ref "D487") (pin "1") (pinfunction "A1_1") (pintype "bidirectional"))
      (node (ref "D488") (pin "1") (pinfunction "A1_1") (pintype "bidirectional"))
      (node (ref "D489") (pin "1") (pinfunction "A1_1") (pintype "bidirectional"))
      (node (ref "D490") (pin "1") (pinfunction "A1_1") (pintype "bidirectional"))
      (node (ref "D491") (pin "1") (pinfunction "A1_1") (pintype "bidirectional"))
      (node (ref "D492") (pin "1") (pinfunction "A1_1") (pintype "bidirectional"))
      (node (ref "D493") (pin "1") (pinfunction "A1_1") (pintype "bidirectional"))
      (node (ref "D494") (pin "1") (pinfunction "A1_1") (pintype "bidirectional"))
      (node (ref "D495") (pin "1") (pinfunction "A1_1") (pintype "bidirectional"))
      (node (ref "D496") (pin "1") (pinfunction "A1_1") (pintype "bidirectional"))
      (node (ref "D497") (pin "1") (pinfunction "A1_1") (pintype "bidirectional"))
      (node (ref "D498") (pin "1") (pinfunction "A1_1") (pintype "bidirectional"))
      (node (ref "D499") (pin "1") (pinfunction "A1_1") (pintype "bidirectional"))
      (node (ref "D500") (pin "1") (pinfunction "A1_1") (pintype "bidirectional"))
      (node (ref "D501") (pin "1") (pinfunction "A1_1") (pintype "bidirectional"))
      (node (ref "D502") (pin "1") (pinfunction "A1_1") (pintype "bidirectional"))
      (node (ref "D503") (pin "1") (pinfunction "A1_1") (pintype "bidirectional"))
      (node (ref "D504") (pin "1") (pinfunction "A1_1") (pintype "bidirectional"))
      (node (ref "D505") (pin "1") (pinfunction "A1_1") (pintype "bidirectional"))
      (node (ref "D506") (pin "1") (pinfunction "A1_1") (pintype "bidirectional"))
      (node (ref "D507") (pin "1") (pinfunction "A1_1") (pintype "bidirectional"))
      (node (ref "D508") (pin "1") (pinfunction "A1_1") (pintype "bidirectional"))
      (node (ref "D509") (pin "1") (pinfunction "A1_1") (pintype "bidirectional"))
      (node (ref "D510") (pin "1") (pinfunction "A1_1") (pintype "bidirectional"))
      (node (ref "D511") (pin "1") (pinfunction "A1_1") (pintype "bidirectional"))
      (node (ref "D512") (pin "1") (pinfunction "A1_1") (pintype "bidirectional"))
      (node (ref "IC10") (pin "11") (pinfunction "O8_11") (pintype "open_collector"))
    )
    (net (code "1242") (name "ROW16_SOURCE") (class "Default")
      (node (ref "D481") (pin "2") (pinfunction "C2_2") (pintype "bidirectional"))
      (node (ref "D482") (pin "2") (pinfunction "C2_2") (pintype "bidirectional"))
      (node (ref "D483") (pin "2") (pinfunction "C2_2") (pintype "bidirectional"))
      (node (ref "D484") (pin "2") (pinfunction "C2_2") (pintype "bidirectional"))
      (node (ref "D485") (pin "2") (pinfunction "C2_2") (pintype "bidirectional"))
      (node (ref "D486") (pin "2") (pinfunction "C2_2") (pintype "bidirectional"))
      (node (ref "D487") (pin "2") (pinfunction "C2_2") (pintype "bidirectional"))
      (node (ref "D488") (pin "2") (pinfunction "C2_2") (pintype "bidirectional"))
      (node (ref "D489") (pin "2") (pinfunction "C2_2") (pintype "bidirectional"))
      (node (ref "D490") (pin "2") (pinfunction "C2_2") (pintype "bidirectional"))
      (node (ref "D491") (pin "2") (pinfunction "C2_2") (pintype "bidirectional"))
      (node (ref "D492") (pin "2") (pinfunction "C2_2") (pintype "bidirectional"))
      (node (ref "D493") (pin "2") (pinfunction "C2_2") (pintype "bidirectional"))
      (node (ref "D494") (pin "2") (pinfunction "C2_2") (pintype "bidirectional"))
      (node (ref "D495") (pin "2") (pinfunction "C2_2") (pintype "bidirectional"))
      (node (ref "D496") (pin "2") (pinfunction "C2_2") (pintype "bidirectional"))
      (node (ref "D497") (pin "2") (pinfunction "C2_2") (pintype "bidirectional"))
      (node (ref "D498") (pin "2") (pinfunction "C2_2") (pintype "bidirectional"))
      (node (ref "D499") (pin "2") (pinfunction "C2_2") (pintype "bidirectional"))
      (node (ref "D500") (pin "2") (pinfunction "C2_2") (pintype "bidirectional"))
      (node (ref "D501") (pin "2") (pinfunction "C2_2") (pintype "bidirectional"))
      (node (ref "D502") (pin "2") (pinfunction "C2_2") (pintype "bidirectional"))
      (node (ref "D503") (pin "2") (pinfunction "C2_2") (pintype "bidirectional"))
      (node (ref "D504") (pin "2") (pinfunction "C2_2") (pintype "bidirectional"))
      (node (ref "D505") (pin "2") (pinfunction "C2_2") (pintype "bidirectional"))
      (node (ref "D506") (pin "2") (pinfunction "C2_2") (pintype "bidirectional"))
      (node (ref "D507") (pin "2") (pinfunction "C2_2") (pintype "bidirectional"))
      (node (ref "D508") (pin "2") (pinfunction "C2_2") (pintype "bidirectional"))
      (node (ref "D509") (pin "2") (pinfunction "C2_2") (pintype "bidirectional"))
      (node (ref "D510") (pin "2") (pinfunction "C2_2") (pintype "bidirectional"))
      (node (ref "D511") (pin "2") (pinfunction "C2_2") (pintype "bidirectional"))
      (node (ref "D512") (pin "2") (pinfunction "C2_2") (pintype "bidirectional"))
      (node (ref "IC9") (pin "11") (pinfunction "O8_11") (pintype "open_collector"))
    )
    (net (code "1243") (name "ROW17-24_INHIBIT") (class "Default")
      (node (ref "IC11") (pin "23") (pinfunction "INH_23") (pintype "input"))
      (node (ref "IC3") (pin "6") (pinfunction "Y2_6") (pintype "output"))
    )
    (net (code "1244") (name "ROW17_SINK") (class "Default")
      (node (ref "D513") (pin "1") (pinfunction "A1_1") (pintype "bidirectional"))
      (node (ref "D514") (pin "1") (pinfunction "A1_1") (pintype "bidirectional"))
      (node (ref "D515") (pin "1") (pinfunction "A1_1") (pintype "bidirectional"))
      (node (ref "D516") (pin "1") (pinfunction "A1_1") (pintype "bidirectional"))
      (node (ref "D517") (pin "1") (pinfunction "A1_1") (pintype "bidirectional"))
      (node (ref "D518") (pin "1") (pinfunction "A1_1") (pintype "bidirectional"))
      (node (ref "D519") (pin "1") (pinfunction "A1_1") (pintype "bidirectional"))
      (node (ref "D520") (pin "1") (pinfunction "A1_1") (pintype "bidirectional"))
      (node (ref "D521") (pin "1") (pinfunction "A1_1") (pintype "bidirectional"))
      (node (ref "D522") (pin "1") (pinfunction "A1_1") (pintype "bidirectional"))
      (node (ref "D523") (pin "1") (pinfunction "A1_1") (pintype "bidirectional"))
      (node (ref "D524") (pin "1") (pinfunction "A1_1") (pintype "bidirectional"))
      (node (ref "D525") (pin "1") (pinfunction "A1_1") (pintype "bidirectional"))
      (node (ref "D526") (pin "1") (pinfunction "A1_1") (pintype "bidirectional"))
      (node (ref "D527") (pin "1") (pinfunction "A1_1") (pintype "bidirectional"))
      (node (ref "D528") (pin "1") (pinfunction "A1_1") (pintype "bidirectional"))
      (node (ref "D529") (pin "1") (pinfunction "A1_1") (pintype "bidirectional"))
      (node (ref "D530") (pin "1") (pinfunction "A1_1") (pintype "bidirectional"))
      (node (ref "D531") (pin "1") (pinfunction "A1_1") (pintype "bidirectional"))
      (node (ref "D532") (pin "1") (pinfunction "A1_1") (pintype "bidirectional"))
      (node (ref "D533") (pin "1") (pinfunction "A1_1") (pintype "bidirectional"))
      (node (ref "D534") (pin "1") (pinfunction "A1_1") (pintype "bidirectional"))
      (node (ref "D535") (pin "1") (pinfunction "A1_1") (pintype "bidirectional"))
      (node (ref "D536") (pin "1") (pinfunction "A1_1") (pintype "bidirectional"))
      (node (ref "D537") (pin "1") (pinfunction "A1_1") (pintype "bidirectional"))
      (node (ref "D538") (pin "1") (pinfunction "A1_1") (pintype "bidirectional"))
      (node (ref "D539") (pin "1") (pinfunction "A1_1") (pintype "bidirectional"))
      (node (ref "D540") (pin "1") (pinfunction "A1_1") (pintype "bidirectional"))
      (node (ref "D541") (pin "1") (pinfunction "A1_1") (pintype "bidirectional"))
      (node (ref "D542") (pin "1") (pinfunction "A1_1") (pintype "bidirectional"))
      (node (ref "D543") (pin "1") (pinfunction "A1_1") (pintype "bidirectional"))
      (node (ref "D544") (pin "1") (pinfunction "A1_1") (pintype "bidirectional"))
      (node (ref "IC12") (pin "18") (pinfunction "O1_18") (pintype "open_collector"))
    )
    (net (code "1245") (name "ROW17_SOURCE") (class "Default")
      (node (ref "D513") (pin "2") (pinfunction "C2_2") (pintype "bidirectional"))
      (node (ref "D514") (pin "2") (pinfunction "C2_2") (pintype "bidirectional"))
      (node (ref "D515") (pin "2") (pinfunction "C2_2") (pintype "bidirectional"))
      (node (ref "D516") (pin "2") (pinfunction "C2_2") (pintype "bidirectional"))
      (node (ref "D517") (pin "2") (pinfunction "C2_2") (pintype "bidirectional"))
      (node (ref "D518") (pin "2") (pinfunction "C2_2") (pintype "bidirectional"))
      (node (ref "D519") (pin "2") (pinfunction "C2_2") (pintype "bidirectional"))
      (node (ref "D520") (pin "2") (pinfunction "C2_2") (pintype "bidirectional"))
      (node (ref "D521") (pin "2") (pinfunction "C2_2") (pintype "bidirectional"))
      (node (ref "D522") (pin "2") (pinfunction "C2_2") (pintype "bidirectional"))
      (node (ref "D523") (pin "2") (pinfunction "C2_2") (pintype "bidirectional"))
      (node (ref "D524") (pin "2") (pinfunction "C2_2") (pintype "bidirectional"))
      (node (ref "D525") (pin "2") (pinfunction "C2_2") (pintype "bidirectional"))
      (node (ref "D526") (pin "2") (pinfunction "C2_2") (pintype "bidirectional"))
      (node (ref "D527") (pin "2") (pinfunction "C2_2") (pintype "bidirectional"))
      (node (ref "D528") (pin "2") (pinfunction "C2_2") (pintype "bidirectional"))
      (node (ref "D529") (pin "2") (pinfunction "C2_2") (pintype "bidirectional"))
      (node (ref "D530") (pin "2") (pinfunction "C2_2") (pintype "bidirectional"))
      (node (ref "D531") (pin "2") (pinfunction "C2_2") (pintype "bidirectional"))
      (node (ref "D532") (pin "2") (pinfunction "C2_2") (pintype "bidirectional"))
      (node (ref "D533") (pin "2") (pinfunction "C2_2") (pintype "bidirectional"))
      (node (ref "D534") (pin "2") (pinfunction "C2_2") (pintype "bidirectional"))
      (node (ref "D535") (pin "2") (pinfunction "C2_2") (pintype "bidirectional"))
      (node (ref "D536") (pin "2") (pinfunction "C2_2") (pintype "bidirectional"))
      (node (ref "D537") (pin "2") (pinfunction "C2_2") (pintype "bidirectional"))
      (node (ref "D538") (pin "2") (pinfunction "C2_2") (pintype "bidirectional"))
      (node (ref "D539") (pin "2") (pinfunction "C2_2") (pintype "bidirectional"))
      (node (ref "D540") (pin "2") (pinfunction "C2_2") (pintype "bidirectional"))
      (node (ref "D541") (pin "2") (pinfunction "C2_2") (pintype "bidirectional"))
      (node (ref "D542") (pin "2") (pinfunction "C2_2") (pintype "bidirectional"))
      (node (ref "D543") (pin "2") (pinfunction "C2_2") (pintype "bidirectional"))
      (node (ref "D544") (pin "2") (pinfunction "C2_2") (pintype "bidirectional"))
      (node (ref "IC13") (pin "18") (pinfunction "O1_18") (pintype "open_collector"))
    )
    (net (code "1246") (name "ROW18_SINK") (class "Default")
      (node (ref "D545") (pin "1") (pinfunction "A1_1") (pintype "bidirectional"))
      (node (ref "D546") (pin "1") (pinfunction "A1_1") (pintype "bidirectional"))
      (node (ref "D547") (pin "1") (pinfunction "A1_1") (pintype "bidirectional"))
      (node (ref "D548") (pin "1") (pinfunction "A1_1") (pintype "bidirectional"))
      (node (ref "D549") (pin "1") (pinfunction "A1_1") (pintype "bidirectional"))
      (node (ref "D550") (pin "1") (pinfunction "A1_1") (pintype "bidirectional"))
      (node (ref "D551") (pin "1") (pinfunction "A1_1") (pintype "bidirectional"))
      (node (ref "D552") (pin "1") (pinfunction "A1_1") (pintype "bidirectional"))
      (node (ref "D553") (pin "1") (pinfunction "A1_1") (pintype "bidirectional"))
      (node (ref "D554") (pin "1") (pinfunction "A1_1") (pintype "bidirectional"))
      (node (ref "D555") (pin "1") (pinfunction "A1_1") (pintype "bidirectional"))
      (node (ref "D556") (pin "1") (pinfunction "A1_1") (pintype "bidirectional"))
      (node (ref "D557") (pin "1") (pinfunction "A1_1") (pintype "bidirectional"))
      (node (ref "D558") (pin "1") (pinfunction "A1_1") (pintype "bidirectional"))
      (node (ref "D559") (pin "1") (pinfunction "A1_1") (pintype "bidirectional"))
      (node (ref "D560") (pin "1") (pinfunction "A1_1") (pintype "bidirectional"))
      (node (ref "D561") (pin "1") (pinfunction "A1_1") (pintype "bidirectional"))
      (node (ref "D562") (pin "1") (pinfunction "A1_1") (pintype "bidirectional"))
      (node (ref "D563") (pin "1") (pinfunction "A1_1") (pintype "bidirectional"))
      (node (ref "D564") (pin "1") (pinfunction "A1_1") (pintype "bidirectional"))
      (node (ref "D565") (pin "1") (pinfunction "A1_1") (pintype "bidirectional"))
      (node (ref "D566") (pin "1") (pinfunction "A1_1") (pintype "bidirectional"))
      (node (ref "D567") (pin "1") (pinfunction "A1_1") (pintype "bidirectional"))
      (node (ref "D568") (pin "1") (pinfunction "A1_1") (pintype "bidirectional"))
      (node (ref "D569") (pin "1") (pinfunction "A1_1") (pintype "bidirectional"))
      (node (ref "D570") (pin "1") (pinfunction "A1_1") (pintype "bidirectional"))
      (node (ref "D571") (pin "1") (pinfunction "A1_1") (pintype "bidirectional"))
      (node (ref "D572") (pin "1") (pinfunction "A1_1") (pintype "bidirectional"))
      (node (ref "D573") (pin "1") (pinfunction "A1_1") (pintype "bidirectional"))
      (node (ref "D574") (pin "1") (pinfunction "A1_1") (pintype "bidirectional"))
      (node (ref "D575") (pin "1") (pinfunction "A1_1") (pintype "bidirectional"))
      (node (ref "D576") (pin "1") (pinfunction "A1_1") (pintype "bidirectional"))
      (node (ref "IC12") (pin "17") (pinfunction "O2_17") (pintype "open_collector"))
    )
    (net (code "1247") (name "ROW18_SOURCE") (class "Default")
      (node (ref "D545") (pin "2") (pinfunction "C2_2") (pintype "bidirectional"))
      (node (ref "D546") (pin "2") (pinfunction "C2_2") (pintype "bidirectional"))
      (node (ref "D547") (pin "2") (pinfunction "C2_2") (pintype "bidirectional"))
      (node (ref "D548") (pin "2") (pinfunction "C2_2") (pintype "bidirectional"))
      (node (ref "D549") (pin "2") (pinfunction "C2_2") (pintype "bidirectional"))
      (node (ref "D550") (pin "2") (pinfunction "C2_2") (pintype "bidirectional"))
      (node (ref "D551") (pin "2") (pinfunction "C2_2") (pintype "bidirectional"))
      (node (ref "D552") (pin "2") (pinfunction "C2_2") (pintype "bidirectional"))
      (node (ref "D553") (pin "2") (pinfunction "C2_2") (pintype "bidirectional"))
      (node (ref "D554") (pin "2") (pinfunction "C2_2") (pintype "bidirectional"))
      (node (ref "D555") (pin "2") (pinfunction "C2_2") (pintype "bidirectional"))
      (node (ref "D556") (pin "2") (pinfunction "C2_2") (pintype "bidirectional"))
      (node (ref "D557") (pin "2") (pinfunction "C2_2") (pintype "bidirectional"))
      (node (ref "D558") (pin "2") (pinfunction "C2_2") (pintype "bidirectional"))
      (node (ref "D559") (pin "2") (pinfunction "C2_2") (pintype "bidirectional"))
      (node (ref "D560") (pin "2") (pinfunction "C2_2") (pintype "bidirectional"))
      (node (ref "D561") (pin "2") (pinfunction "C2_2") (pintype "bidirectional"))
      (node (ref "D562") (pin "2") (pinfunction "C2_2") (pintype "bidirectional"))
      (node (ref "D563") (pin "2") (pinfunction "C2_2") (pintype "bidirectional"))
      (node (ref "D564") (pin "2") (pinfunction "C2_2") (pintype "bidirectional"))
      (node (ref "D565") (pin "2") (pinfunction "C2_2") (pintype "bidirectional"))
      (node (ref "D566") (pin "2") (pinfunction "C2_2") (pintype "bidirectional"))
      (node (ref "D567") (pin "2") (pinfunction "C2_2") (pintype "bidirectional"))
      (node (ref "D568") (pin "2") (pinfunction "C2_2") (pintype "bidirectional"))
      (node (ref "D569") (pin "2") (pinfunction "C2_2") (pintype "bidirectional"))
      (node (ref "D570") (pin "2") (pinfunction "C2_2") (pintype "bidirectional"))
      (node (ref "D571") (pin "2") (pinfunction "C2_2") (pintype "bidirectional"))
      (node (ref "D572") (pin "2") (pinfunction "C2_2") (pintype "bidirectional"))
      (node (ref "D573") (pin "2") (pinfunction "C2_2") (pintype "bidirectional"))
      (node (ref "D574") (pin "2") (pinfunction "C2_2") (pintype "bidirectional"))
      (node (ref "D575") (pin "2") (pinfunction "C2_2") (pintype "bidirectional"))
      (node (ref "D576") (pin "2") (pinfunction "C2_2") (pintype "bidirectional"))
      (node (ref "IC13") (pin "17") (pinfunction "O2_17") (pintype "open_collector"))
    )
    (net (code "1248") (name "ROW19_SINK") (class "Default")
      (node (ref "D577") (pin "1") (pinfunction "A1_1") (pintype "bidirectional"))
      (node (ref "D578") (pin "1") (pinfunction "A1_1") (pintype "bidirectional"))
      (node (ref "D579") (pin "1") (pinfunction "A1_1") (pintype "bidirectional"))
      (node (ref "D580") (pin "1") (pinfunction "A1_1") (pintype "bidirectional"))
      (node (ref "D581") (pin "1") (pinfunction "A1_1") (pintype "bidirectional"))
      (node (ref "D582") (pin "1") (pinfunction "A1_1") (pintype "bidirectional"))
      (node (ref "D583") (pin "1") (pinfunction "A1_1") (pintype "bidirectional"))
      (node (ref "D584") (pin "1") (pinfunction "A1_1") (pintype "bidirectional"))
      (node (ref "D585") (pin "1") (pinfunction "A1_1") (pintype "bidirectional"))
      (node (ref "D586") (pin "1") (pinfunction "A1_1") (pintype "bidirectional"))
      (node (ref "D587") (pin "1") (pinfunction "A1_1") (pintype "bidirectional"))
      (node (ref "D588") (pin "1") (pinfunction "A1_1") (pintype "bidirectional"))
      (node (ref "D589") (pin "1") (pinfunction "A1_1") (pintype "bidirectional"))
      (node (ref "D590") (pin "1") (pinfunction "A1_1") (pintype "bidirectional"))
      (node (ref "D591") (pin "1") (pinfunction "A1_1") (pintype "bidirectional"))
      (node (ref "D592") (pin "1") (pinfunction "A1_1") (pintype "bidirectional"))
      (node (ref "D593") (pin "1") (pinfunction "A1_1") (pintype "bidirectional"))
      (node (ref "D594") (pin "1") (pinfunction "A1_1") (pintype "bidirectional"))
      (node (ref "D595") (pin "1") (pinfunction "A1_1") (pintype "bidirectional"))
      (node (ref "D596") (pin "1") (pinfunction "A1_1") (pintype "bidirectional"))
      (node (ref "D597") (pin "1") (pinfunction "A1_1") (pintype "bidirectional"))
      (node (ref "D598") (pin "1") (pinfunction "A1_1") (pintype "bidirectional"))
      (node (ref "D599") (pin "1") (pinfunction "A1_1") (pintype "bidirectional"))
      (node (ref "D600") (pin "1") (pinfunction "A1_1") (pintype "bidirectional"))
      (node (ref "D601") (pin "1") (pinfunction "A1_1") (pintype "bidirectional"))
      (node (ref "D602") (pin "1") (pinfunction "A1_1") (pintype "bidirectional"))
      (node (ref "D603") (pin "1") (pinfunction "A1_1") (pintype "bidirectional"))
      (node (ref "D604") (pin "1") (pinfunction "A1_1") (pintype "bidirectional"))
      (node (ref "D605") (pin "1") (pinfunction "A1_1") (pintype "bidirectional"))
      (node (ref "D606") (pin "1") (pinfunction "A1_1") (pintype "bidirectional"))
      (node (ref "D607") (pin "1") (pinfunction "A1_1") (pintype "bidirectional"))
      (node (ref "D608") (pin "1") (pinfunction "A1_1") (pintype "bidirectional"))
      (node (ref "IC12") (pin "16") (pinfunction "O3_16") (pintype "open_collector"))
    )
    (net (code "1249") (name "ROW19_SOURCE") (class "Default")
      (node (ref "D577") (pin "2") (pinfunction "C2_2") (pintype "bidirectional"))
      (node (ref "D578") (pin "2") (pinfunction "C2_2") (pintype "bidirectional"))
      (node (ref "D579") (pin "2") (pinfunction "C2_2") (pintype "bidirectional"))
      (node (ref "D580") (pin "2") (pinfunction "C2_2") (pintype "bidirectional"))
      (node (ref "D581") (pin "2") (pinfunction "C2_2") (pintype "bidirectional"))
      (node (ref "D582") (pin "2") (pinfunction "C2_2") (pintype "bidirectional"))
      (node (ref "D583") (pin "2") (pinfunction "C2_2") (pintype "bidirectional"))
      (node (ref "D584") (pin "2") (pinfunction "C2_2") (pintype "bidirectional"))
      (node (ref "D585") (pin "2") (pinfunction "C2_2") (pintype "bidirectional"))
      (node (ref "D586") (pin "2") (pinfunction "C2_2") (pintype "bidirectional"))
      (node (ref "D587") (pin "2") (pinfunction "C2_2") (pintype "bidirectional"))
      (node (ref "D588") (pin "2") (pinfunction "C2_2") (pintype "bidirectional"))
      (node (ref "D589") (pin "2") (pinfunction "C2_2") (pintype "bidirectional"))
      (node (ref "D590") (pin "2") (pinfunction "C2_2") (pintype "bidirectional"))
      (node (ref "D591") (pin "2") (pinfunction "C2_2") (pintype "bidirectional"))
      (node (ref "D592") (pin "2") (pinfunction "C2_2") (pintype "bidirectional"))
      (node (ref "D593") (pin "2") (pinfunction "C2_2") (pintype "bidirectional"))
      (node (ref "D594") (pin "2") (pinfunction "C2_2") (pintype "bidirectional"))
      (node (ref "D595") (pin "2") (pinfunction "C2_2") (pintype "bidirectional"))
      (node (ref "D596") (pin "2") (pinfunction "C2_2") (pintype "bidirectional"))
      (node (ref "D597") (pin "2") (pinfunction "C2_2") (pintype "bidirectional"))
      (node (ref "D598") (pin "2") (pinfunction "C2_2") (pintype "bidirectional"))
      (node (ref "D599") (pin "2") (pinfunction "C2_2") (pintype "bidirectional"))
      (node (ref "D600") (pin "2") (pinfunction "C2_2") (pintype "bidirectional"))
      (node (ref "D601") (pin "2") (pinfunction "C2_2") (pintype "bidirectional"))
      (node (ref "D602") (pin "2") (pinfunction "C2_2") (pintype "bidirectional"))
      (node (ref "D603") (pin "2") (pinfunction "C2_2") (pintype "bidirectional"))
      (node (ref "D604") (pin "2") (pinfunction "C2_2") (pintype "bidirectional"))
      (node (ref "D605") (pin "2") (pinfunction "C2_2") (pintype "bidirectional"))
      (node (ref "D606") (pin "2") (pinfunction "C2_2") (pintype "bidirectional"))
      (node (ref "D607") (pin "2") (pinfunction "C2_2") (pintype "bidirectional"))
      (node (ref "D608") (pin "2") (pinfunction "C2_2") (pintype "bidirectional"))
      (node (ref "IC13") (pin "16") (pinfunction "O3_16") (pintype "open_collector"))
    )
    (net (code "1250") (name "ROW20_SINK") (class "Default")
      (node (ref "D609") (pin "1") (pinfunction "A1_1") (pintype "bidirectional"))
      (node (ref "D610") (pin "1") (pinfunction "A1_1") (pintype "bidirectional"))
      (node (ref "D611") (pin "1") (pinfunction "A1_1") (pintype "bidirectional"))
      (node (ref "D612") (pin "1") (pinfunction "A1_1") (pintype "bidirectional"))
      (node (ref "D613") (pin "1") (pinfunction "A1_1") (pintype "bidirectional"))
      (node (ref "D614") (pin "1") (pinfunction "A1_1") (pintype "bidirectional"))
      (node (ref "D615") (pin "1") (pinfunction "A1_1") (pintype "bidirectional"))
      (node (ref "D616") (pin "1") (pinfunction "A1_1") (pintype "bidirectional"))
      (node (ref "D617") (pin "1") (pinfunction "A1_1") (pintype "bidirectional"))
      (node (ref "D618") (pin "1") (pinfunction "A1_1") (pintype "bidirectional"))
      (node (ref "D619") (pin "1") (pinfunction "A1_1") (pintype "bidirectional"))
      (node (ref "D620") (pin "1") (pinfunction "A1_1") (pintype "bidirectional"))
      (node (ref "D621") (pin "1") (pinfunction "A1_1") (pintype "bidirectional"))
      (node (ref "D622") (pin "1") (pinfunction "A1_1") (pintype "bidirectional"))
      (node (ref "D623") (pin "1") (pinfunction "A1_1") (pintype "bidirectional"))
      (node (ref "D624") (pin "1") (pinfunction "A1_1") (pintype "bidirectional"))
      (node (ref "D625") (pin "1") (pinfunction "A1_1") (pintype "bidirectional"))
      (node (ref "D626") (pin "1") (pinfunction "A1_1") (pintype "bidirectional"))
      (node (ref "D627") (pin "1") (pinfunction "A1_1") (pintype "bidirectional"))
      (node (ref "D628") (pin "1") (pinfunction "A1_1") (pintype "bidirectional"))
      (node (ref "D629") (pin "1") (pinfunction "A1_1") (pintype "bidirectional"))
      (node (ref "D630") (pin "1") (pinfunction "A1_1") (pintype "bidirectional"))
      (node (ref "D631") (pin "1") (pinfunction "A1_1") (pintype "bidirectional"))
      (node (ref "D632") (pin "1") (pinfunction "A1_1") (pintype "bidirectional"))
      (node (ref "D633") (pin "1") (pinfunction "A1_1") (pintype "bidirectional"))
      (node (ref "D634") (pin "1") (pinfunction "A1_1") (pintype "bidirectional"))
      (node (ref "D635") (pin "1") (pinfunction "A1_1") (pintype "bidirectional"))
      (node (ref "D636") (pin "1") (pinfunction "A1_1") (pintype "bidirectional"))
      (node (ref "D637") (pin "1") (pinfunction "A1_1") (pintype "bidirectional"))
      (node (ref "D638") (pin "1") (pinfunction "A1_1") (pintype "bidirectional"))
      (node (ref "D639") (pin "1") (pinfunction "A1_1") (pintype "bidirectional"))
      (node (ref "D640") (pin "1") (pinfunction "A1_1") (pintype "bidirectional"))
      (node (ref "IC12") (pin "15") (pinfunction "O4_15") (pintype "open_collector"))
    )
    (net (code "1251") (name "ROW20_SOURCE") (class "Default")
      (node (ref "D609") (pin "2") (pinfunction "C2_2") (pintype "bidirectional"))
      (node (ref "D610") (pin "2") (pinfunction "C2_2") (pintype "bidirectional"))
      (node (ref "D611") (pin "2") (pinfunction "C2_2") (pintype "bidirectional"))
      (node (ref "D612") (pin "2") (pinfunction "C2_2") (pintype "bidirectional"))
      (node (ref "D613") (pin "2") (pinfunction "C2_2") (pintype "bidirectional"))
      (node (ref "D614") (pin "2") (pinfunction "C2_2") (pintype "bidirectional"))
      (node (ref "D615") (pin "2") (pinfunction "C2_2") (pintype "bidirectional"))
      (node (ref "D616") (pin "2") (pinfunction "C2_2") (pintype "bidirectional"))
      (node (ref "D617") (pin "2") (pinfunction "C2_2") (pintype "bidirectional"))
      (node (ref "D618") (pin "2") (pinfunction "C2_2") (pintype "bidirectional"))
      (node (ref "D619") (pin "2") (pinfunction "C2_2") (pintype "bidirectional"))
      (node (ref "D620") (pin "2") (pinfunction "C2_2") (pintype "bidirectional"))
      (node (ref "D621") (pin "2") (pinfunction "C2_2") (pintype "bidirectional"))
      (node (ref "D622") (pin "2") (pinfunction "C2_2") (pintype "bidirectional"))
      (node (ref "D623") (pin "2") (pinfunction "C2_2") (pintype "bidirectional"))
      (node (ref "D624") (pin "2") (pinfunction "C2_2") (pintype "bidirectional"))
      (node (ref "D625") (pin "2") (pinfunction "C2_2") (pintype "bidirectional"))
      (node (ref "D626") (pin "2") (pinfunction "C2_2") (pintype "bidirectional"))
      (node (ref "D627") (pin "2") (pinfunction "C2_2") (pintype "bidirectional"))
      (node (ref "D628") (pin "2") (pinfunction "C2_2") (pintype "bidirectional"))
      (node (ref "D629") (pin "2") (pinfunction "C2_2") (pintype "bidirectional"))
      (node (ref "D630") (pin "2") (pinfunction "C2_2") (pintype "bidirectional"))
      (node (ref "D631") (pin "2") (pinfunction "C2_2") (pintype "bidirectional"))
      (node (ref "D632") (pin "2") (pinfunction "C2_2") (pintype "bidirectional"))
      (node (ref "D633") (pin "2") (pinfunction "C2_2") (pintype "bidirectional"))
      (node (ref "D634") (pin "2") (pinfunction "C2_2") (pintype "bidirectional"))
      (node (ref "D635") (pin "2") (pinfunction "C2_2") (pintype "bidirectional"))
      (node (ref "D636") (pin "2") (pinfunction "C2_2") (pintype "bidirectional"))
      (node (ref "D637") (pin "2") (pinfunction "C2_2") (pintype "bidirectional"))
      (node (ref "D638") (pin "2") (pinfunction "C2_2") (pintype "bidirectional"))
      (node (ref "D639") (pin "2") (pinfunction "C2_2") (pintype "bidirectional"))
      (node (ref "D640") (pin "2") (pinfunction "C2_2") (pintype "bidirectional"))
      (node (ref "IC13") (pin "15") (pinfunction "O4_15") (pintype "open_collector"))
    )
    (net (code "1252") (name "ROW21_SINK") (class "Default")
      (node (ref "D641") (pin "1") (pinfunction "A1_1") (pintype "bidirectional"))
      (node (ref "D642") (pin "1") (pinfunction "A1_1") (pintype "bidirectional"))
      (node (ref "D643") (pin "1") (pinfunction "A1_1") (pintype "bidirectional"))
      (node (ref "D644") (pin "1") (pinfunction "A1_1") (pintype "bidirectional"))
      (node (ref "D645") (pin "1") (pinfunction "A1_1") (pintype "bidirectional"))
      (node (ref "D646") (pin "1") (pinfunction "A1_1") (pintype "bidirectional"))
      (node (ref "D647") (pin "1") (pinfunction "A1_1") (pintype "bidirectional"))
      (node (ref "D648") (pin "1") (pinfunction "A1_1") (pintype "bidirectional"))
      (node (ref "D649") (pin "1") (pinfunction "A1_1") (pintype "bidirectional"))
      (node (ref "D650") (pin "1") (pinfunction "A1_1") (pintype "bidirectional"))
      (node (ref "D651") (pin "1") (pinfunction "A1_1") (pintype "bidirectional"))
      (node (ref "D652") (pin "1") (pinfunction "A1_1") (pintype "bidirectional"))
      (node (ref "D653") (pin "1") (pinfunction "A1_1") (pintype "bidirectional"))
      (node (ref "D654") (pin "1") (pinfunction "A1_1") (pintype "bidirectional"))
      (node (ref "D655") (pin "1") (pinfunction "A1_1") (pintype "bidirectional"))
      (node (ref "D656") (pin "1") (pinfunction "A1_1") (pintype "bidirectional"))
      (node (ref "D657") (pin "1") (pinfunction "A1_1") (pintype "bidirectional"))
      (node (ref "D658") (pin "1") (pinfunction "A1_1") (pintype "bidirectional"))
      (node (ref "D659") (pin "1") (pinfunction "A1_1") (pintype "bidirectional"))
      (node (ref "D660") (pin "1") (pinfunction "A1_1") (pintype "bidirectional"))
      (node (ref "D661") (pin "1") (pinfunction "A1_1") (pintype "bidirectional"))
      (node (ref "D662") (pin "1") (pinfunction "A1_1") (pintype "bidirectional"))
      (node (ref "D663") (pin "1") (pinfunction "A1_1") (pintype "bidirectional"))
      (node (ref "D664") (pin "1") (pinfunction "A1_1") (pintype "bidirectional"))
      (node (ref "D665") (pin "1") (pinfunction "A1_1") (pintype "bidirectional"))
      (node (ref "D666") (pin "1") (pinfunction "A1_1") (pintype "bidirectional"))
      (node (ref "D667") (pin "1") (pinfunction "A1_1") (pintype "bidirectional"))
      (node (ref "D668") (pin "1") (pinfunction "A1_1") (pintype "bidirectional"))
      (node (ref "D669") (pin "1") (pinfunction "A1_1") (pintype "bidirectional"))
      (node (ref "D670") (pin "1") (pinfunction "A1_1") (pintype "bidirectional"))
      (node (ref "D671") (pin "1") (pinfunction "A1_1") (pintype "bidirectional"))
      (node (ref "D672") (pin "1") (pinfunction "A1_1") (pintype "bidirectional"))
      (node (ref "IC12") (pin "14") (pinfunction "O5_14") (pintype "open_collector"))
    )
    (net (code "1253") (name "ROW21_SOURCE") (class "Default")
      (node (ref "D641") (pin "2") (pinfunction "C2_2") (pintype "bidirectional"))
      (node (ref "D642") (pin "2") (pinfunction "C2_2") (pintype "bidirectional"))
      (node (ref "D643") (pin "2") (pinfunction "C2_2") (pintype "bidirectional"))
      (node (ref "D644") (pin "2") (pinfunction "C2_2") (pintype "bidirectional"))
      (node (ref "D645") (pin "2") (pinfunction "C2_2") (pintype "bidirectional"))
      (node (ref "D646") (pin "2") (pinfunction "C2_2") (pintype "bidirectional"))
      (node (ref "D647") (pin "2") (pinfunction "C2_2") (pintype "bidirectional"))
      (node (ref "D648") (pin "2") (pinfunction "C2_2") (pintype "bidirectional"))
      (node (ref "D649") (pin "2") (pinfunction "C2_2") (pintype "bidirectional"))
      (node (ref "D650") (pin "2") (pinfunction "C2_2") (pintype "bidirectional"))
      (node (ref "D651") (pin "2") (pinfunction "C2_2") (pintype "bidirectional"))
      (node (ref "D652") (pin "2") (pinfunction "C2_2") (pintype "bidirectional"))
      (node (ref "D653") (pin "2") (pinfunction "C2_2") (pintype "bidirectional"))
      (node (ref "D654") (pin "2") (pinfunction "C2_2") (pintype "bidirectional"))
      (node (ref "D655") (pin "2") (pinfunction "C2_2") (pintype "bidirectional"))
      (node (ref "D656") (pin "2") (pinfunction "C2_2") (pintype "bidirectional"))
      (node (ref "D657") (pin "2") (pinfunction "C2_2") (pintype "bidirectional"))
      (node (ref "D658") (pin "2") (pinfunction "C2_2") (pintype "bidirectional"))
      (node (ref "D659") (pin "2") (pinfunction "C2_2") (pintype "bidirectional"))
      (node (ref "D660") (pin "2") (pinfunction "C2_2") (pintype "bidirectional"))
      (node (ref "D661") (pin "2") (pinfunction "C2_2") (pintype "bidirectional"))
      (node (ref "D662") (pin "2") (pinfunction "C2_2") (pintype "bidirectional"))
      (node (ref "D663") (pin "2") (pinfunction "C2_2") (pintype "bidirectional"))
      (node (ref "D664") (pin "2") (pinfunction "C2_2") (pintype "bidirectional"))
      (node (ref "D665") (pin "2") (pinfunction "C2_2") (pintype "bidirectional"))
      (node (ref "D666") (pin "2") (pinfunction "C2_2") (pintype "bidirectional"))
      (node (ref "D667") (pin "2") (pinfunction "C2_2") (pintype "bidirectional"))
      (node (ref "D668") (pin "2") (pinfunction "C2_2") (pintype "bidirectional"))
      (node (ref "D669") (pin "2") (pinfunction "C2_2") (pintype "bidirectional"))
      (node (ref "D670") (pin "2") (pinfunction "C2_2") (pintype "bidirectional"))
      (node (ref "D671") (pin "2") (pinfunction "C2_2") (pintype "bidirectional"))
      (node (ref "D672") (pin "2") (pinfunction "C2_2") (pintype "bidirectional"))
      (node (ref "IC13") (pin "14") (pinfunction "O5_14") (pintype "open_collector"))
    )
    (net (code "1254") (name "ROW22_SINK") (class "Default")
      (node (ref "D673") (pin "1") (pinfunction "A1_1") (pintype "bidirectional"))
      (node (ref "D674") (pin "1") (pinfunction "A1_1") (pintype "bidirectional"))
      (node (ref "D675") (pin "1") (pinfunction "A1_1") (pintype "bidirectional"))
      (node (ref "D676") (pin "1") (pinfunction "A1_1") (pintype "bidirectional"))
      (node (ref "D677") (pin "1") (pinfunction "A1_1") (pintype "bidirectional"))
      (node (ref "D678") (pin "1") (pinfunction "A1_1") (pintype "bidirectional"))
      (node (ref "D679") (pin "1") (pinfunction "A1_1") (pintype "bidirectional"))
      (node (ref "D680") (pin "1") (pinfunction "A1_1") (pintype "bidirectional"))
      (node (ref "D681") (pin "1") (pinfunction "A1_1") (pintype "bidirectional"))
      (node (ref "D682") (pin "1") (pinfunction "A1_1") (pintype "bidirectional"))
      (node (ref "D683") (pin "1") (pinfunction "A1_1") (pintype "bidirectional"))
      (node (ref "D684") (pin "1") (pinfunction "A1_1") (pintype "bidirectional"))
      (node (ref "D685") (pin "1") (pinfunction "A1_1") (pintype "bidirectional"))
      (node (ref "D686") (pin "1") (pinfunction "A1_1") (pintype "bidirectional"))
      (node (ref "D687") (pin "1") (pinfunction "A1_1") (pintype "bidirectional"))
      (node (ref "D688") (pin "1") (pinfunction "A1_1") (pintype "bidirectional"))
      (node (ref "D689") (pin "1") (pinfunction "A1_1") (pintype "bidirectional"))
      (node (ref "D690") (pin "1") (pinfunction "A1_1") (pintype "bidirectional"))
      (node (ref "D691") (pin "1") (pinfunction "A1_1") (pintype "bidirectional"))
      (node (ref "D692") (pin "1") (pinfunction "A1_1") (pintype "bidirectional"))
      (node (ref "D693") (pin "1") (pinfunction "A1_1") (pintype "bidirectional"))
      (node (ref "D694") (pin "1") (pinfunction "A1_1") (pintype "bidirectional"))
      (node (ref "D695") (pin "1") (pinfunction "A1_1") (pintype "bidirectional"))
      (node (ref "D696") (pin "1") (pinfunction "A1_1") (pintype "bidirectional"))
      (node (ref "D697") (pin "1") (pinfunction "A1_1") (pintype "bidirectional"))
      (node (ref "D698") (pin "1") (pinfunction "A1_1") (pintype "bidirectional"))
      (node (ref "D699") (pin "1") (pinfunction "A1_1") (pintype "bidirectional"))
      (node (ref "D700") (pin "1") (pinfunction "A1_1") (pintype "bidirectional"))
      (node (ref "D701") (pin "1") (pinfunction "A1_1") (pintype "bidirectional"))
      (node (ref "D702") (pin "1") (pinfunction "A1_1") (pintype "bidirectional"))
      (node (ref "D703") (pin "1") (pinfunction "A1_1") (pintype "bidirectional"))
      (node (ref "D704") (pin "1") (pinfunction "A1_1") (pintype "bidirectional"))
      (node (ref "IC12") (pin "13") (pinfunction "O6_13") (pintype "open_collector"))
    )
    (net (code "1255") (name "ROW22_SOURCE") (class "Default")
      (node (ref "D673") (pin "2") (pinfunction "C2_2") (pintype "bidirectional"))
      (node (ref "D674") (pin "2") (pinfunction "C2_2") (pintype "bidirectional"))
      (node (ref "D675") (pin "2") (pinfunction "C2_2") (pintype "bidirectional"))
      (node (ref "D676") (pin "2") (pinfunction "C2_2") (pintype "bidirectional"))
      (node (ref "D677") (pin "2") (pinfunction "C2_2") (pintype "bidirectional"))
      (node (ref "D678") (pin "2") (pinfunction "C2_2") (pintype "bidirectional"))
      (node (ref "D679") (pin "2") (pinfunction "C2_2") (pintype "bidirectional"))
      (node (ref "D680") (pin "2") (pinfunction "C2_2") (pintype "bidirectional"))
      (node (ref "D681") (pin "2") (pinfunction "C2_2") (pintype "bidirectional"))
      (node (ref "D682") (pin "2") (pinfunction "C2_2") (pintype "bidirectional"))
      (node (ref "D683") (pin "2") (pinfunction "C2_2") (pintype "bidirectional"))
      (node (ref "D684") (pin "2") (pinfunction "C2_2") (pintype "bidirectional"))
      (node (ref "D685") (pin "2") (pinfunction "C2_2") (pintype "bidirectional"))
      (node (ref "D686") (pin "2") (pinfunction "C2_2") (pintype "bidirectional"))
      (node (ref "D687") (pin "2") (pinfunction "C2_2") (pintype "bidirectional"))
      (node (ref "D688") (pin "2") (pinfunction "C2_2") (pintype "bidirectional"))
      (node (ref "D689") (pin "2") (pinfunction "C2_2") (pintype "bidirectional"))
      (node (ref "D690") (pin "2") (pinfunction "C2_2") (pintype "bidirectional"))
      (node (ref "D691") (pin "2") (pinfunction "C2_2") (pintype "bidirectional"))
      (node (ref "D692") (pin "2") (pinfunction "C2_2") (pintype "bidirectional"))
      (node (ref "D693") (pin "2") (pinfunction "C2_2") (pintype "bidirectional"))
      (node (ref "D694") (pin "2") (pinfunction "C2_2") (pintype "bidirectional"))
      (node (ref "D695") (pin "2") (pinfunction "C2_2") (pintype "bidirectional"))
      (node (ref "D696") (pin "2") (pinfunction "C2_2") (pintype "bidirectional"))
      (node (ref "D697") (pin "2") (pinfunction "C2_2") (pintype "bidirectional"))
      (node (ref "D698") (pin "2") (pinfunction "C2_2") (pintype "bidirectional"))
      (node (ref "D699") (pin "2") (pinfunction "C2_2") (pintype "bidirectional"))
      (node (ref "D700") (pin "2") (pinfunction "C2_2") (pintype "bidirectional"))
      (node (ref "D701") (pin "2") (pinfunction "C2_2") (pintype "bidirectional"))
      (node (ref "D702") (pin "2") (pinfunction "C2_2") (pintype "bidirectional"))
      (node (ref "D703") (pin "2") (pinfunction "C2_2") (pintype "bidirectional"))
      (node (ref "D704") (pin "2") (pinfunction "C2_2") (pintype "bidirectional"))
      (node (ref "IC13") (pin "13") (pinfunction "O6_13") (pintype "open_collector"))
    )
    (net (code "1256") (name "ROW23_SINK") (class "Default")
      (node (ref "D705") (pin "1") (pinfunction "A1_1") (pintype "bidirectional"))
      (node (ref "D706") (pin "1") (pinfunction "A1_1") (pintype "bidirectional"))
      (node (ref "D707") (pin "1") (pinfunction "A1_1") (pintype "bidirectional"))
      (node (ref "D708") (pin "1") (pinfunction "A1_1") (pintype "bidirectional"))
      (node (ref "D709") (pin "1") (pinfunction "A1_1") (pintype "bidirectional"))
      (node (ref "D710") (pin "1") (pinfunction "A1_1") (pintype "bidirectional"))
      (node (ref "D711") (pin "1") (pinfunction "A1_1") (pintype "bidirectional"))
      (node (ref "D712") (pin "1") (pinfunction "A1_1") (pintype "bidirectional"))
      (node (ref "D713") (pin "1") (pinfunction "A1_1") (pintype "bidirectional"))
      (node (ref "D714") (pin "1") (pinfunction "A1_1") (pintype "bidirectional"))
      (node (ref "D715") (pin "1") (pinfunction "A1_1") (pintype "bidirectional"))
      (node (ref "D716") (pin "1") (pinfunction "A1_1") (pintype "bidirectional"))
      (node (ref "D717") (pin "1") (pinfunction "A1_1") (pintype "bidirectional"))
      (node (ref "D718") (pin "1") (pinfunction "A1_1") (pintype "bidirectional"))
      (node (ref "D719") (pin "1") (pinfunction "A1_1") (pintype "bidirectional"))
      (node (ref "D720") (pin "1") (pinfunction "A1_1") (pintype "bidirectional"))
      (node (ref "D721") (pin "1") (pinfunction "A1_1") (pintype "bidirectional"))
      (node (ref "D722") (pin "1") (pinfunction "A1_1") (pintype "bidirectional"))
      (node (ref "D723") (pin "1") (pinfunction "A1_1") (pintype "bidirectional"))
      (node (ref "D724") (pin "1") (pinfunction "A1_1") (pintype "bidirectional"))
      (node (ref "D725") (pin "1") (pinfunction "A1_1") (pintype "bidirectional"))
      (node (ref "D726") (pin "1") (pinfunction "A1_1") (pintype "bidirectional"))
      (node (ref "D727") (pin "1") (pinfunction "A1_1") (pintype "bidirectional"))
      (node (ref "D728") (pin "1") (pinfunction "A1_1") (pintype "bidirectional"))
      (node (ref "D729") (pin "1") (pinfunction "A1_1") (pintype "bidirectional"))
      (node (ref "D730") (pin "1") (pinfunction "A1_1") (pintype "bidirectional"))
      (node (ref "D731") (pin "1") (pinfunction "A1_1") (pintype "bidirectional"))
      (node (ref "D732") (pin "1") (pinfunction "A1_1") (pintype "bidirectional"))
      (node (ref "D733") (pin "1") (pinfunction "A1_1") (pintype "bidirectional"))
      (node (ref "D734") (pin "1") (pinfunction "A1_1") (pintype "bidirectional"))
      (node (ref "D735") (pin "1") (pinfunction "A1_1") (pintype "bidirectional"))
      (node (ref "D736") (pin "1") (pinfunction "A1_1") (pintype "bidirectional"))
      (node (ref "IC12") (pin "12") (pinfunction "O7_12") (pintype "open_collector"))
    )
    (net (code "1257") (name "ROW23_SOURCE") (class "Default")
      (node (ref "D705") (pin "2") (pinfunction "C2_2") (pintype "bidirectional"))
      (node (ref "D706") (pin "2") (pinfunction "C2_2") (pintype "bidirectional"))
      (node (ref "D707") (pin "2") (pinfunction "C2_2") (pintype "bidirectional"))
      (node (ref "D708") (pin "2") (pinfunction "C2_2") (pintype "bidirectional"))
      (node (ref "D709") (pin "2") (pinfunction "C2_2") (pintype "bidirectional"))
      (node (ref "D710") (pin "2") (pinfunction "C2_2") (pintype "bidirectional"))
      (node (ref "D711") (pin "2") (pinfunction "C2_2") (pintype "bidirectional"))
      (node (ref "D712") (pin "2") (pinfunction "C2_2") (pintype "bidirectional"))
      (node (ref "D713") (pin "2") (pinfunction "C2_2") (pintype "bidirectional"))
      (node (ref "D714") (pin "2") (pinfunction "C2_2") (pintype "bidirectional"))
      (node (ref "D715") (pin "2") (pinfunction "C2_2") (pintype "bidirectional"))
      (node (ref "D716") (pin "2") (pinfunction "C2_2") (pintype "bidirectional"))
      (node (ref "D717") (pin "2") (pinfunction "C2_2") (pintype "bidirectional"))
      (node (ref "D718") (pin "2") (pinfunction "C2_2") (pintype "bidirectional"))
      (node (ref "D719") (pin "2") (pinfunction "C2_2") (pintype "bidirectional"))
      (node (ref "D720") (pin "2") (pinfunction "C2_2") (pintype "bidirectional"))
      (node (ref "D721") (pin "2") (pinfunction "C2_2") (pintype "bidirectional"))
      (node (ref "D722") (pin "2") (pinfunction "C2_2") (pintype "bidirectional"))
      (node (ref "D723") (pin "2") (pinfunction "C2_2") (pintype "bidirectional"))
      (node (ref "D724") (pin "2") (pinfunction "C2_2") (pintype "bidirectional"))
      (node (ref "D725") (pin "2") (pinfunction "C2_2") (pintype "bidirectional"))
      (node (ref "D726") (pin "2") (pinfunction "C2_2") (pintype "bidirectional"))
      (node (ref "D727") (pin "2") (pinfunction "C2_2") (pintype "bidirectional"))
      (node (ref "D728") (pin "2") (pinfunction "C2_2") (pintype "bidirectional"))
      (node (ref "D729") (pin "2") (pinfunction "C2_2") (pintype "bidirectional"))
      (node (ref "D730") (pin "2") (pinfunction "C2_2") (pintype "bidirectional"))
      (node (ref "D731") (pin "2") (pinfunction "C2_2") (pintype "bidirectional"))
      (node (ref "D732") (pin "2") (pinfunction "C2_2") (pintype "bidirectional"))
      (node (ref "D733") (pin "2") (pinfunction "C2_2") (pintype "bidirectional"))
      (node (ref "D734") (pin "2") (pinfunction "C2_2") (pintype "bidirectional"))
      (node (ref "D735") (pin "2") (pinfunction "C2_2") (pintype "bidirectional"))
      (node (ref "D736") (pin "2") (pinfunction "C2_2") (pintype "bidirectional"))
      (node (ref "IC13") (pin "12") (pinfunction "O7_12") (pintype "open_collector"))
    )
    (net (code "1258") (name "ROW24_SINK") (class "Default")
      (node (ref "D737") (pin "1") (pinfunction "A1_1") (pintype "bidirectional"))
      (node (ref "D738") (pin "1") (pinfunction "A1_1") (pintype "bidirectional"))
      (node (ref "D739") (pin "1") (pinfunction "A1_1") (pintype "bidirectional"))
      (node (ref "D740") (pin "1") (pinfunction "A1_1") (pintype "bidirectional"))
      (node (ref "D741") (pin "1") (pinfunction "A1_1") (pintype "bidirectional"))
      (node (ref "D742") (pin "1") (pinfunction "A1_1") (pintype "bidirectional"))
      (node (ref "D743") (pin "1") (pinfunction "A1_1") (pintype "bidirectional"))
      (node (ref "D744") (pin "1") (pinfunction "A1_1") (pintype "bidirectional"))
      (node (ref "D745") (pin "1") (pinfunction "A1_1") (pintype "bidirectional"))
      (node (ref "D746") (pin "1") (pinfunction "A1_1") (pintype "bidirectional"))
      (node (ref "D747") (pin "1") (pinfunction "A1_1") (pintype "bidirectional"))
      (node (ref "D748") (pin "1") (pinfunction "A1_1") (pintype "bidirectional"))
      (node (ref "D749") (pin "1") (pinfunction "A1_1") (pintype "bidirectional"))
      (node (ref "D750") (pin "1") (pinfunction "A1_1") (pintype "bidirectional"))
      (node (ref "D751") (pin "1") (pinfunction "A1_1") (pintype "bidirectional"))
      (node (ref "D752") (pin "1") (pinfunction "A1_1") (pintype "bidirectional"))
      (node (ref "D753") (pin "1") (pinfunction "A1_1") (pintype "bidirectional"))
      (node (ref "D754") (pin "1") (pinfunction "A1_1") (pintype "bidirectional"))
      (node (ref "D755") (pin "1") (pinfunction "A1_1") (pintype "bidirectional"))
      (node (ref "D756") (pin "1") (pinfunction "A1_1") (pintype "bidirectional"))
      (node (ref "D757") (pin "1") (pinfunction "A1_1") (pintype "bidirectional"))
      (node (ref "D758") (pin "1") (pinfunction "A1_1") (pintype "bidirectional"))
      (node (ref "D759") (pin "1") (pinfunction "A1_1") (pintype "bidirectional"))
      (node (ref "D760") (pin "1") (pinfunction "A1_1") (pintype "bidirectional"))
      (node (ref "D761") (pin "1") (pinfunction "A1_1") (pintype "bidirectional"))
      (node (ref "D762") (pin "1") (pinfunction "A1_1") (pintype "bidirectional"))
      (node (ref "D763") (pin "1") (pinfunction "A1_1") (pintype "bidirectional"))
      (node (ref "D764") (pin "1") (pinfunction "A1_1") (pintype "bidirectional"))
      (node (ref "D765") (pin "1") (pinfunction "A1_1") (pintype "bidirectional"))
      (node (ref "D766") (pin "1") (pinfunction "A1_1") (pintype "bidirectional"))
      (node (ref "D767") (pin "1") (pinfunction "A1_1") (pintype "bidirectional"))
      (node (ref "D768") (pin "1") (pinfunction "A1_1") (pintype "bidirectional"))
      (node (ref "IC12") (pin "11") (pinfunction "O8_11") (pintype "open_collector"))
    )
    (net (code "1259") (name "ROW24_SOURCE") (class "Default")
      (node (ref "D737") (pin "2") (pinfunction "C2_2") (pintype "bidirectional"))
      (node (ref "D738") (pin "2") (pinfunction "C2_2") (pintype "bidirectional"))
      (node (ref "D739") (pin "2") (pinfunction "C2_2") (pintype "bidirectional"))
      (node (ref "D740") (pin "2") (pinfunction "C2_2") (pintype "bidirectional"))
      (node (ref "D741") (pin "2") (pinfunction "C2_2") (pintype "bidirectional"))
      (node (ref "D742") (pin "2") (pinfunction "C2_2") (pintype "bidirectional"))
      (node (ref "D743") (pin "2") (pinfunction "C2_2") (pintype "bidirectional"))
      (node (ref "D744") (pin "2") (pinfunction "C2_2") (pintype "bidirectional"))
      (node (ref "D745") (pin "2") (pinfunction "C2_2") (pintype "bidirectional"))
      (node (ref "D746") (pin "2") (pinfunction "C2_2") (pintype "bidirectional"))
      (node (ref "D747") (pin "2") (pinfunction "C2_2") (pintype "bidirectional"))
      (node (ref "D748") (pin "2") (pinfunction "C2_2") (pintype "bidirectional"))
      (node (ref "D749") (pin "2") (pinfunction "C2_2") (pintype "bidirectional"))
      (node (ref "D750") (pin "2") (pinfunction "C2_2") (pintype "bidirectional"))
      (node (ref "D751") (pin "2") (pinfunction "C2_2") (pintype "bidirectional"))
      (node (ref "D752") (pin "2") (pinfunction "C2_2") (pintype "bidirectional"))
      (node (ref "D753") (pin "2") (pinfunction "C2_2") (pintype "bidirectional"))
      (node (ref "D754") (pin "2") (pinfunction "C2_2") (pintype "bidirectional"))
      (node (ref "D755") (pin "2") (pinfunction "C2_2") (pintype "bidirectional"))
      (node (ref "D756") (pin "2") (pinfunction "C2_2") (pintype "bidirectional"))
      (node (ref "D757") (pin "2") (pinfunction "C2_2") (pintype "bidirectional"))
      (node (ref "D758") (pin "2") (pinfunction "C2_2") (pintype "bidirectional"))
      (node (ref "D759") (pin "2") (pinfunction "C2_2") (pintype "bidirectional"))
      (node (ref "D760") (pin "2") (pinfunction "C2_2") (pintype "bidirectional"))
      (node (ref "D761") (pin "2") (pinfunction "C2_2") (pintype "bidirectional"))
      (node (ref "D762") (pin "2") (pinfunction "C2_2") (pintype "bidirectional"))
      (node (ref "D763") (pin "2") (pinfunction "C2_2") (pintype "bidirectional"))
      (node (ref "D764") (pin "2") (pinfunction "C2_2") (pintype "bidirectional"))
      (node (ref "D765") (pin "2") (pinfunction "C2_2") (pintype "bidirectional"))
      (node (ref "D766") (pin "2") (pinfunction "C2_2") (pintype "bidirectional"))
      (node (ref "D767") (pin "2") (pinfunction "C2_2") (pintype "bidirectional"))
      (node (ref "D768") (pin "2") (pinfunction "C2_2") (pintype "bidirectional"))
      (node (ref "IC13") (pin "11") (pinfunction "O8_11") (pintype "open_collector"))
    )
    (net (code "1260") (name "ROW25-32_INHIBIT") (class "Default")
      (node (ref "IC26") (pin "23") (pinfunction "INH_23") (pintype "input"))
      (node (ref "IC3") (pin "7") (pinfunction "Y3_7") (pintype "output"))
    )
    (net (code "1261") (name "ROW25_SINK") (class "Default")
      (node (ref "D769") (pin "1") (pinfunction "A1_1") (pintype "bidirectional"))
      (node (ref "D770") (pin "1") (pinfunction "A1_1") (pintype "bidirectional"))
      (node (ref "D771") (pin "1") (pinfunction "A1_1") (pintype "bidirectional"))
      (node (ref "D772") (pin "1") (pinfunction "A1_1") (pintype "bidirectional"))
      (node (ref "D773") (pin "1") (pinfunction "A1_1") (pintype "bidirectional"))
      (node (ref "D774") (pin "1") (pinfunction "A1_1") (pintype "bidirectional"))
      (node (ref "D775") (pin "1") (pinfunction "A1_1") (pintype "bidirectional"))
      (node (ref "D776") (pin "1") (pinfunction "A1_1") (pintype "bidirectional"))
      (node (ref "D777") (pin "1") (pinfunction "A1_1") (pintype "bidirectional"))
      (node (ref "D778") (pin "1") (pinfunction "A1_1") (pintype "bidirectional"))
      (node (ref "D779") (pin "1") (pinfunction "A1_1") (pintype "bidirectional"))
      (node (ref "D780") (pin "1") (pinfunction "A1_1") (pintype "bidirectional"))
      (node (ref "D781") (pin "1") (pinfunction "A1_1") (pintype "bidirectional"))
      (node (ref "D782") (pin "1") (pinfunction "A1_1") (pintype "bidirectional"))
      (node (ref "D783") (pin "1") (pinfunction "A1_1") (pintype "bidirectional"))
      (node (ref "D784") (pin "1") (pinfunction "A1_1") (pintype "bidirectional"))
      (node (ref "D785") (pin "1") (pinfunction "A1_1") (pintype "bidirectional"))
      (node (ref "D786") (pin "1") (pinfunction "A1_1") (pintype "bidirectional"))
      (node (ref "D787") (pin "1") (pinfunction "A1_1") (pintype "bidirectional"))
      (node (ref "D788") (pin "1") (pinfunction "A1_1") (pintype "bidirectional"))
      (node (ref "D789") (pin "1") (pinfunction "A1_1") (pintype "bidirectional"))
      (node (ref "D790") (pin "1") (pinfunction "A1_1") (pintype "bidirectional"))
      (node (ref "D791") (pin "1") (pinfunction "A1_1") (pintype "bidirectional"))
      (node (ref "D792") (pin "1") (pinfunction "A1_1") (pintype "bidirectional"))
      (node (ref "D793") (pin "1") (pinfunction "A1_1") (pintype "bidirectional"))
      (node (ref "D794") (pin "1") (pinfunction "A1_1") (pintype "bidirectional"))
      (node (ref "D795") (pin "1") (pinfunction "A1_1") (pintype "bidirectional"))
      (node (ref "D796") (pin "1") (pinfunction "A1_1") (pintype "bidirectional"))
      (node (ref "D797") (pin "1") (pinfunction "A1_1") (pintype "bidirectional"))
      (node (ref "D798") (pin "1") (pinfunction "A1_1") (pintype "bidirectional"))
      (node (ref "D799") (pin "1") (pinfunction "A1_1") (pintype "bidirectional"))
      (node (ref "D800") (pin "1") (pinfunction "A1_1") (pintype "bidirectional"))
      (node (ref "IC27") (pin "18") (pinfunction "O1_18") (pintype "open_collector"))
    )
    (net (code "1262") (name "ROW25_SOURCE") (class "Default")
      (node (ref "D769") (pin "2") (pinfunction "C2_2") (pintype "bidirectional"))
      (node (ref "D770") (pin "2") (pinfunction "C2_2") (pintype "bidirectional"))
      (node (ref "D771") (pin "2") (pinfunction "C2_2") (pintype "bidirectional"))
      (node (ref "D772") (pin "2") (pinfunction "C2_2") (pintype "bidirectional"))
      (node (ref "D773") (pin "2") (pinfunction "C2_2") (pintype "bidirectional"))
      (node (ref "D774") (pin "2") (pinfunction "C2_2") (pintype "bidirectional"))
      (node (ref "D775") (pin "2") (pinfunction "C2_2") (pintype "bidirectional"))
      (node (ref "D776") (pin "2") (pinfunction "C2_2") (pintype "bidirectional"))
      (node (ref "D777") (pin "2") (pinfunction "C2_2") (pintype "bidirectional"))
      (node (ref "D778") (pin "2") (pinfunction "C2_2") (pintype "bidirectional"))
      (node (ref "D779") (pin "2") (pinfunction "C2_2") (pintype "bidirectional"))
      (node (ref "D780") (pin "2") (pinfunction "C2_2") (pintype "bidirectional"))
      (node (ref "D781") (pin "2") (pinfunction "C2_2") (pintype "bidirectional"))
      (node (ref "D782") (pin "2") (pinfunction "C2_2") (pintype "bidirectional"))
      (node (ref "D783") (pin "2") (pinfunction "C2_2") (pintype "bidirectional"))
      (node (ref "D784") (pin "2") (pinfunction "C2_2") (pintype "bidirectional"))
      (node (ref "D785") (pin "2") (pinfunction "C2_2") (pintype "bidirectional"))
      (node (ref "D786") (pin "2") (pinfunction "C2_2") (pintype "bidirectional"))
      (node (ref "D787") (pin "2") (pinfunction "C2_2") (pintype "bidirectional"))
      (node (ref "D788") (pin "2") (pinfunction "C2_2") (pintype "bidirectional"))
      (node (ref "D789") (pin "2") (pinfunction "C2_2") (pintype "bidirectional"))
      (node (ref "D790") (pin "2") (pinfunction "C2_2") (pintype "bidirectional"))
      (node (ref "D791") (pin "2") (pinfunction "C2_2") (pintype "bidirectional"))
      (node (ref "D792") (pin "2") (pinfunction "C2_2") (pintype "bidirectional"))
      (node (ref "D793") (pin "2") (pinfunction "C2_2") (pintype "bidirectional"))
      (node (ref "D794") (pin "2") (pinfunction "C2_2") (pintype "bidirectional"))
      (node (ref "D795") (pin "2") (pinfunction "C2_2") (pintype "bidirectional"))
      (node (ref "D796") (pin "2") (pinfunction "C2_2") (pintype "bidirectional"))
      (node (ref "D797") (pin "2") (pinfunction "C2_2") (pintype "bidirectional"))
      (node (ref "D798") (pin "2") (pinfunction "C2_2") (pintype "bidirectional"))
      (node (ref "D799") (pin "2") (pinfunction "C2_2") (pintype "bidirectional"))
      (node (ref "D800") (pin "2") (pinfunction "C2_2") (pintype "bidirectional"))
      (node (ref "IC28") (pin "18") (pinfunction "O1_18") (pintype "open_collector"))
    )
    (net (code "1263") (name "ROW26_SINK") (class "Default")
      (node (ref "D801") (pin "1") (pinfunction "A1_1") (pintype "bidirectional"))
      (node (ref "D802") (pin "1") (pinfunction "A1_1") (pintype "bidirectional"))
      (node (ref "D803") (pin "1") (pinfunction "A1_1") (pintype "bidirectional"))
      (node (ref "D804") (pin "1") (pinfunction "A1_1") (pintype "bidirectional"))
      (node (ref "D805") (pin "1") (pinfunction "A1_1") (pintype "bidirectional"))
      (node (ref "D806") (pin "1") (pinfunction "A1_1") (pintype "bidirectional"))
      (node (ref "D807") (pin "1") (pinfunction "A1_1") (pintype "bidirectional"))
      (node (ref "D808") (pin "1") (pinfunction "A1_1") (pintype "bidirectional"))
      (node (ref "D809") (pin "1") (pinfunction "A1_1") (pintype "bidirectional"))
      (node (ref "D810") (pin "1") (pinfunction "A1_1") (pintype "bidirectional"))
      (node (ref "D811") (pin "1") (pinfunction "A1_1") (pintype "bidirectional"))
      (node (ref "D812") (pin "1") (pinfunction "A1_1") (pintype "bidirectional"))
      (node (ref "D813") (pin "1") (pinfunction "A1_1") (pintype "bidirectional"))
      (node (ref "D814") (pin "1") (pinfunction "A1_1") (pintype "bidirectional"))
      (node (ref "D815") (pin "1") (pinfunction "A1_1") (pintype "bidirectional"))
      (node (ref "D816") (pin "1") (pinfunction "A1_1") (pintype "bidirectional"))
      (node (ref "D817") (pin "1") (pinfunction "A1_1") (pintype "bidirectional"))
      (node (ref "D818") (pin "1") (pinfunction "A1_1") (pintype "bidirectional"))
      (node (ref "D819") (pin "1") (pinfunction "A1_1") (pintype "bidirectional"))
      (node (ref "D820") (pin "1") (pinfunction "A1_1") (pintype "bidirectional"))
      (node (ref "D821") (pin "1") (pinfunction "A1_1") (pintype "bidirectional"))
      (node (ref "D822") (pin "1") (pinfunction "A1_1") (pintype "bidirectional"))
      (node (ref "D823") (pin "1") (pinfunction "A1_1") (pintype "bidirectional"))
      (node (ref "D824") (pin "1") (pinfunction "A1_1") (pintype "bidirectional"))
      (node (ref "D825") (pin "1") (pinfunction "A1_1") (pintype "bidirectional"))
      (node (ref "D826") (pin "1") (pinfunction "A1_1") (pintype "bidirectional"))
      (node (ref "D827") (pin "1") (pinfunction "A1_1") (pintype "bidirectional"))
      (node (ref "D828") (pin "1") (pinfunction "A1_1") (pintype "bidirectional"))
      (node (ref "D829") (pin "1") (pinfunction "A1_1") (pintype "bidirectional"))
      (node (ref "D830") (pin "1") (pinfunction "A1_1") (pintype "bidirectional"))
      (node (ref "D831") (pin "1") (pinfunction "A1_1") (pintype "bidirectional"))
      (node (ref "D832") (pin "1") (pinfunction "A1_1") (pintype "bidirectional"))
      (node (ref "IC27") (pin "17") (pinfunction "O2_17") (pintype "open_collector"))
    )
    (net (code "1264") (name "ROW26_SOURCE") (class "Default")
      (node (ref "D801") (pin "2") (pinfunction "C2_2") (pintype "bidirectional"))
      (node (ref "D802") (pin "2") (pinfunction "C2_2") (pintype "bidirectional"))
      (node (ref "D803") (pin "2") (pinfunction "C2_2") (pintype "bidirectional"))
      (node (ref "D804") (pin "2") (pinfunction "C2_2") (pintype "bidirectional"))
      (node (ref "D805") (pin "2") (pinfunction "C2_2") (pintype "bidirectional"))
      (node (ref "D806") (pin "2") (pinfunction "C2_2") (pintype "bidirectional"))
      (node (ref "D807") (pin "2") (pinfunction "C2_2") (pintype "bidirectional"))
      (node (ref "D808") (pin "2") (pinfunction "C2_2") (pintype "bidirectional"))
      (node (ref "D809") (pin "2") (pinfunction "C2_2") (pintype "bidirectional"))
      (node (ref "D810") (pin "2") (pinfunction "C2_2") (pintype "bidirectional"))
      (node (ref "D811") (pin "2") (pinfunction "C2_2") (pintype "bidirectional"))
      (node (ref "D812") (pin "2") (pinfunction "C2_2") (pintype "bidirectional"))
      (node (ref "D813") (pin "2") (pinfunction "C2_2") (pintype "bidirectional"))
      (node (ref "D814") (pin "2") (pinfunction "C2_2") (pintype "bidirectional"))
      (node (ref "D815") (pin "2") (pinfunction "C2_2") (pintype "bidirectional"))
      (node (ref "D816") (pin "2") (pinfunction "C2_2") (pintype "bidirectional"))
      (node (ref "D817") (pin "2") (pinfunction "C2_2") (pintype "bidirectional"))
      (node (ref "D818") (pin "2") (pinfunction "C2_2") (pintype "bidirectional"))
      (node (ref "D819") (pin "2") (pinfunction "C2_2") (pintype "bidirectional"))
      (node (ref "D820") (pin "2") (pinfunction "C2_2") (pintype "bidirectional"))
      (node (ref "D821") (pin "2") (pinfunction "C2_2") (pintype "bidirectional"))
      (node (ref "D822") (pin "2") (pinfunction "C2_2") (pintype "bidirectional"))
      (node (ref "D823") (pin "2") (pinfunction "C2_2") (pintype "bidirectional"))
      (node (ref "D824") (pin "2") (pinfunction "C2_2") (pintype "bidirectional"))
      (node (ref "D825") (pin "2") (pinfunction "C2_2") (pintype "bidirectional"))
      (node (ref "D826") (pin "2") (pinfunction "C2_2") (pintype "bidirectional"))
      (node (ref "D827") (pin "2") (pinfunction "C2_2") (pintype "bidirectional"))
      (node (ref "D828") (pin "2") (pinfunction "C2_2") (pintype "bidirectional"))
      (node (ref "D829") (pin "2") (pinfunction "C2_2") (pintype "bidirectional"))
      (node (ref "D830") (pin "2") (pinfunction "C2_2") (pintype "bidirectional"))
      (node (ref "D831") (pin "2") (pinfunction "C2_2") (pintype "bidirectional"))
      (node (ref "D832") (pin "2") (pinfunction "C2_2") (pintype "bidirectional"))
      (node (ref "IC28") (pin "17") (pinfunction "O2_17") (pintype "open_collector"))
    )
    (net (code "1265") (name "ROW27_SINK") (class "Default")
      (node (ref "D833") (pin "1") (pinfunction "A1_1") (pintype "bidirectional"))
      (node (ref "D834") (pin "1") (pinfunction "A1_1") (pintype "bidirectional"))
      (node (ref "D835") (pin "1") (pinfunction "A1_1") (pintype "bidirectional"))
      (node (ref "D836") (pin "1") (pinfunction "A1_1") (pintype "bidirectional"))
      (node (ref "D837") (pin "1") (pinfunction "A1_1") (pintype "bidirectional"))
      (node (ref "D838") (pin "1") (pinfunction "A1_1") (pintype "bidirectional"))
      (node (ref "D839") (pin "1") (pinfunction "A1_1") (pintype "bidirectional"))
      (node (ref "D840") (pin "1") (pinfunction "A1_1") (pintype "bidirectional"))
      (node (ref "D841") (pin "1") (pinfunction "A1_1") (pintype "bidirectional"))
      (node (ref "D842") (pin "1") (pinfunction "A1_1") (pintype "bidirectional"))
      (node (ref "D843") (pin "1") (pinfunction "A1_1") (pintype "bidirectional"))
      (node (ref "D844") (pin "1") (pinfunction "A1_1") (pintype "bidirectional"))
      (node (ref "D845") (pin "1") (pinfunction "A1_1") (pintype "bidirectional"))
      (node (ref "D846") (pin "1") (pinfunction "A1_1") (pintype "bidirectional"))
      (node (ref "D847") (pin "1") (pinfunction "A1_1") (pintype "bidirectional"))
      (node (ref "D848") (pin "1") (pinfunction "A1_1") (pintype "bidirectional"))
      (node (ref "D849") (pin "1") (pinfunction "A1_1") (pintype "bidirectional"))
      (node (ref "D850") (pin "1") (pinfunction "A1_1") (pintype "bidirectional"))
      (node (ref "D851") (pin "1") (pinfunction "A1_1") (pintype "bidirectional"))
      (node (ref "D852") (pin "1") (pinfunction "A1_1") (pintype "bidirectional"))
      (node (ref "D853") (pin "1") (pinfunction "A1_1") (pintype "bidirectional"))
      (node (ref "D854") (pin "1") (pinfunction "A1_1") (pintype "bidirectional"))
      (node (ref "D855") (pin "1") (pinfunction "A1_1") (pintype "bidirectional"))
      (node (ref "D856") (pin "1") (pinfunction "A1_1") (pintype "bidirectional"))
      (node (ref "D857") (pin "1") (pinfunction "A1_1") (pintype "bidirectional"))
      (node (ref "D858") (pin "1") (pinfunction "A1_1") (pintype "bidirectional"))
      (node (ref "D859") (pin "1") (pinfunction "A1_1") (pintype "bidirectional"))
      (node (ref "D860") (pin "1") (pinfunction "A1_1") (pintype "bidirectional"))
      (node (ref "D861") (pin "1") (pinfunction "A1_1") (pintype "bidirectional"))
      (node (ref "D862") (pin "1") (pinfunction "A1_1") (pintype "bidirectional"))
      (node (ref "D863") (pin "1") (pinfunction "A1_1") (pintype "bidirectional"))
      (node (ref "D864") (pin "1") (pinfunction "A1_1") (pintype "bidirectional"))
      (node (ref "IC27") (pin "16") (pinfunction "O3_16") (pintype "open_collector"))
    )
    (net (code "1266") (name "ROW27_SOURCE") (class "Default")
      (node (ref "D833") (pin "2") (pinfunction "C2_2") (pintype "bidirectional"))
      (node (ref "D834") (pin "2") (pinfunction "C2_2") (pintype "bidirectional"))
      (node (ref "D835") (pin "2") (pinfunction "C2_2") (pintype "bidirectional"))
      (node (ref "D836") (pin "2") (pinfunction "C2_2") (pintype "bidirectional"))
      (node (ref "D837") (pin "2") (pinfunction "C2_2") (pintype "bidirectional"))
      (node (ref "D838") (pin "2") (pinfunction "C2_2") (pintype "bidirectional"))
      (node (ref "D839") (pin "2") (pinfunction "C2_2") (pintype "bidirectional"))
      (node (ref "D840") (pin "2") (pinfunction "C2_2") (pintype "bidirectional"))
      (node (ref "D841") (pin "2") (pinfunction "C2_2") (pintype "bidirectional"))
      (node (ref "D842") (pin "2") (pinfunction "C2_2") (pintype "bidirectional"))
      (node (ref "D843") (pin "2") (pinfunction "C2_2") (pintype "bidirectional"))
      (node (ref "D844") (pin "2") (pinfunction "C2_2") (pintype "bidirectional"))
      (node (ref "D845") (pin "2") (pinfunction "C2_2") (pintype "bidirectional"))
      (node (ref "D846") (pin "2") (pinfunction "C2_2") (pintype "bidirectional"))
      (node (ref "D847") (pin "2") (pinfunction "C2_2") (pintype "bidirectional"))
      (node (ref "D848") (pin "2") (pinfunction "C2_2") (pintype "bidirectional"))
      (node (ref "D849") (pin "2") (pinfunction "C2_2") (pintype "bidirectional"))
      (node (ref "D850") (pin "2") (pinfunction "C2_2") (pintype "bidirectional"))
      (node (ref "D851") (pin "2") (pinfunction "C2_2") (pintype "bidirectional"))
      (node (ref "D852") (pin "2") (pinfunction "C2_2") (pintype "bidirectional"))
      (node (ref "D853") (pin "2") (pinfunction "C2_2") (pintype "bidirectional"))
      (node (ref "D854") (pin "2") (pinfunction "C2_2") (pintype "bidirectional"))
      (node (ref "D855") (pin "2") (pinfunction "C2_2") (pintype "bidirectional"))
      (node (ref "D856") (pin "2") (pinfunction "C2_2") (pintype "bidirectional"))
      (node (ref "D857") (pin "2") (pinfunction "C2_2") (pintype "bidirectional"))
      (node (ref "D858") (pin "2") (pinfunction "C2_2") (pintype "bidirectional"))
      (node (ref "D859") (pin "2") (pinfunction "C2_2") (pintype "bidirectional"))
      (node (ref "D860") (pin "2") (pinfunction "C2_2") (pintype "bidirectional"))
      (node (ref "D861") (pin "2") (pinfunction "C2_2") (pintype "bidirectional"))
      (node (ref "D862") (pin "2") (pinfunction "C2_2") (pintype "bidirectional"))
      (node (ref "D863") (pin "2") (pinfunction "C2_2") (pintype "bidirectional"))
      (node (ref "D864") (pin "2") (pinfunction "C2_2") (pintype "bidirectional"))
      (node (ref "IC28") (pin "16") (pinfunction "O3_16") (pintype "open_collector"))
    )
    (net (code "1267") (name "ROW28_SINK") (class "Default")
      (node (ref "D865") (pin "1") (pinfunction "A1_1") (pintype "bidirectional"))
      (node (ref "D866") (pin "1") (pinfunction "A1_1") (pintype "bidirectional"))
      (node (ref "D867") (pin "1") (pinfunction "A1_1") (pintype "bidirectional"))
      (node (ref "D868") (pin "1") (pinfunction "A1_1") (pintype "bidirectional"))
      (node (ref "D869") (pin "1") (pinfunction "A1_1") (pintype "bidirectional"))
      (node (ref "D870") (pin "1") (pinfunction "A1_1") (pintype "bidirectional"))
      (node (ref "D871") (pin "1") (pinfunction "A1_1") (pintype "bidirectional"))
      (node (ref "D872") (pin "1") (pinfunction "A1_1") (pintype "bidirectional"))
      (node (ref "D873") (pin "1") (pinfunction "A1_1") (pintype "bidirectional"))
      (node (ref "D874") (pin "1") (pinfunction "A1_1") (pintype "bidirectional"))
      (node (ref "D875") (pin "1") (pinfunction "A1_1") (pintype "bidirectional"))
      (node (ref "D876") (pin "1") (pinfunction "A1_1") (pintype "bidirectional"))
      (node (ref "D877") (pin "1") (pinfunction "A1_1") (pintype "bidirectional"))
      (node (ref "D878") (pin "1") (pinfunction "A1_1") (pintype "bidirectional"))
      (node (ref "D879") (pin "1") (pinfunction "A1_1") (pintype "bidirectional"))
      (node (ref "D880") (pin "1") (pinfunction "A1_1") (pintype "bidirectional"))
      (node (ref "D881") (pin "1") (pinfunction "A1_1") (pintype "bidirectional"))
      (node (ref "D882") (pin "1") (pinfunction "A1_1") (pintype "bidirectional"))
      (node (ref "D883") (pin "1") (pinfunction "A1_1") (pintype "bidirectional"))
      (node (ref "D884") (pin "1") (pinfunction "A1_1") (pintype "bidirectional"))
      (node (ref "D885") (pin "1") (pinfunction "A1_1") (pintype "bidirectional"))
      (node (ref "D886") (pin "1") (pinfunction "A1_1") (pintype "bidirectional"))
      (node (ref "D887") (pin "1") (pinfunction "A1_1") (pintype "bidirectional"))
      (node (ref "D888") (pin "1") (pinfunction "A1_1") (pintype "bidirectional"))
      (node (ref "D889") (pin "1") (pinfunction "A1_1") (pintype "bidirectional"))
      (node (ref "D890") (pin "1") (pinfunction "A1_1") (pintype "bidirectional"))
      (node (ref "D891") (pin "1") (pinfunction "A1_1") (pintype "bidirectional"))
      (node (ref "D892") (pin "1") (pinfunction "A1_1") (pintype "bidirectional"))
      (node (ref "D893") (pin "1") (pinfunction "A1_1") (pintype "bidirectional"))
      (node (ref "D894") (pin "1") (pinfunction "A1_1") (pintype "bidirectional"))
      (node (ref "D895") (pin "1") (pinfunction "A1_1") (pintype "bidirectional"))
      (node (ref "D896") (pin "1") (pinfunction "A1_1") (pintype "bidirectional"))
      (node (ref "IC27") (pin "15") (pinfunction "O4_15") (pintype "open_collector"))
    )
    (net (code "1268") (name "ROW28_SOURCE") (class "Default")
      (node (ref "D865") (pin "2") (pinfunction "C2_2") (pintype "bidirectional"))
      (node (ref "D866") (pin "2") (pinfunction "C2_2") (pintype "bidirectional"))
      (node (ref "D867") (pin "2") (pinfunction "C2_2") (pintype "bidirectional"))
      (node (ref "D868") (pin "2") (pinfunction "C2_2") (pintype "bidirectional"))
      (node (ref "D869") (pin "2") (pinfunction "C2_2") (pintype "bidirectional"))
      (node (ref "D870") (pin "2") (pinfunction "C2_2") (pintype "bidirectional"))
      (node (ref "D871") (pin "2") (pinfunction "C2_2") (pintype "bidirectional"))
      (node (ref "D872") (pin "2") (pinfunction "C2_2") (pintype "bidirectional"))
      (node (ref "D873") (pin "2") (pinfunction "C2_2") (pintype "bidirectional"))
      (node (ref "D874") (pin "2") (pinfunction "C2_2") (pintype "bidirectional"))
      (node (ref "D875") (pin "2") (pinfunction "C2_2") (pintype "bidirectional"))
      (node (ref "D876") (pin "2") (pinfunction "C2_2") (pintype "bidirectional"))
      (node (ref "D877") (pin "2") (pinfunction "C2_2") (pintype "bidirectional"))
      (node (ref "D878") (pin "2") (pinfunction "C2_2") (pintype "bidirectional"))
      (node (ref "D879") (pin "2") (pinfunction "C2_2") (pintype "bidirectional"))
      (node (ref "D880") (pin "2") (pinfunction "C2_2") (pintype "bidirectional"))
      (node (ref "D881") (pin "2") (pinfunction "C2_2") (pintype "bidirectional"))
      (node (ref "D882") (pin "2") (pinfunction "C2_2") (pintype "bidirectional"))
      (node (ref "D883") (pin "2") (pinfunction "C2_2") (pintype "bidirectional"))
      (node (ref "D884") (pin "2") (pinfunction "C2_2") (pintype "bidirectional"))
      (node (ref "D885") (pin "2") (pinfunction "C2_2") (pintype "bidirectional"))
      (node (ref "D886") (pin "2") (pinfunction "C2_2") (pintype "bidirectional"))
      (node (ref "D887") (pin "2") (pinfunction "C2_2") (pintype "bidirectional"))
      (node (ref "D888") (pin "2") (pinfunction "C2_2") (pintype "bidirectional"))
      (node (ref "D889") (pin "2") (pinfunction "C2_2") (pintype "bidirectional"))
      (node (ref "D890") (pin "2") (pinfunction "C2_2") (pintype "bidirectional"))
      (node (ref "D891") (pin "2") (pinfunction "C2_2") (pintype "bidirectional"))
      (node (ref "D892") (pin "2") (pinfunction "C2_2") (pintype "bidirectional"))
      (node (ref "D893") (pin "2") (pinfunction "C2_2") (pintype "bidirectional"))
      (node (ref "D894") (pin "2") (pinfunction "C2_2") (pintype "bidirectional"))
      (node (ref "D895") (pin "2") (pinfunction "C2_2") (pintype "bidirectional"))
      (node (ref "D896") (pin "2") (pinfunction "C2_2") (pintype "bidirectional"))
      (node (ref "IC28") (pin "15") (pinfunction "O4_15") (pintype "open_collector"))
    )
    (net (code "1269") (name "ROW29_SINK") (class "Default")
      (node (ref "D897") (pin "1") (pinfunction "A1_1") (pintype "bidirectional"))
      (node (ref "D898") (pin "1") (pinfunction "A1_1") (pintype "bidirectional"))
      (node (ref "D899") (pin "1") (pinfunction "A1_1") (pintype "bidirectional"))
      (node (ref "D900") (pin "1") (pinfunction "A1_1") (pintype "bidirectional"))
      (node (ref "D901") (pin "1") (pinfunction "A1_1") (pintype "bidirectional"))
      (node (ref "D902") (pin "1") (pinfunction "A1_1") (pintype "bidirectional"))
      (node (ref "D903") (pin "1") (pinfunction "A1_1") (pintype "bidirectional"))
      (node (ref "D904") (pin "1") (pinfunction "A1_1") (pintype "bidirectional"))
      (node (ref "D905") (pin "1") (pinfunction "A1_1") (pintype "bidirectional"))
      (node (ref "D906") (pin "1") (pinfunction "A1_1") (pintype "bidirectional"))
      (node (ref "D907") (pin "1") (pinfunction "A1_1") (pintype "bidirectional"))
      (node (ref "D908") (pin "1") (pinfunction "A1_1") (pintype "bidirectional"))
      (node (ref "D909") (pin "1") (pinfunction "A1_1") (pintype "bidirectional"))
      (node (ref "D910") (pin "1") (pinfunction "A1_1") (pintype "bidirectional"))
      (node (ref "D911") (pin "1") (pinfunction "A1_1") (pintype "bidirectional"))
      (node (ref "D912") (pin "1") (pinfunction "A1_1") (pintype "bidirectional"))
      (node (ref "D913") (pin "1") (pinfunction "A1_1") (pintype "bidirectional"))
      (node (ref "D914") (pin "1") (pinfunction "A1_1") (pintype "bidirectional"))
      (node (ref "D915") (pin "1") (pinfunction "A1_1") (pintype "bidirectional"))
      (node (ref "D916") (pin "1") (pinfunction "A1_1") (pintype "bidirectional"))
      (node (ref "D917") (pin "1") (pinfunction "A1_1") (pintype "bidirectional"))
      (node (ref "D918") (pin "1") (pinfunction "A1_1") (pintype "bidirectional"))
      (node (ref "D919") (pin "1") (pinfunction "A1_1") (pintype "bidirectional"))
      (node (ref "D920") (pin "1") (pinfunction "A1_1") (pintype "bidirectional"))
      (node (ref "D921") (pin "1") (pinfunction "A1_1") (pintype "bidirectional"))
      (node (ref "D922") (pin "1") (pinfunction "A1_1") (pintype "bidirectional"))
      (node (ref "D923") (pin "1") (pinfunction "A1_1") (pintype "bidirectional"))
      (node (ref "D924") (pin "1") (pinfunction "A1_1") (pintype "bidirectional"))
      (node (ref "D925") (pin "1") (pinfunction "A1_1") (pintype "bidirectional"))
      (node (ref "D926") (pin "1") (pinfunction "A1_1") (pintype "bidirectional"))
      (node (ref "D927") (pin "1") (pinfunction "A1_1") (pintype "bidirectional"))
      (node (ref "D928") (pin "1") (pinfunction "A1_1") (pintype "bidirectional"))
      (node (ref "IC27") (pin "14") (pinfunction "O5_14") (pintype "open_collector"))
    )
    (net (code "1270") (name "ROW29_SOURCE") (class "Default")
      (node (ref "D897") (pin "2") (pinfunction "C2_2") (pintype "bidirectional"))
      (node (ref "D898") (pin "2") (pinfunction "C2_2") (pintype "bidirectional"))
      (node (ref "D899") (pin "2") (pinfunction "C2_2") (pintype "bidirectional"))
      (node (ref "D900") (pin "2") (pinfunction "C2_2") (pintype "bidirectional"))
      (node (ref "D901") (pin "2") (pinfunction "C2_2") (pintype "bidirectional"))
      (node (ref "D902") (pin "2") (pinfunction "C2_2") (pintype "bidirectional"))
      (node (ref "D903") (pin "2") (pinfunction "C2_2") (pintype "bidirectional"))
      (node (ref "D904") (pin "2") (pinfunction "C2_2") (pintype "bidirectional"))
      (node (ref "D905") (pin "2") (pinfunction "C2_2") (pintype "bidirectional"))
      (node (ref "D906") (pin "2") (pinfunction "C2_2") (pintype "bidirectional"))
      (node (ref "D907") (pin "2") (pinfunction "C2_2") (pintype "bidirectional"))
      (node (ref "D908") (pin "2") (pinfunction "C2_2") (pintype "bidirectional"))
      (node (ref "D909") (pin "2") (pinfunction "C2_2") (pintype "bidirectional"))
      (node (ref "D910") (pin "2") (pinfunction "C2_2") (pintype "bidirectional"))
      (node (ref "D911") (pin "2") (pinfunction "C2_2") (pintype "bidirectional"))
      (node (ref "D912") (pin "2") (pinfunction "C2_2") (pintype "bidirectional"))
      (node (ref "D913") (pin "2") (pinfunction "C2_2") (pintype "bidirectional"))
      (node (ref "D914") (pin "2") (pinfunction "C2_2") (pintype "bidirectional"))
      (node (ref "D915") (pin "2") (pinfunction "C2_2") (pintype "bidirectional"))
      (node (ref "D916") (pin "2") (pinfunction "C2_2") (pintype "bidirectional"))
      (node (ref "D917") (pin "2") (pinfunction "C2_2") (pintype "bidirectional"))
      (node (ref "D918") (pin "2") (pinfunction "C2_2") (pintype "bidirectional"))
      (node (ref "D919") (pin "2") (pinfunction "C2_2") (pintype "bidirectional"))
      (node (ref "D920") (pin "2") (pinfunction "C2_2") (pintype "bidirectional"))
      (node (ref "D921") (pin "2") (pinfunction "C2_2") (pintype "bidirectional"))
      (node (ref "D922") (pin "2") (pinfunction "C2_2") (pintype "bidirectional"))
      (node (ref "D923") (pin "2") (pinfunction "C2_2") (pintype "bidirectional"))
      (node (ref "D924") (pin "2") (pinfunction "C2_2") (pintype "bidirectional"))
      (node (ref "D925") (pin "2") (pinfunction "C2_2") (pintype "bidirectional"))
      (node (ref "D926") (pin "2") (pinfunction "C2_2") (pintype "bidirectional"))
      (node (ref "D927") (pin "2") (pinfunction "C2_2") (pintype "bidirectional"))
      (node (ref "D928") (pin "2") (pinfunction "C2_2") (pintype "bidirectional"))
      (node (ref "IC28") (pin "14") (pinfunction "O5_14") (pintype "open_collector"))
    )
    (net (code "1271") (name "ROW30_SINK") (class "Default")
      (node (ref "D929") (pin "1") (pinfunction "A1_1") (pintype "bidirectional"))
      (node (ref "D930") (pin "1") (pinfunction "A1_1") (pintype "bidirectional"))
      (node (ref "D931") (pin "1") (pinfunction "A1_1") (pintype "bidirectional"))
      (node (ref "D932") (pin "1") (pinfunction "A1_1") (pintype "bidirectional"))
      (node (ref "D933") (pin "1") (pinfunction "A1_1") (pintype "bidirectional"))
      (node (ref "D934") (pin "1") (pinfunction "A1_1") (pintype "bidirectional"))
      (node (ref "D935") (pin "1") (pinfunction "A1_1") (pintype "bidirectional"))
      (node (ref "D936") (pin "1") (pinfunction "A1_1") (pintype "bidirectional"))
      (node (ref "D937") (pin "1") (pinfunction "A1_1") (pintype "bidirectional"))
      (node (ref "D938") (pin "1") (pinfunction "A1_1") (pintype "bidirectional"))
      (node (ref "D939") (pin "1") (pinfunction "A1_1") (pintype "bidirectional"))
      (node (ref "D940") (pin "1") (pinfunction "A1_1") (pintype "bidirectional"))
      (node (ref "D941") (pin "1") (pinfunction "A1_1") (pintype "bidirectional"))
      (node (ref "D942") (pin "1") (pinfunction "A1_1") (pintype "bidirectional"))
      (node (ref "D943") (pin "1") (pinfunction "A1_1") (pintype "bidirectional"))
      (node (ref "D944") (pin "1") (pinfunction "A1_1") (pintype "bidirectional"))
      (node (ref "D945") (pin "1") (pinfunction "A1_1") (pintype "bidirectional"))
      (node (ref "D946") (pin "1") (pinfunction "A1_1") (pintype "bidirectional"))
      (node (ref "D947") (pin "1") (pinfunction "A1_1") (pintype "bidirectional"))
      (node (ref "D948") (pin "1") (pinfunction "A1_1") (pintype "bidirectional"))
      (node (ref "D949") (pin "1") (pinfunction "A1_1") (pintype "bidirectional"))
      (node (ref "D950") (pin "1") (pinfunction "A1_1") (pintype "bidirectional"))
      (node (ref "D951") (pin "1") (pinfunction "A1_1") (pintype "bidirectional"))
      (node (ref "D952") (pin "1") (pinfunction "A1_1") (pintype "bidirectional"))
      (node (ref "D953") (pin "1") (pinfunction "A1_1") (pintype "bidirectional"))
      (node (ref "D954") (pin "1") (pinfunction "A1_1") (pintype "bidirectional"))
      (node (ref "D955") (pin "1") (pinfunction "A1_1") (pintype "bidirectional"))
      (node (ref "D956") (pin "1") (pinfunction "A1_1") (pintype "bidirectional"))
      (node (ref "D957") (pin "1") (pinfunction "A1_1") (pintype "bidirectional"))
      (node (ref "D958") (pin "1") (pinfunction "A1_1") (pintype "bidirectional"))
      (node (ref "D959") (pin "1") (pinfunction "A1_1") (pintype "bidirectional"))
      (node (ref "D960") (pin "1") (pinfunction "A1_1") (pintype "bidirectional"))
      (node (ref "IC27") (pin "13") (pinfunction "O6_13") (pintype "open_collector"))
    )
    (net (code "1272") (name "ROW30_SOURCE") (class "Default")
      (node (ref "D929") (pin "2") (pinfunction "C2_2") (pintype "bidirectional"))
      (node (ref "D930") (pin "2") (pinfunction "C2_2") (pintype "bidirectional"))
      (node (ref "D931") (pin "2") (pinfunction "C2_2") (pintype "bidirectional"))
      (node (ref "D932") (pin "2") (pinfunction "C2_2") (pintype "bidirectional"))
      (node (ref "D933") (pin "2") (pinfunction "C2_2") (pintype "bidirectional"))
      (node (ref "D934") (pin "2") (pinfunction "C2_2") (pintype "bidirectional"))
      (node (ref "D935") (pin "2") (pinfunction "C2_2") (pintype "bidirectional"))
      (node (ref "D936") (pin "2") (pinfunction "C2_2") (pintype "bidirectional"))
      (node (ref "D937") (pin "2") (pinfunction "C2_2") (pintype "bidirectional"))
      (node (ref "D938") (pin "2") (pinfunction "C2_2") (pintype "bidirectional"))
      (node (ref "D939") (pin "2") (pinfunction "C2_2") (pintype "bidirectional"))
      (node (ref "D940") (pin "2") (pinfunction "C2_2") (pintype "bidirectional"))
      (node (ref "D941") (pin "2") (pinfunction "C2_2") (pintype "bidirectional"))
      (node (ref "D942") (pin "2") (pinfunction "C2_2") (pintype "bidirectional"))
      (node (ref "D943") (pin "2") (pinfunction "C2_2") (pintype "bidirectional"))
      (node (ref "D944") (pin "2") (pinfunction "C2_2") (pintype "bidirectional"))
      (node (ref "D945") (pin "2") (pinfunction "C2_2") (pintype "bidirectional"))
      (node (ref "D946") (pin "2") (pinfunction "C2_2") (pintype "bidirectional"))
      (node (ref "D947") (pin "2") (pinfunction "C2_2") (pintype "bidirectional"))
      (node (ref "D948") (pin "2") (pinfunction "C2_2") (pintype "bidirectional"))
      (node (ref "D949") (pin "2") (pinfunction "C2_2") (pintype "bidirectional"))
      (node (ref "D950") (pin "2") (pinfunction "C2_2") (pintype "bidirectional"))
      (node (ref "D951") (pin "2") (pinfunction "C2_2") (pintype "bidirectional"))
      (node (ref "D952") (pin "2") (pinfunction "C2_2") (pintype "bidirectional"))
      (node (ref "D953") (pin "2") (pinfunction "C2_2") (pintype "bidirectional"))
      (node (ref "D954") (pin "2") (pinfunction "C2_2") (pintype "bidirectional"))
      (node (ref "D955") (pin "2") (pinfunction "C2_2") (pintype "bidirectional"))
      (node (ref "D956") (pin "2") (pinfunction "C2_2") (pintype "bidirectional"))
      (node (ref "D957") (pin "2") (pinfunction "C2_2") (pintype "bidirectional"))
      (node (ref "D958") (pin "2") (pinfunction "C2_2") (pintype "bidirectional"))
      (node (ref "D959") (pin "2") (pinfunction "C2_2") (pintype "bidirectional"))
      (node (ref "D960") (pin "2") (pinfunction "C2_2") (pintype "bidirectional"))
      (node (ref "IC28") (pin "13") (pinfunction "O6_13") (pintype "open_collector"))
    )
    (net (code "1273") (name "ROW31_SINK") (class "Default")
      (node (ref "D961") (pin "1") (pinfunction "A1_1") (pintype "bidirectional"))
      (node (ref "D962") (pin "1") (pinfunction "A1_1") (pintype "bidirectional"))
      (node (ref "D963") (pin "1") (pinfunction "A1_1") (pintype "bidirectional"))
      (node (ref "D964") (pin "1") (pinfunction "A1_1") (pintype "bidirectional"))
      (node (ref "D965") (pin "1") (pinfunction "A1_1") (pintype "bidirectional"))
      (node (ref "D966") (pin "1") (pinfunction "A1_1") (pintype "bidirectional"))
      (node (ref "D967") (pin "1") (pinfunction "A1_1") (pintype "bidirectional"))
      (node (ref "D968") (pin "1") (pinfunction "A1_1") (pintype "bidirectional"))
      (node (ref "D969") (pin "1") (pinfunction "A1_1") (pintype "bidirectional"))
      (node (ref "D970") (pin "1") (pinfunction "A1_1") (pintype "bidirectional"))
      (node (ref "D971") (pin "1") (pinfunction "A1_1") (pintype "bidirectional"))
      (node (ref "D972") (pin "1") (pinfunction "A1_1") (pintype "bidirectional"))
      (node (ref "D973") (pin "1") (pinfunction "A1_1") (pintype "bidirectional"))
      (node (ref "D974") (pin "1") (pinfunction "A1_1") (pintype "bidirectional"))
      (node (ref "D975") (pin "1") (pinfunction "A1_1") (pintype "bidirectional"))
      (node (ref "D976") (pin "1") (pinfunction "A1_1") (pintype "bidirectional"))
      (node (ref "D977") (pin "1") (pinfunction "A1_1") (pintype "bidirectional"))
      (node (ref "D978") (pin "1") (pinfunction "A1_1") (pintype "bidirectional"))
      (node (ref "D979") (pin "1") (pinfunction "A1_1") (pintype "bidirectional"))
      (node (ref "D980") (pin "1") (pinfunction "A1_1") (pintype "bidirectional"))
      (node (ref "D981") (pin "1") (pinfunction "A1_1") (pintype "bidirectional"))
      (node (ref "D982") (pin "1") (pinfunction "A1_1") (pintype "bidirectional"))
      (node (ref "D983") (pin "1") (pinfunction "A1_1") (pintype "bidirectional"))
      (node (ref "D984") (pin "1") (pinfunction "A1_1") (pintype "bidirectional"))
      (node (ref "D985") (pin "1") (pinfunction "A1_1") (pintype "bidirectional"))
      (node (ref "D986") (pin "1") (pinfunction "A1_1") (pintype "bidirectional"))
      (node (ref "D987") (pin "1") (pinfunction "A1_1") (pintype "bidirectional"))
      (node (ref "D988") (pin "1") (pinfunction "A1_1") (pintype "bidirectional"))
      (node (ref "D989") (pin "1") (pinfunction "A1_1") (pintype "bidirectional"))
      (node (ref "D990") (pin "1") (pinfunction "A1_1") (pintype "bidirectional"))
      (node (ref "D991") (pin "1") (pinfunction "A1_1") (pintype "bidirectional"))
      (node (ref "D992") (pin "1") (pinfunction "A1_1") (pintype "bidirectional"))
      (node (ref "IC27") (pin "12") (pinfunction "O7_12") (pintype "open_collector"))
    )
    (net (code "1274") (name "ROW31_SOURCE") (class "Default")
      (node (ref "D961") (pin "2") (pinfunction "C2_2") (pintype "bidirectional"))
      (node (ref "D962") (pin "2") (pinfunction "C2_2") (pintype "bidirectional"))
      (node (ref "D963") (pin "2") (pinfunction "C2_2") (pintype "bidirectional"))
      (node (ref "D964") (pin "2") (pinfunction "C2_2") (pintype "bidirectional"))
      (node (ref "D965") (pin "2") (pinfunction "C2_2") (pintype "bidirectional"))
      (node (ref "D966") (pin "2") (pinfunction "C2_2") (pintype "bidirectional"))
      (node (ref "D967") (pin "2") (pinfunction "C2_2") (pintype "bidirectional"))
      (node (ref "D968") (pin "2") (pinfunction "C2_2") (pintype "bidirectional"))
      (node (ref "D969") (pin "2") (pinfunction "C2_2") (pintype "bidirectional"))
      (node (ref "D970") (pin "2") (pinfunction "C2_2") (pintype "bidirectional"))
      (node (ref "D971") (pin "2") (pinfunction "C2_2") (pintype "bidirectional"))
      (node (ref "D972") (pin "2") (pinfunction "C2_2") (pintype "bidirectional"))
      (node (ref "D973") (pin "2") (pinfunction "C2_2") (pintype "bidirectional"))
      (node (ref "D974") (pin "2") (pinfunction "C2_2") (pintype "bidirectional"))
      (node (ref "D975") (pin "2") (pinfunction "C2_2") (pintype "bidirectional"))
      (node (ref "D976") (pin "2") (pinfunction "C2_2") (pintype "bidirectional"))
      (node (ref "D977") (pin "2") (pinfunction "C2_2") (pintype "bidirectional"))
      (node (ref "D978") (pin "2") (pinfunction "C2_2") (pintype "bidirectional"))
      (node (ref "D979") (pin "2") (pinfunction "C2_2") (pintype "bidirectional"))
      (node (ref "D980") (pin "2") (pinfunction "C2_2") (pintype "bidirectional"))
      (node (ref "D981") (pin "2") (pinfunction "C2_2") (pintype "bidirectional"))
      (node (ref "D982") (pin "2") (pinfunction "C2_2") (pintype "bidirectional"))
      (node (ref "D983") (pin "2") (pinfunction "C2_2") (pintype "bidirectional"))
      (node (ref "D984") (pin "2") (pinfunction "C2_2") (pintype "bidirectional"))
      (node (ref "D985") (pin "2") (pinfunction "C2_2") (pintype "bidirectional"))
      (node (ref "D986") (pin "2") (pinfunction "C2_2") (pintype "bidirectional"))
      (node (ref "D987") (pin "2") (pinfunction "C2_2") (pintype "bidirectional"))
      (node (ref "D988") (pin "2") (pinfunction "C2_2") (pintype "bidirectional"))
      (node (ref "D989") (pin "2") (pinfunction "C2_2") (pintype "bidirectional"))
      (node (ref "D990") (pin "2") (pinfunction "C2_2") (pintype "bidirectional"))
      (node (ref "D991") (pin "2") (pinfunction "C2_2") (pintype "bidirectional"))
      (node (ref "D992") (pin "2") (pinfunction "C2_2") (pintype "bidirectional"))
      (node (ref "IC28") (pin "12") (pinfunction "O7_12") (pintype "open_collector"))
    )
    (net (code "1275") (name "ROW32_SINK") (class "Default")
      (node (ref "D1000") (pin "1") (pinfunction "A1_1") (pintype "bidirectional"))
      (node (ref "D1001") (pin "1") (pinfunction "A1_1") (pintype "bidirectional"))
      (node (ref "D1002") (pin "1") (pinfunction "A1_1") (pintype "bidirectional"))
      (node (ref "D1003") (pin "1") (pinfunction "A1_1") (pintype "bidirectional"))
      (node (ref "D1004") (pin "1") (pinfunction "A1_1") (pintype "bidirectional"))
      (node (ref "D1005") (pin "1") (pinfunction "A1_1") (pintype "bidirectional"))
      (node (ref "D1006") (pin "1") (pinfunction "A1_1") (pintype "bidirectional"))
      (node (ref "D1007") (pin "1") (pinfunction "A1_1") (pintype "bidirectional"))
      (node (ref "D1008") (pin "1") (pinfunction "A1_1") (pintype "bidirectional"))
      (node (ref "D1009") (pin "1") (pinfunction "A1_1") (pintype "bidirectional"))
      (node (ref "D1010") (pin "1") (pinfunction "A1_1") (pintype "bidirectional"))
      (node (ref "D1011") (pin "1") (pinfunction "A1_1") (pintype "bidirectional"))
      (node (ref "D1012") (pin "1") (pinfunction "A1_1") (pintype "bidirectional"))
      (node (ref "D1013") (pin "1") (pinfunction "A1_1") (pintype "bidirectional"))
      (node (ref "D1014") (pin "1") (pinfunction "A1_1") (pintype "bidirectional"))
      (node (ref "D1015") (pin "1") (pinfunction "A1_1") (pintype "bidirectional"))
      (node (ref "D1016") (pin "1") (pinfunction "A1_1") (pintype "bidirectional"))
      (node (ref "D1017") (pin "1") (pinfunction "A1_1") (pintype "bidirectional"))
      (node (ref "D1018") (pin "1") (pinfunction "A1_1") (pintype "bidirectional"))
      (node (ref "D1019") (pin "1") (pinfunction "A1_1") (pintype "bidirectional"))
      (node (ref "D1020") (pin "1") (pinfunction "A1_1") (pintype "bidirectional"))
      (node (ref "D1021") (pin "1") (pinfunction "A1_1") (pintype "bidirectional"))
      (node (ref "D1022") (pin "1") (pinfunction "A1_1") (pintype "bidirectional"))
      (node (ref "D1023") (pin "1") (pinfunction "A1_1") (pintype "bidirectional"))
      (node (ref "D1024") (pin "1") (pinfunction "A1_1") (pintype "bidirectional"))
      (node (ref "D993") (pin "1") (pinfunction "A1_1") (pintype "bidirectional"))
      (node (ref "D994") (pin "1") (pinfunction "A1_1") (pintype "bidirectional"))
      (node (ref "D995") (pin "1") (pinfunction "A1_1") (pintype "bidirectional"))
      (node (ref "D996") (pin "1") (pinfunction "A1_1") (pintype "bidirectional"))
      (node (ref "D997") (pin "1") (pinfunction "A1_1") (pintype "bidirectional"))
      (node (ref "D998") (pin "1") (pinfunction "A1_1") (pintype "bidirectional"))
      (node (ref "D999") (pin "1") (pinfunction "A1_1") (pintype "bidirectional"))
      (node (ref "IC27") (pin "11") (pinfunction "O8_11") (pintype "open_collector"))
    )
    (net (code "1276") (name "ROW32_SOURCE") (class "Default")
      (node (ref "D1000") (pin "2") (pinfunction "C2_2") (pintype "bidirectional"))
      (node (ref "D1001") (pin "2") (pinfunction "C2_2") (pintype "bidirectional"))
      (node (ref "D1002") (pin "2") (pinfunction "C2_2") (pintype "bidirectional"))
      (node (ref "D1003") (pin "2") (pinfunction "C2_2") (pintype "bidirectional"))
      (node (ref "D1004") (pin "2") (pinfunction "C2_2") (pintype "bidirectional"))
      (node (ref "D1005") (pin "2") (pinfunction "C2_2") (pintype "bidirectional"))
      (node (ref "D1006") (pin "2") (pinfunction "C2_2") (pintype "bidirectional"))
      (node (ref "D1007") (pin "2") (pinfunction "C2_2") (pintype "bidirectional"))
      (node (ref "D1008") (pin "2") (pinfunction "C2_2") (pintype "bidirectional"))
      (node (ref "D1009") (pin "2") (pinfunction "C2_2") (pintype "bidirectional"))
      (node (ref "D1010") (pin "2") (pinfunction "C2_2") (pintype "bidirectional"))
      (node (ref "D1011") (pin "2") (pinfunction "C2_2") (pintype "bidirectional"))
      (node (ref "D1012") (pin "2") (pinfunction "C2_2") (pintype "bidirectional"))
      (node (ref "D1013") (pin "2") (pinfunction "C2_2") (pintype "bidirectional"))
      (node (ref "D1014") (pin "2") (pinfunction "C2_2") (pintype "bidirectional"))
      (node (ref "D1015") (pin "2") (pinfunction "C2_2") (pintype "bidirectional"))
      (node (ref "D1016") (pin "2") (pinfunction "C2_2") (pintype "bidirectional"))
      (node (ref "D1017") (pin "2") (pinfunction "C2_2") (pintype "bidirectional"))
      (node (ref "D1018") (pin "2") (pinfunction "C2_2") (pintype "bidirectional"))
      (node (ref "D1019") (pin "2") (pinfunction "C2_2") (pintype "bidirectional"))
      (node (ref "D1020") (pin "2") (pinfunction "C2_2") (pintype "bidirectional"))
      (node (ref "D1021") (pin "2") (pinfunction "C2_2") (pintype "bidirectional"))
      (node (ref "D1022") (pin "2") (pinfunction "C2_2") (pintype "bidirectional"))
      (node (ref "D1023") (pin "2") (pinfunction "C2_2") (pintype "bidirectional"))
      (node (ref "D1024") (pin "2") (pinfunction "C2_2") (pintype "bidirectional"))
      (node (ref "D993") (pin "2") (pinfunction "C2_2") (pintype "bidirectional"))
      (node (ref "D994") (pin "2") (pinfunction "C2_2") (pintype "bidirectional"))
      (node (ref "D995") (pin "2") (pinfunction "C2_2") (pintype "bidirectional"))
      (node (ref "D996") (pin "2") (pinfunction "C2_2") (pintype "bidirectional"))
      (node (ref "D997") (pin "2") (pinfunction "C2_2") (pintype "bidirectional"))
      (node (ref "D998") (pin "2") (pinfunction "C2_2") (pintype "bidirectional"))
      (node (ref "D999") (pin "2") (pinfunction "C2_2") (pintype "bidirectional"))
      (node (ref "IC28") (pin "11") (pinfunction "O8_11") (pintype "open_collector"))
    )
    (net (code "1277") (name "ROW_ADV") (class "Default")
      (node (ref "CONN1") (pin "10") (pinfunction "10_10") (pintype "passive"))
      (node (ref "CONN2") (pin "10") (pinfunction "10_10") (pintype "passive"))
      (node (ref "IC1") (pin "7") (pinfunction "D4_7") (pintype "input"))
    )
    (net (code "1278") (name "ROW_RESET_COL_ADV") (class "Default")
      (node (ref "CONN1") (pin "7") (pinfunction "7_7") (pintype "passive"))
      (node (ref "CONN2") (pin "7") (pinfunction "7_7") (pintype "passive"))
      (node (ref "IC1") (pin "2") (pinfunction "D1_2") (pintype "input"))
    )
    (net (code "1279") (name "ROW_SEL1") (class "Default")
      (node (ref "IC11") (pin "2") (pinfunction "D1_2") (pintype "input"))
      (node (ref "IC2") (pin "12") (pinfunction "Q1_12") (pintype "output"))
      (node (ref "IC26") (pin "2") (pinfunction "D1_2") (pintype "input"))
      (node (ref "IC5") (pin "2") (pinfunction "D1_2") (pintype "input"))
      (node (ref "IC8") (pin "2") (pinfunction "D1_2") (pintype "input"))
    )
    (net (code "1280") (name "ROW_SEL2") (class "Default")
      (node (ref "IC11") (pin "3") (pinfunction "D2_3") (pintype "input"))
      (node (ref "IC2") (pin "11") (pinfunction "Q2_11") (pintype "output"))
      (node (ref "IC26") (pin "3") (pinfunction "D2_3") (pintype "input"))
      (node (ref "IC5") (pin "3") (pinfunction "D2_3") (pintype "input"))
      (node (ref "IC8") (pin "3") (pinfunction "D2_3") (pintype "input"))
    )
    (net (code "1281") (name "ROW_SEL3") (class "Default")
      (node (ref "IC11") (pin "21") (pinfunction "D3_21") (pintype "input"))
      (node (ref "IC2") (pin "9") (pinfunction "Q3_9") (pintype "output"))
      (node (ref "IC26") (pin "21") (pinfunction "D3_21") (pintype "input"))
      (node (ref "IC5") (pin "21") (pinfunction "D3_21") (pintype "input"))
      (node (ref "IC8") (pin "21") (pinfunction "D3_21") (pintype "input"))
    )
    (net (code "1282") (name "SET_UNSET") (class "Default")
      (node (ref "CONN1") (pin "9") (pinfunction "9_9") (pintype "passive"))
      (node (ref "CONN2") (pin "9") (pinfunction "9_9") (pintype "passive"))
      (node (ref "IC1") (pin "6") (pinfunction "D3_6") (pintype "input"))
    )
    (net (code "1283") (name "SET_UNSET_LATCHED") (class "Default")
      (node (ref "IC1") (pin "10") (pinfunction "Q3_10") (pintype "output"))
      (node (ref "IC11") (pin "22") (pinfunction "D4_22") (pintype "input"))
      (node (ref "IC14") (pin "22") (pinfunction "D4_22") (pintype "input"))
      (node (ref "IC17") (pin "22") (pinfunction "D4_22") (pintype "input"))
      (node (ref "IC20") (pin "22") (pinfunction "D4_22") (pintype "input"))
      (node (ref "IC23") (pin "22") (pinfunction "D4_22") (pintype "input"))
      (node (ref "IC26") (pin "22") (pinfunction "D4_22") (pintype "input"))
      (node (ref "IC5") (pin "22") (pinfunction "D4_22") (pintype "input"))
      (node (ref "IC8") (pin "22") (pinfunction "D4_22") (pintype "input"))
    )
    (net (code "1284") (name "unconnected-(IC1A-~{Q1}-Pad1)") (class "Default")
      (node (ref "IC1") (pin "1") (pinfunction "~{Q1}_1") (pintype "output"))
    )
    (net (code "1285") (name "unconnected-(IC1A-~{Q2}-Pad14)") (class "Default")
      (node (ref "IC1") (pin "14") (pinfunction "~{Q2}_14") (pintype "output"))
    )
    (net (code "1286") (name "unconnected-(IC1A-~{Q3}-Pad11)") (class "Default")
      (node (ref "IC1") (pin "11") (pinfunction "~{Q3}_11") (pintype "output"))
    )
    (net (code "1287") (name "unconnected-(IC1A-~{Q4}-Pad8)") (class "Default")
      (node (ref "IC1") (pin "8") (pinfunction "~{Q4}_8") (pintype "output"))
    )
    (net (code "1288") (name "unconnected-(IC2A-Q6-Pad4)") (class "Default")
      (node (ref "IC2") (pin "4") (pinfunction "Q6_4") (pintype "output"))
    )
    (net (code "1289") (name "unconnected-(IC2A-Q7-Pad3)") (class "Default")
      (node (ref "IC2") (pin "3") (pinfunction "Q7_3") (pintype "output"))
    )
    (net (code "1290") (name "unconnected-(IC4A-Q6-Pad4)") (class "Default")
      (node (ref "IC4") (pin "4") (pinfunction "Q6_4") (pintype "output"))
    )
    (net (code "1291") (name "unconnected-(IC4A-Q7-Pad3)") (class "Default")
      (node (ref "IC4") (pin "3") (pinfunction "Q7_3") (pintype "output"))
    )
  )
)
